# BEP33_12panel_stencil.net
KiCad netlist of a schematic drawn in EAGLE
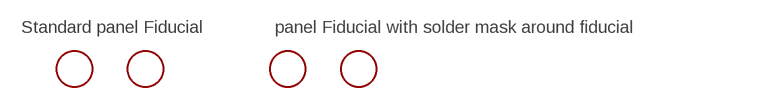
[diagram p0: schematic, sheet 1]
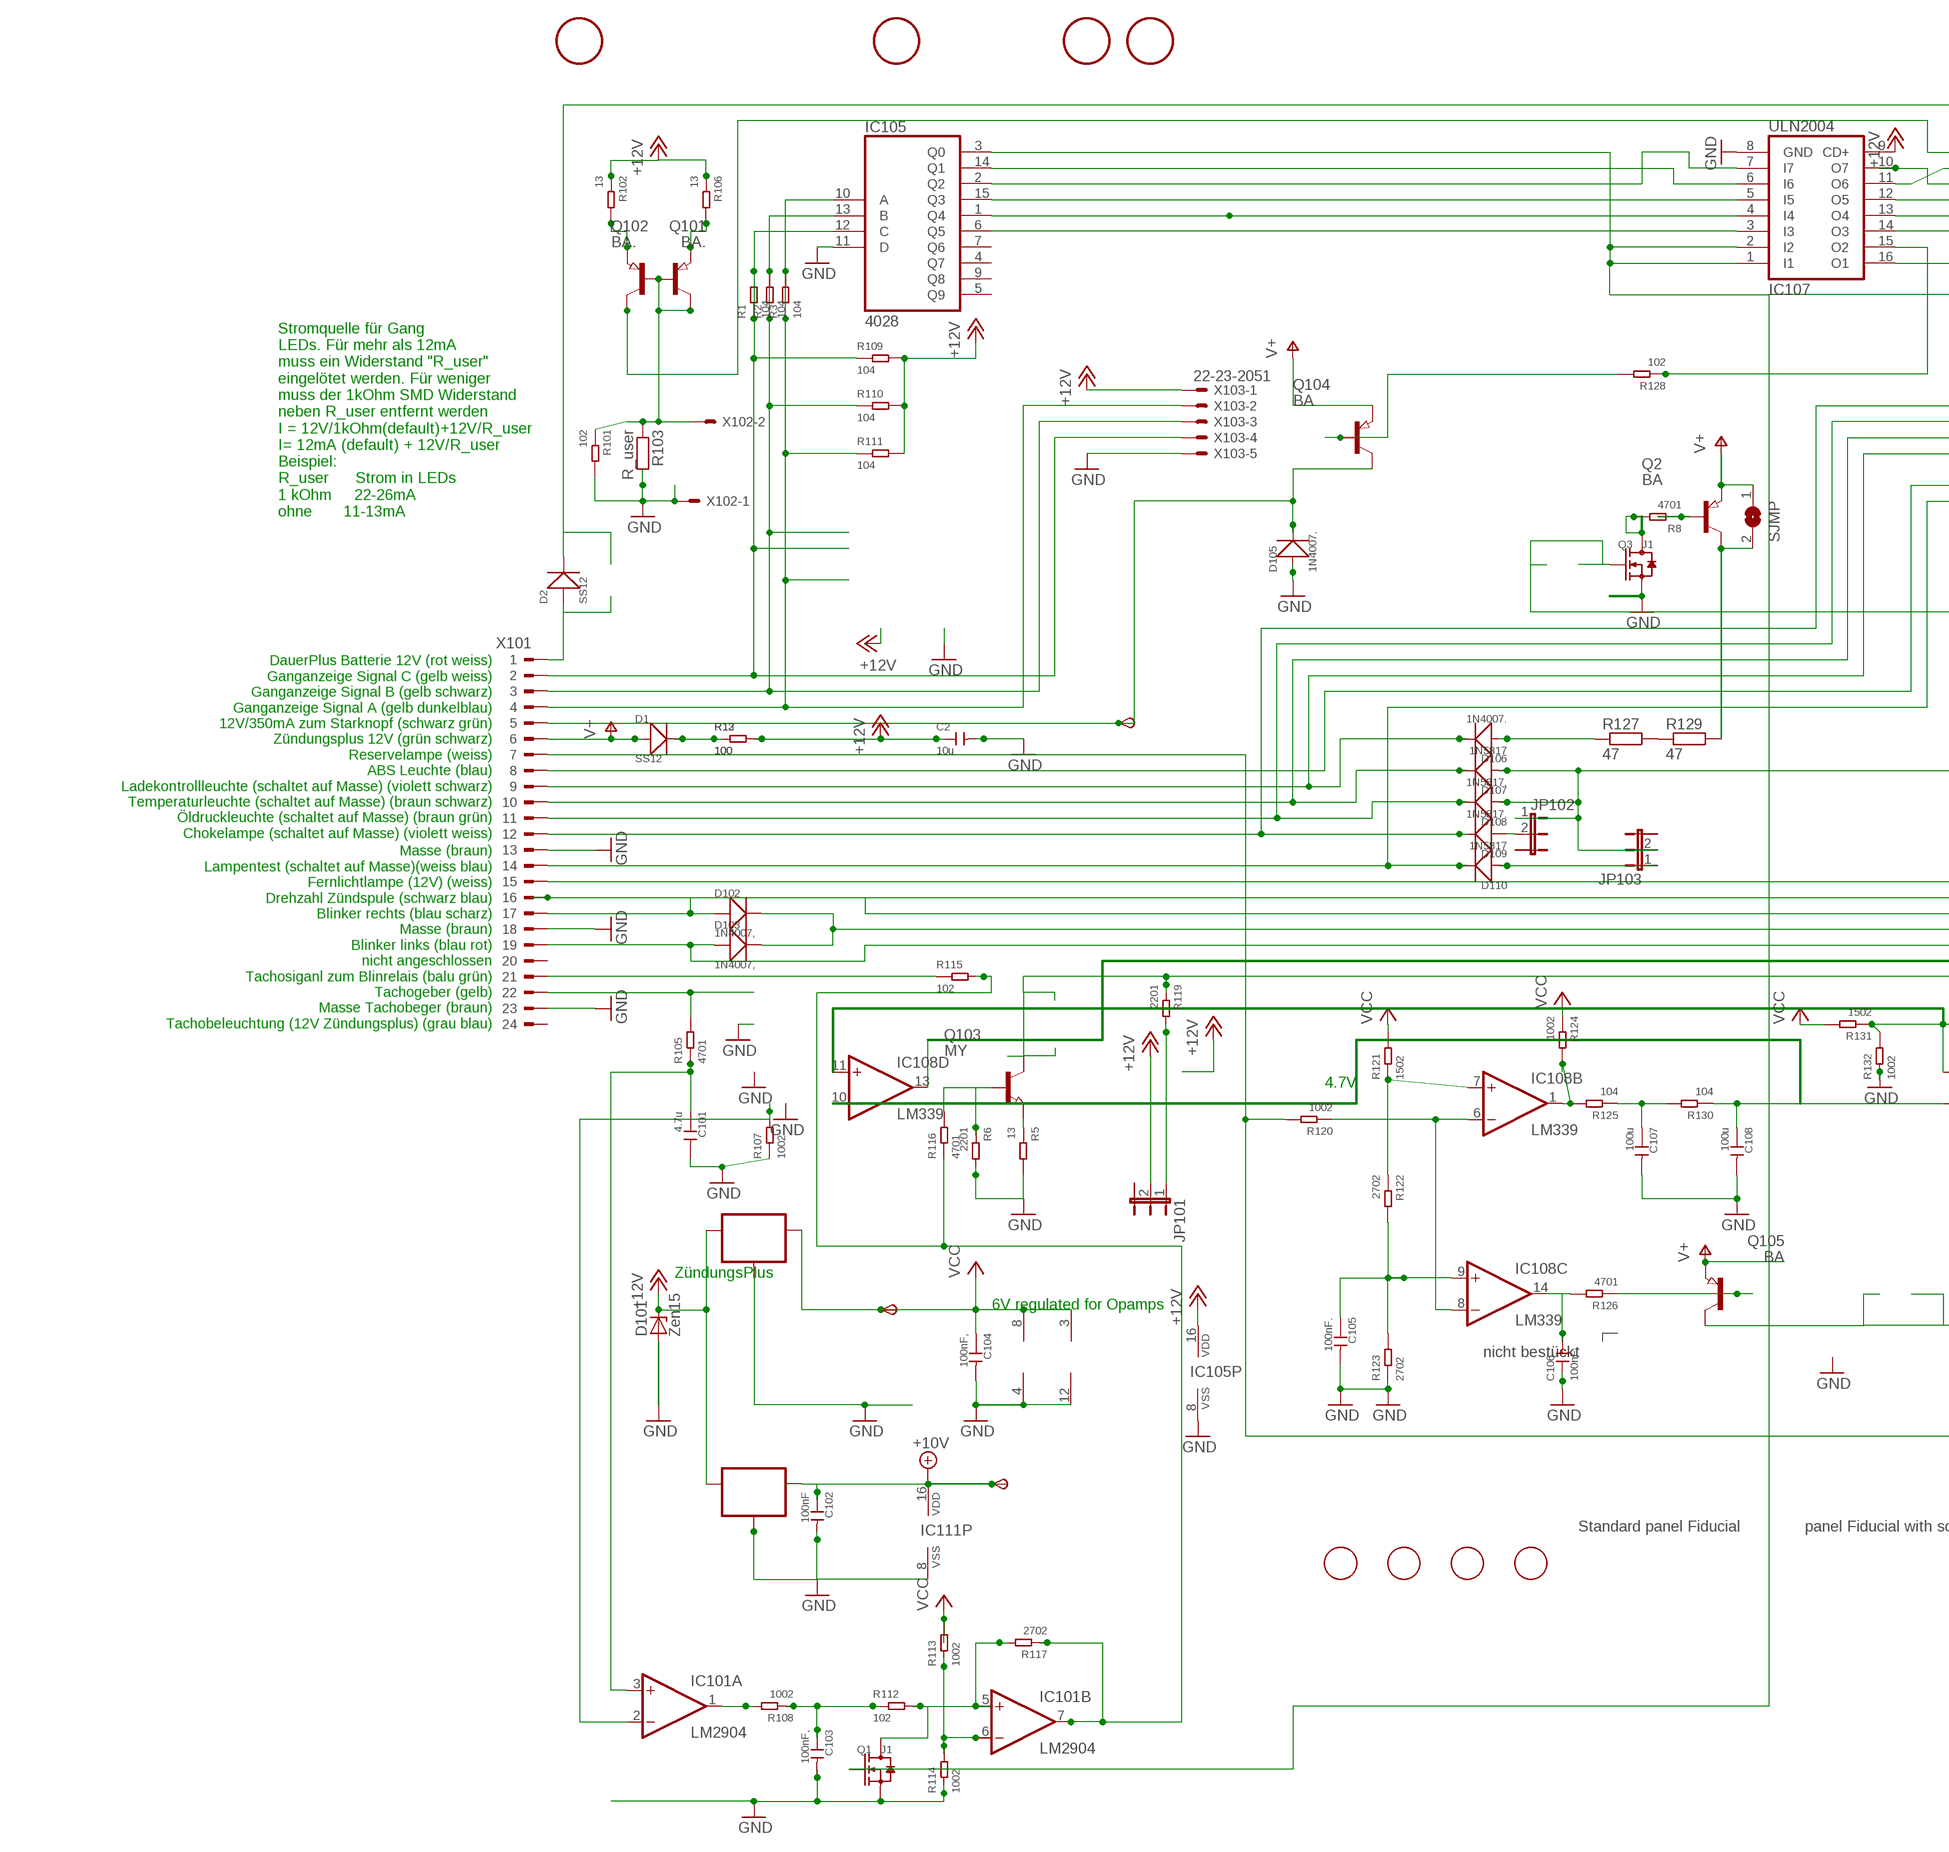
[diagram p1: schematic, sheet 2, part 1 of 2]
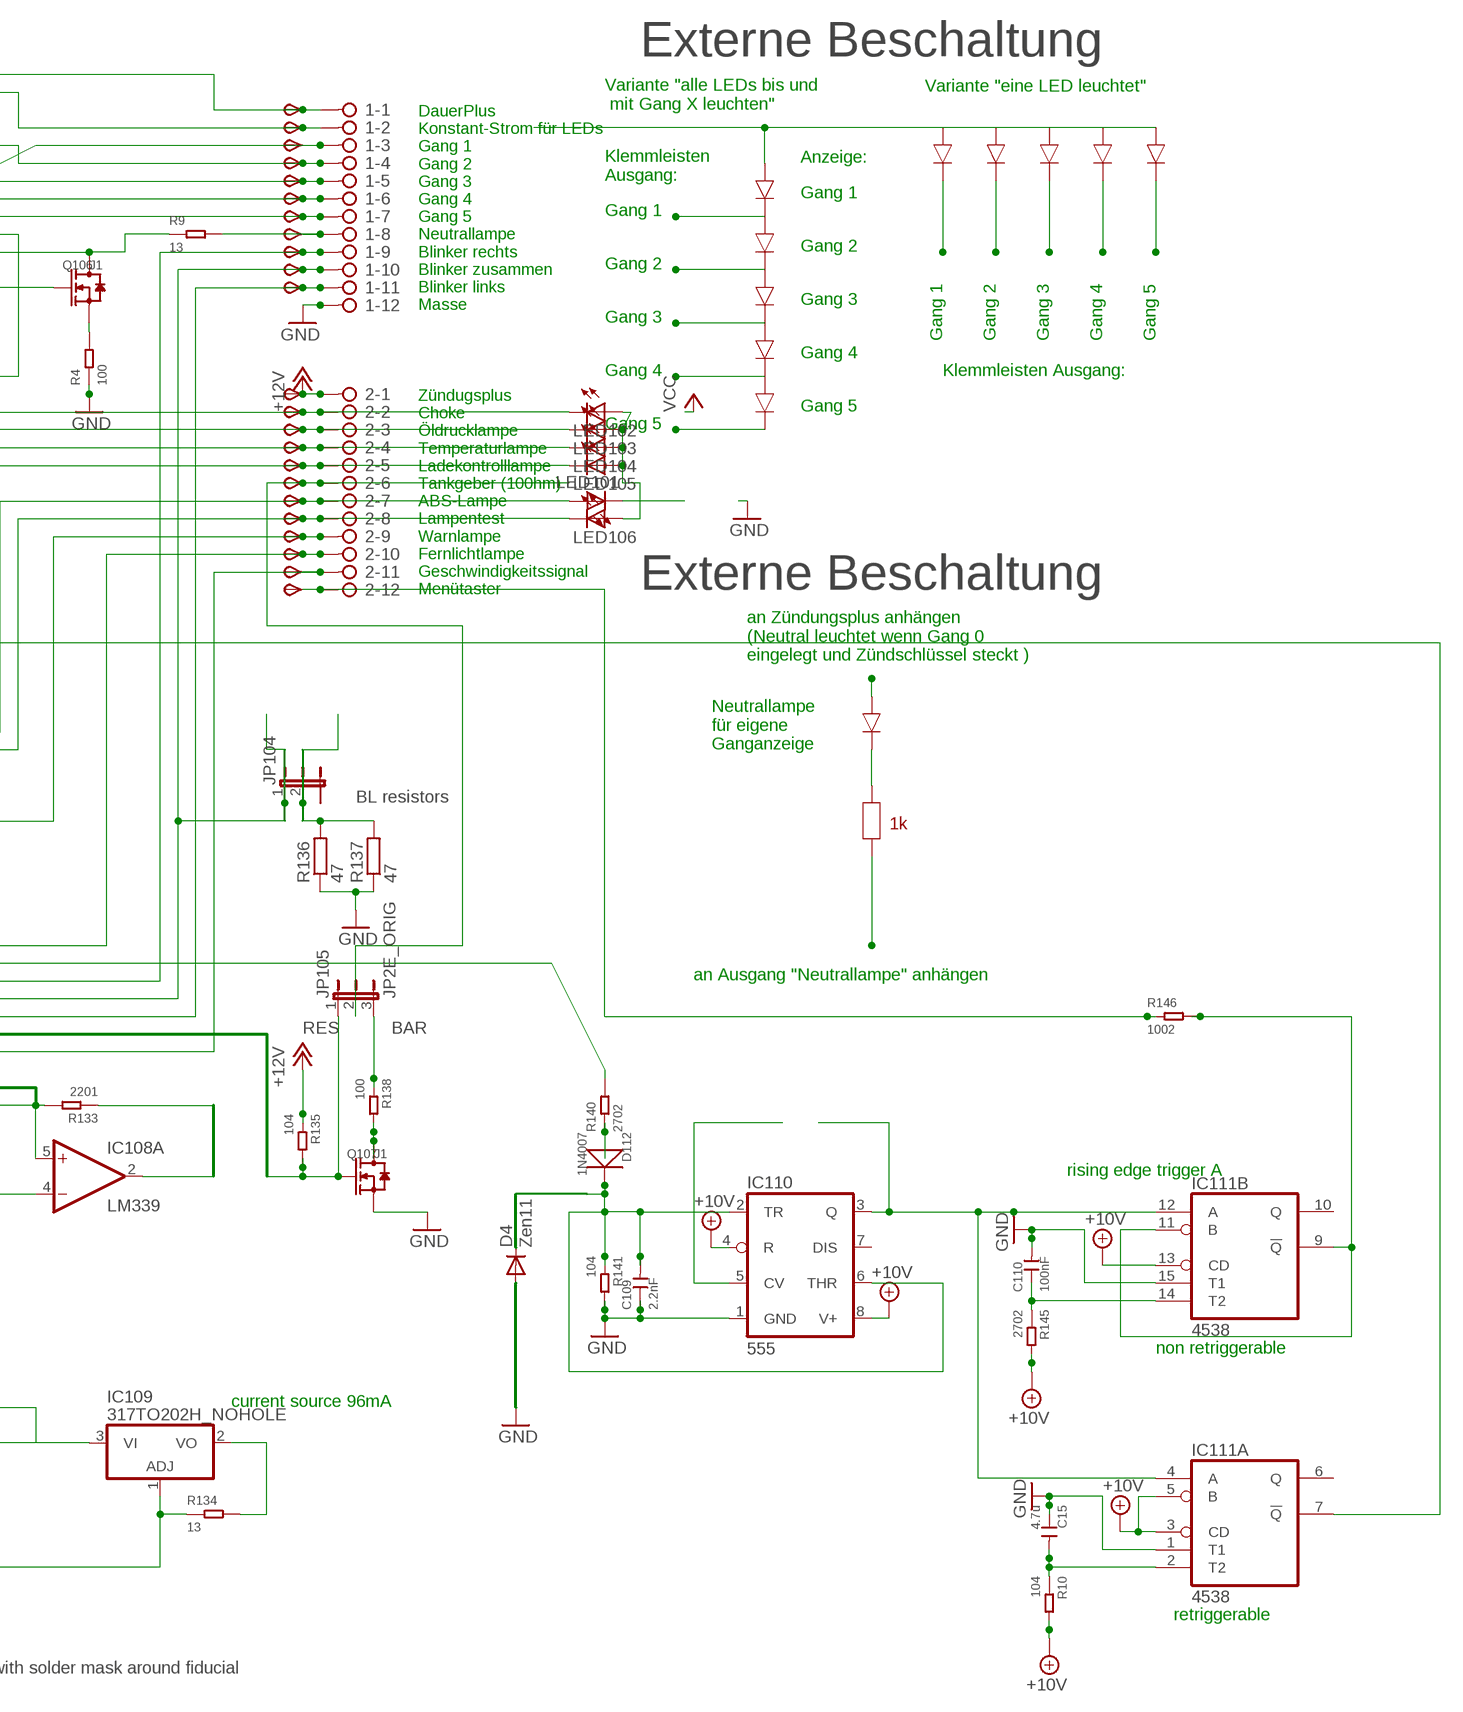
[diagram p2: schematic, sheet 2, part 2 of 2]
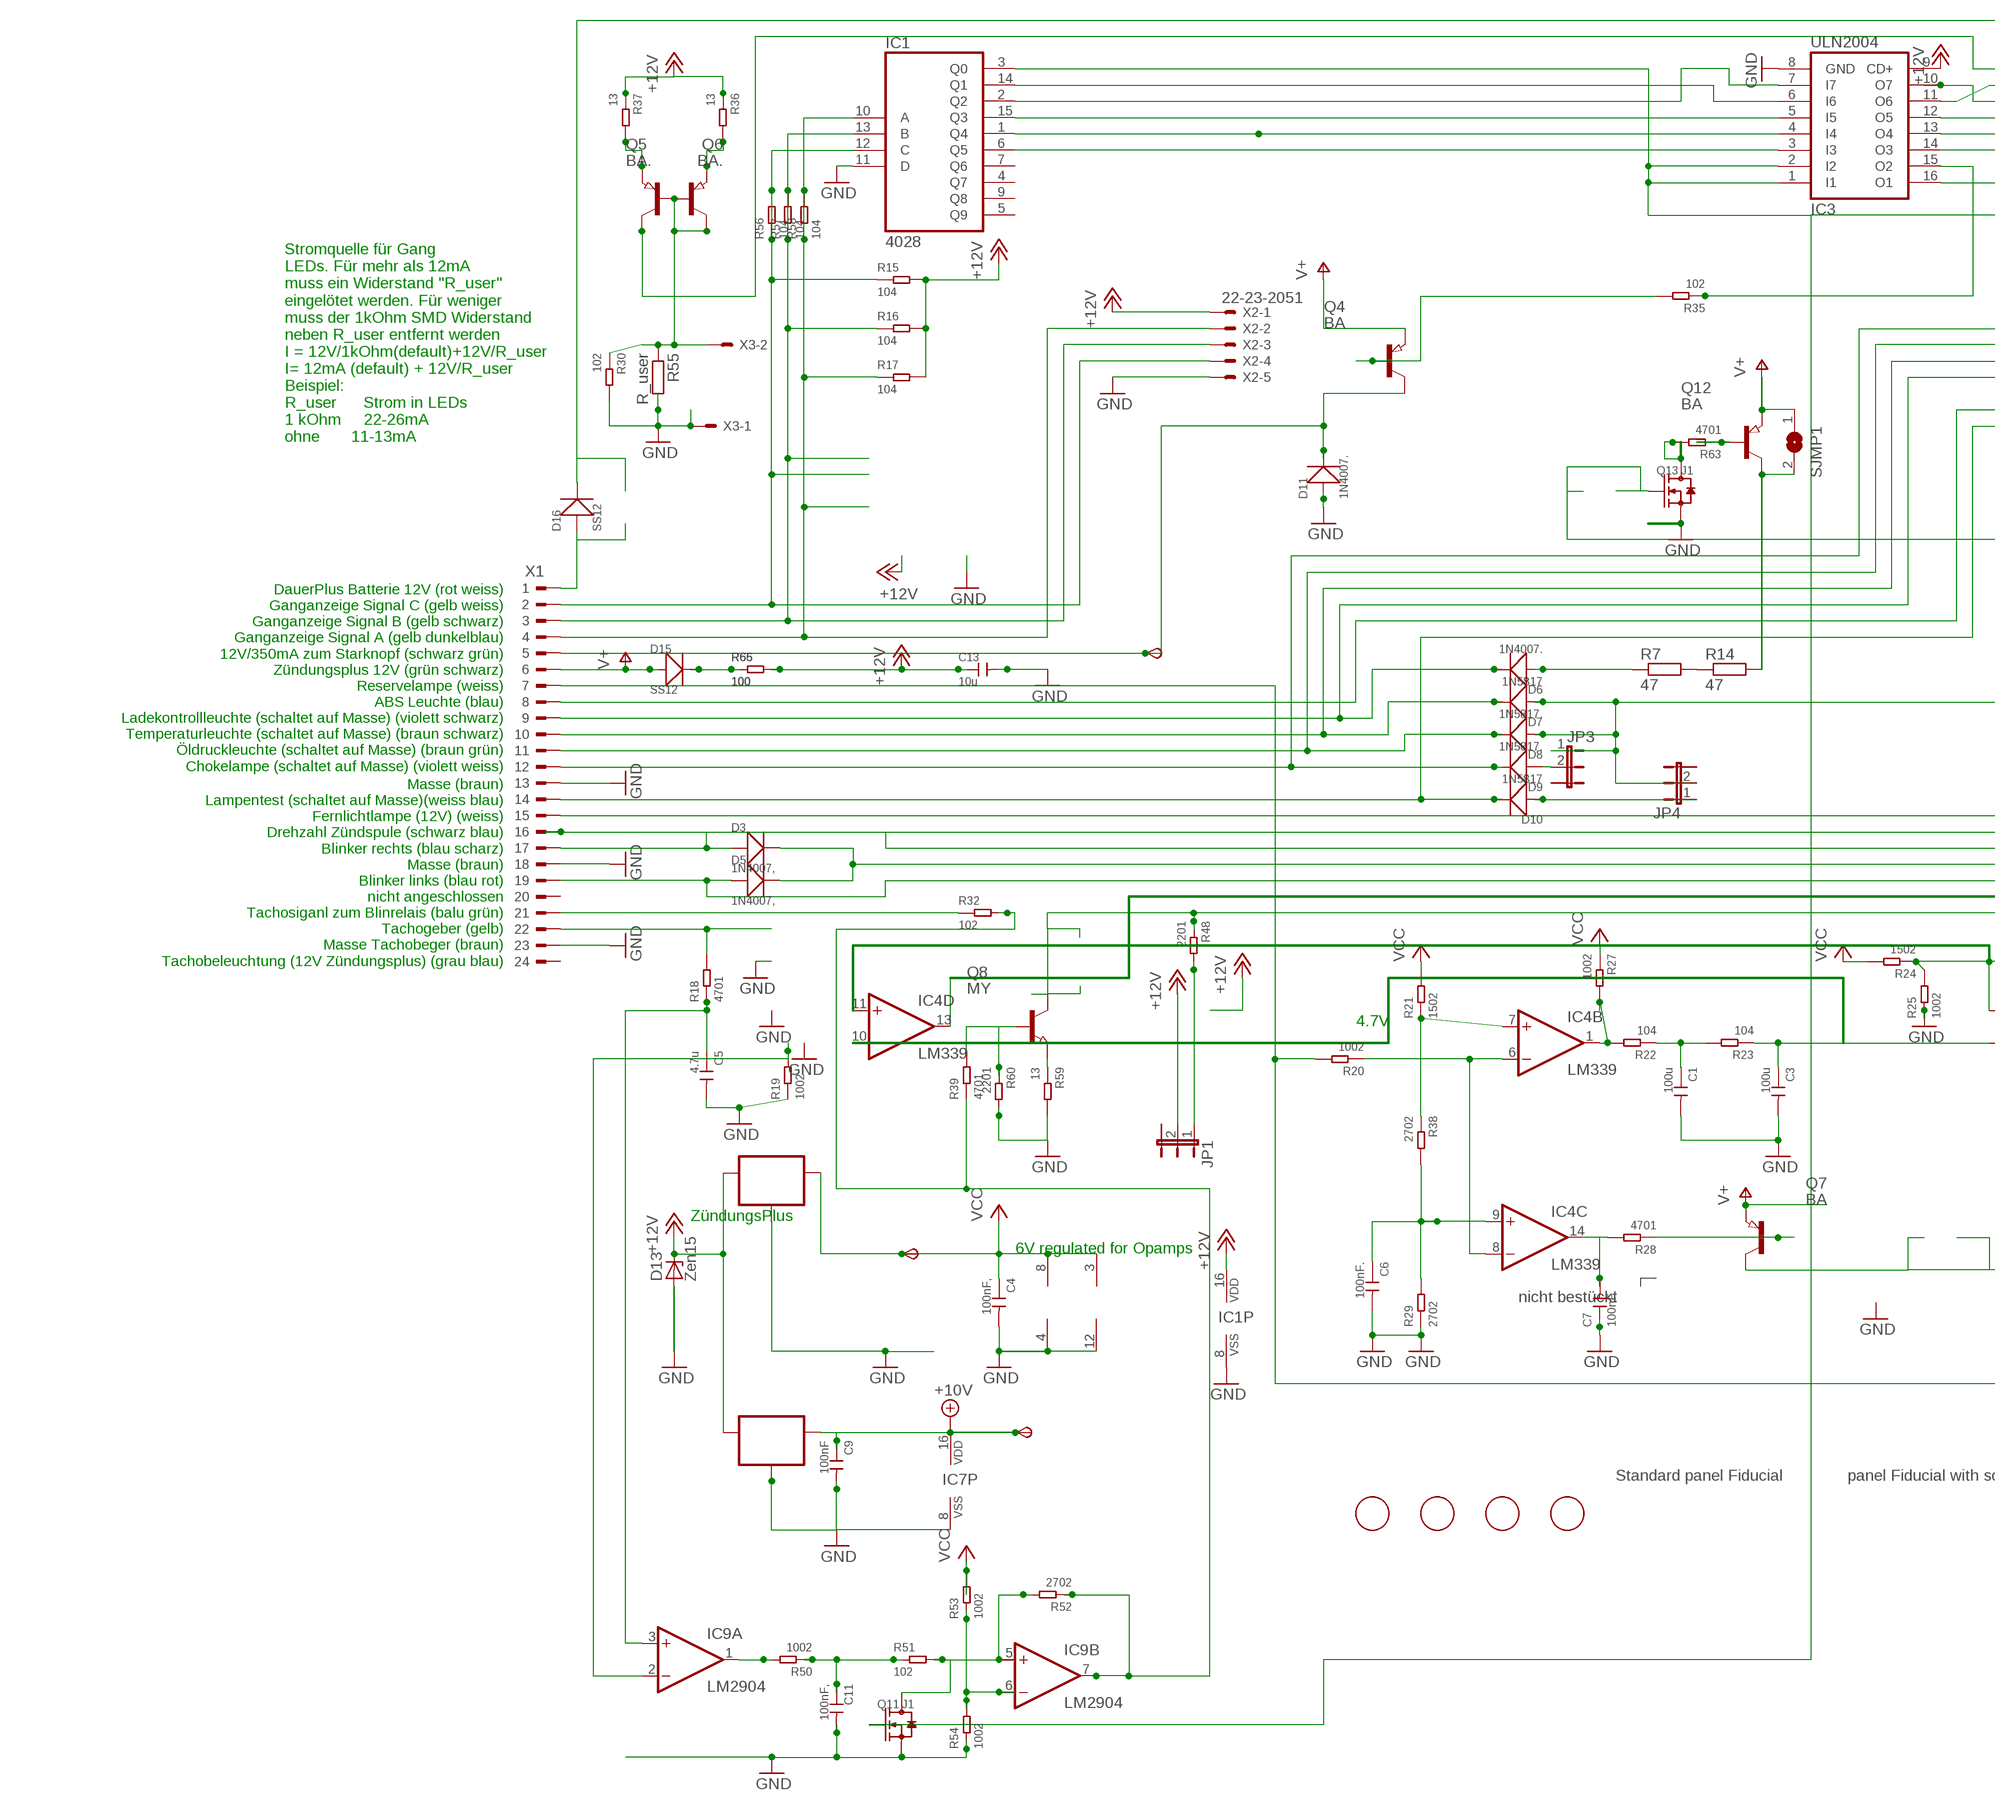
[diagram p3: schematic, sheet 3, part 1 of 2]
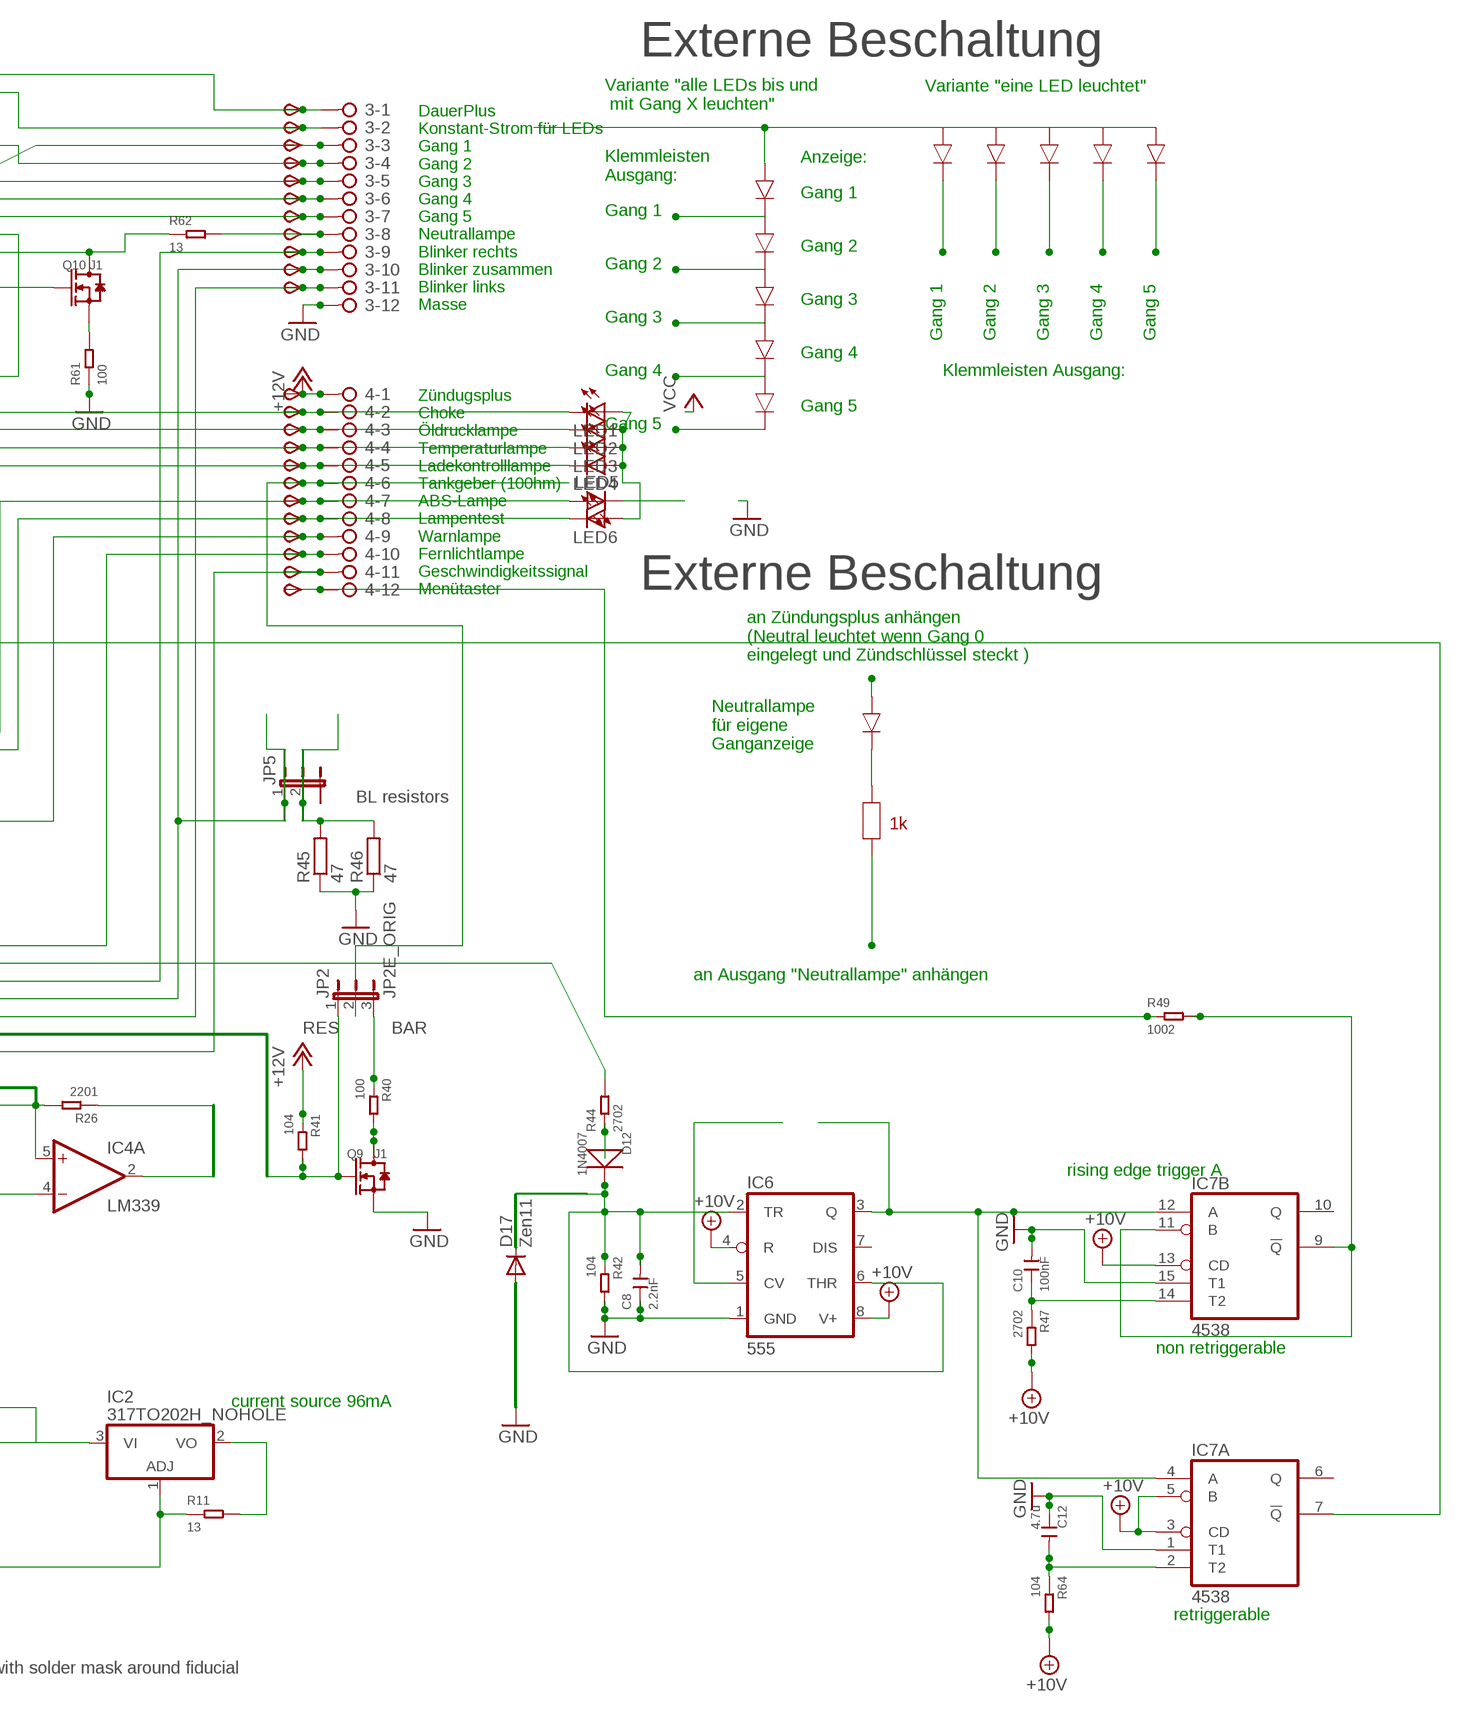
[diagram p4: schematic, sheet 3, part 2 of 2]
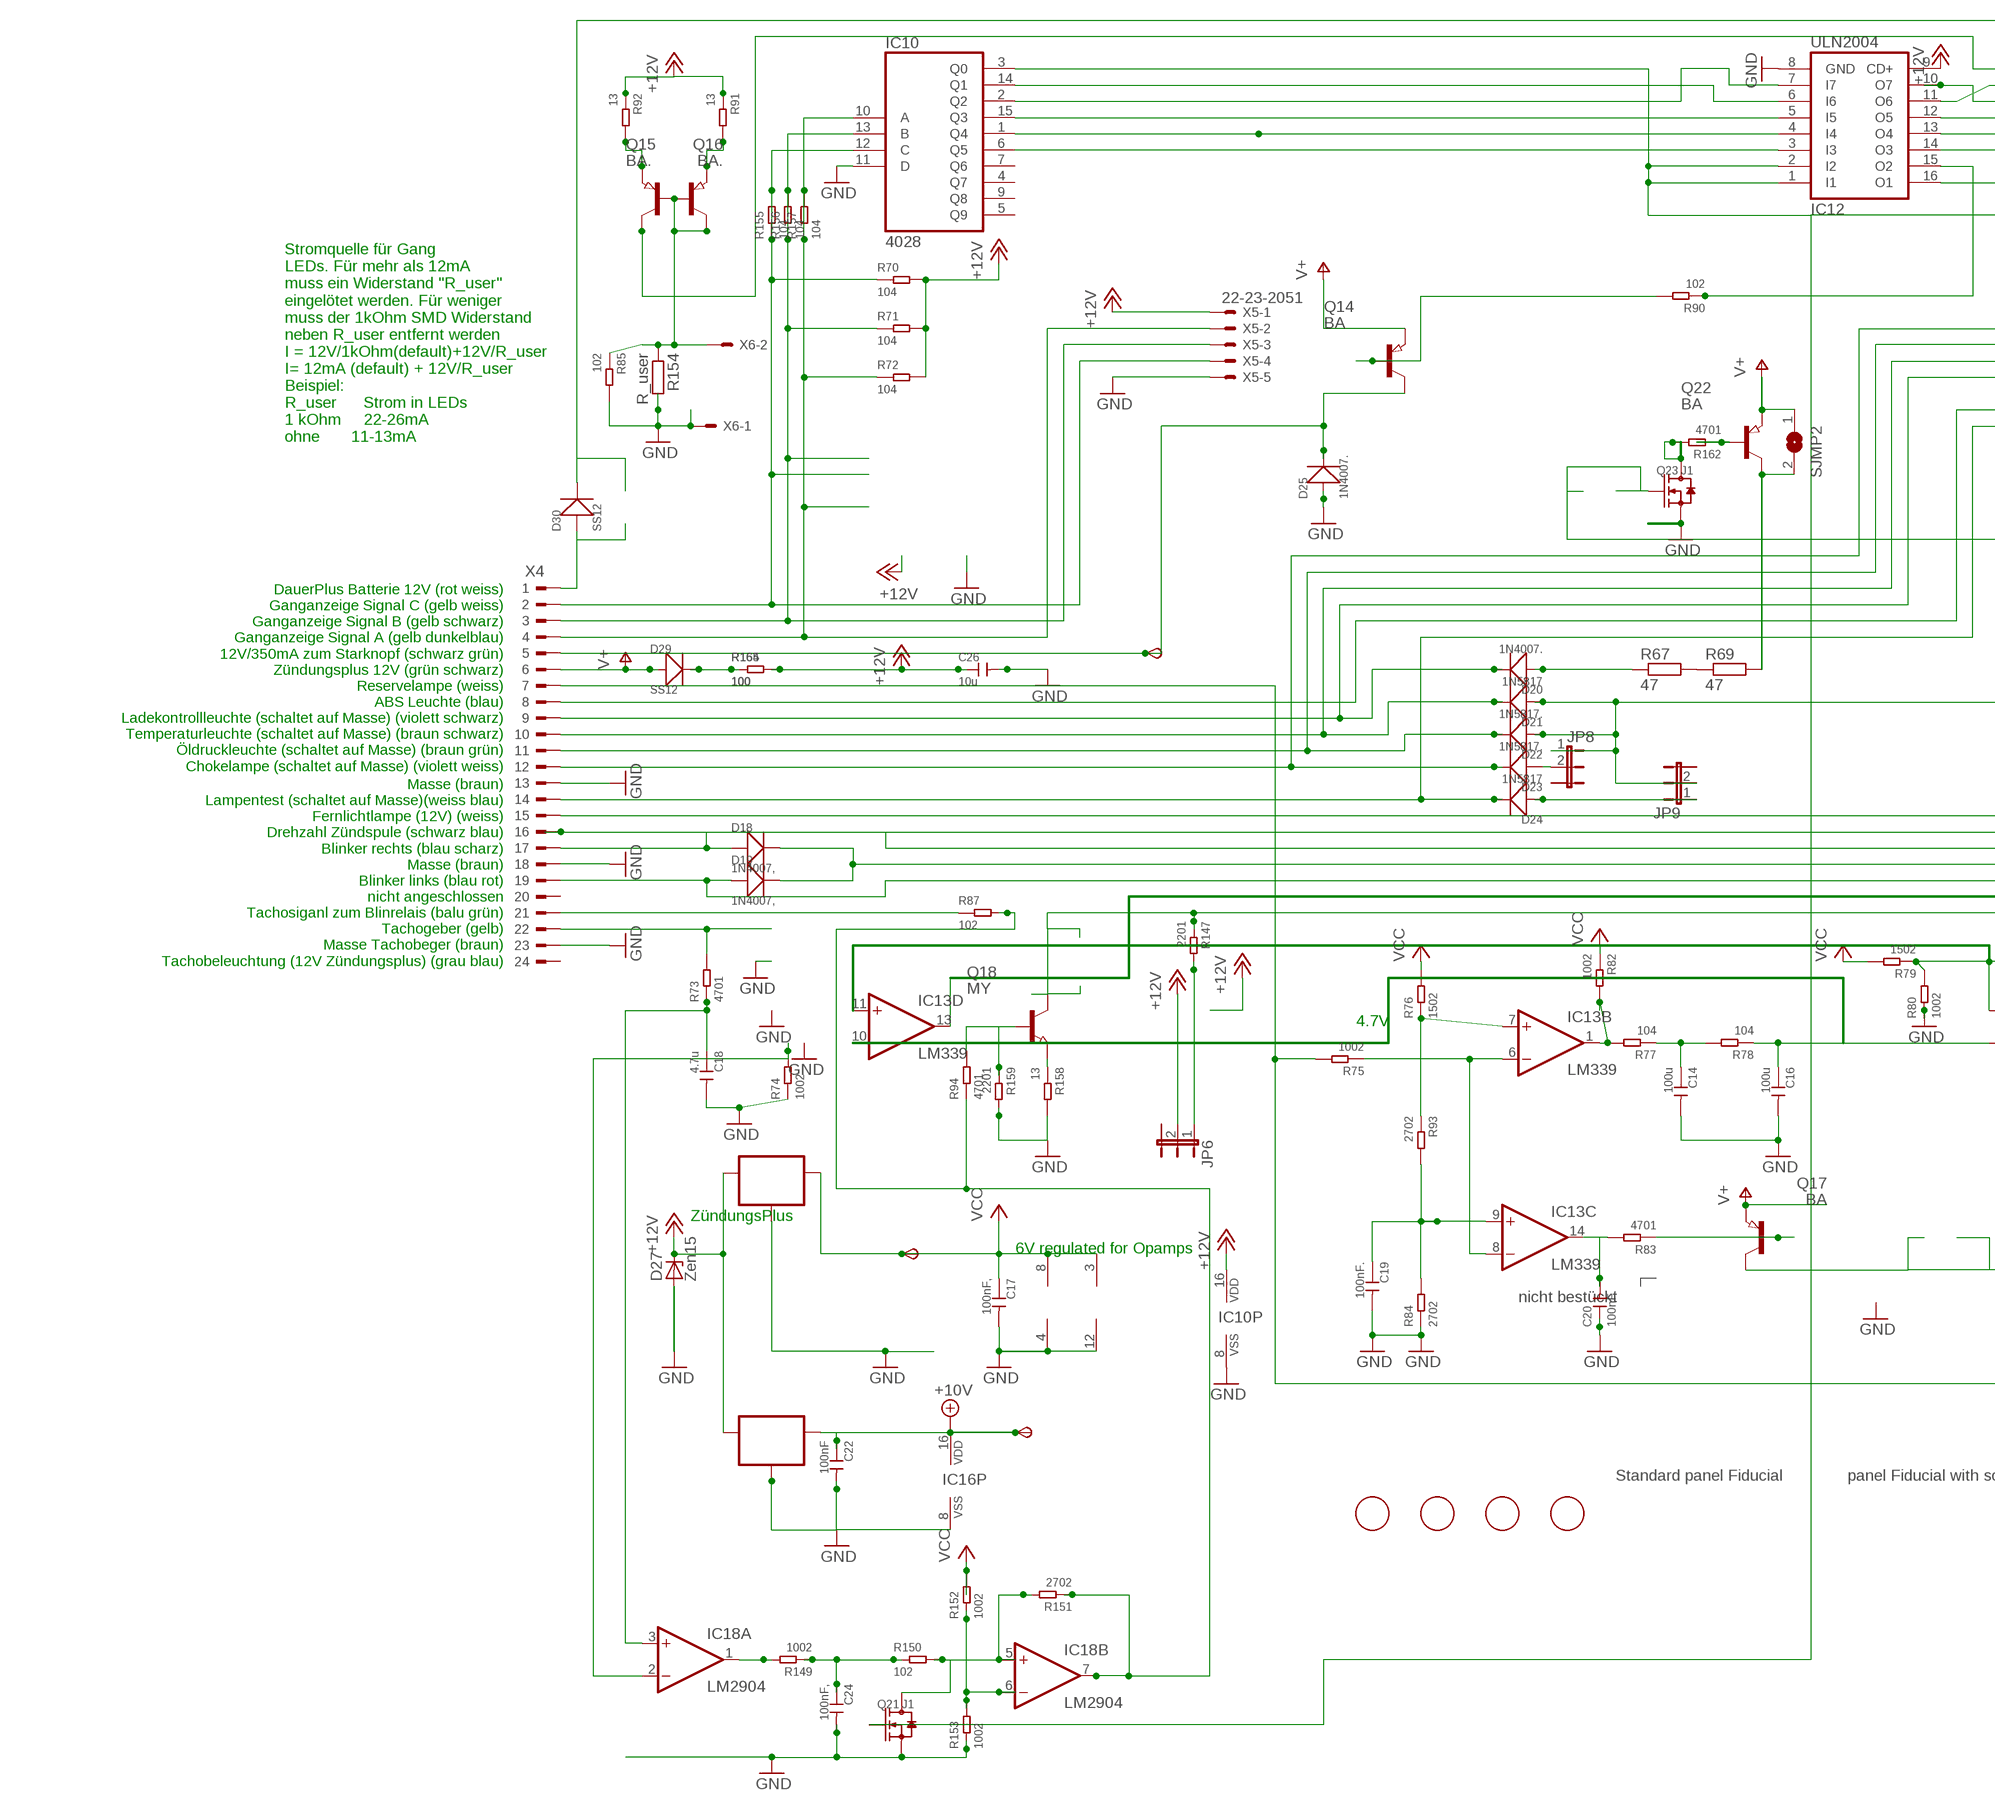
[diagram p5: schematic, sheet 4, part 1 of 2]
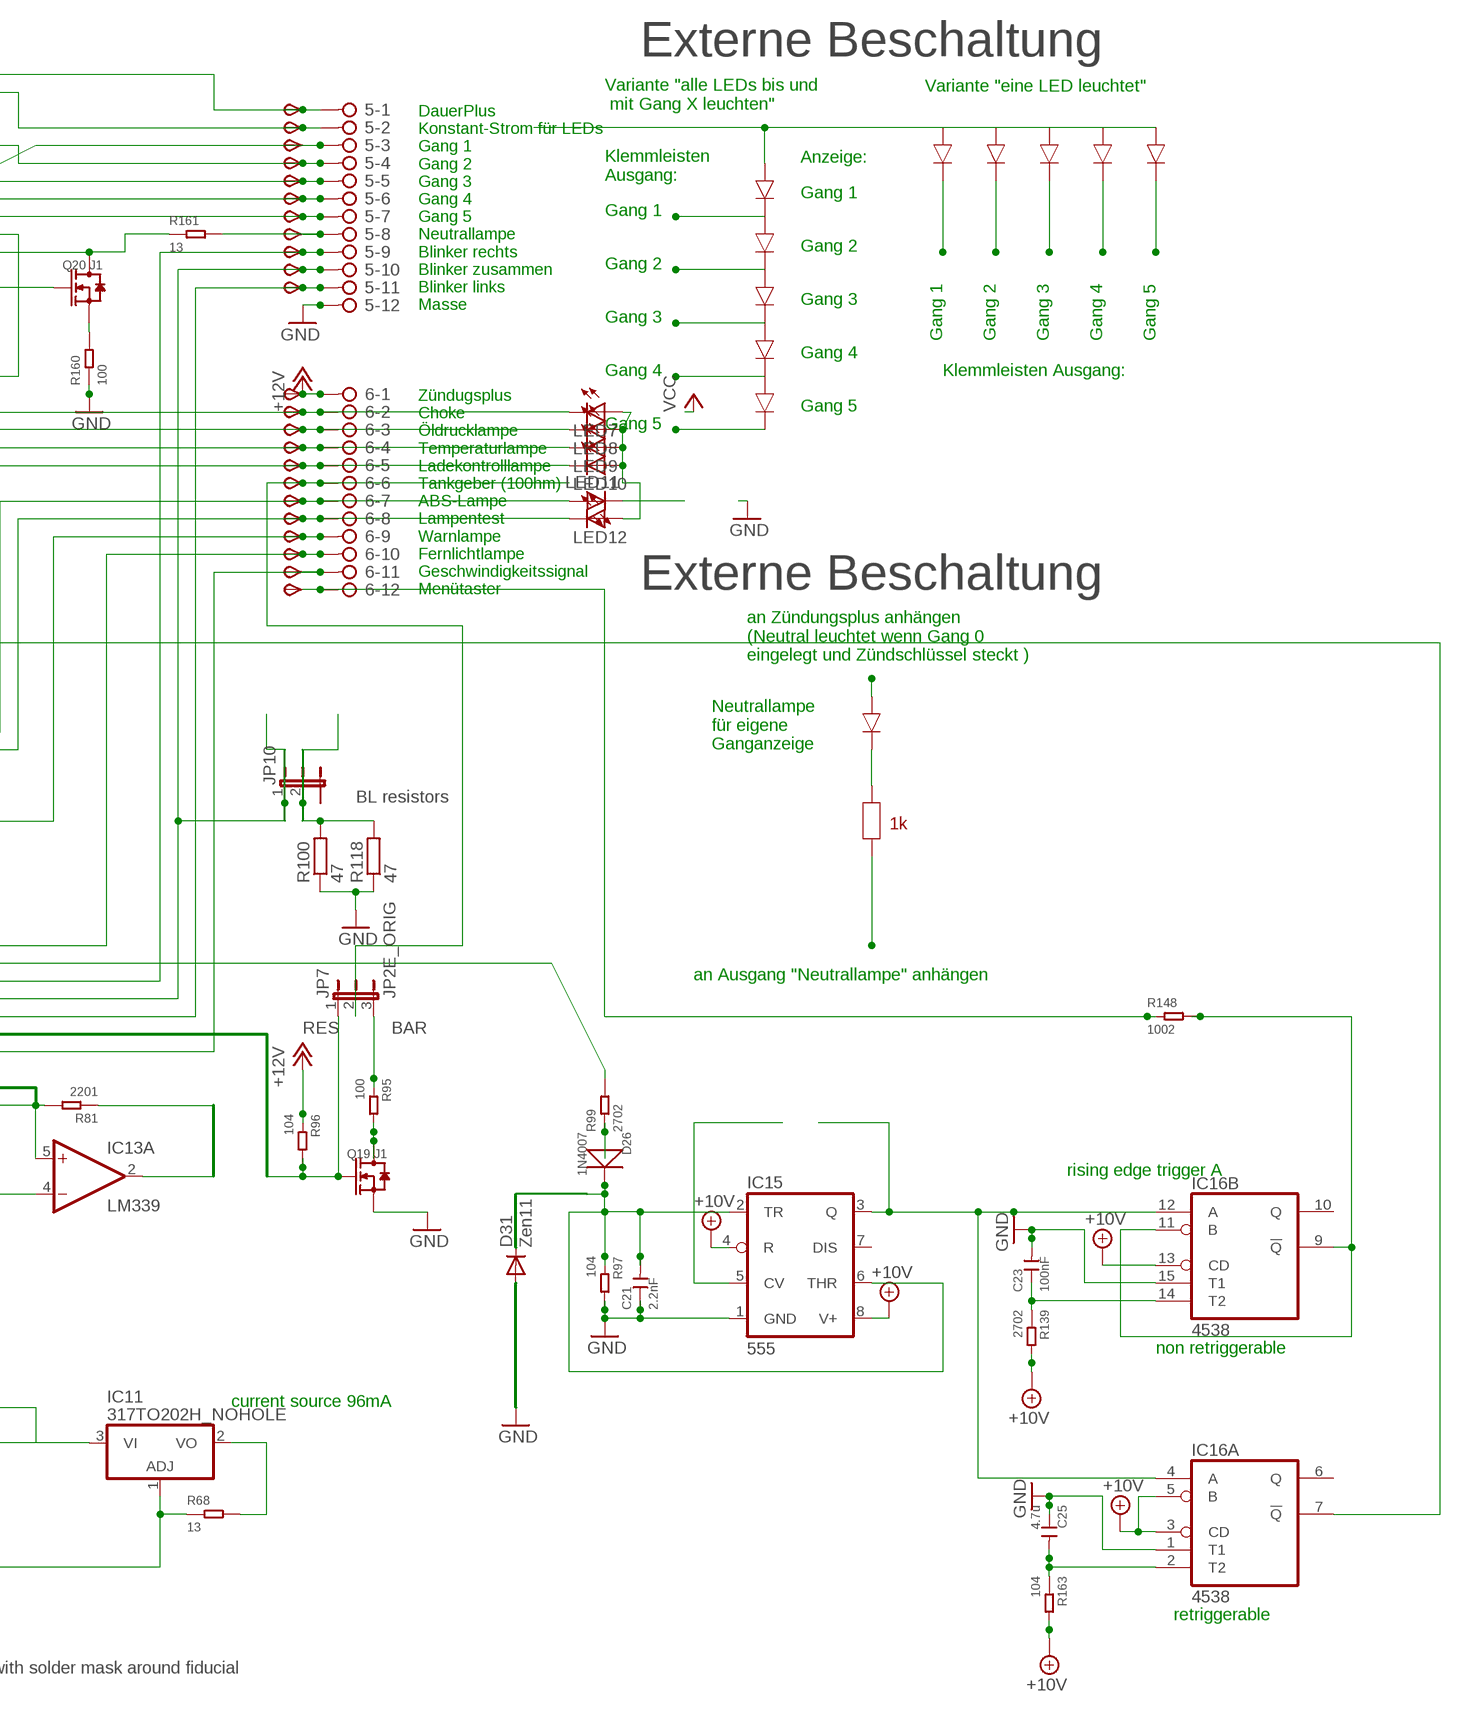
[diagram p6: schematic, sheet 4, part 2 of 2]
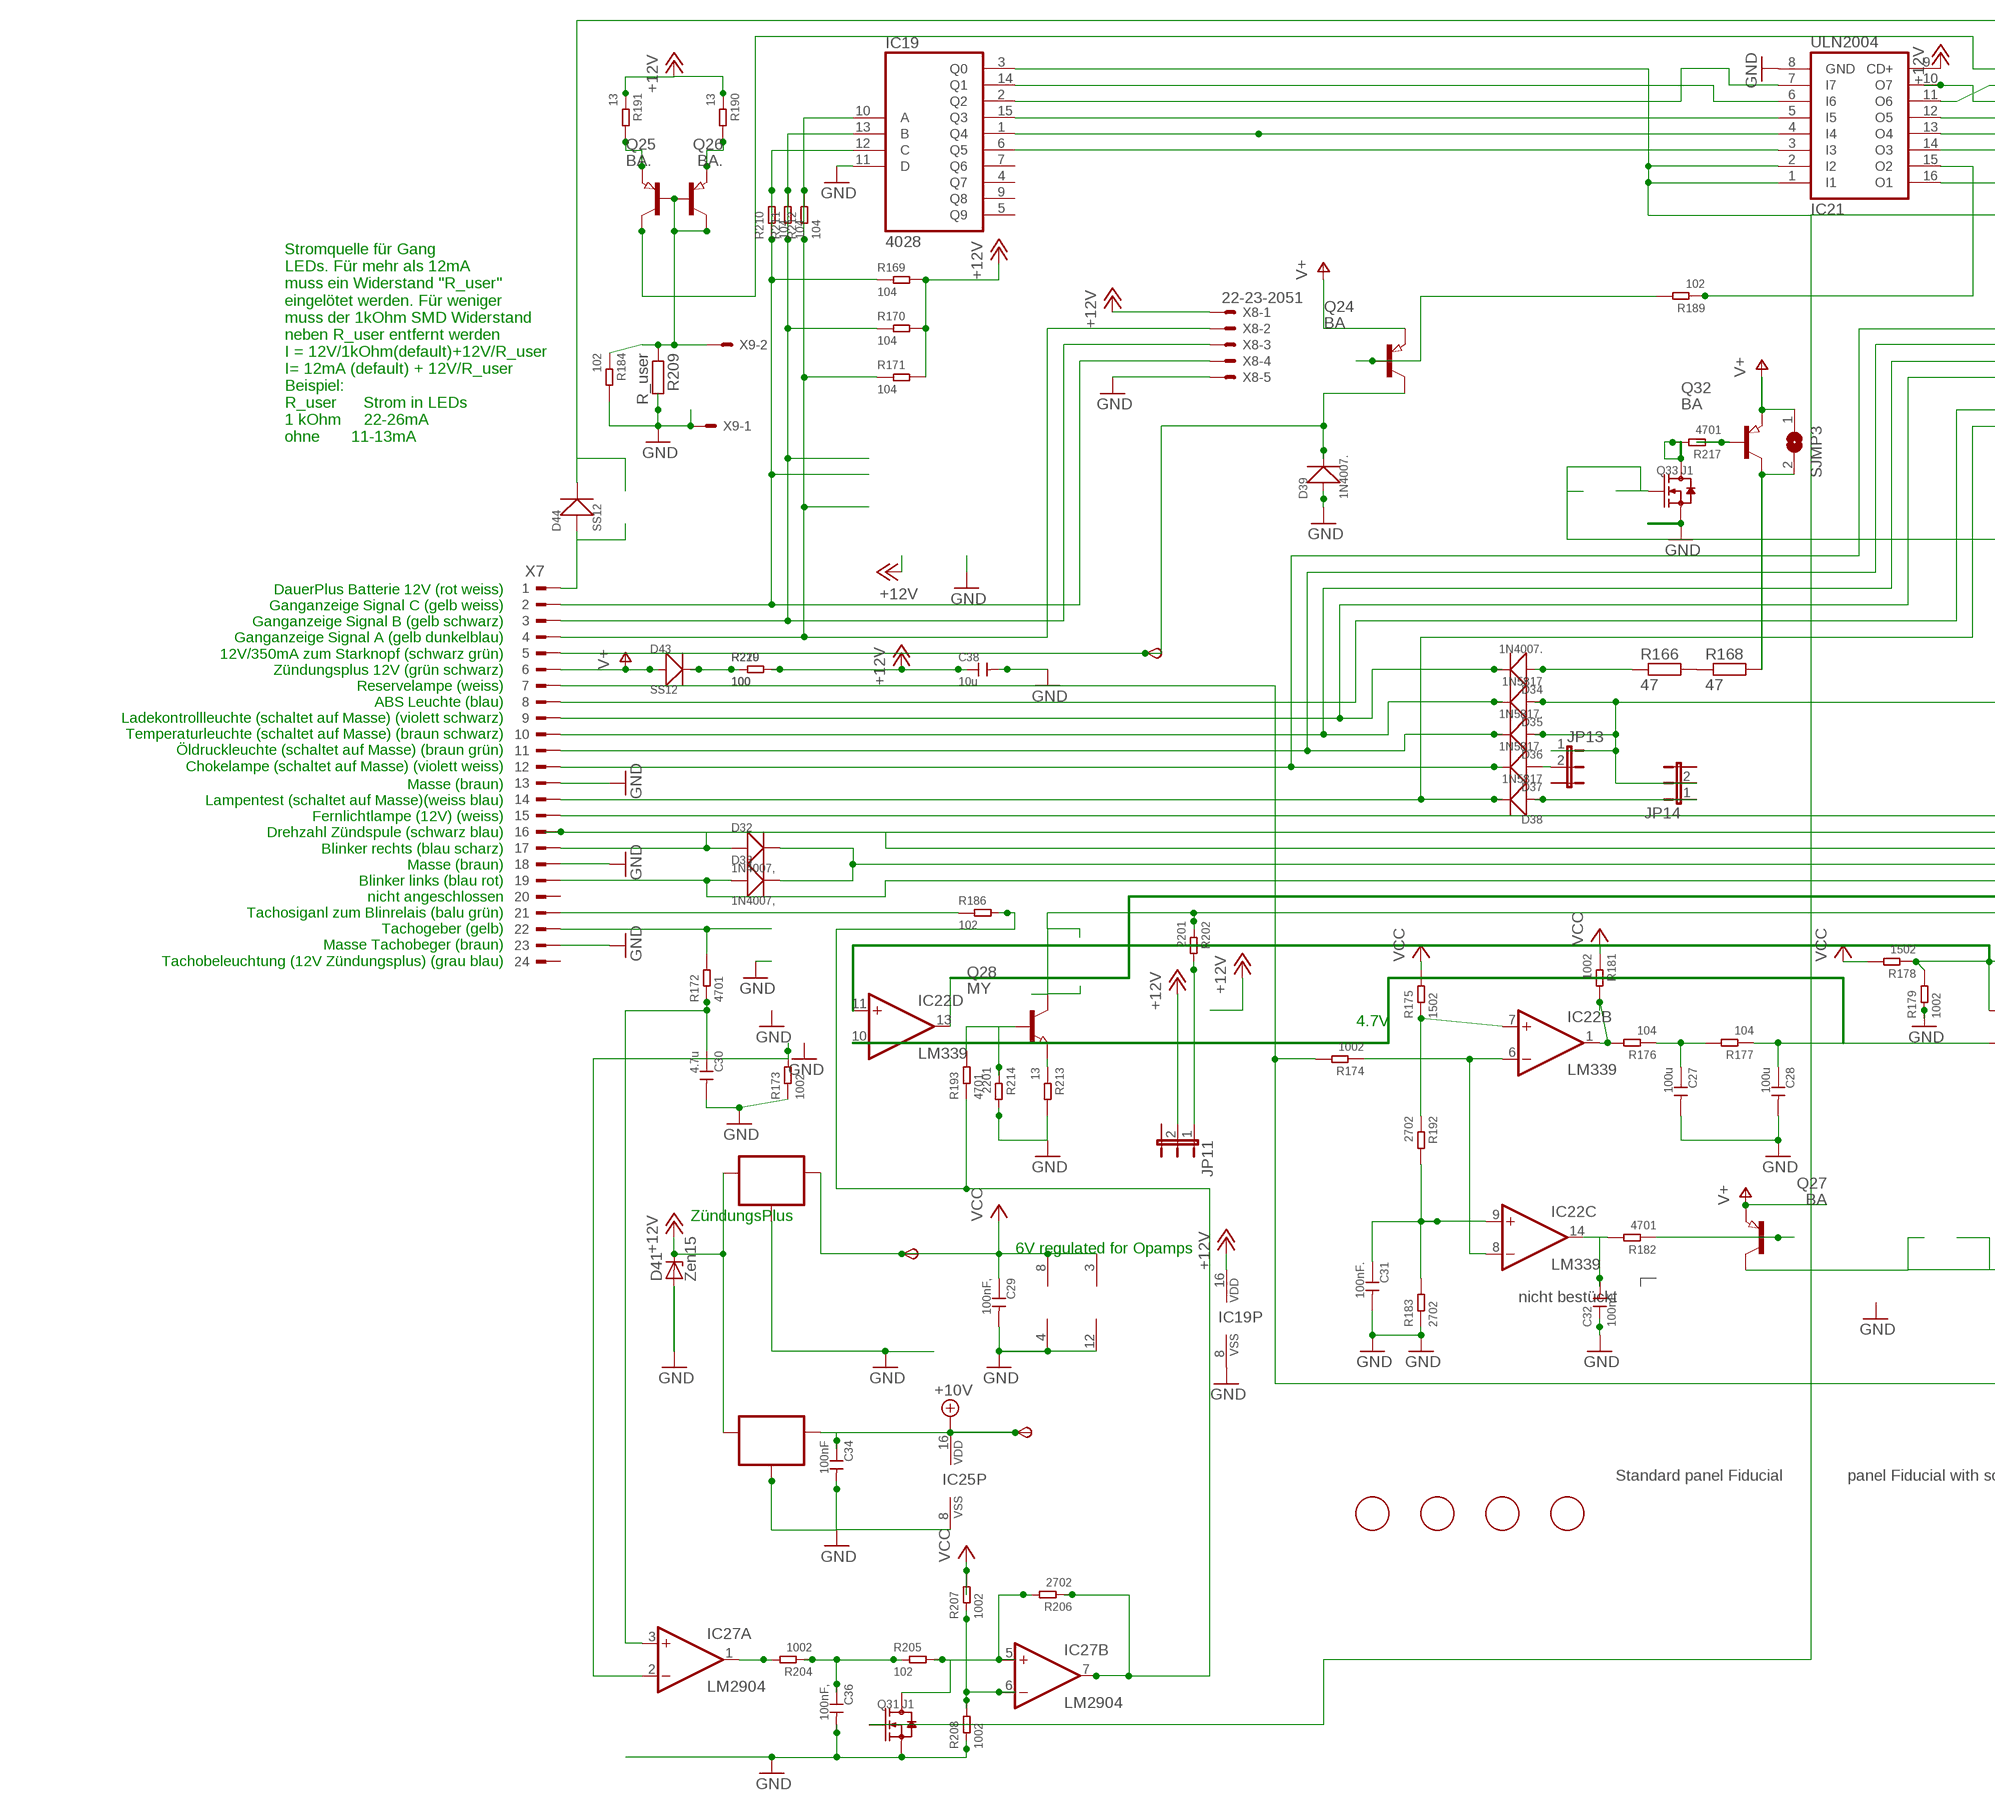
[diagram p7: schematic, sheet 5, part 1 of 2]
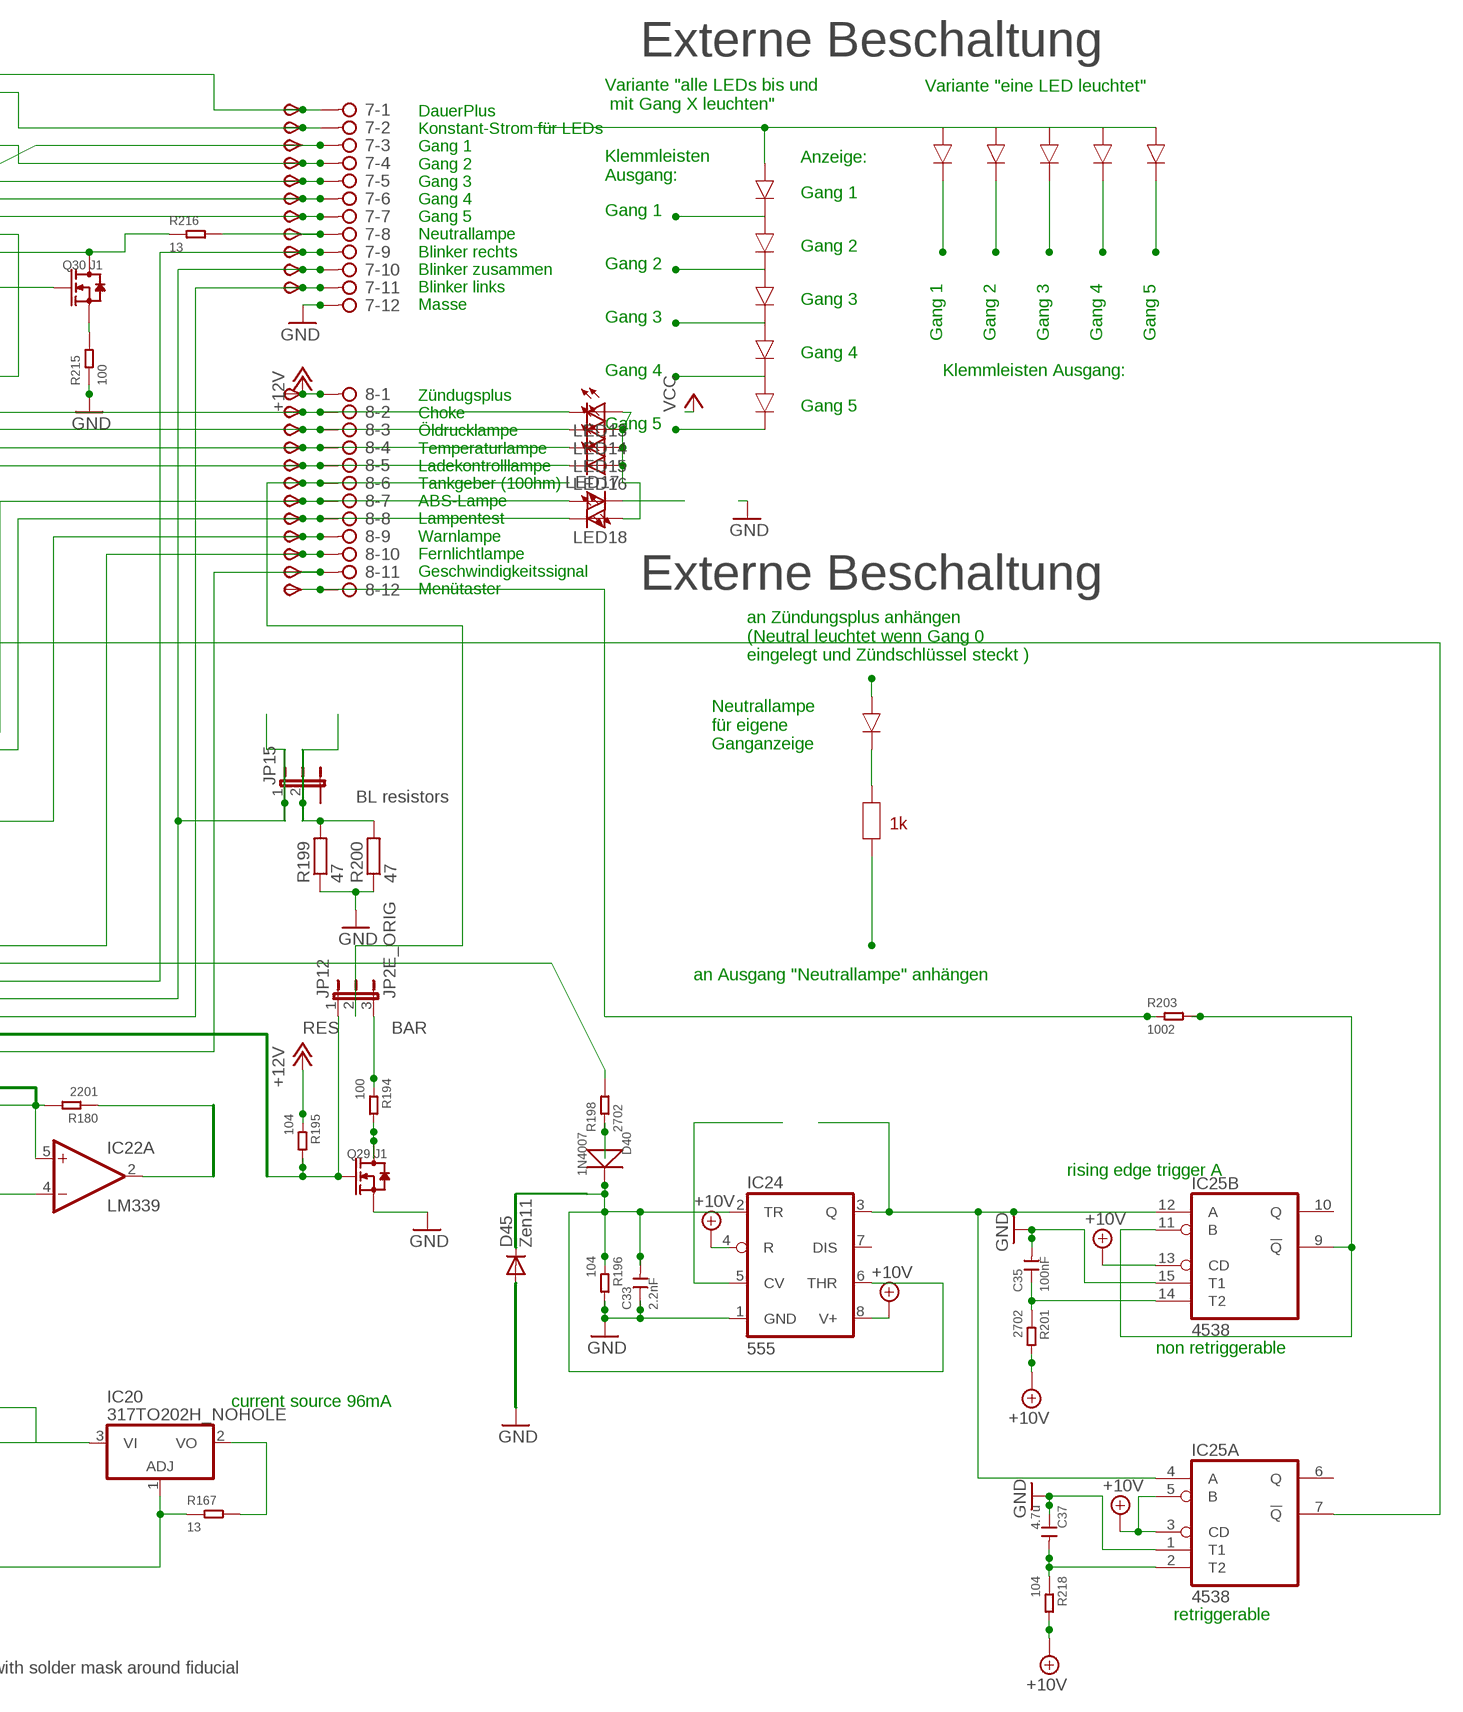
[diagram p8: schematic, sheet 5, part 2 of 2]
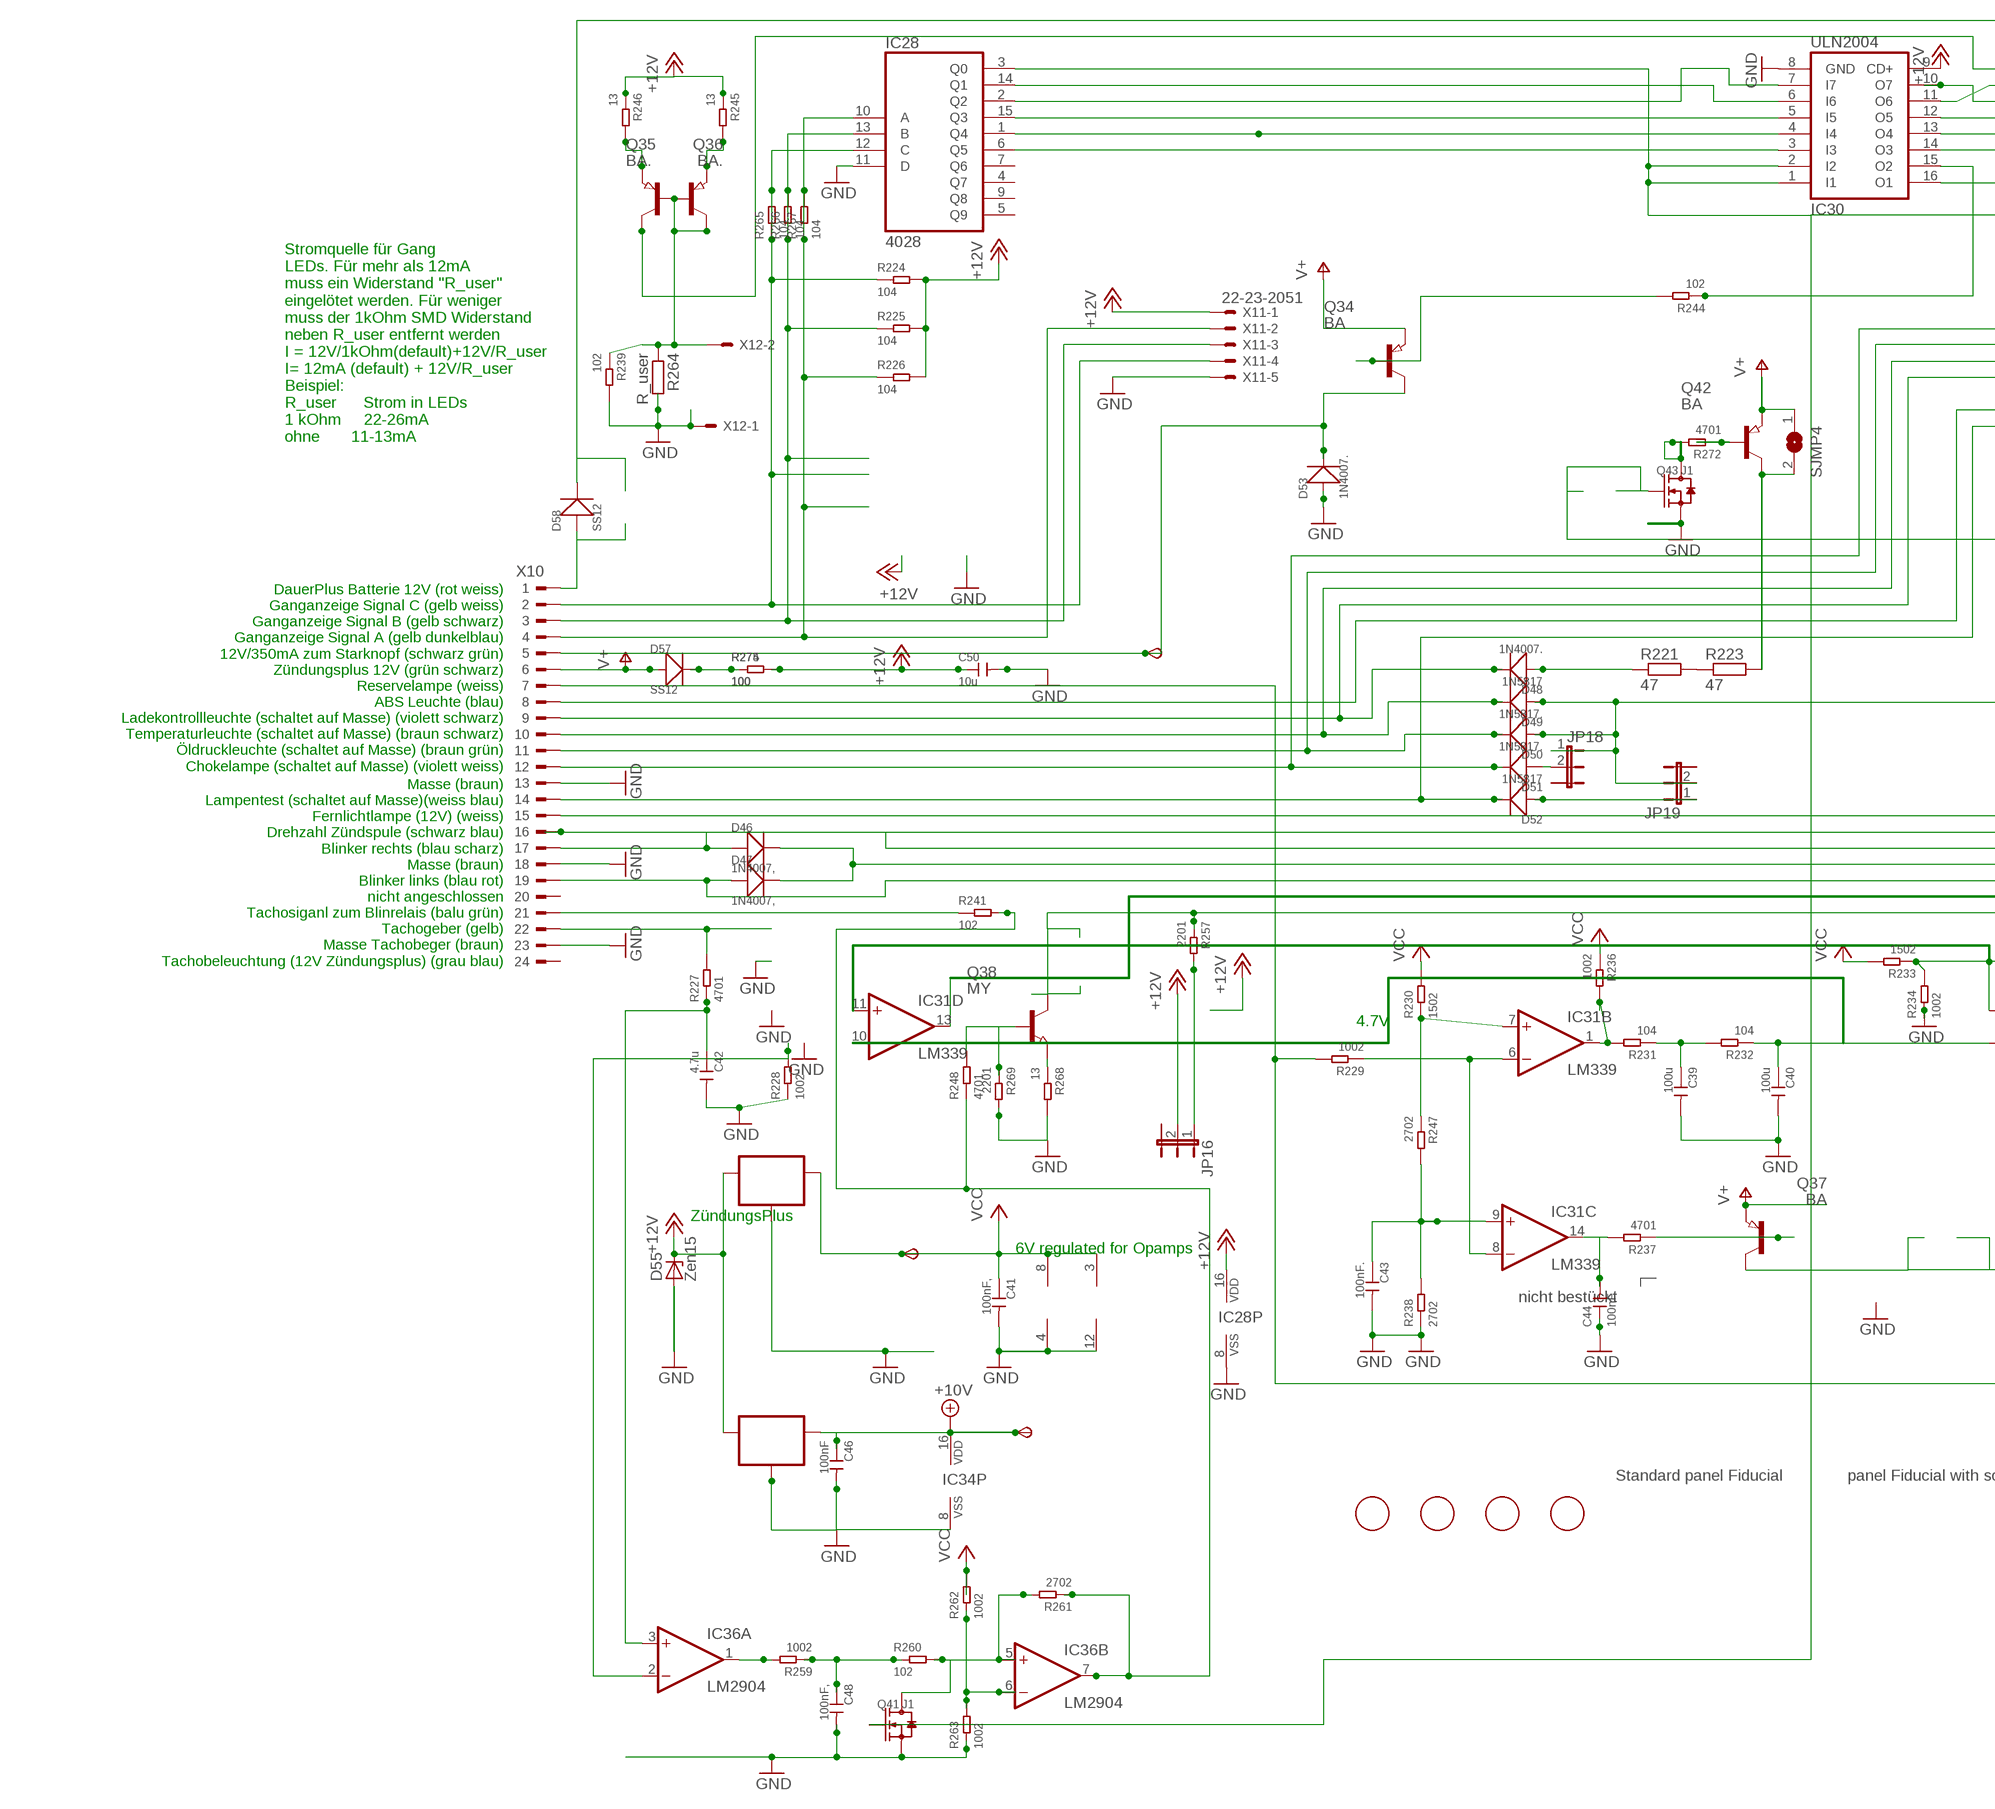
[diagram p9: schematic, sheet 6, part 1 of 2]
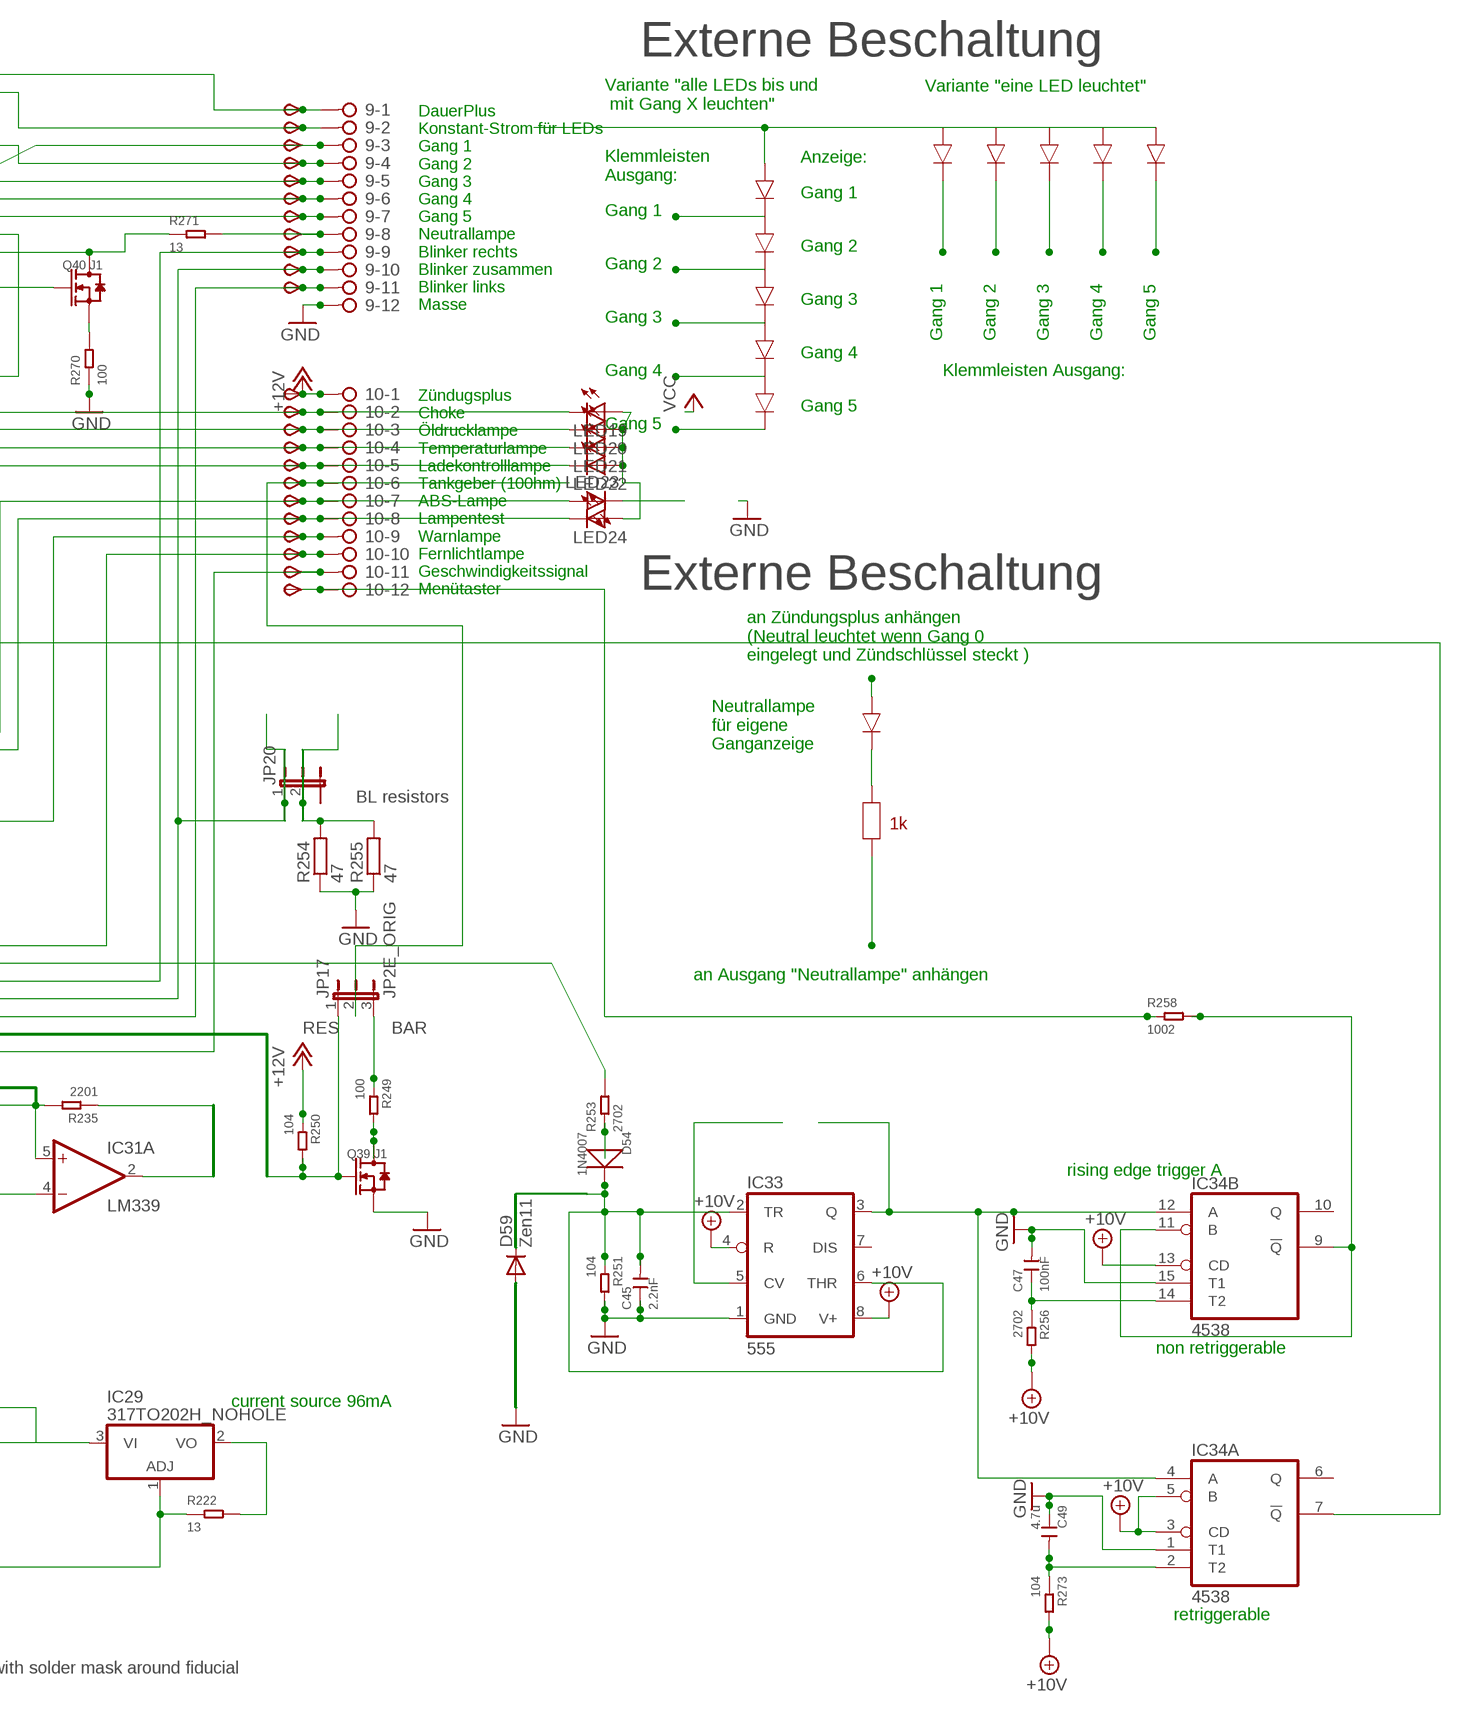
[diagram p10: schematic, sheet 6, part 2 of 2]
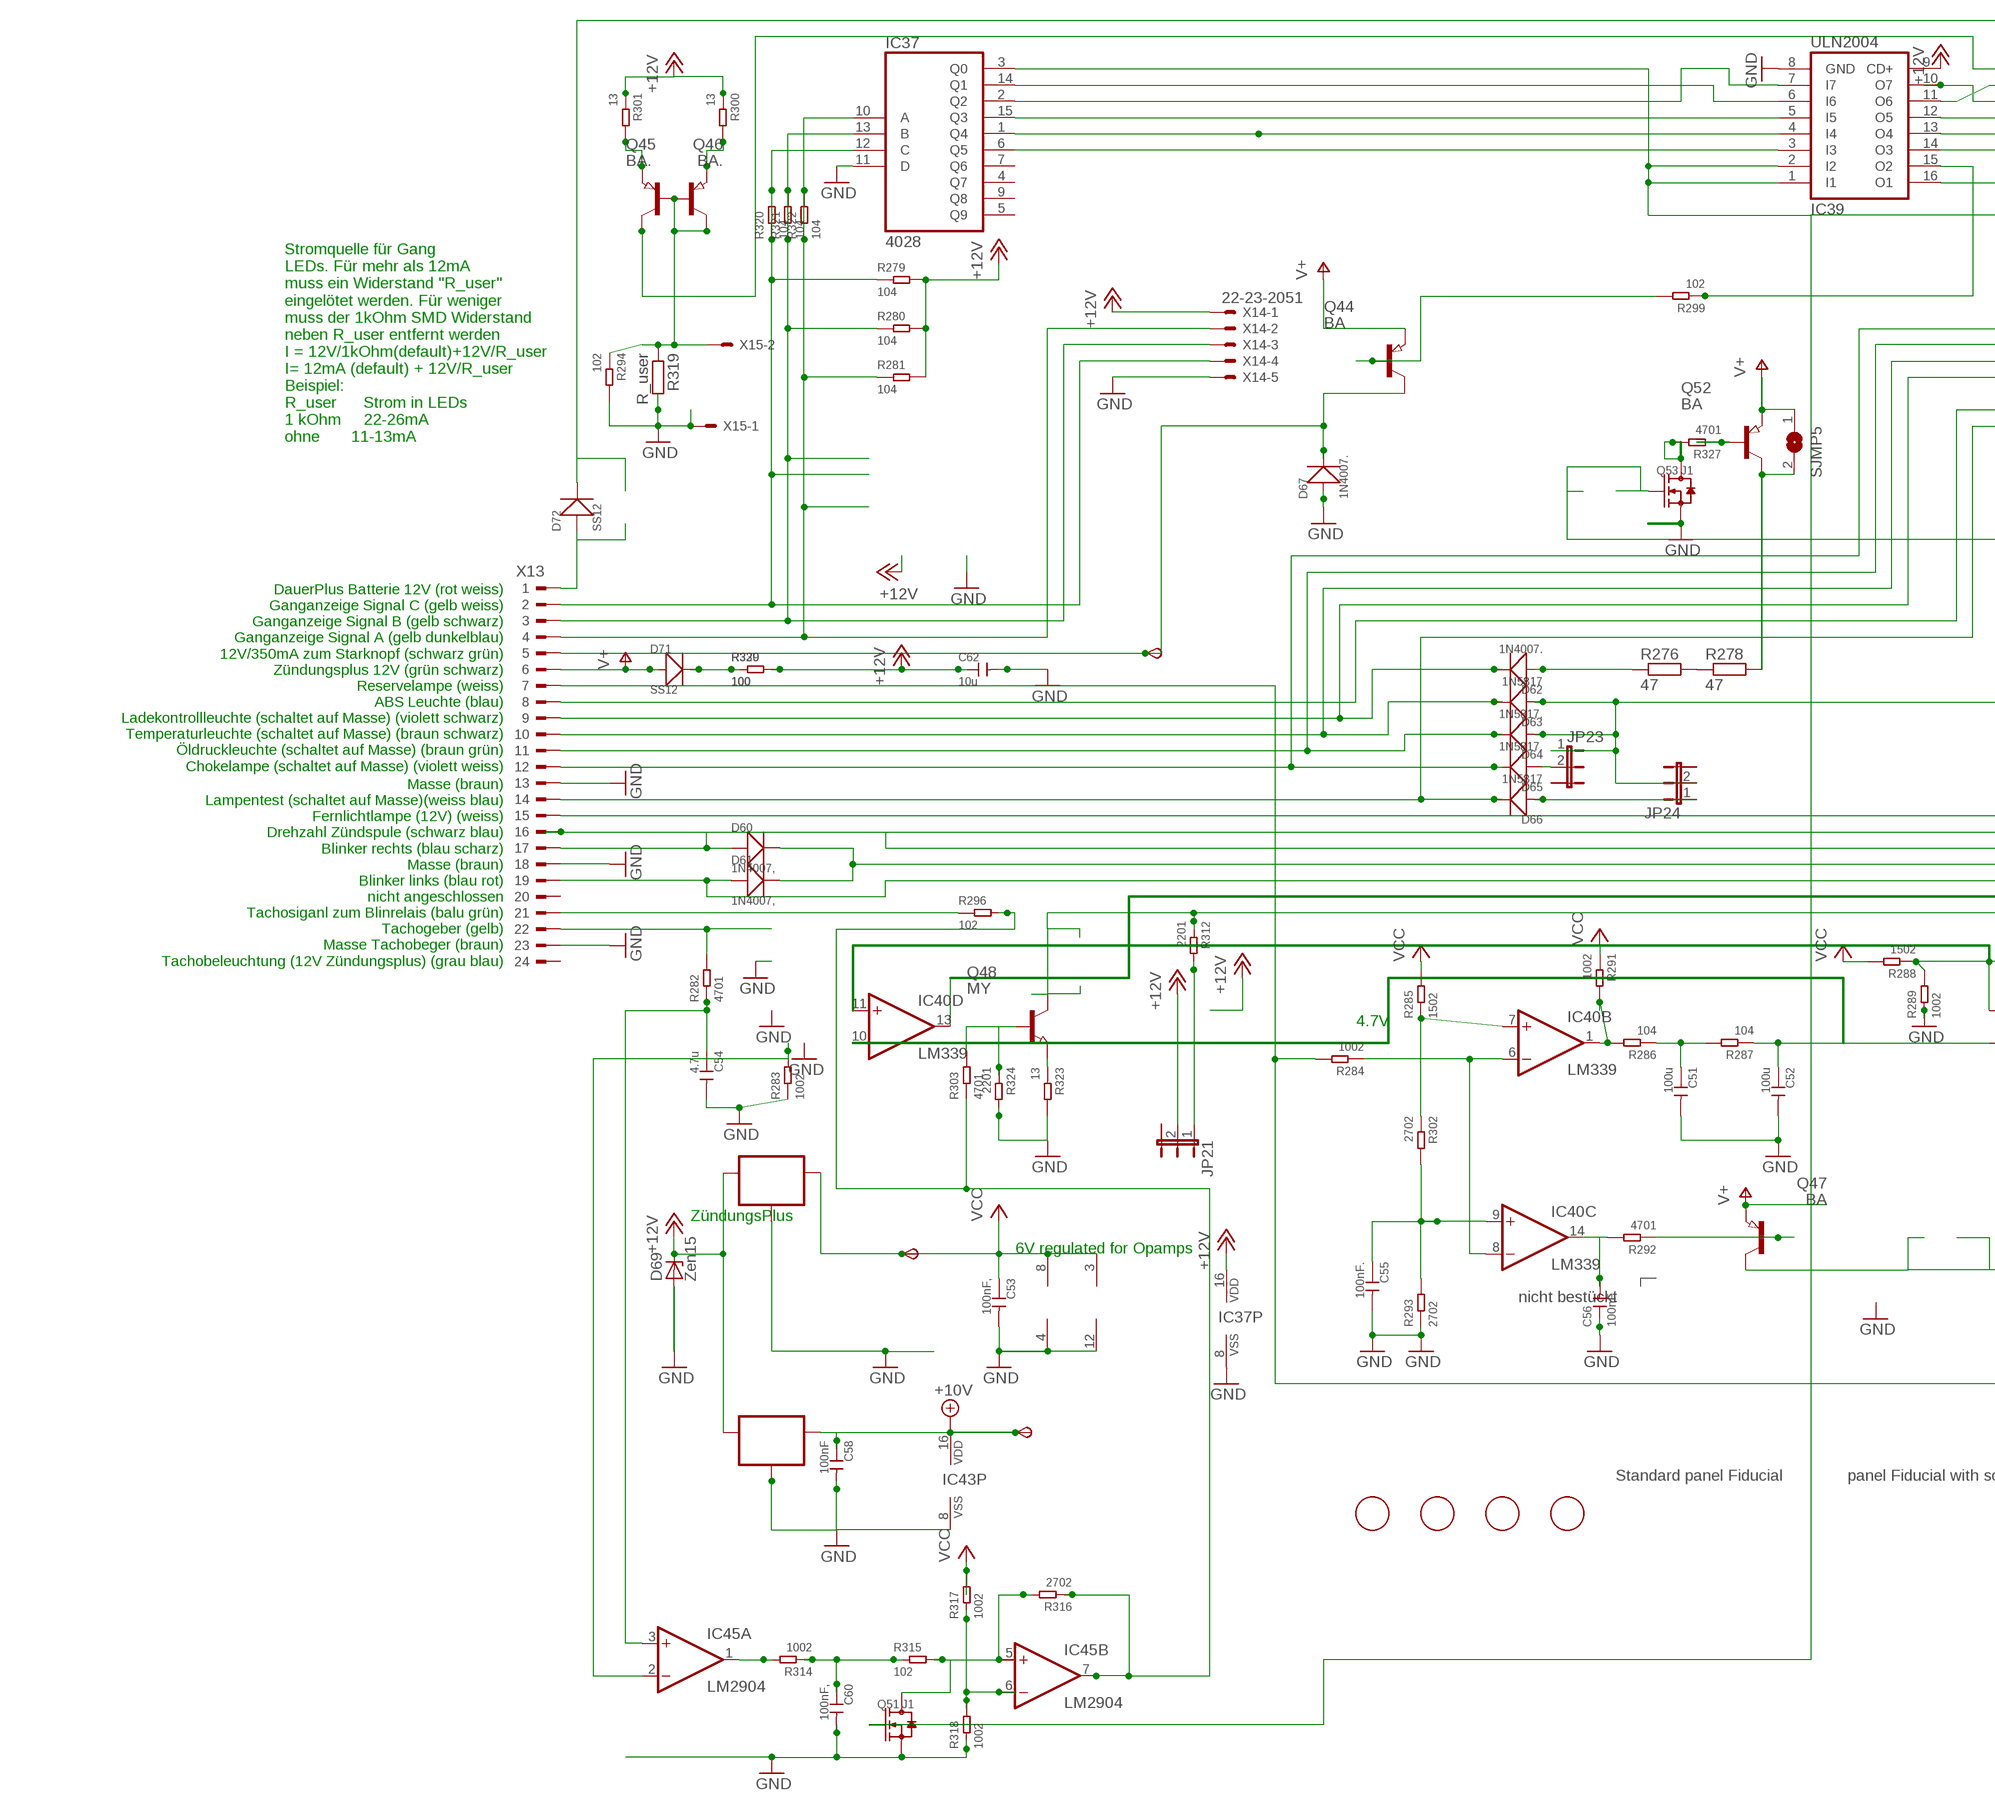
[diagram p11: schematic, sheet 7, part 1 of 2]
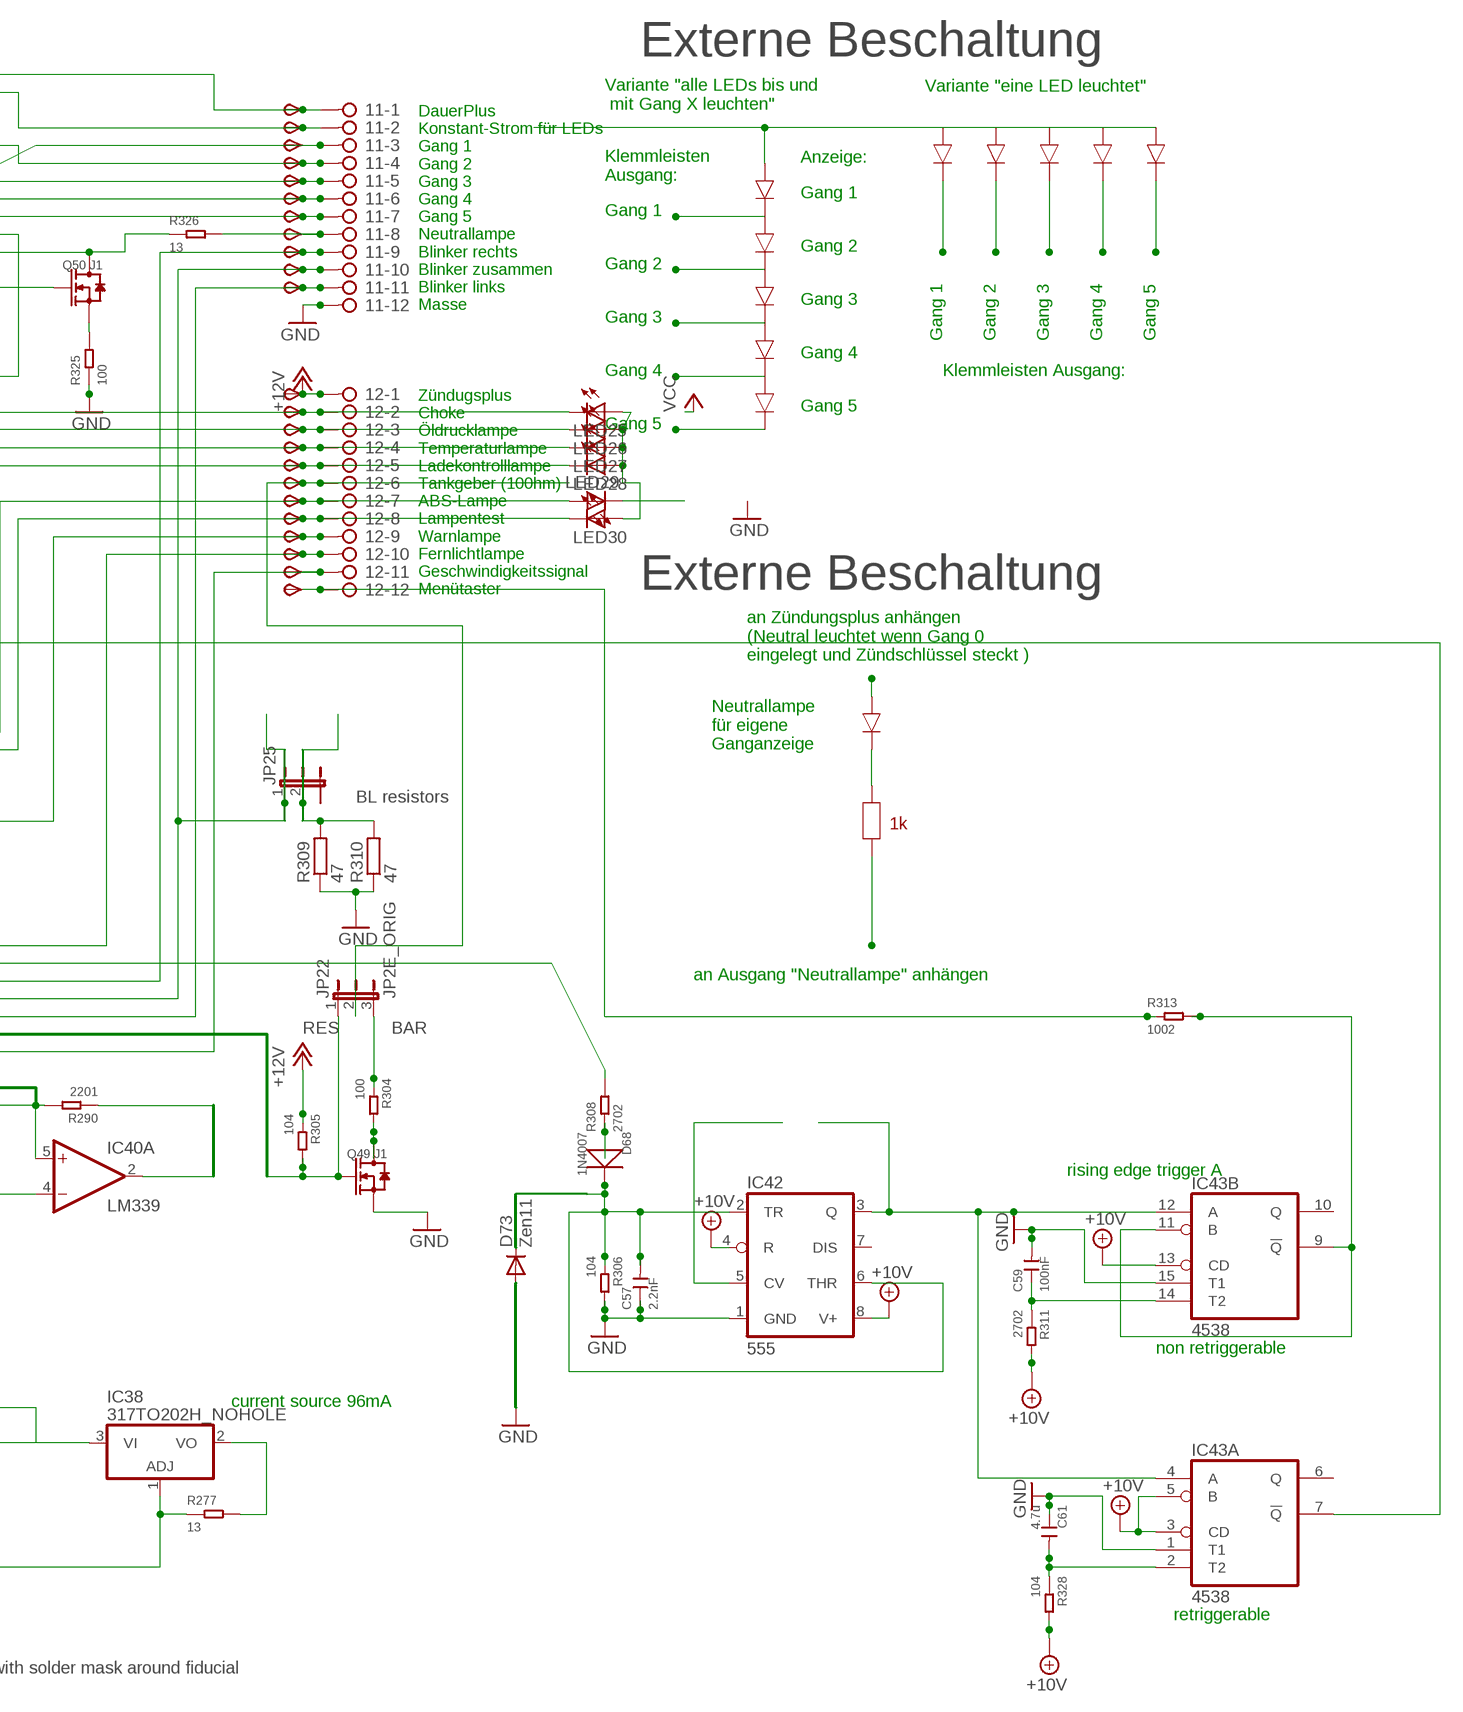
[diagram p12: schematic, sheet 7, part 2 of 2]
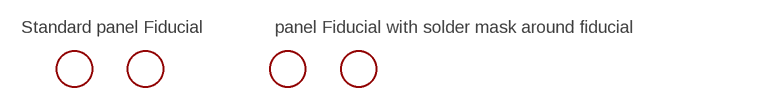
[diagram p13: schematic, sheet 8]
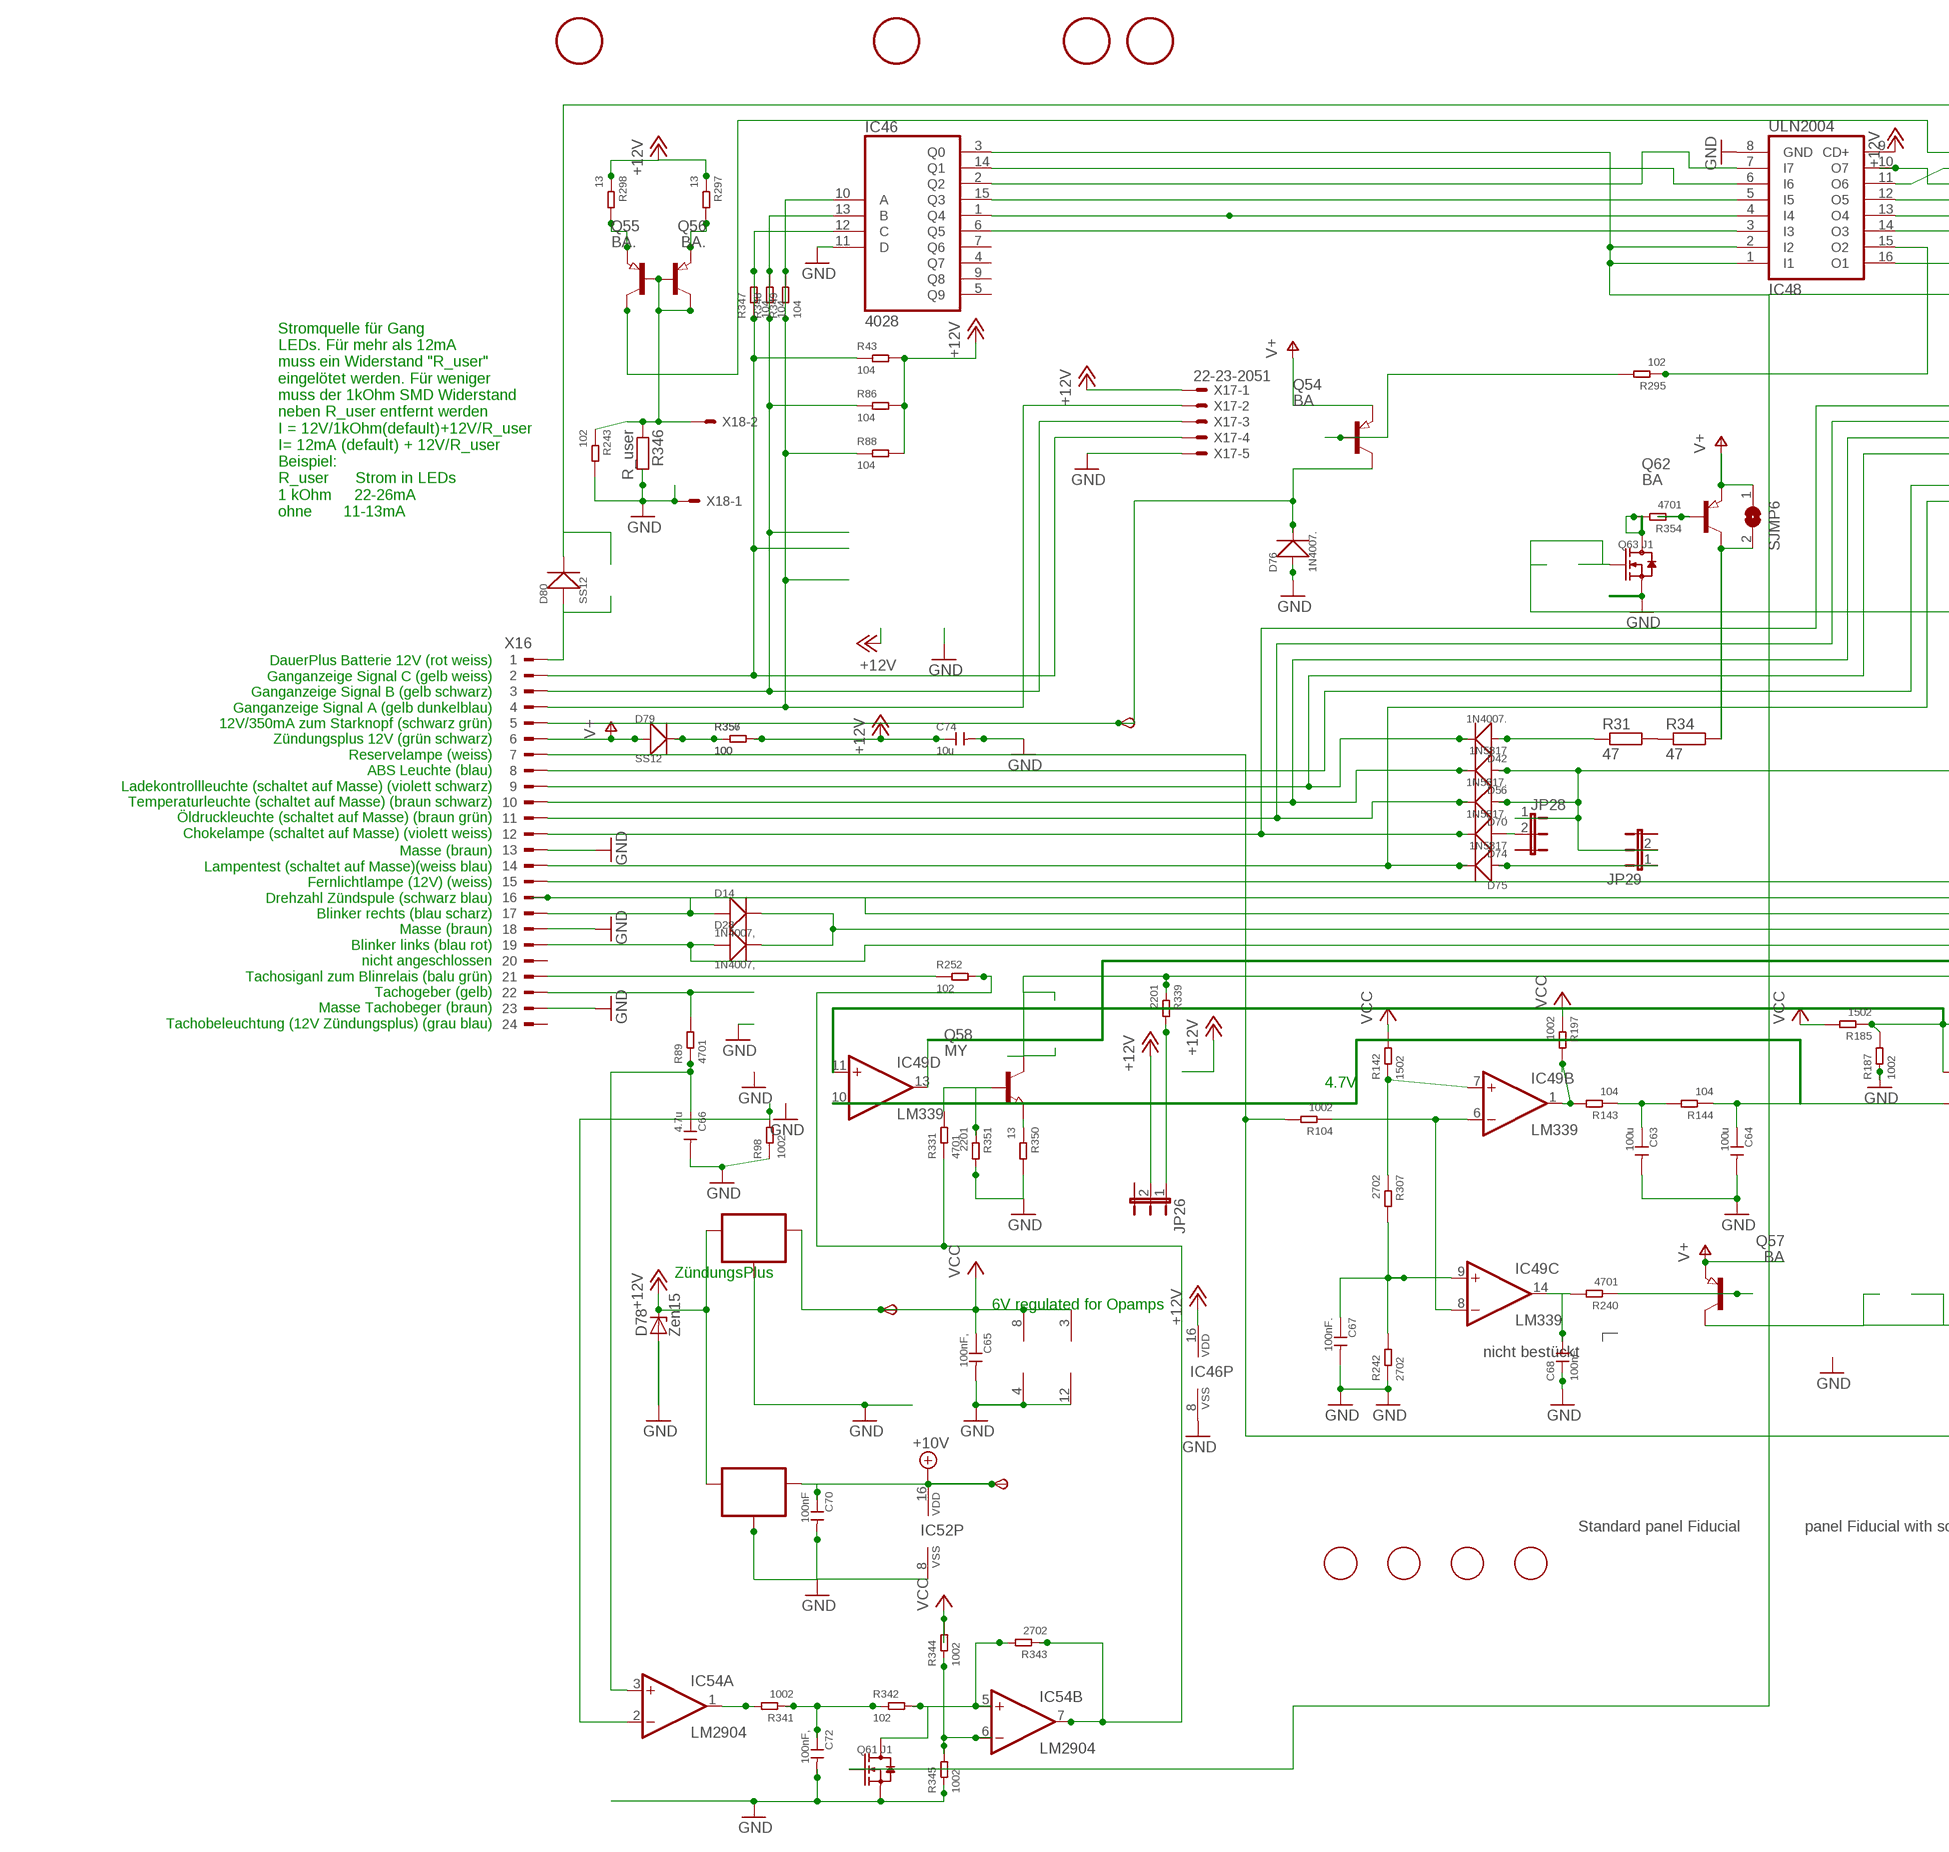
[diagram p14: schematic, sheet 9, part 1 of 2]
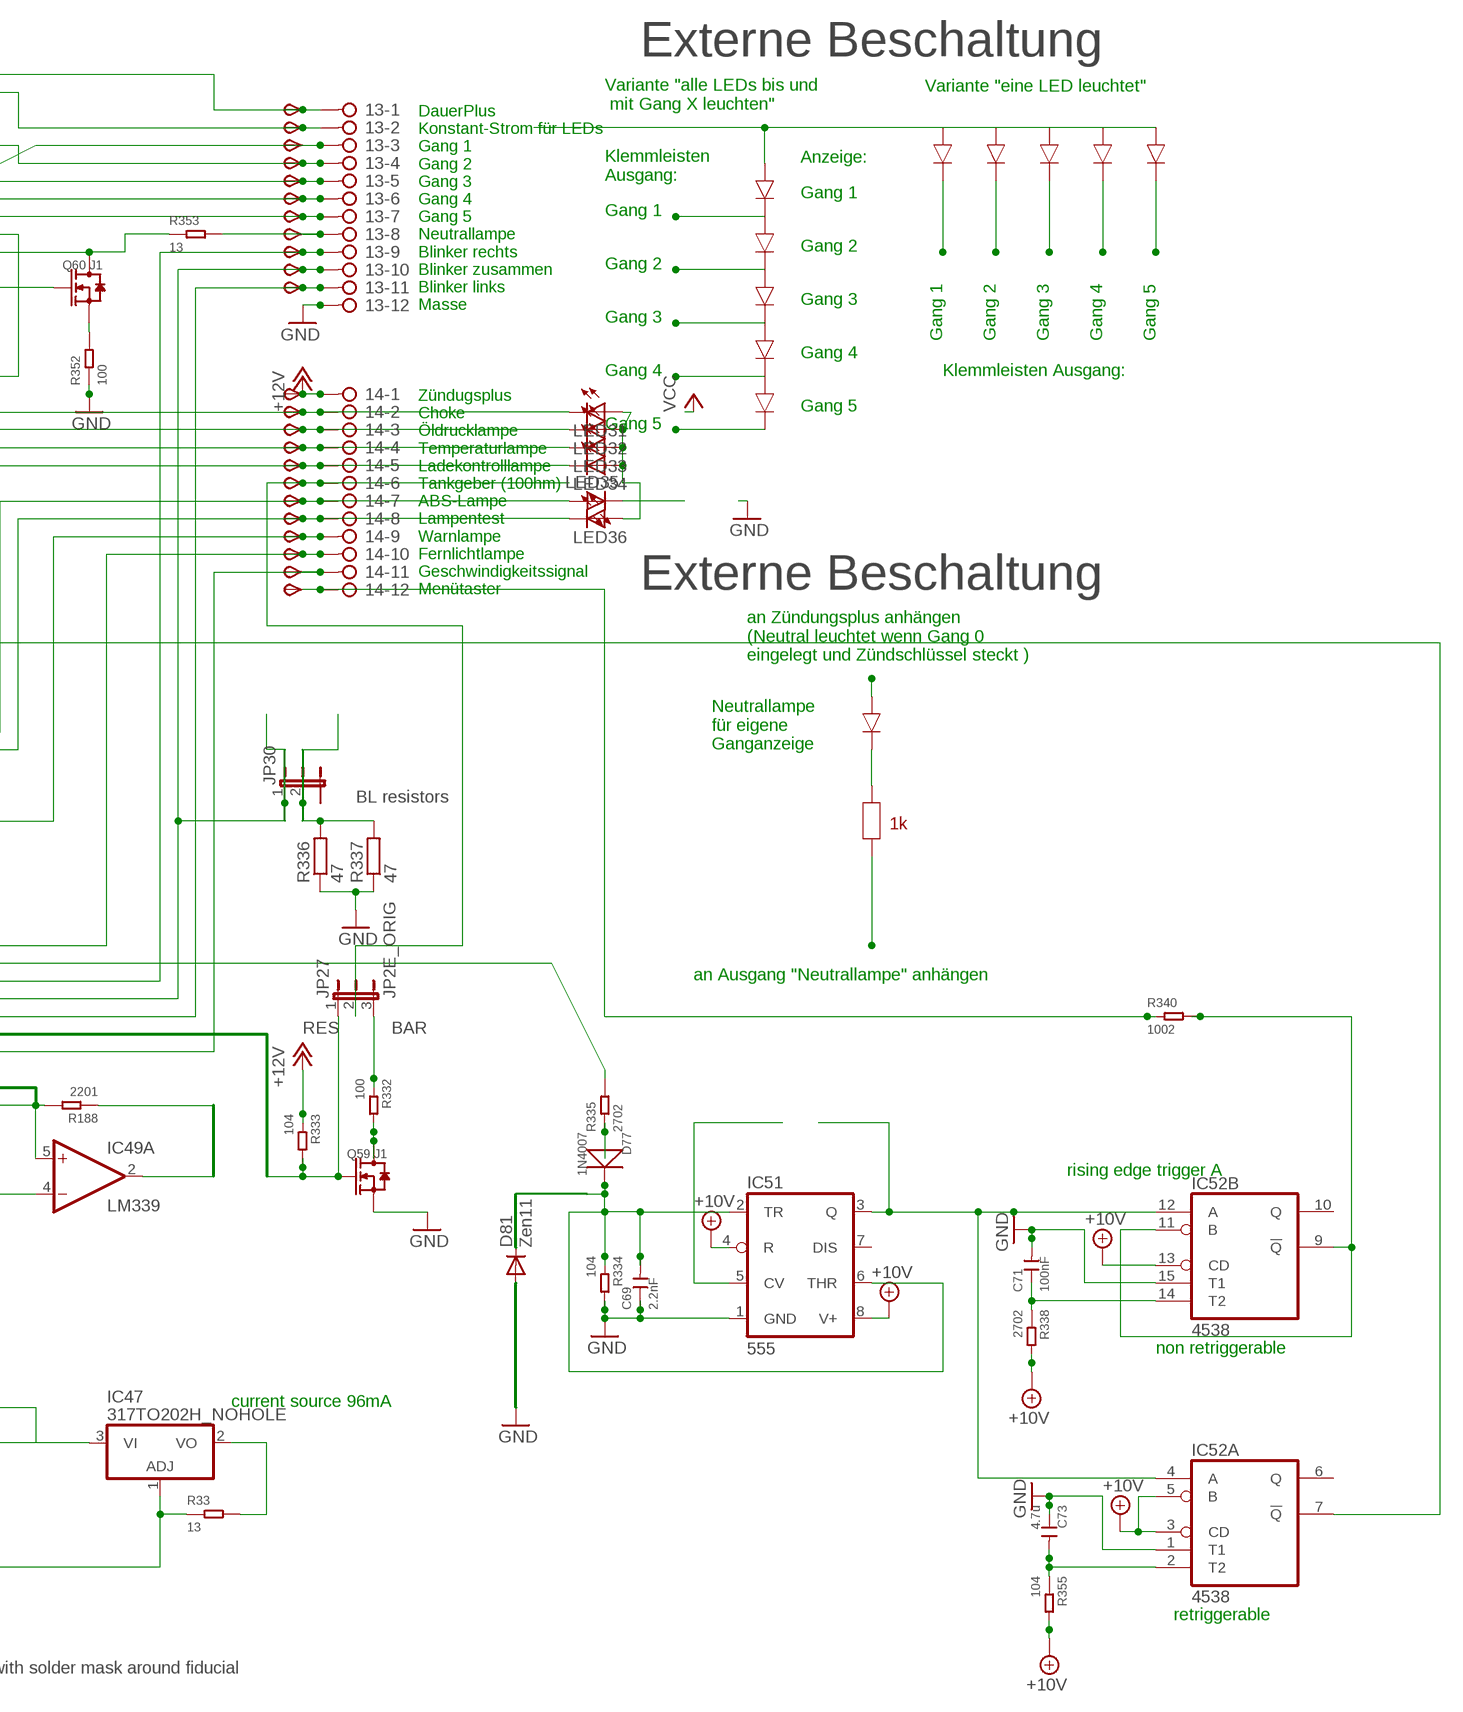
[diagram p15: schematic, sheet 9, part 2 of 2]
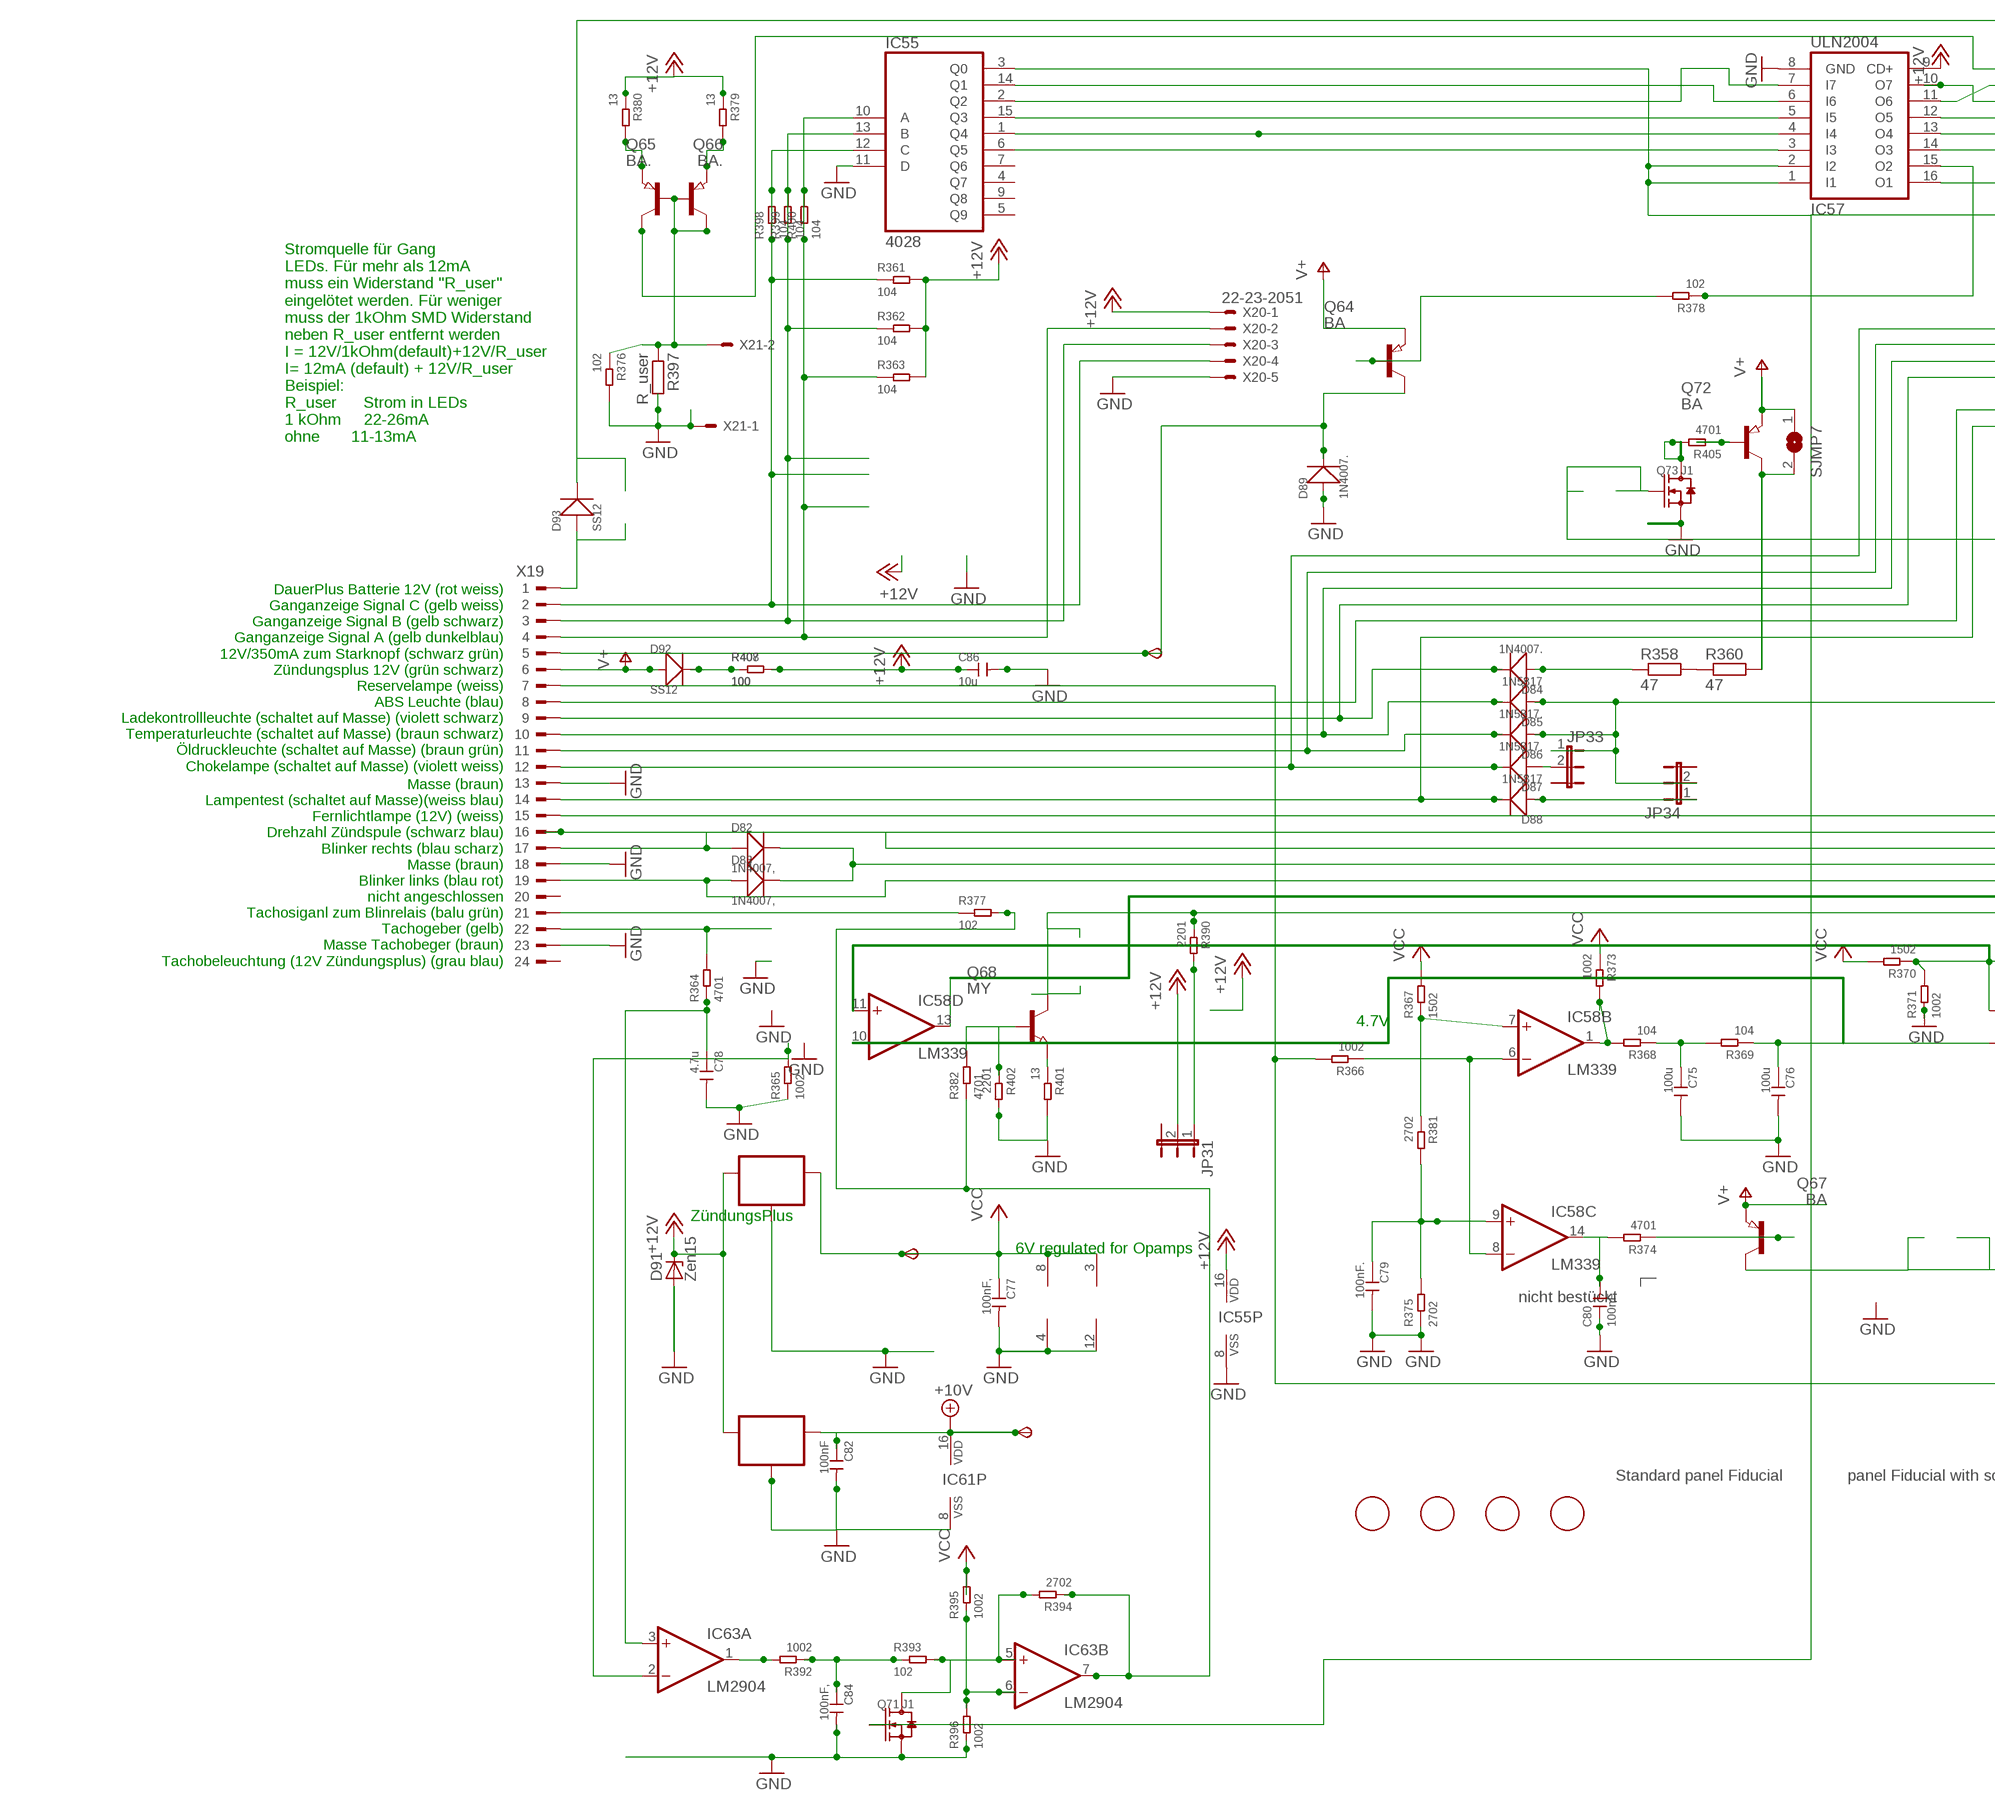
[diagram p16: schematic, sheet 10, part 1 of 2]
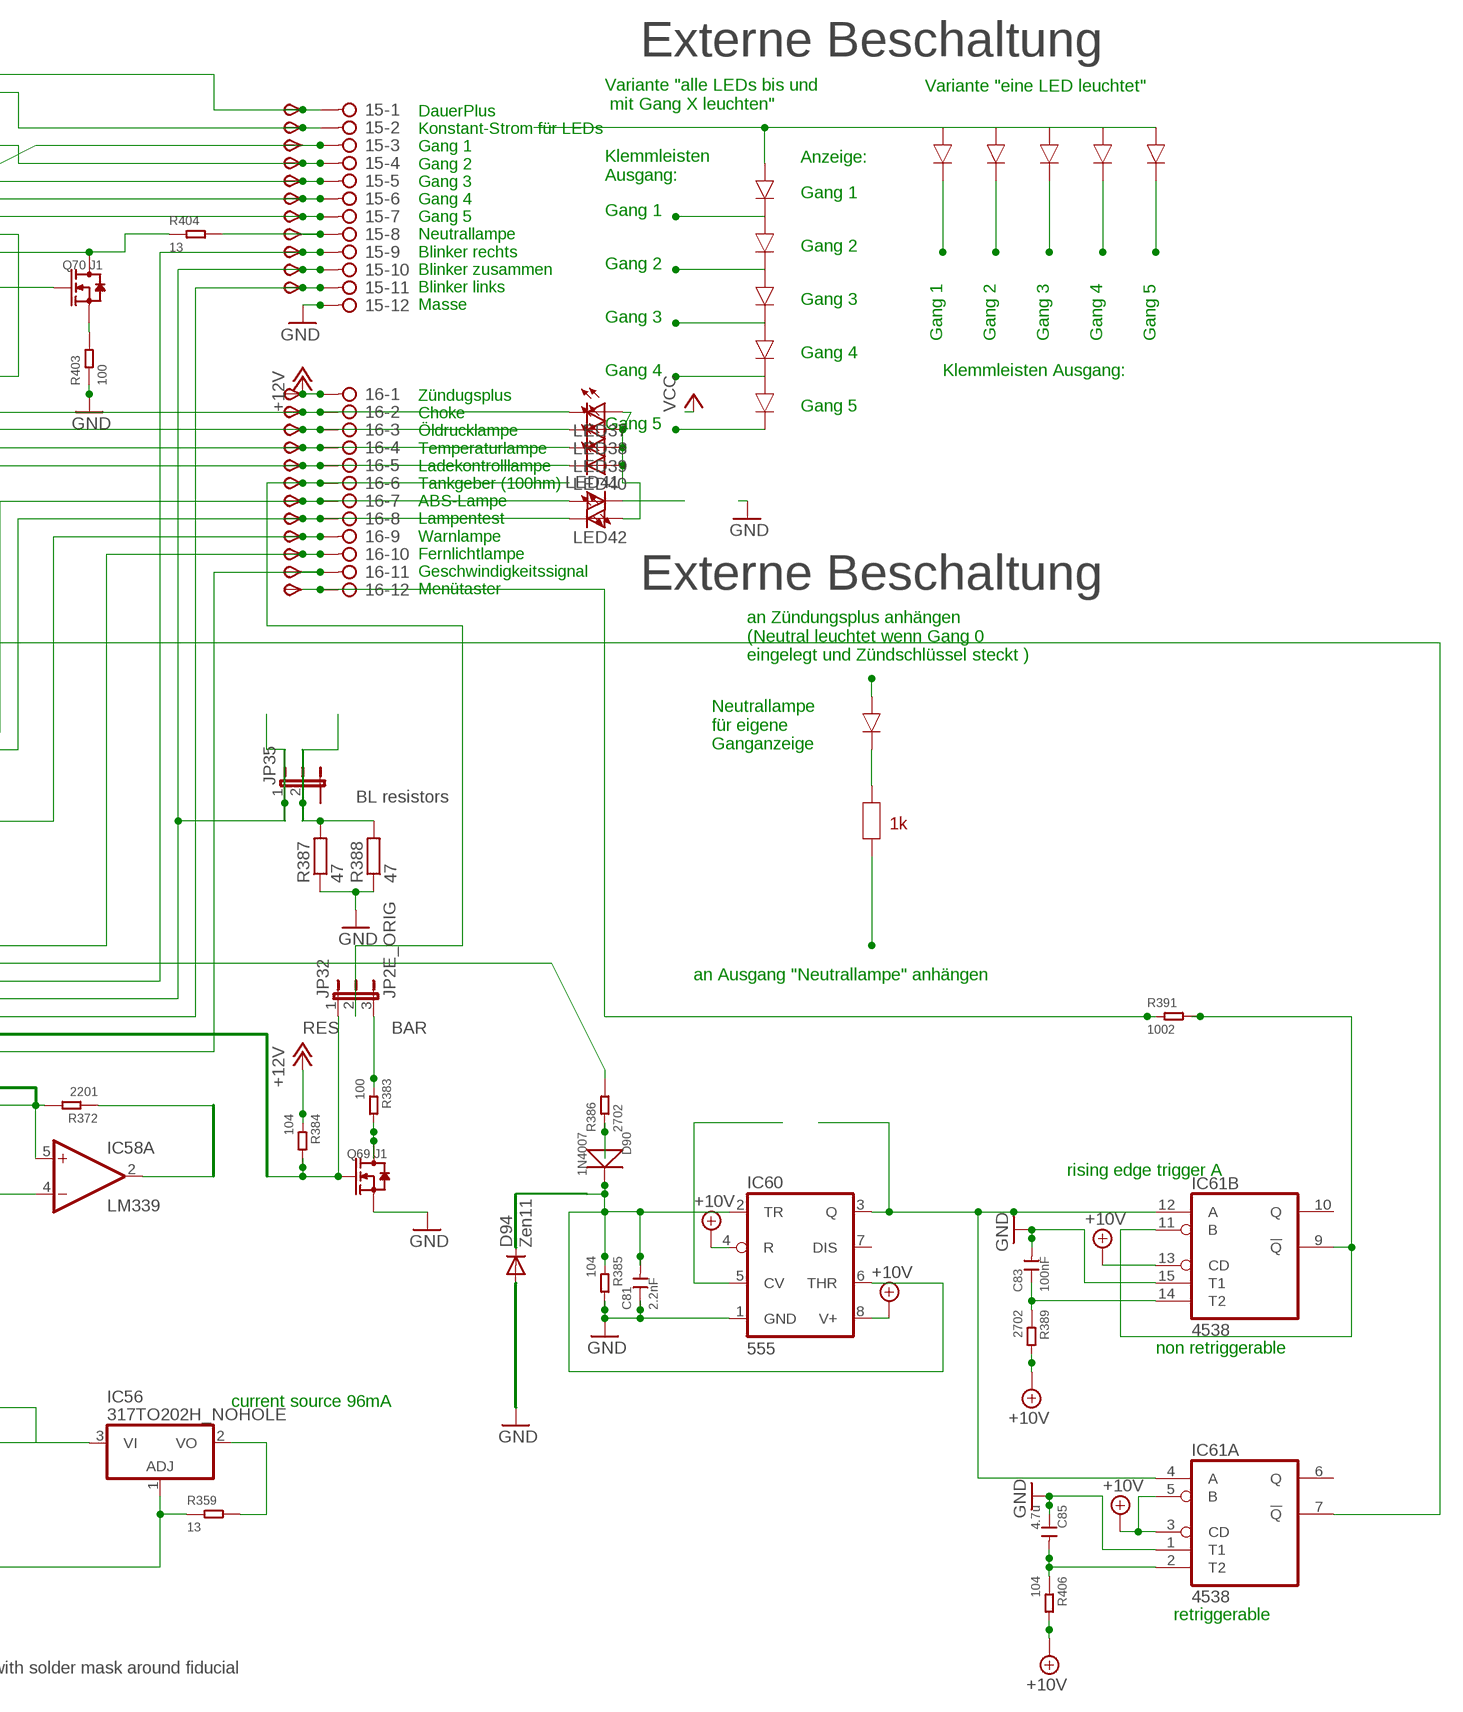
[diagram p17: schematic, sheet 10, part 2 of 2]
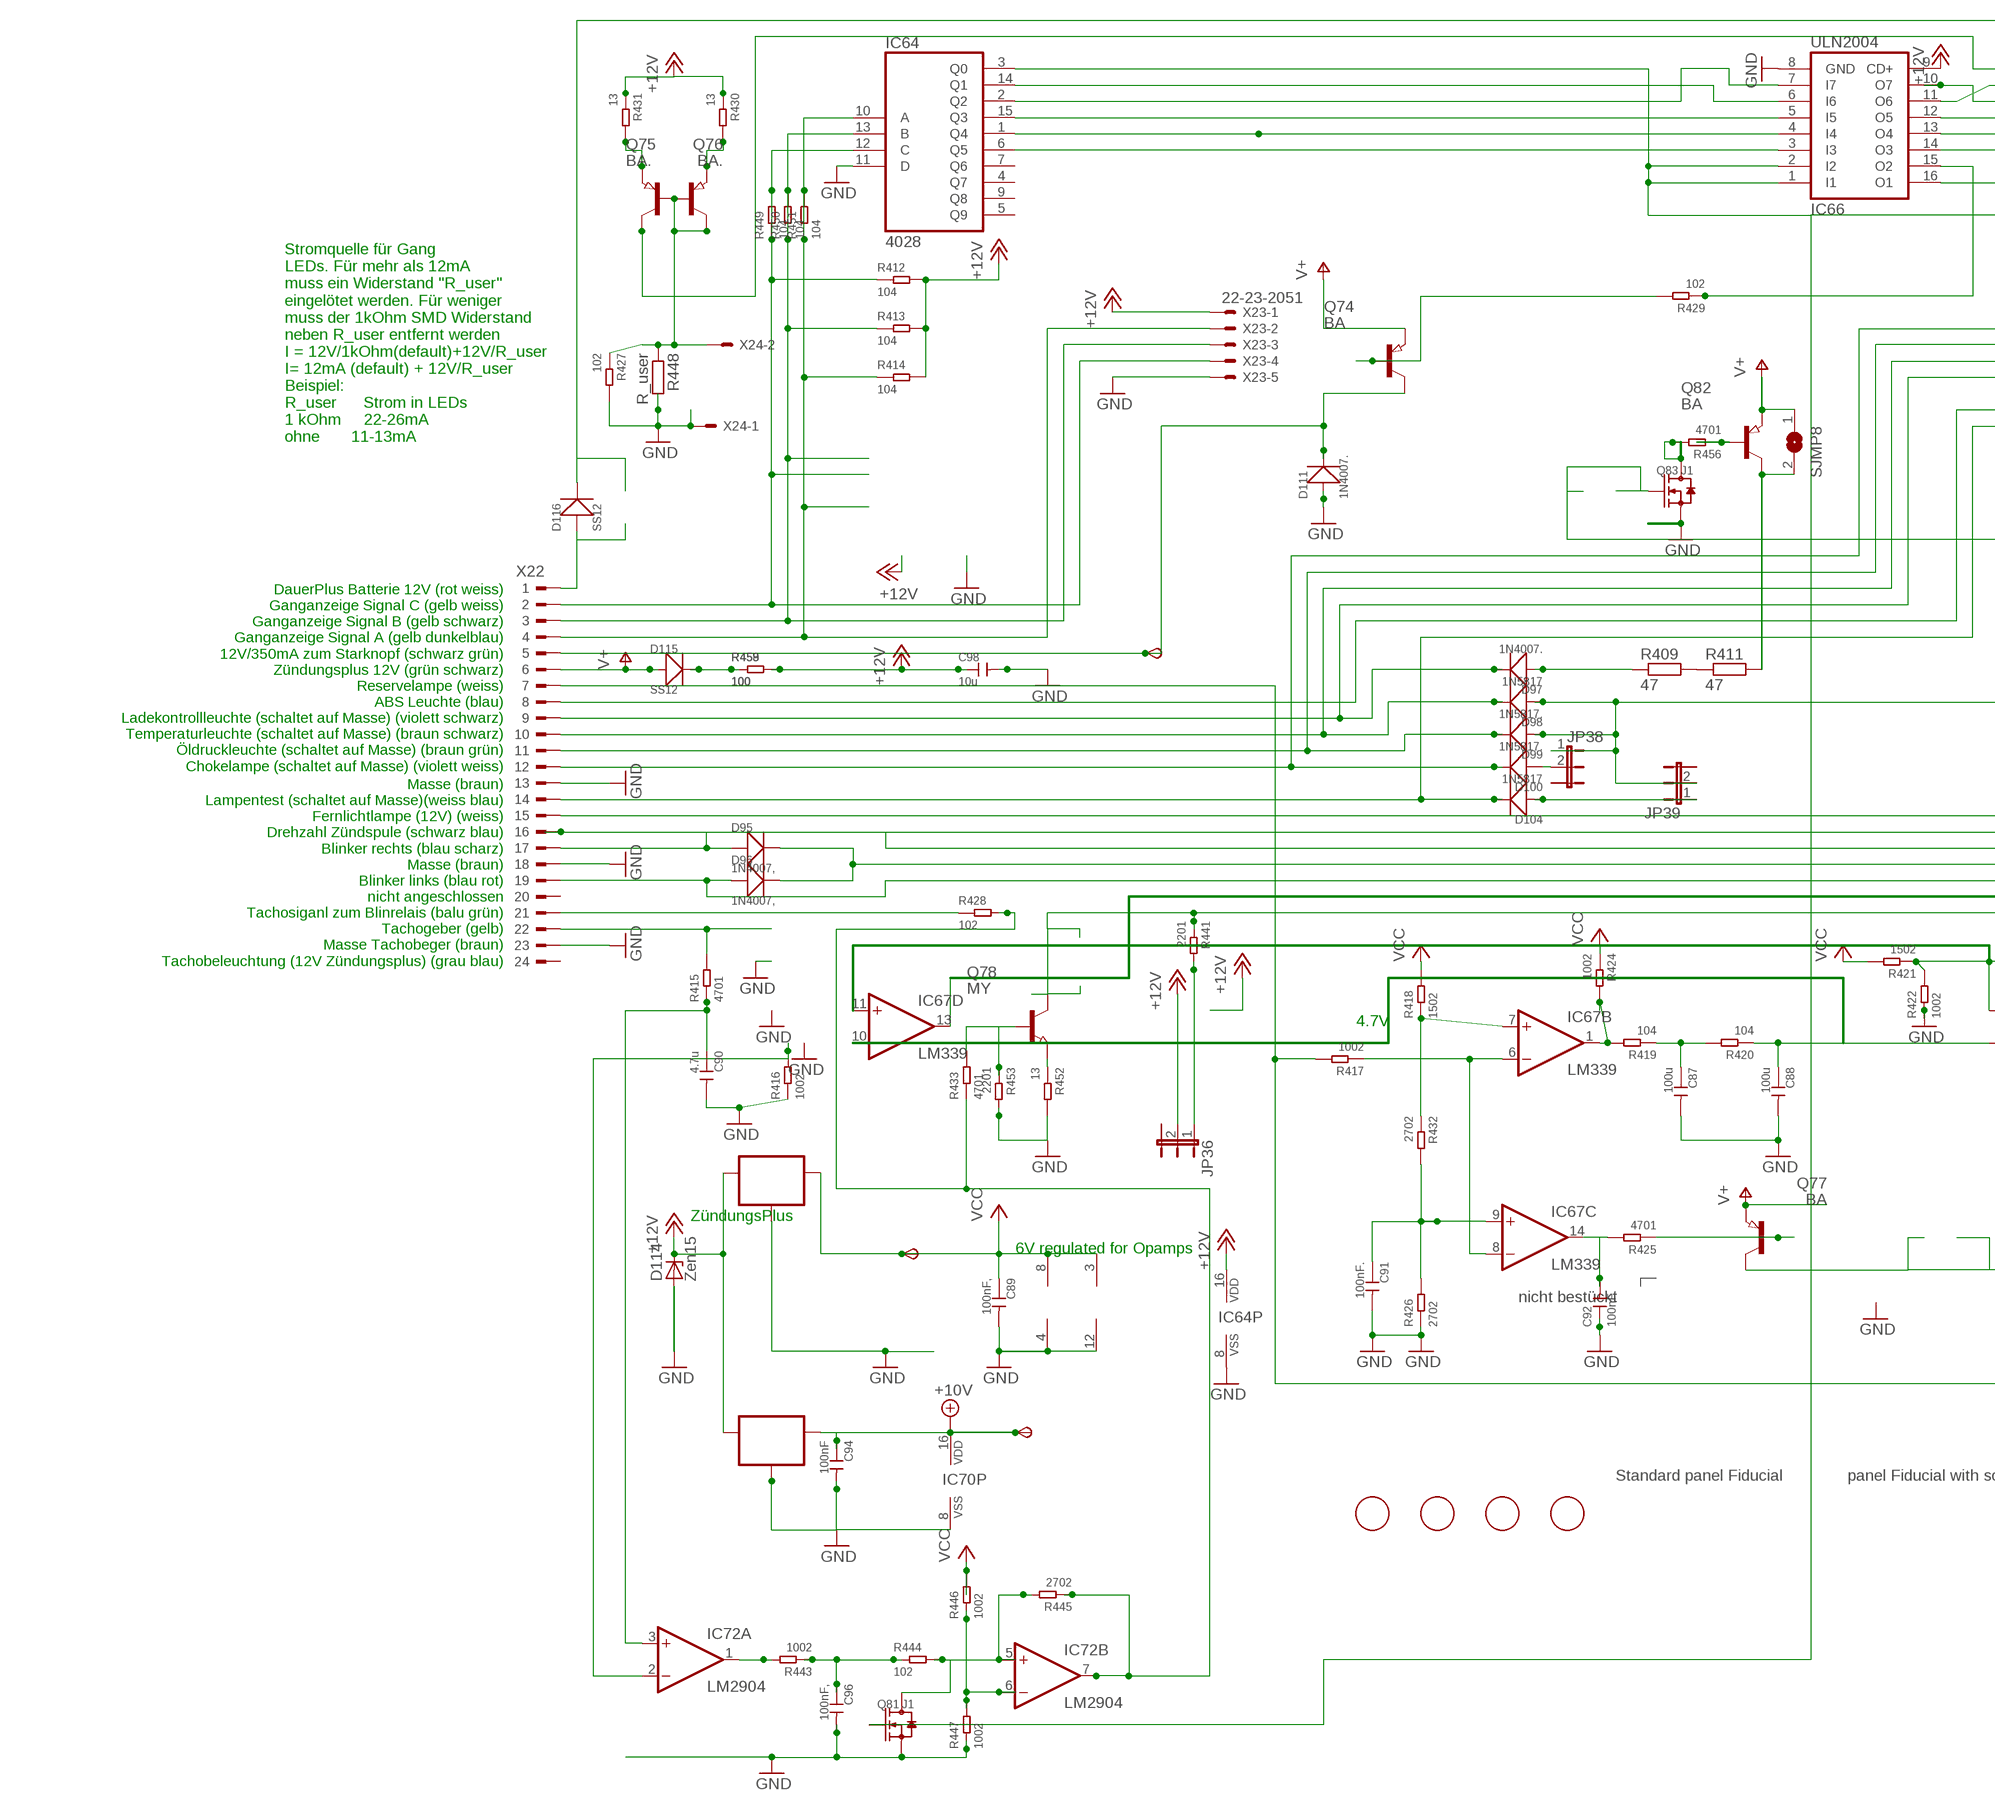
[diagram p18: schematic, sheet 11, part 1 of 2]
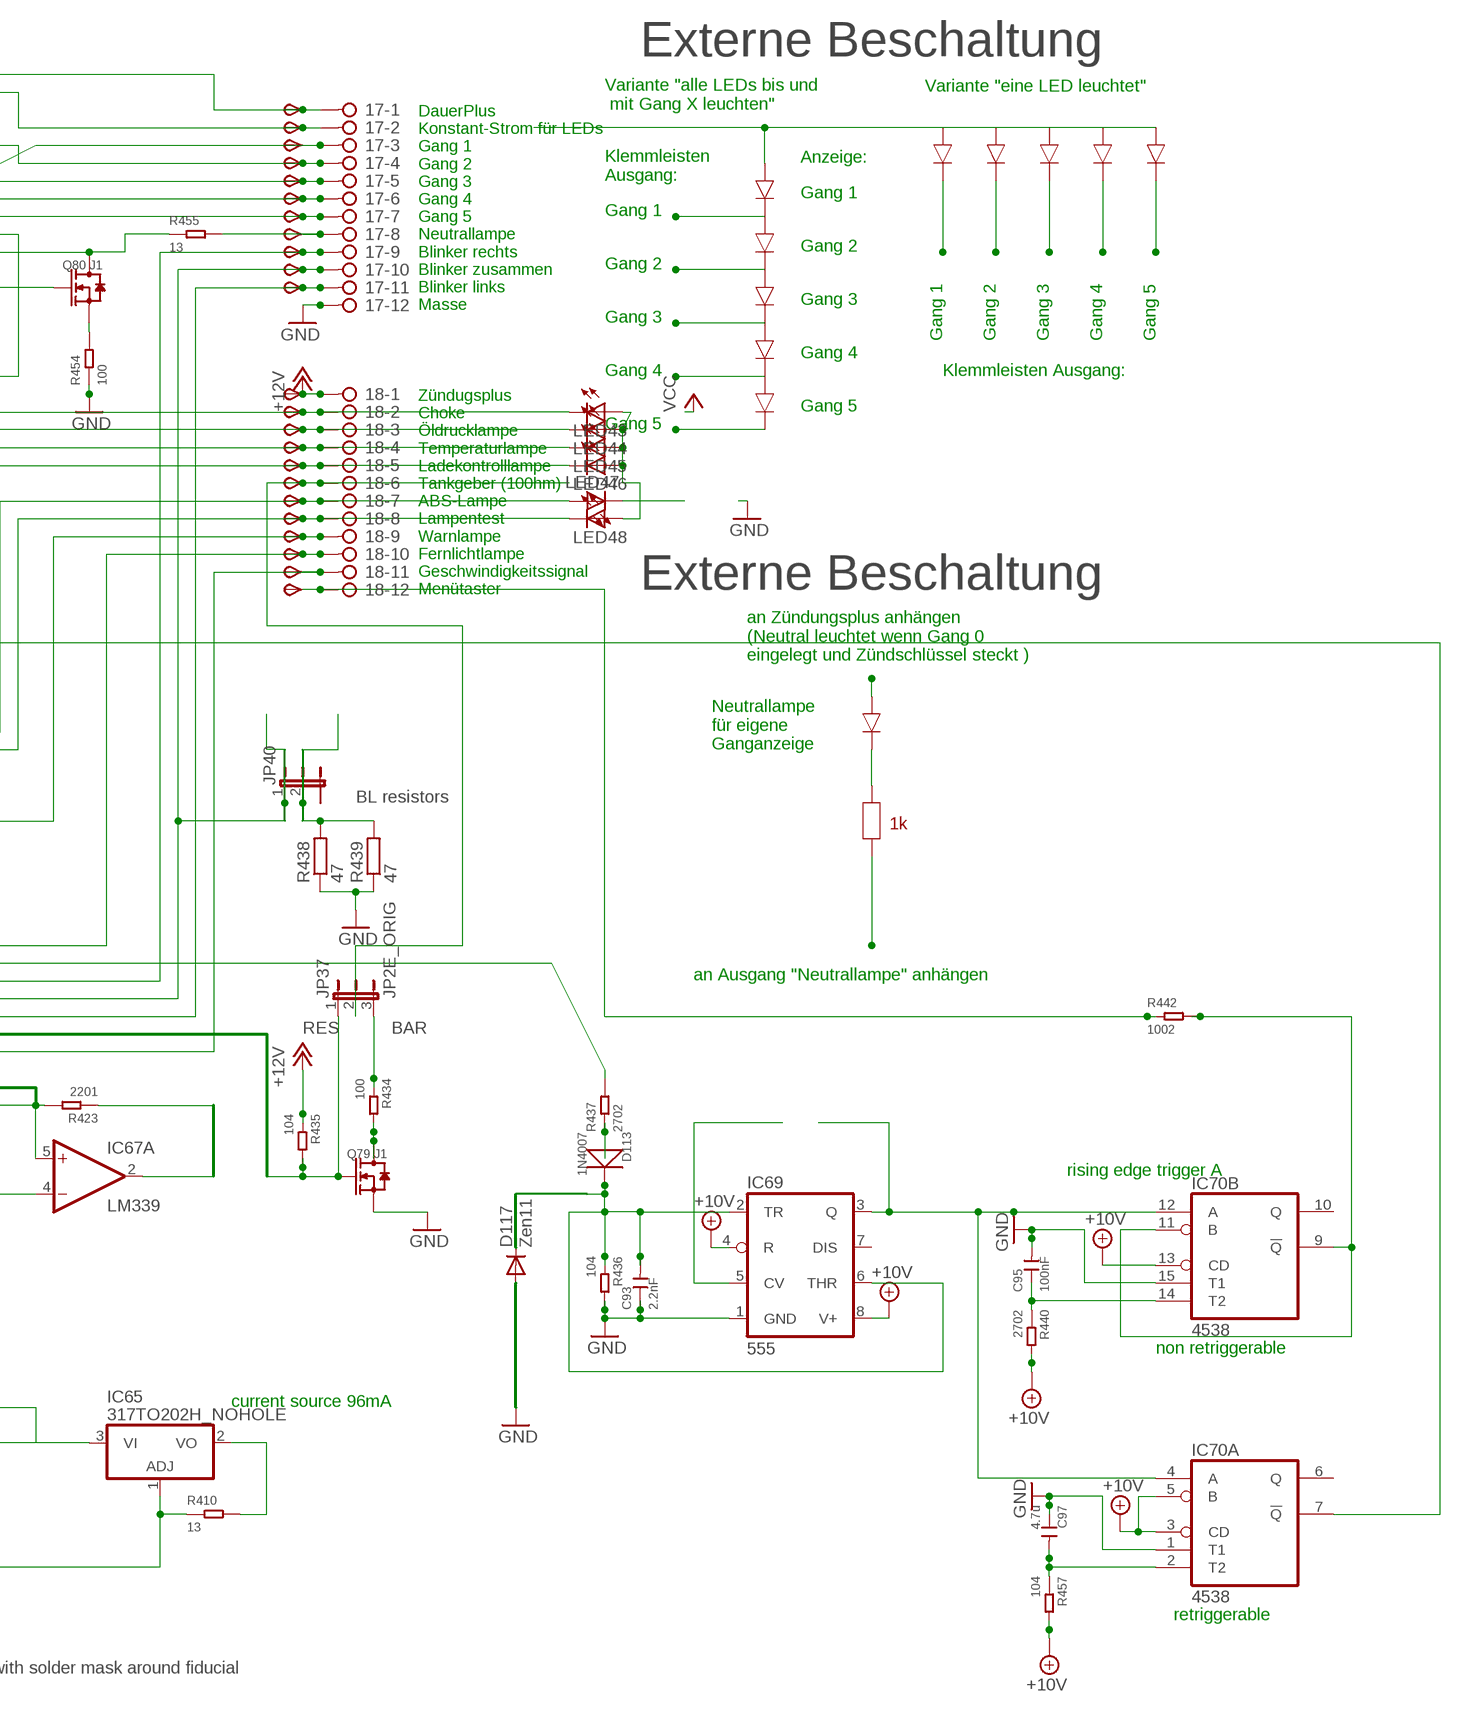
[diagram p19: schematic, sheet 11, part 2 of 2]
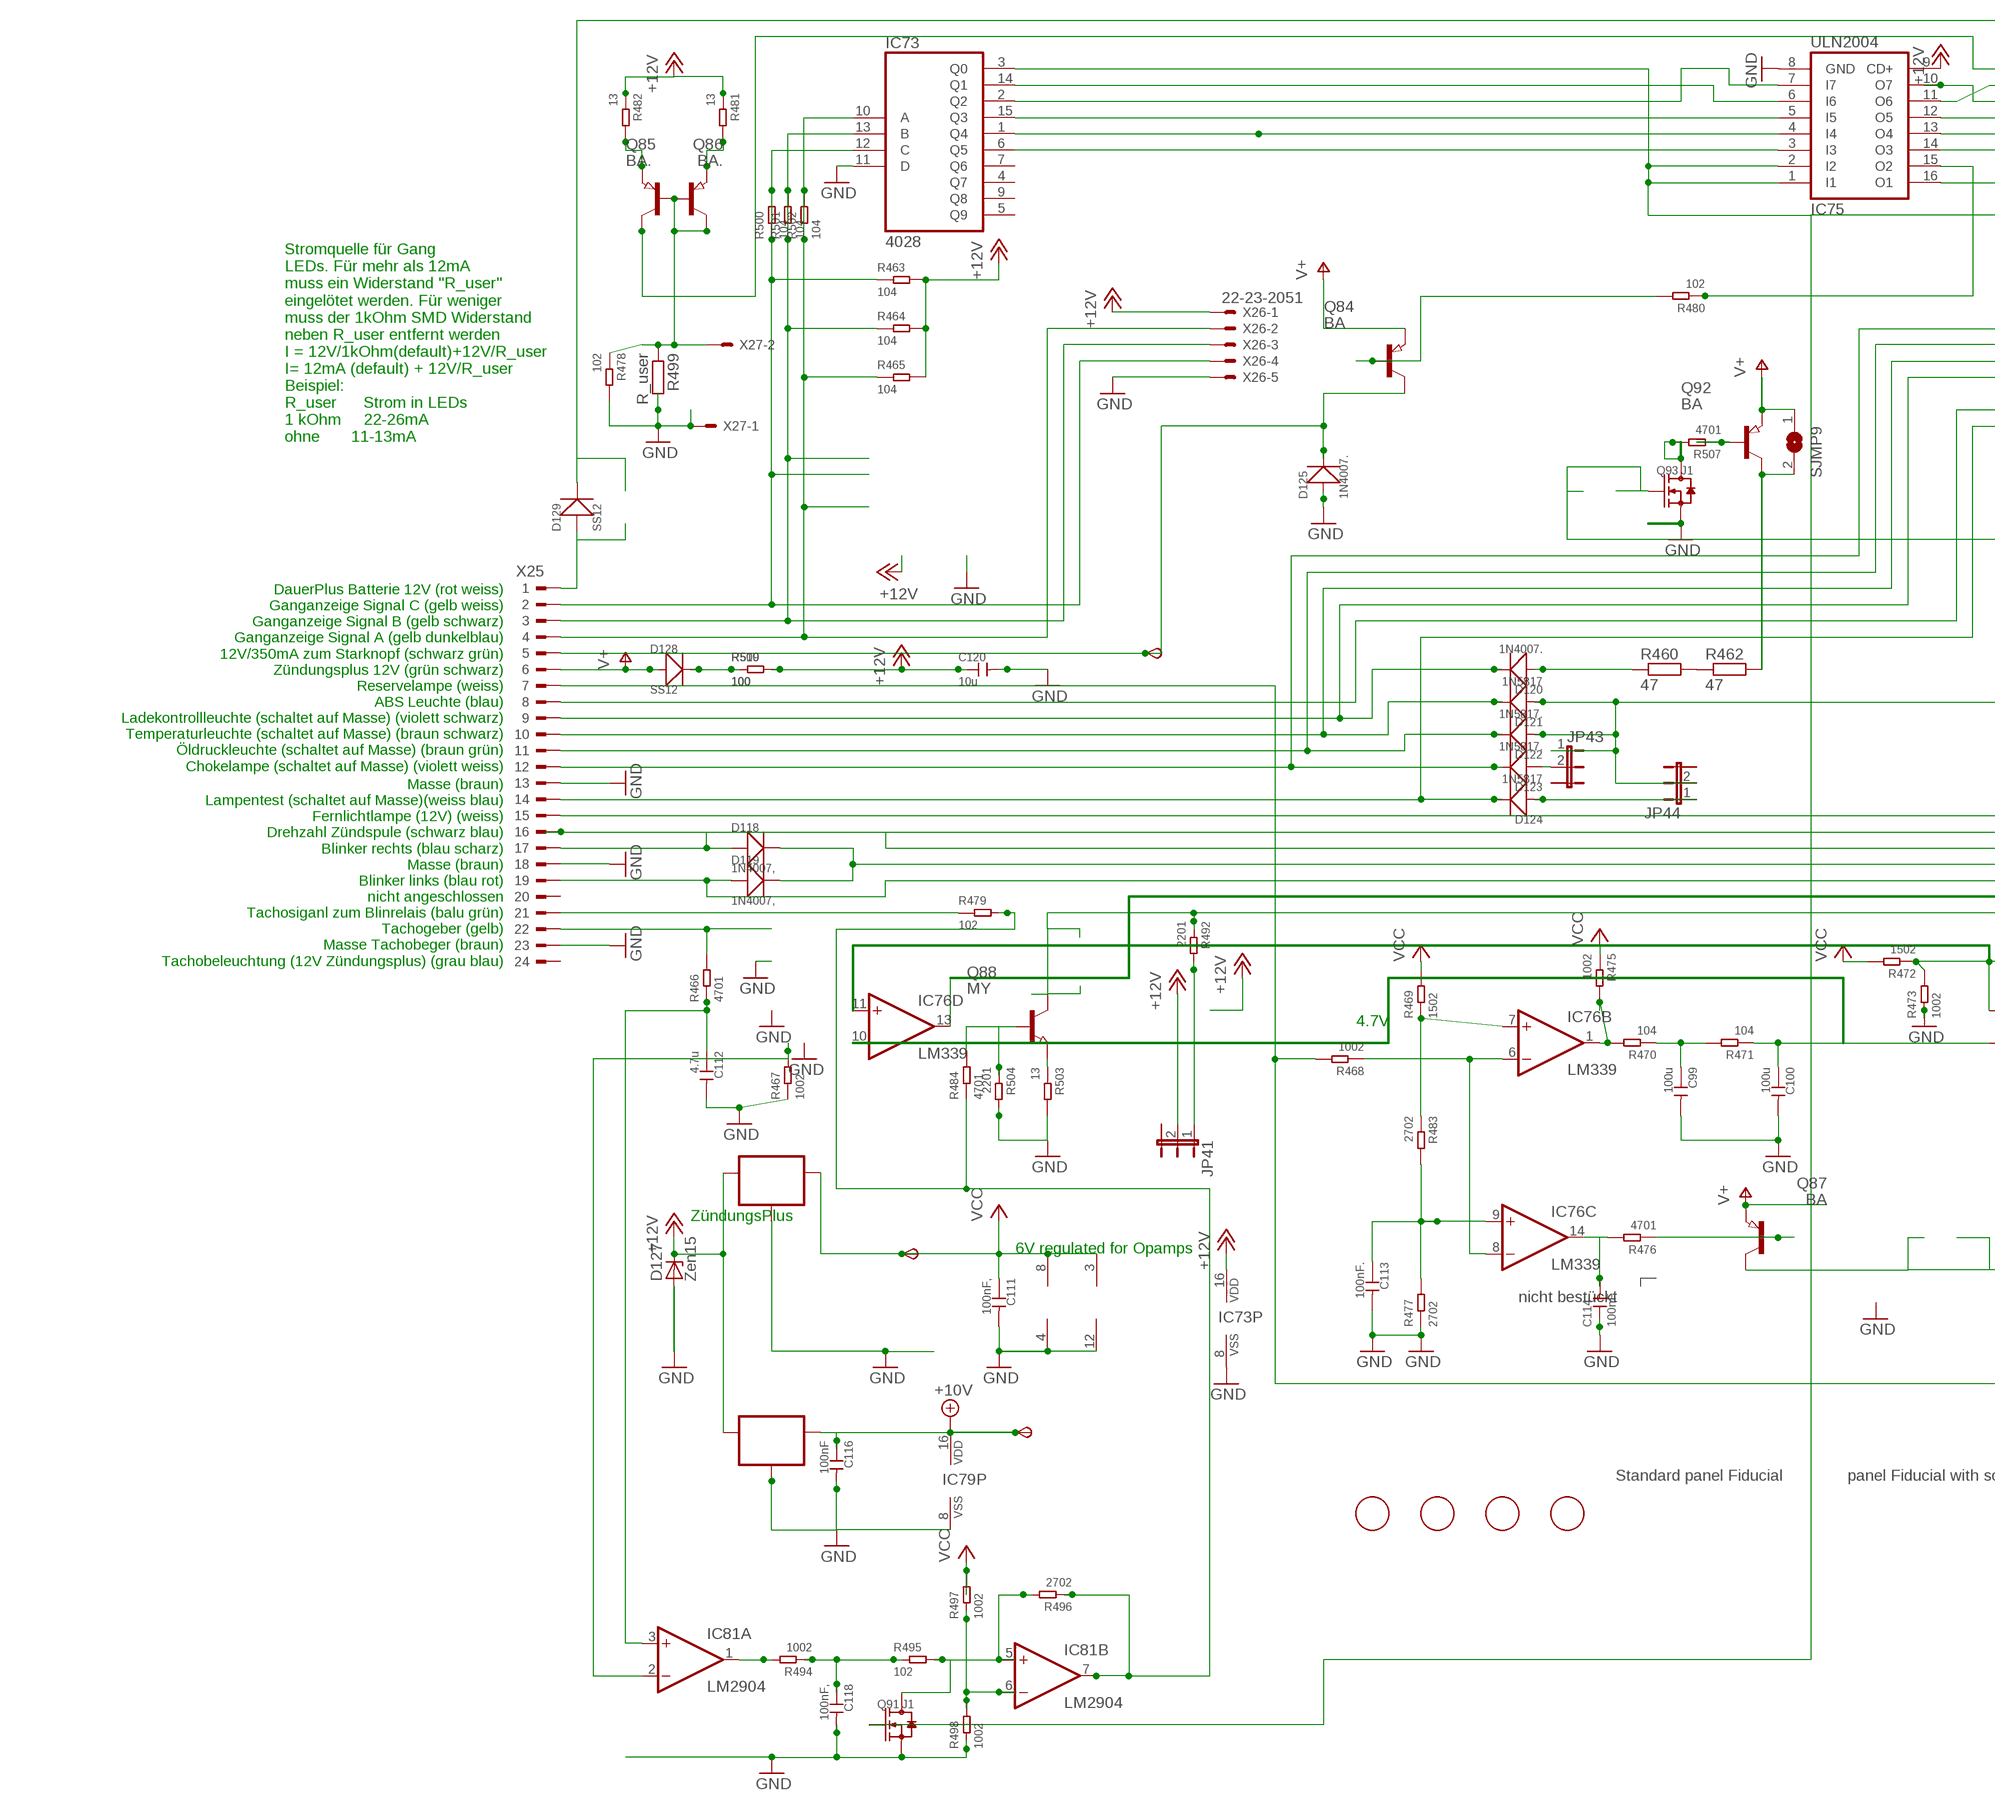
[diagram p20: schematic, sheet 12, part 1 of 2]
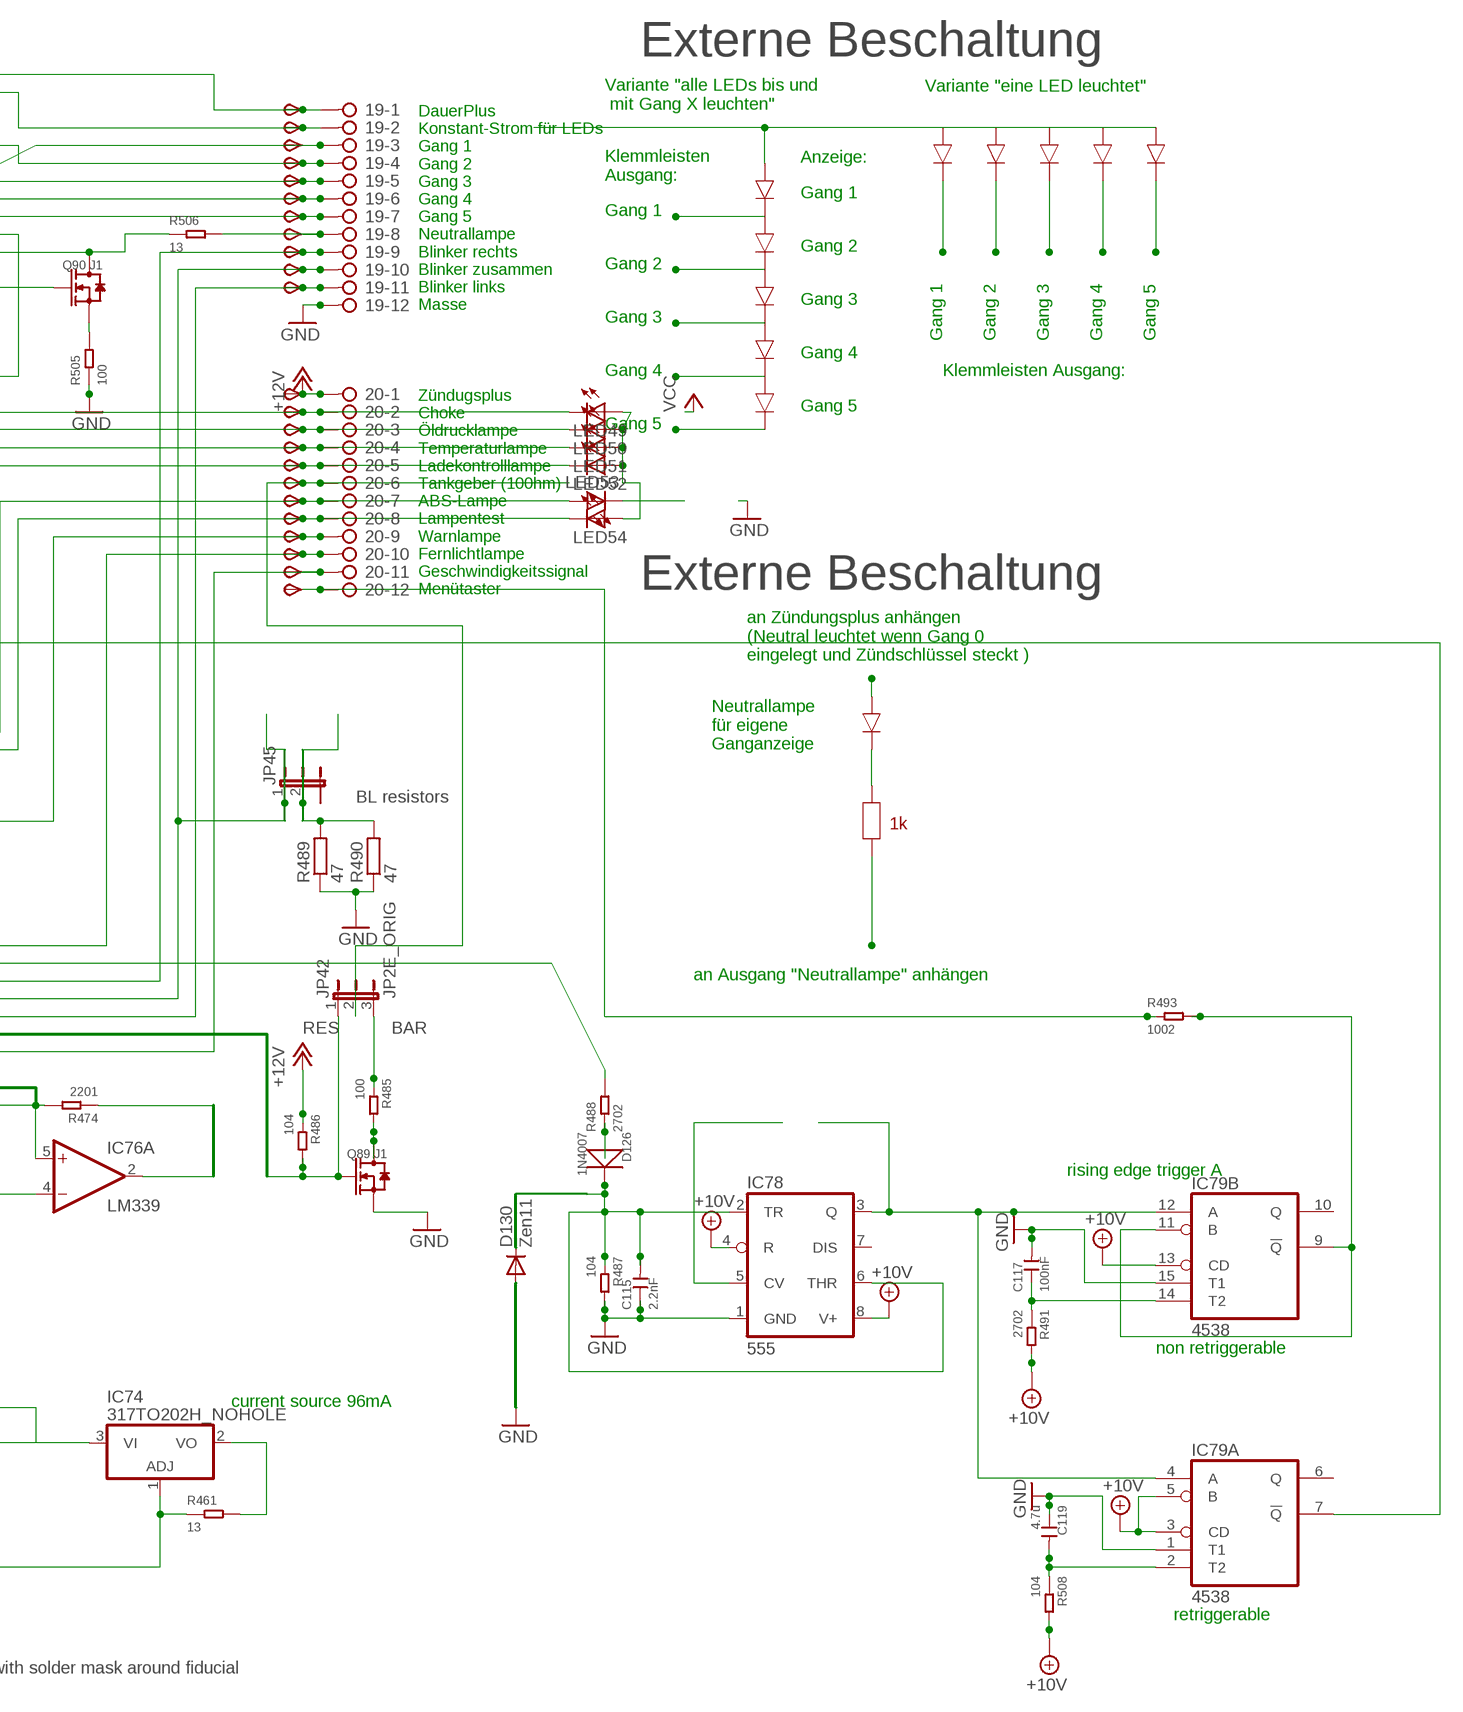
[diagram p21: schematic, sheet 12, part 2 of 2]
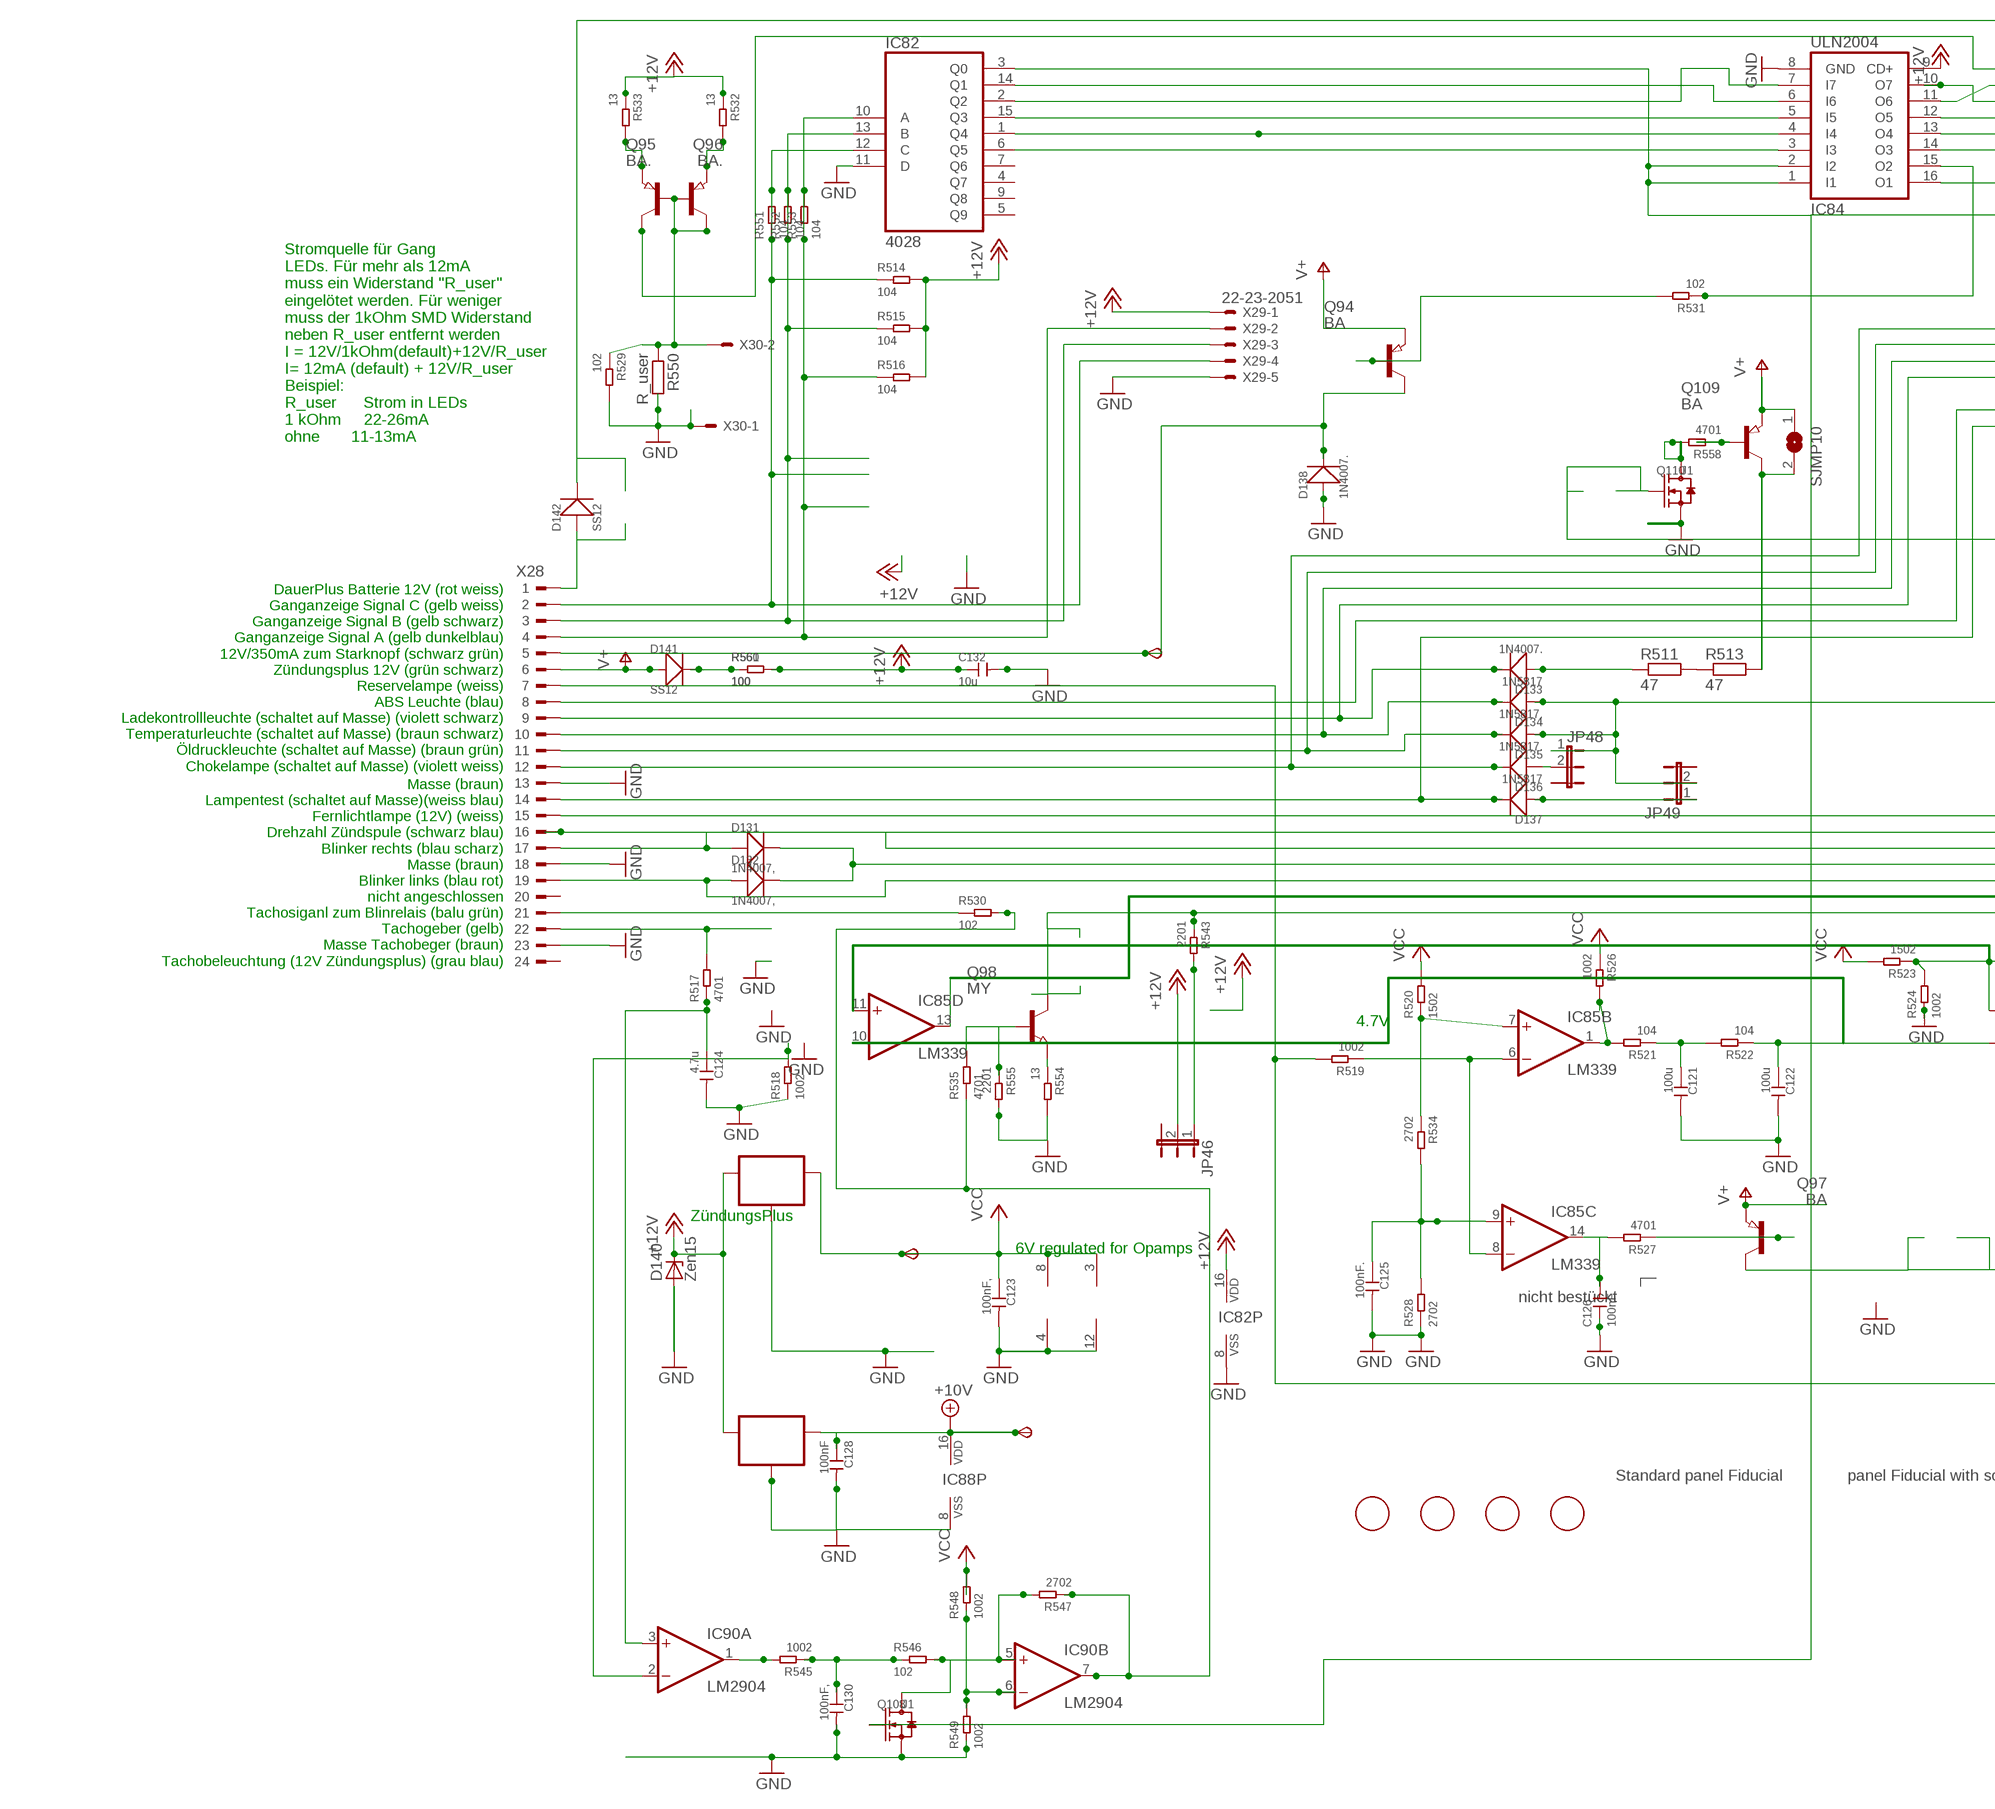
[diagram p22: schematic, sheet 13, part 1 of 2]
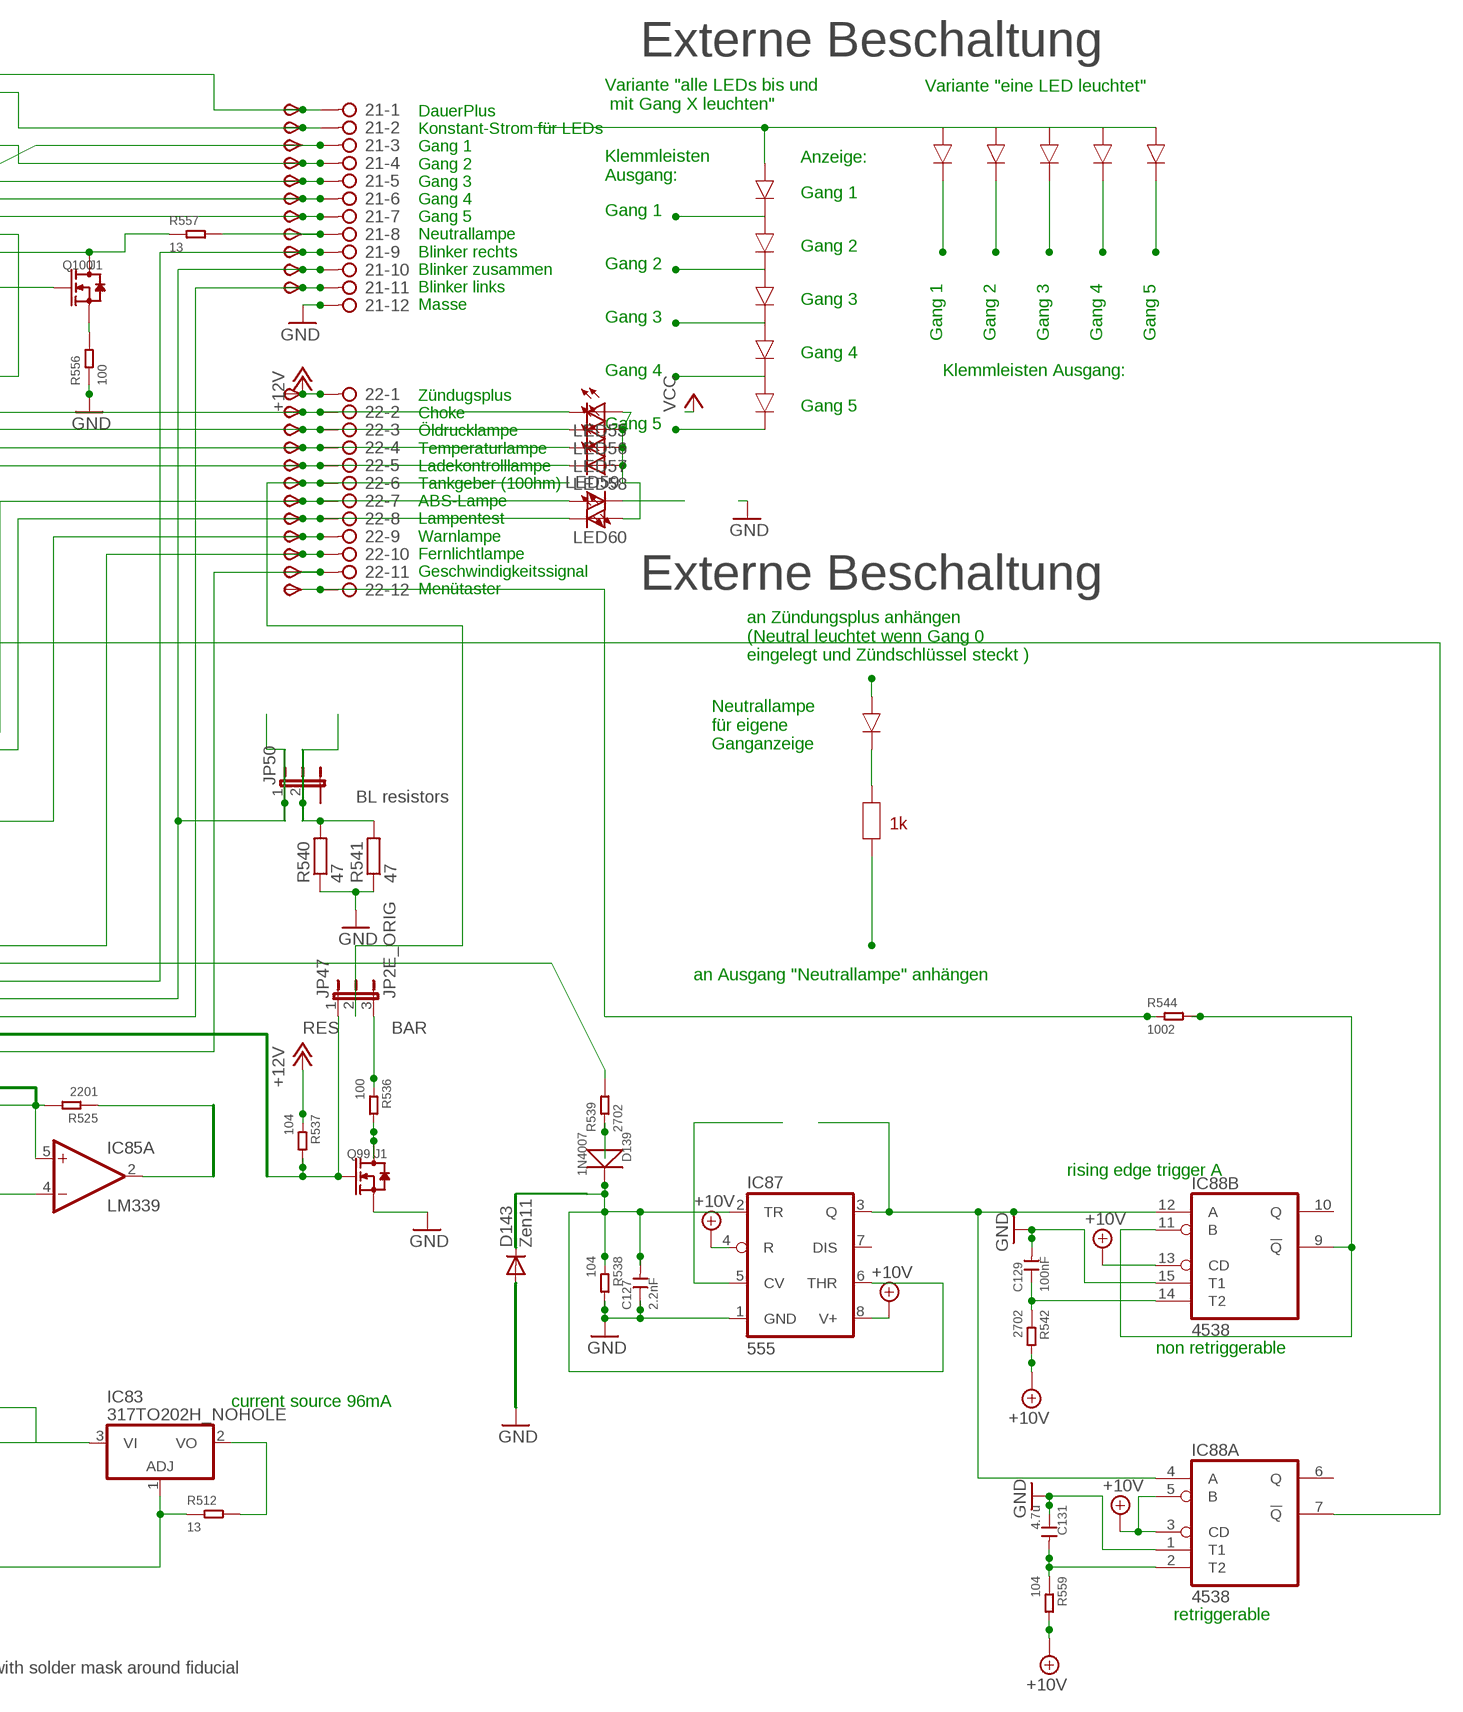
[diagram p23: schematic, sheet 13, part 2 of 2]
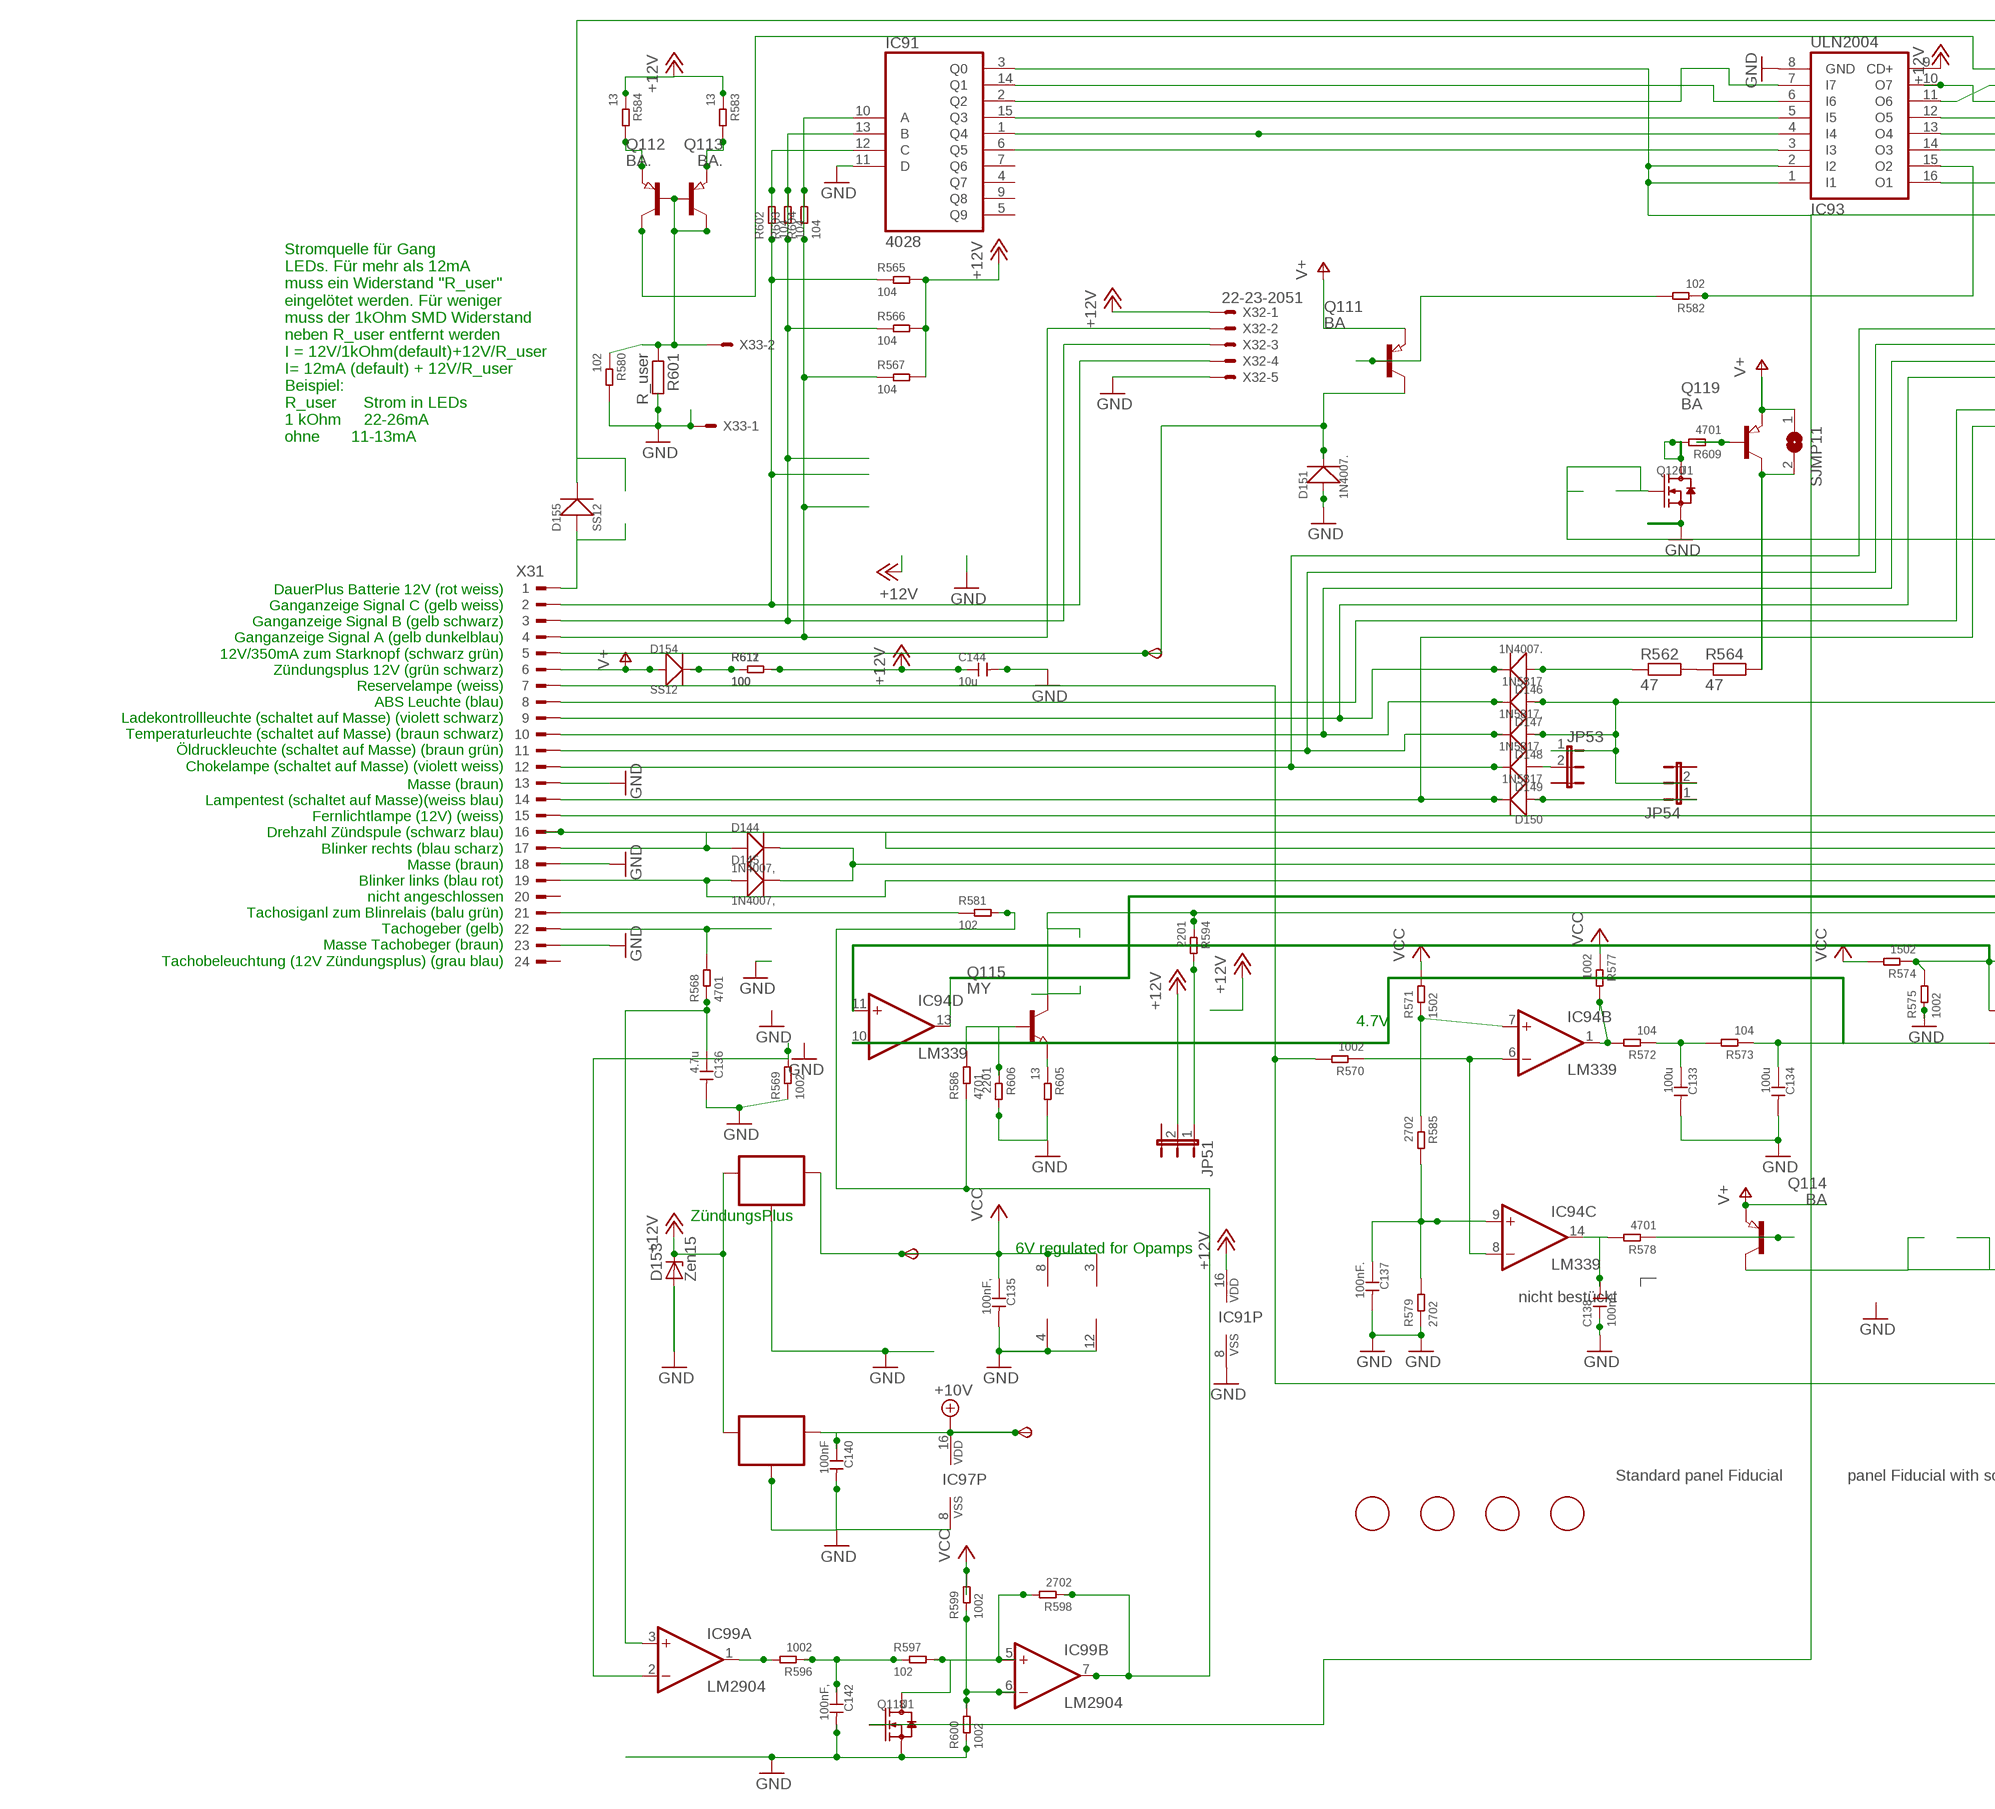
[diagram p24: schematic, sheet 14, part 1 of 2]
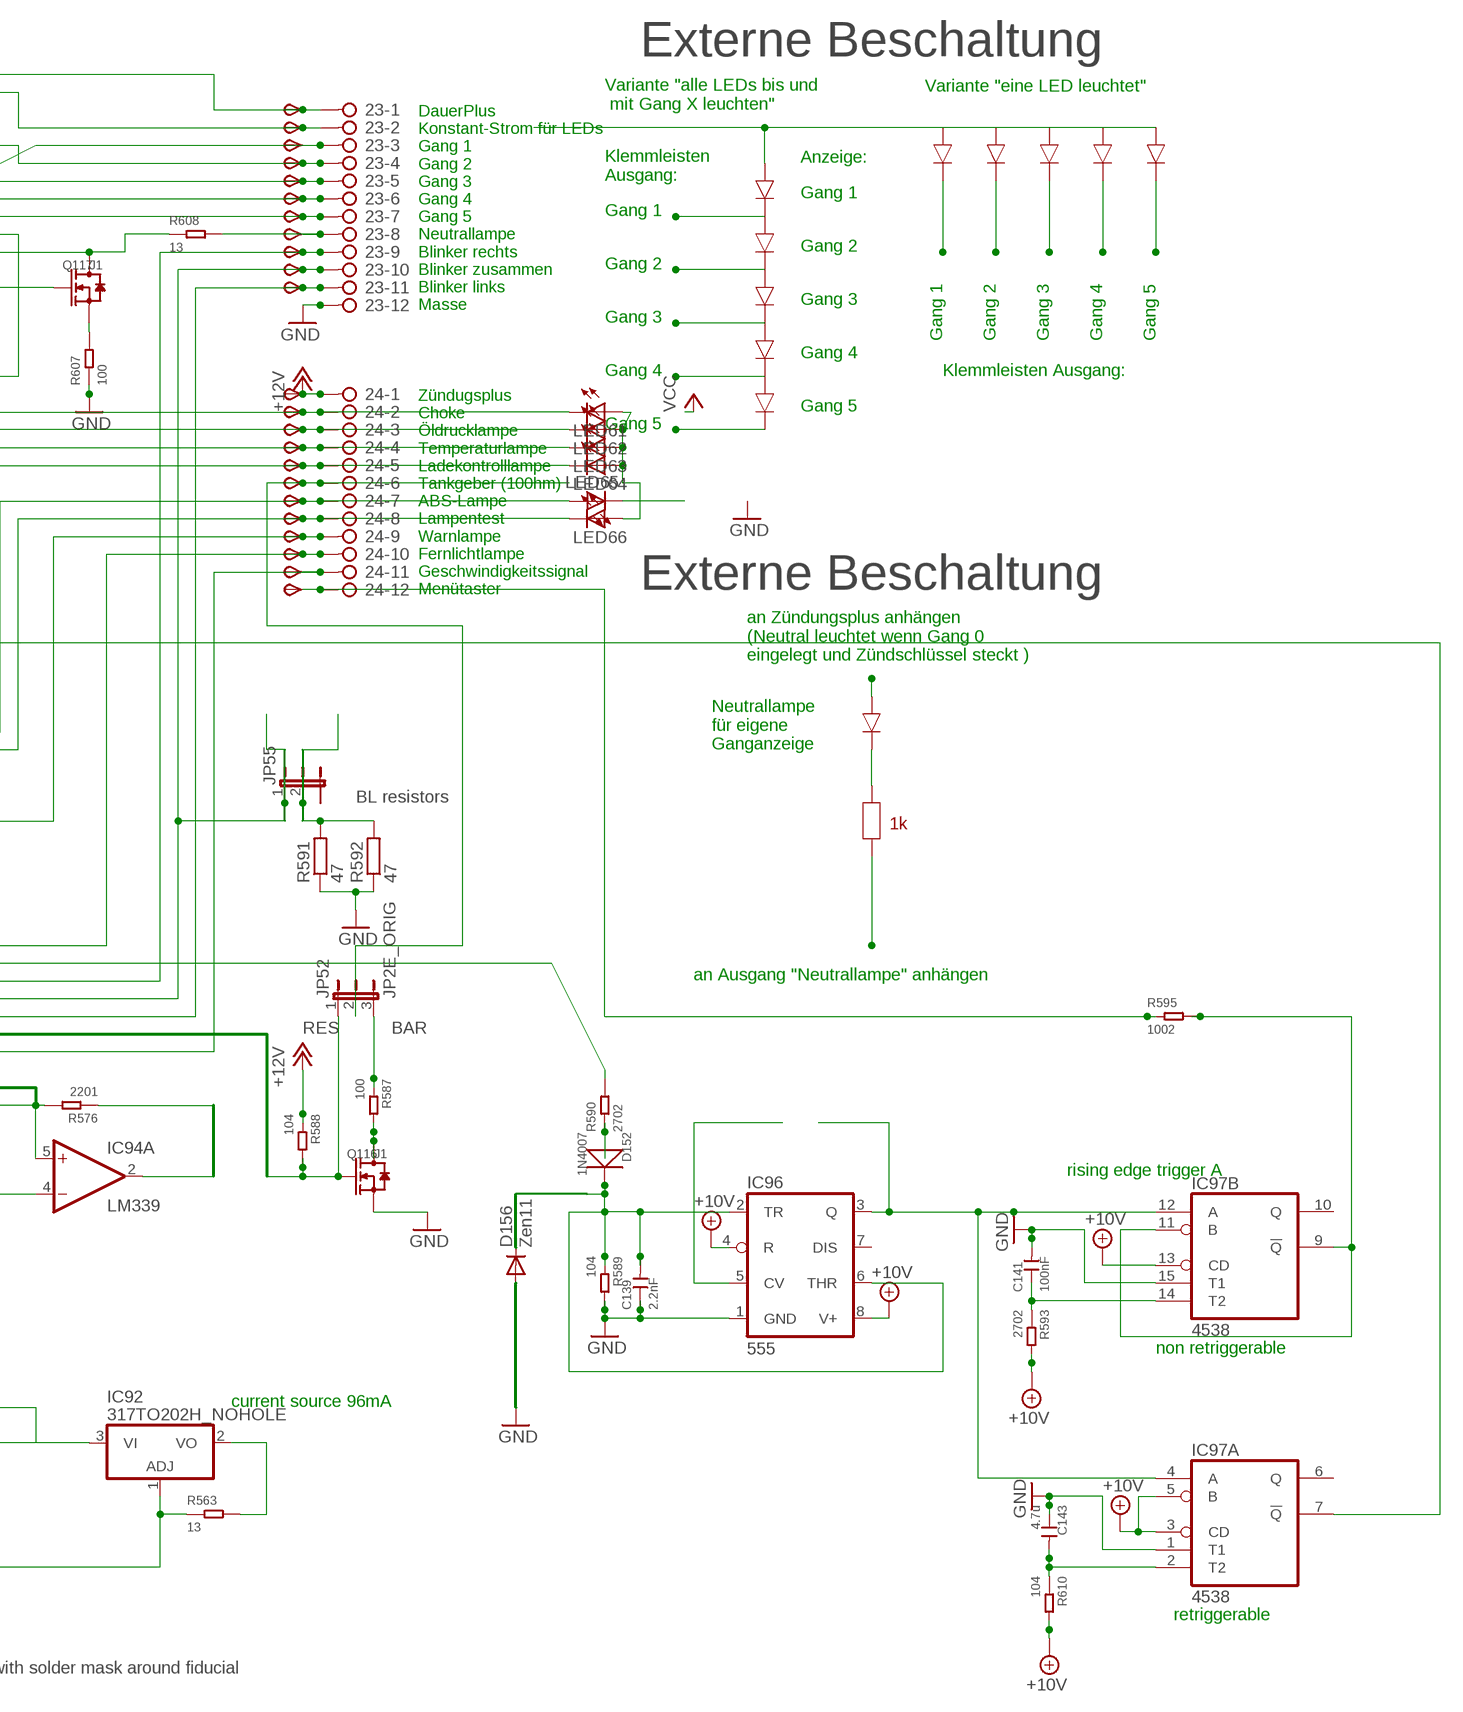
[diagram p25: schematic, sheet 14, part 2 of 2]

(export (version "E")
  (design (tool "Eeschema 10.0.6"))
  (components
    (comp (ref "6V6")
      (value "TPSB2.0")
      (footprint "eagle-import:B2.0")
      (libsource (lib "eagle-import") (part "TPSB2.0"))
    )
    (comp (ref "10V6")
      (value "TPSB2.0")
      (footprint "eagle-import:B2.0")
      (libsource (lib "eagle-import") (part "TPSB2.0"))
    )
    (comp (ref "13")
      (value "2081-1132")
      (footprint "eagle-import:12-PIN")
      (libsource (lib "eagle-import") (part "2081-1132"))
    )
    (comp (ref "14")
      (value "2081-1132")
      (footprint "eagle-import:12-PIN")
      (libsource (lib "eagle-import") (part "2081-1132"))
    )
    (comp (ref "C63")
      (value "100u")
      (footprint "eagle-import:C1206")
      (fields (field (name "MPN") "GRM31CR60J107ME39L"))
      (libsource (lib "eagle-import") (part "CERAMIC-100UF-6.3V-20%-X5R(1206)"))
    )
    (comp (ref "C64")
      (value "100u")
      (footprint "eagle-import:C1206")
      (fields (field (name "MPN") "GRM31CR60J107ME39L"))
      (libsource (lib "eagle-import") (part "CERAMIC-100UF-6.3V-20%-X5R(1206)"))
    )
    (comp (ref "C65")
      (value "100nF,")
      (footprint "eagle-import:C0805")
      (fields (field (name "MPN") "CC0805KRX7R9BB104"))
      (libsource (lib "eagle-import") (part "CERAMIC-100NF-50V-10%-X7R(0805)"))
    )
    (comp (ref "C66")
      (value "4.7u")
      (footprint "eagle-import:C0805")
      (fields (field (name "MPN") "CC0805KKX5R8BB475"))
      (libsource (lib "eagle-import") (part "CERAMIC-4.7UF-25V-10%-X5R(0805)"))
    )
    (comp (ref "C67")
      (value "100nF.")
      (footprint "eagle-import:C0805")
      (fields (field (name "MPN") "CC0805KRX7R9BB104"))
      (libsource (lib "eagle-import") (part "CERAMIC-100NF-50V-10%-X7R(0805)"))
    )
    (comp (ref "C68")
      (value "100nF.")
      (footprint "eagle-import:C0805")
      (fields (field (name "MPN") "CC0805KRX7R9BB104"))
      (libsource (lib "eagle-import") (part "CERAMIC-100NF-50V-10%-X7R(0805)"))
    )
    (comp (ref "C69")
      (value "2.2nF")
      (footprint "eagle-import:C0805")
      (fields (field (name "MPN") "CC0805KRX7R9BB104"))
      (libsource (lib "eagle-import") (part "CERAMIC-100NF-50V-10%-X7R(0805)"))
    )
    (comp (ref "C70")
      (value "100nF")
      (footprint "eagle-import:C0805")
      (fields (field (name "MPN") "CC0805KRX7R9BB104"))
      (libsource (lib "eagle-import") (part "CERAMIC-100NF-50V-10%-X7R(0805)"))
    )
    (comp (ref "C71")
      (value "100nF")
      (footprint "eagle-import:C0805")
      (fields (field (name "MPN") "CC0805KRX7R9BB104"))
      (libsource (lib "eagle-import") (part "CERAMIC-100NF-50V-10%-X7R(0805)"))
    )
    (comp (ref "C72")
      (value "100nF,")
      (footprint "eagle-import:C0805")
      (fields (field (name "MPN") "CC0805KRX7R9BB104"))
      (libsource (lib "eagle-import") (part "CERAMIC-100NF-50V-10%-X7R(0805)"))
    )
    (comp (ref "C73")
      (value "4.7u")
      (footprint "eagle-import:C0805")
      (fields (field (name "MPN") "CC0805KKX5R8BB475"))
      (libsource (lib "eagle-import") (part "CERAMIC-4.7UF-25V-10%-X5R(0805)"))
    )
    (comp (ref "C74")
      (value "10u")
      (footprint "eagle-import:C1206")
      (fields (field (name "MPN") "GRM31CR60J107ME39L"))
      (libsource (lib "eagle-import") (part "CERAMIC-100UF-6.3V-20%-X5R(1206)"))
    )
    (comp (ref "D14")
      (value "1N4007,")
      (footprint "eagle-import:DO-214AC")
      (fields (field (name "MPN") "1N4007"))
      (libsource (lib "eagle-import") (part "DIODE-GEN-PURPOSE-1KV-1A(DO-214AC)"))
    )
    (comp (ref "D28")
      (value "1N4007,")
      (footprint "eagle-import:DO-214AC")
      (fields (field (name "MPN") "1N4007"))
      (libsource (lib "eagle-import") (part "DIODE-GEN-PURPOSE-1KV-1A(DO-214AC)"))
    )
    (comp (ref "D42")
      (value "1N4007.")
      (footprint "eagle-import:DO-214AC")
      (fields (field (name "MPN") "1N4007"))
      (libsource (lib "eagle-import") (part "DIODE-GEN-PURPOSE-1KV-1A(DO-214AC)"))
    )
    (comp (ref "D56")
      (value "1N5817")
      (footprint "eagle-import:DO-214AC_SLIM")
      (libsource (lib "eagle-import") (part "DIODE-GEN-PURPOSE-1KV-1A(DO-214AC)DO-214AC/1206"))
    )
    (comp (ref "D70")
      (value "1N5817.")
      (footprint "eagle-import:DO-214AC_SLIM")
      (libsource (lib "eagle-import") (part "DIODE-GEN-PURPOSE-1KV-1A(DO-214AC)DO-214AC/1206"))
    )
    (comp (ref "D74")
      (value "1N5817.")
      (footprint "eagle-import:DO-214AC_SLIM")
      (libsource (lib "eagle-import") (part "DIODE-GEN-PURPOSE-1KV-1A(DO-214AC)DO-214AC/1206"))
    )
    (comp (ref "D75")
      (value "1N5817")
      (footprint "eagle-import:DO-214AC_SLIM")
      (libsource (lib "eagle-import") (part "DIODE-GEN-PURPOSE-1KV-1A(DO-214AC)DO-214AC/1206"))
    )
    (comp (ref "D76")
      (value "1N4007.")
      (footprint "eagle-import:DO-214AC")
      (fields (field (name "MPN") "1N4007"))
      (libsource (lib "eagle-import") (part "DIODE-GEN-PURPOSE-1KV-1A(DO-214AC)"))
    )
    (comp (ref "D77")
      (value "1N4007")
      (footprint "eagle-import:DO-214AC")
      (libsource (lib "eagle-import") (part "DIODE-GEN-PURPOSE-1KV-1A(DO-214AC)"))
    )
    (comp (ref "D78")
      (value "Zen15")
      (footprint "eagle-import:DO214AA")
      (libsource (lib "eagle-import") (part "SM6T"))
    )
    (comp (ref "D79")
      (value "SS12")
      (footprint "eagle-import:DO-214AC_SLIM")
      (libsource (lib "eagle-import") (part "DIODE-GEN-PURPOSE-1KV-1A(DO-214AC)DO-214AC/1206"))
    )
    (comp (ref "D80")
      (value "SS12")
      (footprint "eagle-import:DO-214AC_SLIM")
      (libsource (lib "eagle-import") (part "DIODE-GEN-PURPOSE-1KV-1A(DO-214AC)DO-214AC/1206"))
    )
    (comp (ref "D81")
      (value "Zen11")
      (footprint "eagle-import:SOD-123_MINI-SMA")
      (libsource (lib "eagle-import") (part "CGRM400-G1"))
    )
    (comp (ref "FID25")
      (value "FIDUCIAL")
      (footprint "eagle-import:FIDUCIAL_1MM")
      (libsource (lib "eagle-import") (part "FIDUCIAL"))
    )
    (comp (ref "FID26")
      (value "FIDUCIAL")
      (footprint "eagle-import:FIDUCIAL_1MM")
      (libsource (lib "eagle-import") (part "FIDUCIAL"))
    )
    (comp (ref "FID27")
      (value "FIDUCIAL")
      (footprint "eagle-import:FIDUCIAL_1MM")
      (libsource (lib "eagle-import") (part "FIDUCIAL"))
    )
    (comp (ref "FID28")
      (value "FIDUCIAL")
      (footprint "eagle-import:FIDUCIAL_1MM")
      (libsource (lib "eagle-import") (part "FIDUCIAL"))
    )
    (comp (ref "IC46")
      (value "4028")
      (footprint "eagle-import:SO16")
      (libsource (lib "eagle-import") (part "4028D"))
    )
    (comp (ref "IC47")
      (value "317TO202H_NOHOLE")
      (footprint "eagle-import:TO220H_NOHOLE")
      (libsource (lib "eagle-import") (part "317TO202H_NOHOLE"))
    )
    (comp (ref "IC48")
      (value "ULN2004")
      (footprint "eagle-import:SO16")
      (libsource (lib "eagle-import") (part "ULN2004AD"))
    )
    (comp (ref "IC49")
      (value "LM339")
      (footprint "eagle-import:SO14")
      (libsource (lib "eagle-import") (part "LM339D"))
    )
    (comp (ref "IC50")
      (value "78L06")
      (footprint "eagle-import:SOT89_ROUND")
      (libsource (lib "eagle-import") (part "78LXXSOT89_ROUND"))
    )
    (comp (ref "IC51")
      (value "555")
      (footprint "eagle-import:SO08")
      (libsource (lib "eagle-import") (part "555DNE"))
    )
    (comp (ref "IC52")
      (value "4538")
      (footprint "eagle-import:SO16")
      (libsource (lib "eagle-import") (part "4538D"))
    )
    (comp (ref "IC53")
      (value "78L10")
      (footprint "eagle-import:SOT89_ROUND")
      (libsource (lib "eagle-import") (part "78LXXSOT89_ROUND"))
    )
    (comp (ref "IC54")
      (value "LM2904")
      (footprint "eagle-import:SO08")
      (libsource (lib "eagle-import") (part "LM358D"))
    )
    (comp (ref "JP26")
      (value "JP2EJP2_SMALLPADS")
      (footprint "eagle-import:JP2_SMALLPADS")
      (libsource (lib "eagle-import") (part "JP2EJP2_SMALLPADS"))
    )
    (comp (ref "JP27")
      (value "JP2E_ORIG")
      (footprint "eagle-import:JP2_ORIG_SMALLPADS")
      (libsource (lib "eagle-import") (part "JP2E_ORIG"))
    )
    (comp (ref "JP28")
      (value "JP2EJP2_SMALLPADS")
      (footprint "eagle-import:JP2_SMALLPADS")
      (libsource (lib "eagle-import") (part "JP2EJP2_SMALLPADS"))
    )
    (comp (ref "JP29")
      (value "JP2EJP2_SMALLPADS")
      (footprint "eagle-import:JP2_SMALLPADS")
      (libsource (lib "eagle-import") (part "JP2EJP2_SMALLPADS"))
    )
    (comp (ref "JP30")
      (value "JP2EJP2_SMALLPADS")
      (footprint "eagle-import:JP2_SMALLPADS")
      (libsource (lib "eagle-import") (part "JP2EJP2_SMALLPADS"))
    )
    (comp (ref "LED31")
      (value "LEDLD260")
      (footprint "eagle-import:LD260")
      (libsource (lib "eagle-import") (part "LEDLD260"))
    )
    (comp (ref "LED32")
      (value "LEDLD260")
      (footprint "eagle-import:LD260")
      (libsource (lib "eagle-import") (part "LEDLD260"))
    )
    (comp (ref "LED33")
      (value "LEDLD260")
      (footprint "eagle-import:LD260")
      (libsource (lib "eagle-import") (part "LEDLD260"))
    )
    (comp (ref "LED34")
      (value "LEDLD260")
      (footprint "eagle-import:LD260")
      (libsource (lib "eagle-import") (part "LEDLD260"))
    )
    (comp (ref "LED35")
      (value "LEDLD260")
      (footprint "eagle-import:LD260")
      (libsource (lib "eagle-import") (part "LEDLD260"))
    )
    (comp (ref "LED36")
      (value "LEDLD260")
      (footprint "eagle-import:LD260")
      (libsource (lib "eagle-import") (part "LEDLD260"))
    )
    (comp (ref "Q54")
      (value "BA")
      (footprint "eagle-import:SOT89")
      (libsource (lib "eagle-import") (part "PNP-TRANSISTOR_SOT89"))
    )
    (comp (ref "Q55")
      (value "BA.")
      (footprint "eagle-import:SOT89")
      (libsource (lib "eagle-import") (part "PNP-TRANSISTOR_SOT89"))
    )
    (comp (ref "Q56")
      (value "BA.")
      (footprint "eagle-import:SOT89")
      (libsource (lib "eagle-import") (part "PNP-TRANSISTOR_SOT89"))
    )
    (comp (ref "Q57")
      (value "BA")
      (footprint "eagle-import:SOT89")
      (libsource (lib "eagle-import") (part "PNP-TRANSISTOR_SOT89"))
    )
    (comp (ref "Q58")
      (value "MY")
      (footprint "eagle-import:SOT89")
      (libsource (lib "eagle-import") (part "NPN-TRANSISTOR_SOT89"))
    )
    (comp (ref "Q59")
      (value "J1")
      (footprint "eagle-import:SOT-23")
      (fields (field (name "MPN") "BSS138W-7-F"))
      (libsource (lib "eagle-import") (part "SMD-MOSFET-N-CH-50V-200MA-BSS138W-7-F(SOT-23)"))
    )
    (comp (ref "Q60")
      (value "J1")
      (footprint "eagle-import:SOT-23")
      (fields (field (name "MPN") "BSS138W-7-F"))
      (libsource (lib "eagle-import") (part "SMD-MOSFET-N-CH-50V-200MA-BSS138W-7-F(SOT-23)"))
    )
    (comp (ref "Q61")
      (value "J1")
      (footprint "eagle-import:SOT-23")
      (fields (field (name "MPN") "BSS138W-7-F"))
      (libsource (lib "eagle-import") (part "SMD-MOSFET-N-CH-50V-200MA-BSS138W-7-F(SOT-23)"))
    )
    (comp (ref "Q62")
      (value "BA")
      (footprint "eagle-import:SOT89")
      (libsource (lib "eagle-import") (part "PNP-TRANSISTOR_SOT89"))
    )
    (comp (ref "Q63")
      (value "J1")
      (footprint "eagle-import:SOT-23")
      (fields (field (name "MPN") "BSS138W-7-F"))
      (libsource (lib "eagle-import") (part "SMD-MOSFET-N-CH-50V-200MA-BSS138W-7-F(SOT-23)"))
    )
    (comp (ref "R31")
      (value "47")
      (footprint "eagle-import:V235_17_1MM")
      (libsource (lib "eagle-import") (part "R-EU_V235/17_1MM"))
    )
    (comp (ref "R33")
      (value "13")
      (footprint "eagle-import:R1206")
      (fields (field (name "MPN") "RC1206JR-0713RL"))
      (libsource (lib "eagle-import") (part "SMD-RES-13R-5%-1/4W(1206)"))
    )
    (comp (ref "R34")
      (value "47")
      (footprint "eagle-import:V235_17_1MM")
      (libsource (lib "eagle-import") (part "R-EU_V235/17_1MM"))
    )
    (comp (ref "R43")
      (value "104")
      (footprint "eagle-import:R0805")
      (fields (field (name "MPN") "RC0805FR-0710KL"))
      (libsource (lib "eagle-import") (part "SMD-RES-10K-1%-1/8W(0805)"))
    )
    (comp (ref "R86")
      (value "104")
      (footprint "eagle-import:R0805")
      (fields (field (name "MPN") "RC0805FR-0710KL"))
      (libsource (lib "eagle-import") (part "SMD-RES-10K-1%-1/8W(0805)"))
    )
    (comp (ref "R88")
      (value "104")
      (footprint "eagle-import:R0805")
      (fields (field (name "MPN") "RC0805FR-0710KL"))
      (libsource (lib "eagle-import") (part "SMD-RES-10K-1%-1/8W(0805)"))
    )
    (comp (ref "R89")
      (value "4701")
      (footprint "eagle-import:R0805")
      (fields (field (name "MPN") "RC0805JR-074K7L"))
      (libsource (lib "eagle-import") (part "SMD-RES-4.7K-5%-1/8W(0805)"))
    )
    (comp (ref "R98")
      (value "1002")
      (footprint "eagle-import:R0805")
      (fields (field (name "MPN") "RC0805FR-0710KL"))
      (libsource (lib "eagle-import") (part "SMD-RES-10K-1%-1/8W(0805)"))
    )
    (comp (ref "R104")
      (value "1002")
      (footprint "eagle-import:R0805")
      (fields (field (name "MPN") "RC0805FR-0710KL"))
      (libsource (lib "eagle-import") (part "SMD-RES-10K-1%-1/8W(0805)"))
    )
    (comp (ref "R142")
      (value "1502")
      (footprint "eagle-import:R0805")
      (fields (field (name "MPN") "RC0805FR-0710KL"))
      (libsource (lib "eagle-import") (part "SMD-RES-10K-1%-1/8W(0805)"))
    )
    (comp (ref "R143")
      (value "104")
      (footprint "eagle-import:R0805")
      (fields (field (name "MPN") "RC0805FR-0710KL"))
      (libsource (lib "eagle-import") (part "SMD-RES-10K-1%-1/8W(0805)"))
    )
    (comp (ref "R144")
      (value "104")
      (footprint "eagle-import:R0805")
      (fields (field (name "MPN") "RC0805FR-0710KL"))
      (libsource (lib "eagle-import") (part "SMD-RES-10K-1%-1/8W(0805)"))
    )
    (comp (ref "R185")
      (value "1502")
      (footprint "eagle-import:R0805")
      (fields (field (name "MPN") "RC0805FR-0710KL"))
      (libsource (lib "eagle-import") (part "SMD-RES-10K-1%-1/8W(0805)"))
    )
    (comp (ref "R187")
      (value "1002")
      (footprint "eagle-import:R0805")
      (fields (field (name "MPN") "RC0805FR-0710KL"))
      (libsource (lib "eagle-import") (part "SMD-RES-10K-1%-1/8W(0805)"))
    )
    (comp (ref "R188")
      (value "2201")
      (footprint "eagle-import:R0805")
      (fields (field (name "MPN") "RC0805JR-072K2L"))
      (libsource (lib "eagle-import") (part "SMD-RES-2.2K-5%-1/8W(0805)"))
    )
    (comp (ref "R197")
      (value "1002")
      (footprint "eagle-import:R0805")
      (fields (field (name "MPN") "RC0805FR-0710KL"))
      (libsource (lib "eagle-import") (part "SMD-RES-10K-1%-1/8W(0805)"))
    )
    (comp (ref "R240")
      (value "4701")
      (footprint "eagle-import:R0805")
      (fields (field (name "MPN") "RC0805JR-074K7L"))
      (libsource (lib "eagle-import") (part "SMD-RES-4.7K-5%-1/8W(0805)"))
    )
    (comp (ref "R242")
      (value "2702")
      (footprint "eagle-import:R0805")
      (fields (field (name "MPN") "RC0805JR-074K7L"))
      (libsource (lib "eagle-import") (part "SMD-RES-4.7K-5%-1/8W(0805)"))
    )
    (comp (ref "R243")
      (value "102")
      (footprint "eagle-import:R0805")
      (fields (field (name "MPN") "RC0805JR-071KL"))
      (libsource (lib "eagle-import") (part "SMD-RES-1K-5%-1/8W(0805)"))
    )
    (comp (ref "R252")
      (value "102")
      (footprint "eagle-import:R0805")
      (fields (field (name "MPN") "RC0805JR-07220RL"))
      (libsource (lib "eagle-import") (part "SMD-RES-220R-5%-1/8W(0805)"))
    )
    (comp (ref "R295")
      (value "102")
      (footprint "eagle-import:R0805")
      (fields (field (name "MPN") "RC0805JR-071KL"))
      (libsource (lib "eagle-import") (part "SMD-RES-1K-5%-1/8W(0805)"))
    )
    (comp (ref "R297")
      (value "13")
      (footprint "eagle-import:R1206")
      (fields (field (name "MPN") "RC1206JR-0713RL"))
      (libsource (lib "eagle-import") (part "SMD-RES-13R-5%-1/4W(1206)"))
    )
    (comp (ref "R298")
      (value "13")
      (footprint "eagle-import:R1206")
      (fields (field (name "MPN") "RC1206JR-0713RL"))
      (libsource (lib "eagle-import") (part "SMD-RES-13R-5%-1/4W(1206)"))
    )
    (comp (ref "R307")
      (value "2702")
      (footprint "eagle-import:R0805")
      (fields (field (name "MPN") "RC0805JR-074K7L"))
      (libsource (lib "eagle-import") (part "SMD-RES-4.7K-5%-1/8W(0805)"))
    )
    (comp (ref "R331")
      (value "4701")
      (footprint "eagle-import:R0805")
      (fields (field (name "MPN") "RC0805JR-074K7L"))
      (libsource (lib "eagle-import") (part "SMD-RES-4.7K-5%-1/8W(0805)"))
    )
    (comp (ref "R332")
      (value "100")
      (footprint "eagle-import:R0805")
      (fields (field (name "MPN") "RC0805JR-072K2L"))
      (libsource (lib "eagle-import") (part "SMD-RES-2.2K-5%-1/8W(0805)"))
    )
    (comp (ref "R333")
      (value "104")
      (footprint "eagle-import:R0805")
      (fields (field (name "MPN") "RC0805FR-0710KL"))
      (libsource (lib "eagle-import") (part "SMD-RES-10K-1%-1/8W(0805)"))
    )
    (comp (ref "R334")
      (value "104")
      (footprint "eagle-import:R0805")
      (fields (field (name "MPN") "RC0805FR-0710KL"))
      (libsource (lib "eagle-import") (part "SMD-RES-10K-1%-1/8W(0805)"))
    )
    (comp (ref "R335")
      (value "2702")
      (footprint "eagle-import:R0805")
      (fields (field (name "MPN") "RC0805FR-0710KL"))
      (libsource (lib "eagle-import") (part "SMD-RES-10K-1%-1/8W(0805)"))
    )
    (comp (ref "R336")
      (value "47")
      (footprint "eagle-import:V235_17_1MM")
      (libsource (lib "eagle-import") (part "R-EU_V235/17_1MM"))
    )
    (comp (ref "R337")
      (value "47")
      (footprint "eagle-import:V235_17_1MM")
      (libsource (lib "eagle-import") (part "R-EU_V235/17_1MM"))
    )
    (comp (ref "R338")
      (value "2702")
      (footprint "eagle-import:R0805")
      (fields (field (name "MPN") "RC0805JR-074K7L"))
      (libsource (lib "eagle-import") (part "SMD-RES-4.7K-5%-1/8W(0805)"))
    )
    (comp (ref "R339")
      (value "2201")
      (footprint "eagle-import:R0805")
      (fields (field (name "MPN") "RC0805JR-072K2L"))
      (libsource (lib "eagle-import") (part "SMD-RES-2.2K-5%-1/8W(0805)"))
    )
    (comp (ref "R340")
      (value "1002")
      (footprint "eagle-import:R0805")
      (fields (field (name "MPN") "RC0805JR-074K7L"))
      (libsource (lib "eagle-import") (part "SMD-RES-4.7K-5%-1/8W(0805)"))
    )
    (comp (ref "R341")
      (value "1002")
      (footprint "eagle-import:R0805")
      (fields (field (name "MPN") "RC0805FR-0710KL"))
      (libsource (lib "eagle-import") (part "SMD-RES-10K-1%-1/8W(0805)"))
    )
    (comp (ref "R342")
      (value "102")
      (footprint "eagle-import:R0805")
      (fields (field (name "MPN") "RC0805JR-071KL"))
      (libsource (lib "eagle-import") (part "SMD-RES-1K-5%-1/8W(0805)"))
    )
    (comp (ref "R343")
      (value "2702")
      (footprint "eagle-import:R0805")
      (fields (field (name "MPN") "RC0805JR-074K7L"))
      (libsource (lib "eagle-import") (part "SMD-RES-4.7K-5%-1/8W(0805)"))
    )
    (comp (ref "R344")
      (value "1002")
      (footprint "eagle-import:R0805")
      (fields (field (name "MPN") "RC0805JR-071KL"))
      (libsource (lib "eagle-import") (part "SMD-RES-1K-5%-1/8W(0805)"))
    )
    (comp (ref "R345")
      (value "1002")
      (footprint "eagle-import:R0805")
      (fields (field (name "MPN") "RC0805JR-071KL"))
      (libsource (lib "eagle-import") (part "SMD-RES-1K-5%-1/8W(0805)"))
    )
    (comp (ref "R346")
      (value "R_user")
      (footprint "eagle-import:R0805")
      (libsource (lib "eagle-import") (part "R-EU_R0805"))
    )
    (comp (ref "R347")
      (value "104")
      (footprint "eagle-import:R0805")
      (fields (field (name "MPN") "RC0805FR-0710KL"))
      (libsource (lib "eagle-import") (part "SMD-RES-10K-1%-1/8W(0805)"))
    )
    (comp (ref "R348")
      (value "104")
      (footprint "eagle-import:R0805")
      (fields (field (name "MPN") "RC0805FR-0710KL"))
      (libsource (lib "eagle-import") (part "SMD-RES-10K-1%-1/8W(0805)"))
    )
    (comp (ref "R349")
      (value "104")
      (footprint "eagle-import:R0805")
      (fields (field (name "MPN") "RC0805FR-0710KL"))
      (libsource (lib "eagle-import") (part "SMD-RES-10K-1%-1/8W(0805)"))
    )
    (comp (ref "R350")
      (value "13")
      (footprint "eagle-import:R1206")
      (fields (field (name "MPN") "RC1206JR-0713RL"))
      (libsource (lib "eagle-import") (part "SMD-RES-13R-5%-1/4W(1206)"))
    )
    (comp (ref "R351")
      (value "2201")
      (footprint "eagle-import:R0805")
      (fields (field (name "MPN") "RC0805JR-071KL"))
      (libsource (lib "eagle-import") (part "SMD-RES-1K-5%-1/8W(0805)"))
    )
    (comp (ref "R352")
      (value "100")
      (footprint "eagle-import:R0805")
      (fields (field (name "MPN") "RC0805JR-07220RL"))
      (libsource (lib "eagle-import") (part "SMD-RES-220R-5%-1/8W(0805)"))
    )
    (comp (ref "R353")
      (value "13")
      (footprint "eagle-import:R1206")
      (fields (field (name "MPN") "RC1206JR-0713RL"))
      (libsource (lib "eagle-import") (part "SMD-RES-13R-5%-1/4W(1206)"))
    )
    (comp (ref "R354")
      (value "4701")
      (footprint "eagle-import:R0805")
      (fields (field (name "MPN") "RC0805JR-074K7L"))
      (libsource (lib "eagle-import") (part "SMD-RES-4.7K-5%-1/8W(0805)"))
    )
    (comp (ref "R355")
      (value "104")
      (footprint "eagle-import:R0805")
      (fields (field (name "MPN") "RC0805JR-074K7L"))
      (libsource (lib "eagle-import") (part "SMD-RES-4.7K-5%-1/8W(0805)"))
    )
    (comp (ref "R356")
      (value "100")
      (footprint "eagle-import:R0805")
      (fields (field (name "MPN") "RC0805JR-072K2L"))
      (libsource (lib "eagle-import") (part "SMD-RES-2.2K-5%-1/8W(0805)"))
    )
    (comp (ref "R357")
      (value "100")
      (footprint "eagle-import:R0805")
      (fields (field (name "MPN") "RC0805JR-072K2L"))
      (libsource (lib "eagle-import") (part "SMD-RES-2.2K-5%-1/8W(0805)"))
    )
    (comp (ref "SJMP6")
      (value "SJ")
      (footprint "eagle-import:SJ")
      (libsource (lib "eagle-import") (part "SJ"))
    )
    (comp (ref "START6")
      (value "TPSB2.0")
      (footprint "eagle-import:B2.0")
      (libsource (lib "eagle-import") (part "TPSB2.0"))
    )
    (comp (ref "TP139")
      (value "TPSB2.0")
      (footprint "eagle-import:B2.0")
      (libsource (lib "eagle-import") (part "TPSB2.0"))
    )
    (comp (ref "TP140")
      (value "TPSB2.0")
      (footprint "eagle-import:B2.0")
      (libsource (lib "eagle-import") (part "TPSB2.0"))
    )
    (comp (ref "TP141")
      (value "TPSB2.0")
      (footprint "eagle-import:B2.0")
      (libsource (lib "eagle-import") (part "TPSB2.0"))
    )
    (comp (ref "TP142")
      (value "TPSB2.0")
      (footprint "eagle-import:B2.0")
      (libsource (lib "eagle-import") (part "TPSB2.0"))
    )
    (comp (ref "TP143")
      (value "TPSB2.0")
      (footprint "eagle-import:B2.0")
      (libsource (lib "eagle-import") (part "TPSB2.0"))
    )
    (comp (ref "TP144")
      (value "TPSB2.0")
      (footprint "eagle-import:B2.0")
      (libsource (lib "eagle-import") (part "TPSB2.0"))
    )
    (comp (ref "TP145")
      (value "TPSB2.0")
      (footprint "eagle-import:B2.0")
      (libsource (lib "eagle-import") (part "TPSB2.0"))
    )
    (comp (ref "TP146")
      (value "TPSB2.0")
      (footprint "eagle-import:B2.0")
      (libsource (lib "eagle-import") (part "TPSB2.0"))
    )
    (comp (ref "TP147")
      (value "TPSB2.0")
      (footprint "eagle-import:B2.0")
      (libsource (lib "eagle-import") (part "TPSB2.0"))
    )
    (comp (ref "TP148")
      (value "TPSB2.0")
      (footprint "eagle-import:B2.0")
      (libsource (lib "eagle-import") (part "TPSB2.0"))
    )
    (comp (ref "TP149")
      (value "TPSB2.0")
      (footprint "eagle-import:B2.0")
      (libsource (lib "eagle-import") (part "TPSB2.0"))
    )
    (comp (ref "TP150")
      (value "TPSB2.0")
      (footprint "eagle-import:B2.0")
      (libsource (lib "eagle-import") (part "TPSB2.0"))
    )
    (comp (ref "TP151")
      (value "TPSB2.0")
      (footprint "eagle-import:B2.0")
      (libsource (lib "eagle-import") (part "TPSB2.0"))
    )
    (comp (ref "TP152")
      (value "TPSB2.0")
      (footprint "eagle-import:B2.0")
      (libsource (lib "eagle-import") (part "TPSB2.0"))
    )
    (comp (ref "TP153")
      (value "TPSB2.0")
      (footprint "eagle-import:B2.0")
      (libsource (lib "eagle-import") (part "TPSB2.0"))
    )
    (comp (ref "TP154")
      (value "TPSB2.0")
      (footprint "eagle-import:B2.0")
      (libsource (lib "eagle-import") (part "TPSB2.0"))
    )
    (comp (ref "TP155")
      (value "TPSB2.0")
      (footprint "eagle-import:B2.0")
      (libsource (lib "eagle-import") (part "TPSB2.0"))
    )
    (comp (ref "TP156")
      (value "TPSB2.0")
      (footprint "eagle-import:B2.0")
      (libsource (lib "eagle-import") (part "TPSB2.0"))
    )
    (comp (ref "TP157")
      (value "TPSB1,27")
      (footprint "eagle-import:B1,27")
      (libsource (lib "eagle-import") (part "TPSB1,27"))
    )
    (comp (ref "TP158")
      (value "TPSB2.0")
      (footprint "eagle-import:B2.0")
      (libsource (lib "eagle-import") (part "TPSB2.0"))
    )
    (comp (ref "TP159")
      (value "TPSB2.0")
      (footprint "eagle-import:B2.0")
      (libsource (lib "eagle-import") (part "TPSB2.0"))
    )
    (comp (ref "TP160")
      (value "TPSB2.0")
      (footprint "eagle-import:B2.0")
      (libsource (lib "eagle-import") (part "TPSB2.0"))
    )
    (comp (ref "TP161")
      (value "TPSB2.0")
      (footprint "eagle-import:B2.0")
      (libsource (lib "eagle-import") (part "TPSB2.0"))
    )
    (comp (ref "U$25")
      (value "STC")
      (footprint "eagle-import:STENCIL_HOLE")
      (libsource (lib "eagle-import") (part "STC"))
    )
    (comp (ref "U$30")
      (value "STC")
      (footprint "eagle-import:STENCIL_HOLE")
      (libsource (lib "eagle-import") (part "STC"))
    )
    (comp (ref "U$33")
      (value "STC")
      (footprint "eagle-import:STENCIL_HOLE")
      (libsource (lib "eagle-import") (part "STC"))
    )
    (comp (ref "U$34")
      (value "STC")
      (footprint "eagle-import:STENCIL_HOLE")
      (libsource (lib "eagle-import") (part "STC"))
    )
    (comp (ref "X16")
      (value "CON_BMWV2")
      (footprint "eagle-import:24-PIN_V2")
      (libsource (lib "eagle-import") (part "CON_BMWV2"))
    )
    (comp (ref "X17")
      (value "22-23-2051")
      (footprint "eagle-import:22-23-2051")
      (fields (field (name "MF") "MOLEX"))
      (libsource (lib "eagle-import") (part "22-23-2051"))
    )
    (comp (ref "X18")
      (value "22-23-2021")
      (footprint "eagle-import:22-23-2021")
      (fields (field (name "MF") "MOLEX"))
      (libsource (lib "eagle-import") (part "22-23-2021"))
    )
    (comp (ref "FID1B1")
      (value "FIDUCIALFIDUCIAL_1MM_WITH_SOLDERMASK")
      (footprint "eagle-import:FIDUCIAL_1MM_WITH_SOLDERMASK")
      (libsource (lib "eagle-import") (part "FIDUCIALFIDUCIAL_1MM_WITH_SOLDERMASK"))
    )
    (comp (ref "FID2B1")
      (value "FIDUCIALFIDUCIAL_1MM_WITH_SOLDERMASK")
      (footprint "eagle-import:FIDUCIAL_1MM_WITH_SOLDERMASK")
      (libsource (lib "eagle-import") (part "FIDUCIALFIDUCIAL_1MM_WITH_SOLDERMASK"))
    )
    (comp (ref "FID23")
      (value "FIDUCIAL")
      (footprint "eagle-import:FIDUCIAL_1MM")
      (libsource (lib "eagle-import") (part "FIDUCIAL"))
    )
    (comp (ref "FID24")
      (value "FIDUCIAL")
      (footprint "eagle-import:FIDUCIAL_1MM")
      (libsource (lib "eagle-import") (part "FIDUCIAL"))
    )
    (comp (ref "6V8")
      (value "TPSB2.0")
      (footprint "eagle-import:B2.0")
      (libsource (lib "eagle-import") (part "TPSB2.0"))
    )
    (comp (ref "10V8")
      (value "TPSB2.0")
      (footprint "eagle-import:B2.0")
      (libsource (lib "eagle-import") (part "TPSB2.0"))
    )
    (comp (ref "17")
      (value "2081-1132")
      (footprint "eagle-import:12-PIN")
      (libsource (lib "eagle-import") (part "2081-1132"))
    )
    (comp (ref "18")
      (value "2081-1132")
      (footprint "eagle-import:12-PIN")
      (libsource (lib "eagle-import") (part "2081-1132"))
    )
    (comp (ref "C87")
      (value "100u")
      (footprint "eagle-import:C1206")
      (fields (field (name "MPN") "GRM31CR60J107ME39L"))
      (libsource (lib "eagle-import") (part "CERAMIC-100UF-6.3V-20%-X5R(1206)"))
    )
    (comp (ref "C88")
      (value "100u")
      (footprint "eagle-import:C1206")
      (fields (field (name "MPN") "GRM31CR60J107ME39L"))
      (libsource (lib "eagle-import") (part "CERAMIC-100UF-6.3V-20%-X5R(1206)"))
    )
    (comp (ref "C89")
      (value "100nF,")
      (footprint "eagle-import:C0805")
      (fields (field (name "MPN") "CC0805KRX7R9BB104"))
      (libsource (lib "eagle-import") (part "CERAMIC-100NF-50V-10%-X7R(0805)"))
    )
    (comp (ref "C90")
      (value "4.7u")
      (footprint "eagle-import:C0805")
      (fields (field (name "MPN") "CC0805KKX5R8BB475"))
      (libsource (lib "eagle-import") (part "CERAMIC-4.7UF-25V-10%-X5R(0805)"))
    )
    (comp (ref "C91")
      (value "100nF.")
      (footprint "eagle-import:C0805")
      (fields (field (name "MPN") "CC0805KRX7R9BB104"))
      (libsource (lib "eagle-import") (part "CERAMIC-100NF-50V-10%-X7R(0805)"))
    )
    (comp (ref "C92")
      (value "100nF.")
      (footprint "eagle-import:C0805")
      (fields (field (name "MPN") "CC0805KRX7R9BB104"))
      (libsource (lib "eagle-import") (part "CERAMIC-100NF-50V-10%-X7R(0805)"))
    )
    (comp (ref "C93")
      (value "2.2nF")
      (footprint "eagle-import:C0805")
      (fields (field (name "MPN") "CC0805KRX7R9BB104"))
      (libsource (lib "eagle-import") (part "CERAMIC-100NF-50V-10%-X7R(0805)"))
    )
    (comp (ref "C94")
      (value "100nF")
      (footprint "eagle-import:C0805")
      (fields (field (name "MPN") "CC0805KRX7R9BB104"))
      (libsource (lib "eagle-import") (part "CERAMIC-100NF-50V-10%-X7R(0805)"))
    )
    (comp (ref "C95")
      (value "100nF")
      (footprint "eagle-import:C0805")
      (fields (field (name "MPN") "CC0805KRX7R9BB104"))
      (libsource (lib "eagle-import") (part "CERAMIC-100NF-50V-10%-X7R(0805)"))
    )
    (comp (ref "C96")
      (value "100nF,")
      (footprint "eagle-import:C0805")
      (fields (field (name "MPN") "CC0805KRX7R9BB104"))
      (libsource (lib "eagle-import") (part "CERAMIC-100NF-50V-10%-X7R(0805)"))
    )
    (comp (ref "C97")
      (value "4.7u")
      (footprint "eagle-import:C0805")
      (fields (field (name "MPN") "CC0805KKX5R8BB475"))
      (libsource (lib "eagle-import") (part "CERAMIC-4.7UF-25V-10%-X5R(0805)"))
    )
    (comp (ref "C98")
      (value "10u")
      (footprint "eagle-import:C1206")
      (fields (field (name "MPN") "GRM31CR60J107ME39L"))
      (libsource (lib "eagle-import") (part "CERAMIC-100UF-6.3V-20%-X5R(1206)"))
    )
    (comp (ref "D95")
      (value "1N4007,")
      (footprint "eagle-import:DO-214AC")
      (fields (field (name "MPN") "1N4007"))
      (libsource (lib "eagle-import") (part "DIODE-GEN-PURPOSE-1KV-1A(DO-214AC)"))
    )
    (comp (ref "D96")
      (value "1N4007,")
      (footprint "eagle-import:DO-214AC")
      (fields (field (name "MPN") "1N4007"))
      (libsource (lib "eagle-import") (part "DIODE-GEN-PURPOSE-1KV-1A(DO-214AC)"))
    )
    (comp (ref "D97")
      (value "1N4007.")
      (footprint "eagle-import:DO-214AC")
      (fields (field (name "MPN") "1N4007"))
      (libsource (lib "eagle-import") (part "DIODE-GEN-PURPOSE-1KV-1A(DO-214AC)"))
    )
    (comp (ref "D98")
      (value "1N5817")
      (footprint "eagle-import:DO-214AC_SLIM")
      (libsource (lib "eagle-import") (part "DIODE-GEN-PURPOSE-1KV-1A(DO-214AC)DO-214AC/1206"))
    )
    (comp (ref "D99")
      (value "1N5817.")
      (footprint "eagle-import:DO-214AC_SLIM")
      (libsource (lib "eagle-import") (part "DIODE-GEN-PURPOSE-1KV-1A(DO-214AC)DO-214AC/1206"))
    )
    (comp (ref "D100")
      (value "1N5817.")
      (footprint "eagle-import:DO-214AC_SLIM")
      (libsource (lib "eagle-import") (part "DIODE-GEN-PURPOSE-1KV-1A(DO-214AC)DO-214AC/1206"))
    )
    (comp (ref "D104")
      (value "1N5817")
      (footprint "eagle-import:DO-214AC_SLIM")
      (libsource (lib "eagle-import") (part "DIODE-GEN-PURPOSE-1KV-1A(DO-214AC)DO-214AC/1206"))
    )
    (comp (ref "D111")
      (value "1N4007.")
      (footprint "eagle-import:DO-214AC")
      (fields (field (name "MPN") "1N4007"))
      (libsource (lib "eagle-import") (part "DIODE-GEN-PURPOSE-1KV-1A(DO-214AC)"))
    )
    (comp (ref "D113")
      (value "1N4007")
      (footprint "eagle-import:DO-214AC")
      (libsource (lib "eagle-import") (part "DIODE-GEN-PURPOSE-1KV-1A(DO-214AC)"))
    )
    (comp (ref "D114")
      (value "Zen15")
      (footprint "eagle-import:DO214AA")
      (libsource (lib "eagle-import") (part "SM6T"))
    )
    (comp (ref "D115")
      (value "SS12")
      (footprint "eagle-import:DO-214AC_SLIM")
      (libsource (lib "eagle-import") (part "DIODE-GEN-PURPOSE-1KV-1A(DO-214AC)DO-214AC/1206"))
    )
    (comp (ref "D116")
      (value "SS12")
      (footprint "eagle-import:DO-214AC_SLIM")
      (libsource (lib "eagle-import") (part "DIODE-GEN-PURPOSE-1KV-1A(DO-214AC)DO-214AC/1206"))
    )
    (comp (ref "D117")
      (value "Zen11")
      (footprint "eagle-import:SOD-123_MINI-SMA")
      (libsource (lib "eagle-import") (part "CGRM400-G1"))
    )
    (comp (ref "FID33")
      (value "FIDUCIAL")
      (footprint "eagle-import:FIDUCIAL_1MM")
      (libsource (lib "eagle-import") (part "FIDUCIAL"))
    )
    (comp (ref "FID34")
      (value "FIDUCIAL")
      (footprint "eagle-import:FIDUCIAL_1MM")
      (libsource (lib "eagle-import") (part "FIDUCIAL"))
    )
    (comp (ref "FID35")
      (value "FIDUCIAL")
      (footprint "eagle-import:FIDUCIAL_1MM")
      (libsource (lib "eagle-import") (part "FIDUCIAL"))
    )
    (comp (ref "FID36")
      (value "FIDUCIAL")
      (footprint "eagle-import:FIDUCIAL_1MM")
      (libsource (lib "eagle-import") (part "FIDUCIAL"))
    )
    (comp (ref "IC64")
      (value "4028")
      (footprint "eagle-import:SO16")
      (libsource (lib "eagle-import") (part "4028D"))
    )
    (comp (ref "IC65")
      (value "317TO202H_NOHOLE")
      (footprint "eagle-import:TO220H_NOHOLE")
      (libsource (lib "eagle-import") (part "317TO202H_NOHOLE"))
    )
    (comp (ref "IC66")
      (value "ULN2004")
      (footprint "eagle-import:SO16")
      (libsource (lib "eagle-import") (part "ULN2004AD"))
    )
    (comp (ref "IC67")
      (value "LM339")
      (footprint "eagle-import:SO14")
      (libsource (lib "eagle-import") (part "LM339D"))
    )
    (comp (ref "IC68")
      (value "78L06")
      (footprint "eagle-import:SOT89_ROUND")
      (libsource (lib "eagle-import") (part "78LXXSOT89_ROUND"))
    )
    (comp (ref "IC69")
      (value "555")
      (footprint "eagle-import:SO08")
      (libsource (lib "eagle-import") (part "555DNE"))
    )
    (comp (ref "IC70")
      (value "4538")
      (footprint "eagle-import:SO16")
      (libsource (lib "eagle-import") (part "4538D"))
    )
    (comp (ref "IC71")
      (value "78L10")
      (footprint "eagle-import:SOT89_ROUND")
      (libsource (lib "eagle-import") (part "78LXXSOT89_ROUND"))
    )
    (comp (ref "IC72")
      (value "LM2904")
      (footprint "eagle-import:SO08")
      (libsource (lib "eagle-import") (part "LM358D"))
    )
    (comp (ref "JP36")
      (value "JP2EJP2_SMALLPADS")
      (footprint "eagle-import:JP2_SMALLPADS")
      (libsource (lib "eagle-import") (part "JP2EJP2_SMALLPADS"))
    )
    (comp (ref "JP37")
      (value "JP2E_ORIG")
      (footprint "eagle-import:JP2_ORIG_SMALLPADS")
      (libsource (lib "eagle-import") (part "JP2E_ORIG"))
    )
    (comp (ref "JP38")
      (value "JP2EJP2_SMALLPADS")
      (footprint "eagle-import:JP2_SMALLPADS")
      (libsource (lib "eagle-import") (part "JP2EJP2_SMALLPADS"))
    )
    (comp (ref "JP39")
      (value "JP2EJP2_SMALLPADS")
      (footprint "eagle-import:JP2_SMALLPADS")
      (libsource (lib "eagle-import") (part "JP2EJP2_SMALLPADS"))
    )
    (comp (ref "JP40")
      (value "JP2EJP2_SMALLPADS")
      (footprint "eagle-import:JP2_SMALLPADS")
      (libsource (lib "eagle-import") (part "JP2EJP2_SMALLPADS"))
    )
    (comp (ref "LED43")
      (value "LEDLD260")
      (footprint "eagle-import:LD260")
      (libsource (lib "eagle-import") (part "LEDLD260"))
    )
    (comp (ref "LED44")
      (value "LEDLD260")
      (footprint "eagle-import:LD260")
      (libsource (lib "eagle-import") (part "LEDLD260"))
    )
    (comp (ref "LED45")
      (value "LEDLD260")
      (footprint "eagle-import:LD260")
      (libsource (lib "eagle-import") (part "LEDLD260"))
    )
    (comp (ref "LED46")
      (value "LEDLD260")
      (footprint "eagle-import:LD260")
      (libsource (lib "eagle-import") (part "LEDLD260"))
    )
    (comp (ref "LED47")
      (value "LEDLD260")
      (footprint "eagle-import:LD260")
      (libsource (lib "eagle-import") (part "LEDLD260"))
    )
    (comp (ref "LED48")
      (value "LEDLD260")
      (footprint "eagle-import:LD260")
      (libsource (lib "eagle-import") (part "LEDLD260"))
    )
    (comp (ref "Q74")
      (value "BA")
      (footprint "eagle-import:SOT89")
      (libsource (lib "eagle-import") (part "PNP-TRANSISTOR_SOT89"))
    )
    (comp (ref "Q75")
      (value "BA.")
      (footprint "eagle-import:SOT89")
      (libsource (lib "eagle-import") (part "PNP-TRANSISTOR_SOT89"))
    )
    (comp (ref "Q76")
      (value "BA.")
      (footprint "eagle-import:SOT89")
      (libsource (lib "eagle-import") (part "PNP-TRANSISTOR_SOT89"))
    )
    (comp (ref "Q77")
      (value "BA")
      (footprint "eagle-import:SOT89")
      (libsource (lib "eagle-import") (part "PNP-TRANSISTOR_SOT89"))
    )
    (comp (ref "Q78")
      (value "MY")
      (footprint "eagle-import:SOT89")
      (libsource (lib "eagle-import") (part "NPN-TRANSISTOR_SOT89"))
    )
    (comp (ref "Q79")
      (value "J1")
      (footprint "eagle-import:SOT-23")
      (fields (field (name "MPN") "BSS138W-7-F"))
      (libsource (lib "eagle-import") (part "SMD-MOSFET-N-CH-50V-200MA-BSS138W-7-F(SOT-23)"))
    )
    (comp (ref "Q80")
      (value "J1")
      (footprint "eagle-import:SOT-23")
      (fields (field (name "MPN") "BSS138W-7-F"))
      (libsource (lib "eagle-import") (part "SMD-MOSFET-N-CH-50V-200MA-BSS138W-7-F(SOT-23)"))
    )
    (comp (ref "Q81")
      (value "J1")
      (footprint "eagle-import:SOT-23")
      (fields (field (name "MPN") "BSS138W-7-F"))
      (libsource (lib "eagle-import") (part "SMD-MOSFET-N-CH-50V-200MA-BSS138W-7-F(SOT-23)"))
    )
    (comp (ref "Q82")
      (value "BA")
      (footprint "eagle-import:SOT89")
      (libsource (lib "eagle-import") (part "PNP-TRANSISTOR_SOT89"))
    )
    (comp (ref "Q83")
      (value "J1")
      (footprint "eagle-import:SOT-23")
      (fields (field (name "MPN") "BSS138W-7-F"))
      (libsource (lib "eagle-import") (part "SMD-MOSFET-N-CH-50V-200MA-BSS138W-7-F(SOT-23)"))
    )
    (comp (ref "R409")
      (value "47")
      (footprint "eagle-import:V235_17_1MM")
      (libsource (lib "eagle-import") (part "R-EU_V235/17_1MM"))
    )
    (comp (ref "R410")
      (value "13")
      (footprint "eagle-import:R1206")
      (fields (field (name "MPN") "RC1206JR-0713RL"))
      (libsource (lib "eagle-import") (part "SMD-RES-13R-5%-1/4W(1206)"))
    )
    (comp (ref "R411")
      (value "47")
      (footprint "eagle-import:V235_17_1MM")
      (libsource (lib "eagle-import") (part "R-EU_V235/17_1MM"))
    )
    (comp (ref "R412")
      (value "104")
      (footprint "eagle-import:R0805")
      (fields (field (name "MPN") "RC0805FR-0710KL"))
      (libsource (lib "eagle-import") (part "SMD-RES-10K-1%-1/8W(0805)"))
    )
    (comp (ref "R413")
      (value "104")
      (footprint "eagle-import:R0805")
      (fields (field (name "MPN") "RC0805FR-0710KL"))
      (libsource (lib "eagle-import") (part "SMD-RES-10K-1%-1/8W(0805)"))
    )
    (comp (ref "R414")
      (value "104")
      (footprint "eagle-import:R0805")
      (fields (field (name "MPN") "RC0805FR-0710KL"))
      (libsource (lib "eagle-import") (part "SMD-RES-10K-1%-1/8W(0805)"))
    )
    (comp (ref "R415")
      (value "4701")
      (footprint "eagle-import:R0805")
      (fields (field (name "MPN") "RC0805JR-074K7L"))
      (libsource (lib "eagle-import") (part "SMD-RES-4.7K-5%-1/8W(0805)"))
    )
    (comp (ref "R416")
      (value "1002")
      (footprint "eagle-import:R0805")
      (fields (field (name "MPN") "RC0805FR-0710KL"))
      (libsource (lib "eagle-import") (part "SMD-RES-10K-1%-1/8W(0805)"))
    )
    (comp (ref "R417")
      (value "1002")
      (footprint "eagle-import:R0805")
      (fields (field (name "MPN") "RC0805FR-0710KL"))
      (libsource (lib "eagle-import") (part "SMD-RES-10K-1%-1/8W(0805)"))
    )
    (comp (ref "R418")
      (value "1502")
      (footprint "eagle-import:R0805")
      (fields (field (name "MPN") "RC0805FR-0710KL"))
      (libsource (lib "eagle-import") (part "SMD-RES-10K-1%-1/8W(0805)"))
    )
    (comp (ref "R419")
      (value "104")
      (footprint "eagle-import:R0805")
      (fields (field (name "MPN") "RC0805FR-0710KL"))
      (libsource (lib "eagle-import") (part "SMD-RES-10K-1%-1/8W(0805)"))
    )
    (comp (ref "R420")
      (value "104")
      (footprint "eagle-import:R0805")
      (fields (field (name "MPN") "RC0805FR-0710KL"))
      (libsource (lib "eagle-import") (part "SMD-RES-10K-1%-1/8W(0805)"))
    )
    (comp (ref "R421")
      (value "1502")
      (footprint "eagle-import:R0805")
      (fields (field (name "MPN") "RC0805FR-0710KL"))
      (libsource (lib "eagle-import") (part "SMD-RES-10K-1%-1/8W(0805)"))
    )
    (comp (ref "R422")
      (value "1002")
      (footprint "eagle-import:R0805")
      (fields (field (name "MPN") "RC0805FR-0710KL"))
      (libsource (lib "eagle-import") (part "SMD-RES-10K-1%-1/8W(0805)"))
    )
    (comp (ref "R423")
      (value "2201")
      (footprint "eagle-import:R0805")
      (fields (field (name "MPN") "RC0805JR-072K2L"))
      (libsource (lib "eagle-import") (part "SMD-RES-2.2K-5%-1/8W(0805)"))
    )
    (comp (ref "R424")
      (value "1002")
      (footprint "eagle-import:R0805")
      (fields (field (name "MPN") "RC0805FR-0710KL"))
      (libsource (lib "eagle-import") (part "SMD-RES-10K-1%-1/8W(0805)"))
    )
    (comp (ref "R425")
      (value "4701")
      (footprint "eagle-import:R0805")
      (fields (field (name "MPN") "RC0805JR-074K7L"))
      (libsource (lib "eagle-import") (part "SMD-RES-4.7K-5%-1/8W(0805)"))
    )
    (comp (ref "R426")
      (value "2702")
      (footprint "eagle-import:R0805")
      (fields (field (name "MPN") "RC0805JR-074K7L"))
      (libsource (lib "eagle-import") (part "SMD-RES-4.7K-5%-1/8W(0805)"))
    )
    (comp (ref "R427")
      (value "102")
      (footprint "eagle-import:R0805")
      (fields (field (name "MPN") "RC0805JR-071KL"))
      (libsource (lib "eagle-import") (part "SMD-RES-1K-5%-1/8W(0805)"))
    )
    (comp (ref "R428")
      (value "102")
      (footprint "eagle-import:R0805")
      (fields (field (name "MPN") "RC0805JR-07220RL"))
      (libsource (lib "eagle-import") (part "SMD-RES-220R-5%-1/8W(0805)"))
    )
    (comp (ref "R429")
      (value "102")
      (footprint "eagle-import:R0805")
      (fields (field (name "MPN") "RC0805JR-071KL"))
      (libsource (lib "eagle-import") (part "SMD-RES-1K-5%-1/8W(0805)"))
    )
    (comp (ref "R430")
      (value "13")
      (footprint "eagle-import:R1206")
      (fields (field (name "MPN") "RC1206JR-0713RL"))
      (libsource (lib "eagle-import") (part "SMD-RES-13R-5%-1/4W(1206)"))
    )
    (comp (ref "R431")
      (value "13")
      (footprint "eagle-import:R1206")
      (fields (field (name "MPN") "RC1206JR-0713RL"))
      (libsource (lib "eagle-import") (part "SMD-RES-13R-5%-1/4W(1206)"))
    )
    (comp (ref "R432")
      (value "2702")
      (footprint "eagle-import:R0805")
      (fields (field (name "MPN") "RC0805JR-074K7L"))
      (libsource (lib "eagle-import") (part "SMD-RES-4.7K-5%-1/8W(0805)"))
    )
    (comp (ref "R433")
      (value "4701")
      (footprint "eagle-import:R0805")
      (fields (field (name "MPN") "RC0805JR-074K7L"))
      (libsource (lib "eagle-import") (part "SMD-RES-4.7K-5%-1/8W(0805)"))
    )
    (comp (ref "R434")
      (value "100")
      (footprint "eagle-import:R0805")
      (fields (field (name "MPN") "RC0805JR-072K2L"))
      (libsource (lib "eagle-import") (part "SMD-RES-2.2K-5%-1/8W(0805)"))
    )
    (comp (ref "R435")
      (value "104")
      (footprint "eagle-import:R0805")
      (fields (field (name "MPN") "RC0805FR-0710KL"))
      (libsource (lib "eagle-import") (part "SMD-RES-10K-1%-1/8W(0805)"))
    )
    (comp (ref "R436")
      (value "104")
      (footprint "eagle-import:R0805")
      (fields (field (name "MPN") "RC0805FR-0710KL"))
      (libsource (lib "eagle-import") (part "SMD-RES-10K-1%-1/8W(0805)"))
    )
    (comp (ref "R437")
      (value "2702")
      (footprint "eagle-import:R0805")
      (fields (field (name "MPN") "RC0805FR-0710KL"))
      (libsource (lib "eagle-import") (part "SMD-RES-10K-1%-1/8W(0805)"))
    )
    (comp (ref "R438")
      (value "47")
      (footprint "eagle-import:V235_17_1MM")
      (libsource (lib "eagle-import") (part "R-EU_V235/17_1MM"))
    )
    (comp (ref "R439")
      (value "47")
      (footprint "eagle-import:V235_17_1MM")
      (libsource (lib "eagle-import") (part "R-EU_V235/17_1MM"))
    )
    (comp (ref "R440")
      (value "2702")
      (footprint "eagle-import:R0805")
      (fields (field (name "MPN") "RC0805JR-074K7L"))
      (libsource (lib "eagle-import") (part "SMD-RES-4.7K-5%-1/8W(0805)"))
    )
    (comp (ref "R441")
      (value "2201")
      (footprint "eagle-import:R0805")
      (fields (field (name "MPN") "RC0805JR-072K2L"))
      (libsource (lib "eagle-import") (part "SMD-RES-2.2K-5%-1/8W(0805)"))
    )
    (comp (ref "R442")
      (value "1002")
      (footprint "eagle-import:R0805")
      (fields (field (name "MPN") "RC0805JR-074K7L"))
      (libsource (lib "eagle-import") (part "SMD-RES-4.7K-5%-1/8W(0805)"))
    )
    (comp (ref "R443")
      (value "1002")
      (footprint "eagle-import:R0805")
      (fields (field (name "MPN") "RC0805FR-0710KL"))
      (libsource (lib "eagle-import") (part "SMD-RES-10K-1%-1/8W(0805)"))
    )
    (comp (ref "R444")
      (value "102")
      (footprint "eagle-import:R0805")
      (fields (field (name "MPN") "RC0805JR-071KL"))
      (libsource (lib "eagle-import") (part "SMD-RES-1K-5%-1/8W(0805)"))
    )
    (comp (ref "R445")
      (value "2702")
      (footprint "eagle-import:R0805")
      (fields (field (name "MPN") "RC0805JR-074K7L"))
      (libsource (lib "eagle-import") (part "SMD-RES-4.7K-5%-1/8W(0805)"))
    )
    (comp (ref "R446")
      (value "1002")
      (footprint "eagle-import:R0805")
      (fields (field (name "MPN") "RC0805JR-071KL"))
      (libsource (lib "eagle-import") (part "SMD-RES-1K-5%-1/8W(0805)"))
    )
    (comp (ref "R447")
      (value "1002")
      (footprint "eagle-import:R0805")
      (fields (field (name "MPN") "RC0805JR-071KL"))
      (libsource (lib "eagle-import") (part "SMD-RES-1K-5%-1/8W(0805)"))
    )
    (comp (ref "R448")
      (value "R_user")
      (footprint "eagle-import:R0805")
      (libsource (lib "eagle-import") (part "R-EU_R0805"))
    )
    (comp (ref "R449")
      (value "104")
      (footprint "eagle-import:R0805")
      (fields (field (name "MPN") "RC0805FR-0710KL"))
      (libsource (lib "eagle-import") (part "SMD-RES-10K-1%-1/8W(0805)"))
    )
    (comp (ref "R450")
      (value "104")
      (footprint "eagle-import:R0805")
      (fields (field (name "MPN") "RC0805FR-0710KL"))
      (libsource (lib "eagle-import") (part "SMD-RES-10K-1%-1/8W(0805)"))
    )
    (comp (ref "R451")
      (value "104")
      (footprint "eagle-import:R0805")
      (fields (field (name "MPN") "RC0805FR-0710KL"))
      (libsource (lib "eagle-import") (part "SMD-RES-10K-1%-1/8W(0805)"))
    )
    (comp (ref "R452")
      (value "13")
      (footprint "eagle-import:R1206")
      (fields (field (name "MPN") "RC1206JR-0713RL"))
      (libsource (lib "eagle-import") (part "SMD-RES-13R-5%-1/4W(1206)"))
    )
    (comp (ref "R453")
      (value "2201")
      (footprint "eagle-import:R0805")
      (fields (field (name "MPN") "RC0805JR-071KL"))
      (libsource (lib "eagle-import") (part "SMD-RES-1K-5%-1/8W(0805)"))
    )
    (comp (ref "R454")
      (value "100")
      (footprint "eagle-import:R0805")
      (fields (field (name "MPN") "RC0805JR-07220RL"))
      (libsource (lib "eagle-import") (part "SMD-RES-220R-5%-1/8W(0805)"))
    )
    (comp (ref "R455")
      (value "13")
      (footprint "eagle-import:R1206")
      (fields (field (name "MPN") "RC1206JR-0713RL"))
      (libsource (lib "eagle-import") (part "SMD-RES-13R-5%-1/4W(1206)"))
    )
    (comp (ref "R456")
      (value "4701")
      (footprint "eagle-import:R0805")
      (fields (field (name "MPN") "RC0805JR-074K7L"))
      (libsource (lib "eagle-import") (part "SMD-RES-4.7K-5%-1/8W(0805)"))
    )
    (comp (ref "R457")
      (value "104")
      (footprint "eagle-import:R0805")
      (fields (field (name "MPN") "RC0805JR-074K7L"))
      (libsource (lib "eagle-import") (part "SMD-RES-4.7K-5%-1/8W(0805)"))
    )
    (comp (ref "R458")
      (value "100")
      (footprint "eagle-import:R0805")
      (fields (field (name "MPN") "RC0805JR-072K2L"))
      (libsource (lib "eagle-import") (part "SMD-RES-2.2K-5%-1/8W(0805)"))
    )
    (comp (ref "R459")
      (value "100")
      (footprint "eagle-import:R0805")
      (fields (field (name "MPN") "RC0805JR-072K2L"))
      (libsource (lib "eagle-import") (part "SMD-RES-2.2K-5%-1/8W(0805)"))
    )
    (comp (ref "SJMP8")
      (value "SJ")
      (footprint "eagle-import:SJ")
      (libsource (lib "eagle-import") (part "SJ"))
    )
    (comp (ref "START8")
      (value "TPSB2.0")
      (footprint "eagle-import:B2.0")
      (libsource (lib "eagle-import") (part "TPSB2.0"))
    )
    (comp (ref "TP185")
      (value "TPSB2.0")
      (footprint "eagle-import:B2.0")
      (libsource (lib "eagle-import") (part "TPSB2.0"))
    )
    (comp (ref "TP186")
      (value "TPSB2.0")
      (footprint "eagle-import:B2.0")
      (libsource (lib "eagle-import") (part "TPSB2.0"))
    )
    (comp (ref "TP187")
      (value "TPSB2.0")
      (footprint "eagle-import:B2.0")
      (libsource (lib "eagle-import") (part "TPSB2.0"))
    )
    (comp (ref "TP188")
      (value "TPSB2.0")
      (footprint "eagle-import:B2.0")
      (libsource (lib "eagle-import") (part "TPSB2.0"))
    )
    (comp (ref "TP189")
      (value "TPSB2.0")
      (footprint "eagle-import:B2.0")
      (libsource (lib "eagle-import") (part "TPSB2.0"))
    )
    (comp (ref "TP190")
      (value "TPSB2.0")
      (footprint "eagle-import:B2.0")
      (libsource (lib "eagle-import") (part "TPSB2.0"))
    )
    (comp (ref "TP191")
      (value "TPSB2.0")
      (footprint "eagle-import:B2.0")
      (libsource (lib "eagle-import") (part "TPSB2.0"))
    )
    (comp (ref "TP192")
      (value "TPSB2.0")
      (footprint "eagle-import:B2.0")
      (libsource (lib "eagle-import") (part "TPSB2.0"))
    )
    (comp (ref "TP193")
      (value "TPSB2.0")
      (footprint "eagle-import:B2.0")
      (libsource (lib "eagle-import") (part "TPSB2.0"))
    )
    (comp (ref "TP194")
      (value "TPSB2.0")
      (footprint "eagle-import:B2.0")
      (libsource (lib "eagle-import") (part "TPSB2.0"))
    )
    (comp (ref "TP195")
      (value "TPSB2.0")
      (footprint "eagle-import:B2.0")
      (libsource (lib "eagle-import") (part "TPSB2.0"))
    )
    (comp (ref "TP196")
      (value "TPSB2.0")
      (footprint "eagle-import:B2.0")
      (libsource (lib "eagle-import") (part "TPSB2.0"))
    )
    (comp (ref "TP197")
      (value "TPSB2.0")
      (footprint "eagle-import:B2.0")
      (libsource (lib "eagle-import") (part "TPSB2.0"))
    )
    (comp (ref "TP198")
      (value "TPSB2.0")
      (footprint "eagle-import:B2.0")
      (libsource (lib "eagle-import") (part "TPSB2.0"))
    )
    (comp (ref "TP199")
      (value "TPSB2.0")
      (footprint "eagle-import:B2.0")
      (libsource (lib "eagle-import") (part "TPSB2.0"))
    )
    (comp (ref "TP200")
      (value "TPSB2.0")
      (footprint "eagle-import:B2.0")
      (libsource (lib "eagle-import") (part "TPSB2.0"))
    )
    (comp (ref "TP201")
      (value "TPSB2.0")
      (footprint "eagle-import:B2.0")
      (libsource (lib "eagle-import") (part "TPSB2.0"))
    )
    (comp (ref "TP202")
      (value "TPSB2.0")
      (footprint "eagle-import:B2.0")
      (libsource (lib "eagle-import") (part "TPSB2.0"))
    )
    (comp (ref "TP203")
      (value "TPSB1,27")
      (footprint "eagle-import:B1,27")
      (libsource (lib "eagle-import") (part "TPSB1,27"))
    )
    (comp (ref "TP204")
      (value "TPSB2.0")
      (footprint "eagle-import:B2.0")
      (libsource (lib "eagle-import") (part "TPSB2.0"))
    )
    (comp (ref "TP205")
      (value "TPSB2.0")
      (footprint "eagle-import:B2.0")
      (libsource (lib "eagle-import") (part "TPSB2.0"))
    )
    (comp (ref "TP206")
      (value "TPSB2.0")
      (footprint "eagle-import:B2.0")
      (libsource (lib "eagle-import") (part "TPSB2.0"))
    )
    (comp (ref "TP207")
      (value "TPSB2.0")
      (footprint "eagle-import:B2.0")
      (libsource (lib "eagle-import") (part "TPSB2.0"))
    )
    (comp (ref "X22")
      (value "CON_BMWV2")
      (footprint "eagle-import:24-PIN_V2")
      (libsource (lib "eagle-import") (part "CON_BMWV2"))
    )
    (comp (ref "X23")
      (value "22-23-2051")
      (footprint "eagle-import:22-23-2051")
      (fields (field (name "MF") "MOLEX"))
      (libsource (lib "eagle-import") (part "22-23-2051"))
    )
    (comp (ref "X24")
      (value "22-23-2021")
      (footprint "eagle-import:22-23-2021")
      (fields (field (name "MF") "MOLEX"))
      (libsource (lib "eagle-import") (part "22-23-2021"))
    )
    (comp (ref "FID1")
      (value "FIDUCIAL")
      (footprint "eagle-import:FIDUCIAL_1MM")
      (libsource (lib "eagle-import") (part "FIDUCIAL"))
    )
    (comp (ref "FID1B")
      (value "FIDUCIALFIDUCIAL_1MM_WITH_SOLDERMASK")
      (footprint "eagle-import:FIDUCIAL_1MM_WITH_SOLDERMASK")
      (libsource (lib "eagle-import") (part "FIDUCIALFIDUCIAL_1MM_WITH_SOLDERMASK"))
    )
    (comp (ref "FID2")
      (value "FIDUCIAL")
      (footprint "eagle-import:FIDUCIAL_1MM")
      (libsource (lib "eagle-import") (part "FIDUCIAL"))
    )
    (comp (ref "FID2B")
      (value "FIDUCIALFIDUCIAL_1MM_WITH_SOLDERMASK")
      (footprint "eagle-import:FIDUCIAL_1MM_WITH_SOLDERMASK")
      (libsource (lib "eagle-import") (part "FIDUCIALFIDUCIAL_1MM_WITH_SOLDERMASK"))
    )
    (comp (ref "3")
      (value "2081-1132")
      (footprint "eagle-import:12-PIN")
      (libsource (lib "eagle-import") (part "2081-1132"))
    )
    (comp (ref "4")
      (value "2081-1132")
      (footprint "eagle-import:12-PIN")
      (libsource (lib "eagle-import") (part "2081-1132"))
    )
    (comp (ref "6V1")
      (value "TPSB2.0")
      (footprint "eagle-import:B2.0")
      (libsource (lib "eagle-import") (part "TPSB2.0"))
    )
    (comp (ref "10V1")
      (value "TPSB2.0")
      (footprint "eagle-import:B2.0")
      (libsource (lib "eagle-import") (part "TPSB2.0"))
    )
    (comp (ref "C1")
      (value "100u")
      (footprint "eagle-import:C1206")
      (fields (field (name "MPN") "GRM31CR60J107ME39L"))
      (libsource (lib "eagle-import") (part "CERAMIC-100UF-6.3V-20%-X5R(1206)"))
    )
    (comp (ref "C3")
      (value "100u")
      (footprint "eagle-import:C1206")
      (fields (field (name "MPN") "GRM31CR60J107ME39L"))
      (libsource (lib "eagle-import") (part "CERAMIC-100UF-6.3V-20%-X5R(1206)"))
    )
    (comp (ref "C4")
      (value "100nF,")
      (footprint "eagle-import:C0805")
      (fields (field (name "MPN") "CC0805KRX7R9BB104"))
      (libsource (lib "eagle-import") (part "CERAMIC-100NF-50V-10%-X7R(0805)"))
    )
    (comp (ref "C5")
      (value "4.7u")
      (footprint "eagle-import:C0805")
      (fields (field (name "MPN") "CC0805KKX5R8BB475"))
      (libsource (lib "eagle-import") (part "CERAMIC-4.7UF-25V-10%-X5R(0805)"))
    )
    (comp (ref "C6")
      (value "100nF.")
      (footprint "eagle-import:C0805")
      (fields (field (name "MPN") "CC0805KRX7R9BB104"))
      (libsource (lib "eagle-import") (part "CERAMIC-100NF-50V-10%-X7R(0805)"))
    )
    (comp (ref "C7")
      (value "100nF.")
      (footprint "eagle-import:C0805")
      (fields (field (name "MPN") "CC0805KRX7R9BB104"))
      (libsource (lib "eagle-import") (part "CERAMIC-100NF-50V-10%-X7R(0805)"))
    )
    (comp (ref "C8")
      (value "2.2nF")
      (footprint "eagle-import:C0805")
      (fields (field (name "MPN") "CC0805KRX7R9BB104"))
      (libsource (lib "eagle-import") (part "CERAMIC-100NF-50V-10%-X7R(0805)"))
    )
    (comp (ref "C9")
      (value "100nF")
      (footprint "eagle-import:C0805")
      (fields (field (name "MPN") "CC0805KRX7R9BB104"))
      (libsource (lib "eagle-import") (part "CERAMIC-100NF-50V-10%-X7R(0805)"))
    )
    (comp (ref "C10")
      (value "100nF")
      (footprint "eagle-import:C0805")
      (fields (field (name "MPN") "CC0805KRX7R9BB104"))
      (libsource (lib "eagle-import") (part "CERAMIC-100NF-50V-10%-X7R(0805)"))
    )
    (comp (ref "C11")
      (value "100nF,")
      (footprint "eagle-import:C0805")
      (fields (field (name "MPN") "CC0805KRX7R9BB104"))
      (libsource (lib "eagle-import") (part "CERAMIC-100NF-50V-10%-X7R(0805)"))
    )
    (comp (ref "C12")
      (value "4.7u")
      (footprint "eagle-import:C0805")
      (fields (field (name "MPN") "CC0805KKX5R8BB475"))
      (libsource (lib "eagle-import") (part "CERAMIC-4.7UF-25V-10%-X5R(0805)"))
    )
    (comp (ref "C13")
      (value "10u")
      (footprint "eagle-import:C1206")
      (fields (field (name "MPN") "GRM31CR60J107ME39L"))
      (libsource (lib "eagle-import") (part "CERAMIC-100UF-6.3V-20%-X5R(1206)"))
    )
    (comp (ref "D3")
      (value "1N4007,")
      (footprint "eagle-import:DO-214AC")
      (fields (field (name "MPN") "1N4007"))
      (libsource (lib "eagle-import") (part "DIODE-GEN-PURPOSE-1KV-1A(DO-214AC)"))
    )
    (comp (ref "D5")
      (value "1N4007,")
      (footprint "eagle-import:DO-214AC")
      (fields (field (name "MPN") "1N4007"))
      (libsource (lib "eagle-import") (part "DIODE-GEN-PURPOSE-1KV-1A(DO-214AC)"))
    )
    (comp (ref "D6")
      (value "1N4007.")
      (footprint "eagle-import:DO-214AC")
      (fields (field (name "MPN") "1N4007"))
      (libsource (lib "eagle-import") (part "DIODE-GEN-PURPOSE-1KV-1A(DO-214AC)"))
    )
    (comp (ref "D7")
      (value "1N5817")
      (footprint "eagle-import:DO-214AC_SLIM")
      (libsource (lib "eagle-import") (part "DIODE-GEN-PURPOSE-1KV-1A(DO-214AC)DO-214AC/1206"))
    )
    (comp (ref "D8")
      (value "1N5817.")
      (footprint "eagle-import:DO-214AC_SLIM")
      (libsource (lib "eagle-import") (part "DIODE-GEN-PURPOSE-1KV-1A(DO-214AC)DO-214AC/1206"))
    )
    (comp (ref "D9")
      (value "1N5817.")
      (footprint "eagle-import:DO-214AC_SLIM")
      (libsource (lib "eagle-import") (part "DIODE-GEN-PURPOSE-1KV-1A(DO-214AC)DO-214AC/1206"))
    )
    (comp (ref "D10")
      (value "1N5817")
      (footprint "eagle-import:DO-214AC_SLIM")
      (libsource (lib "eagle-import") (part "DIODE-GEN-PURPOSE-1KV-1A(DO-214AC)DO-214AC/1206"))
    )
    (comp (ref "D11")
      (value "1N4007.")
      (footprint "eagle-import:DO-214AC")
      (fields (field (name "MPN") "1N4007"))
      (libsource (lib "eagle-import") (part "DIODE-GEN-PURPOSE-1KV-1A(DO-214AC)"))
    )
    (comp (ref "D12")
      (value "1N4007")
      (footprint "eagle-import:DO-214AC")
      (libsource (lib "eagle-import") (part "DIODE-GEN-PURPOSE-1KV-1A(DO-214AC)"))
    )
    (comp (ref "D13")
      (value "Zen15")
      (footprint "eagle-import:DO214AA")
      (libsource (lib "eagle-import") (part "SM6T"))
    )
    (comp (ref "D15")
      (value "SS12")
      (footprint "eagle-import:DO-214AC_SLIM")
      (libsource (lib "eagle-import") (part "DIODE-GEN-PURPOSE-1KV-1A(DO-214AC)DO-214AC/1206"))
    )
    (comp (ref "D16")
      (value "SS12")
      (footprint "eagle-import:DO-214AC_SLIM")
      (libsource (lib "eagle-import") (part "DIODE-GEN-PURPOSE-1KV-1A(DO-214AC)DO-214AC/1206"))
    )
    (comp (ref "D17")
      (value "Zen11")
      (footprint "eagle-import:SOD-123_MINI-SMA")
      (libsource (lib "eagle-import") (part "CGRM400-G1"))
    )
    (comp (ref "FID3")
      (value "FIDUCIAL")
      (footprint "eagle-import:FIDUCIAL_1MM")
      (libsource (lib "eagle-import") (part "FIDUCIAL"))
    )
    (comp (ref "FID4")
      (value "FIDUCIAL")
      (footprint "eagle-import:FIDUCIAL_1MM")
      (libsource (lib "eagle-import") (part "FIDUCIAL"))
    )
    (comp (ref "FID5")
      (value "FIDUCIAL")
      (footprint "eagle-import:FIDUCIAL_1MM")
      (libsource (lib "eagle-import") (part "FIDUCIAL"))
    )
    (comp (ref "FID6")
      (value "FIDUCIAL")
      (footprint "eagle-import:FIDUCIAL_1MM")
      (libsource (lib "eagle-import") (part "FIDUCIAL"))
    )
    (comp (ref "IC1")
      (value "4028")
      (footprint "eagle-import:SO16")
      (libsource (lib "eagle-import") (part "4028D"))
    )
    (comp (ref "IC2")
      (value "317TO202H_NOHOLE")
      (footprint "eagle-import:TO220H_NOHOLE")
      (libsource (lib "eagle-import") (part "317TO202H_NOHOLE"))
    )
    (comp (ref "IC3")
      (value "ULN2004")
      (footprint "eagle-import:SO16")
      (libsource (lib "eagle-import") (part "ULN2004AD"))
    )
    (comp (ref "IC4")
      (value "LM339")
      (footprint "eagle-import:SO14")
      (libsource (lib "eagle-import") (part "LM339D"))
    )
    (comp (ref "IC5")
      (value "78L06")
      (footprint "eagle-import:SOT89_ROUND")
      (libsource (lib "eagle-import") (part "78LXXSOT89_ROUND"))
    )
    (comp (ref "IC6")
      (value "555")
      (footprint "eagle-import:SO08")
      (libsource (lib "eagle-import") (part "555DNE"))
    )
    (comp (ref "IC7")
      (value "4538")
      (footprint "eagle-import:SO16")
      (libsource (lib "eagle-import") (part "4538D"))
    )
    (comp (ref "IC8")
      (value "78L10")
      (footprint "eagle-import:SOT89_ROUND")
      (libsource (lib "eagle-import") (part "78LXXSOT89_ROUND"))
    )
    (comp (ref "IC9")
      (value "LM2904")
      (footprint "eagle-import:SO08")
      (libsource (lib "eagle-import") (part "LM358D"))
    )
    (comp (ref "JP1")
      (value "JP2EJP2_SMALLPADS")
      (footprint "eagle-import:JP2_SMALLPADS")
      (libsource (lib "eagle-import") (part "JP2EJP2_SMALLPADS"))
    )
    (comp (ref "JP2")
      (value "JP2E_ORIG")
      (footprint "eagle-import:JP2_ORIG_SMALLPADS")
      (libsource (lib "eagle-import") (part "JP2E_ORIG"))
    )
    (comp (ref "JP3")
      (value "JP2EJP2_SMALLPADS")
      (footprint "eagle-import:JP2_SMALLPADS")
      (libsource (lib "eagle-import") (part "JP2EJP2_SMALLPADS"))
    )
    (comp (ref "JP4")
      (value "JP2EJP2_SMALLPADS")
      (footprint "eagle-import:JP2_SMALLPADS")
      (libsource (lib "eagle-import") (part "JP2EJP2_SMALLPADS"))
    )
    (comp (ref "JP5")
      (value "JP2EJP2_SMALLPADS")
      (footprint "eagle-import:JP2_SMALLPADS")
      (libsource (lib "eagle-import") (part "JP2EJP2_SMALLPADS"))
    )
    (comp (ref "LED1")
      (value "LEDLD260")
      (footprint "eagle-import:LD260")
      (libsource (lib "eagle-import") (part "LEDLD260"))
    )
    (comp (ref "LED2")
      (value "LEDLD260")
      (footprint "eagle-import:LD260")
      (libsource (lib "eagle-import") (part "LEDLD260"))
    )
    (comp (ref "LED3")
      (value "LEDLD260")
      (footprint "eagle-import:LD260")
      (libsource (lib "eagle-import") (part "LEDLD260"))
    )
    (comp (ref "LED4")
      (value "LEDLD260")
      (footprint "eagle-import:LD260")
      (libsource (lib "eagle-import") (part "LEDLD260"))
    )
    (comp (ref "LED5")
      (value "LEDLD260")
      (footprint "eagle-import:LD260")
      (libsource (lib "eagle-import") (part "LEDLD260"))
    )
    (comp (ref "LED6")
      (value "LEDLD260")
      (footprint "eagle-import:LD260")
      (libsource (lib "eagle-import") (part "LEDLD260"))
    )
    (comp (ref "Q4")
      (value "BA")
      (footprint "eagle-import:SOT89")
      (libsource (lib "eagle-import") (part "PNP-TRANSISTOR_SOT89"))
    )
    (comp (ref "Q5")
      (value "BA.")
      (footprint "eagle-import:SOT89")
      (libsource (lib "eagle-import") (part "PNP-TRANSISTOR_SOT89"))
    )
    (comp (ref "Q6")
      (value "BA.")
      (footprint "eagle-import:SOT89")
      (libsource (lib "eagle-import") (part "PNP-TRANSISTOR_SOT89"))
    )
    (comp (ref "Q7")
      (value "BA")
      (footprint "eagle-import:SOT89")
      (libsource (lib "eagle-import") (part "PNP-TRANSISTOR_SOT89"))
    )
    (comp (ref "Q8")
      (value "MY")
      (footprint "eagle-import:SOT89")
      (libsource (lib "eagle-import") (part "NPN-TRANSISTOR_SOT89"))
    )
    (comp (ref "Q9")
      (value "J1")
      (footprint "eagle-import:SOT-23")
      (fields (field (name "MPN") "BSS138W-7-F"))
      (libsource (lib "eagle-import") (part "SMD-MOSFET-N-CH-50V-200MA-BSS138W-7-F(SOT-23)"))
    )
    (comp (ref "Q10")
      (value "J1")
      (footprint "eagle-import:SOT-23")
      (fields (field (name "MPN") "BSS138W-7-F"))
      (libsource (lib "eagle-import") (part "SMD-MOSFET-N-CH-50V-200MA-BSS138W-7-F(SOT-23)"))
    )
    (comp (ref "Q11")
      (value "J1")
      (footprint "eagle-import:SOT-23")
      (fields (field (name "MPN") "BSS138W-7-F"))
      (libsource (lib "eagle-import") (part "SMD-MOSFET-N-CH-50V-200MA-BSS138W-7-F(SOT-23)"))
    )
    (comp (ref "Q12")
      (value "BA")
      (footprint "eagle-import:SOT89")
      (libsource (lib "eagle-import") (part "PNP-TRANSISTOR_SOT89"))
    )
    (comp (ref "Q13")
      (value "J1")
      (footprint "eagle-import:SOT-23")
      (fields (field (name "MPN") "BSS138W-7-F"))
      (libsource (lib "eagle-import") (part "SMD-MOSFET-N-CH-50V-200MA-BSS138W-7-F(SOT-23)"))
    )
    (comp (ref "R7")
      (value "47")
      (footprint "eagle-import:V235_17_1MM")
      (libsource (lib "eagle-import") (part "R-EU_V235/17_1MM"))
    )
    (comp (ref "R11")
      (value "13")
      (footprint "eagle-import:R1206")
      (fields (field (name "MPN") "RC1206JR-0713RL"))
      (libsource (lib "eagle-import") (part "SMD-RES-13R-5%-1/4W(1206)"))
    )
    (comp (ref "R14")
      (value "47")
      (footprint "eagle-import:V235_17_1MM")
      (libsource (lib "eagle-import") (part "R-EU_V235/17_1MM"))
    )
    (comp (ref "R15")
      (value "104")
      (footprint "eagle-import:R0805")
      (fields (field (name "MPN") "RC0805FR-0710KL"))
      (libsource (lib "eagle-import") (part "SMD-RES-10K-1%-1/8W(0805)"))
    )
    (comp (ref "R16")
      (value "104")
      (footprint "eagle-import:R0805")
      (fields (field (name "MPN") "RC0805FR-0710KL"))
      (libsource (lib "eagle-import") (part "SMD-RES-10K-1%-1/8W(0805)"))
    )
    (comp (ref "R17")
      (value "104")
      (footprint "eagle-import:R0805")
      (fields (field (name "MPN") "RC0805FR-0710KL"))
      (libsource (lib "eagle-import") (part "SMD-RES-10K-1%-1/8W(0805)"))
    )
    (comp (ref "R18")
      (value "4701")
      (footprint "eagle-import:R0805")
      (fields (field (name "MPN") "RC0805JR-074K7L"))
      (libsource (lib "eagle-import") (part "SMD-RES-4.7K-5%-1/8W(0805)"))
    )
    (comp (ref "R19")
      (value "1002")
      (footprint "eagle-import:R0805")
      (fields (field (name "MPN") "RC0805FR-0710KL"))
      (libsource (lib "eagle-import") (part "SMD-RES-10K-1%-1/8W(0805)"))
    )
    (comp (ref "R20")
      (value "1002")
      (footprint "eagle-import:R0805")
      (fields (field (name "MPN") "RC0805FR-0710KL"))
      (libsource (lib "eagle-import") (part "SMD-RES-10K-1%-1/8W(0805)"))
    )
    (comp (ref "R21")
      (value "1502")
      (footprint "eagle-import:R0805")
      (fields (field (name "MPN") "RC0805FR-0710KL"))
      (libsource (lib "eagle-import") (part "SMD-RES-10K-1%-1/8W(0805)"))
    )
    (comp (ref "R22")
      (value "104")
      (footprint "eagle-import:R0805")
      (fields (field (name "MPN") "RC0805FR-0710KL"))
      (libsource (lib "eagle-import") (part "SMD-RES-10K-1%-1/8W(0805)"))
    )
    (comp (ref "R23")
      (value "104")
      (footprint "eagle-import:R0805")
      (fields (field (name "MPN") "RC0805FR-0710KL"))
      (libsource (lib "eagle-import") (part "SMD-RES-10K-1%-1/8W(0805)"))
    )
    (comp (ref "R24")
      (value "1502")
      (footprint "eagle-import:R0805")
      (fields (field (name "MPN") "RC0805FR-0710KL"))
      (libsource (lib "eagle-import") (part "SMD-RES-10K-1%-1/8W(0805)"))
    )
    (comp (ref "R25")
      (value "1002")
      (footprint "eagle-import:R0805")
      (fields (field (name "MPN") "RC0805FR-0710KL"))
      (libsource (lib "eagle-import") (part "SMD-RES-10K-1%-1/8W(0805)"))
    )
    (comp (ref "R26")
      (value "2201")
      (footprint "eagle-import:R0805")
      (fields (field (name "MPN") "RC0805JR-072K2L"))
      (libsource (lib "eagle-import") (part "SMD-RES-2.2K-5%-1/8W(0805)"))
    )
    (comp (ref "R27")
      (value "1002")
      (footprint "eagle-import:R0805")
      (fields (field (name "MPN") "RC0805FR-0710KL"))
      (libsource (lib "eagle-import") (part "SMD-RES-10K-1%-1/8W(0805)"))
    )
    (comp (ref "R28")
      (value "4701")
      (footprint "eagle-import:R0805")
      (fields (field (name "MPN") "RC0805JR-074K7L"))
      (libsource (lib "eagle-import") (part "SMD-RES-4.7K-5%-1/8W(0805)"))
    )
    (comp (ref "R29")
      (value "2702")
      (footprint "eagle-import:R0805")
      (fields (field (name "MPN") "RC0805JR-074K7L"))
      (libsource (lib "eagle-import") (part "SMD-RES-4.7K-5%-1/8W(0805)"))
    )
    (comp (ref "R30")
      (value "102")
      (footprint "eagle-import:R0805")
      (fields (field (name "MPN") "RC0805JR-071KL"))
      (libsource (lib "eagle-import") (part "SMD-RES-1K-5%-1/8W(0805)"))
    )
    (comp (ref "R32")
      (value "102")
      (footprint "eagle-import:R0805")
      (fields (field (name "MPN") "RC0805JR-07220RL"))
      (libsource (lib "eagle-import") (part "SMD-RES-220R-5%-1/8W(0805)"))
    )
    (comp (ref "R35")
      (value "102")
      (footprint "eagle-import:R0805")
      (fields (field (name "MPN") "RC0805JR-071KL"))
      (libsource (lib "eagle-import") (part "SMD-RES-1K-5%-1/8W(0805)"))
    )
    (comp (ref "R36")
      (value "13")
      (footprint "eagle-import:R1206")
      (fields (field (name "MPN") "RC1206JR-0713RL"))
      (libsource (lib "eagle-import") (part "SMD-RES-13R-5%-1/4W(1206)"))
    )
    (comp (ref "R37")
      (value "13")
      (footprint "eagle-import:R1206")
      (fields (field (name "MPN") "RC1206JR-0713RL"))
      (libsource (lib "eagle-import") (part "SMD-RES-13R-5%-1/4W(1206)"))
    )
    (comp (ref "R38")
      (value "2702")
      (footprint "eagle-import:R0805")
      (fields (field (name "MPN") "RC0805JR-074K7L"))
      (libsource (lib "eagle-import") (part "SMD-RES-4.7K-5%-1/8W(0805)"))
    )
    (comp (ref "R39")
      (value "4701")
      (footprint "eagle-import:R0805")
      (fields (field (name "MPN") "RC0805JR-074K7L"))
      (libsource (lib "eagle-import") (part "SMD-RES-4.7K-5%-1/8W(0805)"))
    )
    (comp (ref "R40")
      (value "100")
      (footprint "eagle-import:R0805")
      (fields (field (name "MPN") "RC0805JR-072K2L"))
      (libsource (lib "eagle-import") (part "SMD-RES-2.2K-5%-1/8W(0805)"))
    )
    (comp (ref "R41")
      (value "104")
      (footprint "eagle-import:R0805")
      (fields (field (name "MPN") "RC0805FR-0710KL"))
      (libsource (lib "eagle-import") (part "SMD-RES-10K-1%-1/8W(0805)"))
    )
    (comp (ref "R42")
      (value "104")
      (footprint "eagle-import:R0805")
      (fields (field (name "MPN") "RC0805FR-0710KL"))
      (libsource (lib "eagle-import") (part "SMD-RES-10K-1%-1/8W(0805)"))
    )
    (comp (ref "R44")
      (value "2702")
      (footprint "eagle-import:R0805")
      (fields (field (name "MPN") "RC0805FR-0710KL"))
      (libsource (lib "eagle-import") (part "SMD-RES-10K-1%-1/8W(0805)"))
    )
    (comp (ref "R45")
      (value "47")
      (footprint "eagle-import:V235_17_1MM")
      (libsource (lib "eagle-import") (part "R-EU_V235/17_1MM"))
    )
    (comp (ref "R46")
      (value "47")
      (footprint "eagle-import:V235_17_1MM")
      (libsource (lib "eagle-import") (part "R-EU_V235/17_1MM"))
    )
    (comp (ref "R47")
      (value "2702")
      (footprint "eagle-import:R0805")
      (fields (field (name "MPN") "RC0805JR-074K7L"))
      (libsource (lib "eagle-import") (part "SMD-RES-4.7K-5%-1/8W(0805)"))
    )
    (comp (ref "R48")
      (value "2201")
      (footprint "eagle-import:R0805")
      (fields (field (name "MPN") "RC0805JR-072K2L"))
      (libsource (lib "eagle-import") (part "SMD-RES-2.2K-5%-1/8W(0805)"))
    )
    (comp (ref "R49")
      (value "1002")
      (footprint "eagle-import:R0805")
      (fields (field (name "MPN") "RC0805JR-074K7L"))
      (libsource (lib "eagle-import") (part "SMD-RES-4.7K-5%-1/8W(0805)"))
    )
    (comp (ref "R50")
      (value "1002")
      (footprint "eagle-import:R0805")
      (fields (field (name "MPN") "RC0805FR-0710KL"))
      (libsource (lib "eagle-import") (part "SMD-RES-10K-1%-1/8W(0805)"))
    )
    (comp (ref "R51")
      (value "102")
      (footprint "eagle-import:R0805")
      (fields (field (name "MPN") "RC0805JR-071KL"))
      (libsource (lib "eagle-import") (part "SMD-RES-1K-5%-1/8W(0805)"))
    )
    (comp (ref "R52")
      (value "2702")
      (footprint "eagle-import:R0805")
      (fields (field (name "MPN") "RC0805JR-074K7L"))
      (libsource (lib "eagle-import") (part "SMD-RES-4.7K-5%-1/8W(0805)"))
    )
    (comp (ref "R53")
      (value "1002")
      (footprint "eagle-import:R0805")
      (fields (field (name "MPN") "RC0805JR-071KL"))
      (libsource (lib "eagle-import") (part "SMD-RES-1K-5%-1/8W(0805)"))
    )
    (comp (ref "R54")
      (value "1002")
      (footprint "eagle-import:R0805")
      (fields (field (name "MPN") "RC0805JR-071KL"))
      (libsource (lib "eagle-import") (part "SMD-RES-1K-5%-1/8W(0805)"))
    )
    (comp (ref "R55")
      (value "R_user")
      (footprint "eagle-import:R0805")
      (libsource (lib "eagle-import") (part "R-EU_R0805"))
    )
    (comp (ref "R56")
      (value "104")
      (footprint "eagle-import:R0805")
      (fields (field (name "MPN") "RC0805FR-0710KL"))
      (libsource (lib "eagle-import") (part "SMD-RES-10K-1%-1/8W(0805)"))
    )
    (comp (ref "R57")
      (value "104")
      (footprint "eagle-import:R0805")
      (fields (field (name "MPN") "RC0805FR-0710KL"))
      (libsource (lib "eagle-import") (part "SMD-RES-10K-1%-1/8W(0805)"))
    )
    (comp (ref "R58")
      (value "104")
      (footprint "eagle-import:R0805")
      (fields (field (name "MPN") "RC0805FR-0710KL"))
      (libsource (lib "eagle-import") (part "SMD-RES-10K-1%-1/8W(0805)"))
    )
    (comp (ref "R59")
      (value "13")
      (footprint "eagle-import:R1206")
      (fields (field (name "MPN") "RC1206JR-0713RL"))
      (libsource (lib "eagle-import") (part "SMD-RES-13R-5%-1/4W(1206)"))
    )
    (comp (ref "R60")
      (value "2201")
      (footprint "eagle-import:R0805")
      (fields (field (name "MPN") "RC0805JR-071KL"))
      (libsource (lib "eagle-import") (part "SMD-RES-1K-5%-1/8W(0805)"))
    )
    (comp (ref "R61")
      (value "100")
      (footprint "eagle-import:R0805")
      (fields (field (name "MPN") "RC0805JR-07220RL"))
      (libsource (lib "eagle-import") (part "SMD-RES-220R-5%-1/8W(0805)"))
    )
    (comp (ref "R62")
      (value "13")
      (footprint "eagle-import:R1206")
      (fields (field (name "MPN") "RC1206JR-0713RL"))
      (libsource (lib "eagle-import") (part "SMD-RES-13R-5%-1/4W(1206)"))
    )
    (comp (ref "R63")
      (value "4701")
      (footprint "eagle-import:R0805")
      (fields (field (name "MPN") "RC0805JR-074K7L"))
      (libsource (lib "eagle-import") (part "SMD-RES-4.7K-5%-1/8W(0805)"))
    )
    (comp (ref "R64")
      (value "104")
      (footprint "eagle-import:R0805")
      (fields (field (name "MPN") "RC0805JR-074K7L"))
      (libsource (lib "eagle-import") (part "SMD-RES-4.7K-5%-1/8W(0805)"))
    )
    (comp (ref "R65")
      (value "100")
      (footprint "eagle-import:R0805")
      (fields (field (name "MPN") "RC0805JR-072K2L"))
      (libsource (lib "eagle-import") (part "SMD-RES-2.2K-5%-1/8W(0805)"))
    )
    (comp (ref "R66")
      (value "100")
      (footprint "eagle-import:R0805")
      (fields (field (name "MPN") "RC0805JR-072K2L"))
      (libsource (lib "eagle-import") (part "SMD-RES-2.2K-5%-1/8W(0805)"))
    )
    (comp (ref "SJMP1")
      (value "SJ")
      (footprint "eagle-import:SJ")
      (libsource (lib "eagle-import") (part "SJ"))
    )
    (comp (ref "START1")
      (value "TPSB2.0")
      (footprint "eagle-import:B2.0")
      (libsource (lib "eagle-import") (part "TPSB2.0"))
    )
    (comp (ref "TP14")
      (value "TPSB2.0")
      (footprint "eagle-import:B2.0")
      (libsource (lib "eagle-import") (part "TPSB2.0"))
    )
    (comp (ref "TP15")
      (value "TPSB2.0")
      (footprint "eagle-import:B2.0")
      (libsource (lib "eagle-import") (part "TPSB2.0"))
    )
    (comp (ref "TP20")
      (value "TPSB2.0")
      (footprint "eagle-import:B2.0")
      (libsource (lib "eagle-import") (part "TPSB2.0"))
    )
    (comp (ref "TP27")
      (value "TPSB2.0")
      (footprint "eagle-import:B2.0")
      (libsource (lib "eagle-import") (part "TPSB2.0"))
    )
    (comp (ref "TP28")
      (value "TPSB2.0")
      (footprint "eagle-import:B2.0")
      (libsource (lib "eagle-import") (part "TPSB2.0"))
    )
    (comp (ref "TP29")
      (value "TPSB2.0")
      (footprint "eagle-import:B2.0")
      (libsource (lib "eagle-import") (part "TPSB2.0"))
    )
    (comp (ref "TP30")
      (value "TPSB2.0")
      (footprint "eagle-import:B2.0")
      (libsource (lib "eagle-import") (part "TPSB2.0"))
    )
    (comp (ref "TP31")
      (value "TPSB2.0")
      (footprint "eagle-import:B2.0")
      (libsource (lib "eagle-import") (part "TPSB2.0"))
    )
    (comp (ref "TP32")
      (value "TPSB2.0")
      (footprint "eagle-import:B2.0")
      (libsource (lib "eagle-import") (part "TPSB2.0"))
    )
    (comp (ref "TP33")
      (value "TPSB2.0")
      (footprint "eagle-import:B2.0")
      (libsource (lib "eagle-import") (part "TPSB2.0"))
    )
    (comp (ref "TP34")
      (value "TPSB2.0")
      (footprint "eagle-import:B2.0")
      (libsource (lib "eagle-import") (part "TPSB2.0"))
    )
    (comp (ref "TP35")
      (value "TPSB2.0")
      (footprint "eagle-import:B2.0")
      (libsource (lib "eagle-import") (part "TPSB2.0"))
    )
    (comp (ref "TP36")
      (value "TPSB2.0")
      (footprint "eagle-import:B2.0")
      (libsource (lib "eagle-import") (part "TPSB2.0"))
    )
    (comp (ref "TP37")
      (value "TPSB2.0")
      (footprint "eagle-import:B2.0")
      (libsource (lib "eagle-import") (part "TPSB2.0"))
    )
    (comp (ref "TP38")
      (value "TPSB2.0")
      (footprint "eagle-import:B2.0")
      (libsource (lib "eagle-import") (part "TPSB2.0"))
    )
    (comp (ref "TP39")
      (value "TPSB2.0")
      (footprint "eagle-import:B2.0")
      (libsource (lib "eagle-import") (part "TPSB2.0"))
    )
    (comp (ref "TP40")
      (value "TPSB2.0")
      (footprint "eagle-import:B2.0")
      (libsource (lib "eagle-import") (part "TPSB2.0"))
    )
    (comp (ref "TP41")
      (value "TPSB2.0")
      (footprint "eagle-import:B2.0")
      (libsource (lib "eagle-import") (part "TPSB2.0"))
    )
    (comp (ref "TP42")
      (value "TPSB1,27")
      (footprint "eagle-import:B1,27")
      (libsource (lib "eagle-import") (part "TPSB1,27"))
    )
    (comp (ref "TP43")
      (value "TPSB2.0")
      (footprint "eagle-import:B2.0")
      (libsource (lib "eagle-import") (part "TPSB2.0"))
    )
    (comp (ref "TP44")
      (value "TPSB2.0")
      (footprint "eagle-import:B2.0")
      (libsource (lib "eagle-import") (part "TPSB2.0"))
    )
    (comp (ref "TP45")
      (value "TPSB2.0")
      (footprint "eagle-import:B2.0")
      (libsource (lib "eagle-import") (part "TPSB2.0"))
    )
    (comp (ref "TP46")
      (value "TPSB2.0")
      (footprint "eagle-import:B2.0")
      (libsource (lib "eagle-import") (part "TPSB2.0"))
    )
    (comp (ref "X1")
      (value "CON_BMWV2")
      (footprint "eagle-import:24-PIN_V2")
      (libsource (lib "eagle-import") (part "CON_BMWV2"))
    )
    (comp (ref "X2")
      (value "22-23-2051")
      (footprint "eagle-import:22-23-2051")
      (fields (field (name "MF") "MOLEX"))
      (libsource (lib "eagle-import") (part "22-23-2051"))
    )
    (comp (ref "X3")
      (value "22-23-2021")
      (footprint "eagle-import:22-23-2021")
      (fields (field (name "MF") "MOLEX"))
      (libsource (lib "eagle-import") (part "22-23-2021"))
    )
    (comp (ref "6V3")
      (value "TPSB2.0")
      (footprint "eagle-import:B2.0")
      (libsource (lib "eagle-import") (part "TPSB2.0"))
    )
    (comp (ref "7")
      (value "2081-1132")
      (footprint "eagle-import:12-PIN")
      (libsource (lib "eagle-import") (part "2081-1132"))
    )
    (comp (ref "8")
      (value "2081-1132")
      (footprint "eagle-import:12-PIN")
      (libsource (lib "eagle-import") (part "2081-1132"))
    )
    (comp (ref "10V3")
      (value "TPSB2.0")
      (footprint "eagle-import:B2.0")
      (libsource (lib "eagle-import") (part "TPSB2.0"))
    )
    (comp (ref "C27")
      (value "100u")
      (footprint "eagle-import:C1206")
      (fields (field (name "MPN") "GRM31CR60J107ME39L"))
      (libsource (lib "eagle-import") (part "CERAMIC-100UF-6.3V-20%-X5R(1206)"))
    )
    (comp (ref "C28")
      (value "100u")
      (footprint "eagle-import:C1206")
      (fields (field (name "MPN") "GRM31CR60J107ME39L"))
      (libsource (lib "eagle-import") (part "CERAMIC-100UF-6.3V-20%-X5R(1206)"))
    )
    (comp (ref "C29")
      (value "100nF,")
      (footprint "eagle-import:C0805")
      (fields (field (name "MPN") "CC0805KRX7R9BB104"))
      (libsource (lib "eagle-import") (part "CERAMIC-100NF-50V-10%-X7R(0805)"))
    )
    (comp (ref "C30")
      (value "4.7u")
      (footprint "eagle-import:C0805")
      (fields (field (name "MPN") "CC0805KKX5R8BB475"))
      (libsource (lib "eagle-import") (part "CERAMIC-4.7UF-25V-10%-X5R(0805)"))
    )
    (comp (ref "C31")
      (value "100nF.")
      (footprint "eagle-import:C0805")
      (fields (field (name "MPN") "CC0805KRX7R9BB104"))
      (libsource (lib "eagle-import") (part "CERAMIC-100NF-50V-10%-X7R(0805)"))
    )
    (comp (ref "C32")
      (value "100nF.")
      (footprint "eagle-import:C0805")
      (fields (field (name "MPN") "CC0805KRX7R9BB104"))
      (libsource (lib "eagle-import") (part "CERAMIC-100NF-50V-10%-X7R(0805)"))
    )
    (comp (ref "C33")
      (value "2.2nF")
      (footprint "eagle-import:C0805")
      (fields (field (name "MPN") "CC0805KRX7R9BB104"))
      (libsource (lib "eagle-import") (part "CERAMIC-100NF-50V-10%-X7R(0805)"))
    )
    (comp (ref "C34")
      (value "100nF")
      (footprint "eagle-import:C0805")
      (fields (field (name "MPN") "CC0805KRX7R9BB104"))
      (libsource (lib "eagle-import") (part "CERAMIC-100NF-50V-10%-X7R(0805)"))
    )
    (comp (ref "C35")
      (value "100nF")
      (footprint "eagle-import:C0805")
      (fields (field (name "MPN") "CC0805KRX7R9BB104"))
      (libsource (lib "eagle-import") (part "CERAMIC-100NF-50V-10%-X7R(0805)"))
    )
    (comp (ref "C36")
      (value "100nF,")
      (footprint "eagle-import:C0805")
      (fields (field (name "MPN") "CC0805KRX7R9BB104"))
      (libsource (lib "eagle-import") (part "CERAMIC-100NF-50V-10%-X7R(0805)"))
    )
    (comp (ref "C37")
      (value "4.7u")
      (footprint "eagle-import:C0805")
      (fields (field (name "MPN") "CC0805KKX5R8BB475"))
      (libsource (lib "eagle-import") (part "CERAMIC-4.7UF-25V-10%-X5R(0805)"))
    )
    (comp (ref "C38")
      (value "10u")
      (footprint "eagle-import:C1206")
      (fields (field (name "MPN") "GRM31CR60J107ME39L"))
      (libsource (lib "eagle-import") (part "CERAMIC-100UF-6.3V-20%-X5R(1206)"))
    )
    (comp (ref "D32")
      (value "1N4007,")
      (footprint "eagle-import:DO-214AC")
      (fields (field (name "MPN") "1N4007"))
      (libsource (lib "eagle-import") (part "DIODE-GEN-PURPOSE-1KV-1A(DO-214AC)"))
    )
    (comp (ref "D33")
      (value "1N4007,")
      (footprint "eagle-import:DO-214AC")
      (fields (field (name "MPN") "1N4007"))
      (libsource (lib "eagle-import") (part "DIODE-GEN-PURPOSE-1KV-1A(DO-214AC)"))
    )
    (comp (ref "D34")
      (value "1N4007.")
      (footprint "eagle-import:DO-214AC")
      (fields (field (name "MPN") "1N4007"))
      (libsource (lib "eagle-import") (part "DIODE-GEN-PURPOSE-1KV-1A(DO-214AC)"))
    )
    (comp (ref "D35")
      (value "1N5817")
      (footprint "eagle-import:DO-214AC_SLIM")
      (libsource (lib "eagle-import") (part "DIODE-GEN-PURPOSE-1KV-1A(DO-214AC)DO-214AC/1206"))
    )
    (comp (ref "D36")
      (value "1N5817.")
      (footprint "eagle-import:DO-214AC_SLIM")
      (libsource (lib "eagle-import") (part "DIODE-GEN-PURPOSE-1KV-1A(DO-214AC)DO-214AC/1206"))
    )
    (comp (ref "D37")
      (value "1N5817.")
      (footprint "eagle-import:DO-214AC_SLIM")
      (libsource (lib "eagle-import") (part "DIODE-GEN-PURPOSE-1KV-1A(DO-214AC)DO-214AC/1206"))
    )
    (comp (ref "D38")
      (value "1N5817")
      (footprint "eagle-import:DO-214AC_SLIM")
      (libsource (lib "eagle-import") (part "DIODE-GEN-PURPOSE-1KV-1A(DO-214AC)DO-214AC/1206"))
    )
    (comp (ref "D39")
      (value "1N4007.")
      (footprint "eagle-import:DO-214AC")
      (fields (field (name "MPN") "1N4007"))
      (libsource (lib "eagle-import") (part "DIODE-GEN-PURPOSE-1KV-1A(DO-214AC)"))
    )
    (comp (ref "D40")
      (value "1N4007")
      (footprint "eagle-import:DO-214AC")
      (libsource (lib "eagle-import") (part "DIODE-GEN-PURPOSE-1KV-1A(DO-214AC)"))
    )
    (comp (ref "D41")
      (value "Zen15")
      (footprint "eagle-import:DO214AA")
      (libsource (lib "eagle-import") (part "SM6T"))
    )
    (comp (ref "D43")
      (value "SS12")
      (footprint "eagle-import:DO-214AC_SLIM")
      (libsource (lib "eagle-import") (part "DIODE-GEN-PURPOSE-1KV-1A(DO-214AC)DO-214AC/1206"))
    )
    (comp (ref "D44")
      (value "SS12")
      (footprint "eagle-import:DO-214AC_SLIM")
      (libsource (lib "eagle-import") (part "DIODE-GEN-PURPOSE-1KV-1A(DO-214AC)DO-214AC/1206"))
    )
    (comp (ref "D45")
      (value "Zen11")
      (footprint "eagle-import:SOD-123_MINI-SMA")
      (libsource (lib "eagle-import") (part "CGRM400-G1"))
    )
    (comp (ref "FID11")
      (value "FIDUCIAL")
      (footprint "eagle-import:FIDUCIAL_1MM")
      (libsource (lib "eagle-import") (part "FIDUCIAL"))
    )
    (comp (ref "FID12")
      (value "FIDUCIAL")
      (footprint "eagle-import:FIDUCIAL_1MM")
      (libsource (lib "eagle-import") (part "FIDUCIAL"))
    )
    (comp (ref "FID13")
      (value "FIDUCIAL")
      (footprint "eagle-import:FIDUCIAL_1MM")
      (libsource (lib "eagle-import") (part "FIDUCIAL"))
    )
    (comp (ref "FID14")
      (value "FIDUCIAL")
      (footprint "eagle-import:FIDUCIAL_1MM")
      (libsource (lib "eagle-import") (part "FIDUCIAL"))
    )
    (comp (ref "IC19")
      (value "4028")
      (footprint "eagle-import:SO16")
      (libsource (lib "eagle-import") (part "4028D"))
    )
    (comp (ref "IC20")
      (value "317TO202H_NOHOLE")
      (footprint "eagle-import:TO220H_NOHOLE")
      (libsource (lib "eagle-import") (part "317TO202H_NOHOLE"))
    )
    (comp (ref "IC21")
      (value "ULN2004")
      (footprint "eagle-import:SO16")
      (libsource (lib "eagle-import") (part "ULN2004AD"))
    )
    (comp (ref "IC22")
      (value "LM339")
      (footprint "eagle-import:SO14")
      (libsource (lib "eagle-import") (part "LM339D"))
    )
    (comp (ref "IC23")
      (value "78L06")
      (footprint "eagle-import:SOT89_ROUND")
      (libsource (lib "eagle-import") (part "78LXXSOT89_ROUND"))
    )
    (comp (ref "IC24")
      (value "555")
      (footprint "eagle-import:SO08")
      (libsource (lib "eagle-import") (part "555DNE"))
    )
    (comp (ref "IC25")
      (value "4538")
      (footprint "eagle-import:SO16")
      (libsource (lib "eagle-import") (part "4538D"))
    )
    (comp (ref "IC26")
      (value "78L10")
      (footprint "eagle-import:SOT89_ROUND")
      (libsource (lib "eagle-import") (part "78LXXSOT89_ROUND"))
    )
    (comp (ref "IC27")
      (value "LM2904")
      (footprint "eagle-import:SO08")
      (libsource (lib "eagle-import") (part "LM358D"))
    )
    (comp (ref "JP11")
      (value "JP2EJP2_SMALLPADS")
      (footprint "eagle-import:JP2_SMALLPADS")
      (libsource (lib "eagle-import") (part "JP2EJP2_SMALLPADS"))
    )
    (comp (ref "JP12")
      (value "JP2E_ORIG")
      (footprint "eagle-import:JP2_ORIG_SMALLPADS")
      (libsource (lib "eagle-import") (part "JP2E_ORIG"))
    )
    (comp (ref "JP13")
      (value "JP2EJP2_SMALLPADS")
      (footprint "eagle-import:JP2_SMALLPADS")
      (libsource (lib "eagle-import") (part "JP2EJP2_SMALLPADS"))
    )
    (comp (ref "JP14")
      (value "JP2EJP2_SMALLPADS")
      (footprint "eagle-import:JP2_SMALLPADS")
      (libsource (lib "eagle-import") (part "JP2EJP2_SMALLPADS"))
    )
    (comp (ref "JP15")
      (value "JP2EJP2_SMALLPADS")
      (footprint "eagle-import:JP2_SMALLPADS")
      (libsource (lib "eagle-import") (part "JP2EJP2_SMALLPADS"))
    )
    (comp (ref "LED13")
      (value "LEDLD260")
      (footprint "eagle-import:LD260")
      (libsource (lib "eagle-import") (part "LEDLD260"))
    )
    (comp (ref "LED14")
      (value "LEDLD260")
      (footprint "eagle-import:LD260")
      (libsource (lib "eagle-import") (part "LEDLD260"))
    )
    (comp (ref "LED15")
      (value "LEDLD260")
      (footprint "eagle-import:LD260")
      (libsource (lib "eagle-import") (part "LEDLD260"))
    )
    (comp (ref "LED16")
      (value "LEDLD260")
      (footprint "eagle-import:LD260")
      (libsource (lib "eagle-import") (part "LEDLD260"))
    )
    (comp (ref "LED17")
      (value "LEDLD260")
      (footprint "eagle-import:LD260")
      (libsource (lib "eagle-import") (part "LEDLD260"))
    )
    (comp (ref "LED18")
      (value "LEDLD260")
      (footprint "eagle-import:LD260")
      (libsource (lib "eagle-import") (part "LEDLD260"))
    )
    (comp (ref "Q24")
      (value "BA")
      (footprint "eagle-import:SOT89")
      (libsource (lib "eagle-import") (part "PNP-TRANSISTOR_SOT89"))
    )
    (comp (ref "Q25")
      (value "BA.")
      (footprint "eagle-import:SOT89")
      (libsource (lib "eagle-import") (part "PNP-TRANSISTOR_SOT89"))
    )
    (comp (ref "Q26")
      (value "BA.")
      (footprint "eagle-import:SOT89")
      (libsource (lib "eagle-import") (part "PNP-TRANSISTOR_SOT89"))
    )
    (comp (ref "Q27")
      (value "BA")
      (footprint "eagle-import:SOT89")
      (libsource (lib "eagle-import") (part "PNP-TRANSISTOR_SOT89"))
    )
    (comp (ref "Q28")
      (value "MY")
      (footprint "eagle-import:SOT89")
      (libsource (lib "eagle-import") (part "NPN-TRANSISTOR_SOT89"))
    )
    (comp (ref "Q29")
      (value "J1")
      (footprint "eagle-import:SOT-23")
      (fields (field (name "MPN") "BSS138W-7-F"))
      (libsource (lib "eagle-import") (part "SMD-MOSFET-N-CH-50V-200MA-BSS138W-7-F(SOT-23)"))
    )
    (comp (ref "Q30")
      (value "J1")
      (footprint "eagle-import:SOT-23")
      (fields (field (name "MPN") "BSS138W-7-F"))
      (libsource (lib "eagle-import") (part "SMD-MOSFET-N-CH-50V-200MA-BSS138W-7-F(SOT-23)"))
    )
    (comp (ref "Q31")
      (value "J1")
      (footprint "eagle-import:SOT-23")
      (fields (field (name "MPN") "BSS138W-7-F"))
      (libsource (lib "eagle-import") (part "SMD-MOSFET-N-CH-50V-200MA-BSS138W-7-F(SOT-23)"))
    )
    (comp (ref "Q32")
      (value "BA")
      (footprint "eagle-import:SOT89")
      (libsource (lib "eagle-import") (part "PNP-TRANSISTOR_SOT89"))
    )
    (comp (ref "Q33")
      (value "J1")
      (footprint "eagle-import:SOT-23")
      (fields (field (name "MPN") "BSS138W-7-F"))
      (libsource (lib "eagle-import") (part "SMD-MOSFET-N-CH-50V-200MA-BSS138W-7-F(SOT-23)"))
    )
    (comp (ref "R166")
      (value "47")
      (footprint "eagle-import:V235_17_1MM")
      (libsource (lib "eagle-import") (part "R-EU_V235/17_1MM"))
    )
    (comp (ref "R167")
      (value "13")
      (footprint "eagle-import:R1206")
      (fields (field (name "MPN") "RC1206JR-0713RL"))
      (libsource (lib "eagle-import") (part "SMD-RES-13R-5%-1/4W(1206)"))
    )
    (comp (ref "R168")
      (value "47")
      (footprint "eagle-import:V235_17_1MM")
      (libsource (lib "eagle-import") (part "R-EU_V235/17_1MM"))
    )
    (comp (ref "R169")
      (value "104")
      (footprint "eagle-import:R0805")
      (fields (field (name "MPN") "RC0805FR-0710KL"))
      (libsource (lib "eagle-import") (part "SMD-RES-10K-1%-1/8W(0805)"))
    )
    (comp (ref "R170")
      (value "104")
      (footprint "eagle-import:R0805")
      (fields (field (name "MPN") "RC0805FR-0710KL"))
      (libsource (lib "eagle-import") (part "SMD-RES-10K-1%-1/8W(0805)"))
    )
    (comp (ref "R171")
      (value "104")
      (footprint "eagle-import:R0805")
      (fields (field (name "MPN") "RC0805FR-0710KL"))
      (libsource (lib "eagle-import") (part "SMD-RES-10K-1%-1/8W(0805)"))
    )
    (comp (ref "R172")
      (value "4701")
      (footprint "eagle-import:R0805")
      (fields (field (name "MPN") "RC0805JR-074K7L"))
      (libsource (lib "eagle-import") (part "SMD-RES-4.7K-5%-1/8W(0805)"))
    )
    (comp (ref "R173")
      (value "1002")
      (footprint "eagle-import:R0805")
      (fields (field (name "MPN") "RC0805FR-0710KL"))
      (libsource (lib "eagle-import") (part "SMD-RES-10K-1%-1/8W(0805)"))
    )
    (comp (ref "R174")
      (value "1002")
      (footprint "eagle-import:R0805")
      (fields (field (name "MPN") "RC0805FR-0710KL"))
      (libsource (lib "eagle-import") (part "SMD-RES-10K-1%-1/8W(0805)"))
    )
    (comp (ref "R175")
      (value "1502")
      (footprint "eagle-import:R0805")
      (fields (field (name "MPN") "RC0805FR-0710KL"))
      (libsource (lib "eagle-import") (part "SMD-RES-10K-1%-1/8W(0805)"))
    )
    (comp (ref "R176")
      (value "104")
      (footprint "eagle-import:R0805")
      (fields (field (name "MPN") "RC0805FR-0710KL"))
      (libsource (lib "eagle-import") (part "SMD-RES-10K-1%-1/8W(0805)"))
    )
    (comp (ref "R177")
      (value "104")
      (footprint "eagle-import:R0805")
      (fields (field (name "MPN") "RC0805FR-0710KL"))
      (libsource (lib "eagle-import") (part "SMD-RES-10K-1%-1/8W(0805)"))
    )
    (comp (ref "R178")
      (value "1502")
      (footprint "eagle-import:R0805")
      (fields (field (name "MPN") "RC0805FR-0710KL"))
      (libsource (lib "eagle-import") (part "SMD-RES-10K-1%-1/8W(0805)"))
    )
    (comp (ref "R179")
      (value "1002")
      (footprint "eagle-import:R0805")
      (fields (field (name "MPN") "RC0805FR-0710KL"))
      (libsource (lib "eagle-import") (part "SMD-RES-10K-1%-1/8W(0805)"))
    )
    (comp (ref "R180")
      (value "2201")
      (footprint "eagle-import:R0805")
      (fields (field (name "MPN") "RC0805JR-072K2L"))
      (libsource (lib "eagle-import") (part "SMD-RES-2.2K-5%-1/8W(0805)"))
    )
    (comp (ref "R181")
      (value "1002")
      (footprint "eagle-import:R0805")
      (fields (field (name "MPN") "RC0805FR-0710KL"))
      (libsource (lib "eagle-import") (part "SMD-RES-10K-1%-1/8W(0805)"))
    )
    (comp (ref "R182")
      (value "4701")
      (footprint "eagle-import:R0805")
      (fields (field (name "MPN") "RC0805JR-074K7L"))
      (libsource (lib "eagle-import") (part "SMD-RES-4.7K-5%-1/8W(0805)"))
    )
    (comp (ref "R183")
      (value "2702")
      (footprint "eagle-import:R0805")
      (fields (field (name "MPN") "RC0805JR-074K7L"))
      (libsource (lib "eagle-import") (part "SMD-RES-4.7K-5%-1/8W(0805)"))
    )
    (comp (ref "R184")
      (value "102")
      (footprint "eagle-import:R0805")
      (fields (field (name "MPN") "RC0805JR-071KL"))
      (libsource (lib "eagle-import") (part "SMD-RES-1K-5%-1/8W(0805)"))
    )
    (comp (ref "R186")
      (value "102")
      (footprint "eagle-import:R0805")
      (fields (field (name "MPN") "RC0805JR-07220RL"))
      (libsource (lib "eagle-import") (part "SMD-RES-220R-5%-1/8W(0805)"))
    )
    (comp (ref "R189")
      (value "102")
      (footprint "eagle-import:R0805")
      (fields (field (name "MPN") "RC0805JR-071KL"))
      (libsource (lib "eagle-import") (part "SMD-RES-1K-5%-1/8W(0805)"))
    )
    (comp (ref "R190")
      (value "13")
      (footprint "eagle-import:R1206")
      (fields (field (name "MPN") "RC1206JR-0713RL"))
      (libsource (lib "eagle-import") (part "SMD-RES-13R-5%-1/4W(1206)"))
    )
    (comp (ref "R191")
      (value "13")
      (footprint "eagle-import:R1206")
      (fields (field (name "MPN") "RC1206JR-0713RL"))
      (libsource (lib "eagle-import") (part "SMD-RES-13R-5%-1/4W(1206)"))
    )
    (comp (ref "R192")
      (value "2702")
      (footprint "eagle-import:R0805")
      (fields (field (name "MPN") "RC0805JR-074K7L"))
      (libsource (lib "eagle-import") (part "SMD-RES-4.7K-5%-1/8W(0805)"))
    )
    (comp (ref "R193")
      (value "4701")
      (footprint "eagle-import:R0805")
      (fields (field (name "MPN") "RC0805JR-074K7L"))
      (libsource (lib "eagle-import") (part "SMD-RES-4.7K-5%-1/8W(0805)"))
    )
    (comp (ref "R194")
      (value "100")
      (footprint "eagle-import:R0805")
      (fields (field (name "MPN") "RC0805JR-072K2L"))
      (libsource (lib "eagle-import") (part "SMD-RES-2.2K-5%-1/8W(0805)"))
    )
    (comp (ref "R195")
      (value "104")
      (footprint "eagle-import:R0805")
      (fields (field (name "MPN") "RC0805FR-0710KL"))
      (libsource (lib "eagle-import") (part "SMD-RES-10K-1%-1/8W(0805)"))
    )
    (comp (ref "R196")
      (value "104")
      (footprint "eagle-import:R0805")
      (fields (field (name "MPN") "RC0805FR-0710KL"))
      (libsource (lib "eagle-import") (part "SMD-RES-10K-1%-1/8W(0805)"))
    )
    (comp (ref "R198")
      (value "2702")
      (footprint "eagle-import:R0805")
      (fields (field (name "MPN") "RC0805FR-0710KL"))
      (libsource (lib "eagle-import") (part "SMD-RES-10K-1%-1/8W(0805)"))
    )
    (comp (ref "R199")
      (value "47")
      (footprint "eagle-import:V235_17_1MM")
      (libsource (lib "eagle-import") (part "R-EU_V235/17_1MM"))
    )
    (comp (ref "R200")
      (value "47")
      (footprint "eagle-import:V235_17_1MM")
      (libsource (lib "eagle-import") (part "R-EU_V235/17_1MM"))
    )
    (comp (ref "R201")
      (value "2702")
      (footprint "eagle-import:R0805")
      (fields (field (name "MPN") "RC0805JR-074K7L"))
      (libsource (lib "eagle-import") (part "SMD-RES-4.7K-5%-1/8W(0805)"))
    )
    (comp (ref "R202")
      (value "2201")
      (footprint "eagle-import:R0805")
      (fields (field (name "MPN") "RC0805JR-072K2L"))
      (libsource (lib "eagle-import") (part "SMD-RES-2.2K-5%-1/8W(0805)"))
    )
    (comp (ref "R203")
      (value "1002")
      (footprint "eagle-import:R0805")
      (fields (field (name "MPN") "RC0805JR-074K7L"))
      (libsource (lib "eagle-import") (part "SMD-RES-4.7K-5%-1/8W(0805)"))
    )
    (comp (ref "R204")
      (value "1002")
      (footprint "eagle-import:R0805")
      (fields (field (name "MPN") "RC0805FR-0710KL"))
      (libsource (lib "eagle-import") (part "SMD-RES-10K-1%-1/8W(0805)"))
    )
    (comp (ref "R205")
      (value "102")
      (footprint "eagle-import:R0805")
      (fields (field (name "MPN") "RC0805JR-071KL"))
      (libsource (lib "eagle-import") (part "SMD-RES-1K-5%-1/8W(0805)"))
    )
    (comp (ref "R206")
      (value "2702")
      (footprint "eagle-import:R0805")
      (fields (field (name "MPN") "RC0805JR-074K7L"))
      (libsource (lib "eagle-import") (part "SMD-RES-4.7K-5%-1/8W(0805)"))
    )
    (comp (ref "R207")
      (value "1002")
      (footprint "eagle-import:R0805")
      (fields (field (name "MPN") "RC0805JR-071KL"))
      (libsource (lib "eagle-import") (part "SMD-RES-1K-5%-1/8W(0805)"))
    )
    (comp (ref "R208")
      (value "1002")
      (footprint "eagle-import:R0805")
      (fields (field (name "MPN") "RC0805JR-071KL"))
      (libsource (lib "eagle-import") (part "SMD-RES-1K-5%-1/8W(0805)"))
    )
    (comp (ref "R209")
      (value "R_user")
      (footprint "eagle-import:R0805")
      (libsource (lib "eagle-import") (part "R-EU_R0805"))
    )
    (comp (ref "R210")
      (value "104")
      (footprint "eagle-import:R0805")
      (fields (field (name "MPN") "RC0805FR-0710KL"))
      (libsource (lib "eagle-import") (part "SMD-RES-10K-1%-1/8W(0805)"))
    )
    (comp (ref "R211")
      (value "104")
      (footprint "eagle-import:R0805")
      (fields (field (name "MPN") "RC0805FR-0710KL"))
      (libsource (lib "eagle-import") (part "SMD-RES-10K-1%-1/8W(0805)"))
    )
    (comp (ref "R212")
      (value "104")
      (footprint "eagle-import:R0805")
      (fields (field (name "MPN") "RC0805FR-0710KL"))
      (libsource (lib "eagle-import") (part "SMD-RES-10K-1%-1/8W(0805)"))
    )
    (comp (ref "R213")
      (value "13")
      (footprint "eagle-import:R1206")
      (fields (field (name "MPN") "RC1206JR-0713RL"))
      (libsource (lib "eagle-import") (part "SMD-RES-13R-5%-1/4W(1206)"))
    )
    (comp (ref "R214")
      (value "2201")
      (footprint "eagle-import:R0805")
      (fields (field (name "MPN") "RC0805JR-071KL"))
      (libsource (lib "eagle-import") (part "SMD-RES-1K-5%-1/8W(0805)"))
    )
    (comp (ref "R215")
      (value "100")
      (footprint "eagle-import:R0805")
      (fields (field (name "MPN") "RC0805JR-07220RL"))
      (libsource (lib "eagle-import") (part "SMD-RES-220R-5%-1/8W(0805)"))
    )
    (comp (ref "R216")
      (value "13")
      (footprint "eagle-import:R1206")
      (fields (field (name "MPN") "RC1206JR-0713RL"))
      (libsource (lib "eagle-import") (part "SMD-RES-13R-5%-1/4W(1206)"))
    )
    (comp (ref "R217")
      (value "4701")
      (footprint "eagle-import:R0805")
      (fields (field (name "MPN") "RC0805JR-074K7L"))
      (libsource (lib "eagle-import") (part "SMD-RES-4.7K-5%-1/8W(0805)"))
    )
    (comp (ref "R218")
      (value "104")
      (footprint "eagle-import:R0805")
      (fields (field (name "MPN") "RC0805JR-074K7L"))
      (libsource (lib "eagle-import") (part "SMD-RES-4.7K-5%-1/8W(0805)"))
    )
    (comp (ref "R219")
      (value "100")
      (footprint "eagle-import:R0805")
      (fields (field (name "MPN") "RC0805JR-072K2L"))
      (libsource (lib "eagle-import") (part "SMD-RES-2.2K-5%-1/8W(0805)"))
    )
    (comp (ref "R220")
      (value "100")
      (footprint "eagle-import:R0805")
      (fields (field (name "MPN") "RC0805JR-072K2L"))
      (libsource (lib "eagle-import") (part "SMD-RES-2.2K-5%-1/8W(0805)"))
    )
    (comp (ref "SJMP3")
      (value "SJ")
      (footprint "eagle-import:SJ")
      (libsource (lib "eagle-import") (part "SJ"))
    )
    (comp (ref "START3")
      (value "TPSB2.0")
      (footprint "eagle-import:B2.0")
      (libsource (lib "eagle-import") (part "TPSB2.0"))
    )
    (comp (ref "TP70")
      (value "TPSB2.0")
      (footprint "eagle-import:B2.0")
      (libsource (lib "eagle-import") (part "TPSB2.0"))
    )
    (comp (ref "TP71")
      (value "TPSB2.0")
      (footprint "eagle-import:B2.0")
      (libsource (lib "eagle-import") (part "TPSB2.0"))
    )
    (comp (ref "TP72")
      (value "TPSB2.0")
      (footprint "eagle-import:B2.0")
      (libsource (lib "eagle-import") (part "TPSB2.0"))
    )
    (comp (ref "TP73")
      (value "TPSB2.0")
      (footprint "eagle-import:B2.0")
      (libsource (lib "eagle-import") (part "TPSB2.0"))
    )
    (comp (ref "TP74")
      (value "TPSB2.0")
      (footprint "eagle-import:B2.0")
      (libsource (lib "eagle-import") (part "TPSB2.0"))
    )
    (comp (ref "TP75")
      (value "TPSB2.0")
      (footprint "eagle-import:B2.0")
      (libsource (lib "eagle-import") (part "TPSB2.0"))
    )
    (comp (ref "TP76")
      (value "TPSB2.0")
      (footprint "eagle-import:B2.0")
      (libsource (lib "eagle-import") (part "TPSB2.0"))
    )
    (comp (ref "TP77")
      (value "TPSB2.0")
      (footprint "eagle-import:B2.0")
      (libsource (lib "eagle-import") (part "TPSB2.0"))
    )
    (comp (ref "TP78")
      (value "TPSB2.0")
      (footprint "eagle-import:B2.0")
      (libsource (lib "eagle-import") (part "TPSB2.0"))
    )
    (comp (ref "TP79")
      (value "TPSB2.0")
      (footprint "eagle-import:B2.0")
      (libsource (lib "eagle-import") (part "TPSB2.0"))
    )
    (comp (ref "TP80")
      (value "TPSB2.0")
      (footprint "eagle-import:B2.0")
      (libsource (lib "eagle-import") (part "TPSB2.0"))
    )
    (comp (ref "TP81")
      (value "TPSB2.0")
      (footprint "eagle-import:B2.0")
      (libsource (lib "eagle-import") (part "TPSB2.0"))
    )
    (comp (ref "TP82")
      (value "TPSB2.0")
      (footprint "eagle-import:B2.0")
      (libsource (lib "eagle-import") (part "TPSB2.0"))
    )
    (comp (ref "TP83")
      (value "TPSB2.0")
      (footprint "eagle-import:B2.0")
      (libsource (lib "eagle-import") (part "TPSB2.0"))
    )
    (comp (ref "TP84")
      (value "TPSB2.0")
      (footprint "eagle-import:B2.0")
      (libsource (lib "eagle-import") (part "TPSB2.0"))
    )
    (comp (ref "TP85")
      (value "TPSB2.0")
      (footprint "eagle-import:B2.0")
      (libsource (lib "eagle-import") (part "TPSB2.0"))
    )
    (comp (ref "TP86")
      (value "TPSB2.0")
      (footprint "eagle-import:B2.0")
      (libsource (lib "eagle-import") (part "TPSB2.0"))
    )
    (comp (ref "TP87")
      (value "TPSB2.0")
      (footprint "eagle-import:B2.0")
      (libsource (lib "eagle-import") (part "TPSB2.0"))
    )
    (comp (ref "TP88")
      (value "TPSB1,27")
      (footprint "eagle-import:B1,27")
      (libsource (lib "eagle-import") (part "TPSB1,27"))
    )
    (comp (ref "TP89")
      (value "TPSB2.0")
      (footprint "eagle-import:B2.0")
      (libsource (lib "eagle-import") (part "TPSB2.0"))
    )
    (comp (ref "TP90")
      (value "TPSB2.0")
      (footprint "eagle-import:B2.0")
      (libsource (lib "eagle-import") (part "TPSB2.0"))
    )
    (comp (ref "TP91")
      (value "TPSB2.0")
      (footprint "eagle-import:B2.0")
      (libsource (lib "eagle-import") (part "TPSB2.0"))
    )
    (comp (ref "TP92")
      (value "TPSB2.0")
      (footprint "eagle-import:B2.0")
      (libsource (lib "eagle-import") (part "TPSB2.0"))
    )
    (comp (ref "X7")
      (value "CON_BMWV2")
      (footprint "eagle-import:24-PIN_V2")
      (libsource (lib "eagle-import") (part "CON_BMWV2"))
    )
    (comp (ref "X8")
      (value "22-23-2051")
      (footprint "eagle-import:22-23-2051")
      (fields (field (name "MF") "MOLEX"))
      (libsource (lib "eagle-import") (part "22-23-2051"))
    )
    (comp (ref "X9")
      (value "22-23-2021")
      (footprint "eagle-import:22-23-2021")
      (fields (field (name "MF") "MOLEX"))
      (libsource (lib "eagle-import") (part "22-23-2021"))
    )
    (comp (ref "6V9")
      (value "TPSB2.0")
      (footprint "eagle-import:B2.0")
      (libsource (lib "eagle-import") (part "TPSB2.0"))
    )
    (comp (ref "10V9")
      (value "TPSB2.0")
      (footprint "eagle-import:B2.0")
      (libsource (lib "eagle-import") (part "TPSB2.0"))
    )
    (comp (ref "19")
      (value "2081-1132")
      (footprint "eagle-import:12-PIN")
      (libsource (lib "eagle-import") (part "2081-1132"))
    )
    (comp (ref "20")
      (value "2081-1132")
      (footprint "eagle-import:12-PIN")
      (libsource (lib "eagle-import") (part "2081-1132"))
    )
    (comp (ref "C99")
      (value "100u")
      (footprint "eagle-import:C1206")
      (fields (field (name "MPN") "GRM31CR60J107ME39L"))
      (libsource (lib "eagle-import") (part "CERAMIC-100UF-6.3V-20%-X5R(1206)"))
    )
    (comp (ref "C100")
      (value "100u")
      (footprint "eagle-import:C1206")
      (fields (field (name "MPN") "GRM31CR60J107ME39L"))
      (libsource (lib "eagle-import") (part "CERAMIC-100UF-6.3V-20%-X5R(1206)"))
    )
    (comp (ref "C111")
      (value "100nF,")
      (footprint "eagle-import:C0805")
      (fields (field (name "MPN") "CC0805KRX7R9BB104"))
      (libsource (lib "eagle-import") (part "CERAMIC-100NF-50V-10%-X7R(0805)"))
    )
    (comp (ref "C112")
      (value "4.7u")
      (footprint "eagle-import:C0805")
      (fields (field (name "MPN") "CC0805KKX5R8BB475"))
      (libsource (lib "eagle-import") (part "CERAMIC-4.7UF-25V-10%-X5R(0805)"))
    )
    (comp (ref "C113")
      (value "100nF.")
      (footprint "eagle-import:C0805")
      (fields (field (name "MPN") "CC0805KRX7R9BB104"))
      (libsource (lib "eagle-import") (part "CERAMIC-100NF-50V-10%-X7R(0805)"))
    )
    (comp (ref "C114")
      (value "100nF.")
      (footprint "eagle-import:C0805")
      (fields (field (name "MPN") "CC0805KRX7R9BB104"))
      (libsource (lib "eagle-import") (part "CERAMIC-100NF-50V-10%-X7R(0805)"))
    )
    (comp (ref "C115")
      (value "2.2nF")
      (footprint "eagle-import:C0805")
      (fields (field (name "MPN") "CC0805KRX7R9BB104"))
      (libsource (lib "eagle-import") (part "CERAMIC-100NF-50V-10%-X7R(0805)"))
    )
    (comp (ref "C116")
      (value "100nF")
      (footprint "eagle-import:C0805")
      (fields (field (name "MPN") "CC0805KRX7R9BB104"))
      (libsource (lib "eagle-import") (part "CERAMIC-100NF-50V-10%-X7R(0805)"))
    )
    (comp (ref "C117")
      (value "100nF")
      (footprint "eagle-import:C0805")
      (fields (field (name "MPN") "CC0805KRX7R9BB104"))
      (libsource (lib "eagle-import") (part "CERAMIC-100NF-50V-10%-X7R(0805)"))
    )
    (comp (ref "C118")
      (value "100nF,")
      (footprint "eagle-import:C0805")
      (fields (field (name "MPN") "CC0805KRX7R9BB104"))
      (libsource (lib "eagle-import") (part "CERAMIC-100NF-50V-10%-X7R(0805)"))
    )
    (comp (ref "C119")
      (value "4.7u")
      (footprint "eagle-import:C0805")
      (fields (field (name "MPN") "CC0805KKX5R8BB475"))
      (libsource (lib "eagle-import") (part "CERAMIC-4.7UF-25V-10%-X5R(0805)"))
    )
    (comp (ref "C120")
      (value "10u")
      (footprint "eagle-import:C1206")
      (fields (field (name "MPN") "GRM31CR60J107ME39L"))
      (libsource (lib "eagle-import") (part "CERAMIC-100UF-6.3V-20%-X5R(1206)"))
    )
    (comp (ref "D118")
      (value "1N4007,")
      (footprint "eagle-import:DO-214AC")
      (fields (field (name "MPN") "1N4007"))
      (libsource (lib "eagle-import") (part "DIODE-GEN-PURPOSE-1KV-1A(DO-214AC)"))
    )
    (comp (ref "D119")
      (value "1N4007,")
      (footprint "eagle-import:DO-214AC")
      (fields (field (name "MPN") "1N4007"))
      (libsource (lib "eagle-import") (part "DIODE-GEN-PURPOSE-1KV-1A(DO-214AC)"))
    )
    (comp (ref "D120")
      (value "1N4007.")
      (footprint "eagle-import:DO-214AC")
      (fields (field (name "MPN") "1N4007"))
      (libsource (lib "eagle-import") (part "DIODE-GEN-PURPOSE-1KV-1A(DO-214AC)"))
    )
    (comp (ref "D121")
      (value "1N5817")
      (footprint "eagle-import:DO-214AC_SLIM")
      (libsource (lib "eagle-import") (part "DIODE-GEN-PURPOSE-1KV-1A(DO-214AC)DO-214AC/1206"))
    )
    (comp (ref "D122")
      (value "1N5817.")
      (footprint "eagle-import:DO-214AC_SLIM")
      (libsource (lib "eagle-import") (part "DIODE-GEN-PURPOSE-1KV-1A(DO-214AC)DO-214AC/1206"))
    )
    (comp (ref "D123")
      (value "1N5817.")
      (footprint "eagle-import:DO-214AC_SLIM")
      (libsource (lib "eagle-import") (part "DIODE-GEN-PURPOSE-1KV-1A(DO-214AC)DO-214AC/1206"))
    )
    (comp (ref "D124")
      (value "1N5817")
      (footprint "eagle-import:DO-214AC_SLIM")
      (libsource (lib "eagle-import") (part "DIODE-GEN-PURPOSE-1KV-1A(DO-214AC)DO-214AC/1206"))
    )
    (comp (ref "D125")
      (value "1N4007.")
      (footprint "eagle-import:DO-214AC")
      (fields (field (name "MPN") "1N4007"))
      (libsource (lib "eagle-import") (part "DIODE-GEN-PURPOSE-1KV-1A(DO-214AC)"))
    )
    (comp (ref "D126")
      (value "1N4007")
      (footprint "eagle-import:DO-214AC")
      (libsource (lib "eagle-import") (part "DIODE-GEN-PURPOSE-1KV-1A(DO-214AC)"))
    )
    (comp (ref "D127")
      (value "Zen15")
      (footprint "eagle-import:DO214AA")
      (libsource (lib "eagle-import") (part "SM6T"))
    )
    (comp (ref "D128")
      (value "SS12")
      (footprint "eagle-import:DO-214AC_SLIM")
      (libsource (lib "eagle-import") (part "DIODE-GEN-PURPOSE-1KV-1A(DO-214AC)DO-214AC/1206"))
    )
    (comp (ref "D129")
      (value "SS12")
      (footprint "eagle-import:DO-214AC_SLIM")
      (libsource (lib "eagle-import") (part "DIODE-GEN-PURPOSE-1KV-1A(DO-214AC)DO-214AC/1206"))
    )
    (comp (ref "D130")
      (value "Zen11")
      (footprint "eagle-import:SOD-123_MINI-SMA")
      (libsource (lib "eagle-import") (part "CGRM400-G1"))
    )
    (comp (ref "FID37")
      (value "FIDUCIAL")
      (footprint "eagle-import:FIDUCIAL_1MM")
      (libsource (lib "eagle-import") (part "FIDUCIAL"))
    )
    (comp (ref "FID38")
      (value "FIDUCIAL")
      (footprint "eagle-import:FIDUCIAL_1MM")
      (libsource (lib "eagle-import") (part "FIDUCIAL"))
    )
    (comp (ref "FID39")
      (value "FIDUCIAL")
      (footprint "eagle-import:FIDUCIAL_1MM")
      (libsource (lib "eagle-import") (part "FIDUCIAL"))
    )
    (comp (ref "FID40")
      (value "FIDUCIAL")
      (footprint "eagle-import:FIDUCIAL_1MM")
      (libsource (lib "eagle-import") (part "FIDUCIAL"))
    )
    (comp (ref "IC73")
      (value "4028")
      (footprint "eagle-import:SO16")
      (libsource (lib "eagle-import") (part "4028D"))
    )
    (comp (ref "IC74")
      (value "317TO202H_NOHOLE")
      (footprint "eagle-import:TO220H_NOHOLE")
      (libsource (lib "eagle-import") (part "317TO202H_NOHOLE"))
    )
    (comp (ref "IC75")
      (value "ULN2004")
      (footprint "eagle-import:SO16")
      (libsource (lib "eagle-import") (part "ULN2004AD"))
    )
    (comp (ref "IC76")
      (value "LM339")
      (footprint "eagle-import:SO14")
      (libsource (lib "eagle-import") (part "LM339D"))
    )
    (comp (ref "IC77")
      (value "78L06")
      (footprint "eagle-import:SOT89_ROUND")
      (libsource (lib "eagle-import") (part "78LXXSOT89_ROUND"))
    )
    (comp (ref "IC78")
      (value "555")
      (footprint "eagle-import:SO08")
      (libsource (lib "eagle-import") (part "555DNE"))
    )
    (comp (ref "IC79")
      (value "4538")
      (footprint "eagle-import:SO16")
      (libsource (lib "eagle-import") (part "4538D"))
    )
    (comp (ref "IC80")
      (value "78L10")
      (footprint "eagle-import:SOT89_ROUND")
      (libsource (lib "eagle-import") (part "78LXXSOT89_ROUND"))
    )
    (comp (ref "IC81")
      (value "LM2904")
      (footprint "eagle-import:SO08")
      (libsource (lib "eagle-import") (part "LM358D"))
    )
    (comp (ref "JP41")
      (value "JP2EJP2_SMALLPADS")
      (footprint "eagle-import:JP2_SMALLPADS")
      (libsource (lib "eagle-import") (part "JP2EJP2_SMALLPADS"))
    )
    (comp (ref "JP42")
      (value "JP2E_ORIG")
      (footprint "eagle-import:JP2_ORIG_SMALLPADS")
      (libsource (lib "eagle-import") (part "JP2E_ORIG"))
    )
    (comp (ref "JP43")
      (value "JP2EJP2_SMALLPADS")
      (footprint "eagle-import:JP2_SMALLPADS")
      (libsource (lib "eagle-import") (part "JP2EJP2_SMALLPADS"))
    )
    (comp (ref "JP44")
      (value "JP2EJP2_SMALLPADS")
      (footprint "eagle-import:JP2_SMALLPADS")
      (libsource (lib "eagle-import") (part "JP2EJP2_SMALLPADS"))
    )
    (comp (ref "JP45")
      (value "JP2EJP2_SMALLPADS")
      (footprint "eagle-import:JP2_SMALLPADS")
      (libsource (lib "eagle-import") (part "JP2EJP2_SMALLPADS"))
    )
    (comp (ref "LED49")
      (value "LEDLD260")
      (footprint "eagle-import:LD260")
      (libsource (lib "eagle-import") (part "LEDLD260"))
    )
    (comp (ref "LED50")
      (value "LEDLD260")
      (footprint "eagle-import:LD260")
      (libsource (lib "eagle-import") (part "LEDLD260"))
    )
    (comp (ref "LED51")
      (value "LEDLD260")
      (footprint "eagle-import:LD260")
      (libsource (lib "eagle-import") (part "LEDLD260"))
    )
    (comp (ref "LED52")
      (value "LEDLD260")
      (footprint "eagle-import:LD260")
      (libsource (lib "eagle-import") (part "LEDLD260"))
    )
    (comp (ref "LED53")
      (value "LEDLD260")
      (footprint "eagle-import:LD260")
      (libsource (lib "eagle-import") (part "LEDLD260"))
    )
    (comp (ref "LED54")
      (value "LEDLD260")
      (footprint "eagle-import:LD260")
      (libsource (lib "eagle-import") (part "LEDLD260"))
    )
    (comp (ref "Q84")
      (value "BA")
      (footprint "eagle-import:SOT89")
      (libsource (lib "eagle-import") (part "PNP-TRANSISTOR_SOT89"))
    )
    (comp (ref "Q85")
      (value "BA.")
      (footprint "eagle-import:SOT89")
      (libsource (lib "eagle-import") (part "PNP-TRANSISTOR_SOT89"))
    )
    (comp (ref "Q86")
      (value "BA.")
      (footprint "eagle-import:SOT89")
      (libsource (lib "eagle-import") (part "PNP-TRANSISTOR_SOT89"))
    )
    (comp (ref "Q87")
      (value "BA")
      (footprint "eagle-import:SOT89")
      (libsource (lib "eagle-import") (part "PNP-TRANSISTOR_SOT89"))
    )
    (comp (ref "Q88")
      (value "MY")
      (footprint "eagle-import:SOT89")
      (libsource (lib "eagle-import") (part "NPN-TRANSISTOR_SOT89"))
    )
    (comp (ref "Q89")
      (value "J1")
      (footprint "eagle-import:SOT-23")
      (fields (field (name "MPN") "BSS138W-7-F"))
      (libsource (lib "eagle-import") (part "SMD-MOSFET-N-CH-50V-200MA-BSS138W-7-F(SOT-23)"))
    )
    (comp (ref "Q90")
      (value "J1")
      (footprint "eagle-import:SOT-23")
      (fields (field (name "MPN") "BSS138W-7-F"))
      (libsource (lib "eagle-import") (part "SMD-MOSFET-N-CH-50V-200MA-BSS138W-7-F(SOT-23)"))
    )
    (comp (ref "Q91")
      (value "J1")
      (footprint "eagle-import:SOT-23")
      (fields (field (name "MPN") "BSS138W-7-F"))
      (libsource (lib "eagle-import") (part "SMD-MOSFET-N-CH-50V-200MA-BSS138W-7-F(SOT-23)"))
    )
    (comp (ref "Q92")
      (value "BA")
      (footprint "eagle-import:SOT89")
      (libsource (lib "eagle-import") (part "PNP-TRANSISTOR_SOT89"))
    )
    (comp (ref "Q93")
      (value "J1")
      (footprint "eagle-import:SOT-23")
      (fields (field (name "MPN") "BSS138W-7-F"))
      (libsource (lib "eagle-import") (part "SMD-MOSFET-N-CH-50V-200MA-BSS138W-7-F(SOT-23)"))
    )
    (comp (ref "R460")
      (value "47")
      (footprint "eagle-import:V235_17_1MM")
      (libsource (lib "eagle-import") (part "R-EU_V235/17_1MM"))
    )
    (comp (ref "R461")
      (value "13")
      (footprint "eagle-import:R1206")
      (fields (field (name "MPN") "RC1206JR-0713RL"))
      (libsource (lib "eagle-import") (part "SMD-RES-13R-5%-1/4W(1206)"))
    )
    (comp (ref "R462")
      (value "47")
      (footprint "eagle-import:V235_17_1MM")
      (libsource (lib "eagle-import") (part "R-EU_V235/17_1MM"))
    )
    (comp (ref "R463")
      (value "104")
      (footprint "eagle-import:R0805")
      (fields (field (name "MPN") "RC0805FR-0710KL"))
      (libsource (lib "eagle-import") (part "SMD-RES-10K-1%-1/8W(0805)"))
    )
    (comp (ref "R464")
      (value "104")
      (footprint "eagle-import:R0805")
      (fields (field (name "MPN") "RC0805FR-0710KL"))
      (libsource (lib "eagle-import") (part "SMD-RES-10K-1%-1/8W(0805)"))
    )
    (comp (ref "R465")
      (value "104")
      (footprint "eagle-import:R0805")
      (fields (field (name "MPN") "RC0805FR-0710KL"))
      (libsource (lib "eagle-import") (part "SMD-RES-10K-1%-1/8W(0805)"))
    )
    (comp (ref "R466")
      (value "4701")
      (footprint "eagle-import:R0805")
      (fields (field (name "MPN") "RC0805JR-074K7L"))
      (libsource (lib "eagle-import") (part "SMD-RES-4.7K-5%-1/8W(0805)"))
    )
    (comp (ref "R467")
      (value "1002")
      (footprint "eagle-import:R0805")
      (fields (field (name "MPN") "RC0805FR-0710KL"))
      (libsource (lib "eagle-import") (part "SMD-RES-10K-1%-1/8W(0805)"))
    )
    (comp (ref "R468")
      (value "1002")
      (footprint "eagle-import:R0805")
      (fields (field (name "MPN") "RC0805FR-0710KL"))
      (libsource (lib "eagle-import") (part "SMD-RES-10K-1%-1/8W(0805)"))
    )
    (comp (ref "R469")
      (value "1502")
      (footprint "eagle-import:R0805")
      (fields (field (name "MPN") "RC0805FR-0710KL"))
      (libsource (lib "eagle-import") (part "SMD-RES-10K-1%-1/8W(0805)"))
    )
    (comp (ref "R470")
      (value "104")
      (footprint "eagle-import:R0805")
      (fields (field (name "MPN") "RC0805FR-0710KL"))
      (libsource (lib "eagle-import") (part "SMD-RES-10K-1%-1/8W(0805)"))
    )
    (comp (ref "R471")
      (value "104")
      (footprint "eagle-import:R0805")
      (fields (field (name "MPN") "RC0805FR-0710KL"))
      (libsource (lib "eagle-import") (part "SMD-RES-10K-1%-1/8W(0805)"))
    )
    (comp (ref "R472")
      (value "1502")
      (footprint "eagle-import:R0805")
      (fields (field (name "MPN") "RC0805FR-0710KL"))
      (libsource (lib "eagle-import") (part "SMD-RES-10K-1%-1/8W(0805)"))
    )
    (comp (ref "R473")
      (value "1002")
      (footprint "eagle-import:R0805")
      (fields (field (name "MPN") "RC0805FR-0710KL"))
      (libsource (lib "eagle-import") (part "SMD-RES-10K-1%-1/8W(0805)"))
    )
    (comp (ref "R474")
      (value "2201")
      (footprint "eagle-import:R0805")
      (fields (field (name "MPN") "RC0805JR-072K2L"))
      (libsource (lib "eagle-import") (part "SMD-RES-2.2K-5%-1/8W(0805)"))
    )
    (comp (ref "R475")
      (value "1002")
      (footprint "eagle-import:R0805")
      (fields (field (name "MPN") "RC0805FR-0710KL"))
      (libsource (lib "eagle-import") (part "SMD-RES-10K-1%-1/8W(0805)"))
    )
    (comp (ref "R476")
      (value "4701")
      (footprint "eagle-import:R0805")
      (fields (field (name "MPN") "RC0805JR-074K7L"))
      (libsource (lib "eagle-import") (part "SMD-RES-4.7K-5%-1/8W(0805)"))
    )
    (comp (ref "R477")
      (value "2702")
      (footprint "eagle-import:R0805")
      (fields (field (name "MPN") "RC0805JR-074K7L"))
      (libsource (lib "eagle-import") (part "SMD-RES-4.7K-5%-1/8W(0805)"))
    )
    (comp (ref "R478")
      (value "102")
      (footprint "eagle-import:R0805")
      (fields (field (name "MPN") "RC0805JR-071KL"))
      (libsource (lib "eagle-import") (part "SMD-RES-1K-5%-1/8W(0805)"))
    )
    (comp (ref "R479")
      (value "102")
      (footprint "eagle-import:R0805")
      (fields (field (name "MPN") "RC0805JR-07220RL"))
      (libsource (lib "eagle-import") (part "SMD-RES-220R-5%-1/8W(0805)"))
    )
    (comp (ref "R480")
      (value "102")
      (footprint "eagle-import:R0805")
      (fields (field (name "MPN") "RC0805JR-071KL"))
      (libsource (lib "eagle-import") (part "SMD-RES-1K-5%-1/8W(0805)"))
    )
    (comp (ref "R481")
      (value "13")
      (footprint "eagle-import:R1206")
      (fields (field (name "MPN") "RC1206JR-0713RL"))
      (libsource (lib "eagle-import") (part "SMD-RES-13R-5%-1/4W(1206)"))
    )
    (comp (ref "R482")
      (value "13")
      (footprint "eagle-import:R1206")
      (fields (field (name "MPN") "RC1206JR-0713RL"))
      (libsource (lib "eagle-import") (part "SMD-RES-13R-5%-1/4W(1206)"))
    )
    (comp (ref "R483")
      (value "2702")
      (footprint "eagle-import:R0805")
      (fields (field (name "MPN") "RC0805JR-074K7L"))
      (libsource (lib "eagle-import") (part "SMD-RES-4.7K-5%-1/8W(0805)"))
    )
    (comp (ref "R484")
      (value "4701")
      (footprint "eagle-import:R0805")
      (fields (field (name "MPN") "RC0805JR-074K7L"))
      (libsource (lib "eagle-import") (part "SMD-RES-4.7K-5%-1/8W(0805)"))
    )
    (comp (ref "R485")
      (value "100")
      (footprint "eagle-import:R0805")
      (fields (field (name "MPN") "RC0805JR-072K2L"))
      (libsource (lib "eagle-import") (part "SMD-RES-2.2K-5%-1/8W(0805)"))
    )
    (comp (ref "R486")
      (value "104")
      (footprint "eagle-import:R0805")
      (fields (field (name "MPN") "RC0805FR-0710KL"))
      (libsource (lib "eagle-import") (part "SMD-RES-10K-1%-1/8W(0805)"))
    )
    (comp (ref "R487")
      (value "104")
      (footprint "eagle-import:R0805")
      (fields (field (name "MPN") "RC0805FR-0710KL"))
      (libsource (lib "eagle-import") (part "SMD-RES-10K-1%-1/8W(0805)"))
    )
    (comp (ref "R488")
      (value "2702")
      (footprint "eagle-import:R0805")
      (fields (field (name "MPN") "RC0805FR-0710KL"))
      (libsource (lib "eagle-import") (part "SMD-RES-10K-1%-1/8W(0805)"))
    )
    (comp (ref "R489")
      (value "47")
      (footprint "eagle-import:V235_17_1MM")
      (libsource (lib "eagle-import") (part "R-EU_V235/17_1MM"))
    )
    (comp (ref "R490")
      (value "47")
      (footprint "eagle-import:V235_17_1MM")
      (libsource (lib "eagle-import") (part "R-EU_V235/17_1MM"))
    )
    (comp (ref "R491")
      (value "2702")
      (footprint "eagle-import:R0805")
      (fields (field (name "MPN") "RC0805JR-074K7L"))
      (libsource (lib "eagle-import") (part "SMD-RES-4.7K-5%-1/8W(0805)"))
    )
    (comp (ref "R492")
      (value "2201")
      (footprint "eagle-import:R0805")
      (fields (field (name "MPN") "RC0805JR-072K2L"))
      (libsource (lib "eagle-import") (part "SMD-RES-2.2K-5%-1/8W(0805)"))
    )
    (comp (ref "R493")
      (value "1002")
      (footprint "eagle-import:R0805")
      (fields (field (name "MPN") "RC0805JR-074K7L"))
      (libsource (lib "eagle-import") (part "SMD-RES-4.7K-5%-1/8W(0805)"))
    )
    (comp (ref "R494")
      (value "1002")
      (footprint "eagle-import:R0805")
      (fields (field (name "MPN") "RC0805FR-0710KL"))
      (libsource (lib "eagle-import") (part "SMD-RES-10K-1%-1/8W(0805)"))
    )
    (comp (ref "R495")
      (value "102")
      (footprint "eagle-import:R0805")
      (fields (field (name "MPN") "RC0805JR-071KL"))
      (libsource (lib "eagle-import") (part "SMD-RES-1K-5%-1/8W(0805)"))
    )
    (comp (ref "R496")
      (value "2702")
      (footprint "eagle-import:R0805")
      (fields (field (name "MPN") "RC0805JR-074K7L"))
      (libsource (lib "eagle-import") (part "SMD-RES-4.7K-5%-1/8W(0805)"))
    )
    (comp (ref "R497")
      (value "1002")
      (footprint "eagle-import:R0805")
      (fields (field (name "MPN") "RC0805JR-071KL"))
      (libsource (lib "eagle-import") (part "SMD-RES-1K-5%-1/8W(0805)"))
    )
    (comp (ref "R498")
      (value "1002")
      (footprint "eagle-import:R0805")
      (fields (field (name "MPN") "RC0805JR-071KL"))
      (libsource (lib "eagle-import") (part "SMD-RES-1K-5%-1/8W(0805)"))
    )
    (comp (ref "R499")
      (value "R_user")
      (footprint "eagle-import:R0805")
      (libsource (lib "eagle-import") (part "R-EU_R0805"))
    )
    (comp (ref "R500")
      (value "104")
      (footprint "eagle-import:R0805")
      (fields (field (name "MPN") "RC0805FR-0710KL"))
      (libsource (lib "eagle-import") (part "SMD-RES-10K-1%-1/8W(0805)"))
    )
    (comp (ref "R501")
      (value "104")
      (footprint "eagle-import:R0805")
      (fields (field (name "MPN") "RC0805FR-0710KL"))
      (libsource (lib "eagle-import") (part "SMD-RES-10K-1%-1/8W(0805)"))
    )
    (comp (ref "R502")
      (value "104")
      (footprint "eagle-import:R0805")
      (fields (field (name "MPN") "RC0805FR-0710KL"))
      (libsource (lib "eagle-import") (part "SMD-RES-10K-1%-1/8W(0805)"))
    )
    (comp (ref "R503")
      (value "13")
      (footprint "eagle-import:R1206")
      (fields (field (name "MPN") "RC1206JR-0713RL"))
      (libsource (lib "eagle-import") (part "SMD-RES-13R-5%-1/4W(1206)"))
    )
    (comp (ref "R504")
      (value "2201")
      (footprint "eagle-import:R0805")
      (fields (field (name "MPN") "RC0805JR-071KL"))
      (libsource (lib "eagle-import") (part "SMD-RES-1K-5%-1/8W(0805)"))
    )
    (comp (ref "R505")
      (value "100")
      (footprint "eagle-import:R0805")
      (fields (field (name "MPN") "RC0805JR-07220RL"))
      (libsource (lib "eagle-import") (part "SMD-RES-220R-5%-1/8W(0805)"))
    )
    (comp (ref "R506")
      (value "13")
      (footprint "eagle-import:R1206")
      (fields (field (name "MPN") "RC1206JR-0713RL"))
      (libsource (lib "eagle-import") (part "SMD-RES-13R-5%-1/4W(1206)"))
    )
    (comp (ref "R507")
      (value "4701")
      (footprint "eagle-import:R0805")
      (fields (field (name "MPN") "RC0805JR-074K7L"))
      (libsource (lib "eagle-import") (part "SMD-RES-4.7K-5%-1/8W(0805)"))
    )
    (comp (ref "R508")
      (value "104")
      (footprint "eagle-import:R0805")
      (fields (field (name "MPN") "RC0805JR-074K7L"))
      (libsource (lib "eagle-import") (part "SMD-RES-4.7K-5%-1/8W(0805)"))
    )
    (comp (ref "R509")
      (value "100")
      (footprint "eagle-import:R0805")
      (fields (field (name "MPN") "RC0805JR-072K2L"))
      (libsource (lib "eagle-import") (part "SMD-RES-2.2K-5%-1/8W(0805)"))
    )
    (comp (ref "R510")
      (value "100")
      (footprint "eagle-import:R0805")
      (fields (field (name "MPN") "RC0805JR-072K2L"))
      (libsource (lib "eagle-import") (part "SMD-RES-2.2K-5%-1/8W(0805)"))
    )
    (comp (ref "SJMP9")
      (value "SJ")
      (footprint "eagle-import:SJ")
      (libsource (lib "eagle-import") (part "SJ"))
    )
    (comp (ref "START9")
      (value "TPSB2.0")
      (footprint "eagle-import:B2.0")
      (libsource (lib "eagle-import") (part "TPSB2.0"))
    )
    (comp (ref "TP208")
      (value "TPSB2.0")
      (footprint "eagle-import:B2.0")
      (libsource (lib "eagle-import") (part "TPSB2.0"))
    )
    (comp (ref "TP209")
      (value "TPSB2.0")
      (footprint "eagle-import:B2.0")
      (libsource (lib "eagle-import") (part "TPSB2.0"))
    )
    (comp (ref "TP210")
      (value "TPSB2.0")
      (footprint "eagle-import:B2.0")
      (libsource (lib "eagle-import") (part "TPSB2.0"))
    )
    (comp (ref "TP211")
      (value "TPSB2.0")
      (footprint "eagle-import:B2.0")
      (libsource (lib "eagle-import") (part "TPSB2.0"))
    )
    (comp (ref "TP212")
      (value "TPSB2.0")
      (footprint "eagle-import:B2.0")
      (libsource (lib "eagle-import") (part "TPSB2.0"))
    )
    (comp (ref "TP213")
      (value "TPSB2.0")
      (footprint "eagle-import:B2.0")
      (libsource (lib "eagle-import") (part "TPSB2.0"))
    )
    (comp (ref "TP214")
      (value "TPSB2.0")
      (footprint "eagle-import:B2.0")
      (libsource (lib "eagle-import") (part "TPSB2.0"))
    )
    (comp (ref "TP215")
      (value "TPSB2.0")
      (footprint "eagle-import:B2.0")
      (libsource (lib "eagle-import") (part "TPSB2.0"))
    )
    (comp (ref "TP216")
      (value "TPSB2.0")
      (footprint "eagle-import:B2.0")
      (libsource (lib "eagle-import") (part "TPSB2.0"))
    )
    (comp (ref "TP217")
      (value "TPSB2.0")
      (footprint "eagle-import:B2.0")
      (libsource (lib "eagle-import") (part "TPSB2.0"))
    )
    (comp (ref "TP218")
      (value "TPSB2.0")
      (footprint "eagle-import:B2.0")
      (libsource (lib "eagle-import") (part "TPSB2.0"))
    )
    (comp (ref "TP219")
      (value "TPSB2.0")
      (footprint "eagle-import:B2.0")
      (libsource (lib "eagle-import") (part "TPSB2.0"))
    )
    (comp (ref "TP220")
      (value "TPSB2.0")
      (footprint "eagle-import:B2.0")
      (libsource (lib "eagle-import") (part "TPSB2.0"))
    )
    (comp (ref "TP221")
      (value "TPSB2.0")
      (footprint "eagle-import:B2.0")
      (libsource (lib "eagle-import") (part "TPSB2.0"))
    )
    (comp (ref "TP222")
      (value "TPSB2.0")
      (footprint "eagle-import:B2.0")
      (libsource (lib "eagle-import") (part "TPSB2.0"))
    )
    (comp (ref "TP223")
      (value "TPSB2.0")
      (footprint "eagle-import:B2.0")
      (libsource (lib "eagle-import") (part "TPSB2.0"))
    )
    (comp (ref "TP224")
      (value "TPSB2.0")
      (footprint "eagle-import:B2.0")
      (libsource (lib "eagle-import") (part "TPSB2.0"))
    )
    (comp (ref "TP225")
      (value "TPSB2.0")
      (footprint "eagle-import:B2.0")
      (libsource (lib "eagle-import") (part "TPSB2.0"))
    )
    (comp (ref "TP226")
      (value "TPSB1,27")
      (footprint "eagle-import:B1,27")
      (libsource (lib "eagle-import") (part "TPSB1,27"))
    )
    (comp (ref "TP227")
      (value "TPSB2.0")
      (footprint "eagle-import:B2.0")
      (libsource (lib "eagle-import") (part "TPSB2.0"))
    )
    (comp (ref "TP228")
      (value "TPSB2.0")
      (footprint "eagle-import:B2.0")
      (libsource (lib "eagle-import") (part "TPSB2.0"))
    )
    (comp (ref "TP229")
      (value "TPSB2.0")
      (footprint "eagle-import:B2.0")
      (libsource (lib "eagle-import") (part "TPSB2.0"))
    )
    (comp (ref "TP230")
      (value "TPSB2.0")
      (footprint "eagle-import:B2.0")
      (libsource (lib "eagle-import") (part "TPSB2.0"))
    )
    (comp (ref "X25")
      (value "CON_BMWV2")
      (footprint "eagle-import:24-PIN_V2")
      (libsource (lib "eagle-import") (part "CON_BMWV2"))
    )
    (comp (ref "X26")
      (value "22-23-2051")
      (footprint "eagle-import:22-23-2051")
      (fields (field (name "MF") "MOLEX"))
      (libsource (lib "eagle-import") (part "22-23-2051"))
    )
    (comp (ref "X27")
      (value "22-23-2021")
      (footprint "eagle-import:22-23-2021")
      (fields (field (name "MF") "MOLEX"))
      (libsource (lib "eagle-import") (part "22-23-2021"))
    )
    (comp (ref "6V4")
      (value "TPSB2.0")
      (footprint "eagle-import:B2.0")
      (libsource (lib "eagle-import") (part "TPSB2.0"))
    )
    (comp (ref "9")
      (value "2081-1132")
      (footprint "eagle-import:12-PIN")
      (libsource (lib "eagle-import") (part "2081-1132"))
    )
    (comp (ref "10")
      (value "2081-1132")
      (footprint "eagle-import:12-PIN")
      (libsource (lib "eagle-import") (part "2081-1132"))
    )
    (comp (ref "10V4")
      (value "TPSB2.0")
      (footprint "eagle-import:B2.0")
      (libsource (lib "eagle-import") (part "TPSB2.0"))
    )
    (comp (ref "C39")
      (value "100u")
      (footprint "eagle-import:C1206")
      (fields (field (name "MPN") "GRM31CR60J107ME39L"))
      (libsource (lib "eagle-import") (part "CERAMIC-100UF-6.3V-20%-X5R(1206)"))
    )
    (comp (ref "C40")
      (value "100u")
      (footprint "eagle-import:C1206")
      (fields (field (name "MPN") "GRM31CR60J107ME39L"))
      (libsource (lib "eagle-import") (part "CERAMIC-100UF-6.3V-20%-X5R(1206)"))
    )
    (comp (ref "C41")
      (value "100nF,")
      (footprint "eagle-import:C0805")
      (fields (field (name "MPN") "CC0805KRX7R9BB104"))
      (libsource (lib "eagle-import") (part "CERAMIC-100NF-50V-10%-X7R(0805)"))
    )
    (comp (ref "C42")
      (value "4.7u")
      (footprint "eagle-import:C0805")
      (fields (field (name "MPN") "CC0805KKX5R8BB475"))
      (libsource (lib "eagle-import") (part "CERAMIC-4.7UF-25V-10%-X5R(0805)"))
    )
    (comp (ref "C43")
      (value "100nF.")
      (footprint "eagle-import:C0805")
      (fields (field (name "MPN") "CC0805KRX7R9BB104"))
      (libsource (lib "eagle-import") (part "CERAMIC-100NF-50V-10%-X7R(0805)"))
    )
    (comp (ref "C44")
      (value "100nF.")
      (footprint "eagle-import:C0805")
      (fields (field (name "MPN") "CC0805KRX7R9BB104"))
      (libsource (lib "eagle-import") (part "CERAMIC-100NF-50V-10%-X7R(0805)"))
    )
    (comp (ref "C45")
      (value "2.2nF")
      (footprint "eagle-import:C0805")
      (fields (field (name "MPN") "CC0805KRX7R9BB104"))
      (libsource (lib "eagle-import") (part "CERAMIC-100NF-50V-10%-X7R(0805)"))
    )
    (comp (ref "C46")
      (value "100nF")
      (footprint "eagle-import:C0805")
      (fields (field (name "MPN") "CC0805KRX7R9BB104"))
      (libsource (lib "eagle-import") (part "CERAMIC-100NF-50V-10%-X7R(0805)"))
    )
    (comp (ref "C47")
      (value "100nF")
      (footprint "eagle-import:C0805")
      (fields (field (name "MPN") "CC0805KRX7R9BB104"))
      (libsource (lib "eagle-import") (part "CERAMIC-100NF-50V-10%-X7R(0805)"))
    )
    (comp (ref "C48")
      (value "100nF,")
      (footprint "eagle-import:C0805")
      (fields (field (name "MPN") "CC0805KRX7R9BB104"))
      (libsource (lib "eagle-import") (part "CERAMIC-100NF-50V-10%-X7R(0805)"))
    )
    (comp (ref "C49")
      (value "4.7u")
      (footprint "eagle-import:C0805")
      (fields (field (name "MPN") "CC0805KKX5R8BB475"))
      (libsource (lib "eagle-import") (part "CERAMIC-4.7UF-25V-10%-X5R(0805)"))
    )
    (comp (ref "C50")
      (value "10u")
      (footprint "eagle-import:C1206")
      (fields (field (name "MPN") "GRM31CR60J107ME39L"))
      (libsource (lib "eagle-import") (part "CERAMIC-100UF-6.3V-20%-X5R(1206)"))
    )
    (comp (ref "D46")
      (value "1N4007,")
      (footprint "eagle-import:DO-214AC")
      (fields (field (name "MPN") "1N4007"))
      (libsource (lib "eagle-import") (part "DIODE-GEN-PURPOSE-1KV-1A(DO-214AC)"))
    )
    (comp (ref "D47")
      (value "1N4007,")
      (footprint "eagle-import:DO-214AC")
      (fields (field (name "MPN") "1N4007"))
      (libsource (lib "eagle-import") (part "DIODE-GEN-PURPOSE-1KV-1A(DO-214AC)"))
    )
    (comp (ref "D48")
      (value "1N4007.")
      (footprint "eagle-import:DO-214AC")
      (fields (field (name "MPN") "1N4007"))
      (libsource (lib "eagle-import") (part "DIODE-GEN-PURPOSE-1KV-1A(DO-214AC)"))
    )
    (comp (ref "D49")
      (value "1N5817")
      (footprint "eagle-import:DO-214AC_SLIM")
      (libsource (lib "eagle-import") (part "DIODE-GEN-PURPOSE-1KV-1A(DO-214AC)DO-214AC/1206"))
    )
    (comp (ref "D50")
      (value "1N5817.")
      (footprint "eagle-import:DO-214AC_SLIM")
      (libsource (lib "eagle-import") (part "DIODE-GEN-PURPOSE-1KV-1A(DO-214AC)DO-214AC/1206"))
    )
    (comp (ref "D51")
      (value "1N5817.")
      (footprint "eagle-import:DO-214AC_SLIM")
      (libsource (lib "eagle-import") (part "DIODE-GEN-PURPOSE-1KV-1A(DO-214AC)DO-214AC/1206"))
    )
    (comp (ref "D52")
      (value "1N5817")
      (footprint "eagle-import:DO-214AC_SLIM")
      (libsource (lib "eagle-import") (part "DIODE-GEN-PURPOSE-1KV-1A(DO-214AC)DO-214AC/1206"))
    )
    (comp (ref "D53")
      (value "1N4007.")
      (footprint "eagle-import:DO-214AC")
      (fields (field (name "MPN") "1N4007"))
      (libsource (lib "eagle-import") (part "DIODE-GEN-PURPOSE-1KV-1A(DO-214AC)"))
    )
    (comp (ref "D54")
      (value "1N4007")
      (footprint "eagle-import:DO-214AC")
      (libsource (lib "eagle-import") (part "DIODE-GEN-PURPOSE-1KV-1A(DO-214AC)"))
    )
    (comp (ref "D55")
      (value "Zen15")
      (footprint "eagle-import:DO214AA")
      (libsource (lib "eagle-import") (part "SM6T"))
    )
    (comp (ref "D57")
      (value "SS12")
      (footprint "eagle-import:DO-214AC_SLIM")
      (libsource (lib "eagle-import") (part "DIODE-GEN-PURPOSE-1KV-1A(DO-214AC)DO-214AC/1206"))
    )
    (comp (ref "D58")
      (value "SS12")
      (footprint "eagle-import:DO-214AC_SLIM")
      (libsource (lib "eagle-import") (part "DIODE-GEN-PURPOSE-1KV-1A(DO-214AC)DO-214AC/1206"))
    )
    (comp (ref "D59")
      (value "Zen11")
      (footprint "eagle-import:SOD-123_MINI-SMA")
      (libsource (lib "eagle-import") (part "CGRM400-G1"))
    )
    (comp (ref "FID15")
      (value "FIDUCIAL")
      (footprint "eagle-import:FIDUCIAL_1MM")
      (libsource (lib "eagle-import") (part "FIDUCIAL"))
    )
    (comp (ref "FID16")
      (value "FIDUCIAL")
      (footprint "eagle-import:FIDUCIAL_1MM")
      (libsource (lib "eagle-import") (part "FIDUCIAL"))
    )
    (comp (ref "FID17")
      (value "FIDUCIAL")
      (footprint "eagle-import:FIDUCIAL_1MM")
      (libsource (lib "eagle-import") (part "FIDUCIAL"))
    )
    (comp (ref "FID18")
      (value "FIDUCIAL")
      (footprint "eagle-import:FIDUCIAL_1MM")
      (libsource (lib "eagle-import") (part "FIDUCIAL"))
    )
    (comp (ref "IC28")
      (value "4028")
      (footprint "eagle-import:SO16")
      (libsource (lib "eagle-import") (part "4028D"))
    )
    (comp (ref "IC29")
      (value "317TO202H_NOHOLE")
      (footprint "eagle-import:TO220H_NOHOLE")
      (libsource (lib "eagle-import") (part "317TO202H_NOHOLE"))
    )
    (comp (ref "IC30")
      (value "ULN2004")
      (footprint "eagle-import:SO16")
      (libsource (lib "eagle-import") (part "ULN2004AD"))
    )
    (comp (ref "IC31")
      (value "LM339")
      (footprint "eagle-import:SO14")
      (libsource (lib "eagle-import") (part "LM339D"))
    )
    (comp (ref "IC32")
      (value "78L06")
      (footprint "eagle-import:SOT89_ROUND")
      (libsource (lib "eagle-import") (part "78LXXSOT89_ROUND"))
    )
    (comp (ref "IC33")
      (value "555")
      (footprint "eagle-import:SO08")
      (libsource (lib "eagle-import") (part "555DNE"))
    )
    (comp (ref "IC34")
      (value "4538")
      (footprint "eagle-import:SO16")
      (libsource (lib "eagle-import") (part "4538D"))
    )
    (comp (ref "IC35")
      (value "78L10")
      (footprint "eagle-import:SOT89_ROUND")
      (libsource (lib "eagle-import") (part "78LXXSOT89_ROUND"))
    )
    (comp (ref "IC36")
      (value "LM2904")
      (footprint "eagle-import:SO08")
      (libsource (lib "eagle-import") (part "LM358D"))
    )
    (comp (ref "JP16")
      (value "JP2EJP2_SMALLPADS")
      (footprint "eagle-import:JP2_SMALLPADS")
      (libsource (lib "eagle-import") (part "JP2EJP2_SMALLPADS"))
    )
    (comp (ref "JP17")
      (value "JP2E_ORIG")
      (footprint "eagle-import:JP2_ORIG_SMALLPADS")
      (libsource (lib "eagle-import") (part "JP2E_ORIG"))
    )
    (comp (ref "JP18")
      (value "JP2EJP2_SMALLPADS")
      (footprint "eagle-import:JP2_SMALLPADS")
      (libsource (lib "eagle-import") (part "JP2EJP2_SMALLPADS"))
    )
    (comp (ref "JP19")
      (value "JP2EJP2_SMALLPADS")
      (footprint "eagle-import:JP2_SMALLPADS")
      (libsource (lib "eagle-import") (part "JP2EJP2_SMALLPADS"))
    )
    (comp (ref "JP20")
      (value "JP2EJP2_SMALLPADS")
      (footprint "eagle-import:JP2_SMALLPADS")
      (libsource (lib "eagle-import") (part "JP2EJP2_SMALLPADS"))
    )
    (comp (ref "LED19")
      (value "LEDLD260")
      (footprint "eagle-import:LD260")
      (libsource (lib "eagle-import") (part "LEDLD260"))
    )
    (comp (ref "LED20")
      (value "LEDLD260")
      (footprint "eagle-import:LD260")
      (libsource (lib "eagle-import") (part "LEDLD260"))
    )
    (comp (ref "LED21")
      (value "LEDLD260")
      (footprint "eagle-import:LD260")
      (libsource (lib "eagle-import") (part "LEDLD260"))
    )
    (comp (ref "LED22")
      (value "LEDLD260")
      (footprint "eagle-import:LD260")
      (libsource (lib "eagle-import") (part "LEDLD260"))
    )
    (comp (ref "LED23")
      (value "LEDLD260")
      (footprint "eagle-import:LD260")
      (libsource (lib "eagle-import") (part "LEDLD260"))
    )
    (comp (ref "LED24")
      (value "LEDLD260")
      (footprint "eagle-import:LD260")
      (libsource (lib "eagle-import") (part "LEDLD260"))
    )
    (comp (ref "Q34")
      (value "BA")
      (footprint "eagle-import:SOT89")
      (libsource (lib "eagle-import") (part "PNP-TRANSISTOR_SOT89"))
    )
    (comp (ref "Q35")
      (value "BA.")
      (footprint "eagle-import:SOT89")
      (libsource (lib "eagle-import") (part "PNP-TRANSISTOR_SOT89"))
    )
    (comp (ref "Q36")
      (value "BA.")
      (footprint "eagle-import:SOT89")
      (libsource (lib "eagle-import") (part "PNP-TRANSISTOR_SOT89"))
    )
    (comp (ref "Q37")
      (value "BA")
      (footprint "eagle-import:SOT89")
      (libsource (lib "eagle-import") (part "PNP-TRANSISTOR_SOT89"))
    )
    (comp (ref "Q38")
      (value "MY")
      (footprint "eagle-import:SOT89")
      (libsource (lib "eagle-import") (part "NPN-TRANSISTOR_SOT89"))
    )
    (comp (ref "Q39")
      (value "J1")
      (footprint "eagle-import:SOT-23")
      (fields (field (name "MPN") "BSS138W-7-F"))
      (libsource (lib "eagle-import") (part "SMD-MOSFET-N-CH-50V-200MA-BSS138W-7-F(SOT-23)"))
    )
    (comp (ref "Q40")
      (value "J1")
      (footprint "eagle-import:SOT-23")
      (fields (field (name "MPN") "BSS138W-7-F"))
      (libsource (lib "eagle-import") (part "SMD-MOSFET-N-CH-50V-200MA-BSS138W-7-F(SOT-23)"))
    )
    (comp (ref "Q41")
      (value "J1")
      (footprint "eagle-import:SOT-23")
      (fields (field (name "MPN") "BSS138W-7-F"))
      (libsource (lib "eagle-import") (part "SMD-MOSFET-N-CH-50V-200MA-BSS138W-7-F(SOT-23)"))
    )
    (comp (ref "Q42")
      (value "BA")
      (footprint "eagle-import:SOT89")
      (libsource (lib "eagle-import") (part "PNP-TRANSISTOR_SOT89"))
    )
    (comp (ref "Q43")
      (value "J1")
      (footprint "eagle-import:SOT-23")
      (fields (field (name "MPN") "BSS138W-7-F"))
      (libsource (lib "eagle-import") (part "SMD-MOSFET-N-CH-50V-200MA-BSS138W-7-F(SOT-23)"))
    )
    (comp (ref "R221")
      (value "47")
      (footprint "eagle-import:V235_17_1MM")
      (libsource (lib "eagle-import") (part "R-EU_V235/17_1MM"))
    )
    (comp (ref "R222")
      (value "13")
      (footprint "eagle-import:R1206")
      (fields (field (name "MPN") "RC1206JR-0713RL"))
      (libsource (lib "eagle-import") (part "SMD-RES-13R-5%-1/4W(1206)"))
    )
    (comp (ref "R223")
      (value "47")
      (footprint "eagle-import:V235_17_1MM")
      (libsource (lib "eagle-import") (part "R-EU_V235/17_1MM"))
    )
    (comp (ref "R224")
      (value "104")
      (footprint "eagle-import:R0805")
      (fields (field (name "MPN") "RC0805FR-0710KL"))
      (libsource (lib "eagle-import") (part "SMD-RES-10K-1%-1/8W(0805)"))
    )
    (comp (ref "R225")
      (value "104")
      (footprint "eagle-import:R0805")
      (fields (field (name "MPN") "RC0805FR-0710KL"))
      (libsource (lib "eagle-import") (part "SMD-RES-10K-1%-1/8W(0805)"))
    )
    (comp (ref "R226")
      (value "104")
      (footprint "eagle-import:R0805")
      (fields (field (name "MPN") "RC0805FR-0710KL"))
      (libsource (lib "eagle-import") (part "SMD-RES-10K-1%-1/8W(0805)"))
    )
    (comp (ref "R227")
      (value "4701")
      (footprint "eagle-import:R0805")
      (fields (field (name "MPN") "RC0805JR-074K7L"))
      (libsource (lib "eagle-import") (part "SMD-RES-4.7K-5%-1/8W(0805)"))
    )
    (comp (ref "R228")
      (value "1002")
      (footprint "eagle-import:R0805")
      (fields (field (name "MPN") "RC0805FR-0710KL"))
      (libsource (lib "eagle-import") (part "SMD-RES-10K-1%-1/8W(0805)"))
    )
    (comp (ref "R229")
      (value "1002")
      (footprint "eagle-import:R0805")
      (fields (field (name "MPN") "RC0805FR-0710KL"))
      (libsource (lib "eagle-import") (part "SMD-RES-10K-1%-1/8W(0805)"))
    )
    (comp (ref "R230")
      (value "1502")
      (footprint "eagle-import:R0805")
      (fields (field (name "MPN") "RC0805FR-0710KL"))
      (libsource (lib "eagle-import") (part "SMD-RES-10K-1%-1/8W(0805)"))
    )
    (comp (ref "R231")
      (value "104")
      (footprint "eagle-import:R0805")
      (fields (field (name "MPN") "RC0805FR-0710KL"))
      (libsource (lib "eagle-import") (part "SMD-RES-10K-1%-1/8W(0805)"))
    )
    (comp (ref "R232")
      (value "104")
      (footprint "eagle-import:R0805")
      (fields (field (name "MPN") "RC0805FR-0710KL"))
      (libsource (lib "eagle-import") (part "SMD-RES-10K-1%-1/8W(0805)"))
    )
    (comp (ref "R233")
      (value "1502")
      (footprint "eagle-import:R0805")
      (fields (field (name "MPN") "RC0805FR-0710KL"))
      (libsource (lib "eagle-import") (part "SMD-RES-10K-1%-1/8W(0805)"))
    )
    (comp (ref "R234")
      (value "1002")
      (footprint "eagle-import:R0805")
      (fields (field (name "MPN") "RC0805FR-0710KL"))
      (libsource (lib "eagle-import") (part "SMD-RES-10K-1%-1/8W(0805)"))
    )
    (comp (ref "R235")
      (value "2201")
      (footprint "eagle-import:R0805")
      (fields (field (name "MPN") "RC0805JR-072K2L"))
      (libsource (lib "eagle-import") (part "SMD-RES-2.2K-5%-1/8W(0805)"))
    )
    (comp (ref "R236")
      (value "1002")
      (footprint "eagle-import:R0805")
      (fields (field (name "MPN") "RC0805FR-0710KL"))
      (libsource (lib "eagle-import") (part "SMD-RES-10K-1%-1/8W(0805)"))
    )
    (comp (ref "R237")
      (value "4701")
      (footprint "eagle-import:R0805")
      (fields (field (name "MPN") "RC0805JR-074K7L"))
      (libsource (lib "eagle-import") (part "SMD-RES-4.7K-5%-1/8W(0805)"))
    )
    (comp (ref "R238")
      (value "2702")
      (footprint "eagle-import:R0805")
      (fields (field (name "MPN") "RC0805JR-074K7L"))
      (libsource (lib "eagle-import") (part "SMD-RES-4.7K-5%-1/8W(0805)"))
    )
    (comp (ref "R239")
      (value "102")
      (footprint "eagle-import:R0805")
      (fields (field (name "MPN") "RC0805JR-071KL"))
      (libsource (lib "eagle-import") (part "SMD-RES-1K-5%-1/8W(0805)"))
    )
    (comp (ref "R241")
      (value "102")
      (footprint "eagle-import:R0805")
      (fields (field (name "MPN") "RC0805JR-07220RL"))
      (libsource (lib "eagle-import") (part "SMD-RES-220R-5%-1/8W(0805)"))
    )
    (comp (ref "R244")
      (value "102")
      (footprint "eagle-import:R0805")
      (fields (field (name "MPN") "RC0805JR-071KL"))
      (libsource (lib "eagle-import") (part "SMD-RES-1K-5%-1/8W(0805)"))
    )
    (comp (ref "R245")
      (value "13")
      (footprint "eagle-import:R1206")
      (fields (field (name "MPN") "RC1206JR-0713RL"))
      (libsource (lib "eagle-import") (part "SMD-RES-13R-5%-1/4W(1206)"))
    )
    (comp (ref "R246")
      (value "13")
      (footprint "eagle-import:R1206")
      (fields (field (name "MPN") "RC1206JR-0713RL"))
      (libsource (lib "eagle-import") (part "SMD-RES-13R-5%-1/4W(1206)"))
    )
    (comp (ref "R247")
      (value "2702")
      (footprint "eagle-import:R0805")
      (fields (field (name "MPN") "RC0805JR-074K7L"))
      (libsource (lib "eagle-import") (part "SMD-RES-4.7K-5%-1/8W(0805)"))
    )
    (comp (ref "R248")
      (value "4701")
      (footprint "eagle-import:R0805")
      (fields (field (name "MPN") "RC0805JR-074K7L"))
      (libsource (lib "eagle-import") (part "SMD-RES-4.7K-5%-1/8W(0805)"))
    )
    (comp (ref "R249")
      (value "100")
      (footprint "eagle-import:R0805")
      (fields (field (name "MPN") "RC0805JR-072K2L"))
      (libsource (lib "eagle-import") (part "SMD-RES-2.2K-5%-1/8W(0805)"))
    )
    (comp (ref "R250")
      (value "104")
      (footprint "eagle-import:R0805")
      (fields (field (name "MPN") "RC0805FR-0710KL"))
      (libsource (lib "eagle-import") (part "SMD-RES-10K-1%-1/8W(0805)"))
    )
    (comp (ref "R251")
      (value "104")
      (footprint "eagle-import:R0805")
      (fields (field (name "MPN") "RC0805FR-0710KL"))
      (libsource (lib "eagle-import") (part "SMD-RES-10K-1%-1/8W(0805)"))
    )
    (comp (ref "R253")
      (value "2702")
      (footprint "eagle-import:R0805")
      (fields (field (name "MPN") "RC0805FR-0710KL"))
      (libsource (lib "eagle-import") (part "SMD-RES-10K-1%-1/8W(0805)"))
    )
    (comp (ref "R254")
      (value "47")
      (footprint "eagle-import:V235_17_1MM")
      (libsource (lib "eagle-import") (part "R-EU_V235/17_1MM"))
    )
    (comp (ref "R255")
      (value "47")
      (footprint "eagle-import:V235_17_1MM")
      (libsource (lib "eagle-import") (part "R-EU_V235/17_1MM"))
    )
    (comp (ref "R256")
      (value "2702")
      (footprint "eagle-import:R0805")
      (fields (field (name "MPN") "RC0805JR-074K7L"))
      (libsource (lib "eagle-import") (part "SMD-RES-4.7K-5%-1/8W(0805)"))
    )
    (comp (ref "R257")
      (value "2201")
      (footprint "eagle-import:R0805")
      (fields (field (name "MPN") "RC0805JR-072K2L"))
      (libsource (lib "eagle-import") (part "SMD-RES-2.2K-5%-1/8W(0805)"))
    )
    (comp (ref "R258")
      (value "1002")
      (footprint "eagle-import:R0805")
      (fields (field (name "MPN") "RC0805JR-074K7L"))
      (libsource (lib "eagle-import") (part "SMD-RES-4.7K-5%-1/8W(0805)"))
    )
    (comp (ref "R259")
      (value "1002")
      (footprint "eagle-import:R0805")
      (fields (field (name "MPN") "RC0805FR-0710KL"))
      (libsource (lib "eagle-import") (part "SMD-RES-10K-1%-1/8W(0805)"))
    )
    (comp (ref "R260")
      (value "102")
      (footprint "eagle-import:R0805")
      (fields (field (name "MPN") "RC0805JR-071KL"))
      (libsource (lib "eagle-import") (part "SMD-RES-1K-5%-1/8W(0805)"))
    )
    (comp (ref "R261")
      (value "2702")
      (footprint "eagle-import:R0805")
      (fields (field (name "MPN") "RC0805JR-074K7L"))
      (libsource (lib "eagle-import") (part "SMD-RES-4.7K-5%-1/8W(0805)"))
    )
    (comp (ref "R262")
      (value "1002")
      (footprint "eagle-import:R0805")
      (fields (field (name "MPN") "RC0805JR-071KL"))
      (libsource (lib "eagle-import") (part "SMD-RES-1K-5%-1/8W(0805)"))
    )
    (comp (ref "R263")
      (value "1002")
      (footprint "eagle-import:R0805")
      (fields (field (name "MPN") "RC0805JR-071KL"))
      (libsource (lib "eagle-import") (part "SMD-RES-1K-5%-1/8W(0805)"))
    )
    (comp (ref "R264")
      (value "R_user")
      (footprint "eagle-import:R0805")
      (libsource (lib "eagle-import") (part "R-EU_R0805"))
    )
    (comp (ref "R265")
      (value "104")
      (footprint "eagle-import:R0805")
      (fields (field (name "MPN") "RC0805FR-0710KL"))
      (libsource (lib "eagle-import") (part "SMD-RES-10K-1%-1/8W(0805)"))
    )
    (comp (ref "R266")
      (value "104")
      (footprint "eagle-import:R0805")
      (fields (field (name "MPN") "RC0805FR-0710KL"))
      (libsource (lib "eagle-import") (part "SMD-RES-10K-1%-1/8W(0805)"))
    )
    (comp (ref "R267")
      (value "104")
      (footprint "eagle-import:R0805")
      (fields (field (name "MPN") "RC0805FR-0710KL"))
      (libsource (lib "eagle-import") (part "SMD-RES-10K-1%-1/8W(0805)"))
    )
    (comp (ref "R268")
      (value "13")
      (footprint "eagle-import:R1206")
      (fields (field (name "MPN") "RC1206JR-0713RL"))
      (libsource (lib "eagle-import") (part "SMD-RES-13R-5%-1/4W(1206)"))
    )
    (comp (ref "R269")
      (value "2201")
      (footprint "eagle-import:R0805")
      (fields (field (name "MPN") "RC0805JR-071KL"))
      (libsource (lib "eagle-import") (part "SMD-RES-1K-5%-1/8W(0805)"))
    )
    (comp (ref "R270")
      (value "100")
      (footprint "eagle-import:R0805")
      (fields (field (name "MPN") "RC0805JR-07220RL"))
      (libsource (lib "eagle-import") (part "SMD-RES-220R-5%-1/8W(0805)"))
    )
    (comp (ref "R271")
      (value "13")
      (footprint "eagle-import:R1206")
      (fields (field (name "MPN") "RC1206JR-0713RL"))
      (libsource (lib "eagle-import") (part "SMD-RES-13R-5%-1/4W(1206)"))
    )
    (comp (ref "R272")
      (value "4701")
      (footprint "eagle-import:R0805")
      (fields (field (name "MPN") "RC0805JR-074K7L"))
      (libsource (lib "eagle-import") (part "SMD-RES-4.7K-5%-1/8W(0805)"))
    )
    (comp (ref "R273")
      (value "104")
      (footprint "eagle-import:R0805")
      (fields (field (name "MPN") "RC0805JR-074K7L"))
      (libsource (lib "eagle-import") (part "SMD-RES-4.7K-5%-1/8W(0805)"))
    )
    (comp (ref "R274")
      (value "100")
      (footprint "eagle-import:R0805")
      (fields (field (name "MPN") "RC0805JR-072K2L"))
      (libsource (lib "eagle-import") (part "SMD-RES-2.2K-5%-1/8W(0805)"))
    )
    (comp (ref "R275")
      (value "100")
      (footprint "eagle-import:R0805")
      (fields (field (name "MPN") "RC0805JR-072K2L"))
      (libsource (lib "eagle-import") (part "SMD-RES-2.2K-5%-1/8W(0805)"))
    )
    (comp (ref "SJMP4")
      (value "SJ")
      (footprint "eagle-import:SJ")
      (libsource (lib "eagle-import") (part "SJ"))
    )
    (comp (ref "START4")
      (value "TPSB2.0")
      (footprint "eagle-import:B2.0")
      (libsource (lib "eagle-import") (part "TPSB2.0"))
    )
    (comp (ref "TP93")
      (value "TPSB2.0")
      (footprint "eagle-import:B2.0")
      (libsource (lib "eagle-import") (part "TPSB2.0"))
    )
    (comp (ref "TP94")
      (value "TPSB2.0")
      (footprint "eagle-import:B2.0")
      (libsource (lib "eagle-import") (part "TPSB2.0"))
    )
    (comp (ref "TP95")
      (value "TPSB2.0")
      (footprint "eagle-import:B2.0")
      (libsource (lib "eagle-import") (part "TPSB2.0"))
    )
    (comp (ref "TP96")
      (value "TPSB2.0")
      (footprint "eagle-import:B2.0")
      (libsource (lib "eagle-import") (part "TPSB2.0"))
    )
    (comp (ref "TP97")
      (value "TPSB2.0")
      (footprint "eagle-import:B2.0")
      (libsource (lib "eagle-import") (part "TPSB2.0"))
    )
    (comp (ref "TP98")
      (value "TPSB2.0")
      (footprint "eagle-import:B2.0")
      (libsource (lib "eagle-import") (part "TPSB2.0"))
    )
    (comp (ref "TP99")
      (value "TPSB2.0")
      (footprint "eagle-import:B2.0")
      (libsource (lib "eagle-import") (part "TPSB2.0"))
    )
    (comp (ref "TP100")
      (value "TPSB2.0")
      (footprint "eagle-import:B2.0")
      (libsource (lib "eagle-import") (part "TPSB2.0"))
    )
    (comp (ref "TP101")
      (value "TPSB2.0")
      (footprint "eagle-import:B2.0")
      (libsource (lib "eagle-import") (part "TPSB2.0"))
    )
    (comp (ref "TP102")
      (value "TPSB2.0")
      (footprint "eagle-import:B2.0")
      (libsource (lib "eagle-import") (part "TPSB2.0"))
    )
    (comp (ref "TP103")
      (value "TPSB2.0")
      (footprint "eagle-import:B2.0")
      (libsource (lib "eagle-import") (part "TPSB2.0"))
    )
    (comp (ref "TP104")
      (value "TPSB2.0")
      (footprint "eagle-import:B2.0")
      (libsource (lib "eagle-import") (part "TPSB2.0"))
    )
    (comp (ref "TP105")
      (value "TPSB2.0")
      (footprint "eagle-import:B2.0")
      (libsource (lib "eagle-import") (part "TPSB2.0"))
    )
    (comp (ref "TP106")
      (value "TPSB2.0")
      (footprint "eagle-import:B2.0")
      (libsource (lib "eagle-import") (part "TPSB2.0"))
    )
    (comp (ref "TP107")
      (value "TPSB2.0")
      (footprint "eagle-import:B2.0")
      (libsource (lib "eagle-import") (part "TPSB2.0"))
    )
    (comp (ref "TP108")
      (value "TPSB2.0")
      (footprint "eagle-import:B2.0")
      (libsource (lib "eagle-import") (part "TPSB2.0"))
    )
    (comp (ref "TP109")
      (value "TPSB2.0")
      (footprint "eagle-import:B2.0")
      (libsource (lib "eagle-import") (part "TPSB2.0"))
    )
    (comp (ref "TP110")
      (value "TPSB2.0")
      (footprint "eagle-import:B2.0")
      (libsource (lib "eagle-import") (part "TPSB2.0"))
    )
    (comp (ref "TP111")
      (value "TPSB1,27")
      (footprint "eagle-import:B1,27")
      (libsource (lib "eagle-import") (part "TPSB1,27"))
    )
    (comp (ref "TP112")
      (value "TPSB2.0")
      (footprint "eagle-import:B2.0")
      (libsource (lib "eagle-import") (part "TPSB2.0"))
    )
    (comp (ref "TP113")
      (value "TPSB2.0")
      (footprint "eagle-import:B2.0")
      (libsource (lib "eagle-import") (part "TPSB2.0"))
    )
    (comp (ref "TP114")
      (value "TPSB2.0")
      (footprint "eagle-import:B2.0")
      (libsource (lib "eagle-import") (part "TPSB2.0"))
    )
    (comp (ref "TP115")
      (value "TPSB2.0")
      (footprint "eagle-import:B2.0")
      (libsource (lib "eagle-import") (part "TPSB2.0"))
    )
    (comp (ref "X10")
      (value "CON_BMWV2")
      (footprint "eagle-import:24-PIN_V2")
      (libsource (lib "eagle-import") (part "CON_BMWV2"))
    )
    (comp (ref "X11")
      (value "22-23-2051")
      (footprint "eagle-import:22-23-2051")
      (fields (field (name "MF") "MOLEX"))
      (libsource (lib "eagle-import") (part "22-23-2051"))
    )
    (comp (ref "X12")
      (value "22-23-2021")
      (footprint "eagle-import:22-23-2021")
      (fields (field (name "MF") "MOLEX"))
      (libsource (lib "eagle-import") (part "22-23-2021"))
    )
    (comp (ref "1")
      (value "2081-1132")
      (footprint "eagle-import:12-PIN")
      (libsource (lib "eagle-import") (part "2081-1132"))
    )
    (comp (ref "2")
      (value "2081-1132")
      (footprint "eagle-import:12-PIN")
      (libsource (lib "eagle-import") (part "2081-1132"))
    )
    (comp (ref "6V")
      (value "TPSB2.0")
      (footprint "eagle-import:B2.0")
      (libsource (lib "eagle-import") (part "TPSB2.0"))
    )
    (comp (ref "10V")
      (value "TPSB2.0")
      (footprint "eagle-import:B2.0")
      (libsource (lib "eagle-import") (part "TPSB2.0"))
    )
    (comp (ref "C2")
      (value "10u")
      (footprint "eagle-import:C1206")
      (fields (field (name "MPN") "GRM31CR60J107ME39L"))
      (libsource (lib "eagle-import") (part "CERAMIC-100UF-6.3V-20%-X5R(1206)"))
    )
    (comp (ref "C15")
      (value "4.7u")
      (footprint "eagle-import:C0805")
      (fields (field (name "MPN") "CC0805KKX5R8BB475"))
      (libsource (lib "eagle-import") (part "CERAMIC-4.7UF-25V-10%-X5R(0805)"))
    )
    (comp (ref "C101")
      (value "4.7u")
      (footprint "eagle-import:C0805")
      (fields (field (name "MPN") "CC0805KKX5R8BB475"))
      (libsource (lib "eagle-import") (part "CERAMIC-4.7UF-25V-10%-X5R(0805)"))
    )
    (comp (ref "C102")
      (value "100nF")
      (footprint "eagle-import:C0805")
      (fields (field (name "MPN") "CC0805KRX7R9BB104"))
      (libsource (lib "eagle-import") (part "CERAMIC-100NF-50V-10%-X7R(0805)"))
    )
    (comp (ref "C103")
      (value "100nF,")
      (footprint "eagle-import:C0805")
      (fields (field (name "MPN") "CC0805KRX7R9BB104"))
      (libsource (lib "eagle-import") (part "CERAMIC-100NF-50V-10%-X7R(0805)"))
    )
    (comp (ref "C104")
      (value "100nF,")
      (footprint "eagle-import:C0805")
      (fields (field (name "MPN") "CC0805KRX7R9BB104"))
      (libsource (lib "eagle-import") (part "CERAMIC-100NF-50V-10%-X7R(0805)"))
    )
    (comp (ref "C105")
      (value "100nF.")
      (footprint "eagle-import:C0805")
      (fields (field (name "MPN") "CC0805KRX7R9BB104"))
      (libsource (lib "eagle-import") (part "CERAMIC-100NF-50V-10%-X7R(0805)"))
    )
    (comp (ref "C106")
      (value "100nF.")
      (footprint "eagle-import:C0805")
      (fields (field (name "MPN") "CC0805KRX7R9BB104"))
      (libsource (lib "eagle-import") (part "CERAMIC-100NF-50V-10%-X7R(0805)"))
    )
    (comp (ref "C107")
      (value "100u")
      (footprint "eagle-import:C1206")
      (fields (field (name "MPN") "GRM31CR60J107ME39L"))
      (libsource (lib "eagle-import") (part "CERAMIC-100UF-6.3V-20%-X5R(1206)"))
    )
    (comp (ref "C108")
      (value "100u")
      (footprint "eagle-import:C1206")
      (fields (field (name "MPN") "GRM31CR60J107ME39L"))
      (libsource (lib "eagle-import") (part "CERAMIC-100UF-6.3V-20%-X5R(1206)"))
    )
    (comp (ref "C109")
      (value "2.2nF")
      (footprint "eagle-import:C0805")
      (fields (field (name "MPN") "CC0805KRX7R9BB104"))
      (libsource (lib "eagle-import") (part "CERAMIC-100NF-50V-10%-X7R(0805)"))
    )
    (comp (ref "C110")
      (value "100nF")
      (footprint "eagle-import:C0805")
      (fields (field (name "MPN") "CC0805KRX7R9BB104"))
      (libsource (lib "eagle-import") (part "CERAMIC-100NF-50V-10%-X7R(0805)"))
    )
    (comp (ref "D1")
      (value "SS12")
      (footprint "eagle-import:DO-214AC_SLIM")
      (libsource (lib "eagle-import") (part "DIODE-GEN-PURPOSE-1KV-1A(DO-214AC)DO-214AC/1206"))
    )
    (comp (ref "D2")
      (value "SS12")
      (footprint "eagle-import:DO-214AC_SLIM")
      (libsource (lib "eagle-import") (part "DIODE-GEN-PURPOSE-1KV-1A(DO-214AC)DO-214AC/1206"))
    )
    (comp (ref "D4")
      (value "Zen11")
      (footprint "eagle-import:SOD-123_MINI-SMA")
      (libsource (lib "eagle-import") (part "CGRM400-G1"))
    )
    (comp (ref "D101")
      (value "Zen15")
      (footprint "eagle-import:DO214AA")
      (libsource (lib "eagle-import") (part "SM6T"))
    )
    (comp (ref "D102")
      (value "1N4007,")
      (footprint "eagle-import:DO-214AC")
      (fields (field (name "MPN") "1N4007"))
      (libsource (lib "eagle-import") (part "DIODE-GEN-PURPOSE-1KV-1A(DO-214AC)"))
    )
    (comp (ref "D103")
      (value "1N4007,")
      (footprint "eagle-import:DO-214AC")
      (fields (field (name "MPN") "1N4007"))
      (libsource (lib "eagle-import") (part "DIODE-GEN-PURPOSE-1KV-1A(DO-214AC)"))
    )
    (comp (ref "D105")
      (value "1N4007.")
      (footprint "eagle-import:DO-214AC")
      (fields (field (name "MPN") "1N4007"))
      (libsource (lib "eagle-import") (part "DIODE-GEN-PURPOSE-1KV-1A(DO-214AC)"))
    )
    (comp (ref "D106")
      (value "1N4007.")
      (footprint "eagle-import:DO-214AC")
      (fields (field (name "MPN") "1N4007"))
      (libsource (lib "eagle-import") (part "DIODE-GEN-PURPOSE-1KV-1A(DO-214AC)"))
    )
    (comp (ref "D107")
      (value "1N5817")
      (footprint "eagle-import:DO-214AC_SLIM")
      (libsource (lib "eagle-import") (part "DIODE-GEN-PURPOSE-1KV-1A(DO-214AC)DO-214AC/1206"))
    )
    (comp (ref "D108")
      (value "1N5817.")
      (footprint "eagle-import:DO-214AC_SLIM")
      (libsource (lib "eagle-import") (part "DIODE-GEN-PURPOSE-1KV-1A(DO-214AC)DO-214AC/1206"))
    )
    (comp (ref "D109")
      (value "1N5817.")
      (footprint "eagle-import:DO-214AC_SLIM")
      (libsource (lib "eagle-import") (part "DIODE-GEN-PURPOSE-1KV-1A(DO-214AC)DO-214AC/1206"))
    )
    (comp (ref "D110")
      (value "1N5817")
      (footprint "eagle-import:DO-214AC_SLIM")
      (libsource (lib "eagle-import") (part "DIODE-GEN-PURPOSE-1KV-1A(DO-214AC)DO-214AC/1206"))
    )
    (comp (ref "D112")
      (value "1N4007")
      (footprint "eagle-import:DO-214AC")
      (libsource (lib "eagle-import") (part "DIODE-GEN-PURPOSE-1KV-1A(DO-214AC)"))
    )
    (comp (ref "FID101")
      (value "FIDUCIAL")
      (footprint "eagle-import:FIDUCIAL_1MM")
      (libsource (lib "eagle-import") (part "FIDUCIAL"))
    )
    (comp (ref "FID102")
      (value "FIDUCIAL")
      (footprint "eagle-import:FIDUCIAL_1MM")
      (libsource (lib "eagle-import") (part "FIDUCIAL"))
    )
    (comp (ref "FID103")
      (value "FIDUCIAL")
      (footprint "eagle-import:FIDUCIAL_1MM")
      (libsource (lib "eagle-import") (part "FIDUCIAL"))
    )
    (comp (ref "FID104")
      (value "FIDUCIAL")
      (footprint "eagle-import:FIDUCIAL_1MM")
      (libsource (lib "eagle-import") (part "FIDUCIAL"))
    )
    (comp (ref "IC101")
      (value "LM2904")
      (footprint "eagle-import:SO08")
      (libsource (lib "eagle-import") (part "LM358D"))
    )
    (comp (ref "IC102")
      (value "78L06")
      (footprint "eagle-import:SOT89_ROUND")
      (libsource (lib "eagle-import") (part "78LXXSOT89_ROUND"))
    )
    (comp (ref "IC104")
      (value "78L10")
      (footprint "eagle-import:SOT89_ROUND")
      (libsource (lib "eagle-import") (part "78LXXSOT89_ROUND"))
    )
    (comp (ref "IC105")
      (value "4028")
      (footprint "eagle-import:SO16")
      (libsource (lib "eagle-import") (part "4028D"))
    )
    (comp (ref "IC107")
      (value "ULN2004")
      (footprint "eagle-import:SO16")
      (libsource (lib "eagle-import") (part "ULN2004AD"))
    )
    (comp (ref "IC108")
      (value "LM339")
      (footprint "eagle-import:SO14")
      (libsource (lib "eagle-import") (part "LM339D"))
    )
    (comp (ref "IC109")
      (value "317TO202H_NOHOLE")
      (footprint "eagle-import:TO220H_NOHOLE")
      (libsource (lib "eagle-import") (part "317TO202H_NOHOLE"))
    )
    (comp (ref "IC110")
      (value "555")
      (footprint "eagle-import:SO08")
      (libsource (lib "eagle-import") (part "555DNE"))
    )
    (comp (ref "IC111")
      (value "4538")
      (footprint "eagle-import:SO16")
      (libsource (lib "eagle-import") (part "4538D"))
    )
    (comp (ref "JP101")
      (value "JP2EJP2_SMALLPADS")
      (footprint "eagle-import:JP2_SMALLPADS")
      (libsource (lib "eagle-import") (part "JP2EJP2_SMALLPADS"))
    )
    (comp (ref "JP102")
      (value "JP2EJP2_SMALLPADS")
      (footprint "eagle-import:JP2_SMALLPADS")
      (libsource (lib "eagle-import") (part "JP2EJP2_SMALLPADS"))
    )
    (comp (ref "JP103")
      (value "JP2EJP2_SMALLPADS")
      (footprint "eagle-import:JP2_SMALLPADS")
      (libsource (lib "eagle-import") (part "JP2EJP2_SMALLPADS"))
    )
    (comp (ref "JP104")
      (value "JP2EJP2_SMALLPADS")
      (footprint "eagle-import:JP2_SMALLPADS")
      (libsource (lib "eagle-import") (part "JP2EJP2_SMALLPADS"))
    )
    (comp (ref "JP105")
      (value "JP2E_ORIG")
      (footprint "eagle-import:JP2_ORIG_SMALLPADS")
      (libsource (lib "eagle-import") (part "JP2E_ORIG"))
    )
    (comp (ref "LED101")
      (value "LEDLD260")
      (footprint "eagle-import:LD260")
      (libsource (lib "eagle-import") (part "LEDLD260"))
    )
    (comp (ref "LED102")
      (value "LEDLD260")
      (footprint "eagle-import:LD260")
      (libsource (lib "eagle-import") (part "LEDLD260"))
    )
    (comp (ref "LED103")
      (value "LEDLD260")
      (footprint "eagle-import:LD260")
      (libsource (lib "eagle-import") (part "LEDLD260"))
    )
    (comp (ref "LED104")
      (value "LEDLD260")
      (footprint "eagle-import:LD260")
      (libsource (lib "eagle-import") (part "LEDLD260"))
    )
    (comp (ref "LED105")
      (value "LEDLD260")
      (footprint "eagle-import:LD260")
      (libsource (lib "eagle-import") (part "LEDLD260"))
    )
    (comp (ref "LED106")
      (value "LEDLD260")
      (footprint "eagle-import:LD260")
      (libsource (lib "eagle-import") (part "LEDLD260"))
    )
    (comp (ref "Q1")
      (value "J1")
      (footprint "eagle-import:SOT-23")
      (fields (field (name "MPN") "BSS138W-7-F"))
      (libsource (lib "eagle-import") (part "SMD-MOSFET-N-CH-50V-200MA-BSS138W-7-F(SOT-23)"))
    )
    (comp (ref "Q2")
      (value "BA")
      (footprint "eagle-import:SOT89")
      (libsource (lib "eagle-import") (part "PNP-TRANSISTOR_SOT89"))
    )
    (comp (ref "Q3")
      (value "J1")
      (footprint "eagle-import:SOT-23")
      (fields (field (name "MPN") "BSS138W-7-F"))
      (libsource (lib "eagle-import") (part "SMD-MOSFET-N-CH-50V-200MA-BSS138W-7-F(SOT-23)"))
    )
    (comp (ref "Q101")
      (value "BA.")
      (footprint "eagle-import:SOT89")
      (libsource (lib "eagle-import") (part "PNP-TRANSISTOR_SOT89"))
    )
    (comp (ref "Q102")
      (value "BA.")
      (footprint "eagle-import:SOT89")
      (libsource (lib "eagle-import") (part "PNP-TRANSISTOR_SOT89"))
    )
    (comp (ref "Q103")
      (value "MY")
      (footprint "eagle-import:SOT89")
      (libsource (lib "eagle-import") (part "NPN-TRANSISTOR_SOT89"))
    )
    (comp (ref "Q104")
      (value "BA")
      (footprint "eagle-import:SOT89")
      (libsource (lib "eagle-import") (part "PNP-TRANSISTOR_SOT89"))
    )
    (comp (ref "Q105")
      (value "BA")
      (footprint "eagle-import:SOT89")
      (libsource (lib "eagle-import") (part "PNP-TRANSISTOR_SOT89"))
    )
    (comp (ref "Q106")
      (value "J1")
      (footprint "eagle-import:SOT-23")
      (fields (field (name "MPN") "BSS138W-7-F"))
      (libsource (lib "eagle-import") (part "SMD-MOSFET-N-CH-50V-200MA-BSS138W-7-F(SOT-23)"))
    )
    (comp (ref "Q107")
      (value "J1")
      (footprint "eagle-import:SOT-23")
      (fields (field (name "MPN") "BSS138W-7-F"))
      (libsource (lib "eagle-import") (part "SMD-MOSFET-N-CH-50V-200MA-BSS138W-7-F(SOT-23)"))
    )
    (comp (ref "R1")
      (value "104")
      (footprint "eagle-import:R0805")
      (fields (field (name "MPN") "RC0805FR-0710KL"))
      (libsource (lib "eagle-import") (part "SMD-RES-10K-1%-1/8W(0805)"))
    )
    (comp (ref "R2")
      (value "104")
      (footprint "eagle-import:R0805")
      (fields (field (name "MPN") "RC0805FR-0710KL"))
      (libsource (lib "eagle-import") (part "SMD-RES-10K-1%-1/8W(0805)"))
    )
    (comp (ref "R3")
      (value "104")
      (footprint "eagle-import:R0805")
      (fields (field (name "MPN") "RC0805FR-0710KL"))
      (libsource (lib "eagle-import") (part "SMD-RES-10K-1%-1/8W(0805)"))
    )
    (comp (ref "R4")
      (value "100")
      (footprint "eagle-import:R0805")
      (fields (field (name "MPN") "RC0805JR-07220RL"))
      (libsource (lib "eagle-import") (part "SMD-RES-220R-5%-1/8W(0805)"))
    )
    (comp (ref "R5")
      (value "13")
      (footprint "eagle-import:R1206")
      (fields (field (name "MPN") "RC1206JR-0713RL"))
      (libsource (lib "eagle-import") (part "SMD-RES-13R-5%-1/4W(1206)"))
    )
    (comp (ref "R6")
      (value "2201")
      (footprint "eagle-import:R0805")
      (fields (field (name "MPN") "RC0805JR-071KL"))
      (libsource (lib "eagle-import") (part "SMD-RES-1K-5%-1/8W(0805)"))
    )
    (comp (ref "R8")
      (value "4701")
      (footprint "eagle-import:R0805")
      (fields (field (name "MPN") "RC0805JR-074K7L"))
      (libsource (lib "eagle-import") (part "SMD-RES-4.7K-5%-1/8W(0805)"))
    )
    (comp (ref "R9")
      (value "13")
      (footprint "eagle-import:R1206")
      (fields (field (name "MPN") "RC1206JR-0713RL"))
      (libsource (lib "eagle-import") (part "SMD-RES-13R-5%-1/4W(1206)"))
    )
    (comp (ref "R10")
      (value "104")
      (footprint "eagle-import:R0805")
      (fields (field (name "MPN") "RC0805JR-074K7L"))
      (libsource (lib "eagle-import") (part "SMD-RES-4.7K-5%-1/8W(0805)"))
    )
    (comp (ref "R12")
      (value "100")
      (footprint "eagle-import:R0805")
      (fields (field (name "MPN") "RC0805JR-072K2L"))
      (libsource (lib "eagle-import") (part "SMD-RES-2.2K-5%-1/8W(0805)"))
    )
    (comp (ref "R13")
      (value "100")
      (footprint "eagle-import:R0805")
      (fields (field (name "MPN") "RC0805JR-072K2L"))
      (libsource (lib "eagle-import") (part "SMD-RES-2.2K-5%-1/8W(0805)"))
    )
    (comp (ref "R101")
      (value "102")
      (footprint "eagle-import:R0805")
      (fields (field (name "MPN") "RC0805JR-071KL"))
      (libsource (lib "eagle-import") (part "SMD-RES-1K-5%-1/8W(0805)"))
    )
    (comp (ref "R102")
      (value "13")
      (footprint "eagle-import:R1206")
      (fields (field (name "MPN") "RC1206JR-0713RL"))
      (libsource (lib "eagle-import") (part "SMD-RES-13R-5%-1/4W(1206)"))
    )
    (comp (ref "R103")
      (value "R_user")
      (footprint "eagle-import:R0805")
      (libsource (lib "eagle-import") (part "R-EU_R0805"))
    )
    (comp (ref "R105")
      (value "4701")
      (footprint "eagle-import:R0805")
      (fields (field (name "MPN") "RC0805JR-074K7L"))
      (libsource (lib "eagle-import") (part "SMD-RES-4.7K-5%-1/8W(0805)"))
    )
    (comp (ref "R106")
      (value "13")
      (footprint "eagle-import:R1206")
      (fields (field (name "MPN") "RC1206JR-0713RL"))
      (libsource (lib "eagle-import") (part "SMD-RES-13R-5%-1/4W(1206)"))
    )
    (comp (ref "R107")
      (value "1002")
      (footprint "eagle-import:R0805")
      (fields (field (name "MPN") "RC0805FR-0710KL"))
      (libsource (lib "eagle-import") (part "SMD-RES-10K-1%-1/8W(0805)"))
    )
    (comp (ref "R108")
      (value "1002")
      (footprint "eagle-import:R0805")
      (fields (field (name "MPN") "RC0805FR-0710KL"))
      (libsource (lib "eagle-import") (part "SMD-RES-10K-1%-1/8W(0805)"))
    )
    (comp (ref "R109")
      (value "104")
      (footprint "eagle-import:R0805")
      (fields (field (name "MPN") "RC0805FR-0710KL"))
      (libsource (lib "eagle-import") (part "SMD-RES-10K-1%-1/8W(0805)"))
    )
    (comp (ref "R110")
      (value "104")
      (footprint "eagle-import:R0805")
      (fields (field (name "MPN") "RC0805FR-0710KL"))
      (libsource (lib "eagle-import") (part "SMD-RES-10K-1%-1/8W(0805)"))
    )
    (comp (ref "R111")
      (value "104")
      (footprint "eagle-import:R0805")
      (fields (field (name "MPN") "RC0805FR-0710KL"))
      (libsource (lib "eagle-import") (part "SMD-RES-10K-1%-1/8W(0805)"))
    )
    (comp (ref "R112")
      (value "102")
      (footprint "eagle-import:R0805")
      (fields (field (name "MPN") "RC0805JR-071KL"))
      (libsource (lib "eagle-import") (part "SMD-RES-1K-5%-1/8W(0805)"))
    )
    (comp (ref "R113")
      (value "1002")
      (footprint "eagle-import:R0805")
      (fields (field (name "MPN") "RC0805JR-071KL"))
      (libsource (lib "eagle-import") (part "SMD-RES-1K-5%-1/8W(0805)"))
    )
    (comp (ref "R114")
      (value "1002")
      (footprint "eagle-import:R0805")
      (fields (field (name "MPN") "RC0805JR-071KL"))
      (libsource (lib "eagle-import") (part "SMD-RES-1K-5%-1/8W(0805)"))
    )
    (comp (ref "R115")
      (value "102")
      (footprint "eagle-import:R0805")
      (fields (field (name "MPN") "RC0805JR-07220RL"))
      (libsource (lib "eagle-import") (part "SMD-RES-220R-5%-1/8W(0805)"))
    )
    (comp (ref "R116")
      (value "4701")
      (footprint "eagle-import:R0805")
      (fields (field (name "MPN") "RC0805JR-074K7L"))
      (libsource (lib "eagle-import") (part "SMD-RES-4.7K-5%-1/8W(0805)"))
    )
    (comp (ref "R117")
      (value "2702")
      (footprint "eagle-import:R0805")
      (fields (field (name "MPN") "RC0805JR-074K7L"))
      (libsource (lib "eagle-import") (part "SMD-RES-4.7K-5%-1/8W(0805)"))
    )
    (comp (ref "R119")
      (value "2201")
      (footprint "eagle-import:R0805")
      (fields (field (name "MPN") "RC0805JR-072K2L"))
      (libsource (lib "eagle-import") (part "SMD-RES-2.2K-5%-1/8W(0805)"))
    )
    (comp (ref "R120")
      (value "1002")
      (footprint "eagle-import:R0805")
      (fields (field (name "MPN") "RC0805FR-0710KL"))
      (libsource (lib "eagle-import") (part "SMD-RES-10K-1%-1/8W(0805)"))
    )
    (comp (ref "R121")
      (value "1502")
      (footprint "eagle-import:R0805")
      (fields (field (name "MPN") "RC0805FR-0710KL"))
      (libsource (lib "eagle-import") (part "SMD-RES-10K-1%-1/8W(0805)"))
    )
    (comp (ref "R122")
      (value "2702")
      (footprint "eagle-import:R0805")
      (fields (field (name "MPN") "RC0805JR-074K7L"))
      (libsource (lib "eagle-import") (part "SMD-RES-4.7K-5%-1/8W(0805)"))
    )
    (comp (ref "R123")
      (value "2702")
      (footprint "eagle-import:R0805")
      (fields (field (name "MPN") "RC0805JR-074K7L"))
      (libsource (lib "eagle-import") (part "SMD-RES-4.7K-5%-1/8W(0805)"))
    )
    (comp (ref "R124")
      (value "1002")
      (footprint "eagle-import:R0805")
      (fields (field (name "MPN") "RC0805FR-0710KL"))
      (libsource (lib "eagle-import") (part "SMD-RES-10K-1%-1/8W(0805)"))
    )
    (comp (ref "R125")
      (value "104")
      (footprint "eagle-import:R0805")
      (fields (field (name "MPN") "RC0805FR-0710KL"))
      (libsource (lib "eagle-import") (part "SMD-RES-10K-1%-1/8W(0805)"))
    )
    (comp (ref "R126")
      (value "4701")
      (footprint "eagle-import:R0805")
      (fields (field (name "MPN") "RC0805JR-074K7L"))
      (libsource (lib "eagle-import") (part "SMD-RES-4.7K-5%-1/8W(0805)"))
    )
    (comp (ref "R127")
      (value "47")
      (footprint "eagle-import:V235_17_1MM")
      (libsource (lib "eagle-import") (part "R-EU_V235/17_1MM"))
    )
    (comp (ref "R128")
      (value "102")
      (footprint "eagle-import:R0805")
      (fields (field (name "MPN") "RC0805JR-071KL"))
      (libsource (lib "eagle-import") (part "SMD-RES-1K-5%-1/8W(0805)"))
    )
    (comp (ref "R129")
      (value "47")
      (footprint "eagle-import:V235_17_1MM")
      (libsource (lib "eagle-import") (part "R-EU_V235/17_1MM"))
    )
    (comp (ref "R130")
      (value "104")
      (footprint "eagle-import:R0805")
      (fields (field (name "MPN") "RC0805FR-0710KL"))
      (libsource (lib "eagle-import") (part "SMD-RES-10K-1%-1/8W(0805)"))
    )
    (comp (ref "R131")
      (value "1502")
      (footprint "eagle-import:R0805")
      (fields (field (name "MPN") "RC0805FR-0710KL"))
      (libsource (lib "eagle-import") (part "SMD-RES-10K-1%-1/8W(0805)"))
    )
    (comp (ref "R132")
      (value "1002")
      (footprint "eagle-import:R0805")
      (fields (field (name "MPN") "RC0805FR-0710KL"))
      (libsource (lib "eagle-import") (part "SMD-RES-10K-1%-1/8W(0805)"))
    )
    (comp (ref "R133")
      (value "2201")
      (footprint "eagle-import:R0805")
      (fields (field (name "MPN") "RC0805JR-072K2L"))
      (libsource (lib "eagle-import") (part "SMD-RES-2.2K-5%-1/8W(0805)"))
    )
    (comp (ref "R134")
      (value "13")
      (footprint "eagle-import:R1206")
      (fields (field (name "MPN") "RC1206JR-0713RL"))
      (libsource (lib "eagle-import") (part "SMD-RES-13R-5%-1/4W(1206)"))
    )
    (comp (ref "R135")
      (value "104")
      (footprint "eagle-import:R0805")
      (fields (field (name "MPN") "RC0805FR-0710KL"))
      (libsource (lib "eagle-import") (part "SMD-RES-10K-1%-1/8W(0805)"))
    )
    (comp (ref "R136")
      (value "47")
      (footprint "eagle-import:V235_17_1MM")
      (libsource (lib "eagle-import") (part "R-EU_V235/17_1MM"))
    )
    (comp (ref "R137")
      (value "47")
      (footprint "eagle-import:V235_17_1MM")
      (libsource (lib "eagle-import") (part "R-EU_V235/17_1MM"))
    )
    (comp (ref "R138")
      (value "100")
      (footprint "eagle-import:R0805")
      (fields (field (name "MPN") "RC0805JR-072K2L"))
      (libsource (lib "eagle-import") (part "SMD-RES-2.2K-5%-1/8W(0805)"))
    )
    (comp (ref "R140")
      (value "2702")
      (footprint "eagle-import:R0805")
      (fields (field (name "MPN") "RC0805FR-0710KL"))
      (libsource (lib "eagle-import") (part "SMD-RES-10K-1%-1/8W(0805)"))
    )
    (comp (ref "R141")
      (value "104")
      (footprint "eagle-import:R0805")
      (fields (field (name "MPN") "RC0805FR-0710KL"))
      (libsource (lib "eagle-import") (part "SMD-RES-10K-1%-1/8W(0805)"))
    )
    (comp (ref "R145")
      (value "2702")
      (footprint "eagle-import:R0805")
      (fields (field (name "MPN") "RC0805JR-074K7L"))
      (libsource (lib "eagle-import") (part "SMD-RES-4.7K-5%-1/8W(0805)"))
    )
    (comp (ref "R146")
      (value "1002")
      (footprint "eagle-import:R0805")
      (fields (field (name "MPN") "RC0805JR-074K7L"))
      (libsource (lib "eagle-import") (part "SMD-RES-4.7K-5%-1/8W(0805)"))
    )
    (comp (ref "SJMP")
      (value "SJ")
      (footprint "eagle-import:SJ")
      (libsource (lib "eagle-import") (part "SJ"))
    )
    (comp (ref "START")
      (value "TPSB2.0")
      (footprint "eagle-import:B2.0")
      (libsource (lib "eagle-import") (part "TPSB2.0"))
    )
    (comp (ref "TP1")
      (value "TPSB2.0")
      (footprint "eagle-import:B2.0")
      (libsource (lib "eagle-import") (part "TPSB2.0"))
    )
    (comp (ref "TP2")
      (value "TPSB2.0")
      (footprint "eagle-import:B2.0")
      (libsource (lib "eagle-import") (part "TPSB2.0"))
    )
    (comp (ref "TP3")
      (value "TPSB2.0")
      (footprint "eagle-import:B2.0")
      (libsource (lib "eagle-import") (part "TPSB2.0"))
    )
    (comp (ref "TP4")
      (value "TPSB2.0")
      (footprint "eagle-import:B2.0")
      (libsource (lib "eagle-import") (part "TPSB2.0"))
    )
    (comp (ref "TP5")
      (value "TPSB2.0")
      (footprint "eagle-import:B2.0")
      (libsource (lib "eagle-import") (part "TPSB2.0"))
    )
    (comp (ref "TP6")
      (value "TPSB2.0")
      (footprint "eagle-import:B2.0")
      (libsource (lib "eagle-import") (part "TPSB2.0"))
    )
    (comp (ref "TP7")
      (value "TPSB2.0")
      (footprint "eagle-import:B2.0")
      (libsource (lib "eagle-import") (part "TPSB2.0"))
    )
    (comp (ref "TP8")
      (value "TPSB2.0")
      (footprint "eagle-import:B2.0")
      (libsource (lib "eagle-import") (part "TPSB2.0"))
    )
    (comp (ref "TP9")
      (value "TPSB2.0")
      (footprint "eagle-import:B2.0")
      (libsource (lib "eagle-import") (part "TPSB2.0"))
    )
    (comp (ref "TP10")
      (value "TPSB2.0")
      (footprint "eagle-import:B2.0")
      (libsource (lib "eagle-import") (part "TPSB2.0"))
    )
    (comp (ref "TP11")
      (value "TPSB2.0")
      (footprint "eagle-import:B2.0")
      (libsource (lib "eagle-import") (part "TPSB2.0"))
    )
    (comp (ref "TP12")
      (value "TPSB2.0")
      (footprint "eagle-import:B2.0")
      (libsource (lib "eagle-import") (part "TPSB2.0"))
    )
    (comp (ref "TP13")
      (value "TPSB2.0")
      (footprint "eagle-import:B2.0")
      (libsource (lib "eagle-import") (part "TPSB2.0"))
    )
    (comp (ref "TP16")
      (value "TPSB2.0")
      (footprint "eagle-import:B2.0")
      (libsource (lib "eagle-import") (part "TPSB2.0"))
    )
    (comp (ref "TP17")
      (value "TPSB2.0")
      (footprint "eagle-import:B2.0")
      (libsource (lib "eagle-import") (part "TPSB2.0"))
    )
    (comp (ref "TP18")
      (value "TPSB2.0")
      (footprint "eagle-import:B2.0")
      (libsource (lib "eagle-import") (part "TPSB2.0"))
    )
    (comp (ref "TP19")
      (value "TPSB2.0")
      (footprint "eagle-import:B2.0")
      (libsource (lib "eagle-import") (part "TPSB2.0"))
    )
    (comp (ref "TP21")
      (value "TPSB2.0")
      (footprint "eagle-import:B2.0")
      (libsource (lib "eagle-import") (part "TPSB2.0"))
    )
    (comp (ref "TP22")
      (value "TPSB2.0")
      (footprint "eagle-import:B2.0")
      (libsource (lib "eagle-import") (part "TPSB2.0"))
    )
    (comp (ref "TP23")
      (value "TPSB2.0")
      (footprint "eagle-import:B2.0")
      (libsource (lib "eagle-import") (part "TPSB2.0"))
    )
    (comp (ref "TP24")
      (value "TPSB1,27")
      (footprint "eagle-import:B1,27")
      (libsource (lib "eagle-import") (part "TPSB1,27"))
    )
    (comp (ref "TP25")
      (value "TPSB2.0")
      (footprint "eagle-import:B2.0")
      (libsource (lib "eagle-import") (part "TPSB2.0"))
    )
    (comp (ref "TP26")
      (value "TPSB2.0")
      (footprint "eagle-import:B2.0")
      (libsource (lib "eagle-import") (part "TPSB2.0"))
    )
    (comp (ref "U$13")
      (value "STC")
      (footprint "eagle-import:STENCIL_HOLE")
      (libsource (lib "eagle-import") (part "STC"))
    )
    (comp (ref "U$18")
      (value "STC")
      (footprint "eagle-import:STENCIL_HOLE")
      (libsource (lib "eagle-import") (part "STC"))
    )
    (comp (ref "U$21")
      (value "STC")
      (footprint "eagle-import:STENCIL_HOLE")
      (libsource (lib "eagle-import") (part "STC"))
    )
    (comp (ref "U$22")
      (value "STC")
      (footprint "eagle-import:STENCIL_HOLE")
      (libsource (lib "eagle-import") (part "STC"))
    )
    (comp (ref "X101")
      (value "CON_BMWV2")
      (footprint "eagle-import:24-PIN_V2")
      (libsource (lib "eagle-import") (part "CON_BMWV2"))
    )
    (comp (ref "X102")
      (value "22-23-2021")
      (footprint "eagle-import:22-23-2021")
      (fields (field (name "MF") "MOLEX"))
      (libsource (lib "eagle-import") (part "22-23-2021"))
    )
    (comp (ref "X103")
      (value "22-23-2051")
      (footprint "eagle-import:22-23-2051")
      (fields (field (name "MF") "MOLEX"))
      (libsource (lib "eagle-import") (part "22-23-2051"))
    )
    (comp (ref "6V11")
      (value "TPSB2.0")
      (footprint "eagle-import:B2.0")
      (libsource (lib "eagle-import") (part "TPSB2.0"))
    )
    (comp (ref "10V11")
      (value "TPSB2.0")
      (footprint "eagle-import:B2.0")
      (libsource (lib "eagle-import") (part "TPSB2.0"))
    )
    (comp (ref "23")
      (value "2081-1132")
      (footprint "eagle-import:12-PIN")
      (libsource (lib "eagle-import") (part "2081-1132"))
    )
    (comp (ref "24")
      (value "2081-1132")
      (footprint "eagle-import:12-PIN")
      (libsource (lib "eagle-import") (part "2081-1132"))
    )
    (comp (ref "C133")
      (value "100u")
      (footprint "eagle-import:C1206")
      (fields (field (name "MPN") "GRM31CR60J107ME39L"))
      (libsource (lib "eagle-import") (part "CERAMIC-100UF-6.3V-20%-X5R(1206)"))
    )
    (comp (ref "C134")
      (value "100u")
      (footprint "eagle-import:C1206")
      (fields (field (name "MPN") "GRM31CR60J107ME39L"))
      (libsource (lib "eagle-import") (part "CERAMIC-100UF-6.3V-20%-X5R(1206)"))
    )
    (comp (ref "C135")
      (value "100nF,")
      (footprint "eagle-import:C0805")
      (fields (field (name "MPN") "CC0805KRX7R9BB104"))
      (libsource (lib "eagle-import") (part "CERAMIC-100NF-50V-10%-X7R(0805)"))
    )
    (comp (ref "C136")
      (value "4.7u")
      (footprint "eagle-import:C0805")
      (fields (field (name "MPN") "CC0805KKX5R8BB475"))
      (libsource (lib "eagle-import") (part "CERAMIC-4.7UF-25V-10%-X5R(0805)"))
    )
    (comp (ref "C137")
      (value "100nF.")
      (footprint "eagle-import:C0805")
      (fields (field (name "MPN") "CC0805KRX7R9BB104"))
      (libsource (lib "eagle-import") (part "CERAMIC-100NF-50V-10%-X7R(0805)"))
    )
    (comp (ref "C138")
      (value "100nF.")
      (footprint "eagle-import:C0805")
      (fields (field (name "MPN") "CC0805KRX7R9BB104"))
      (libsource (lib "eagle-import") (part "CERAMIC-100NF-50V-10%-X7R(0805)"))
    )
    (comp (ref "C139")
      (value "2.2nF")
      (footprint "eagle-import:C0805")
      (fields (field (name "MPN") "CC0805KRX7R9BB104"))
      (libsource (lib "eagle-import") (part "CERAMIC-100NF-50V-10%-X7R(0805)"))
    )
    (comp (ref "C140")
      (value "100nF")
      (footprint "eagle-import:C0805")
      (fields (field (name "MPN") "CC0805KRX7R9BB104"))
      (libsource (lib "eagle-import") (part "CERAMIC-100NF-50V-10%-X7R(0805)"))
    )
    (comp (ref "C141")
      (value "100nF")
      (footprint "eagle-import:C0805")
      (fields (field (name "MPN") "CC0805KRX7R9BB104"))
      (libsource (lib "eagle-import") (part "CERAMIC-100NF-50V-10%-X7R(0805)"))
    )
    (comp (ref "C142")
      (value "100nF,")
      (footprint "eagle-import:C0805")
      (fields (field (name "MPN") "CC0805KRX7R9BB104"))
      (libsource (lib "eagle-import") (part "CERAMIC-100NF-50V-10%-X7R(0805)"))
    )
    (comp (ref "C143")
      (value "4.7u")
      (footprint "eagle-import:C0805")
      (fields (field (name "MPN") "CC0805KKX5R8BB475"))
      (libsource (lib "eagle-import") (part "CERAMIC-4.7UF-25V-10%-X5R(0805)"))
    )
    (comp (ref "C144")
      (value "10u")
      (footprint "eagle-import:C1206")
      (fields (field (name "MPN") "GRM31CR60J107ME39L"))
      (libsource (lib "eagle-import") (part "CERAMIC-100UF-6.3V-20%-X5R(1206)"))
    )
    (comp (ref "D144")
      (value "1N4007,")
      (footprint "eagle-import:DO-214AC")
      (fields (field (name "MPN") "1N4007"))
      (libsource (lib "eagle-import") (part "DIODE-GEN-PURPOSE-1KV-1A(DO-214AC)"))
    )
    (comp (ref "D145")
      (value "1N4007,")
      (footprint "eagle-import:DO-214AC")
      (fields (field (name "MPN") "1N4007"))
      (libsource (lib "eagle-import") (part "DIODE-GEN-PURPOSE-1KV-1A(DO-214AC)"))
    )
    (comp (ref "D146")
      (value "1N4007.")
      (footprint "eagle-import:DO-214AC")
      (fields (field (name "MPN") "1N4007"))
      (libsource (lib "eagle-import") (part "DIODE-GEN-PURPOSE-1KV-1A(DO-214AC)"))
    )
    (comp (ref "D147")
      (value "1N5817")
      (footprint "eagle-import:DO-214AC_SLIM")
      (libsource (lib "eagle-import") (part "DIODE-GEN-PURPOSE-1KV-1A(DO-214AC)DO-214AC/1206"))
    )
    (comp (ref "D148")
      (value "1N5817.")
      (footprint "eagle-import:DO-214AC_SLIM")
      (libsource (lib "eagle-import") (part "DIODE-GEN-PURPOSE-1KV-1A(DO-214AC)DO-214AC/1206"))
    )
    (comp (ref "D149")
      (value "1N5817.")
      (footprint "eagle-import:DO-214AC_SLIM")
      (libsource (lib "eagle-import") (part "DIODE-GEN-PURPOSE-1KV-1A(DO-214AC)DO-214AC/1206"))
    )
    (comp (ref "D150")
      (value "1N5817")
      (footprint "eagle-import:DO-214AC_SLIM")
      (libsource (lib "eagle-import") (part "DIODE-GEN-PURPOSE-1KV-1A(DO-214AC)DO-214AC/1206"))
    )
    (comp (ref "D151")
      (value "1N4007.")
      (footprint "eagle-import:DO-214AC")
      (fields (field (name "MPN") "1N4007"))
      (libsource (lib "eagle-import") (part "DIODE-GEN-PURPOSE-1KV-1A(DO-214AC)"))
    )
    (comp (ref "D152")
      (value "1N4007")
      (footprint "eagle-import:DO-214AC")
      (libsource (lib "eagle-import") (part "DIODE-GEN-PURPOSE-1KV-1A(DO-214AC)"))
    )
    (comp (ref "D153")
      (value "Zen15")
      (footprint "eagle-import:DO214AA")
      (libsource (lib "eagle-import") (part "SM6T"))
    )
    (comp (ref "D154")
      (value "SS12")
      (footprint "eagle-import:DO-214AC_SLIM")
      (libsource (lib "eagle-import") (part "DIODE-GEN-PURPOSE-1KV-1A(DO-214AC)DO-214AC/1206"))
    )
    (comp (ref "D155")
      (value "SS12")
      (footprint "eagle-import:DO-214AC_SLIM")
      (libsource (lib "eagle-import") (part "DIODE-GEN-PURPOSE-1KV-1A(DO-214AC)DO-214AC/1206"))
    )
    (comp (ref "D156")
      (value "Zen11")
      (footprint "eagle-import:SOD-123_MINI-SMA")
      (libsource (lib "eagle-import") (part "CGRM400-G1"))
    )
    (comp (ref "FID45")
      (value "FIDUCIAL")
      (footprint "eagle-import:FIDUCIAL_1MM")
      (libsource (lib "eagle-import") (part "FIDUCIAL"))
    )
    (comp (ref "FID46")
      (value "FIDUCIAL")
      (footprint "eagle-import:FIDUCIAL_1MM")
      (libsource (lib "eagle-import") (part "FIDUCIAL"))
    )
    (comp (ref "FID47")
      (value "FIDUCIAL")
      (footprint "eagle-import:FIDUCIAL_1MM")
      (libsource (lib "eagle-import") (part "FIDUCIAL"))
    )
    (comp (ref "FID48")
      (value "FIDUCIAL")
      (footprint "eagle-import:FIDUCIAL_1MM")
      (libsource (lib "eagle-import") (part "FIDUCIAL"))
    )
    (comp (ref "IC91")
      (value "4028")
      (footprint "eagle-import:SO16")
      (libsource (lib "eagle-import") (part "4028D"))
    )
    (comp (ref "IC92")
      (value "317TO202H_NOHOLE")
      (footprint "eagle-import:TO220H_NOHOLE")
      (libsource (lib "eagle-import") (part "317TO202H_NOHOLE"))
    )
    (comp (ref "IC93")
      (value "ULN2004")
      (footprint "eagle-import:SO16")
      (libsource (lib "eagle-import") (part "ULN2004AD"))
    )
    (comp (ref "IC94")
      (value "LM339")
      (footprint "eagle-import:SO14")
      (libsource (lib "eagle-import") (part "LM339D"))
    )
    (comp (ref "IC95")
      (value "78L06")
      (footprint "eagle-import:SOT89_ROUND")
      (libsource (lib "eagle-import") (part "78LXXSOT89_ROUND"))
    )
    (comp (ref "IC96")
      (value "555")
      (footprint "eagle-import:SO08")
      (libsource (lib "eagle-import") (part "555DNE"))
    )
    (comp (ref "IC97")
      (value "4538")
      (footprint "eagle-import:SO16")
      (libsource (lib "eagle-import") (part "4538D"))
    )
    (comp (ref "IC98")
      (value "78L10")
      (footprint "eagle-import:SOT89_ROUND")
      (libsource (lib "eagle-import") (part "78LXXSOT89_ROUND"))
    )
    (comp (ref "IC99")
      (value "LM2904")
      (footprint "eagle-import:SO08")
      (libsource (lib "eagle-import") (part "LM358D"))
    )
    (comp (ref "JP51")
      (value "JP2EJP2_SMALLPADS")
      (footprint "eagle-import:JP2_SMALLPADS")
      (libsource (lib "eagle-import") (part "JP2EJP2_SMALLPADS"))
    )
    (comp (ref "JP52")
      (value "JP2E_ORIG")
      (footprint "eagle-import:JP2_ORIG_SMALLPADS")
      (libsource (lib "eagle-import") (part "JP2E_ORIG"))
    )
    (comp (ref "JP53")
      (value "JP2EJP2_SMALLPADS")
      (footprint "eagle-import:JP2_SMALLPADS")
      (libsource (lib "eagle-import") (part "JP2EJP2_SMALLPADS"))
    )
    (comp (ref "JP54")
      (value "JP2EJP2_SMALLPADS")
      (footprint "eagle-import:JP2_SMALLPADS")
      (libsource (lib "eagle-import") (part "JP2EJP2_SMALLPADS"))
    )
    (comp (ref "JP55")
      (value "JP2EJP2_SMALLPADS")
      (footprint "eagle-import:JP2_SMALLPADS")
      (libsource (lib "eagle-import") (part "JP2EJP2_SMALLPADS"))
    )
    (comp (ref "LED61")
      (value "LEDLD260")
      (footprint "eagle-import:LD260")
      (libsource (lib "eagle-import") (part "LEDLD260"))
    )
    (comp (ref "LED62")
      (value "LEDLD260")
      (footprint "eagle-import:LD260")
      (libsource (lib "eagle-import") (part "LEDLD260"))
    )
    (comp (ref "LED63")
      (value "LEDLD260")
      (footprint "eagle-import:LD260")
      (libsource (lib "eagle-import") (part "LEDLD260"))
    )
    (comp (ref "LED64")
      (value "LEDLD260")
      (footprint "eagle-import:LD260")
      (libsource (lib "eagle-import") (part "LEDLD260"))
    )
    (comp (ref "LED65")
      (value "LEDLD260")
      (footprint "eagle-import:LD260")
      (libsource (lib "eagle-import") (part "LEDLD260"))
    )
    (comp (ref "LED66")
      (value "LEDLD260")
      (footprint "eagle-import:LD260")
      (libsource (lib "eagle-import") (part "LEDLD260"))
    )
    (comp (ref "Q111")
      (value "BA")
      (footprint "eagle-import:SOT89")
      (libsource (lib "eagle-import") (part "PNP-TRANSISTOR_SOT89"))
    )
    (comp (ref "Q112")
      (value "BA.")
      (footprint "eagle-import:SOT89")
      (libsource (lib "eagle-import") (part "PNP-TRANSISTOR_SOT89"))
    )
    (comp (ref "Q113")
      (value "BA.")
      (footprint "eagle-import:SOT89")
      (libsource (lib "eagle-import") (part "PNP-TRANSISTOR_SOT89"))
    )
    (comp (ref "Q114")
      (value "BA")
      (footprint "eagle-import:SOT89")
      (libsource (lib "eagle-import") (part "PNP-TRANSISTOR_SOT89"))
    )
    (comp (ref "Q115")
      (value "MY")
      (footprint "eagle-import:SOT89")
      (libsource (lib "eagle-import") (part "NPN-TRANSISTOR_SOT89"))
    )
    (comp (ref "Q116")
      (value "J1")
      (footprint "eagle-import:SOT-23")
      (fields (field (name "MPN") "BSS138W-7-F"))
      (libsource (lib "eagle-import") (part "SMD-MOSFET-N-CH-50V-200MA-BSS138W-7-F(SOT-23)"))
    )
    (comp (ref "Q117")
      (value "J1")
      (footprint "eagle-import:SOT-23")
      (fields (field (name "MPN") "BSS138W-7-F"))
      (libsource (lib "eagle-import") (part "SMD-MOSFET-N-CH-50V-200MA-BSS138W-7-F(SOT-23)"))
    )
    (comp (ref "Q118")
      (value "J1")
      (footprint "eagle-import:SOT-23")
      (fields (field (name "MPN") "BSS138W-7-F"))
      (libsource (lib "eagle-import") (part "SMD-MOSFET-N-CH-50V-200MA-BSS138W-7-F(SOT-23)"))
    )
    (comp (ref "Q119")
      (value "BA")
      (footprint "eagle-import:SOT89")
      (libsource (lib "eagle-import") (part "PNP-TRANSISTOR_SOT89"))
    )
    (comp (ref "Q120")
      (value "J1")
      (footprint "eagle-import:SOT-23")
      (fields (field (name "MPN") "BSS138W-7-F"))
      (libsource (lib "eagle-import") (part "SMD-MOSFET-N-CH-50V-200MA-BSS138W-7-F(SOT-23)"))
    )
    (comp (ref "R562")
      (value "47")
      (footprint "eagle-import:V235_17_1MM")
      (libsource (lib "eagle-import") (part "R-EU_V235/17_1MM"))
    )
    (comp (ref "R563")
      (value "13")
      (footprint "eagle-import:R1206")
      (fields (field (name "MPN") "RC1206JR-0713RL"))
      (libsource (lib "eagle-import") (part "SMD-RES-13R-5%-1/4W(1206)"))
    )
    (comp (ref "R564")
      (value "47")
      (footprint "eagle-import:V235_17_1MM")
      (libsource (lib "eagle-import") (part "R-EU_V235/17_1MM"))
    )
    (comp (ref "R565")
      (value "104")
      (footprint "eagle-import:R0805")
      (fields (field (name "MPN") "RC0805FR-0710KL"))
      (libsource (lib "eagle-import") (part "SMD-RES-10K-1%-1/8W(0805)"))
    )
    (comp (ref "R566")
      (value "104")
      (footprint "eagle-import:R0805")
      (fields (field (name "MPN") "RC0805FR-0710KL"))
      (libsource (lib "eagle-import") (part "SMD-RES-10K-1%-1/8W(0805)"))
    )
    (comp (ref "R567")
      (value "104")
      (footprint "eagle-import:R0805")
      (fields (field (name "MPN") "RC0805FR-0710KL"))
      (libsource (lib "eagle-import") (part "SMD-RES-10K-1%-1/8W(0805)"))
    )
    (comp (ref "R568")
      (value "4701")
      (footprint "eagle-import:R0805")
      (fields (field (name "MPN") "RC0805JR-074K7L"))
      (libsource (lib "eagle-import") (part "SMD-RES-4.7K-5%-1/8W(0805)"))
    )
    (comp (ref "R569")
      (value "1002")
      (footprint "eagle-import:R0805")
      (fields (field (name "MPN") "RC0805FR-0710KL"))
      (libsource (lib "eagle-import") (part "SMD-RES-10K-1%-1/8W(0805)"))
    )
    (comp (ref "R570")
      (value "1002")
      (footprint "eagle-import:R0805")
      (fields (field (name "MPN") "RC0805FR-0710KL"))
      (libsource (lib "eagle-import") (part "SMD-RES-10K-1%-1/8W(0805)"))
    )
    (comp (ref "R571")
      (value "1502")
      (footprint "eagle-import:R0805")
      (fields (field (name "MPN") "RC0805FR-0710KL"))
      (libsource (lib "eagle-import") (part "SMD-RES-10K-1%-1/8W(0805)"))
    )
    (comp (ref "R572")
      (value "104")
      (footprint "eagle-import:R0805")
      (fields (field (name "MPN") "RC0805FR-0710KL"))
      (libsource (lib "eagle-import") (part "SMD-RES-10K-1%-1/8W(0805)"))
    )
    (comp (ref "R573")
      (value "104")
      (footprint "eagle-import:R0805")
      (fields (field (name "MPN") "RC0805FR-0710KL"))
      (libsource (lib "eagle-import") (part "SMD-RES-10K-1%-1/8W(0805)"))
    )
    (comp (ref "R574")
      (value "1502")
      (footprint "eagle-import:R0805")
      (fields (field (name "MPN") "RC0805FR-0710KL"))
      (libsource (lib "eagle-import") (part "SMD-RES-10K-1%-1/8W(0805)"))
    )
    (comp (ref "R575")
      (value "1002")
      (footprint "eagle-import:R0805")
      (fields (field (name "MPN") "RC0805FR-0710KL"))
      (libsource (lib "eagle-import") (part "SMD-RES-10K-1%-1/8W(0805)"))
    )
    (comp (ref "R576")
      (value "2201")
      (footprint "eagle-import:R0805")
      (fields (field (name "MPN") "RC0805JR-072K2L"))
      (libsource (lib "eagle-import") (part "SMD-RES-2.2K-5%-1/8W(0805)"))
    )
    (comp (ref "R577")
      (value "1002")
      (footprint "eagle-import:R0805")
      (fields (field (name "MPN") "RC0805FR-0710KL"))
      (libsource (lib "eagle-import") (part "SMD-RES-10K-1%-1/8W(0805)"))
    )
    (comp (ref "R578")
      (value "4701")
      (footprint "eagle-import:R0805")
      (fields (field (name "MPN") "RC0805JR-074K7L"))
      (libsource (lib "eagle-import") (part "SMD-RES-4.7K-5%-1/8W(0805)"))
    )
    (comp (ref "R579")
      (value "2702")
      (footprint "eagle-import:R0805")
      (fields (field (name "MPN") "RC0805JR-074K7L"))
      (libsource (lib "eagle-import") (part "SMD-RES-4.7K-5%-1/8W(0805)"))
    )
    (comp (ref "R580")
      (value "102")
      (footprint "eagle-import:R0805")
      (fields (field (name "MPN") "RC0805JR-071KL"))
      (libsource (lib "eagle-import") (part "SMD-RES-1K-5%-1/8W(0805)"))
    )
    (comp (ref "R581")
      (value "102")
      (footprint "eagle-import:R0805")
      (fields (field (name "MPN") "RC0805JR-07220RL"))
      (libsource (lib "eagle-import") (part "SMD-RES-220R-5%-1/8W(0805)"))
    )
    (comp (ref "R582")
      (value "102")
      (footprint "eagle-import:R0805")
      (fields (field (name "MPN") "RC0805JR-071KL"))
      (libsource (lib "eagle-import") (part "SMD-RES-1K-5%-1/8W(0805)"))
    )
    (comp (ref "R583")
      (value "13")
      (footprint "eagle-import:R1206")
      (fields (field (name "MPN") "RC1206JR-0713RL"))
      (libsource (lib "eagle-import") (part "SMD-RES-13R-5%-1/4W(1206)"))
    )
    (comp (ref "R584")
      (value "13")
      (footprint "eagle-import:R1206")
      (fields (field (name "MPN") "RC1206JR-0713RL"))
      (libsource (lib "eagle-import") (part "SMD-RES-13R-5%-1/4W(1206)"))
    )
    (comp (ref "R585")
      (value "2702")
      (footprint "eagle-import:R0805")
      (fields (field (name "MPN") "RC0805JR-074K7L"))
      (libsource (lib "eagle-import") (part "SMD-RES-4.7K-5%-1/8W(0805)"))
    )
    (comp (ref "R586")
      (value "4701")
      (footprint "eagle-import:R0805")
      (fields (field (name "MPN") "RC0805JR-074K7L"))
      (libsource (lib "eagle-import") (part "SMD-RES-4.7K-5%-1/8W(0805)"))
    )
    (comp (ref "R587")
      (value "100")
      (footprint "eagle-import:R0805")
      (fields (field (name "MPN") "RC0805JR-072K2L"))
      (libsource (lib "eagle-import") (part "SMD-RES-2.2K-5%-1/8W(0805)"))
    )
    (comp (ref "R588")
      (value "104")
      (footprint "eagle-import:R0805")
      (fields (field (name "MPN") "RC0805FR-0710KL"))
      (libsource (lib "eagle-import") (part "SMD-RES-10K-1%-1/8W(0805)"))
    )
    (comp (ref "R589")
      (value "104")
      (footprint "eagle-import:R0805")
      (fields (field (name "MPN") "RC0805FR-0710KL"))
      (libsource (lib "eagle-import") (part "SMD-RES-10K-1%-1/8W(0805)"))
    )
    (comp (ref "R590")
      (value "2702")
      (footprint "eagle-import:R0805")
      (fields (field (name "MPN") "RC0805FR-0710KL"))
      (libsource (lib "eagle-import") (part "SMD-RES-10K-1%-1/8W(0805)"))
    )
    (comp (ref "R591")
      (value "47")
      (footprint "eagle-import:V235_17_1MM")
      (libsource (lib "eagle-import") (part "R-EU_V235/17_1MM"))
    )
    (comp (ref "R592")
      (value "47")
      (footprint "eagle-import:V235_17_1MM")
      (libsource (lib "eagle-import") (part "R-EU_V235/17_1MM"))
    )
    (comp (ref "R593")
      (value "2702")
      (footprint "eagle-import:R0805")
      (fields (field (name "MPN") "RC0805JR-074K7L"))
      (libsource (lib "eagle-import") (part "SMD-RES-4.7K-5%-1/8W(0805)"))
    )
    (comp (ref "R594")
      (value "2201")
      (footprint "eagle-import:R0805")
      (fields (field (name "MPN") "RC0805JR-072K2L"))
      (libsource (lib "eagle-import") (part "SMD-RES-2.2K-5%-1/8W(0805)"))
    )
    (comp (ref "R595")
      (value "1002")
      (footprint "eagle-import:R0805")
      (fields (field (name "MPN") "RC0805JR-074K7L"))
      (libsource (lib "eagle-import") (part "SMD-RES-4.7K-5%-1/8W(0805)"))
    )
    (comp (ref "R596")
      (value "1002")
      (footprint "eagle-import:R0805")
      (fields (field (name "MPN") "RC0805FR-0710KL"))
      (libsource (lib "eagle-import") (part "SMD-RES-10K-1%-1/8W(0805)"))
    )
    (comp (ref "R597")
      (value "102")
      (footprint "eagle-import:R0805")
      (fields (field (name "MPN") "RC0805JR-071KL"))
      (libsource (lib "eagle-import") (part "SMD-RES-1K-5%-1/8W(0805)"))
    )
    (comp (ref "R598")
      (value "2702")
      (footprint "eagle-import:R0805")
      (fields (field (name "MPN") "RC0805JR-074K7L"))
      (libsource (lib "eagle-import") (part "SMD-RES-4.7K-5%-1/8W(0805)"))
    )
    (comp (ref "R599")
      (value "1002")
      (footprint "eagle-import:R0805")
      (fields (field (name "MPN") "RC0805JR-071KL"))
      (libsource (lib "eagle-import") (part "SMD-RES-1K-5%-1/8W(0805)"))
    )
    (comp (ref "R600")
      (value "1002")
      (footprint "eagle-import:R0805")
      (fields (field (name "MPN") "RC0805JR-071KL"))
      (libsource (lib "eagle-import") (part "SMD-RES-1K-5%-1/8W(0805)"))
    )
    (comp (ref "R601")
      (value "R_user")
      (footprint "eagle-import:R0805")
      (libsource (lib "eagle-import") (part "R-EU_R0805"))
    )
    (comp (ref "R602")
      (value "104")
      (footprint "eagle-import:R0805")
      (fields (field (name "MPN") "RC0805FR-0710KL"))
      (libsource (lib "eagle-import") (part "SMD-RES-10K-1%-1/8W(0805)"))
    )
    (comp (ref "R603")
      (value "104")
      (footprint "eagle-import:R0805")
      (fields (field (name "MPN") "RC0805FR-0710KL"))
      (libsource (lib "eagle-import") (part "SMD-RES-10K-1%-1/8W(0805)"))
    )
    (comp (ref "R604")
      (value "104")
      (footprint "eagle-import:R0805")
      (fields (field (name "MPN") "RC0805FR-0710KL"))
      (libsource (lib "eagle-import") (part "SMD-RES-10K-1%-1/8W(0805)"))
    )
    (comp (ref "R605")
      (value "13")
      (footprint "eagle-import:R1206")
      (fields (field (name "MPN") "RC1206JR-0713RL"))
      (libsource (lib "eagle-import") (part "SMD-RES-13R-5%-1/4W(1206)"))
    )
    (comp (ref "R606")
      (value "2201")
      (footprint "eagle-import:R0805")
      (fields (field (name "MPN") "RC0805JR-071KL"))
      (libsource (lib "eagle-import") (part "SMD-RES-1K-5%-1/8W(0805)"))
    )
    (comp (ref "R607")
      (value "100")
      (footprint "eagle-import:R0805")
      (fields (field (name "MPN") "RC0805JR-07220RL"))
      (libsource (lib "eagle-import") (part "SMD-RES-220R-5%-1/8W(0805)"))
    )
    (comp (ref "R608")
      (value "13")
      (footprint "eagle-import:R1206")
      (fields (field (name "MPN") "RC1206JR-0713RL"))
      (libsource (lib "eagle-import") (part "SMD-RES-13R-5%-1/4W(1206)"))
    )
    (comp (ref "R609")
      (value "4701")
      (footprint "eagle-import:R0805")
      (fields (field (name "MPN") "RC0805JR-074K7L"))
      (libsource (lib "eagle-import") (part "SMD-RES-4.7K-5%-1/8W(0805)"))
    )
    (comp (ref "R610")
      (value "104")
      (footprint "eagle-import:R0805")
      (fields (field (name "MPN") "RC0805JR-074K7L"))
      (libsource (lib "eagle-import") (part "SMD-RES-4.7K-5%-1/8W(0805)"))
    )
    (comp (ref "R611")
      (value "100")
      (footprint "eagle-import:R0805")
      (fields (field (name "MPN") "RC0805JR-072K2L"))
      (libsource (lib "eagle-import") (part "SMD-RES-2.2K-5%-1/8W(0805)"))
    )
    (comp (ref "R612")
      (value "100")
      (footprint "eagle-import:R0805")
      (fields (field (name "MPN") "RC0805JR-072K2L"))
      (libsource (lib "eagle-import") (part "SMD-RES-2.2K-5%-1/8W(0805)"))
    )
    (comp (ref "SJMP11")
      (value "SJ")
      (footprint "eagle-import:SJ")
      (libsource (lib "eagle-import") (part "SJ"))
    )
    (comp (ref "START11")
      (value "TPSB2.0")
      (footprint "eagle-import:B2.0")
      (libsource (lib "eagle-import") (part "TPSB2.0"))
    )
    (comp (ref "TP254")
      (value "TPSB2.0")
      (footprint "eagle-import:B2.0")
      (libsource (lib "eagle-import") (part "TPSB2.0"))
    )
    (comp (ref "TP255")
      (value "TPSB2.0")
      (footprint "eagle-import:B2.0")
      (libsource (lib "eagle-import") (part "TPSB2.0"))
    )
    (comp (ref "TP256")
      (value "TPSB2.0")
      (footprint "eagle-import:B2.0")
      (libsource (lib "eagle-import") (part "TPSB2.0"))
    )
    (comp (ref "TP257")
      (value "TPSB2.0")
      (footprint "eagle-import:B2.0")
      (libsource (lib "eagle-import") (part "TPSB2.0"))
    )
    (comp (ref "TP258")
      (value "TPSB2.0")
      (footprint "eagle-import:B2.0")
      (libsource (lib "eagle-import") (part "TPSB2.0"))
    )
    (comp (ref "TP259")
      (value "TPSB2.0")
      (footprint "eagle-import:B2.0")
      (libsource (lib "eagle-import") (part "TPSB2.0"))
    )
    (comp (ref "TP260")
      (value "TPSB2.0")
      (footprint "eagle-import:B2.0")
      (libsource (lib "eagle-import") (part "TPSB2.0"))
    )
    (comp (ref "TP261")
      (value "TPSB2.0")
      (footprint "eagle-import:B2.0")
      (libsource (lib "eagle-import") (part "TPSB2.0"))
    )
    (comp (ref "TP262")
      (value "TPSB2.0")
      (footprint "eagle-import:B2.0")
      (libsource (lib "eagle-import") (part "TPSB2.0"))
    )
    (comp (ref "TP263")
      (value "TPSB2.0")
      (footprint "eagle-import:B2.0")
      (libsource (lib "eagle-import") (part "TPSB2.0"))
    )
    (comp (ref "TP264")
      (value "TPSB2.0")
      (footprint "eagle-import:B2.0")
      (libsource (lib "eagle-import") (part "TPSB2.0"))
    )
    (comp (ref "TP265")
      (value "TPSB2.0")
      (footprint "eagle-import:B2.0")
      (libsource (lib "eagle-import") (part "TPSB2.0"))
    )
    (comp (ref "TP266")
      (value "TPSB2.0")
      (footprint "eagle-import:B2.0")
      (libsource (lib "eagle-import") (part "TPSB2.0"))
    )
    (comp (ref "TP267")
      (value "TPSB2.0")
      (footprint "eagle-import:B2.0")
      (libsource (lib "eagle-import") (part "TPSB2.0"))
    )
    (comp (ref "TP268")
      (value "TPSB2.0")
      (footprint "eagle-import:B2.0")
      (libsource (lib "eagle-import") (part "TPSB2.0"))
    )
    (comp (ref "TP269")
      (value "TPSB2.0")
      (footprint "eagle-import:B2.0")
      (libsource (lib "eagle-import") (part "TPSB2.0"))
    )
    (comp (ref "TP270")
      (value "TPSB2.0")
      (footprint "eagle-import:B2.0")
      (libsource (lib "eagle-import") (part "TPSB2.0"))
    )
    (comp (ref "TP271")
      (value "TPSB2.0")
      (footprint "eagle-import:B2.0")
      (libsource (lib "eagle-import") (part "TPSB2.0"))
    )
    (comp (ref "TP272")
      (value "TPSB1,27")
      (footprint "eagle-import:B1,27")
      (libsource (lib "eagle-import") (part "TPSB1,27"))
    )
    (comp (ref "TP273")
      (value "TPSB2.0")
      (footprint "eagle-import:B2.0")
      (libsource (lib "eagle-import") (part "TPSB2.0"))
    )
    (comp (ref "TP274")
      (value "TPSB2.0")
      (footprint "eagle-import:B2.0")
      (libsource (lib "eagle-import") (part "TPSB2.0"))
    )
    (comp (ref "TP275")
      (value "TPSB2.0")
      (footprint "eagle-import:B2.0")
      (libsource (lib "eagle-import") (part "TPSB2.0"))
    )
    (comp (ref "TP276")
      (value "TPSB2.0")
      (footprint "eagle-import:B2.0")
      (libsource (lib "eagle-import") (part "TPSB2.0"))
    )
    (comp (ref "X31")
      (value "CON_BMWV2")
      (footprint "eagle-import:24-PIN_V2")
      (libsource (lib "eagle-import") (part "CON_BMWV2"))
    )
    (comp (ref "X32")
      (value "22-23-2051")
      (footprint "eagle-import:22-23-2051")
      (fields (field (name "MF") "MOLEX"))
      (libsource (lib "eagle-import") (part "22-23-2051"))
    )
    (comp (ref "X33")
      (value "22-23-2021")
      (footprint "eagle-import:22-23-2021")
      (fields (field (name "MF") "MOLEX"))
      (libsource (lib "eagle-import") (part "22-23-2021"))
    )
    (comp (ref "6V5")
      (value "TPSB2.0")
      (footprint "eagle-import:B2.0")
      (libsource (lib "eagle-import") (part "TPSB2.0"))
    )
    (comp (ref "10V5")
      (value "TPSB2.0")
      (footprint "eagle-import:B2.0")
      (libsource (lib "eagle-import") (part "TPSB2.0"))
    )
    (comp (ref "11")
      (value "2081-1132")
      (footprint "eagle-import:12-PIN")
      (libsource (lib "eagle-import") (part "2081-1132"))
    )
    (comp (ref "12")
      (value "2081-1132")
      (footprint "eagle-import:12-PIN")
      (libsource (lib "eagle-import") (part "2081-1132"))
    )
    (comp (ref "C51")
      (value "100u")
      (footprint "eagle-import:C1206")
      (fields (field (name "MPN") "GRM31CR60J107ME39L"))
      (libsource (lib "eagle-import") (part "CERAMIC-100UF-6.3V-20%-X5R(1206)"))
    )
    (comp (ref "C52")
      (value "100u")
      (footprint "eagle-import:C1206")
      (fields (field (name "MPN") "GRM31CR60J107ME39L"))
      (libsource (lib "eagle-import") (part "CERAMIC-100UF-6.3V-20%-X5R(1206)"))
    )
    (comp (ref "C53")
      (value "100nF,")
      (footprint "eagle-import:C0805")
      (fields (field (name "MPN") "CC0805KRX7R9BB104"))
      (libsource (lib "eagle-import") (part "CERAMIC-100NF-50V-10%-X7R(0805)"))
    )
    (comp (ref "C54")
      (value "4.7u")
      (footprint "eagle-import:C0805")
      (fields (field (name "MPN") "CC0805KKX5R8BB475"))
      (libsource (lib "eagle-import") (part "CERAMIC-4.7UF-25V-10%-X5R(0805)"))
    )
    (comp (ref "C55")
      (value "100nF.")
      (footprint "eagle-import:C0805")
      (fields (field (name "MPN") "CC0805KRX7R9BB104"))
      (libsource (lib "eagle-import") (part "CERAMIC-100NF-50V-10%-X7R(0805)"))
    )
    (comp (ref "C56")
      (value "100nF.")
      (footprint "eagle-import:C0805")
      (fields (field (name "MPN") "CC0805KRX7R9BB104"))
      (libsource (lib "eagle-import") (part "CERAMIC-100NF-50V-10%-X7R(0805)"))
    )
    (comp (ref "C57")
      (value "2.2nF")
      (footprint "eagle-import:C0805")
      (fields (field (name "MPN") "CC0805KRX7R9BB104"))
      (libsource (lib "eagle-import") (part "CERAMIC-100NF-50V-10%-X7R(0805)"))
    )
    (comp (ref "C58")
      (value "100nF")
      (footprint "eagle-import:C0805")
      (fields (field (name "MPN") "CC0805KRX7R9BB104"))
      (libsource (lib "eagle-import") (part "CERAMIC-100NF-50V-10%-X7R(0805)"))
    )
    (comp (ref "C59")
      (value "100nF")
      (footprint "eagle-import:C0805")
      (fields (field (name "MPN") "CC0805KRX7R9BB104"))
      (libsource (lib "eagle-import") (part "CERAMIC-100NF-50V-10%-X7R(0805)"))
    )
    (comp (ref "C60")
      (value "100nF,")
      (footprint "eagle-import:C0805")
      (fields (field (name "MPN") "CC0805KRX7R9BB104"))
      (libsource (lib "eagle-import") (part "CERAMIC-100NF-50V-10%-X7R(0805)"))
    )
    (comp (ref "C61")
      (value "4.7u")
      (footprint "eagle-import:C0805")
      (fields (field (name "MPN") "CC0805KKX5R8BB475"))
      (libsource (lib "eagle-import") (part "CERAMIC-4.7UF-25V-10%-X5R(0805)"))
    )
    (comp (ref "C62")
      (value "10u")
      (footprint "eagle-import:C1206")
      (fields (field (name "MPN") "GRM31CR60J107ME39L"))
      (libsource (lib "eagle-import") (part "CERAMIC-100UF-6.3V-20%-X5R(1206)"))
    )
    (comp (ref "D60")
      (value "1N4007,")
      (footprint "eagle-import:DO-214AC")
      (fields (field (name "MPN") "1N4007"))
      (libsource (lib "eagle-import") (part "DIODE-GEN-PURPOSE-1KV-1A(DO-214AC)"))
    )
    (comp (ref "D61")
      (value "1N4007,")
      (footprint "eagle-import:DO-214AC")
      (fields (field (name "MPN") "1N4007"))
      (libsource (lib "eagle-import") (part "DIODE-GEN-PURPOSE-1KV-1A(DO-214AC)"))
    )
    (comp (ref "D62")
      (value "1N4007.")
      (footprint "eagle-import:DO-214AC")
      (fields (field (name "MPN") "1N4007"))
      (libsource (lib "eagle-import") (part "DIODE-GEN-PURPOSE-1KV-1A(DO-214AC)"))
    )
    (comp (ref "D63")
      (value "1N5817")
      (footprint "eagle-import:DO-214AC_SLIM")
      (libsource (lib "eagle-import") (part "DIODE-GEN-PURPOSE-1KV-1A(DO-214AC)DO-214AC/1206"))
    )
    (comp (ref "D64")
      (value "1N5817.")
      (footprint "eagle-import:DO-214AC_SLIM")
      (libsource (lib "eagle-import") (part "DIODE-GEN-PURPOSE-1KV-1A(DO-214AC)DO-214AC/1206"))
    )
    (comp (ref "D65")
      (value "1N5817.")
      (footprint "eagle-import:DO-214AC_SLIM")
      (libsource (lib "eagle-import") (part "DIODE-GEN-PURPOSE-1KV-1A(DO-214AC)DO-214AC/1206"))
    )
    (comp (ref "D66")
      (value "1N5817")
      (footprint "eagle-import:DO-214AC_SLIM")
      (libsource (lib "eagle-import") (part "DIODE-GEN-PURPOSE-1KV-1A(DO-214AC)DO-214AC/1206"))
    )
    (comp (ref "D67")
      (value "1N4007.")
      (footprint "eagle-import:DO-214AC")
      (fields (field (name "MPN") "1N4007"))
      (libsource (lib "eagle-import") (part "DIODE-GEN-PURPOSE-1KV-1A(DO-214AC)"))
    )
    (comp (ref "D68")
      (value "1N4007")
      (footprint "eagle-import:DO-214AC")
      (libsource (lib "eagle-import") (part "DIODE-GEN-PURPOSE-1KV-1A(DO-214AC)"))
    )
    (comp (ref "D69")
      (value "Zen15")
      (footprint "eagle-import:DO214AA")
      (libsource (lib "eagle-import") (part "SM6T"))
    )
    (comp (ref "D71")
      (value "SS12")
      (footprint "eagle-import:DO-214AC_SLIM")
      (libsource (lib "eagle-import") (part "DIODE-GEN-PURPOSE-1KV-1A(DO-214AC)DO-214AC/1206"))
    )
    (comp (ref "D72")
      (value "SS12")
      (footprint "eagle-import:DO-214AC_SLIM")
      (libsource (lib "eagle-import") (part "DIODE-GEN-PURPOSE-1KV-1A(DO-214AC)DO-214AC/1206"))
    )
    (comp (ref "D73")
      (value "Zen11")
      (footprint "eagle-import:SOD-123_MINI-SMA")
      (libsource (lib "eagle-import") (part "CGRM400-G1"))
    )
    (comp (ref "FID19")
      (value "FIDUCIAL")
      (footprint "eagle-import:FIDUCIAL_1MM")
      (libsource (lib "eagle-import") (part "FIDUCIAL"))
    )
    (comp (ref "FID20")
      (value "FIDUCIAL")
      (footprint "eagle-import:FIDUCIAL_1MM")
      (libsource (lib "eagle-import") (part "FIDUCIAL"))
    )
    (comp (ref "FID21")
      (value "FIDUCIAL")
      (footprint "eagle-import:FIDUCIAL_1MM")
      (libsource (lib "eagle-import") (part "FIDUCIAL"))
    )
    (comp (ref "FID22")
      (value "FIDUCIAL")
      (footprint "eagle-import:FIDUCIAL_1MM")
      (libsource (lib "eagle-import") (part "FIDUCIAL"))
    )
    (comp (ref "IC37")
      (value "4028")
      (footprint "eagle-import:SO16")
      (libsource (lib "eagle-import") (part "4028D"))
    )
    (comp (ref "IC38")
      (value "317TO202H_NOHOLE")
      (footprint "eagle-import:TO220H_NOHOLE")
      (libsource (lib "eagle-import") (part "317TO202H_NOHOLE"))
    )
    (comp (ref "IC39")
      (value "ULN2004")
      (footprint "eagle-import:SO16")
      (libsource (lib "eagle-import") (part "ULN2004AD"))
    )
    (comp (ref "IC40")
      (value "LM339")
      (footprint "eagle-import:SO14")
      (libsource (lib "eagle-import") (part "LM339D"))
    )
    (comp (ref "IC41")
      (value "78L06")
      (footprint "eagle-import:SOT89_ROUND")
      (libsource (lib "eagle-import") (part "78LXXSOT89_ROUND"))
    )
    (comp (ref "IC42")
      (value "555")
      (footprint "eagle-import:SO08")
      (libsource (lib "eagle-import") (part "555DNE"))
    )
    (comp (ref "IC43")
      (value "4538")
      (footprint "eagle-import:SO16")
      (libsource (lib "eagle-import") (part "4538D"))
    )
    (comp (ref "IC44")
      (value "78L10")
      (footprint "eagle-import:SOT89_ROUND")
      (libsource (lib "eagle-import") (part "78LXXSOT89_ROUND"))
    )
    (comp (ref "IC45")
      (value "LM2904")
      (footprint "eagle-import:SO08")
      (libsource (lib "eagle-import") (part "LM358D"))
    )
    (comp (ref "JP21")
      (value "JP2EJP2_SMALLPADS")
      (footprint "eagle-import:JP2_SMALLPADS")
      (libsource (lib "eagle-import") (part "JP2EJP2_SMALLPADS"))
    )
    (comp (ref "JP22")
      (value "JP2E_ORIG")
      (footprint "eagle-import:JP2_ORIG_SMALLPADS")
      (libsource (lib "eagle-import") (part "JP2E_ORIG"))
    )
    (comp (ref "JP23")
      (value "JP2EJP2_SMALLPADS")
      (footprint "eagle-import:JP2_SMALLPADS")
      (libsource (lib "eagle-import") (part "JP2EJP2_SMALLPADS"))
    )
    (comp (ref "JP24")
      (value "JP2EJP2_SMALLPADS")
      (footprint "eagle-import:JP2_SMALLPADS")
      (libsource (lib "eagle-import") (part "JP2EJP2_SMALLPADS"))
    )
    (comp (ref "JP25")
      (value "JP2EJP2_SMALLPADS")
      (footprint "eagle-import:JP2_SMALLPADS")
      (libsource (lib "eagle-import") (part "JP2EJP2_SMALLPADS"))
    )
    (comp (ref "LED25")
      (value "LEDLD260")
      (footprint "eagle-import:LD260")
      (libsource (lib "eagle-import") (part "LEDLD260"))
    )
    (comp (ref "LED26")
      (value "LEDLD260")
      (footprint "eagle-import:LD260")
      (libsource (lib "eagle-import") (part "LEDLD260"))
    )
    (comp (ref "LED27")
      (value "LEDLD260")
      (footprint "eagle-import:LD260")
      (libsource (lib "eagle-import") (part "LEDLD260"))
    )
    (comp (ref "LED28")
      (value "LEDLD260")
      (footprint "eagle-import:LD260")
      (libsource (lib "eagle-import") (part "LEDLD260"))
    )
    (comp (ref "LED29")
      (value "LEDLD260")
      (footprint "eagle-import:LD260")
      (libsource (lib "eagle-import") (part "LEDLD260"))
    )
    (comp (ref "LED30")
      (value "LEDLD260")
      (footprint "eagle-import:LD260")
      (libsource (lib "eagle-import") (part "LEDLD260"))
    )
    (comp (ref "Q44")
      (value "BA")
      (footprint "eagle-import:SOT89")
      (libsource (lib "eagle-import") (part "PNP-TRANSISTOR_SOT89"))
    )
    (comp (ref "Q45")
      (value "BA.")
      (footprint "eagle-import:SOT89")
      (libsource (lib "eagle-import") (part "PNP-TRANSISTOR_SOT89"))
    )
    (comp (ref "Q46")
      (value "BA.")
      (footprint "eagle-import:SOT89")
      (libsource (lib "eagle-import") (part "PNP-TRANSISTOR_SOT89"))
    )
    (comp (ref "Q47")
      (value "BA")
      (footprint "eagle-import:SOT89")
      (libsource (lib "eagle-import") (part "PNP-TRANSISTOR_SOT89"))
    )
    (comp (ref "Q48")
      (value "MY")
      (footprint "eagle-import:SOT89")
      (libsource (lib "eagle-import") (part "NPN-TRANSISTOR_SOT89"))
    )
    (comp (ref "Q49")
      (value "J1")
      (footprint "eagle-import:SOT-23")
      (fields (field (name "MPN") "BSS138W-7-F"))
      (libsource (lib "eagle-import") (part "SMD-MOSFET-N-CH-50V-200MA-BSS138W-7-F(SOT-23)"))
    )
    (comp (ref "Q50")
      (value "J1")
      (footprint "eagle-import:SOT-23")
      (fields (field (name "MPN") "BSS138W-7-F"))
      (libsource (lib "eagle-import") (part "SMD-MOSFET-N-CH-50V-200MA-BSS138W-7-F(SOT-23)"))
    )
    (comp (ref "Q51")
      (value "J1")
      (footprint "eagle-import:SOT-23")
      (fields (field (name "MPN") "BSS138W-7-F"))
      (libsource (lib "eagle-import") (part "SMD-MOSFET-N-CH-50V-200MA-BSS138W-7-F(SOT-23)"))
    )
    (comp (ref "Q52")
      (value "BA")
      (footprint "eagle-import:SOT89")
      (libsource (lib "eagle-import") (part "PNP-TRANSISTOR_SOT89"))
    )
    (comp (ref "Q53")
      (value "J1")
      (footprint "eagle-import:SOT-23")
      (fields (field (name "MPN") "BSS138W-7-F"))
      (libsource (lib "eagle-import") (part "SMD-MOSFET-N-CH-50V-200MA-BSS138W-7-F(SOT-23)"))
    )
    (comp (ref "R276")
      (value "47")
      (footprint "eagle-import:V235_17_1MM")
      (libsource (lib "eagle-import") (part "R-EU_V235/17_1MM"))
    )
    (comp (ref "R277")
      (value "13")
      (footprint "eagle-import:R1206")
      (fields (field (name "MPN") "RC1206JR-0713RL"))
      (libsource (lib "eagle-import") (part "SMD-RES-13R-5%-1/4W(1206)"))
    )
    (comp (ref "R278")
      (value "47")
      (footprint "eagle-import:V235_17_1MM")
      (libsource (lib "eagle-import") (part "R-EU_V235/17_1MM"))
    )
    (comp (ref "R279")
      (value "104")
      (footprint "eagle-import:R0805")
      (fields (field (name "MPN") "RC0805FR-0710KL"))
      (libsource (lib "eagle-import") (part "SMD-RES-10K-1%-1/8W(0805)"))
    )
    (comp (ref "R280")
      (value "104")
      (footprint "eagle-import:R0805")
      (fields (field (name "MPN") "RC0805FR-0710KL"))
      (libsource (lib "eagle-import") (part "SMD-RES-10K-1%-1/8W(0805)"))
    )
    (comp (ref "R281")
      (value "104")
      (footprint "eagle-import:R0805")
      (fields (field (name "MPN") "RC0805FR-0710KL"))
      (libsource (lib "eagle-import") (part "SMD-RES-10K-1%-1/8W(0805)"))
    )
    (comp (ref "R282")
      (value "4701")
      (footprint "eagle-import:R0805")
      (fields (field (name "MPN") "RC0805JR-074K7L"))
      (libsource (lib "eagle-import") (part "SMD-RES-4.7K-5%-1/8W(0805)"))
    )
    (comp (ref "R283")
      (value "1002")
      (footprint "eagle-import:R0805")
      (fields (field (name "MPN") "RC0805FR-0710KL"))
      (libsource (lib "eagle-import") (part "SMD-RES-10K-1%-1/8W(0805)"))
    )
    (comp (ref "R284")
      (value "1002")
      (footprint "eagle-import:R0805")
      (fields (field (name "MPN") "RC0805FR-0710KL"))
      (libsource (lib "eagle-import") (part "SMD-RES-10K-1%-1/8W(0805)"))
    )
    (comp (ref "R285")
      (value "1502")
      (footprint "eagle-import:R0805")
      (fields (field (name "MPN") "RC0805FR-0710KL"))
      (libsource (lib "eagle-import") (part "SMD-RES-10K-1%-1/8W(0805)"))
    )
    (comp (ref "R286")
      (value "104")
      (footprint "eagle-import:R0805")
      (fields (field (name "MPN") "RC0805FR-0710KL"))
      (libsource (lib "eagle-import") (part "SMD-RES-10K-1%-1/8W(0805)"))
    )
    (comp (ref "R287")
      (value "104")
      (footprint "eagle-import:R0805")
      (fields (field (name "MPN") "RC0805FR-0710KL"))
      (libsource (lib "eagle-import") (part "SMD-RES-10K-1%-1/8W(0805)"))
    )
    (comp (ref "R288")
      (value "1502")
      (footprint "eagle-import:R0805")
      (fields (field (name "MPN") "RC0805FR-0710KL"))
      (libsource (lib "eagle-import") (part "SMD-RES-10K-1%-1/8W(0805)"))
    )
    (comp (ref "R289")
      (value "1002")
      (footprint "eagle-import:R0805")
      (fields (field (name "MPN") "RC0805FR-0710KL"))
      (libsource (lib "eagle-import") (part "SMD-RES-10K-1%-1/8W(0805)"))
    )
    (comp (ref "R290")
      (value "2201")
      (footprint "eagle-import:R0805")
      (fields (field (name "MPN") "RC0805JR-072K2L"))
      (libsource (lib "eagle-import") (part "SMD-RES-2.2K-5%-1/8W(0805)"))
    )
    (comp (ref "R291")
      (value "1002")
      (footprint "eagle-import:R0805")
      (fields (field (name "MPN") "RC0805FR-0710KL"))
      (libsource (lib "eagle-import") (part "SMD-RES-10K-1%-1/8W(0805)"))
    )
    (comp (ref "R292")
      (value "4701")
      (footprint "eagle-import:R0805")
      (fields (field (name "MPN") "RC0805JR-074K7L"))
      (libsource (lib "eagle-import") (part "SMD-RES-4.7K-5%-1/8W(0805)"))
    )
    (comp (ref "R293")
      (value "2702")
      (footprint "eagle-import:R0805")
      (fields (field (name "MPN") "RC0805JR-074K7L"))
      (libsource (lib "eagle-import") (part "SMD-RES-4.7K-5%-1/8W(0805)"))
    )
    (comp (ref "R294")
      (value "102")
      (footprint "eagle-import:R0805")
      (fields (field (name "MPN") "RC0805JR-071KL"))
      (libsource (lib "eagle-import") (part "SMD-RES-1K-5%-1/8W(0805)"))
    )
    (comp (ref "R296")
      (value "102")
      (footprint "eagle-import:R0805")
      (fields (field (name "MPN") "RC0805JR-07220RL"))
      (libsource (lib "eagle-import") (part "SMD-RES-220R-5%-1/8W(0805)"))
    )
    (comp (ref "R299")
      (value "102")
      (footprint "eagle-import:R0805")
      (fields (field (name "MPN") "RC0805JR-071KL"))
      (libsource (lib "eagle-import") (part "SMD-RES-1K-5%-1/8W(0805)"))
    )
    (comp (ref "R300")
      (value "13")
      (footprint "eagle-import:R1206")
      (fields (field (name "MPN") "RC1206JR-0713RL"))
      (libsource (lib "eagle-import") (part "SMD-RES-13R-5%-1/4W(1206)"))
    )
    (comp (ref "R301")
      (value "13")
      (footprint "eagle-import:R1206")
      (fields (field (name "MPN") "RC1206JR-0713RL"))
      (libsource (lib "eagle-import") (part "SMD-RES-13R-5%-1/4W(1206)"))
    )
    (comp (ref "R302")
      (value "2702")
      (footprint "eagle-import:R0805")
      (fields (field (name "MPN") "RC0805JR-074K7L"))
      (libsource (lib "eagle-import") (part "SMD-RES-4.7K-5%-1/8W(0805)"))
    )
    (comp (ref "R303")
      (value "4701")
      (footprint "eagle-import:R0805")
      (fields (field (name "MPN") "RC0805JR-074K7L"))
      (libsource (lib "eagle-import") (part "SMD-RES-4.7K-5%-1/8W(0805)"))
    )
    (comp (ref "R304")
      (value "100")
      (footprint "eagle-import:R0805")
      (fields (field (name "MPN") "RC0805JR-072K2L"))
      (libsource (lib "eagle-import") (part "SMD-RES-2.2K-5%-1/8W(0805)"))
    )
    (comp (ref "R305")
      (value "104")
      (footprint "eagle-import:R0805")
      (fields (field (name "MPN") "RC0805FR-0710KL"))
      (libsource (lib "eagle-import") (part "SMD-RES-10K-1%-1/8W(0805)"))
    )
    (comp (ref "R306")
      (value "104")
      (footprint "eagle-import:R0805")
      (fields (field (name "MPN") "RC0805FR-0710KL"))
      (libsource (lib "eagle-import") (part "SMD-RES-10K-1%-1/8W(0805)"))
    )
    (comp (ref "R308")
      (value "2702")
      (footprint "eagle-import:R0805")
      (fields (field (name "MPN") "RC0805FR-0710KL"))
      (libsource (lib "eagle-import") (part "SMD-RES-10K-1%-1/8W(0805)"))
    )
    (comp (ref "R309")
      (value "47")
      (footprint "eagle-import:V235_17_1MM")
      (libsource (lib "eagle-import") (part "R-EU_V235/17_1MM"))
    )
    (comp (ref "R310")
      (value "47")
      (footprint "eagle-import:V235_17_1MM")
      (libsource (lib "eagle-import") (part "R-EU_V235/17_1MM"))
    )
    (comp (ref "R311")
      (value "2702")
      (footprint "eagle-import:R0805")
      (fields (field (name "MPN") "RC0805JR-074K7L"))
      (libsource (lib "eagle-import") (part "SMD-RES-4.7K-5%-1/8W(0805)"))
    )
    (comp (ref "R312")
      (value "2201")
      (footprint "eagle-import:R0805")
      (fields (field (name "MPN") "RC0805JR-072K2L"))
      (libsource (lib "eagle-import") (part "SMD-RES-2.2K-5%-1/8W(0805)"))
    )
    (comp (ref "R313")
      (value "1002")
      (footprint "eagle-import:R0805")
      (fields (field (name "MPN") "RC0805JR-074K7L"))
      (libsource (lib "eagle-import") (part "SMD-RES-4.7K-5%-1/8W(0805)"))
    )
    (comp (ref "R314")
      (value "1002")
      (footprint "eagle-import:R0805")
      (fields (field (name "MPN") "RC0805FR-0710KL"))
      (libsource (lib "eagle-import") (part "SMD-RES-10K-1%-1/8W(0805)"))
    )
    (comp (ref "R315")
      (value "102")
      (footprint "eagle-import:R0805")
      (fields (field (name "MPN") "RC0805JR-071KL"))
      (libsource (lib "eagle-import") (part "SMD-RES-1K-5%-1/8W(0805)"))
    )
    (comp (ref "R316")
      (value "2702")
      (footprint "eagle-import:R0805")
      (fields (field (name "MPN") "RC0805JR-074K7L"))
      (libsource (lib "eagle-import") (part "SMD-RES-4.7K-5%-1/8W(0805)"))
    )
    (comp (ref "R317")
      (value "1002")
      (footprint "eagle-import:R0805")
      (fields (field (name "MPN") "RC0805JR-071KL"))
      (libsource (lib "eagle-import") (part "SMD-RES-1K-5%-1/8W(0805)"))
    )
    (comp (ref "R318")
      (value "1002")
      (footprint "eagle-import:R0805")
      (fields (field (name "MPN") "RC0805JR-071KL"))
      (libsource (lib "eagle-import") (part "SMD-RES-1K-5%-1/8W(0805)"))
    )
    (comp (ref "R319")
      (value "R_user")
      (footprint "eagle-import:R0805")
      (libsource (lib "eagle-import") (part "R-EU_R0805"))
    )
    (comp (ref "R320")
      (value "104")
      (footprint "eagle-import:R0805")
      (fields (field (name "MPN") "RC0805FR-0710KL"))
      (libsource (lib "eagle-import") (part "SMD-RES-10K-1%-1/8W(0805)"))
    )
    (comp (ref "R321")
      (value "104")
      (footprint "eagle-import:R0805")
      (fields (field (name "MPN") "RC0805FR-0710KL"))
      (libsource (lib "eagle-import") (part "SMD-RES-10K-1%-1/8W(0805)"))
    )
    (comp (ref "R322")
      (value "104")
      (footprint "eagle-import:R0805")
      (fields (field (name "MPN") "RC0805FR-0710KL"))
      (libsource (lib "eagle-import") (part "SMD-RES-10K-1%-1/8W(0805)"))
    )
    (comp (ref "R323")
      (value "13")
      (footprint "eagle-import:R1206")
      (fields (field (name "MPN") "RC1206JR-0713RL"))
      (libsource (lib "eagle-import") (part "SMD-RES-13R-5%-1/4W(1206)"))
    )
    (comp (ref "R324")
      (value "2201")
      (footprint "eagle-import:R0805")
      (fields (field (name "MPN") "RC0805JR-071KL"))
      (libsource (lib "eagle-import") (part "SMD-RES-1K-5%-1/8W(0805)"))
    )
    (comp (ref "R325")
      (value "100")
      (footprint "eagle-import:R0805")
      (fields (field (name "MPN") "RC0805JR-07220RL"))
      (libsource (lib "eagle-import") (part "SMD-RES-220R-5%-1/8W(0805)"))
    )
    (comp (ref "R326")
      (value "13")
      (footprint "eagle-import:R1206")
      (fields (field (name "MPN") "RC1206JR-0713RL"))
      (libsource (lib "eagle-import") (part "SMD-RES-13R-5%-1/4W(1206)"))
    )
    (comp (ref "R327")
      (value "4701")
      (footprint "eagle-import:R0805")
      (fields (field (name "MPN") "RC0805JR-074K7L"))
      (libsource (lib "eagle-import") (part "SMD-RES-4.7K-5%-1/8W(0805)"))
    )
    (comp (ref "R328")
      (value "104")
      (footprint "eagle-import:R0805")
      (fields (field (name "MPN") "RC0805JR-074K7L"))
      (libsource (lib "eagle-import") (part "SMD-RES-4.7K-5%-1/8W(0805)"))
    )
    (comp (ref "R329")
      (value "100")
      (footprint "eagle-import:R0805")
      (fields (field (name "MPN") "RC0805JR-072K2L"))
      (libsource (lib "eagle-import") (part "SMD-RES-2.2K-5%-1/8W(0805)"))
    )
    (comp (ref "R330")
      (value "100")
      (footprint "eagle-import:R0805")
      (fields (field (name "MPN") "RC0805JR-072K2L"))
      (libsource (lib "eagle-import") (part "SMD-RES-2.2K-5%-1/8W(0805)"))
    )
    (comp (ref "SJMP5")
      (value "SJ")
      (footprint "eagle-import:SJ")
      (libsource (lib "eagle-import") (part "SJ"))
    )
    (comp (ref "START5")
      (value "TPSB2.0")
      (footprint "eagle-import:B2.0")
      (libsource (lib "eagle-import") (part "TPSB2.0"))
    )
    (comp (ref "TP116")
      (value "TPSB2.0")
      (footprint "eagle-import:B2.0")
      (libsource (lib "eagle-import") (part "TPSB2.0"))
    )
    (comp (ref "TP117")
      (value "TPSB2.0")
      (footprint "eagle-import:B2.0")
      (libsource (lib "eagle-import") (part "TPSB2.0"))
    )
    (comp (ref "TP118")
      (value "TPSB2.0")
      (footprint "eagle-import:B2.0")
      (libsource (lib "eagle-import") (part "TPSB2.0"))
    )
    (comp (ref "TP119")
      (value "TPSB2.0")
      (footprint "eagle-import:B2.0")
      (libsource (lib "eagle-import") (part "TPSB2.0"))
    )
    (comp (ref "TP120")
      (value "TPSB2.0")
      (footprint "eagle-import:B2.0")
      (libsource (lib "eagle-import") (part "TPSB2.0"))
    )
    (comp (ref "TP121")
      (value "TPSB2.0")
      (footprint "eagle-import:B2.0")
      (libsource (lib "eagle-import") (part "TPSB2.0"))
    )
    (comp (ref "TP122")
      (value "TPSB2.0")
      (footprint "eagle-import:B2.0")
      (libsource (lib "eagle-import") (part "TPSB2.0"))
    )
    (comp (ref "TP123")
      (value "TPSB2.0")
      (footprint "eagle-import:B2.0")
      (libsource (lib "eagle-import") (part "TPSB2.0"))
    )
    (comp (ref "TP124")
      (value "TPSB2.0")
      (footprint "eagle-import:B2.0")
      (libsource (lib "eagle-import") (part "TPSB2.0"))
    )
    (comp (ref "TP125")
      (value "TPSB2.0")
      (footprint "eagle-import:B2.0")
      (libsource (lib "eagle-import") (part "TPSB2.0"))
    )
    (comp (ref "TP126")
      (value "TPSB2.0")
      (footprint "eagle-import:B2.0")
      (libsource (lib "eagle-import") (part "TPSB2.0"))
    )
    (comp (ref "TP127")
      (value "TPSB2.0")
      (footprint "eagle-import:B2.0")
      (libsource (lib "eagle-import") (part "TPSB2.0"))
    )
    (comp (ref "TP128")
      (value "TPSB2.0")
      (footprint "eagle-import:B2.0")
      (libsource (lib "eagle-import") (part "TPSB2.0"))
    )
    (comp (ref "TP129")
      (value "TPSB2.0")
      (footprint "eagle-import:B2.0")
      (libsource (lib "eagle-import") (part "TPSB2.0"))
    )
    (comp (ref "TP130")
      (value "TPSB2.0")
      (footprint "eagle-import:B2.0")
      (libsource (lib "eagle-import") (part "TPSB2.0"))
    )
    (comp (ref "TP131")
      (value "TPSB2.0")
      (footprint "eagle-import:B2.0")
      (libsource (lib "eagle-import") (part "TPSB2.0"))
    )
    (comp (ref "TP132")
      (value "TPSB2.0")
      (footprint "eagle-import:B2.0")
      (libsource (lib "eagle-import") (part "TPSB2.0"))
    )
    (comp (ref "TP133")
      (value "TPSB2.0")
      (footprint "eagle-import:B2.0")
      (libsource (lib "eagle-import") (part "TPSB2.0"))
    )
    (comp (ref "TP134")
      (value "TPSB1,27")
      (footprint "eagle-import:B1,27")
      (libsource (lib "eagle-import") (part "TPSB1,27"))
    )
    (comp (ref "TP135")
      (value "TPSB2.0")
      (footprint "eagle-import:B2.0")
      (libsource (lib "eagle-import") (part "TPSB2.0"))
    )
    (comp (ref "TP136")
      (value "TPSB2.0")
      (footprint "eagle-import:B2.0")
      (libsource (lib "eagle-import") (part "TPSB2.0"))
    )
    (comp (ref "TP137")
      (value "TPSB2.0")
      (footprint "eagle-import:B2.0")
      (libsource (lib "eagle-import") (part "TPSB2.0"))
    )
    (comp (ref "TP138")
      (value "TPSB2.0")
      (footprint "eagle-import:B2.0")
      (libsource (lib "eagle-import") (part "TPSB2.0"))
    )
    (comp (ref "X13")
      (value "CON_BMWV2")
      (footprint "eagle-import:24-PIN_V2")
      (libsource (lib "eagle-import") (part "CON_BMWV2"))
    )
    (comp (ref "X14")
      (value "22-23-2051")
      (footprint "eagle-import:22-23-2051")
      (fields (field (name "MF") "MOLEX"))
      (libsource (lib "eagle-import") (part "22-23-2051"))
    )
    (comp (ref "X15")
      (value "22-23-2021")
      (footprint "eagle-import:22-23-2021")
      (fields (field (name "MF") "MOLEX"))
      (libsource (lib "eagle-import") (part "22-23-2021"))
    )
    (comp (ref "6V7")
      (value "TPSB2.0")
      (footprint "eagle-import:B2.0")
      (libsource (lib "eagle-import") (part "TPSB2.0"))
    )
    (comp (ref "10V7")
      (value "TPSB2.0")
      (footprint "eagle-import:B2.0")
      (libsource (lib "eagle-import") (part "TPSB2.0"))
    )
    (comp (ref "15")
      (value "2081-1132")
      (footprint "eagle-import:12-PIN")
      (libsource (lib "eagle-import") (part "2081-1132"))
    )
    (comp (ref "16")
      (value "2081-1132")
      (footprint "eagle-import:12-PIN")
      (libsource (lib "eagle-import") (part "2081-1132"))
    )
    (comp (ref "C75")
      (value "100u")
      (footprint "eagle-import:C1206")
      (fields (field (name "MPN") "GRM31CR60J107ME39L"))
      (libsource (lib "eagle-import") (part "CERAMIC-100UF-6.3V-20%-X5R(1206)"))
    )
    (comp (ref "C76")
      (value "100u")
      (footprint "eagle-import:C1206")
      (fields (field (name "MPN") "GRM31CR60J107ME39L"))
      (libsource (lib "eagle-import") (part "CERAMIC-100UF-6.3V-20%-X5R(1206)"))
    )
    (comp (ref "C77")
      (value "100nF,")
      (footprint "eagle-import:C0805")
      (fields (field (name "MPN") "CC0805KRX7R9BB104"))
      (libsource (lib "eagle-import") (part "CERAMIC-100NF-50V-10%-X7R(0805)"))
    )
    (comp (ref "C78")
      (value "4.7u")
      (footprint "eagle-import:C0805")
      (fields (field (name "MPN") "CC0805KKX5R8BB475"))
      (libsource (lib "eagle-import") (part "CERAMIC-4.7UF-25V-10%-X5R(0805)"))
    )
    (comp (ref "C79")
      (value "100nF.")
      (footprint "eagle-import:C0805")
      (fields (field (name "MPN") "CC0805KRX7R9BB104"))
      (libsource (lib "eagle-import") (part "CERAMIC-100NF-50V-10%-X7R(0805)"))
    )
    (comp (ref "C80")
      (value "100nF.")
      (footprint "eagle-import:C0805")
      (fields (field (name "MPN") "CC0805KRX7R9BB104"))
      (libsource (lib "eagle-import") (part "CERAMIC-100NF-50V-10%-X7R(0805)"))
    )
    (comp (ref "C81")
      (value "2.2nF")
      (footprint "eagle-import:C0805")
      (fields (field (name "MPN") "CC0805KRX7R9BB104"))
      (libsource (lib "eagle-import") (part "CERAMIC-100NF-50V-10%-X7R(0805)"))
    )
    (comp (ref "C82")
      (value "100nF")
      (footprint "eagle-import:C0805")
      (fields (field (name "MPN") "CC0805KRX7R9BB104"))
      (libsource (lib "eagle-import") (part "CERAMIC-100NF-50V-10%-X7R(0805)"))
    )
    (comp (ref "C83")
      (value "100nF")
      (footprint "eagle-import:C0805")
      (fields (field (name "MPN") "CC0805KRX7R9BB104"))
      (libsource (lib "eagle-import") (part "CERAMIC-100NF-50V-10%-X7R(0805)"))
    )
    (comp (ref "C84")
      (value "100nF,")
      (footprint "eagle-import:C0805")
      (fields (field (name "MPN") "CC0805KRX7R9BB104"))
      (libsource (lib "eagle-import") (part "CERAMIC-100NF-50V-10%-X7R(0805)"))
    )
    (comp (ref "C85")
      (value "4.7u")
      (footprint "eagle-import:C0805")
      (fields (field (name "MPN") "CC0805KKX5R8BB475"))
      (libsource (lib "eagle-import") (part "CERAMIC-4.7UF-25V-10%-X5R(0805)"))
    )
    (comp (ref "C86")
      (value "10u")
      (footprint "eagle-import:C1206")
      (fields (field (name "MPN") "GRM31CR60J107ME39L"))
      (libsource (lib "eagle-import") (part "CERAMIC-100UF-6.3V-20%-X5R(1206)"))
    )
    (comp (ref "D82")
      (value "1N4007,")
      (footprint "eagle-import:DO-214AC")
      (fields (field (name "MPN") "1N4007"))
      (libsource (lib "eagle-import") (part "DIODE-GEN-PURPOSE-1KV-1A(DO-214AC)"))
    )
    (comp (ref "D83")
      (value "1N4007,")
      (footprint "eagle-import:DO-214AC")
      (fields (field (name "MPN") "1N4007"))
      (libsource (lib "eagle-import") (part "DIODE-GEN-PURPOSE-1KV-1A(DO-214AC)"))
    )
    (comp (ref "D84")
      (value "1N4007.")
      (footprint "eagle-import:DO-214AC")
      (fields (field (name "MPN") "1N4007"))
      (libsource (lib "eagle-import") (part "DIODE-GEN-PURPOSE-1KV-1A(DO-214AC)"))
    )
    (comp (ref "D85")
      (value "1N5817")
      (footprint "eagle-import:DO-214AC_SLIM")
      (libsource (lib "eagle-import") (part "DIODE-GEN-PURPOSE-1KV-1A(DO-214AC)DO-214AC/1206"))
    )
    (comp (ref "D86")
      (value "1N5817.")
      (footprint "eagle-import:DO-214AC_SLIM")
      (libsource (lib "eagle-import") (part "DIODE-GEN-PURPOSE-1KV-1A(DO-214AC)DO-214AC/1206"))
    )
    (comp (ref "D87")
      (value "1N5817.")
      (footprint "eagle-import:DO-214AC_SLIM")
      (libsource (lib "eagle-import") (part "DIODE-GEN-PURPOSE-1KV-1A(DO-214AC)DO-214AC/1206"))
    )
    (comp (ref "D88")
      (value "1N5817")
      (footprint "eagle-import:DO-214AC_SLIM")
      (libsource (lib "eagle-import") (part "DIODE-GEN-PURPOSE-1KV-1A(DO-214AC)DO-214AC/1206"))
    )
    (comp (ref "D89")
      (value "1N4007.")
      (footprint "eagle-import:DO-214AC")
      (fields (field (name "MPN") "1N4007"))
      (libsource (lib "eagle-import") (part "DIODE-GEN-PURPOSE-1KV-1A(DO-214AC)"))
    )
    (comp (ref "D90")
      (value "1N4007")
      (footprint "eagle-import:DO-214AC")
      (libsource (lib "eagle-import") (part "DIODE-GEN-PURPOSE-1KV-1A(DO-214AC)"))
    )
    (comp (ref "D91")
      (value "Zen15")
      (footprint "eagle-import:DO214AA")
      (libsource (lib "eagle-import") (part "SM6T"))
    )
    (comp (ref "D92")
      (value "SS12")
      (footprint "eagle-import:DO-214AC_SLIM")
      (libsource (lib "eagle-import") (part "DIODE-GEN-PURPOSE-1KV-1A(DO-214AC)DO-214AC/1206"))
    )
    (comp (ref "D93")
      (value "SS12")
      (footprint "eagle-import:DO-214AC_SLIM")
      (libsource (lib "eagle-import") (part "DIODE-GEN-PURPOSE-1KV-1A(DO-214AC)DO-214AC/1206"))
    )
    (comp (ref "D94")
      (value "Zen11")
      (footprint "eagle-import:SOD-123_MINI-SMA")
      (libsource (lib "eagle-import") (part "CGRM400-G1"))
    )
    (comp (ref "FID29")
      (value "FIDUCIAL")
      (footprint "eagle-import:FIDUCIAL_1MM")
      (libsource (lib "eagle-import") (part "FIDUCIAL"))
    )
    (comp (ref "FID30")
      (value "FIDUCIAL")
      (footprint "eagle-import:FIDUCIAL_1MM")
      (libsource (lib "eagle-import") (part "FIDUCIAL"))
    )
    (comp (ref "FID31")
      (value "FIDUCIAL")
      (footprint "eagle-import:FIDUCIAL_1MM")
      (libsource (lib "eagle-import") (part "FIDUCIAL"))
    )
    (comp (ref "FID32")
      (value "FIDUCIAL")
      (footprint "eagle-import:FIDUCIAL_1MM")
      (libsource (lib "eagle-import") (part "FIDUCIAL"))
    )
    (comp (ref "IC55")
      (value "4028")
      (footprint "eagle-import:SO16")
      (libsource (lib "eagle-import") (part "4028D"))
    )
    (comp (ref "IC56")
      (value "317TO202H_NOHOLE")
      (footprint "eagle-import:TO220H_NOHOLE")
      (libsource (lib "eagle-import") (part "317TO202H_NOHOLE"))
    )
    (comp (ref "IC57")
      (value "ULN2004")
      (footprint "eagle-import:SO16")
      (libsource (lib "eagle-import") (part "ULN2004AD"))
    )
    (comp (ref "IC58")
      (value "LM339")
      (footprint "eagle-import:SO14")
      (libsource (lib "eagle-import") (part "LM339D"))
    )
    (comp (ref "IC59")
      (value "78L06")
      (footprint "eagle-import:SOT89_ROUND")
      (libsource (lib "eagle-import") (part "78LXXSOT89_ROUND"))
    )
    (comp (ref "IC60")
      (value "555")
      (footprint "eagle-import:SO08")
      (libsource (lib "eagle-import") (part "555DNE"))
    )
    (comp (ref "IC61")
      (value "4538")
      (footprint "eagle-import:SO16")
      (libsource (lib "eagle-import") (part "4538D"))
    )
    (comp (ref "IC62")
      (value "78L10")
      (footprint "eagle-import:SOT89_ROUND")
      (libsource (lib "eagle-import") (part "78LXXSOT89_ROUND"))
    )
    (comp (ref "IC63")
      (value "LM2904")
      (footprint "eagle-import:SO08")
      (libsource (lib "eagle-import") (part "LM358D"))
    )
    (comp (ref "JP31")
      (value "JP2EJP2_SMALLPADS")
      (footprint "eagle-import:JP2_SMALLPADS")
      (libsource (lib "eagle-import") (part "JP2EJP2_SMALLPADS"))
    )
    (comp (ref "JP32")
      (value "JP2E_ORIG")
      (footprint "eagle-import:JP2_ORIG_SMALLPADS")
      (libsource (lib "eagle-import") (part "JP2E_ORIG"))
    )
    (comp (ref "JP33")
      (value "JP2EJP2_SMALLPADS")
      (footprint "eagle-import:JP2_SMALLPADS")
      (libsource (lib "eagle-import") (part "JP2EJP2_SMALLPADS"))
    )
    (comp (ref "JP34")
      (value "JP2EJP2_SMALLPADS")
      (footprint "eagle-import:JP2_SMALLPADS")
      (libsource (lib "eagle-import") (part "JP2EJP2_SMALLPADS"))
    )
    (comp (ref "JP35")
      (value "JP2EJP2_SMALLPADS")
      (footprint "eagle-import:JP2_SMALLPADS")
      (libsource (lib "eagle-import") (part "JP2EJP2_SMALLPADS"))
    )
    (comp (ref "LED37")
      (value "LEDLD260")
      (footprint "eagle-import:LD260")
      (libsource (lib "eagle-import") (part "LEDLD260"))
    )
    (comp (ref "LED38")
      (value "LEDLD260")
      (footprint "eagle-import:LD260")
      (libsource (lib "eagle-import") (part "LEDLD260"))
    )
    (comp (ref "LED39")
      (value "LEDLD260")
      (footprint "eagle-import:LD260")
      (libsource (lib "eagle-import") (part "LEDLD260"))
    )
    (comp (ref "LED40")
      (value "LEDLD260")
      (footprint "eagle-import:LD260")
      (libsource (lib "eagle-import") (part "LEDLD260"))
    )
    (comp (ref "LED41")
      (value "LEDLD260")
      (footprint "eagle-import:LD260")
      (libsource (lib "eagle-import") (part "LEDLD260"))
    )
    (comp (ref "LED42")
      (value "LEDLD260")
      (footprint "eagle-import:LD260")
      (libsource (lib "eagle-import") (part "LEDLD260"))
    )
    (comp (ref "Q64")
      (value "BA")
      (footprint "eagle-import:SOT89")
      (libsource (lib "eagle-import") (part "PNP-TRANSISTOR_SOT89"))
    )
    (comp (ref "Q65")
      (value "BA.")
      (footprint "eagle-import:SOT89")
      (libsource (lib "eagle-import") (part "PNP-TRANSISTOR_SOT89"))
    )
    (comp (ref "Q66")
      (value "BA.")
      (footprint "eagle-import:SOT89")
      (libsource (lib "eagle-import") (part "PNP-TRANSISTOR_SOT89"))
    )
    (comp (ref "Q67")
      (value "BA")
      (footprint "eagle-import:SOT89")
      (libsource (lib "eagle-import") (part "PNP-TRANSISTOR_SOT89"))
    )
    (comp (ref "Q68")
      (value "MY")
      (footprint "eagle-import:SOT89")
      (libsource (lib "eagle-import") (part "NPN-TRANSISTOR_SOT89"))
    )
    (comp (ref "Q69")
      (value "J1")
      (footprint "eagle-import:SOT-23")
      (fields (field (name "MPN") "BSS138W-7-F"))
      (libsource (lib "eagle-import") (part "SMD-MOSFET-N-CH-50V-200MA-BSS138W-7-F(SOT-23)"))
    )
    (comp (ref "Q70")
      (value "J1")
      (footprint "eagle-import:SOT-23")
      (fields (field (name "MPN") "BSS138W-7-F"))
      (libsource (lib "eagle-import") (part "SMD-MOSFET-N-CH-50V-200MA-BSS138W-7-F(SOT-23)"))
    )
    (comp (ref "Q71")
      (value "J1")
      (footprint "eagle-import:SOT-23")
      (fields (field (name "MPN") "BSS138W-7-F"))
      (libsource (lib "eagle-import") (part "SMD-MOSFET-N-CH-50V-200MA-BSS138W-7-F(SOT-23)"))
    )
    (comp (ref "Q72")
      (value "BA")
      (footprint "eagle-import:SOT89")
      (libsource (lib "eagle-import") (part "PNP-TRANSISTOR_SOT89"))
    )
    (comp (ref "Q73")
      (value "J1")
      (footprint "eagle-import:SOT-23")
      (fields (field (name "MPN") "BSS138W-7-F"))
      (libsource (lib "eagle-import") (part "SMD-MOSFET-N-CH-50V-200MA-BSS138W-7-F(SOT-23)"))
    )
    (comp (ref "R358")
      (value "47")
      (footprint "eagle-import:V235_17_1MM")
      (libsource (lib "eagle-import") (part "R-EU_V235/17_1MM"))
    )
    (comp (ref "R359")
      (value "13")
      (footprint "eagle-import:R1206")
      (fields (field (name "MPN") "RC1206JR-0713RL"))
      (libsource (lib "eagle-import") (part "SMD-RES-13R-5%-1/4W(1206)"))
    )
    (comp (ref "R360")
      (value "47")
      (footprint "eagle-import:V235_17_1MM")
      (libsource (lib "eagle-import") (part "R-EU_V235/17_1MM"))
    )
    (comp (ref "R361")
      (value "104")
      (footprint "eagle-import:R0805")
      (fields (field (name "MPN") "RC0805FR-0710KL"))
      (libsource (lib "eagle-import") (part "SMD-RES-10K-1%-1/8W(0805)"))
    )
    (comp (ref "R362")
      (value "104")
      (footprint "eagle-import:R0805")
      (fields (field (name "MPN") "RC0805FR-0710KL"))
      (libsource (lib "eagle-import") (part "SMD-RES-10K-1%-1/8W(0805)"))
    )
    (comp (ref "R363")
      (value "104")
      (footprint "eagle-import:R0805")
      (fields (field (name "MPN") "RC0805FR-0710KL"))
      (libsource (lib "eagle-import") (part "SMD-RES-10K-1%-1/8W(0805)"))
    )
    (comp (ref "R364")
      (value "4701")
      (footprint "eagle-import:R0805")
      (fields (field (name "MPN") "RC0805JR-074K7L"))
      (libsource (lib "eagle-import") (part "SMD-RES-4.7K-5%-1/8W(0805)"))
    )
    (comp (ref "R365")
      (value "1002")
      (footprint "eagle-import:R0805")
      (fields (field (name "MPN") "RC0805FR-0710KL"))
      (libsource (lib "eagle-import") (part "SMD-RES-10K-1%-1/8W(0805)"))
    )
    (comp (ref "R366")
      (value "1002")
      (footprint "eagle-import:R0805")
      (fields (field (name "MPN") "RC0805FR-0710KL"))
      (libsource (lib "eagle-import") (part "SMD-RES-10K-1%-1/8W(0805)"))
    )
    (comp (ref "R367")
      (value "1502")
      (footprint "eagle-import:R0805")
      (fields (field (name "MPN") "RC0805FR-0710KL"))
      (libsource (lib "eagle-import") (part "SMD-RES-10K-1%-1/8W(0805)"))
    )
    (comp (ref "R368")
      (value "104")
      (footprint "eagle-import:R0805")
      (fields (field (name "MPN") "RC0805FR-0710KL"))
      (libsource (lib "eagle-import") (part "SMD-RES-10K-1%-1/8W(0805)"))
    )
    (comp (ref "R369")
      (value "104")
      (footprint "eagle-import:R0805")
      (fields (field (name "MPN") "RC0805FR-0710KL"))
      (libsource (lib "eagle-import") (part "SMD-RES-10K-1%-1/8W(0805)"))
    )
    (comp (ref "R370")
      (value "1502")
      (footprint "eagle-import:R0805")
      (fields (field (name "MPN") "RC0805FR-0710KL"))
      (libsource (lib "eagle-import") (part "SMD-RES-10K-1%-1/8W(0805)"))
    )
    (comp (ref "R371")
      (value "1002")
      (footprint "eagle-import:R0805")
      (fields (field (name "MPN") "RC0805FR-0710KL"))
      (libsource (lib "eagle-import") (part "SMD-RES-10K-1%-1/8W(0805)"))
    )
    (comp (ref "R372")
      (value "2201")
      (footprint "eagle-import:R0805")
      (fields (field (name "MPN") "RC0805JR-072K2L"))
      (libsource (lib "eagle-import") (part "SMD-RES-2.2K-5%-1/8W(0805)"))
    )
    (comp (ref "R373")
      (value "1002")
      (footprint "eagle-import:R0805")
      (fields (field (name "MPN") "RC0805FR-0710KL"))
      (libsource (lib "eagle-import") (part "SMD-RES-10K-1%-1/8W(0805)"))
    )
    (comp (ref "R374")
      (value "4701")
      (footprint "eagle-import:R0805")
      (fields (field (name "MPN") "RC0805JR-074K7L"))
      (libsource (lib "eagle-import") (part "SMD-RES-4.7K-5%-1/8W(0805)"))
    )
    (comp (ref "R375")
      (value "2702")
      (footprint "eagle-import:R0805")
      (fields (field (name "MPN") "RC0805JR-074K7L"))
      (libsource (lib "eagle-import") (part "SMD-RES-4.7K-5%-1/8W(0805)"))
    )
    (comp (ref "R376")
      (value "102")
      (footprint "eagle-import:R0805")
      (fields (field (name "MPN") "RC0805JR-071KL"))
      (libsource (lib "eagle-import") (part "SMD-RES-1K-5%-1/8W(0805)"))
    )
    (comp (ref "R377")
      (value "102")
      (footprint "eagle-import:R0805")
      (fields (field (name "MPN") "RC0805JR-07220RL"))
      (libsource (lib "eagle-import") (part "SMD-RES-220R-5%-1/8W(0805)"))
    )
    (comp (ref "R378")
      (value "102")
      (footprint "eagle-import:R0805")
      (fields (field (name "MPN") "RC0805JR-071KL"))
      (libsource (lib "eagle-import") (part "SMD-RES-1K-5%-1/8W(0805)"))
    )
    (comp (ref "R379")
      (value "13")
      (footprint "eagle-import:R1206")
      (fields (field (name "MPN") "RC1206JR-0713RL"))
      (libsource (lib "eagle-import") (part "SMD-RES-13R-5%-1/4W(1206)"))
    )
    (comp (ref "R380")
      (value "13")
      (footprint "eagle-import:R1206")
      (fields (field (name "MPN") "RC1206JR-0713RL"))
      (libsource (lib "eagle-import") (part "SMD-RES-13R-5%-1/4W(1206)"))
    )
    (comp (ref "R381")
      (value "2702")
      (footprint "eagle-import:R0805")
      (fields (field (name "MPN") "RC0805JR-074K7L"))
      (libsource (lib "eagle-import") (part "SMD-RES-4.7K-5%-1/8W(0805)"))
    )
    (comp (ref "R382")
      (value "4701")
      (footprint "eagle-import:R0805")
      (fields (field (name "MPN") "RC0805JR-074K7L"))
      (libsource (lib "eagle-import") (part "SMD-RES-4.7K-5%-1/8W(0805)"))
    )
    (comp (ref "R383")
      (value "100")
      (footprint "eagle-import:R0805")
      (fields (field (name "MPN") "RC0805JR-072K2L"))
      (libsource (lib "eagle-import") (part "SMD-RES-2.2K-5%-1/8W(0805)"))
    )
    (comp (ref "R384")
      (value "104")
      (footprint "eagle-import:R0805")
      (fields (field (name "MPN") "RC0805FR-0710KL"))
      (libsource (lib "eagle-import") (part "SMD-RES-10K-1%-1/8W(0805)"))
    )
    (comp (ref "R385")
      (value "104")
      (footprint "eagle-import:R0805")
      (fields (field (name "MPN") "RC0805FR-0710KL"))
      (libsource (lib "eagle-import") (part "SMD-RES-10K-1%-1/8W(0805)"))
    )
    (comp (ref "R386")
      (value "2702")
      (footprint "eagle-import:R0805")
      (fields (field (name "MPN") "RC0805FR-0710KL"))
      (libsource (lib "eagle-import") (part "SMD-RES-10K-1%-1/8W(0805)"))
    )
    (comp (ref "R387")
      (value "47")
      (footprint "eagle-import:V235_17_1MM")
      (libsource (lib "eagle-import") (part "R-EU_V235/17_1MM"))
    )
    (comp (ref "R388")
      (value "47")
      (footprint "eagle-import:V235_17_1MM")
      (libsource (lib "eagle-import") (part "R-EU_V235/17_1MM"))
    )
    (comp (ref "R389")
      (value "2702")
      (footprint "eagle-import:R0805")
      (fields (field (name "MPN") "RC0805JR-074K7L"))
      (libsource (lib "eagle-import") (part "SMD-RES-4.7K-5%-1/8W(0805)"))
    )
    (comp (ref "R390")
      (value "2201")
      (footprint "eagle-import:R0805")
      (fields (field (name "MPN") "RC0805JR-072K2L"))
      (libsource (lib "eagle-import") (part "SMD-RES-2.2K-5%-1/8W(0805)"))
    )
    (comp (ref "R391")
      (value "1002")
      (footprint "eagle-import:R0805")
      (fields (field (name "MPN") "RC0805JR-074K7L"))
      (libsource (lib "eagle-import") (part "SMD-RES-4.7K-5%-1/8W(0805)"))
    )
    (comp (ref "R392")
      (value "1002")
      (footprint "eagle-import:R0805")
      (fields (field (name "MPN") "RC0805FR-0710KL"))
      (libsource (lib "eagle-import") (part "SMD-RES-10K-1%-1/8W(0805)"))
    )
    (comp (ref "R393")
      (value "102")
      (footprint "eagle-import:R0805")
      (fields (field (name "MPN") "RC0805JR-071KL"))
      (libsource (lib "eagle-import") (part "SMD-RES-1K-5%-1/8W(0805)"))
    )
    (comp (ref "R394")
      (value "2702")
      (footprint "eagle-import:R0805")
      (fields (field (name "MPN") "RC0805JR-074K7L"))
      (libsource (lib "eagle-import") (part "SMD-RES-4.7K-5%-1/8W(0805)"))
    )
    (comp (ref "R395")
      (value "1002")
      (footprint "eagle-import:R0805")
      (fields (field (name "MPN") "RC0805JR-071KL"))
      (libsource (lib "eagle-import") (part "SMD-RES-1K-5%-1/8W(0805)"))
    )
    (comp (ref "R396")
      (value "1002")
      (footprint "eagle-import:R0805")
      (fields (field (name "MPN") "RC0805JR-071KL"))
      (libsource (lib "eagle-import") (part "SMD-RES-1K-5%-1/8W(0805)"))
    )
    (comp (ref "R397")
      (value "R_user")
      (footprint "eagle-import:R0805")
      (libsource (lib "eagle-import") (part "R-EU_R0805"))
    )
    (comp (ref "R398")
      (value "104")
      (footprint "eagle-import:R0805")
      (fields (field (name "MPN") "RC0805FR-0710KL"))
      (libsource (lib "eagle-import") (part "SMD-RES-10K-1%-1/8W(0805)"))
    )
    (comp (ref "R399")
      (value "104")
      (footprint "eagle-import:R0805")
      (fields (field (name "MPN") "RC0805FR-0710KL"))
      (libsource (lib "eagle-import") (part "SMD-RES-10K-1%-1/8W(0805)"))
    )
    (comp (ref "R400")
      (value "104")
      (footprint "eagle-import:R0805")
      (fields (field (name "MPN") "RC0805FR-0710KL"))
      (libsource (lib "eagle-import") (part "SMD-RES-10K-1%-1/8W(0805)"))
    )
    (comp (ref "R401")
      (value "13")
      (footprint "eagle-import:R1206")
      (fields (field (name "MPN") "RC1206JR-0713RL"))
      (libsource (lib "eagle-import") (part "SMD-RES-13R-5%-1/4W(1206)"))
    )
    (comp (ref "R402")
      (value "2201")
      (footprint "eagle-import:R0805")
      (fields (field (name "MPN") "RC0805JR-071KL"))
      (libsource (lib "eagle-import") (part "SMD-RES-1K-5%-1/8W(0805)"))
    )
    (comp (ref "R403")
      (value "100")
      (footprint "eagle-import:R0805")
      (fields (field (name "MPN") "RC0805JR-07220RL"))
      (libsource (lib "eagle-import") (part "SMD-RES-220R-5%-1/8W(0805)"))
    )
    (comp (ref "R404")
      (value "13")
      (footprint "eagle-import:R1206")
      (fields (field (name "MPN") "RC1206JR-0713RL"))
      (libsource (lib "eagle-import") (part "SMD-RES-13R-5%-1/4W(1206)"))
    )
    (comp (ref "R405")
      (value "4701")
      (footprint "eagle-import:R0805")
      (fields (field (name "MPN") "RC0805JR-074K7L"))
      (libsource (lib "eagle-import") (part "SMD-RES-4.7K-5%-1/8W(0805)"))
    )
    (comp (ref "R406")
      (value "104")
      (footprint "eagle-import:R0805")
      (fields (field (name "MPN") "RC0805JR-074K7L"))
      (libsource (lib "eagle-import") (part "SMD-RES-4.7K-5%-1/8W(0805)"))
    )
    (comp (ref "R407")
      (value "100")
      (footprint "eagle-import:R0805")
      (fields (field (name "MPN") "RC0805JR-072K2L"))
      (libsource (lib "eagle-import") (part "SMD-RES-2.2K-5%-1/8W(0805)"))
    )
    (comp (ref "R408")
      (value "100")
      (footprint "eagle-import:R0805")
      (fields (field (name "MPN") "RC0805JR-072K2L"))
      (libsource (lib "eagle-import") (part "SMD-RES-2.2K-5%-1/8W(0805)"))
    )
    (comp (ref "SJMP7")
      (value "SJ")
      (footprint "eagle-import:SJ")
      (libsource (lib "eagle-import") (part "SJ"))
    )
    (comp (ref "START7")
      (value "TPSB2.0")
      (footprint "eagle-import:B2.0")
      (libsource (lib "eagle-import") (part "TPSB2.0"))
    )
    (comp (ref "TP162")
      (value "TPSB2.0")
      (footprint "eagle-import:B2.0")
      (libsource (lib "eagle-import") (part "TPSB2.0"))
    )
    (comp (ref "TP163")
      (value "TPSB2.0")
      (footprint "eagle-import:B2.0")
      (libsource (lib "eagle-import") (part "TPSB2.0"))
    )
    (comp (ref "TP164")
      (value "TPSB2.0")
      (footprint "eagle-import:B2.0")
      (libsource (lib "eagle-import") (part "TPSB2.0"))
    )
    (comp (ref "TP165")
      (value "TPSB2.0")
      (footprint "eagle-import:B2.0")
      (libsource (lib "eagle-import") (part "TPSB2.0"))
    )
    (comp (ref "TP166")
      (value "TPSB2.0")
      (footprint "eagle-import:B2.0")
      (libsource (lib "eagle-import") (part "TPSB2.0"))
    )
    (comp (ref "TP167")
      (value "TPSB2.0")
      (footprint "eagle-import:B2.0")
      (libsource (lib "eagle-import") (part "TPSB2.0"))
    )
    (comp (ref "TP168")
      (value "TPSB2.0")
      (footprint "eagle-import:B2.0")
      (libsource (lib "eagle-import") (part "TPSB2.0"))
    )
    (comp (ref "TP169")
      (value "TPSB2.0")
      (footprint "eagle-import:B2.0")
      (libsource (lib "eagle-import") (part "TPSB2.0"))
    )
    (comp (ref "TP170")
      (value "TPSB2.0")
      (footprint "eagle-import:B2.0")
      (libsource (lib "eagle-import") (part "TPSB2.0"))
    )
    (comp (ref "TP171")
      (value "TPSB2.0")
      (footprint "eagle-import:B2.0")
      (libsource (lib "eagle-import") (part "TPSB2.0"))
    )
    (comp (ref "TP172")
      (value "TPSB2.0")
      (footprint "eagle-import:B2.0")
      (libsource (lib "eagle-import") (part "TPSB2.0"))
    )
    (comp (ref "TP173")
      (value "TPSB2.0")
      (footprint "eagle-import:B2.0")
      (libsource (lib "eagle-import") (part "TPSB2.0"))
    )
    (comp (ref "TP174")
      (value "TPSB2.0")
      (footprint "eagle-import:B2.0")
      (libsource (lib "eagle-import") (part "TPSB2.0"))
    )
    (comp (ref "TP175")
      (value "TPSB2.0")
      (footprint "eagle-import:B2.0")
      (libsource (lib "eagle-import") (part "TPSB2.0"))
    )
    (comp (ref "TP176")
      (value "TPSB2.0")
      (footprint "eagle-import:B2.0")
      (libsource (lib "eagle-import") (part "TPSB2.0"))
    )
    (comp (ref "TP177")
      (value "TPSB2.0")
      (footprint "eagle-import:B2.0")
      (libsource (lib "eagle-import") (part "TPSB2.0"))
    )
    (comp (ref "TP178")
      (value "TPSB2.0")
      (footprint "eagle-import:B2.0")
      (libsource (lib "eagle-import") (part "TPSB2.0"))
    )
    (comp (ref "TP179")
      (value "TPSB2.0")
      (footprint "eagle-import:B2.0")
      (libsource (lib "eagle-import") (part "TPSB2.0"))
    )
    (comp (ref "TP180")
      (value "TPSB1,27")
      (footprint "eagle-import:B1,27")
      (libsource (lib "eagle-import") (part "TPSB1,27"))
    )
    (comp (ref "TP181")
      (value "TPSB2.0")
      (footprint "eagle-import:B2.0")
      (libsource (lib "eagle-import") (part "TPSB2.0"))
    )
    (comp (ref "TP182")
      (value "TPSB2.0")
      (footprint "eagle-import:B2.0")
      (libsource (lib "eagle-import") (part "TPSB2.0"))
    )
    (comp (ref "TP183")
      (value "TPSB2.0")
      (footprint "eagle-import:B2.0")
      (libsource (lib "eagle-import") (part "TPSB2.0"))
    )
    (comp (ref "TP184")
      (value "TPSB2.0")
      (footprint "eagle-import:B2.0")
      (libsource (lib "eagle-import") (part "TPSB2.0"))
    )
    (comp (ref "X19")
      (value "CON_BMWV2")
      (footprint "eagle-import:24-PIN_V2")
      (libsource (lib "eagle-import") (part "CON_BMWV2"))
    )
    (comp (ref "X20")
      (value "22-23-2051")
      (footprint "eagle-import:22-23-2051")
      (fields (field (name "MF") "MOLEX"))
      (libsource (lib "eagle-import") (part "22-23-2051"))
    )
    (comp (ref "X21")
      (value "22-23-2021")
      (footprint "eagle-import:22-23-2021")
      (fields (field (name "MF") "MOLEX"))
      (libsource (lib "eagle-import") (part "22-23-2021"))
    )
    (comp (ref "6V10")
      (value "TPSB2.0")
      (footprint "eagle-import:B2.0")
      (libsource (lib "eagle-import") (part "TPSB2.0"))
    )
    (comp (ref "10V10")
      (value "TPSB2.0")
      (footprint "eagle-import:B2.0")
      (libsource (lib "eagle-import") (part "TPSB2.0"))
    )
    (comp (ref "21")
      (value "2081-1132")
      (footprint "eagle-import:12-PIN")
      (libsource (lib "eagle-import") (part "2081-1132"))
    )
    (comp (ref "22")
      (value "2081-1132")
      (footprint "eagle-import:12-PIN")
      (libsource (lib "eagle-import") (part "2081-1132"))
    )
    (comp (ref "C121")
      (value "100u")
      (footprint "eagle-import:C1206")
      (fields (field (name "MPN") "GRM31CR60J107ME39L"))
      (libsource (lib "eagle-import") (part "CERAMIC-100UF-6.3V-20%-X5R(1206)"))
    )
    (comp (ref "C122")
      (value "100u")
      (footprint "eagle-import:C1206")
      (fields (field (name "MPN") "GRM31CR60J107ME39L"))
      (libsource (lib "eagle-import") (part "CERAMIC-100UF-6.3V-20%-X5R(1206)"))
    )
    (comp (ref "C123")
      (value "100nF,")
      (footprint "eagle-import:C0805")
      (fields (field (name "MPN") "CC0805KRX7R9BB104"))
      (libsource (lib "eagle-import") (part "CERAMIC-100NF-50V-10%-X7R(0805)"))
    )
    (comp (ref "C124")
      (value "4.7u")
      (footprint "eagle-import:C0805")
      (fields (field (name "MPN") "CC0805KKX5R8BB475"))
      (libsource (lib "eagle-import") (part "CERAMIC-4.7UF-25V-10%-X5R(0805)"))
    )
    (comp (ref "C125")
      (value "100nF.")
      (footprint "eagle-import:C0805")
      (fields (field (name "MPN") "CC0805KRX7R9BB104"))
      (libsource (lib "eagle-import") (part "CERAMIC-100NF-50V-10%-X7R(0805)"))
    )
    (comp (ref "C126")
      (value "100nF.")
      (footprint "eagle-import:C0805")
      (fields (field (name "MPN") "CC0805KRX7R9BB104"))
      (libsource (lib "eagle-import") (part "CERAMIC-100NF-50V-10%-X7R(0805)"))
    )
    (comp (ref "C127")
      (value "2.2nF")
      (footprint "eagle-import:C0805")
      (fields (field (name "MPN") "CC0805KRX7R9BB104"))
      (libsource (lib "eagle-import") (part "CERAMIC-100NF-50V-10%-X7R(0805)"))
    )
    (comp (ref "C128")
      (value "100nF")
      (footprint "eagle-import:C0805")
      (fields (field (name "MPN") "CC0805KRX7R9BB104"))
      (libsource (lib "eagle-import") (part "CERAMIC-100NF-50V-10%-X7R(0805)"))
    )
    (comp (ref "C129")
      (value "100nF")
      (footprint "eagle-import:C0805")
      (fields (field (name "MPN") "CC0805KRX7R9BB104"))
      (libsource (lib "eagle-import") (part "CERAMIC-100NF-50V-10%-X7R(0805)"))
    )
    (comp (ref "C130")
      (value "100nF,")
      (footprint "eagle-import:C0805")
      (fields (field (name "MPN") "CC0805KRX7R9BB104"))
      (libsource (lib "eagle-import") (part "CERAMIC-100NF-50V-10%-X7R(0805)"))
    )
    (comp (ref "C131")
      (value "4.7u")
      (footprint "eagle-import:C0805")
      (fields (field (name "MPN") "CC0805KKX5R8BB475"))
      (libsource (lib "eagle-import") (part "CERAMIC-4.7UF-25V-10%-X5R(0805)"))
    )
    (comp (ref "C132")
      (value "10u")
      (footprint "eagle-import:C1206")
      (fields (field (name "MPN") "GRM31CR60J107ME39L"))
      (libsource (lib "eagle-import") (part "CERAMIC-100UF-6.3V-20%-X5R(1206)"))
    )
    (comp (ref "D131")
      (value "1N4007,")
      (footprint "eagle-import:DO-214AC")
      (fields (field (name "MPN") "1N4007"))
      (libsource (lib "eagle-import") (part "DIODE-GEN-PURPOSE-1KV-1A(DO-214AC)"))
    )
    (comp (ref "D132")
      (value "1N4007,")
      (footprint "eagle-import:DO-214AC")
      (fields (field (name "MPN") "1N4007"))
      (libsource (lib "eagle-import") (part "DIODE-GEN-PURPOSE-1KV-1A(DO-214AC)"))
    )
    (comp (ref "D133")
      (value "1N4007.")
      (footprint "eagle-import:DO-214AC")
      (fields (field (name "MPN") "1N4007"))
      (libsource (lib "eagle-import") (part "DIODE-GEN-PURPOSE-1KV-1A(DO-214AC)"))
    )
    (comp (ref "D134")
      (value "1N5817")
      (footprint "eagle-import:DO-214AC_SLIM")
      (libsource (lib "eagle-import") (part "DIODE-GEN-PURPOSE-1KV-1A(DO-214AC)DO-214AC/1206"))
    )
    (comp (ref "D135")
      (value "1N5817.")
      (footprint "eagle-import:DO-214AC_SLIM")
      (libsource (lib "eagle-import") (part "DIODE-GEN-PURPOSE-1KV-1A(DO-214AC)DO-214AC/1206"))
    )
    (comp (ref "D136")
      (value "1N5817.")
      (footprint "eagle-import:DO-214AC_SLIM")
      (libsource (lib "eagle-import") (part "DIODE-GEN-PURPOSE-1KV-1A(DO-214AC)DO-214AC/1206"))
    )
    (comp (ref "D137")
      (value "1N5817")
      (footprint "eagle-import:DO-214AC_SLIM")
      (libsource (lib "eagle-import") (part "DIODE-GEN-PURPOSE-1KV-1A(DO-214AC)DO-214AC/1206"))
    )
    (comp (ref "D138")
      (value "1N4007.")
      (footprint "eagle-import:DO-214AC")
      (fields (field (name "MPN") "1N4007"))
      (libsource (lib "eagle-import") (part "DIODE-GEN-PURPOSE-1KV-1A(DO-214AC)"))
    )
    (comp (ref "D139")
      (value "1N4007")
      (footprint "eagle-import:DO-214AC")
      (libsource (lib "eagle-import") (part "DIODE-GEN-PURPOSE-1KV-1A(DO-214AC)"))
    )
    (comp (ref "D140")
      (value "Zen15")
      (footprint "eagle-import:DO214AA")
      (libsource (lib "eagle-import") (part "SM6T"))
    )
    (comp (ref "D141")
      (value "SS12")
      (footprint "eagle-import:DO-214AC_SLIM")
      (libsource (lib "eagle-import") (part "DIODE-GEN-PURPOSE-1KV-1A(DO-214AC)DO-214AC/1206"))
    )
    (comp (ref "D142")
      (value "SS12")
      (footprint "eagle-import:DO-214AC_SLIM")
      (libsource (lib "eagle-import") (part "DIODE-GEN-PURPOSE-1KV-1A(DO-214AC)DO-214AC/1206"))
    )
    (comp (ref "D143")
      (value "Zen11")
      (footprint "eagle-import:SOD-123_MINI-SMA")
      (libsource (lib "eagle-import") (part "CGRM400-G1"))
    )
    (comp (ref "FID41")
      (value "FIDUCIAL")
      (footprint "eagle-import:FIDUCIAL_1MM")
      (libsource (lib "eagle-import") (part "FIDUCIAL"))
    )
    (comp (ref "FID42")
      (value "FIDUCIAL")
      (footprint "eagle-import:FIDUCIAL_1MM")
      (libsource (lib "eagle-import") (part "FIDUCIAL"))
    )
    (comp (ref "FID43")
      (value "FIDUCIAL")
      (footprint "eagle-import:FIDUCIAL_1MM")
      (libsource (lib "eagle-import") (part "FIDUCIAL"))
    )
    (comp (ref "FID44")
      (value "FIDUCIAL")
      (footprint "eagle-import:FIDUCIAL_1MM")
      (libsource (lib "eagle-import") (part "FIDUCIAL"))
    )
    (comp (ref "IC82")
      (value "4028")
      (footprint "eagle-import:SO16")
      (libsource (lib "eagle-import") (part "4028D"))
    )
    (comp (ref "IC83")
      (value "317TO202H_NOHOLE")
      (footprint "eagle-import:TO220H_NOHOLE")
      (libsource (lib "eagle-import") (part "317TO202H_NOHOLE"))
    )
    (comp (ref "IC84")
      (value "ULN2004")
      (footprint "eagle-import:SO16")
      (libsource (lib "eagle-import") (part "ULN2004AD"))
    )
    (comp (ref "IC85")
      (value "LM339")
      (footprint "eagle-import:SO14")
      (libsource (lib "eagle-import") (part "LM339D"))
    )
    (comp (ref "IC86")
      (value "78L06")
      (footprint "eagle-import:SOT89_ROUND")
      (libsource (lib "eagle-import") (part "78LXXSOT89_ROUND"))
    )
    (comp (ref "IC87")
      (value "555")
      (footprint "eagle-import:SO08")
      (libsource (lib "eagle-import") (part "555DNE"))
    )
    (comp (ref "IC88")
      (value "4538")
      (footprint "eagle-import:SO16")
      (libsource (lib "eagle-import") (part "4538D"))
    )
    (comp (ref "IC89")
      (value "78L10")
      (footprint "eagle-import:SOT89_ROUND")
      (libsource (lib "eagle-import") (part "78LXXSOT89_ROUND"))
    )
    (comp (ref "IC90")
      (value "LM2904")
      (footprint "eagle-import:SO08")
      (libsource (lib "eagle-import") (part "LM358D"))
    )
    (comp (ref "JP46")
      (value "JP2EJP2_SMALLPADS")
      (footprint "eagle-import:JP2_SMALLPADS")
      (libsource (lib "eagle-import") (part "JP2EJP2_SMALLPADS"))
    )
    (comp (ref "JP47")
      (value "JP2E_ORIG")
      (footprint "eagle-import:JP2_ORIG_SMALLPADS")
      (libsource (lib "eagle-import") (part "JP2E_ORIG"))
    )
    (comp (ref "JP48")
      (value "JP2EJP2_SMALLPADS")
      (footprint "eagle-import:JP2_SMALLPADS")
      (libsource (lib "eagle-import") (part "JP2EJP2_SMALLPADS"))
    )
    (comp (ref "JP49")
      (value "JP2EJP2_SMALLPADS")
      (footprint "eagle-import:JP2_SMALLPADS")
      (libsource (lib "eagle-import") (part "JP2EJP2_SMALLPADS"))
    )
    (comp (ref "JP50")
      (value "JP2EJP2_SMALLPADS")
      (footprint "eagle-import:JP2_SMALLPADS")
      (libsource (lib "eagle-import") (part "JP2EJP2_SMALLPADS"))
    )
    (comp (ref "LED55")
      (value "LEDLD260")
      (footprint "eagle-import:LD260")
      (libsource (lib "eagle-import") (part "LEDLD260"))
    )
    (comp (ref "LED56")
      (value "LEDLD260")
      (footprint "eagle-import:LD260")
      (libsource (lib "eagle-import") (part "LEDLD260"))
    )
    (comp (ref "LED57")
      (value "LEDLD260")
      (footprint "eagle-import:LD260")
      (libsource (lib "eagle-import") (part "LEDLD260"))
    )
    (comp (ref "LED58")
      (value "LEDLD260")
      (footprint "eagle-import:LD260")
      (libsource (lib "eagle-import") (part "LEDLD260"))
    )
    (comp (ref "LED59")
      (value "LEDLD260")
      (footprint "eagle-import:LD260")
      (libsource (lib "eagle-import") (part "LEDLD260"))
    )
    (comp (ref "LED60")
      (value "LEDLD260")
      (footprint "eagle-import:LD260")
      (libsource (lib "eagle-import") (part "LEDLD260"))
    )
    (comp (ref "Q94")
      (value "BA")
      (footprint "eagle-import:SOT89")
      (libsource (lib "eagle-import") (part "PNP-TRANSISTOR_SOT89"))
    )
    (comp (ref "Q95")
      (value "BA.")
      (footprint "eagle-import:SOT89")
      (libsource (lib "eagle-import") (part "PNP-TRANSISTOR_SOT89"))
    )
    (comp (ref "Q96")
      (value "BA.")
      (footprint "eagle-import:SOT89")
      (libsource (lib "eagle-import") (part "PNP-TRANSISTOR_SOT89"))
    )
    (comp (ref "Q97")
      (value "BA")
      (footprint "eagle-import:SOT89")
      (libsource (lib "eagle-import") (part "PNP-TRANSISTOR_SOT89"))
    )
    (comp (ref "Q98")
      (value "MY")
      (footprint "eagle-import:SOT89")
      (libsource (lib "eagle-import") (part "NPN-TRANSISTOR_SOT89"))
    )
    (comp (ref "Q99")
      (value "J1")
      (footprint "eagle-import:SOT-23")
      (fields (field (name "MPN") "BSS138W-7-F"))
      (libsource (lib "eagle-import") (part "SMD-MOSFET-N-CH-50V-200MA-BSS138W-7-F(SOT-23)"))
    )
    (comp (ref "Q100")
      (value "J1")
      (footprint "eagle-import:SOT-23")
      (fields (field (name "MPN") "BSS138W-7-F"))
      (libsource (lib "eagle-import") (part "SMD-MOSFET-N-CH-50V-200MA-BSS138W-7-F(SOT-23)"))
    )
    (comp (ref "Q108")
      (value "J1")
      (footprint "eagle-import:SOT-23")
      (fields (field (name "MPN") "BSS138W-7-F"))
      (libsource (lib "eagle-import") (part "SMD-MOSFET-N-CH-50V-200MA-BSS138W-7-F(SOT-23)"))
    )
    (comp (ref "Q109")
      (value "BA")
      (footprint "eagle-import:SOT89")
      (libsource (lib "eagle-import") (part "PNP-TRANSISTOR_SOT89"))
    )
    (comp (ref "Q110")
      (value "J1")
      (footprint "eagle-import:SOT-23")
      (fields (field (name "MPN") "BSS138W-7-F"))
      (libsource (lib "eagle-import") (part "SMD-MOSFET-N-CH-50V-200MA-BSS138W-7-F(SOT-23)"))
    )
    (comp (ref "R511")
      (value "47")
      (footprint "eagle-import:V235_17_1MM")
      (libsource (lib "eagle-import") (part "R-EU_V235/17_1MM"))
    )
    (comp (ref "R512")
      (value "13")
      (footprint "eagle-import:R1206")
      (fields (field (name "MPN") "RC1206JR-0713RL"))
      (libsource (lib "eagle-import") (part "SMD-RES-13R-5%-1/4W(1206)"))
    )
    (comp (ref "R513")
      (value "47")
      (footprint "eagle-import:V235_17_1MM")
      (libsource (lib "eagle-import") (part "R-EU_V235/17_1MM"))
    )
    (comp (ref "R514")
      (value "104")
      (footprint "eagle-import:R0805")
      (fields (field (name "MPN") "RC0805FR-0710KL"))
      (libsource (lib "eagle-import") (part "SMD-RES-10K-1%-1/8W(0805)"))
    )
    (comp (ref "R515")
      (value "104")
      (footprint "eagle-import:R0805")
      (fields (field (name "MPN") "RC0805FR-0710KL"))
      (libsource (lib "eagle-import") (part "SMD-RES-10K-1%-1/8W(0805)"))
    )
    (comp (ref "R516")
      (value "104")
      (footprint "eagle-import:R0805")
      (fields (field (name "MPN") "RC0805FR-0710KL"))
      (libsource (lib "eagle-import") (part "SMD-RES-10K-1%-1/8W(0805)"))
    )
    (comp (ref "R517")
      (value "4701")
      (footprint "eagle-import:R0805")
      (fields (field (name "MPN") "RC0805JR-074K7L"))
      (libsource (lib "eagle-import") (part "SMD-RES-4.7K-5%-1/8W(0805)"))
    )
    (comp (ref "R518")
      (value "1002")
      (footprint "eagle-import:R0805")
      (fields (field (name "MPN") "RC0805FR-0710KL"))
      (libsource (lib "eagle-import") (part "SMD-RES-10K-1%-1/8W(0805)"))
    )
    (comp (ref "R519")
      (value "1002")
      (footprint "eagle-import:R0805")
      (fields (field (name "MPN") "RC0805FR-0710KL"))
      (libsource (lib "eagle-import") (part "SMD-RES-10K-1%-1/8W(0805)"))
    )
    (comp (ref "R520")
      (value "1502")
      (footprint "eagle-import:R0805")
      (fields (field (name "MPN") "RC0805FR-0710KL"))
      (libsource (lib "eagle-import") (part "SMD-RES-10K-1%-1/8W(0805)"))
    )
    (comp (ref "R521")
      (value "104")
      (footprint "eagle-import:R0805")
      (fields (field (name "MPN") "RC0805FR-0710KL"))
      (libsource (lib "eagle-import") (part "SMD-RES-10K-1%-1/8W(0805)"))
    )
    (comp (ref "R522")
      (value "104")
      (footprint "eagle-import:R0805")
      (fields (field (name "MPN") "RC0805FR-0710KL"))
      (libsource (lib "eagle-import") (part "SMD-RES-10K-1%-1/8W(0805)"))
    )
    (comp (ref "R523")
      (value "1502")
      (footprint "eagle-import:R0805")
      (fields (field (name "MPN") "RC0805FR-0710KL"))
      (libsource (lib "eagle-import") (part "SMD-RES-10K-1%-1/8W(0805)"))
    )
    (comp (ref "R524")
      (value "1002")
      (footprint "eagle-import:R0805")
      (fields (field (name "MPN") "RC0805FR-0710KL"))
      (libsource (lib "eagle-import") (part "SMD-RES-10K-1%-1/8W(0805)"))
    )
    (comp (ref "R525")
      (value "2201")
      (footprint "eagle-import:R0805")
      (fields (field (name "MPN") "RC0805JR-072K2L"))
      (libsource (lib "eagle-import") (part "SMD-RES-2.2K-5%-1/8W(0805)"))
    )
    (comp (ref "R526")
      (value "1002")
      (footprint "eagle-import:R0805")
      (fields (field (name "MPN") "RC0805FR-0710KL"))
      (libsource (lib "eagle-import") (part "SMD-RES-10K-1%-1/8W(0805)"))
    )
    (comp (ref "R527")
      (value "4701")
      (footprint "eagle-import:R0805")
      (fields (field (name "MPN") "RC0805JR-074K7L"))
      (libsource (lib "eagle-import") (part "SMD-RES-4.7K-5%-1/8W(0805)"))
    )
    (comp (ref "R528")
      (value "2702")
      (footprint "eagle-import:R0805")
      (fields (field (name "MPN") "RC0805JR-074K7L"))
      (libsource (lib "eagle-import") (part "SMD-RES-4.7K-5%-1/8W(0805)"))
    )
    (comp (ref "R529")
      (value "102")
      (footprint "eagle-import:R0805")
      (fields (field (name "MPN") "RC0805JR-071KL"))
      (libsource (lib "eagle-import") (part "SMD-RES-1K-5%-1/8W(0805)"))
    )
    (comp (ref "R530")
      (value "102")
      (footprint "eagle-import:R0805")
      (fields (field (name "MPN") "RC0805JR-07220RL"))
      (libsource (lib "eagle-import") (part "SMD-RES-220R-5%-1/8W(0805)"))
    )
    (comp (ref "R531")
      (value "102")
      (footprint "eagle-import:R0805")
      (fields (field (name "MPN") "RC0805JR-071KL"))
      (libsource (lib "eagle-import") (part "SMD-RES-1K-5%-1/8W(0805)"))
    )
    (comp (ref "R532")
      (value "13")
      (footprint "eagle-import:R1206")
      (fields (field (name "MPN") "RC1206JR-0713RL"))
      (libsource (lib "eagle-import") (part "SMD-RES-13R-5%-1/4W(1206)"))
    )
    (comp (ref "R533")
      (value "13")
      (footprint "eagle-import:R1206")
      (fields (field (name "MPN") "RC1206JR-0713RL"))
      (libsource (lib "eagle-import") (part "SMD-RES-13R-5%-1/4W(1206)"))
    )
    (comp (ref "R534")
      (value "2702")
      (footprint "eagle-import:R0805")
      (fields (field (name "MPN") "RC0805JR-074K7L"))
      (libsource (lib "eagle-import") (part "SMD-RES-4.7K-5%-1/8W(0805)"))
    )
    (comp (ref "R535")
      (value "4701")
      (footprint "eagle-import:R0805")
      (fields (field (name "MPN") "RC0805JR-074K7L"))
      (libsource (lib "eagle-import") (part "SMD-RES-4.7K-5%-1/8W(0805)"))
    )
    (comp (ref "R536")
      (value "100")
      (footprint "eagle-import:R0805")
      (fields (field (name "MPN") "RC0805JR-072K2L"))
      (libsource (lib "eagle-import") (part "SMD-RES-2.2K-5%-1/8W(0805)"))
    )
    (comp (ref "R537")
      (value "104")
      (footprint "eagle-import:R0805")
      (fields (field (name "MPN") "RC0805FR-0710KL"))
      (libsource (lib "eagle-import") (part "SMD-RES-10K-1%-1/8W(0805)"))
    )
    (comp (ref "R538")
      (value "104")
      (footprint "eagle-import:R0805")
      (fields (field (name "MPN") "RC0805FR-0710KL"))
      (libsource (lib "eagle-import") (part "SMD-RES-10K-1%-1/8W(0805)"))
    )
    (comp (ref "R539")
      (value "2702")
      (footprint "eagle-import:R0805")
      (fields (field (name "MPN") "RC0805FR-0710KL"))
      (libsource (lib "eagle-import") (part "SMD-RES-10K-1%-1/8W(0805)"))
    )
    (comp (ref "R540")
      (value "47")
      (footprint "eagle-import:V235_17_1MM")
      (libsource (lib "eagle-import") (part "R-EU_V235/17_1MM"))
    )
    (comp (ref "R541")
      (value "47")
      (footprint "eagle-import:V235_17_1MM")
      (libsource (lib "eagle-import") (part "R-EU_V235/17_1MM"))
    )
    (comp (ref "R542")
      (value "2702")
      (footprint "eagle-import:R0805")
      (fields (field (name "MPN") "RC0805JR-074K7L"))
      (libsource (lib "eagle-import") (part "SMD-RES-4.7K-5%-1/8W(0805)"))
    )
    (comp (ref "R543")
      (value "2201")
      (footprint "eagle-import:R0805")
      (fields (field (name "MPN") "RC0805JR-072K2L"))
      (libsource (lib "eagle-import") (part "SMD-RES-2.2K-5%-1/8W(0805)"))
    )
    (comp (ref "R544")
      (value "1002")
      (footprint "eagle-import:R0805")
      (fields (field (name "MPN") "RC0805JR-074K7L"))
      (libsource (lib "eagle-import") (part "SMD-RES-4.7K-5%-1/8W(0805)"))
    )
    (comp (ref "R545")
      (value "1002")
      (footprint "eagle-import:R0805")
      (fields (field (name "MPN") "RC0805FR-0710KL"))
      (libsource (lib "eagle-import") (part "SMD-RES-10K-1%-1/8W(0805)"))
    )
    (comp (ref "R546")
      (value "102")
      (footprint "eagle-import:R0805")
      (fields (field (name "MPN") "RC0805JR-071KL"))
      (libsource (lib "eagle-import") (part "SMD-RES-1K-5%-1/8W(0805)"))
    )
    (comp (ref "R547")
      (value "2702")
      (footprint "eagle-import:R0805")
      (fields (field (name "MPN") "RC0805JR-074K7L"))
      (libsource (lib "eagle-import") (part "SMD-RES-4.7K-5%-1/8W(0805)"))
    )
    (comp (ref "R548")
      (value "1002")
      (footprint "eagle-import:R0805")
      (fields (field (name "MPN") "RC0805JR-071KL"))
      (libsource (lib "eagle-import") (part "SMD-RES-1K-5%-1/8W(0805)"))
    )
    (comp (ref "R549")
      (value "1002")
      (footprint "eagle-import:R0805")
      (fields (field (name "MPN") "RC0805JR-071KL"))
      (libsource (lib "eagle-import") (part "SMD-RES-1K-5%-1/8W(0805)"))
    )
    (comp (ref "R550")
      (value "R_user")
      (footprint "eagle-import:R0805")
      (libsource (lib "eagle-import") (part "R-EU_R0805"))
    )
    (comp (ref "R551")
      (value "104")
      (footprint "eagle-import:R0805")
      (fields (field (name "MPN") "RC0805FR-0710KL"))
      (libsource (lib "eagle-import") (part "SMD-RES-10K-1%-1/8W(0805)"))
    )
    (comp (ref "R552")
      (value "104")
      (footprint "eagle-import:R0805")
      (fields (field (name "MPN") "RC0805FR-0710KL"))
      (libsource (lib "eagle-import") (part "SMD-RES-10K-1%-1/8W(0805)"))
    )
    (comp (ref "R553")
      (value "104")
      (footprint "eagle-import:R0805")
      (fields (field (name "MPN") "RC0805FR-0710KL"))
      (libsource (lib "eagle-import") (part "SMD-RES-10K-1%-1/8W(0805)"))
    )
    (comp (ref "R554")
      (value "13")
      (footprint "eagle-import:R1206")
      (fields (field (name "MPN") "RC1206JR-0713RL"))
      (libsource (lib "eagle-import") (part "SMD-RES-13R-5%-1/4W(1206)"))
    )
    (comp (ref "R555")
      (value "2201")
      (footprint "eagle-import:R0805")
      (fields (field (name "MPN") "RC0805JR-071KL"))
      (libsource (lib "eagle-import") (part "SMD-RES-1K-5%-1/8W(0805)"))
    )
    (comp (ref "R556")
      (value "100")
      (footprint "eagle-import:R0805")
      (fields (field (name "MPN") "RC0805JR-07220RL"))
      (libsource (lib "eagle-import") (part "SMD-RES-220R-5%-1/8W(0805)"))
    )
    (comp (ref "R557")
      (value "13")
      (footprint "eagle-import:R1206")
      (fields (field (name "MPN") "RC1206JR-0713RL"))
      (libsource (lib "eagle-import") (part "SMD-RES-13R-5%-1/4W(1206)"))
    )
    (comp (ref "R558")
      (value "4701")
      (footprint "eagle-import:R0805")
      (fields (field (name "MPN") "RC0805JR-074K7L"))
      (libsource (lib "eagle-import") (part "SMD-RES-4.7K-5%-1/8W(0805)"))
    )
    (comp (ref "R559")
      (value "104")
      (footprint "eagle-import:R0805")
      (fields (field (name "MPN") "RC0805JR-074K7L"))
      (libsource (lib "eagle-import") (part "SMD-RES-4.7K-5%-1/8W(0805)"))
    )
    (comp (ref "R560")
      (value "100")
      (footprint "eagle-import:R0805")
      (fields (field (name "MPN") "RC0805JR-072K2L"))
      (libsource (lib "eagle-import") (part "SMD-RES-2.2K-5%-1/8W(0805)"))
    )
    (comp (ref "R561")
      (value "100")
      (footprint "eagle-import:R0805")
      (fields (field (name "MPN") "RC0805JR-072K2L"))
      (libsource (lib "eagle-import") (part "SMD-RES-2.2K-5%-1/8W(0805)"))
    )
    (comp (ref "SJMP10")
      (value "SJ")
      (footprint "eagle-import:SJ")
      (libsource (lib "eagle-import") (part "SJ"))
    )
    (comp (ref "START10")
      (value "TPSB2.0")
      (footprint "eagle-import:B2.0")
      (libsource (lib "eagle-import") (part "TPSB2.0"))
    )
    (comp (ref "TP231")
      (value "TPSB2.0")
      (footprint "eagle-import:B2.0")
      (libsource (lib "eagle-import") (part "TPSB2.0"))
    )
    (comp (ref "TP232")
      (value "TPSB2.0")
      (footprint "eagle-import:B2.0")
      (libsource (lib "eagle-import") (part "TPSB2.0"))
    )
    (comp (ref "TP233")
      (value "TPSB2.0")
      (footprint "eagle-import:B2.0")
      (libsource (lib "eagle-import") (part "TPSB2.0"))
    )
    (comp (ref "TP234")
      (value "TPSB2.0")
      (footprint "eagle-import:B2.0")
      (libsource (lib "eagle-import") (part "TPSB2.0"))
    )
    (comp (ref "TP235")
      (value "TPSB2.0")
      (footprint "eagle-import:B2.0")
      (libsource (lib "eagle-import") (part "TPSB2.0"))
    )
    (comp (ref "TP236")
      (value "TPSB2.0")
      (footprint "eagle-import:B2.0")
      (libsource (lib "eagle-import") (part "TPSB2.0"))
    )
    (comp (ref "TP237")
      (value "TPSB2.0")
      (footprint "eagle-import:B2.0")
      (libsource (lib "eagle-import") (part "TPSB2.0"))
    )
    (comp (ref "TP238")
      (value "TPSB2.0")
      (footprint "eagle-import:B2.0")
      (libsource (lib "eagle-import") (part "TPSB2.0"))
    )
    (comp (ref "TP239")
      (value "TPSB2.0")
      (footprint "eagle-import:B2.0")
      (libsource (lib "eagle-import") (part "TPSB2.0"))
    )
    (comp (ref "TP240")
      (value "TPSB2.0")
      (footprint "eagle-import:B2.0")
      (libsource (lib "eagle-import") (part "TPSB2.0"))
    )
    (comp (ref "TP241")
      (value "TPSB2.0")
      (footprint "eagle-import:B2.0")
      (libsource (lib "eagle-import") (part "TPSB2.0"))
    )
    (comp (ref "TP242")
      (value "TPSB2.0")
      (footprint "eagle-import:B2.0")
      (libsource (lib "eagle-import") (part "TPSB2.0"))
    )
    (comp (ref "TP243")
      (value "TPSB2.0")
      (footprint "eagle-import:B2.0")
      (libsource (lib "eagle-import") (part "TPSB2.0"))
    )
    (comp (ref "TP244")
      (value "TPSB2.0")
      (footprint "eagle-import:B2.0")
      (libsource (lib "eagle-import") (part "TPSB2.0"))
    )
    (comp (ref "TP245")
      (value "TPSB2.0")
      (footprint "eagle-import:B2.0")
      (libsource (lib "eagle-import") (part "TPSB2.0"))
    )
    (comp (ref "TP246")
      (value "TPSB2.0")
      (footprint "eagle-import:B2.0")
      (libsource (lib "eagle-import") (part "TPSB2.0"))
    )
    (comp (ref "TP247")
      (value "TPSB2.0")
      (footprint "eagle-import:B2.0")
      (libsource (lib "eagle-import") (part "TPSB2.0"))
    )
    (comp (ref "TP248")
      (value "TPSB2.0")
      (footprint "eagle-import:B2.0")
      (libsource (lib "eagle-import") (part "TPSB2.0"))
    )
    (comp (ref "TP249")
      (value "TPSB1,27")
      (footprint "eagle-import:B1,27")
      (libsource (lib "eagle-import") (part "TPSB1,27"))
    )
    (comp (ref "TP250")
      (value "TPSB2.0")
      (footprint "eagle-import:B2.0")
      (libsource (lib "eagle-import") (part "TPSB2.0"))
    )
    (comp (ref "TP251")
      (value "TPSB2.0")
      (footprint "eagle-import:B2.0")
      (libsource (lib "eagle-import") (part "TPSB2.0"))
    )
    (comp (ref "TP252")
      (value "TPSB2.0")
      (footprint "eagle-import:B2.0")
      (libsource (lib "eagle-import") (part "TPSB2.0"))
    )
    (comp (ref "TP253")
      (value "TPSB2.0")
      (footprint "eagle-import:B2.0")
      (libsource (lib "eagle-import") (part "TPSB2.0"))
    )
    (comp (ref "X28")
      (value "CON_BMWV2")
      (footprint "eagle-import:24-PIN_V2")
      (libsource (lib "eagle-import") (part "CON_BMWV2"))
    )
    (comp (ref "X29")
      (value "22-23-2051")
      (footprint "eagle-import:22-23-2051")
      (fields (field (name "MF") "MOLEX"))
      (libsource (lib "eagle-import") (part "22-23-2051"))
    )
    (comp (ref "X30")
      (value "22-23-2021")
      (footprint "eagle-import:22-23-2021")
      (fields (field (name "MF") "MOLEX"))
      (libsource (lib "eagle-import") (part "22-23-2021"))
    )
    (comp (ref "5")
      (value "2081-1132")
      (footprint "eagle-import:12-PIN")
      (libsource (lib "eagle-import") (part "2081-1132"))
    )
    (comp (ref "6")
      (value "2081-1132")
      (footprint "eagle-import:12-PIN")
      (libsource (lib "eagle-import") (part "2081-1132"))
    )
    (comp (ref "6V2")
      (value "TPSB2.0")
      (footprint "eagle-import:B2.0")
      (libsource (lib "eagle-import") (part "TPSB2.0"))
    )
    (comp (ref "10V2")
      (value "TPSB2.0")
      (footprint "eagle-import:B2.0")
      (libsource (lib "eagle-import") (part "TPSB2.0"))
    )
    (comp (ref "C14")
      (value "100u")
      (footprint "eagle-import:C1206")
      (fields (field (name "MPN") "GRM31CR60J107ME39L"))
      (libsource (lib "eagle-import") (part "CERAMIC-100UF-6.3V-20%-X5R(1206)"))
    )
    (comp (ref "C16")
      (value "100u")
      (footprint "eagle-import:C1206")
      (fields (field (name "MPN") "GRM31CR60J107ME39L"))
      (libsource (lib "eagle-import") (part "CERAMIC-100UF-6.3V-20%-X5R(1206)"))
    )
    (comp (ref "C17")
      (value "100nF,")
      (footprint "eagle-import:C0805")
      (fields (field (name "MPN") "CC0805KRX7R9BB104"))
      (libsource (lib "eagle-import") (part "CERAMIC-100NF-50V-10%-X7R(0805)"))
    )
    (comp (ref "C18")
      (value "4.7u")
      (footprint "eagle-import:C0805")
      (fields (field (name "MPN") "CC0805KKX5R8BB475"))
      (libsource (lib "eagle-import") (part "CERAMIC-4.7UF-25V-10%-X5R(0805)"))
    )
    (comp (ref "C19")
      (value "100nF.")
      (footprint "eagle-import:C0805")
      (fields (field (name "MPN") "CC0805KRX7R9BB104"))
      (libsource (lib "eagle-import") (part "CERAMIC-100NF-50V-10%-X7R(0805)"))
    )
    (comp (ref "C20")
      (value "100nF.")
      (footprint "eagle-import:C0805")
      (fields (field (name "MPN") "CC0805KRX7R9BB104"))
      (libsource (lib "eagle-import") (part "CERAMIC-100NF-50V-10%-X7R(0805)"))
    )
    (comp (ref "C21")
      (value "2.2nF")
      (footprint "eagle-import:C0805")
      (fields (field (name "MPN") "CC0805KRX7R9BB104"))
      (libsource (lib "eagle-import") (part "CERAMIC-100NF-50V-10%-X7R(0805)"))
    )
    (comp (ref "C22")
      (value "100nF")
      (footprint "eagle-import:C0805")
      (fields (field (name "MPN") "CC0805KRX7R9BB104"))
      (libsource (lib "eagle-import") (part "CERAMIC-100NF-50V-10%-X7R(0805)"))
    )
    (comp (ref "C23")
      (value "100nF")
      (footprint "eagle-import:C0805")
      (fields (field (name "MPN") "CC0805KRX7R9BB104"))
      (libsource (lib "eagle-import") (part "CERAMIC-100NF-50V-10%-X7R(0805)"))
    )
    (comp (ref "C24")
      (value "100nF,")
      (footprint "eagle-import:C0805")
      (fields (field (name "MPN") "CC0805KRX7R9BB104"))
      (libsource (lib "eagle-import") (part "CERAMIC-100NF-50V-10%-X7R(0805)"))
    )
    (comp (ref "C25")
      (value "4.7u")
      (footprint "eagle-import:C0805")
      (fields (field (name "MPN") "CC0805KKX5R8BB475"))
      (libsource (lib "eagle-import") (part "CERAMIC-4.7UF-25V-10%-X5R(0805)"))
    )
    (comp (ref "C26")
      (value "10u")
      (footprint "eagle-import:C1206")
      (fields (field (name "MPN") "GRM31CR60J107ME39L"))
      (libsource (lib "eagle-import") (part "CERAMIC-100UF-6.3V-20%-X5R(1206)"))
    )
    (comp (ref "D18")
      (value "1N4007,")
      (footprint "eagle-import:DO-214AC")
      (fields (field (name "MPN") "1N4007"))
      (libsource (lib "eagle-import") (part "DIODE-GEN-PURPOSE-1KV-1A(DO-214AC)"))
    )
    (comp (ref "D19")
      (value "1N4007,")
      (footprint "eagle-import:DO-214AC")
      (fields (field (name "MPN") "1N4007"))
      (libsource (lib "eagle-import") (part "DIODE-GEN-PURPOSE-1KV-1A(DO-214AC)"))
    )
    (comp (ref "D20")
      (value "1N4007.")
      (footprint "eagle-import:DO-214AC")
      (fields (field (name "MPN") "1N4007"))
      (libsource (lib "eagle-import") (part "DIODE-GEN-PURPOSE-1KV-1A(DO-214AC)"))
    )
    (comp (ref "D21")
      (value "1N5817")
      (footprint "eagle-import:DO-214AC_SLIM")
      (libsource (lib "eagle-import") (part "DIODE-GEN-PURPOSE-1KV-1A(DO-214AC)DO-214AC/1206"))
    )
    (comp (ref "D22")
      (value "1N5817.")
      (footprint "eagle-import:DO-214AC_SLIM")
      (libsource (lib "eagle-import") (part "DIODE-GEN-PURPOSE-1KV-1A(DO-214AC)DO-214AC/1206"))
    )
    (comp (ref "D23")
      (value "1N5817.")
      (footprint "eagle-import:DO-214AC_SLIM")
      (libsource (lib "eagle-import") (part "DIODE-GEN-PURPOSE-1KV-1A(DO-214AC)DO-214AC/1206"))
    )
    (comp (ref "D24")
      (value "1N5817")
      (footprint "eagle-import:DO-214AC_SLIM")
      (libsource (lib "eagle-import") (part "DIODE-GEN-PURPOSE-1KV-1A(DO-214AC)DO-214AC/1206"))
    )
    (comp (ref "D25")
      (value "1N4007.")
      (footprint "eagle-import:DO-214AC")
      (fields (field (name "MPN") "1N4007"))
      (libsource (lib "eagle-import") (part "DIODE-GEN-PURPOSE-1KV-1A(DO-214AC)"))
    )
    (comp (ref "D26")
      (value "1N4007")
      (footprint "eagle-import:DO-214AC")
      (libsource (lib "eagle-import") (part "DIODE-GEN-PURPOSE-1KV-1A(DO-214AC)"))
    )
    (comp (ref "D27")
      (value "Zen15")
      (footprint "eagle-import:DO214AA")
      (libsource (lib "eagle-import") (part "SM6T"))
    )
    (comp (ref "D29")
      (value "SS12")
      (footprint "eagle-import:DO-214AC_SLIM")
      (libsource (lib "eagle-import") (part "DIODE-GEN-PURPOSE-1KV-1A(DO-214AC)DO-214AC/1206"))
    )
    (comp (ref "D30")
      (value "SS12")
      (footprint "eagle-import:DO-214AC_SLIM")
      (libsource (lib "eagle-import") (part "DIODE-GEN-PURPOSE-1KV-1A(DO-214AC)DO-214AC/1206"))
    )
    (comp (ref "D31")
      (value "Zen11")
      (footprint "eagle-import:SOD-123_MINI-SMA")
      (libsource (lib "eagle-import") (part "CGRM400-G1"))
    )
    (comp (ref "FID7")
      (value "FIDUCIAL")
      (footprint "eagle-import:FIDUCIAL_1MM")
      (libsource (lib "eagle-import") (part "FIDUCIAL"))
    )
    (comp (ref "FID8")
      (value "FIDUCIAL")
      (footprint "eagle-import:FIDUCIAL_1MM")
      (libsource (lib "eagle-import") (part "FIDUCIAL"))
    )
    (comp (ref "FID9")
      (value "FIDUCIAL")
      (footprint "eagle-import:FIDUCIAL_1MM")
      (libsource (lib "eagle-import") (part "FIDUCIAL"))
    )
    (comp (ref "FID10")
      (value "FIDUCIAL")
      (footprint "eagle-import:FIDUCIAL_1MM")
      (libsource (lib "eagle-import") (part "FIDUCIAL"))
    )
    (comp (ref "IC10")
      (value "4028")
      (footprint "eagle-import:SO16")
      (libsource (lib "eagle-import") (part "4028D"))
    )
    (comp (ref "IC11")
      (value "317TO202H_NOHOLE")
      (footprint "eagle-import:TO220H_NOHOLE")
      (libsource (lib "eagle-import") (part "317TO202H_NOHOLE"))
    )
    (comp (ref "IC12")
      (value "ULN2004")
      (footprint "eagle-import:SO16")
      (libsource (lib "eagle-import") (part "ULN2004AD"))
    )
    (comp (ref "IC13")
      (value "LM339")
      (footprint "eagle-import:SO14")
      (libsource (lib "eagle-import") (part "LM339D"))
    )
    (comp (ref "IC14")
      (value "78L06")
      (footprint "eagle-import:SOT89_ROUND")
      (libsource (lib "eagle-import") (part "78LXXSOT89_ROUND"))
    )
    (comp (ref "IC15")
      (value "555")
      (footprint "eagle-import:SO08")
      (libsource (lib "eagle-import") (part "555DNE"))
    )
    (comp (ref "IC16")
      (value "4538")
      (footprint "eagle-import:SO16")
      (libsource (lib "eagle-import") (part "4538D"))
    )
    (comp (ref "IC17")
      (value "78L10")
      (footprint "eagle-import:SOT89_ROUND")
      (libsource (lib "eagle-import") (part "78LXXSOT89_ROUND"))
    )
    (comp (ref "IC18")
      (value "LM2904")
      (footprint "eagle-import:SO08")
      (libsource (lib "eagle-import") (part "LM358D"))
    )
    (comp (ref "JP6")
      (value "JP2EJP2_SMALLPADS")
      (footprint "eagle-import:JP2_SMALLPADS")
      (libsource (lib "eagle-import") (part "JP2EJP2_SMALLPADS"))
    )
    (comp (ref "JP7")
      (value "JP2E_ORIG")
      (footprint "eagle-import:JP2_ORIG_SMALLPADS")
      (libsource (lib "eagle-import") (part "JP2E_ORIG"))
    )
    (comp (ref "JP8")
      (value "JP2EJP2_SMALLPADS")
      (footprint "eagle-import:JP2_SMALLPADS")
      (libsource (lib "eagle-import") (part "JP2EJP2_SMALLPADS"))
    )
    (comp (ref "JP9")
      (value "JP2EJP2_SMALLPADS")
      (footprint "eagle-import:JP2_SMALLPADS")
      (libsource (lib "eagle-import") (part "JP2EJP2_SMALLPADS"))
    )
    (comp (ref "JP10")
      (value "JP2EJP2_SMALLPADS")
      (footprint "eagle-import:JP2_SMALLPADS")
      (libsource (lib "eagle-import") (part "JP2EJP2_SMALLPADS"))
    )
    (comp (ref "LED7")
      (value "LEDLD260")
      (footprint "eagle-import:LD260")
      (libsource (lib "eagle-import") (part "LEDLD260"))
    )
    (comp (ref "LED8")
      (value "LEDLD260")
      (footprint "eagle-import:LD260")
      (libsource (lib "eagle-import") (part "LEDLD260"))
    )
    (comp (ref "LED9")
      (value "LEDLD260")
      (footprint "eagle-import:LD260")
      (libsource (lib "eagle-import") (part "LEDLD260"))
    )
    (comp (ref "LED10")
      (value "LEDLD260")
      (footprint "eagle-import:LD260")
      (libsource (lib "eagle-import") (part "LEDLD260"))
    )
    (comp (ref "LED11")
      (value "LEDLD260")
      (footprint "eagle-import:LD260")
      (libsource (lib "eagle-import") (part "LEDLD260"))
    )
    (comp (ref "LED12")
      (value "LEDLD260")
      (footprint "eagle-import:LD260")
      (libsource (lib "eagle-import") (part "LEDLD260"))
    )
    (comp (ref "Q14")
      (value "BA")
      (footprint "eagle-import:SOT89")
      (libsource (lib "eagle-import") (part "PNP-TRANSISTOR_SOT89"))
    )
    (comp (ref "Q15")
      (value "BA.")
      (footprint "eagle-import:SOT89")
      (libsource (lib "eagle-import") (part "PNP-TRANSISTOR_SOT89"))
    )
    (comp (ref "Q16")
      (value "BA.")
      (footprint "eagle-import:SOT89")
      (libsource (lib "eagle-import") (part "PNP-TRANSISTOR_SOT89"))
    )
    (comp (ref "Q17")
      (value "BA")
      (footprint "eagle-import:SOT89")
      (libsource (lib "eagle-import") (part "PNP-TRANSISTOR_SOT89"))
    )
    (comp (ref "Q18")
      (value "MY")
      (footprint "eagle-import:SOT89")
      (libsource (lib "eagle-import") (part "NPN-TRANSISTOR_SOT89"))
    )
    (comp (ref "Q19")
      (value "J1")
      (footprint "eagle-import:SOT-23")
      (fields (field (name "MPN") "BSS138W-7-F"))
      (libsource (lib "eagle-import") (part "SMD-MOSFET-N-CH-50V-200MA-BSS138W-7-F(SOT-23)"))
    )
    (comp (ref "Q20")
      (value "J1")
      (footprint "eagle-import:SOT-23")
      (fields (field (name "MPN") "BSS138W-7-F"))
      (libsource (lib "eagle-import") (part "SMD-MOSFET-N-CH-50V-200MA-BSS138W-7-F(SOT-23)"))
    )
    (comp (ref "Q21")
      (value "J1")
      (footprint "eagle-import:SOT-23")
      (fields (field (name "MPN") "BSS138W-7-F"))
      (libsource (lib "eagle-import") (part "SMD-MOSFET-N-CH-50V-200MA-BSS138W-7-F(SOT-23)"))
    )
    (comp (ref "Q22")
      (value "BA")
      (footprint "eagle-import:SOT89")
      (libsource (lib "eagle-import") (part "PNP-TRANSISTOR_SOT89"))
    )
    (comp (ref "Q23")
      (value "J1")
      (footprint "eagle-import:SOT-23")
      (fields (field (name "MPN") "BSS138W-7-F"))
      (libsource (lib "eagle-import") (part "SMD-MOSFET-N-CH-50V-200MA-BSS138W-7-F(SOT-23)"))
    )
    (comp (ref "R67")
      (value "47")
      (footprint "eagle-import:V235_17_1MM")
      (libsource (lib "eagle-import") (part "R-EU_V235/17_1MM"))
    )
    (comp (ref "R68")
      (value "13")
      (footprint "eagle-import:R1206")
      (fields (field (name "MPN") "RC1206JR-0713RL"))
      (libsource (lib "eagle-import") (part "SMD-RES-13R-5%-1/4W(1206)"))
    )
    (comp (ref "R69")
      (value "47")
      (footprint "eagle-import:V235_17_1MM")
      (libsource (lib "eagle-import") (part "R-EU_V235/17_1MM"))
    )
    (comp (ref "R70")
      (value "104")
      (footprint "eagle-import:R0805")
      (fields (field (name "MPN") "RC0805FR-0710KL"))
      (libsource (lib "eagle-import") (part "SMD-RES-10K-1%-1/8W(0805)"))
    )
    (comp (ref "R71")
      (value "104")
      (footprint "eagle-import:R0805")
      (fields (field (name "MPN") "RC0805FR-0710KL"))
      (libsource (lib "eagle-import") (part "SMD-RES-10K-1%-1/8W(0805)"))
    )
    (comp (ref "R72")
      (value "104")
      (footprint "eagle-import:R0805")
      (fields (field (name "MPN") "RC0805FR-0710KL"))
      (libsource (lib "eagle-import") (part "SMD-RES-10K-1%-1/8W(0805)"))
    )
    (comp (ref "R73")
      (value "4701")
      (footprint "eagle-import:R0805")
      (fields (field (name "MPN") "RC0805JR-074K7L"))
      (libsource (lib "eagle-import") (part "SMD-RES-4.7K-5%-1/8W(0805)"))
    )
    (comp (ref "R74")
      (value "1002")
      (footprint "eagle-import:R0805")
      (fields (field (name "MPN") "RC0805FR-0710KL"))
      (libsource (lib "eagle-import") (part "SMD-RES-10K-1%-1/8W(0805)"))
    )
    (comp (ref "R75")
      (value "1002")
      (footprint "eagle-import:R0805")
      (fields (field (name "MPN") "RC0805FR-0710KL"))
      (libsource (lib "eagle-import") (part "SMD-RES-10K-1%-1/8W(0805)"))
    )
    (comp (ref "R76")
      (value "1502")
      (footprint "eagle-import:R0805")
      (fields (field (name "MPN") "RC0805FR-0710KL"))
      (libsource (lib "eagle-import") (part "SMD-RES-10K-1%-1/8W(0805)"))
    )
    (comp (ref "R77")
      (value "104")
      (footprint "eagle-import:R0805")
      (fields (field (name "MPN") "RC0805FR-0710KL"))
      (libsource (lib "eagle-import") (part "SMD-RES-10K-1%-1/8W(0805)"))
    )
    (comp (ref "R78")
      (value "104")
      (footprint "eagle-import:R0805")
      (fields (field (name "MPN") "RC0805FR-0710KL"))
      (libsource (lib "eagle-import") (part "SMD-RES-10K-1%-1/8W(0805)"))
    )
    (comp (ref "R79")
      (value "1502")
      (footprint "eagle-import:R0805")
      (fields (field (name "MPN") "RC0805FR-0710KL"))
      (libsource (lib "eagle-import") (part "SMD-RES-10K-1%-1/8W(0805)"))
    )
    (comp (ref "R80")
      (value "1002")
      (footprint "eagle-import:R0805")
      (fields (field (name "MPN") "RC0805FR-0710KL"))
      (libsource (lib "eagle-import") (part "SMD-RES-10K-1%-1/8W(0805)"))
    )
    (comp (ref "R81")
      (value "2201")
      (footprint "eagle-import:R0805")
      (fields (field (name "MPN") "RC0805JR-072K2L"))
      (libsource (lib "eagle-import") (part "SMD-RES-2.2K-5%-1/8W(0805)"))
    )
    (comp (ref "R82")
      (value "1002")
      (footprint "eagle-import:R0805")
      (fields (field (name "MPN") "RC0805FR-0710KL"))
      (libsource (lib "eagle-import") (part "SMD-RES-10K-1%-1/8W(0805)"))
    )
    (comp (ref "R83")
      (value "4701")
      (footprint "eagle-import:R0805")
      (fields (field (name "MPN") "RC0805JR-074K7L"))
      (libsource (lib "eagle-import") (part "SMD-RES-4.7K-5%-1/8W(0805)"))
    )
    (comp (ref "R84")
      (value "2702")
      (footprint "eagle-import:R0805")
      (fields (field (name "MPN") "RC0805JR-074K7L"))
      (libsource (lib "eagle-import") (part "SMD-RES-4.7K-5%-1/8W(0805)"))
    )
    (comp (ref "R85")
      (value "102")
      (footprint "eagle-import:R0805")
      (fields (field (name "MPN") "RC0805JR-071KL"))
      (libsource (lib "eagle-import") (part "SMD-RES-1K-5%-1/8W(0805)"))
    )
    (comp (ref "R87")
      (value "102")
      (footprint "eagle-import:R0805")
      (fields (field (name "MPN") "RC0805JR-07220RL"))
      (libsource (lib "eagle-import") (part "SMD-RES-220R-5%-1/8W(0805)"))
    )
    (comp (ref "R90")
      (value "102")
      (footprint "eagle-import:R0805")
      (fields (field (name "MPN") "RC0805JR-071KL"))
      (libsource (lib "eagle-import") (part "SMD-RES-1K-5%-1/8W(0805)"))
    )
    (comp (ref "R91")
      (value "13")
      (footprint "eagle-import:R1206")
      (fields (field (name "MPN") "RC1206JR-0713RL"))
      (libsource (lib "eagle-import") (part "SMD-RES-13R-5%-1/4W(1206)"))
    )
    (comp (ref "R92")
      (value "13")
      (footprint "eagle-import:R1206")
      (fields (field (name "MPN") "RC1206JR-0713RL"))
      (libsource (lib "eagle-import") (part "SMD-RES-13R-5%-1/4W(1206)"))
    )
    (comp (ref "R93")
      (value "2702")
      (footprint "eagle-import:R0805")
      (fields (field (name "MPN") "RC0805JR-074K7L"))
      (libsource (lib "eagle-import") (part "SMD-RES-4.7K-5%-1/8W(0805)"))
    )
    (comp (ref "R94")
      (value "4701")
      (footprint "eagle-import:R0805")
      (fields (field (name "MPN") "RC0805JR-074K7L"))
      (libsource (lib "eagle-import") (part "SMD-RES-4.7K-5%-1/8W(0805)"))
    )
    (comp (ref "R95")
      (value "100")
      (footprint "eagle-import:R0805")
      (fields (field (name "MPN") "RC0805JR-072K2L"))
      (libsource (lib "eagle-import") (part "SMD-RES-2.2K-5%-1/8W(0805)"))
    )
    (comp (ref "R96")
      (value "104")
      (footprint "eagle-import:R0805")
      (fields (field (name "MPN") "RC0805FR-0710KL"))
      (libsource (lib "eagle-import") (part "SMD-RES-10K-1%-1/8W(0805)"))
    )
    (comp (ref "R97")
      (value "104")
      (footprint "eagle-import:R0805")
      (fields (field (name "MPN") "RC0805FR-0710KL"))
      (libsource (lib "eagle-import") (part "SMD-RES-10K-1%-1/8W(0805)"))
    )
    (comp (ref "R99")
      (value "2702")
      (footprint "eagle-import:R0805")
      (fields (field (name "MPN") "RC0805FR-0710KL"))
      (libsource (lib "eagle-import") (part "SMD-RES-10K-1%-1/8W(0805)"))
    )
    (comp (ref "R100")
      (value "47")
      (footprint "eagle-import:V235_17_1MM")
      (libsource (lib "eagle-import") (part "R-EU_V235/17_1MM"))
    )
    (comp (ref "R118")
      (value "47")
      (footprint "eagle-import:V235_17_1MM")
      (libsource (lib "eagle-import") (part "R-EU_V235/17_1MM"))
    )
    (comp (ref "R139")
      (value "2702")
      (footprint "eagle-import:R0805")
      (fields (field (name "MPN") "RC0805JR-074K7L"))
      (libsource (lib "eagle-import") (part "SMD-RES-4.7K-5%-1/8W(0805)"))
    )
    (comp (ref "R147")
      (value "2201")
      (footprint "eagle-import:R0805")
      (fields (field (name "MPN") "RC0805JR-072K2L"))
      (libsource (lib "eagle-import") (part "SMD-RES-2.2K-5%-1/8W(0805)"))
    )
    (comp (ref "R148")
      (value "1002")
      (footprint "eagle-import:R0805")
      (fields (field (name "MPN") "RC0805JR-074K7L"))
      (libsource (lib "eagle-import") (part "SMD-RES-4.7K-5%-1/8W(0805)"))
    )
    (comp (ref "R149")
      (value "1002")
      (footprint "eagle-import:R0805")
      (fields (field (name "MPN") "RC0805FR-0710KL"))
      (libsource (lib "eagle-import") (part "SMD-RES-10K-1%-1/8W(0805)"))
    )
    (comp (ref "R150")
      (value "102")
      (footprint "eagle-import:R0805")
      (fields (field (name "MPN") "RC0805JR-071KL"))
      (libsource (lib "eagle-import") (part "SMD-RES-1K-5%-1/8W(0805)"))
    )
    (comp (ref "R151")
      (value "2702")
      (footprint "eagle-import:R0805")
      (fields (field (name "MPN") "RC0805JR-074K7L"))
      (libsource (lib "eagle-import") (part "SMD-RES-4.7K-5%-1/8W(0805)"))
    )
    (comp (ref "R152")
      (value "1002")
      (footprint "eagle-import:R0805")
      (fields (field (name "MPN") "RC0805JR-071KL"))
      (libsource (lib "eagle-import") (part "SMD-RES-1K-5%-1/8W(0805)"))
    )
    (comp (ref "R153")
      (value "1002")
      (footprint "eagle-import:R0805")
      (fields (field (name "MPN") "RC0805JR-071KL"))
      (libsource (lib "eagle-import") (part "SMD-RES-1K-5%-1/8W(0805)"))
    )
    (comp (ref "R154")
      (value "R_user")
      (footprint "eagle-import:R0805")
      (libsource (lib "eagle-import") (part "R-EU_R0805"))
    )
    (comp (ref "R155")
      (value "104")
      (footprint "eagle-import:R0805")
      (fields (field (name "MPN") "RC0805FR-0710KL"))
      (libsource (lib "eagle-import") (part "SMD-RES-10K-1%-1/8W(0805)"))
    )
    (comp (ref "R156")
      (value "104")
      (footprint "eagle-import:R0805")
      (fields (field (name "MPN") "RC0805FR-0710KL"))
      (libsource (lib "eagle-import") (part "SMD-RES-10K-1%-1/8W(0805)"))
    )
    (comp (ref "R157")
      (value "104")
      (footprint "eagle-import:R0805")
      (fields (field (name "MPN") "RC0805FR-0710KL"))
      (libsource (lib "eagle-import") (part "SMD-RES-10K-1%-1/8W(0805)"))
    )
    (comp (ref "R158")
      (value "13")
      (footprint "eagle-import:R1206")
      (fields (field (name "MPN") "RC1206JR-0713RL"))
      (libsource (lib "eagle-import") (part "SMD-RES-13R-5%-1/4W(1206)"))
    )
    (comp (ref "R159")
      (value "2201")
      (footprint "eagle-import:R0805")
      (fields (field (name "MPN") "RC0805JR-071KL"))
      (libsource (lib "eagle-import") (part "SMD-RES-1K-5%-1/8W(0805)"))
    )
    (comp (ref "R160")
      (value "100")
      (footprint "eagle-import:R0805")
      (fields (field (name "MPN") "RC0805JR-07220RL"))
      (libsource (lib "eagle-import") (part "SMD-RES-220R-5%-1/8W(0805)"))
    )
    (comp (ref "R161")
      (value "13")
      (footprint "eagle-import:R1206")
      (fields (field (name "MPN") "RC1206JR-0713RL"))
      (libsource (lib "eagle-import") (part "SMD-RES-13R-5%-1/4W(1206)"))
    )
    (comp (ref "R162")
      (value "4701")
      (footprint "eagle-import:R0805")
      (fields (field (name "MPN") "RC0805JR-074K7L"))
      (libsource (lib "eagle-import") (part "SMD-RES-4.7K-5%-1/8W(0805)"))
    )
    (comp (ref "R163")
      (value "104")
      (footprint "eagle-import:R0805")
      (fields (field (name "MPN") "RC0805JR-074K7L"))
      (libsource (lib "eagle-import") (part "SMD-RES-4.7K-5%-1/8W(0805)"))
    )
    (comp (ref "R164")
      (value "100")
      (footprint "eagle-import:R0805")
      (fields (field (name "MPN") "RC0805JR-072K2L"))
      (libsource (lib "eagle-import") (part "SMD-RES-2.2K-5%-1/8W(0805)"))
    )
    (comp (ref "R165")
      (value "100")
      (footprint "eagle-import:R0805")
      (fields (field (name "MPN") "RC0805JR-072K2L"))
      (libsource (lib "eagle-import") (part "SMD-RES-2.2K-5%-1/8W(0805)"))
    )
    (comp (ref "SJMP2")
      (value "SJ")
      (footprint "eagle-import:SJ")
      (libsource (lib "eagle-import") (part "SJ"))
    )
    (comp (ref "START2")
      (value "TPSB2.0")
      (footprint "eagle-import:B2.0")
      (libsource (lib "eagle-import") (part "TPSB2.0"))
    )
    (comp (ref "TP47")
      (value "TPSB2.0")
      (footprint "eagle-import:B2.0")
      (libsource (lib "eagle-import") (part "TPSB2.0"))
    )
    (comp (ref "TP48")
      (value "TPSB2.0")
      (footprint "eagle-import:B2.0")
      (libsource (lib "eagle-import") (part "TPSB2.0"))
    )
    (comp (ref "TP49")
      (value "TPSB2.0")
      (footprint "eagle-import:B2.0")
      (libsource (lib "eagle-import") (part "TPSB2.0"))
    )
    (comp (ref "TP50")
      (value "TPSB2.0")
      (footprint "eagle-import:B2.0")
      (libsource (lib "eagle-import") (part "TPSB2.0"))
    )
    (comp (ref "TP51")
      (value "TPSB2.0")
      (footprint "eagle-import:B2.0")
      (libsource (lib "eagle-import") (part "TPSB2.0"))
    )
    (comp (ref "TP52")
      (value "TPSB2.0")
      (footprint "eagle-import:B2.0")
      (libsource (lib "eagle-import") (part "TPSB2.0"))
    )
    (comp (ref "TP53")
      (value "TPSB2.0")
      (footprint "eagle-import:B2.0")
      (libsource (lib "eagle-import") (part "TPSB2.0"))
    )
    (comp (ref "TP54")
      (value "TPSB2.0")
      (footprint "eagle-import:B2.0")
      (libsource (lib "eagle-import") (part "TPSB2.0"))
    )
    (comp (ref "TP55")
      (value "TPSB2.0")
      (footprint "eagle-import:B2.0")
      (libsource (lib "eagle-import") (part "TPSB2.0"))
    )
    (comp (ref "TP56")
      (value "TPSB2.0")
      (footprint "eagle-import:B2.0")
      (libsource (lib "eagle-import") (part "TPSB2.0"))
    )
    (comp (ref "TP57")
      (value "TPSB2.0")
      (footprint "eagle-import:B2.0")
      (libsource (lib "eagle-import") (part "TPSB2.0"))
    )
    (comp (ref "TP58")
      (value "TPSB2.0")
      (footprint "eagle-import:B2.0")
      (libsource (lib "eagle-import") (part "TPSB2.0"))
    )
    (comp (ref "TP59")
      (value "TPSB2.0")
      (footprint "eagle-import:B2.0")
      (libsource (lib "eagle-import") (part "TPSB2.0"))
    )
    (comp (ref "TP60")
      (value "TPSB2.0")
      (footprint "eagle-import:B2.0")
      (libsource (lib "eagle-import") (part "TPSB2.0"))
    )
    (comp (ref "TP61")
      (value "TPSB2.0")
      (footprint "eagle-import:B2.0")
      (libsource (lib "eagle-import") (part "TPSB2.0"))
    )
    (comp (ref "TP62")
      (value "TPSB2.0")
      (footprint "eagle-import:B2.0")
      (libsource (lib "eagle-import") (part "TPSB2.0"))
    )
    (comp (ref "TP63")
      (value "TPSB2.0")
      (footprint "eagle-import:B2.0")
      (libsource (lib "eagle-import") (part "TPSB2.0"))
    )
    (comp (ref "TP64")
      (value "TPSB2.0")
      (footprint "eagle-import:B2.0")
      (libsource (lib "eagle-import") (part "TPSB2.0"))
    )
    (comp (ref "TP65")
      (value "TPSB1,27")
      (footprint "eagle-import:B1,27")
      (libsource (lib "eagle-import") (part "TPSB1,27"))
    )
    (comp (ref "TP66")
      (value "TPSB2.0")
      (footprint "eagle-import:B2.0")
      (libsource (lib "eagle-import") (part "TPSB2.0"))
    )
    (comp (ref "TP67")
      (value "TPSB2.0")
      (footprint "eagle-import:B2.0")
      (libsource (lib "eagle-import") (part "TPSB2.0"))
    )
    (comp (ref "TP68")
      (value "TPSB2.0")
      (footprint "eagle-import:B2.0")
      (libsource (lib "eagle-import") (part "TPSB2.0"))
    )
    (comp (ref "TP69")
      (value "TPSB2.0")
      (footprint "eagle-import:B2.0")
      (libsource (lib "eagle-import") (part "TPSB2.0"))
    )
    (comp (ref "X4")
      (value "CON_BMWV2")
      (footprint "eagle-import:24-PIN_V2")
      (libsource (lib "eagle-import") (part "CON_BMWV2"))
    )
    (comp (ref "X5")
      (value "22-23-2051")
      (footprint "eagle-import:22-23-2051")
      (fields (field (name "MF") "MOLEX"))
      (libsource (lib "eagle-import") (part "22-23-2051"))
    )
    (comp (ref "X6")
      (value "22-23-2021")
      (footprint "eagle-import:22-23-2021")
      (fields (field (name "MF") "MOLEX"))
      (libsource (lib "eagle-import") (part "22-23-2021"))
    )
  )
  (nets
    (net (code "1") (name "+10V") (class "Default")
      (node (ref "10V") (pin "TP") (pinfunction "PP_TP") (pintype "input"))
      (node (ref "10V1") (pin "TP") (pinfunction "PP_TP") (pintype "input"))
      (node (ref "10V10") (pin "TP") (pinfunction "PP_TP") (pintype "input"))
      (node (ref "10V11") (pin "TP") (pinfunction "PP_TP") (pintype "input"))
      (node (ref "10V2") (pin "TP") (pinfunction "PP_TP") (pintype "input"))
      (node (ref "10V3") (pin "TP") (pinfunction "PP_TP") (pintype "input"))
      (node (ref "10V4") (pin "TP") (pinfunction "PP_TP") (pintype "input"))
      (node (ref "10V5") (pin "TP") (pinfunction "PP_TP") (pintype "input"))
      (node (ref "10V6") (pin "TP") (pinfunction "PP_TP") (pintype "input"))
      (node (ref "10V7") (pin "TP") (pinfunction "PP_TP") (pintype "input"))
      (node (ref "10V8") (pin "TP") (pinfunction "PP_TP") (pintype "input"))
      (node (ref "10V9") (pin "TP") (pinfunction "PP_TP") (pintype "input"))
      (node (ref "C102") (pin "1") (pinfunction "1_1") (pintype "passive"))
      (node (ref "C116") (pin "1") (pinfunction "1_1") (pintype "passive"))
      (node (ref "C128") (pin "1") (pinfunction "1_1") (pintype "passive"))
      (node (ref "C140") (pin "1") (pinfunction "1_1") (pintype "passive"))
      (node (ref "C22") (pin "1") (pinfunction "1_1") (pintype "passive"))
      (node (ref "C34") (pin "1") (pinfunction "1_1") (pintype "passive"))
      (node (ref "C46") (pin "1") (pinfunction "1_1") (pintype "passive"))
      (node (ref "C58") (pin "1") (pinfunction "1_1") (pintype "passive"))
      (node (ref "C70") (pin "1") (pinfunction "1_1") (pintype "passive"))
      (node (ref "C82") (pin "1") (pinfunction "1_1") (pintype "passive"))
      (node (ref "C9") (pin "1") (pinfunction "1_1") (pintype "passive"))
      (node (ref "C94") (pin "1") (pinfunction "1_1") (pintype "passive"))
      (node (ref "IC104") (pin "1") (pinfunction "OUT_1") (pintype "passive"))
      (node (ref "IC110") (pin "4") (pinfunction "R_4") (pintype "input"))
      (node (ref "IC110") (pin "8") (pinfunction "V+_8") (pintype "power_in"))
      (node (ref "IC111") (pin "13") (pinfunction "CD_13") (pintype "input"))
      (node (ref "IC111") (pin "16") (pinfunction "VDD_16") (pintype "power_in"))
      (node (ref "IC111") (pin "3") (pinfunction "CD_3") (pintype "input"))
      (node (ref "IC111") (pin "5") (pinfunction "B_5") (pintype "input"))
      (node (ref "IC15") (pin "4") (pinfunction "R_4") (pintype "input"))
      (node (ref "IC15") (pin "8") (pinfunction "V+_8") (pintype "power_in"))
      (node (ref "IC16") (pin "13") (pinfunction "CD_13") (pintype "input"))
      (node (ref "IC16") (pin "16") (pinfunction "VDD_16") (pintype "power_in"))
      (node (ref "IC16") (pin "3") (pinfunction "CD_3") (pintype "input"))
      (node (ref "IC16") (pin "5") (pinfunction "B_5") (pintype "input"))
      (node (ref "IC17") (pin "1") (pinfunction "OUT_1") (pintype "passive"))
      (node (ref "IC24") (pin "4") (pinfunction "R_4") (pintype "input"))
      (node (ref "IC24") (pin "8") (pinfunction "V+_8") (pintype "power_in"))
      (node (ref "IC25") (pin "13") (pinfunction "CD_13") (pintype "input"))
      (node (ref "IC25") (pin "16") (pinfunction "VDD_16") (pintype "power_in"))
      (node (ref "IC25") (pin "3") (pinfunction "CD_3") (pintype "input"))
      (node (ref "IC25") (pin "5") (pinfunction "B_5") (pintype "input"))
      (node (ref "IC26") (pin "1") (pinfunction "OUT_1") (pintype "passive"))
      (node (ref "IC33") (pin "4") (pinfunction "R_4") (pintype "input"))
      (node (ref "IC33") (pin "8") (pinfunction "V+_8") (pintype "power_in"))
      (node (ref "IC34") (pin "13") (pinfunction "CD_13") (pintype "input"))
      (node (ref "IC34") (pin "16") (pinfunction "VDD_16") (pintype "power_in"))
      (node (ref "IC34") (pin "3") (pinfunction "CD_3") (pintype "input"))
      (node (ref "IC34") (pin "5") (pinfunction "B_5") (pintype "input"))
      (node (ref "IC35") (pin "1") (pinfunction "OUT_1") (pintype "passive"))
      (node (ref "IC42") (pin "4") (pinfunction "R_4") (pintype "input"))
      (node (ref "IC42") (pin "8") (pinfunction "V+_8") (pintype "power_in"))
      (node (ref "IC43") (pin "13") (pinfunction "CD_13") (pintype "input"))
      (node (ref "IC43") (pin "16") (pinfunction "VDD_16") (pintype "power_in"))
      (node (ref "IC43") (pin "3") (pinfunction "CD_3") (pintype "input"))
      (node (ref "IC43") (pin "5") (pinfunction "B_5") (pintype "input"))
      (node (ref "IC44") (pin "1") (pinfunction "OUT_1") (pintype "passive"))
      (node (ref "IC51") (pin "4") (pinfunction "R_4") (pintype "input"))
      (node (ref "IC51") (pin "8") (pinfunction "V+_8") (pintype "power_in"))
      (node (ref "IC52") (pin "13") (pinfunction "CD_13") (pintype "input"))
      (node (ref "IC52") (pin "16") (pinfunction "VDD_16") (pintype "power_in"))
      (node (ref "IC52") (pin "3") (pinfunction "CD_3") (pintype "input"))
      (node (ref "IC52") (pin "5") (pinfunction "B_5") (pintype "input"))
      (node (ref "IC53") (pin "1") (pinfunction "OUT_1") (pintype "passive"))
      (node (ref "IC6") (pin "4") (pinfunction "R_4") (pintype "input"))
      (node (ref "IC6") (pin "8") (pinfunction "V+_8") (pintype "power_in"))
      (node (ref "IC60") (pin "4") (pinfunction "R_4") (pintype "input"))
      (node (ref "IC60") (pin "8") (pinfunction "V+_8") (pintype "power_in"))
      (node (ref "IC61") (pin "13") (pinfunction "CD_13") (pintype "input"))
      (node (ref "IC61") (pin "16") (pinfunction "VDD_16") (pintype "power_in"))
      (node (ref "IC61") (pin "3") (pinfunction "CD_3") (pintype "input"))
      (node (ref "IC61") (pin "5") (pinfunction "B_5") (pintype "input"))
      (node (ref "IC62") (pin "1") (pinfunction "OUT_1") (pintype "passive"))
      (node (ref "IC69") (pin "4") (pinfunction "R_4") (pintype "input"))
      (node (ref "IC69") (pin "8") (pinfunction "V+_8") (pintype "power_in"))
      (node (ref "IC7") (pin "13") (pinfunction "CD_13") (pintype "input"))
      (node (ref "IC7") (pin "16") (pinfunction "VDD_16") (pintype "power_in"))
      (node (ref "IC7") (pin "3") (pinfunction "CD_3") (pintype "input"))
      (node (ref "IC7") (pin "5") (pinfunction "B_5") (pintype "input"))
      (node (ref "IC70") (pin "13") (pinfunction "CD_13") (pintype "input"))
      (node (ref "IC70") (pin "16") (pinfunction "VDD_16") (pintype "power_in"))
      (node (ref "IC70") (pin "3") (pinfunction "CD_3") (pintype "input"))
      (node (ref "IC70") (pin "5") (pinfunction "B_5") (pintype "input"))
      (node (ref "IC71") (pin "1") (pinfunction "OUT_1") (pintype "passive"))
      (node (ref "IC78") (pin "4") (pinfunction "R_4") (pintype "input"))
      (node (ref "IC78") (pin "8") (pinfunction "V+_8") (pintype "power_in"))
      (node (ref "IC79") (pin "13") (pinfunction "CD_13") (pintype "input"))
      (node (ref "IC79") (pin "16") (pinfunction "VDD_16") (pintype "power_in"))
      (node (ref "IC79") (pin "3") (pinfunction "CD_3") (pintype "input"))
      (node (ref "IC79") (pin "5") (pinfunction "B_5") (pintype "input"))
      (node (ref "IC8") (pin "1") (pinfunction "OUT_1") (pintype "passive"))
      (node (ref "IC80") (pin "1") (pinfunction "OUT_1") (pintype "passive"))
      (node (ref "IC87") (pin "4") (pinfunction "R_4") (pintype "input"))
      (node (ref "IC87") (pin "8") (pinfunction "V+_8") (pintype "power_in"))
      (node (ref "IC88") (pin "13") (pinfunction "CD_13") (pintype "input"))
      (node (ref "IC88") (pin "16") (pinfunction "VDD_16") (pintype "power_in"))
      (node (ref "IC88") (pin "3") (pinfunction "CD_3") (pintype "input"))
      (node (ref "IC88") (pin "5") (pinfunction "B_5") (pintype "input"))
      (node (ref "IC89") (pin "1") (pinfunction "OUT_1") (pintype "passive"))
      (node (ref "IC96") (pin "4") (pinfunction "R_4") (pintype "input"))
      (node (ref "IC96") (pin "8") (pinfunction "V+_8") (pintype "power_in"))
      (node (ref "IC97") (pin "13") (pinfunction "CD_13") (pintype "input"))
      (node (ref "IC97") (pin "16") (pinfunction "VDD_16") (pintype "power_in"))
      (node (ref "IC97") (pin "3") (pinfunction "CD_3") (pintype "input"))
      (node (ref "IC97") (pin "5") (pinfunction "B_5") (pintype "input"))
      (node (ref "IC98") (pin "1") (pinfunction "OUT_1") (pintype "passive"))
      (node (ref "R10") (pin "2") (pinfunction "2_2") (pintype "passive"))
      (node (ref "R139") (pin "2") (pinfunction "2_2") (pintype "passive"))
      (node (ref "R145") (pin "2") (pinfunction "2_2") (pintype "passive"))
      (node (ref "R163") (pin "2") (pinfunction "2_2") (pintype "passive"))
      (node (ref "R201") (pin "2") (pinfunction "2_2") (pintype "passive"))
      (node (ref "R218") (pin "2") (pinfunction "2_2") (pintype "passive"))
      (node (ref "R256") (pin "2") (pinfunction "2_2") (pintype "passive"))
      (node (ref "R273") (pin "2") (pinfunction "2_2") (pintype "passive"))
      (node (ref "R311") (pin "2") (pinfunction "2_2") (pintype "passive"))
      (node (ref "R328") (pin "2") (pinfunction "2_2") (pintype "passive"))
      (node (ref "R338") (pin "2") (pinfunction "2_2") (pintype "passive"))
      (node (ref "R355") (pin "2") (pinfunction "2_2") (pintype "passive"))
      (node (ref "R389") (pin "2") (pinfunction "2_2") (pintype "passive"))
      (node (ref "R406") (pin "2") (pinfunction "2_2") (pintype "passive"))
      (node (ref "R440") (pin "2") (pinfunction "2_2") (pintype "passive"))
      (node (ref "R457") (pin "2") (pinfunction "2_2") (pintype "passive"))
      (node (ref "R47") (pin "2") (pinfunction "2_2") (pintype "passive"))
      (node (ref "R491") (pin "2") (pinfunction "2_2") (pintype "passive"))
      (node (ref "R508") (pin "2") (pinfunction "2_2") (pintype "passive"))
      (node (ref "R542") (pin "2") (pinfunction "2_2") (pintype "passive"))
      (node (ref "R559") (pin "2") (pinfunction "2_2") (pintype "passive"))
      (node (ref "R593") (pin "2") (pinfunction "2_2") (pintype "passive"))
      (node (ref "R610") (pin "2") (pinfunction "2_2") (pintype "passive"))
      (node (ref "R64") (pin "2") (pinfunction "2_2") (pintype "passive"))
    )
    (net (code "2") (name "+12V") (class "Default")
      (node (ref "10") (pin "1") (pinfunction "KL_1") (pintype "passive"))
      (node (ref "12") (pin "1") (pinfunction "KL_1") (pintype "passive"))
      (node (ref "14") (pin "1") (pinfunction "KL_1") (pintype "passive"))
      (node (ref "16") (pin "1") (pinfunction "KL_1") (pintype "passive"))
      (node (ref "18") (pin "1") (pinfunction "KL_1") (pintype "passive"))
      (node (ref "2") (pin "1") (pinfunction "KL_1") (pintype "passive"))
      (node (ref "20") (pin "1") (pinfunction "KL_1") (pintype "passive"))
      (node (ref "22") (pin "1") (pinfunction "KL_1") (pintype "passive"))
      (node (ref "24") (pin "1") (pinfunction "KL_1") (pintype "passive"))
      (node (ref "4") (pin "1") (pinfunction "KL_1") (pintype "passive"))
      (node (ref "6") (pin "1") (pinfunction "KL_1") (pintype "passive"))
      (node (ref "8") (pin "1") (pinfunction "KL_1") (pintype "passive"))
      (node (ref "C120") (pin "1") (pinfunction "1_1") (pintype "passive"))
      (node (ref "C13") (pin "1") (pinfunction "1_1") (pintype "passive"))
      (node (ref "C132") (pin "1") (pinfunction "1_1") (pintype "passive"))
      (node (ref "C144") (pin "1") (pinfunction "1_1") (pintype "passive"))
      (node (ref "C2") (pin "1") (pinfunction "1_1") (pintype "passive"))
      (node (ref "C26") (pin "1") (pinfunction "1_1") (pintype "passive"))
      (node (ref "C38") (pin "1") (pinfunction "1_1") (pintype "passive"))
      (node (ref "C50") (pin "1") (pinfunction "1_1") (pintype "passive"))
      (node (ref "C62") (pin "1") (pinfunction "1_1") (pintype "passive"))
      (node (ref "C74") (pin "1") (pinfunction "1_1") (pintype "passive"))
      (node (ref "C86") (pin "1") (pinfunction "1_1") (pintype "passive"))
      (node (ref "C98") (pin "1") (pinfunction "1_1") (pintype "passive"))
      (node (ref "D101") (pin "C") (pinfunction "C_C") (pintype "passive"))
      (node (ref "D114") (pin "C") (pinfunction "C_C") (pintype "passive"))
      (node (ref "D127") (pin "C") (pinfunction "C_C") (pintype "passive"))
      (node (ref "D13") (pin "C") (pinfunction "C_C") (pintype "passive"))
      (node (ref "D140") (pin "C") (pinfunction "C_C") (pintype "passive"))
      (node (ref "D153") (pin "C") (pinfunction "C_C") (pintype "passive"))
      (node (ref "D27") (pin "C") (pinfunction "C_C") (pintype "passive"))
      (node (ref "D41") (pin "C") (pinfunction "C_C") (pintype "passive"))
      (node (ref "D55") (pin "C") (pinfunction "C_C") (pintype "passive"))
      (node (ref "D69") (pin "C") (pinfunction "C_C") (pintype "passive"))
      (node (ref "D78") (pin "C") (pinfunction "C_C") (pintype "passive"))
      (node (ref "D91") (pin "C") (pinfunction "C_C") (pintype "passive"))
      (node (ref "IC1") (pin "16") (pinfunction "VDD_16") (pintype "power_in"))
      (node (ref "IC10") (pin "16") (pinfunction "VDD_16") (pintype "power_in"))
      (node (ref "IC102") (pin "3") (pinfunction "IN_3") (pintype "input"))
      (node (ref "IC104") (pin "3") (pinfunction "IN_3") (pintype "input"))
      (node (ref "IC105") (pin "16") (pinfunction "VDD_16") (pintype "power_in"))
      (node (ref "IC107") (pin "9") (pinfunction "CD+_9") (pintype "passive"))
      (node (ref "IC12") (pin "9") (pinfunction "CD+_9") (pintype "passive"))
      (node (ref "IC14") (pin "3") (pinfunction "IN_3") (pintype "input"))
      (node (ref "IC17") (pin "3") (pinfunction "IN_3") (pintype "input"))
      (node (ref "IC19") (pin "16") (pinfunction "VDD_16") (pintype "power_in"))
      (node (ref "IC21") (pin "9") (pinfunction "CD+_9") (pintype "passive"))
      (node (ref "IC23") (pin "3") (pinfunction "IN_3") (pintype "input"))
      (node (ref "IC26") (pin "3") (pinfunction "IN_3") (pintype "input"))
      (node (ref "IC28") (pin "16") (pinfunction "VDD_16") (pintype "power_in"))
      (node (ref "IC3") (pin "9") (pinfunction "CD+_9") (pintype "passive"))
      (node (ref "IC30") (pin "9") (pinfunction "CD+_9") (pintype "passive"))
      (node (ref "IC32") (pin "3") (pinfunction "IN_3") (pintype "input"))
      (node (ref "IC35") (pin "3") (pinfunction "IN_3") (pintype "input"))
      (node (ref "IC37") (pin "16") (pinfunction "VDD_16") (pintype "power_in"))
      (node (ref "IC39") (pin "9") (pinfunction "CD+_9") (pintype "passive"))
      (node (ref "IC41") (pin "3") (pinfunction "IN_3") (pintype "input"))
      (node (ref "IC44") (pin "3") (pinfunction "IN_3") (pintype "input"))
      (node (ref "IC46") (pin "16") (pinfunction "VDD_16") (pintype "power_in"))
      (node (ref "IC48") (pin "9") (pinfunction "CD+_9") (pintype "passive"))
      (node (ref "IC5") (pin "3") (pinfunction "IN_3") (pintype "input"))
      (node (ref "IC50") (pin "3") (pinfunction "IN_3") (pintype "input"))
      (node (ref "IC53") (pin "3") (pinfunction "IN_3") (pintype "input"))
      (node (ref "IC55") (pin "16") (pinfunction "VDD_16") (pintype "power_in"))
      (node (ref "IC57") (pin "9") (pinfunction "CD+_9") (pintype "passive"))
      (node (ref "IC59") (pin "3") (pinfunction "IN_3") (pintype "input"))
      (node (ref "IC62") (pin "3") (pinfunction "IN_3") (pintype "input"))
      (node (ref "IC64") (pin "16") (pinfunction "VDD_16") (pintype "power_in"))
      (node (ref "IC66") (pin "9") (pinfunction "CD+_9") (pintype "passive"))
      (node (ref "IC68") (pin "3") (pinfunction "IN_3") (pintype "input"))
      (node (ref "IC71") (pin "3") (pinfunction "IN_3") (pintype "input"))
      (node (ref "IC73") (pin "16") (pinfunction "VDD_16") (pintype "power_in"))
      (node (ref "IC75") (pin "9") (pinfunction "CD+_9") (pintype "passive"))
      (node (ref "IC77") (pin "3") (pinfunction "IN_3") (pintype "input"))
      (node (ref "IC8") (pin "3") (pinfunction "IN_3") (pintype "input"))
      (node (ref "IC80") (pin "3") (pinfunction "IN_3") (pintype "input"))
      (node (ref "IC82") (pin "16") (pinfunction "VDD_16") (pintype "power_in"))
      (node (ref "IC84") (pin "9") (pinfunction "CD+_9") (pintype "passive"))
      (node (ref "IC86") (pin "3") (pinfunction "IN_3") (pintype "input"))
      (node (ref "IC89") (pin "3") (pinfunction "IN_3") (pintype "input"))
      (node (ref "IC91") (pin "16") (pinfunction "VDD_16") (pintype "power_in"))
      (node (ref "IC93") (pin "9") (pinfunction "CD+_9") (pintype "passive"))
      (node (ref "IC95") (pin "3") (pinfunction "IN_3") (pintype "input"))
      (node (ref "IC98") (pin "3") (pinfunction "IN_3") (pintype "input"))
      (node (ref "JP1") (pin "2") (pinfunction "2_2") (pintype "passive"))
      (node (ref "JP101") (pin "2") (pinfunction "2_2") (pintype "passive"))
      (node (ref "JP11") (pin "2") (pinfunction "2_2") (pintype "passive"))
      (node (ref "JP16") (pin "2") (pinfunction "2_2") (pintype "passive"))
      (node (ref "JP21") (pin "2") (pinfunction "2_2") (pintype "passive"))
      (node (ref "JP26") (pin "2") (pinfunction "2_2") (pintype "passive"))
      (node (ref "JP31") (pin "2") (pinfunction "2_2") (pintype "passive"))
      (node (ref "JP36") (pin "2") (pinfunction "2_2") (pintype "passive"))
      (node (ref "JP41") (pin "2") (pinfunction "2_2") (pintype "passive"))
      (node (ref "JP46") (pin "2") (pinfunction "2_2") (pintype "passive"))
      (node (ref "JP51") (pin "2") (pinfunction "2_2") (pintype "passive"))
      (node (ref "JP6") (pin "2") (pinfunction "2_2") (pintype "passive"))
      (node (ref "R102") (pin "1") (pinfunction "1_1") (pintype "passive"))
      (node (ref "R106") (pin "1") (pinfunction "1_1") (pintype "passive"))
      (node (ref "R109") (pin "2") (pinfunction "2_2") (pintype "passive"))
      (node (ref "R110") (pin "2") (pinfunction "2_2") (pintype "passive"))
      (node (ref "R111") (pin "2") (pinfunction "2_2") (pintype "passive"))
      (node (ref "R12") (pin "2") (pinfunction "2_2") (pintype "passive"))
      (node (ref "R13") (pin "2") (pinfunction "2_2") (pintype "passive"))
      (node (ref "R135") (pin "1") (pinfunction "1_1") (pintype "passive"))
      (node (ref "R15") (pin "2") (pinfunction "2_2") (pintype "passive"))
      (node (ref "R16") (pin "2") (pinfunction "2_2") (pintype "passive"))
      (node (ref "R164") (pin "2") (pinfunction "2_2") (pintype "passive"))
      (node (ref "R165") (pin "2") (pinfunction "2_2") (pintype "passive"))
      (node (ref "R169") (pin "2") (pinfunction "2_2") (pintype "passive"))
      (node (ref "R17") (pin "2") (pinfunction "2_2") (pintype "passive"))
      (node (ref "R170") (pin "2") (pinfunction "2_2") (pintype "passive"))
      (node (ref "R171") (pin "2") (pinfunction "2_2") (pintype "passive"))
      (node (ref "R190") (pin "1") (pinfunction "1_1") (pintype "passive"))
      (node (ref "R191") (pin "1") (pinfunction "1_1") (pintype "passive"))
      (node (ref "R195") (pin "1") (pinfunction "1_1") (pintype "passive"))
      (node (ref "R219") (pin "2") (pinfunction "2_2") (pintype "passive"))
      (node (ref "R220") (pin "2") (pinfunction "2_2") (pintype "passive"))
      (node (ref "R224") (pin "2") (pinfunction "2_2") (pintype "passive"))
      (node (ref "R225") (pin "2") (pinfunction "2_2") (pintype "passive"))
      (node (ref "R226") (pin "2") (pinfunction "2_2") (pintype "passive"))
      (node (ref "R245") (pin "1") (pinfunction "1_1") (pintype "passive"))
      (node (ref "R246") (pin "1") (pinfunction "1_1") (pintype "passive"))
      (node (ref "R250") (pin "1") (pinfunction "1_1") (pintype "passive"))
      (node (ref "R274") (pin "2") (pinfunction "2_2") (pintype "passive"))
      (node (ref "R275") (pin "2") (pinfunction "2_2") (pintype "passive"))
      (node (ref "R279") (pin "2") (pinfunction "2_2") (pintype "passive"))
      (node (ref "R280") (pin "2") (pinfunction "2_2") (pintype "passive"))
      (node (ref "R281") (pin "2") (pinfunction "2_2") (pintype "passive"))
      (node (ref "R297") (pin "1") (pinfunction "1_1") (pintype "passive"))
      (node (ref "R298") (pin "1") (pinfunction "1_1") (pintype "passive"))
      (node (ref "R300") (pin "1") (pinfunction "1_1") (pintype "passive"))
      (node (ref "R301") (pin "1") (pinfunction "1_1") (pintype "passive"))
      (node (ref "R305") (pin "1") (pinfunction "1_1") (pintype "passive"))
      (node (ref "R329") (pin "2") (pinfunction "2_2") (pintype "passive"))
      (node (ref "R330") (pin "2") (pinfunction "2_2") (pintype "passive"))
      (node (ref "R333") (pin "1") (pinfunction "1_1") (pintype "passive"))
      (node (ref "R356") (pin "2") (pinfunction "2_2") (pintype "passive"))
      (node (ref "R357") (pin "2") (pinfunction "2_2") (pintype "passive"))
      (node (ref "R36") (pin "1") (pinfunction "1_1") (pintype "passive"))
      (node (ref "R361") (pin "2") (pinfunction "2_2") (pintype "passive"))
      (node (ref "R362") (pin "2") (pinfunction "2_2") (pintype "passive"))
      (node (ref "R363") (pin "2") (pinfunction "2_2") (pintype "passive"))
      (node (ref "R37") (pin "1") (pinfunction "1_1") (pintype "passive"))
      (node (ref "R379") (pin "1") (pinfunction "1_1") (pintype "passive"))
      (node (ref "R380") (pin "1") (pinfunction "1_1") (pintype "passive"))
      (node (ref "R384") (pin "1") (pinfunction "1_1") (pintype "passive"))
      (node (ref "R407") (pin "2") (pinfunction "2_2") (pintype "passive"))
      (node (ref "R408") (pin "2") (pinfunction "2_2") (pintype "passive"))
      (node (ref "R41") (pin "1") (pinfunction "1_1") (pintype "passive"))
      (node (ref "R412") (pin "2") (pinfunction "2_2") (pintype "passive"))
      (node (ref "R413") (pin "2") (pinfunction "2_2") (pintype "passive"))
      (node (ref "R414") (pin "2") (pinfunction "2_2") (pintype "passive"))
      (node (ref "R43") (pin "2") (pinfunction "2_2") (pintype "passive"))
      (node (ref "R430") (pin "1") (pinfunction "1_1") (pintype "passive"))
      (node (ref "R431") (pin "1") (pinfunction "1_1") (pintype "passive"))
      (node (ref "R435") (pin "1") (pinfunction "1_1") (pintype "passive"))
      (node (ref "R458") (pin "2") (pinfunction "2_2") (pintype "passive"))
      (node (ref "R459") (pin "2") (pinfunction "2_2") (pintype "passive"))
      (node (ref "R463") (pin "2") (pinfunction "2_2") (pintype "passive"))
      (node (ref "R464") (pin "2") (pinfunction "2_2") (pintype "passive"))
      (node (ref "R465") (pin "2") (pinfunction "2_2") (pintype "passive"))
      (node (ref "R481") (pin "1") (pinfunction "1_1") (pintype "passive"))
      (node (ref "R482") (pin "1") (pinfunction "1_1") (pintype "passive"))
      (node (ref "R486") (pin "1") (pinfunction "1_1") (pintype "passive"))
      (node (ref "R509") (pin "2") (pinfunction "2_2") (pintype "passive"))
      (node (ref "R510") (pin "2") (pinfunction "2_2") (pintype "passive"))
      (node (ref "R514") (pin "2") (pinfunction "2_2") (pintype "passive"))
      (node (ref "R515") (pin "2") (pinfunction "2_2") (pintype "passive"))
      (node (ref "R516") (pin "2") (pinfunction "2_2") (pintype "passive"))
      (node (ref "R532") (pin "1") (pinfunction "1_1") (pintype "passive"))
      (node (ref "R533") (pin "1") (pinfunction "1_1") (pintype "passive"))
      (node (ref "R537") (pin "1") (pinfunction "1_1") (pintype "passive"))
      (node (ref "R560") (pin "2") (pinfunction "2_2") (pintype "passive"))
      (node (ref "R561") (pin "2") (pinfunction "2_2") (pintype "passive"))
      (node (ref "R565") (pin "2") (pinfunction "2_2") (pintype "passive"))
      (node (ref "R566") (pin "2") (pinfunction "2_2") (pintype "passive"))
      (node (ref "R567") (pin "2") (pinfunction "2_2") (pintype "passive"))
      (node (ref "R583") (pin "1") (pinfunction "1_1") (pintype "passive"))
      (node (ref "R584") (pin "1") (pinfunction "1_1") (pintype "passive"))
      (node (ref "R588") (pin "1") (pinfunction "1_1") (pintype "passive"))
      (node (ref "R611") (pin "2") (pinfunction "2_2") (pintype "passive"))
      (node (ref "R612") (pin "2") (pinfunction "2_2") (pintype "passive"))
      (node (ref "R65") (pin "2") (pinfunction "2_2") (pintype "passive"))
      (node (ref "R66") (pin "2") (pinfunction "2_2") (pintype "passive"))
      (node (ref "R70") (pin "2") (pinfunction "2_2") (pintype "passive"))
      (node (ref "R71") (pin "2") (pinfunction "2_2") (pintype "passive"))
      (node (ref "R72") (pin "2") (pinfunction "2_2") (pintype "passive"))
      (node (ref "R86") (pin "2") (pinfunction "2_2") (pintype "passive"))
      (node (ref "R88") (pin "2") (pinfunction "2_2") (pintype "passive"))
      (node (ref "R91") (pin "1") (pinfunction "1_1") (pintype "passive"))
      (node (ref "R92") (pin "1") (pinfunction "1_1") (pintype "passive"))
      (node (ref "R96") (pin "1") (pinfunction "1_1") (pintype "passive"))
      (node (ref "TP114") (pin "TP") (pinfunction "PP_TP") (pintype "input"))
      (node (ref "TP12") (pin "TP") (pinfunction "PP_TP") (pintype "input"))
      (node (ref "TP137") (pin "TP") (pinfunction "PP_TP") (pintype "input"))
      (node (ref "TP160") (pin "TP") (pinfunction "PP_TP") (pintype "input"))
      (node (ref "TP183") (pin "TP") (pinfunction "PP_TP") (pintype "input"))
      (node (ref "TP206") (pin "TP") (pinfunction "PP_TP") (pintype "input"))
      (node (ref "TP229") (pin "TP") (pinfunction "PP_TP") (pintype "input"))
      (node (ref "TP252") (pin "TP") (pinfunction "PP_TP") (pintype "input"))
      (node (ref "TP275") (pin "TP") (pinfunction "PP_TP") (pintype "input"))
      (node (ref "TP45") (pin "TP") (pinfunction "PP_TP") (pintype "input"))
      (node (ref "TP68") (pin "TP") (pinfunction "PP_TP") (pintype "input"))
      (node (ref "TP91") (pin "TP") (pinfunction "PP_TP") (pintype "input"))
      (node (ref "X103") (pin "1") (pinfunction "S_1") (pintype "passive"))
      (node (ref "X11") (pin "1") (pinfunction "S_1") (pintype "passive"))
      (node (ref "X14") (pin "1") (pinfunction "S_1") (pintype "passive"))
      (node (ref "X17") (pin "1") (pinfunction "S_1") (pintype "passive"))
      (node (ref "X2") (pin "1") (pinfunction "S_1") (pintype "passive"))
      (node (ref "X20") (pin "1") (pinfunction "S_1") (pintype "passive"))
      (node (ref "X23") (pin "1") (pinfunction "S_1") (pintype "passive"))
      (node (ref "X26") (pin "1") (pinfunction "S_1") (pintype "passive"))
      (node (ref "X29") (pin "1") (pinfunction "S_1") (pintype "passive"))
      (node (ref "X32") (pin "1") (pinfunction "S_1") (pintype "passive"))
      (node (ref "X5") (pin "1") (pinfunction "S_1") (pintype "passive"))
      (node (ref "X8") (pin "1") (pinfunction "S_1") (pintype "passive"))
    )
    (net (code "3") (name "GND") (class "Default")
      (node (ref "1") (pin "12") (pinfunction "KL_12") (pintype "passive"))
      (node (ref "11") (pin "12") (pinfunction "KL_12") (pintype "passive"))
      (node (ref "13") (pin "12") (pinfunction "KL_12") (pintype "passive"))
      (node (ref "15") (pin "12") (pinfunction "KL_12") (pintype "passive"))
      (node (ref "17") (pin "12") (pinfunction "KL_12") (pintype "passive"))
      (node (ref "19") (pin "12") (pinfunction "KL_12") (pintype "passive"))
      (node (ref "21") (pin "12") (pinfunction "KL_12") (pintype "passive"))
      (node (ref "23") (pin "12") (pinfunction "KL_12") (pintype "passive"))
      (node (ref "3") (pin "12") (pinfunction "KL_12") (pintype "passive"))
      (node (ref "5") (pin "12") (pinfunction "KL_12") (pintype "passive"))
      (node (ref "7") (pin "12") (pinfunction "KL_12") (pintype "passive"))
      (node (ref "9") (pin "12") (pinfunction "KL_12") (pintype "passive"))
      (node (ref "C1") (pin "2") (pinfunction "2_2") (pintype "passive"))
      (node (ref "C10") (pin "2") (pinfunction "2_2") (pintype "passive"))
      (node (ref "C100") (pin "2") (pinfunction "2_2") (pintype "passive"))
      (node (ref "C101") (pin "2") (pinfunction "2_2") (pintype "passive"))
      (node (ref "C102") (pin "2") (pinfunction "2_2") (pintype "passive"))
      (node (ref "C103") (pin "2") (pinfunction "2_2") (pintype "passive"))
      (node (ref "C104") (pin "2") (pinfunction "2_2") (pintype "passive"))
      (node (ref "C105") (pin "2") (pinfunction "2_2") (pintype "passive"))
      (node (ref "C106") (pin "1") (pinfunction "1_1") (pintype "passive"))
      (node (ref "C107") (pin "2") (pinfunction "2_2") (pintype "passive"))
      (node (ref "C108") (pin "2") (pinfunction "2_2") (pintype "passive"))
      (node (ref "C109") (pin "1") (pinfunction "1_1") (pintype "passive"))
      (node (ref "C11") (pin "2") (pinfunction "2_2") (pintype "passive"))
      (node (ref "C110") (pin "2") (pinfunction "2_2") (pintype "passive"))
      (node (ref "C111") (pin "2") (pinfunction "2_2") (pintype "passive"))
      (node (ref "C112") (pin "2") (pinfunction "2_2") (pintype "passive"))
      (node (ref "C113") (pin "2") (pinfunction "2_2") (pintype "passive"))
      (node (ref "C114") (pin "1") (pinfunction "1_1") (pintype "passive"))
      (node (ref "C115") (pin "1") (pinfunction "1_1") (pintype "passive"))
      (node (ref "C116") (pin "2") (pinfunction "2_2") (pintype "passive"))
      (node (ref "C117") (pin "2") (pinfunction "2_2") (pintype "passive"))
      (node (ref "C118") (pin "2") (pinfunction "2_2") (pintype "passive"))
      (node (ref "C119") (pin "1") (pinfunction "1_1") (pintype "passive"))
      (node (ref "C12") (pin "1") (pinfunction "1_1") (pintype "passive"))
      (node (ref "C120") (pin "2") (pinfunction "2_2") (pintype "passive"))
      (node (ref "C121") (pin "2") (pinfunction "2_2") (pintype "passive"))
      (node (ref "C122") (pin "2") (pinfunction "2_2") (pintype "passive"))
      (node (ref "C123") (pin "2") (pinfunction "2_2") (pintype "passive"))
      (node (ref "C124") (pin "2") (pinfunction "2_2") (pintype "passive"))
      (node (ref "C125") (pin "2") (pinfunction "2_2") (pintype "passive"))
      (node (ref "C126") (pin "1") (pinfunction "1_1") (pintype "passive"))
      (node (ref "C127") (pin "1") (pinfunction "1_1") (pintype "passive"))
      (node (ref "C128") (pin "2") (pinfunction "2_2") (pintype "passive"))
      (node (ref "C129") (pin "2") (pinfunction "2_2") (pintype "passive"))
      (node (ref "C13") (pin "2") (pinfunction "2_2") (pintype "passive"))
      (node (ref "C130") (pin "2") (pinfunction "2_2") (pintype "passive"))
      (node (ref "C131") (pin "1") (pinfunction "1_1") (pintype "passive"))
      (node (ref "C132") (pin "2") (pinfunction "2_2") (pintype "passive"))
      (node (ref "C133") (pin "2") (pinfunction "2_2") (pintype "passive"))
      (node (ref "C134") (pin "2") (pinfunction "2_2") (pintype "passive"))
      (node (ref "C135") (pin "2") (pinfunction "2_2") (pintype "passive"))
      (node (ref "C136") (pin "2") (pinfunction "2_2") (pintype "passive"))
      (node (ref "C137") (pin "2") (pinfunction "2_2") (pintype "passive"))
      (node (ref "C138") (pin "1") (pinfunction "1_1") (pintype "passive"))
      (node (ref "C139") (pin "1") (pinfunction "1_1") (pintype "passive"))
      (node (ref "C14") (pin "2") (pinfunction "2_2") (pintype "passive"))
      (node (ref "C140") (pin "2") (pinfunction "2_2") (pintype "passive"))
      (node (ref "C141") (pin "2") (pinfunction "2_2") (pintype "passive"))
      (node (ref "C142") (pin "2") (pinfunction "2_2") (pintype "passive"))
      (node (ref "C143") (pin "1") (pinfunction "1_1") (pintype "passive"))
      (node (ref "C144") (pin "2") (pinfunction "2_2") (pintype "passive"))
      (node (ref "C15") (pin "1") (pinfunction "1_1") (pintype "passive"))
      (node (ref "C16") (pin "2") (pinfunction "2_2") (pintype "passive"))
      (node (ref "C17") (pin "2") (pinfunction "2_2") (pintype "passive"))
      (node (ref "C18") (pin "2") (pinfunction "2_2") (pintype "passive"))
      (node (ref "C19") (pin "2") (pinfunction "2_2") (pintype "passive"))
      (node (ref "C2") (pin "2") (pinfunction "2_2") (pintype "passive"))
      (node (ref "C20") (pin "1") (pinfunction "1_1") (pintype "passive"))
      (node (ref "C21") (pin "1") (pinfunction "1_1") (pintype "passive"))
      (node (ref "C22") (pin "2") (pinfunction "2_2") (pintype "passive"))
      (node (ref "C23") (pin "2") (pinfunction "2_2") (pintype "passive"))
      (node (ref "C24") (pin "2") (pinfunction "2_2") (pintype "passive"))
      (node (ref "C25") (pin "1") (pinfunction "1_1") (pintype "passive"))
      (node (ref "C26") (pin "2") (pinfunction "2_2") (pintype "passive"))
      (node (ref "C27") (pin "2") (pinfunction "2_2") (pintype "passive"))
      (node (ref "C28") (pin "2") (pinfunction "2_2") (pintype "passive"))
      (node (ref "C29") (pin "2") (pinfunction "2_2") (pintype "passive"))
      (node (ref "C3") (pin "2") (pinfunction "2_2") (pintype "passive"))
      (node (ref "C30") (pin "2") (pinfunction "2_2") (pintype "passive"))
      (node (ref "C31") (pin "2") (pinfunction "2_2") (pintype "passive"))
      (node (ref "C32") (pin "1") (pinfunction "1_1") (pintype "passive"))
      (node (ref "C33") (pin "1") (pinfunction "1_1") (pintype "passive"))
      (node (ref "C34") (pin "2") (pinfunction "2_2") (pintype "passive"))
      (node (ref "C35") (pin "2") (pinfunction "2_2") (pintype "passive"))
      (node (ref "C36") (pin "2") (pinfunction "2_2") (pintype "passive"))
      (node (ref "C37") (pin "1") (pinfunction "1_1") (pintype "passive"))
      (node (ref "C38") (pin "2") (pinfunction "2_2") (pintype "passive"))
      (node (ref "C39") (pin "2") (pinfunction "2_2") (pintype "passive"))
      (node (ref "C4") (pin "2") (pinfunction "2_2") (pintype "passive"))
      (node (ref "C40") (pin "2") (pinfunction "2_2") (pintype "passive"))
      (node (ref "C41") (pin "2") (pinfunction "2_2") (pintype "passive"))
      (node (ref "C42") (pin "2") (pinfunction "2_2") (pintype "passive"))
      (node (ref "C43") (pin "2") (pinfunction "2_2") (pintype "passive"))
      (node (ref "C44") (pin "1") (pinfunction "1_1") (pintype "passive"))
      (node (ref "C45") (pin "1") (pinfunction "1_1") (pintype "passive"))
      (node (ref "C46") (pin "2") (pinfunction "2_2") (pintype "passive"))
      (node (ref "C47") (pin "2") (pinfunction "2_2") (pintype "passive"))
      (node (ref "C48") (pin "2") (pinfunction "2_2") (pintype "passive"))
      (node (ref "C49") (pin "1") (pinfunction "1_1") (pintype "passive"))
      (node (ref "C5") (pin "2") (pinfunction "2_2") (pintype "passive"))
      (node (ref "C50") (pin "2") (pinfunction "2_2") (pintype "passive"))
      (node (ref "C51") (pin "2") (pinfunction "2_2") (pintype "passive"))
      (node (ref "C52") (pin "2") (pinfunction "2_2") (pintype "passive"))
      (node (ref "C53") (pin "2") (pinfunction "2_2") (pintype "passive"))
      (node (ref "C54") (pin "2") (pinfunction "2_2") (pintype "passive"))
      (node (ref "C55") (pin "2") (pinfunction "2_2") (pintype "passive"))
      (node (ref "C56") (pin "1") (pinfunction "1_1") (pintype "passive"))
      (node (ref "C57") (pin "1") (pinfunction "1_1") (pintype "passive"))
      (node (ref "C58") (pin "2") (pinfunction "2_2") (pintype "passive"))
      (node (ref "C59") (pin "2") (pinfunction "2_2") (pintype "passive"))
      (node (ref "C6") (pin "2") (pinfunction "2_2") (pintype "passive"))
      (node (ref "C60") (pin "2") (pinfunction "2_2") (pintype "passive"))
      (node (ref "C61") (pin "1") (pinfunction "1_1") (pintype "passive"))
      (node (ref "C62") (pin "2") (pinfunction "2_2") (pintype "passive"))
      (node (ref "C63") (pin "2") (pinfunction "2_2") (pintype "passive"))
      (node (ref "C64") (pin "2") (pinfunction "2_2") (pintype "passive"))
      (node (ref "C65") (pin "2") (pinfunction "2_2") (pintype "passive"))
      (node (ref "C66") (pin "2") (pinfunction "2_2") (pintype "passive"))
      (node (ref "C67") (pin "2") (pinfunction "2_2") (pintype "passive"))
      (node (ref "C68") (pin "1") (pinfunction "1_1") (pintype "passive"))
      (node (ref "C69") (pin "1") (pinfunction "1_1") (pintype "passive"))
      (node (ref "C7") (pin "1") (pinfunction "1_1") (pintype "passive"))
      (node (ref "C70") (pin "2") (pinfunction "2_2") (pintype "passive"))
      (node (ref "C71") (pin "2") (pinfunction "2_2") (pintype "passive"))
      (node (ref "C72") (pin "2") (pinfunction "2_2") (pintype "passive"))
      (node (ref "C73") (pin "1") (pinfunction "1_1") (pintype "passive"))
      (node (ref "C74") (pin "2") (pinfunction "2_2") (pintype "passive"))
      (node (ref "C75") (pin "2") (pinfunction "2_2") (pintype "passive"))
      (node (ref "C76") (pin "2") (pinfunction "2_2") (pintype "passive"))
      (node (ref "C77") (pin "2") (pinfunction "2_2") (pintype "passive"))
      (node (ref "C78") (pin "2") (pinfunction "2_2") (pintype "passive"))
      (node (ref "C79") (pin "2") (pinfunction "2_2") (pintype "passive"))
      (node (ref "C8") (pin "1") (pinfunction "1_1") (pintype "passive"))
      (node (ref "C80") (pin "1") (pinfunction "1_1") (pintype "passive"))
      (node (ref "C81") (pin "1") (pinfunction "1_1") (pintype "passive"))
      (node (ref "C82") (pin "2") (pinfunction "2_2") (pintype "passive"))
      (node (ref "C83") (pin "2") (pinfunction "2_2") (pintype "passive"))
      (node (ref "C84") (pin "2") (pinfunction "2_2") (pintype "passive"))
      (node (ref "C85") (pin "1") (pinfunction "1_1") (pintype "passive"))
      (node (ref "C86") (pin "2") (pinfunction "2_2") (pintype "passive"))
      (node (ref "C87") (pin "2") (pinfunction "2_2") (pintype "passive"))
      (node (ref "C88") (pin "2") (pinfunction "2_2") (pintype "passive"))
      (node (ref "C89") (pin "2") (pinfunction "2_2") (pintype "passive"))
      (node (ref "C9") (pin "2") (pinfunction "2_2") (pintype "passive"))
      (node (ref "C90") (pin "2") (pinfunction "2_2") (pintype "passive"))
      (node (ref "C91") (pin "2") (pinfunction "2_2") (pintype "passive"))
      (node (ref "C92") (pin "1") (pinfunction "1_1") (pintype "passive"))
      (node (ref "C93") (pin "1") (pinfunction "1_1") (pintype "passive"))
      (node (ref "C94") (pin "2") (pinfunction "2_2") (pintype "passive"))
      (node (ref "C95") (pin "2") (pinfunction "2_2") (pintype "passive"))
      (node (ref "C96") (pin "2") (pinfunction "2_2") (pintype "passive"))
      (node (ref "C97") (pin "1") (pinfunction "1_1") (pintype "passive"))
      (node (ref "C98") (pin "2") (pinfunction "2_2") (pintype "passive"))
      (node (ref "C99") (pin "2") (pinfunction "2_2") (pintype "passive"))
      (node (ref "D101") (pin "A") (pinfunction "A_A") (pintype "passive"))
      (node (ref "D105") (pin "1") (pinfunction "+_1") (pintype "passive"))
      (node (ref "D11") (pin "1") (pinfunction "+_1") (pintype "passive"))
      (node (ref "D111") (pin "1") (pinfunction "+_1") (pintype "passive"))
      (node (ref "D114") (pin "A") (pinfunction "A_A") (pintype "passive"))
      (node (ref "D117") (pin "A") (pinfunction "A_A") (pintype "passive"))
      (node (ref "D125") (pin "1") (pinfunction "+_1") (pintype "passive"))
      (node (ref "D127") (pin "A") (pinfunction "A_A") (pintype "passive"))
      (node (ref "D13") (pin "A") (pinfunction "A_A") (pintype "passive"))
      (node (ref "D130") (pin "A") (pinfunction "A_A") (pintype "passive"))
      (node (ref "D138") (pin "1") (pinfunction "+_1") (pintype "passive"))
      (node (ref "D140") (pin "A") (pinfunction "A_A") (pintype "passive"))
      (node (ref "D143") (pin "A") (pinfunction "A_A") (pintype "passive"))
      (node (ref "D151") (pin "1") (pinfunction "+_1") (pintype "passive"))
      (node (ref "D153") (pin "A") (pinfunction "A_A") (pintype "passive"))
      (node (ref "D156") (pin "A") (pinfunction "A_A") (pintype "passive"))
      (node (ref "D17") (pin "A") (pinfunction "A_A") (pintype "passive"))
      (node (ref "D25") (pin "1") (pinfunction "+_1") (pintype "passive"))
      (node (ref "D27") (pin "A") (pinfunction "A_A") (pintype "passive"))
      (node (ref "D31") (pin "A") (pinfunction "A_A") (pintype "passive"))
      (node (ref "D39") (pin "1") (pinfunction "+_1") (pintype "passive"))
      (node (ref "D4") (pin "A") (pinfunction "A_A") (pintype "passive"))
      (node (ref "D41") (pin "A") (pinfunction "A_A") (pintype "passive"))
      (node (ref "D45") (pin "A") (pinfunction "A_A") (pintype "passive"))
      (node (ref "D53") (pin "1") (pinfunction "+_1") (pintype "passive"))
      (node (ref "D55") (pin "A") (pinfunction "A_A") (pintype "passive"))
      (node (ref "D59") (pin "A") (pinfunction "A_A") (pintype "passive"))
      (node (ref "D67") (pin "1") (pinfunction "+_1") (pintype "passive"))
      (node (ref "D69") (pin "A") (pinfunction "A_A") (pintype "passive"))
      (node (ref "D73") (pin "A") (pinfunction "A_A") (pintype "passive"))
      (node (ref "D76") (pin "1") (pinfunction "+_1") (pintype "passive"))
      (node (ref "D78") (pin "A") (pinfunction "A_A") (pintype "passive"))
      (node (ref "D81") (pin "A") (pinfunction "A_A") (pintype "passive"))
      (node (ref "D89") (pin "1") (pinfunction "+_1") (pintype "passive"))
      (node (ref "D91") (pin "A") (pinfunction "A_A") (pintype "passive"))
      (node (ref "D94") (pin "A") (pinfunction "A_A") (pintype "passive"))
      (node (ref "IC1") (pin "11") (pinfunction "D_11") (pintype "input"))
      (node (ref "IC1") (pin "8") (pinfunction "VSS_8") (pintype "power_in"))
      (node (ref "IC10") (pin "11") (pinfunction "D_11") (pintype "input"))
      (node (ref "IC10") (pin "8") (pinfunction "VSS_8") (pintype "power_in"))
      (node (ref "IC101") (pin "4") (pinfunction "V-_4") (pintype "power_in"))
      (node (ref "IC102") (pin "2") (pinfunction "GND_2") (pintype "input"))
      (node (ref "IC102") (pin "2@1") (pinfunction "GND_2@1") (pintype "input"))
      (node (ref "IC104") (pin "2") (pinfunction "GND_2") (pintype "input"))
      (node (ref "IC104") (pin "2@1") (pinfunction "GND_2@1") (pintype "input"))
      (node (ref "IC105") (pin "11") (pinfunction "D_11") (pintype "input"))
      (node (ref "IC105") (pin "8") (pinfunction "VSS_8") (pintype "power_in"))
      (node (ref "IC107") (pin "8") (pinfunction "GND_8") (pintype "power_in"))
      (node (ref "IC108") (pin "12") (pinfunction "GND_12") (pintype "power_in"))
      (node (ref "IC110") (pin "1") (pinfunction "GND_1") (pintype "power_in"))
      (node (ref "IC111") (pin "1") (pinfunction "T1_1") (pintype "input"))
      (node (ref "IC111") (pin "15") (pinfunction "T1_15") (pintype "input"))
      (node (ref "IC111") (pin "8") (pinfunction "VSS_8") (pintype "power_in"))
      (node (ref "IC12") (pin "8") (pinfunction "GND_8") (pintype "power_in"))
      (node (ref "IC13") (pin "12") (pinfunction "GND_12") (pintype "power_in"))
      (node (ref "IC14") (pin "2") (pinfunction "GND_2") (pintype "input"))
      (node (ref "IC14") (pin "2@1") (pinfunction "GND_2@1") (pintype "input"))
      (node (ref "IC15") (pin "1") (pinfunction "GND_1") (pintype "power_in"))
      (node (ref "IC16") (pin "1") (pinfunction "T1_1") (pintype "input"))
      (node (ref "IC16") (pin "15") (pinfunction "T1_15") (pintype "input"))
      (node (ref "IC16") (pin "8") (pinfunction "VSS_8") (pintype "power_in"))
      (node (ref "IC17") (pin "2") (pinfunction "GND_2") (pintype "input"))
      (node (ref "IC17") (pin "2@1") (pinfunction "GND_2@1") (pintype "input"))
      (node (ref "IC18") (pin "4") (pinfunction "V-_4") (pintype "power_in"))
      (node (ref "IC19") (pin "11") (pinfunction "D_11") (pintype "input"))
      (node (ref "IC19") (pin "8") (pinfunction "VSS_8") (pintype "power_in"))
      (node (ref "IC21") (pin "8") (pinfunction "GND_8") (pintype "power_in"))
      (node (ref "IC22") (pin "12") (pinfunction "GND_12") (pintype "power_in"))
      (node (ref "IC23") (pin "2") (pinfunction "GND_2") (pintype "input"))
      (node (ref "IC23") (pin "2@1") (pinfunction "GND_2@1") (pintype "input"))
      (node (ref "IC24") (pin "1") (pinfunction "GND_1") (pintype "power_in"))
      (node (ref "IC25") (pin "1") (pinfunction "T1_1") (pintype "input"))
      (node (ref "IC25") (pin "15") (pinfunction "T1_15") (pintype "input"))
      (node (ref "IC25") (pin "8") (pinfunction "VSS_8") (pintype "power_in"))
      (node (ref "IC26") (pin "2") (pinfunction "GND_2") (pintype "input"))
      (node (ref "IC26") (pin "2@1") (pinfunction "GND_2@1") (pintype "input"))
      (node (ref "IC27") (pin "4") (pinfunction "V-_4") (pintype "power_in"))
      (node (ref "IC28") (pin "11") (pinfunction "D_11") (pintype "input"))
      (node (ref "IC28") (pin "8") (pinfunction "VSS_8") (pintype "power_in"))
      (node (ref "IC3") (pin "8") (pinfunction "GND_8") (pintype "power_in"))
      (node (ref "IC30") (pin "8") (pinfunction "GND_8") (pintype "power_in"))
      (node (ref "IC31") (pin "12") (pinfunction "GND_12") (pintype "power_in"))
      (node (ref "IC32") (pin "2") (pinfunction "GND_2") (pintype "input"))
      (node (ref "IC32") (pin "2@1") (pinfunction "GND_2@1") (pintype "input"))
      (node (ref "IC33") (pin "1") (pinfunction "GND_1") (pintype "power_in"))
      (node (ref "IC34") (pin "1") (pinfunction "T1_1") (pintype "input"))
      (node (ref "IC34") (pin "15") (pinfunction "T1_15") (pintype "input"))
      (node (ref "IC34") (pin "8") (pinfunction "VSS_8") (pintype "power_in"))
      (node (ref "IC35") (pin "2") (pinfunction "GND_2") (pintype "input"))
      (node (ref "IC35") (pin "2@1") (pinfunction "GND_2@1") (pintype "input"))
      (node (ref "IC36") (pin "4") (pinfunction "V-_4") (pintype "power_in"))
      (node (ref "IC37") (pin "11") (pinfunction "D_11") (pintype "input"))
      (node (ref "IC37") (pin "8") (pinfunction "VSS_8") (pintype "power_in"))
      (node (ref "IC39") (pin "8") (pinfunction "GND_8") (pintype "power_in"))
      (node (ref "IC4") (pin "12") (pinfunction "GND_12") (pintype "power_in"))
      (node (ref "IC40") (pin "12") (pinfunction "GND_12") (pintype "power_in"))
      (node (ref "IC41") (pin "2") (pinfunction "GND_2") (pintype "input"))
      (node (ref "IC41") (pin "2@1") (pinfunction "GND_2@1") (pintype "input"))
      (node (ref "IC42") (pin "1") (pinfunction "GND_1") (pintype "power_in"))
      (node (ref "IC43") (pin "1") (pinfunction "T1_1") (pintype "input"))
      (node (ref "IC43") (pin "15") (pinfunction "T1_15") (pintype "input"))
      (node (ref "IC43") (pin "8") (pinfunction "VSS_8") (pintype "power_in"))
      (node (ref "IC44") (pin "2") (pinfunction "GND_2") (pintype "input"))
      (node (ref "IC44") (pin "2@1") (pinfunction "GND_2@1") (pintype "input"))
      (node (ref "IC45") (pin "4") (pinfunction "V-_4") (pintype "power_in"))
      (node (ref "IC46") (pin "11") (pinfunction "D_11") (pintype "input"))
      (node (ref "IC46") (pin "8") (pinfunction "VSS_8") (pintype "power_in"))
      (node (ref "IC48") (pin "8") (pinfunction "GND_8") (pintype "power_in"))
      (node (ref "IC49") (pin "12") (pinfunction "GND_12") (pintype "power_in"))
      (node (ref "IC5") (pin "2") (pinfunction "GND_2") (pintype "input"))
      (node (ref "IC5") (pin "2@1") (pinfunction "GND_2@1") (pintype "input"))
      (node (ref "IC50") (pin "2") (pinfunction "GND_2") (pintype "input"))
      (node (ref "IC50") (pin "2@1") (pinfunction "GND_2@1") (pintype "input"))
      (node (ref "IC51") (pin "1") (pinfunction "GND_1") (pintype "power_in"))
      (node (ref "IC52") (pin "1") (pinfunction "T1_1") (pintype "input"))
      (node (ref "IC52") (pin "15") (pinfunction "T1_15") (pintype "input"))
      (node (ref "IC52") (pin "8") (pinfunction "VSS_8") (pintype "power_in"))
      (node (ref "IC53") (pin "2") (pinfunction "GND_2") (pintype "input"))
      (node (ref "IC53") (pin "2@1") (pinfunction "GND_2@1") (pintype "input"))
      (node (ref "IC54") (pin "4") (pinfunction "V-_4") (pintype "power_in"))
      (node (ref "IC55") (pin "11") (pinfunction "D_11") (pintype "input"))
      (node (ref "IC55") (pin "8") (pinfunction "VSS_8") (pintype "power_in"))
      (node (ref "IC57") (pin "8") (pinfunction "GND_8") (pintype "power_in"))
      (node (ref "IC58") (pin "12") (pinfunction "GND_12") (pintype "power_in"))
      (node (ref "IC59") (pin "2") (pinfunction "GND_2") (pintype "input"))
      (node (ref "IC59") (pin "2@1") (pinfunction "GND_2@1") (pintype "input"))
      (node (ref "IC6") (pin "1") (pinfunction "GND_1") (pintype "power_in"))
      (node (ref "IC60") (pin "1") (pinfunction "GND_1") (pintype "power_in"))
      (node (ref "IC61") (pin "1") (pinfunction "T1_1") (pintype "input"))
      (node (ref "IC61") (pin "15") (pinfunction "T1_15") (pintype "input"))
      (node (ref "IC61") (pin "8") (pinfunction "VSS_8") (pintype "power_in"))
      (node (ref "IC62") (pin "2") (pinfunction "GND_2") (pintype "input"))
      (node (ref "IC62") (pin "2@1") (pinfunction "GND_2@1") (pintype "input"))
      (node (ref "IC63") (pin "4") (pinfunction "V-_4") (pintype "power_in"))
      (node (ref "IC64") (pin "11") (pinfunction "D_11") (pintype "input"))
      (node (ref "IC64") (pin "8") (pinfunction "VSS_8") (pintype "power_in"))
      (node (ref "IC66") (pin "8") (pinfunction "GND_8") (pintype "power_in"))
      (node (ref "IC67") (pin "12") (pinfunction "GND_12") (pintype "power_in"))
      (node (ref "IC68") (pin "2") (pinfunction "GND_2") (pintype "input"))
      (node (ref "IC68") (pin "2@1") (pinfunction "GND_2@1") (pintype "input"))
      (node (ref "IC69") (pin "1") (pinfunction "GND_1") (pintype "power_in"))
      (node (ref "IC7") (pin "1") (pinfunction "T1_1") (pintype "input"))
      (node (ref "IC7") (pin "15") (pinfunction "T1_15") (pintype "input"))
      (node (ref "IC7") (pin "8") (pinfunction "VSS_8") (pintype "power_in"))
      (node (ref "IC70") (pin "1") (pinfunction "T1_1") (pintype "input"))
      (node (ref "IC70") (pin "15") (pinfunction "T1_15") (pintype "input"))
      (node (ref "IC70") (pin "8") (pinfunction "VSS_8") (pintype "power_in"))
      (node (ref "IC71") (pin "2") (pinfunction "GND_2") (pintype "input"))
      (node (ref "IC71") (pin "2@1") (pinfunction "GND_2@1") (pintype "input"))
      (node (ref "IC72") (pin "4") (pinfunction "V-_4") (pintype "power_in"))
      (node (ref "IC73") (pin "11") (pinfunction "D_11") (pintype "input"))
      (node (ref "IC73") (pin "8") (pinfunction "VSS_8") (pintype "power_in"))
      (node (ref "IC75") (pin "8") (pinfunction "GND_8") (pintype "power_in"))
      (node (ref "IC76") (pin "12") (pinfunction "GND_12") (pintype "power_in"))
      (node (ref "IC77") (pin "2") (pinfunction "GND_2") (pintype "input"))
      (node (ref "IC77") (pin "2@1") (pinfunction "GND_2@1") (pintype "input"))
      (node (ref "IC78") (pin "1") (pinfunction "GND_1") (pintype "power_in"))
      (node (ref "IC79") (pin "1") (pinfunction "T1_1") (pintype "input"))
      (node (ref "IC79") (pin "15") (pinfunction "T1_15") (pintype "input"))
      (node (ref "IC79") (pin "8") (pinfunction "VSS_8") (pintype "power_in"))
      (node (ref "IC8") (pin "2") (pinfunction "GND_2") (pintype "input"))
      (node (ref "IC8") (pin "2@1") (pinfunction "GND_2@1") (pintype "input"))
      (node (ref "IC80") (pin "2") (pinfunction "GND_2") (pintype "input"))
      (node (ref "IC80") (pin "2@1") (pinfunction "GND_2@1") (pintype "input"))
      (node (ref "IC81") (pin "4") (pinfunction "V-_4") (pintype "power_in"))
      (node (ref "IC82") (pin "11") (pinfunction "D_11") (pintype "input"))
      (node (ref "IC82") (pin "8") (pinfunction "VSS_8") (pintype "power_in"))
      (node (ref "IC84") (pin "8") (pinfunction "GND_8") (pintype "power_in"))
      (node (ref "IC85") (pin "12") (pinfunction "GND_12") (pintype "power_in"))
      (node (ref "IC86") (pin "2") (pinfunction "GND_2") (pintype "input"))
      (node (ref "IC86") (pin "2@1") (pinfunction "GND_2@1") (pintype "input"))
      (node (ref "IC87") (pin "1") (pinfunction "GND_1") (pintype "power_in"))
      (node (ref "IC88") (pin "1") (pinfunction "T1_1") (pintype "input"))
      (node (ref "IC88") (pin "15") (pinfunction "T1_15") (pintype "input"))
      (node (ref "IC88") (pin "8") (pinfunction "VSS_8") (pintype "power_in"))
      (node (ref "IC89") (pin "2") (pinfunction "GND_2") (pintype "input"))
      (node (ref "IC89") (pin "2@1") (pinfunction "GND_2@1") (pintype "input"))
      (node (ref "IC9") (pin "4") (pinfunction "V-_4") (pintype "power_in"))
      (node (ref "IC90") (pin "4") (pinfunction "V-_4") (pintype "power_in"))
      (node (ref "IC91") (pin "11") (pinfunction "D_11") (pintype "input"))
      (node (ref "IC91") (pin "8") (pinfunction "VSS_8") (pintype "power_in"))
      (node (ref "IC93") (pin "8") (pinfunction "GND_8") (pintype "power_in"))
      (node (ref "IC94") (pin "12") (pinfunction "GND_12") (pintype "power_in"))
      (node (ref "IC95") (pin "2") (pinfunction "GND_2") (pintype "input"))
      (node (ref "IC95") (pin "2@1") (pinfunction "GND_2@1") (pintype "input"))
      (node (ref "IC96") (pin "1") (pinfunction "GND_1") (pintype "power_in"))
      (node (ref "IC97") (pin "1") (pinfunction "T1_1") (pintype "input"))
      (node (ref "IC97") (pin "15") (pinfunction "T1_15") (pintype "input"))
      (node (ref "IC97") (pin "8") (pinfunction "VSS_8") (pintype "power_in"))
      (node (ref "IC98") (pin "2") (pinfunction "GND_2") (pintype "input"))
      (node (ref "IC98") (pin "2@1") (pinfunction "GND_2@1") (pintype "input"))
      (node (ref "IC99") (pin "4") (pinfunction "V-_4") (pintype "power_in"))
      (node (ref "Q1") (pin "2") (pinfunction "S_2") (pintype "passive"))
      (node (ref "Q107") (pin "2") (pinfunction "S_2") (pintype "passive"))
      (node (ref "Q108") (pin "2") (pinfunction "S_2") (pintype "passive"))
      (node (ref "Q11") (pin "2") (pinfunction "S_2") (pintype "passive"))
      (node (ref "Q110") (pin "2") (pinfunction "S_2") (pintype "passive"))
      (node (ref "Q116") (pin "2") (pinfunction "S_2") (pintype "passive"))
      (node (ref "Q118") (pin "2") (pinfunction "S_2") (pintype "passive"))
      (node (ref "Q120") (pin "2") (pinfunction "S_2") (pintype "passive"))
      (node (ref "Q13") (pin "2") (pinfunction "S_2") (pintype "passive"))
      (node (ref "Q19") (pin "2") (pinfunction "S_2") (pintype "passive"))
      (node (ref "Q21") (pin "2") (pinfunction "S_2") (pintype "passive"))
      (node (ref "Q23") (pin "2") (pinfunction "S_2") (pintype "passive"))
      (node (ref "Q29") (pin "2") (pinfunction "S_2") (pintype "passive"))
      (node (ref "Q3") (pin "2") (pinfunction "S_2") (pintype "passive"))
      (node (ref "Q31") (pin "2") (pinfunction "S_2") (pintype "passive"))
      (node (ref "Q33") (pin "2") (pinfunction "S_2") (pintype "passive"))
      (node (ref "Q39") (pin "2") (pinfunction "S_2") (pintype "passive"))
      (node (ref "Q41") (pin "2") (pinfunction "S_2") (pintype "passive"))
      (node (ref "Q43") (pin "2") (pinfunction "S_2") (pintype "passive"))
      (node (ref "Q49") (pin "2") (pinfunction "S_2") (pintype "passive"))
      (node (ref "Q51") (pin "2") (pinfunction "S_2") (pintype "passive"))
      (node (ref "Q53") (pin "2") (pinfunction "S_2") (pintype "passive"))
      (node (ref "Q59") (pin "2") (pinfunction "S_2") (pintype "passive"))
      (node (ref "Q61") (pin "2") (pinfunction "S_2") (pintype "passive"))
      (node (ref "Q63") (pin "2") (pinfunction "S_2") (pintype "passive"))
      (node (ref "Q69") (pin "2") (pinfunction "S_2") (pintype "passive"))
      (node (ref "Q71") (pin "2") (pinfunction "S_2") (pintype "passive"))
      (node (ref "Q73") (pin "2") (pinfunction "S_2") (pintype "passive"))
      (node (ref "Q79") (pin "2") (pinfunction "S_2") (pintype "passive"))
      (node (ref "Q81") (pin "2") (pinfunction "S_2") (pintype "passive"))
      (node (ref "Q83") (pin "2") (pinfunction "S_2") (pintype "passive"))
      (node (ref "Q89") (pin "2") (pinfunction "S_2") (pintype "passive"))
      (node (ref "Q9") (pin "2") (pinfunction "S_2") (pintype "passive"))
      (node (ref "Q91") (pin "2") (pinfunction "S_2") (pintype "passive"))
      (node (ref "Q93") (pin "2") (pinfunction "S_2") (pintype "passive"))
      (node (ref "Q99") (pin "2") (pinfunction "S_2") (pintype "passive"))
      (node (ref "R100") (pin "1") (pinfunction "1_1") (pintype "passive"))
      (node (ref "R101") (pin "2") (pinfunction "2_2") (pintype "passive"))
      (node (ref "R103") (pin "2") (pinfunction "2_2") (pintype "passive"))
      (node (ref "R107") (pin "1") (pinfunction "1_1") (pintype "passive"))
      (node (ref "R114") (pin "1") (pinfunction "1_1") (pintype "passive"))
      (node (ref "R118") (pin "1") (pinfunction "1_1") (pintype "passive"))
      (node (ref "R123") (pin "1") (pinfunction "1_1") (pintype "passive"))
      (node (ref "R132") (pin "1") (pinfunction "1_1") (pintype "passive"))
      (node (ref "R136") (pin "1") (pinfunction "1_1") (pintype "passive"))
      (node (ref "R137") (pin "1") (pinfunction "1_1") (pintype "passive"))
      (node (ref "R141") (pin "2") (pinfunction "2_2") (pintype "passive"))
      (node (ref "R153") (pin "1") (pinfunction "1_1") (pintype "passive"))
      (node (ref "R154") (pin "2") (pinfunction "2_2") (pintype "passive"))
      (node (ref "R158") (pin "2") (pinfunction "2_2") (pintype "passive"))
      (node (ref "R159") (pin "2") (pinfunction "2_2") (pintype "passive"))
      (node (ref "R160") (pin "1") (pinfunction "1_1") (pintype "passive"))
      (node (ref "R173") (pin "1") (pinfunction "1_1") (pintype "passive"))
      (node (ref "R179") (pin "1") (pinfunction "1_1") (pintype "passive"))
      (node (ref "R183") (pin "1") (pinfunction "1_1") (pintype "passive"))
      (node (ref "R184") (pin "2") (pinfunction "2_2") (pintype "passive"))
      (node (ref "R187") (pin "1") (pinfunction "1_1") (pintype "passive"))
      (node (ref "R19") (pin "1") (pinfunction "1_1") (pintype "passive"))
      (node (ref "R196") (pin "2") (pinfunction "2_2") (pintype "passive"))
      (node (ref "R199") (pin "1") (pinfunction "1_1") (pintype "passive"))
      (node (ref "R200") (pin "1") (pinfunction "1_1") (pintype "passive"))
      (node (ref "R208") (pin "1") (pinfunction "1_1") (pintype "passive"))
      (node (ref "R209") (pin "2") (pinfunction "2_2") (pintype "passive"))
      (node (ref "R213") (pin "2") (pinfunction "2_2") (pintype "passive"))
      (node (ref "R214") (pin "2") (pinfunction "2_2") (pintype "passive"))
      (node (ref "R215") (pin "1") (pinfunction "1_1") (pintype "passive"))
      (node (ref "R228") (pin "1") (pinfunction "1_1") (pintype "passive"))
      (node (ref "R234") (pin "1") (pinfunction "1_1") (pintype "passive"))
      (node (ref "R238") (pin "1") (pinfunction "1_1") (pintype "passive"))
      (node (ref "R239") (pin "2") (pinfunction "2_2") (pintype "passive"))
      (node (ref "R242") (pin "1") (pinfunction "1_1") (pintype "passive"))
      (node (ref "R243") (pin "2") (pinfunction "2_2") (pintype "passive"))
      (node (ref "R25") (pin "1") (pinfunction "1_1") (pintype "passive"))
      (node (ref "R251") (pin "2") (pinfunction "2_2") (pintype "passive"))
      (node (ref "R254") (pin "1") (pinfunction "1_1") (pintype "passive"))
      (node (ref "R255") (pin "1") (pinfunction "1_1") (pintype "passive"))
      (node (ref "R263") (pin "1") (pinfunction "1_1") (pintype "passive"))
      (node (ref "R264") (pin "2") (pinfunction "2_2") (pintype "passive"))
      (node (ref "R268") (pin "2") (pinfunction "2_2") (pintype "passive"))
      (node (ref "R269") (pin "2") (pinfunction "2_2") (pintype "passive"))
      (node (ref "R270") (pin "1") (pinfunction "1_1") (pintype "passive"))
      (node (ref "R283") (pin "1") (pinfunction "1_1") (pintype "passive"))
      (node (ref "R289") (pin "1") (pinfunction "1_1") (pintype "passive"))
      (node (ref "R29") (pin "1") (pinfunction "1_1") (pintype "passive"))
      (node (ref "R293") (pin "1") (pinfunction "1_1") (pintype "passive"))
      (node (ref "R294") (pin "2") (pinfunction "2_2") (pintype "passive"))
      (node (ref "R30") (pin "2") (pinfunction "2_2") (pintype "passive"))
      (node (ref "R306") (pin "2") (pinfunction "2_2") (pintype "passive"))
      (node (ref "R309") (pin "1") (pinfunction "1_1") (pintype "passive"))
      (node (ref "R310") (pin "1") (pinfunction "1_1") (pintype "passive"))
      (node (ref "R318") (pin "1") (pinfunction "1_1") (pintype "passive"))
      (node (ref "R319") (pin "2") (pinfunction "2_2") (pintype "passive"))
      (node (ref "R323") (pin "2") (pinfunction "2_2") (pintype "passive"))
      (node (ref "R324") (pin "2") (pinfunction "2_2") (pintype "passive"))
      (node (ref "R325") (pin "1") (pinfunction "1_1") (pintype "passive"))
      (node (ref "R334") (pin "2") (pinfunction "2_2") (pintype "passive"))
      (node (ref "R336") (pin "1") (pinfunction "1_1") (pintype "passive"))
      (node (ref "R337") (pin "1") (pinfunction "1_1") (pintype "passive"))
      (node (ref "R345") (pin "1") (pinfunction "1_1") (pintype "passive"))
      (node (ref "R346") (pin "2") (pinfunction "2_2") (pintype "passive"))
      (node (ref "R350") (pin "2") (pinfunction "2_2") (pintype "passive"))
      (node (ref "R351") (pin "2") (pinfunction "2_2") (pintype "passive"))
      (node (ref "R352") (pin "1") (pinfunction "1_1") (pintype "passive"))
      (node (ref "R365") (pin "1") (pinfunction "1_1") (pintype "passive"))
      (node (ref "R371") (pin "1") (pinfunction "1_1") (pintype "passive"))
      (node (ref "R375") (pin "1") (pinfunction "1_1") (pintype "passive"))
      (node (ref "R376") (pin "2") (pinfunction "2_2") (pintype "passive"))
      (node (ref "R385") (pin "2") (pinfunction "2_2") (pintype "passive"))
      (node (ref "R387") (pin "1") (pinfunction "1_1") (pintype "passive"))
      (node (ref "R388") (pin "1") (pinfunction "1_1") (pintype "passive"))
      (node (ref "R396") (pin "1") (pinfunction "1_1") (pintype "passive"))
      (node (ref "R397") (pin "2") (pinfunction "2_2") (pintype "passive"))
      (node (ref "R4") (pin "1") (pinfunction "1_1") (pintype "passive"))
      (node (ref "R401") (pin "2") (pinfunction "2_2") (pintype "passive"))
      (node (ref "R402") (pin "2") (pinfunction "2_2") (pintype "passive"))
      (node (ref "R403") (pin "1") (pinfunction "1_1") (pintype "passive"))
      (node (ref "R416") (pin "1") (pinfunction "1_1") (pintype "passive"))
      (node (ref "R42") (pin "2") (pinfunction "2_2") (pintype "passive"))
      (node (ref "R422") (pin "1") (pinfunction "1_1") (pintype "passive"))
      (node (ref "R426") (pin "1") (pinfunction "1_1") (pintype "passive"))
      (node (ref "R427") (pin "2") (pinfunction "2_2") (pintype "passive"))
      (node (ref "R436") (pin "2") (pinfunction "2_2") (pintype "passive"))
      (node (ref "R438") (pin "1") (pinfunction "1_1") (pintype "passive"))
      (node (ref "R439") (pin "1") (pinfunction "1_1") (pintype "passive"))
      (node (ref "R447") (pin "1") (pinfunction "1_1") (pintype "passive"))
      (node (ref "R448") (pin "2") (pinfunction "2_2") (pintype "passive"))
      (node (ref "R45") (pin "1") (pinfunction "1_1") (pintype "passive"))
      (node (ref "R452") (pin "2") (pinfunction "2_2") (pintype "passive"))
      (node (ref "R453") (pin "2") (pinfunction "2_2") (pintype "passive"))
      (node (ref "R454") (pin "1") (pinfunction "1_1") (pintype "passive"))
      (node (ref "R46") (pin "1") (pinfunction "1_1") (pintype "passive"))
      (node (ref "R467") (pin "1") (pinfunction "1_1") (pintype "passive"))
      (node (ref "R473") (pin "1") (pinfunction "1_1") (pintype "passive"))
      (node (ref "R477") (pin "1") (pinfunction "1_1") (pintype "passive"))
      (node (ref "R478") (pin "2") (pinfunction "2_2") (pintype "passive"))
      (node (ref "R487") (pin "2") (pinfunction "2_2") (pintype "passive"))
      (node (ref "R489") (pin "1") (pinfunction "1_1") (pintype "passive"))
      (node (ref "R490") (pin "1") (pinfunction "1_1") (pintype "passive"))
      (node (ref "R498") (pin "1") (pinfunction "1_1") (pintype "passive"))
      (node (ref "R499") (pin "2") (pinfunction "2_2") (pintype "passive"))
      (node (ref "R5") (pin "2") (pinfunction "2_2") (pintype "passive"))
      (node (ref "R503") (pin "2") (pinfunction "2_2") (pintype "passive"))
      (node (ref "R504") (pin "2") (pinfunction "2_2") (pintype "passive"))
      (node (ref "R505") (pin "1") (pinfunction "1_1") (pintype "passive"))
      (node (ref "R518") (pin "1") (pinfunction "1_1") (pintype "passive"))
      (node (ref "R524") (pin "1") (pinfunction "1_1") (pintype "passive"))
      (node (ref "R528") (pin "1") (pinfunction "1_1") (pintype "passive"))
      (node (ref "R529") (pin "2") (pinfunction "2_2") (pintype "passive"))
      (node (ref "R538") (pin "2") (pinfunction "2_2") (pintype "passive"))
      (node (ref "R54") (pin "1") (pinfunction "1_1") (pintype "passive"))
      (node (ref "R540") (pin "1") (pinfunction "1_1") (pintype "passive"))
      (node (ref "R541") (pin "1") (pinfunction "1_1") (pintype "passive"))
      (node (ref "R549") (pin "1") (pinfunction "1_1") (pintype "passive"))
      (node (ref "R55") (pin "2") (pinfunction "2_2") (pintype "passive"))
      (node (ref "R550") (pin "2") (pinfunction "2_2") (pintype "passive"))
      (node (ref "R554") (pin "2") (pinfunction "2_2") (pintype "passive"))
      (node (ref "R555") (pin "2") (pinfunction "2_2") (pintype "passive"))
      (node (ref "R556") (pin "1") (pinfunction "1_1") (pintype "passive"))
      (node (ref "R569") (pin "1") (pinfunction "1_1") (pintype "passive"))
      (node (ref "R575") (pin "1") (pinfunction "1_1") (pintype "passive"))
      (node (ref "R579") (pin "1") (pinfunction "1_1") (pintype "passive"))
      (node (ref "R580") (pin "2") (pinfunction "2_2") (pintype "passive"))
      (node (ref "R589") (pin "2") (pinfunction "2_2") (pintype "passive"))
      (node (ref "R59") (pin "2") (pinfunction "2_2") (pintype "passive"))
      (node (ref "R591") (pin "1") (pinfunction "1_1") (pintype "passive"))
      (node (ref "R592") (pin "1") (pinfunction "1_1") (pintype "passive"))
      (node (ref "R6") (pin "2") (pinfunction "2_2") (pintype "passive"))
      (node (ref "R60") (pin "2") (pinfunction "2_2") (pintype "passive"))
      (node (ref "R600") (pin "1") (pinfunction "1_1") (pintype "passive"))
      (node (ref "R601") (pin "2") (pinfunction "2_2") (pintype "passive"))
      (node (ref "R605") (pin "2") (pinfunction "2_2") (pintype "passive"))
      (node (ref "R606") (pin "2") (pinfunction "2_2") (pintype "passive"))
      (node (ref "R607") (pin "1") (pinfunction "1_1") (pintype "passive"))
      (node (ref "R61") (pin "1") (pinfunction "1_1") (pintype "passive"))
      (node (ref "R74") (pin "1") (pinfunction "1_1") (pintype "passive"))
      (node (ref "R80") (pin "1") (pinfunction "1_1") (pintype "passive"))
      (node (ref "R84") (pin "1") (pinfunction "1_1") (pintype "passive"))
      (node (ref "R85") (pin "2") (pinfunction "2_2") (pintype "passive"))
      (node (ref "R97") (pin "2") (pinfunction "2_2") (pintype "passive"))
      (node (ref "R98") (pin "1") (pinfunction "1_1") (pintype "passive"))
      (node (ref "X1") (pin "13") (pinfunction "13_13") (pintype "passive"))
      (node (ref "X1") (pin "18") (pinfunction "18_18") (pintype "passive"))
      (node (ref "X1") (pin "23") (pinfunction "23_23") (pintype "passive"))
      (node (ref "X10") (pin "13") (pinfunction "13_13") (pintype "passive"))
      (node (ref "X10") (pin "18") (pinfunction "18_18") (pintype "passive"))
      (node (ref "X10") (pin "23") (pinfunction "23_23") (pintype "passive"))
      (node (ref "X101") (pin "13") (pinfunction "13_13") (pintype "passive"))
      (node (ref "X101") (pin "18") (pinfunction "18_18") (pintype "passive"))
      (node (ref "X101") (pin "23") (pinfunction "23_23") (pintype "passive"))
      (node (ref "X102") (pin "1") (pinfunction "S_1") (pintype "passive"))
      (node (ref "X103") (pin "5") (pinfunction "S_5") (pintype "passive"))
      (node (ref "X11") (pin "5") (pinfunction "S_5") (pintype "passive"))
      (node (ref "X12") (pin "1") (pinfunction "S_1") (pintype "passive"))
      (node (ref "X13") (pin "13") (pinfunction "13_13") (pintype "passive"))
      (node (ref "X13") (pin "18") (pinfunction "18_18") (pintype "passive"))
      (node (ref "X13") (pin "23") (pinfunction "23_23") (pintype "passive"))
      (node (ref "X14") (pin "5") (pinfunction "S_5") (pintype "passive"))
      (node (ref "X15") (pin "1") (pinfunction "S_1") (pintype "passive"))
      (node (ref "X16") (pin "13") (pinfunction "13_13") (pintype "passive"))
      (node (ref "X16") (pin "18") (pinfunction "18_18") (pintype "passive"))
      (node (ref "X16") (pin "23") (pinfunction "23_23") (pintype "passive"))
      (node (ref "X17") (pin "5") (pinfunction "S_5") (pintype "passive"))
      (node (ref "X18") (pin "1") (pinfunction "S_1") (pintype "passive"))
      (node (ref "X19") (pin "13") (pinfunction "13_13") (pintype "passive"))
      (node (ref "X19") (pin "18") (pinfunction "18_18") (pintype "passive"))
      (node (ref "X19") (pin "23") (pinfunction "23_23") (pintype "passive"))
      (node (ref "X2") (pin "5") (pinfunction "S_5") (pintype "passive"))
      (node (ref "X20") (pin "5") (pinfunction "S_5") (pintype "passive"))
      (node (ref "X21") (pin "1") (pinfunction "S_1") (pintype "passive"))
      (node (ref "X22") (pin "13") (pinfunction "13_13") (pintype "passive"))
      (node (ref "X22") (pin "18") (pinfunction "18_18") (pintype "passive"))
      (node (ref "X22") (pin "23") (pinfunction "23_23") (pintype "passive"))
      (node (ref "X23") (pin "5") (pinfunction "S_5") (pintype "passive"))
      (node (ref "X24") (pin "1") (pinfunction "S_1") (pintype "passive"))
      (node (ref "X25") (pin "13") (pinfunction "13_13") (pintype "passive"))
      (node (ref "X25") (pin "18") (pinfunction "18_18") (pintype "passive"))
      (node (ref "X25") (pin "23") (pinfunction "23_23") (pintype "passive"))
      (node (ref "X26") (pin "5") (pinfunction "S_5") (pintype "passive"))
      (node (ref "X27") (pin "1") (pinfunction "S_1") (pintype "passive"))
      (node (ref "X28") (pin "13") (pinfunction "13_13") (pintype "passive"))
      (node (ref "X28") (pin "18") (pinfunction "18_18") (pintype "passive"))
      (node (ref "X28") (pin "23") (pinfunction "23_23") (pintype "passive"))
      (node (ref "X29") (pin "5") (pinfunction "S_5") (pintype "passive"))
      (node (ref "X3") (pin "1") (pinfunction "S_1") (pintype "passive"))
      (node (ref "X30") (pin "1") (pinfunction "S_1") (pintype "passive"))
      (node (ref "X31") (pin "13") (pinfunction "13_13") (pintype "passive"))
      (node (ref "X31") (pin "18") (pinfunction "18_18") (pintype "passive"))
      (node (ref "X31") (pin "23") (pinfunction "23_23") (pintype "passive"))
      (node (ref "X32") (pin "5") (pinfunction "S_5") (pintype "passive"))
      (node (ref "X33") (pin "1") (pinfunction "S_1") (pintype "passive"))
      (node (ref "X4") (pin "13") (pinfunction "13_13") (pintype "passive"))
      (node (ref "X4") (pin "18") (pinfunction "18_18") (pintype "passive"))
      (node (ref "X4") (pin "23") (pinfunction "23_23") (pintype "passive"))
      (node (ref "X5") (pin "5") (pinfunction "S_5") (pintype "passive"))
      (node (ref "X6") (pin "1") (pinfunction "S_1") (pintype "passive"))
      (node (ref "X7") (pin "13") (pinfunction "13_13") (pintype "passive"))
      (node (ref "X7") (pin "18") (pinfunction "18_18") (pintype "passive"))
      (node (ref "X7") (pin "23") (pinfunction "23_23") (pintype "passive"))
      (node (ref "X8") (pin "5") (pinfunction "S_5") (pintype "passive"))
      (node (ref "X9") (pin "1") (pinfunction "S_1") (pintype "passive"))
    )
    (net (code "4") (name "Net-(1A-KL)") (class "Default")
      (node (ref "1") (pin "1") (pinfunction "KL_1") (pintype "passive"))
      (node (ref "D2") (pin "2") (pinfunction "-_2") (pintype "passive"))
      (node (ref "TP1") (pin "TP") (pinfunction "PP_TP") (pintype "input"))
    )
    (net (code "5") (name "Net-(1B-KL)") (class "Default")
      (node (ref "1") (pin "10") (pinfunction "KL_10") (pintype "passive"))
      (node (ref "D102") (pin "2") (pinfunction "-_2") (pintype "passive"))
      (node (ref "D103") (pin "2") (pinfunction "-_2") (pintype "passive"))
      (node (ref "JP104") (pin "1") (pinfunction "1_1") (pintype "passive"))
      (node (ref "TP10") (pin "TP") (pinfunction "PP_TP") (pintype "input"))
    )
    (net (code "6") (name "Net-(1C-KL)") (class "Default")
      (node (ref "1") (pin "11") (pinfunction "KL_11") (pintype "passive"))
      (node (ref "D103") (pin "1") (pinfunction "+_1") (pintype "passive"))
      (node (ref "TP11") (pin "TP") (pinfunction "PP_TP") (pintype "input"))
      (node (ref "X101") (pin "19") (pinfunction "19_19") (pintype "passive"))
    )
    (net (code "7") (name "Net-(1E-KL)") (class "Default")
      (node (ref "1") (pin "2") (pinfunction "KL_2") (pintype "passive"))
      (node (ref "Q101") (pin "2") (pinfunction "C_2") (pintype "passive"))
      (node (ref "TP2") (pin "TP") (pinfunction "PP_TP") (pintype "input"))
    )
    (net (code "8") (name "Net-(1F-KL)") (class "Default")
      (node (ref "1") (pin "3") (pinfunction "KL_3") (pintype "passive"))
      (node (ref "IC107") (pin "11") (pinfunction "O6_11") (pintype "open_collector"))
      (node (ref "TP3") (pin "TP") (pinfunction "PP_TP") (pintype "input"))
    )
    (net (code "9") (name "Net-(1G-KL)") (class "Default")
      (node (ref "1") (pin "4") (pinfunction "KL_4") (pintype "passive"))
      (node (ref "IC107") (pin "10") (pinfunction "O7_10") (pintype "open_collector"))
      (node (ref "TP4") (pin "TP") (pinfunction "PP_TP") (pintype "input"))
    )
    (net (code "10") (name "Net-(1H-KL)") (class "Default")
      (node (ref "1") (pin "5") (pinfunction "KL_5") (pintype "passive"))
      (node (ref "IC107") (pin "12") (pinfunction "O5_12") (pintype "open_collector"))
      (node (ref "TP5") (pin "TP") (pinfunction "PP_TP") (pintype "input"))
    )
    (net (code "11") (name "Net-(1I-KL)") (class "Default")
      (node (ref "1") (pin "6") (pinfunction "KL_6") (pintype "passive"))
      (node (ref "IC107") (pin "13") (pinfunction "O4_13") (pintype "open_collector"))
      (node (ref "TP6") (pin "TP") (pinfunction "PP_TP") (pintype "input"))
    )
    (net (code "12") (name "Net-(1J-KL)") (class "Default")
      (node (ref "1") (pin "7") (pinfunction "KL_7") (pintype "passive"))
      (node (ref "IC107") (pin "14") (pinfunction "O3_14") (pintype "open_collector"))
      (node (ref "TP7") (pin "TP") (pinfunction "PP_TP") (pintype "input"))
    )
    (net (code "13") (name "Net-(1K-KL)") (class "Default")
      (node (ref "1") (pin "8") (pinfunction "KL_8") (pintype "passive"))
      (node (ref "R9") (pin "2") (pinfunction "2_2") (pintype "passive"))
      (node (ref "TP8") (pin "TP") (pinfunction "PP_TP") (pintype "input"))
    )
    (net (code "14") (name "Net-(1L-KL)") (class "Default")
      (node (ref "1") (pin "9") (pinfunction "KL_9") (pintype "passive"))
      (node (ref "D102") (pin "1") (pinfunction "+_1") (pintype "passive"))
      (node (ref "TP9") (pin "TP") (pinfunction "PP_TP") (pintype "input"))
      (node (ref "X101") (pin "17") (pinfunction "17_17") (pintype "passive"))
    )
    (net (code "15") (name "Net-(2B-KL)") (class "Default")
      (node (ref "2") (pin "10") (pinfunction "KL_10") (pintype "passive"))
      (node (ref "TP25") (pin "TP") (pinfunction "PP_TP") (pintype "input"))
      (node (ref "X101") (pin "15") (pinfunction "15_15") (pintype "passive"))
    )
    (net (code "16") (name "Net-(2C-KL)") (class "Default")
      (node (ref "2") (pin "11") (pinfunction "KL_11") (pintype "passive"))
      (node (ref "Q103") (pin "2") (pinfunction "C_2") (pintype "passive"))
      (node (ref "R119") (pin "1") (pinfunction "1_1") (pintype "passive"))
      (node (ref "TP26") (pin "TP") (pinfunction "PP_TP") (pintype "input"))
    )
    (net (code "17") (name "Net-(2D-KL)") (class "Default")
      (node (ref "2") (pin "12") (pinfunction "KL_12") (pintype "passive"))
      (node (ref "R146") (pin "1") (pinfunction "1_1") (pintype "passive"))
      (node (ref "TP13") (pin "TP") (pinfunction "PP_TP") (pintype "input"))
    )
    (net (code "18") (name "Net-(2E-KL)") (class "Default")
      (node (ref "2") (pin "2") (pinfunction "KL_2") (pintype "passive"))
      (node (ref "D109") (pin "2") (pinfunction "-_2") (pintype "passive"))
      (node (ref "LED102") (pin "K") (pinfunction "C_K") (pintype "passive"))
      (node (ref "TP16") (pin "TP") (pinfunction "PP_TP") (pintype "input"))
      (node (ref "X101") (pin "12") (pinfunction "12_12") (pintype "passive"))
    )
    (net (code "19") (name "Net-(2F-KL)") (class "Default")
      (node (ref "2") (pin "3") (pinfunction "KL_3") (pintype "passive"))
      (node (ref "D108") (pin "2") (pinfunction "-_2") (pintype "passive"))
      (node (ref "LED103") (pin "K") (pinfunction "C_K") (pintype "passive"))
      (node (ref "TP17") (pin "TP") (pinfunction "PP_TP") (pintype "input"))
      (node (ref "X101") (pin "11") (pinfunction "11_11") (pintype "passive"))
    )
    (net (code "20") (name "Net-(2G-KL)") (class "Default")
      (node (ref "2") (pin "4") (pinfunction "KL_4") (pintype "passive"))
      (node (ref "D107") (pin "2") (pinfunction "-_2") (pintype "passive"))
      (node (ref "LED104") (pin "K") (pinfunction "C_K") (pintype "passive"))
      (node (ref "TP18") (pin "TP") (pinfunction "PP_TP") (pintype "input"))
      (node (ref "X101") (pin "10") (pinfunction "10_10") (pintype "passive"))
    )
    (net (code "21") (name "Net-(2H-KL)") (class "Default")
      (node (ref "2") (pin "5") (pinfunction "KL_5") (pintype "passive"))
      (node (ref "D106") (pin "2") (pinfunction "-_2") (pintype "passive"))
      (node (ref "LED105") (pin "K") (pinfunction "C_K") (pintype "passive"))
      (node (ref "TP19") (pin "TP") (pinfunction "PP_TP") (pintype "input"))
      (node (ref "X101") (pin "9") (pinfunction "9_9") (pintype "passive"))
    )
    (net (code "22") (name "Net-(2I-KL)") (class "Default")
      (node (ref "2") (pin "6") (pinfunction "KL_6") (pintype "passive"))
      (node (ref "JP105") (pin "2") (pinfunction "2_2") (pintype "passive"))
      (node (ref "TP21") (pin "TP") (pinfunction "PP_TP") (pintype "input"))
    )
    (net (code "23") (name "Net-(2J-KL)") (class "Default")
      (node (ref "2") (pin "7") (pinfunction "KL_7") (pintype "passive"))
      (node (ref "LED101") (pin "A") (pinfunction "A_A") (pintype "passive"))
      (node (ref "TP22") (pin "TP") (pinfunction "PP_TP") (pintype "input"))
      (node (ref "X101") (pin "8") (pinfunction "8_8") (pintype "passive"))
    )
    (net (code "24") (name "Net-(2K-KL)") (class "Default")
      (node (ref "2") (pin "8") (pinfunction "KL_8") (pintype "passive"))
      (node (ref "D110") (pin "2") (pinfunction "-_2") (pintype "passive"))
      (node (ref "LED106") (pin "K") (pinfunction "C_K") (pintype "passive"))
      (node (ref "TP23") (pin "TP") (pinfunction "PP_TP") (pintype "input"))
      (node (ref "X101") (pin "14") (pinfunction "14_14") (pintype "passive"))
    )
    (net (code "25") (name "Net-(2L-KL)") (class "Default")
      (node (ref "2") (pin "9") (pinfunction "KL_9") (pintype "passive"))
      (node (ref "D107") (pin "1") (pinfunction "+_1") (pintype "passive"))
      (node (ref "D108") (pin "1") (pinfunction "+_1") (pintype "passive"))
      (node (ref "JP102") (pin "1") (pinfunction "1_1") (pintype "passive"))
      (node (ref "JP103") (pin "2") (pinfunction "2_2") (pintype "passive"))
      (node (ref "TP24") (pin "TP") (pinfunction "PP_TP") (pintype "input"))
    )
    (net (code "26") (name "Net-(3A-KL)") (class "Default")
      (node (ref "3") (pin "1") (pinfunction "KL_1") (pintype "passive"))
      (node (ref "D16") (pin "2") (pinfunction "-_2") (pintype "passive"))
      (node (ref "TP14") (pin "TP") (pinfunction "PP_TP") (pintype "input"))
    )
    (net (code "27") (name "Net-(3B-KL)") (class "Default")
      (node (ref "3") (pin "10") (pinfunction "KL_10") (pintype "passive"))
      (node (ref "D3") (pin "2") (pinfunction "-_2") (pintype "passive"))
      (node (ref "D5") (pin "2") (pinfunction "-_2") (pintype "passive"))
      (node (ref "JP5") (pin "1") (pinfunction "1_1") (pintype "passive"))
      (node (ref "TP33") (pin "TP") (pinfunction "PP_TP") (pintype "input"))
    )
    (net (code "28") (name "Net-(3C-KL)") (class "Default")
      (node (ref "3") (pin "11") (pinfunction "KL_11") (pintype "passive"))
      (node (ref "D5") (pin "1") (pinfunction "+_1") (pintype "passive"))
      (node (ref "TP34") (pin "TP") (pinfunction "PP_TP") (pintype "input"))
      (node (ref "X1") (pin "19") (pinfunction "19_19") (pintype "passive"))
    )
    (net (code "29") (name "Net-(3E-KL)") (class "Default")
      (node (ref "3") (pin "2") (pinfunction "KL_2") (pintype "passive"))
      (node (ref "Q6") (pin "2") (pinfunction "C_2") (pintype "passive"))
      (node (ref "TP15") (pin "TP") (pinfunction "PP_TP") (pintype "input"))
    )
    (net (code "30") (name "Net-(3F-KL)") (class "Default")
      (node (ref "3") (pin "3") (pinfunction "KL_3") (pintype "passive"))
      (node (ref "IC3") (pin "11") (pinfunction "O6_11") (pintype "open_collector"))
      (node (ref "TP20") (pin "TP") (pinfunction "PP_TP") (pintype "input"))
    )
    (net (code "31") (name "Net-(3G-KL)") (class "Default")
      (node (ref "3") (pin "4") (pinfunction "KL_4") (pintype "passive"))
      (node (ref "IC3") (pin "10") (pinfunction "O7_10") (pintype "open_collector"))
      (node (ref "TP27") (pin "TP") (pinfunction "PP_TP") (pintype "input"))
    )
    (net (code "32") (name "Net-(3H-KL)") (class "Default")
      (node (ref "3") (pin "5") (pinfunction "KL_5") (pintype "passive"))
      (node (ref "IC3") (pin "12") (pinfunction "O5_12") (pintype "open_collector"))
      (node (ref "TP28") (pin "TP") (pinfunction "PP_TP") (pintype "input"))
    )
    (net (code "33") (name "Net-(3I-KL)") (class "Default")
      (node (ref "3") (pin "6") (pinfunction "KL_6") (pintype "passive"))
      (node (ref "IC3") (pin "13") (pinfunction "O4_13") (pintype "open_collector"))
      (node (ref "TP29") (pin "TP") (pinfunction "PP_TP") (pintype "input"))
    )
    (net (code "34") (name "Net-(3J-KL)") (class "Default")
      (node (ref "3") (pin "7") (pinfunction "KL_7") (pintype "passive"))
      (node (ref "IC3") (pin "14") (pinfunction "O3_14") (pintype "open_collector"))
      (node (ref "TP30") (pin "TP") (pinfunction "PP_TP") (pintype "input"))
    )
    (net (code "35") (name "Net-(3K-KL)") (class "Default")
      (node (ref "3") (pin "8") (pinfunction "KL_8") (pintype "passive"))
      (node (ref "R62") (pin "2") (pinfunction "2_2") (pintype "passive"))
      (node (ref "TP31") (pin "TP") (pinfunction "PP_TP") (pintype "input"))
    )
    (net (code "36") (name "Net-(3L-KL)") (class "Default")
      (node (ref "3") (pin "9") (pinfunction "KL_9") (pintype "passive"))
      (node (ref "D3") (pin "1") (pinfunction "+_1") (pintype "passive"))
      (node (ref "TP32") (pin "TP") (pinfunction "PP_TP") (pintype "input"))
      (node (ref "X1") (pin "17") (pinfunction "17_17") (pintype "passive"))
    )
    (net (code "37") (name "Net-(4B-KL)") (class "Default")
      (node (ref "4") (pin "10") (pinfunction "KL_10") (pintype "passive"))
      (node (ref "TP43") (pin "TP") (pinfunction "PP_TP") (pintype "input"))
      (node (ref "X1") (pin "15") (pinfunction "15_15") (pintype "passive"))
    )
    (net (code "38") (name "Net-(4C-KL)") (class "Default")
      (node (ref "4") (pin "11") (pinfunction "KL_11") (pintype "passive"))
      (node (ref "Q8") (pin "2") (pinfunction "C_2") (pintype "passive"))
      (node (ref "R48") (pin "1") (pinfunction "1_1") (pintype "passive"))
      (node (ref "TP44") (pin "TP") (pinfunction "PP_TP") (pintype "input"))
    )
    (net (code "39") (name "Net-(4D-KL)") (class "Default")
      (node (ref "4") (pin "12") (pinfunction "KL_12") (pintype "passive"))
      (node (ref "R49") (pin "1") (pinfunction "1_1") (pintype "passive"))
      (node (ref "TP46") (pin "TP") (pinfunction "PP_TP") (pintype "input"))
    )
    (net (code "40") (name "Net-(4E-KL)") (class "Default")
      (node (ref "4") (pin "2") (pinfunction "KL_2") (pintype "passive"))
      (node (ref "D9") (pin "2") (pinfunction "-_2") (pintype "passive"))
      (node (ref "LED1") (pin "K") (pinfunction "C_K") (pintype "passive"))
      (node (ref "TP35") (pin "TP") (pinfunction "PP_TP") (pintype "input"))
      (node (ref "X1") (pin "12") (pinfunction "12_12") (pintype "passive"))
    )
    (net (code "41") (name "Net-(4F-KL)") (class "Default")
      (node (ref "4") (pin "3") (pinfunction "KL_3") (pintype "passive"))
      (node (ref "D8") (pin "2") (pinfunction "-_2") (pintype "passive"))
      (node (ref "LED2") (pin "K") (pinfunction "C_K") (pintype "passive"))
      (node (ref "TP36") (pin "TP") (pinfunction "PP_TP") (pintype "input"))
      (node (ref "X1") (pin "11") (pinfunction "11_11") (pintype "passive"))
    )
    (net (code "42") (name "Net-(4G-KL)") (class "Default")
      (node (ref "4") (pin "4") (pinfunction "KL_4") (pintype "passive"))
      (node (ref "D7") (pin "2") (pinfunction "-_2") (pintype "passive"))
      (node (ref "LED3") (pin "K") (pinfunction "C_K") (pintype "passive"))
      (node (ref "TP37") (pin "TP") (pinfunction "PP_TP") (pintype "input"))
      (node (ref "X1") (pin "10") (pinfunction "10_10") (pintype "passive"))
    )
    (net (code "43") (name "Net-(4H-KL)") (class "Default")
      (node (ref "4") (pin "5") (pinfunction "KL_5") (pintype "passive"))
      (node (ref "D6") (pin "2") (pinfunction "-_2") (pintype "passive"))
      (node (ref "LED4") (pin "K") (pinfunction "C_K") (pintype "passive"))
      (node (ref "TP38") (pin "TP") (pinfunction "PP_TP") (pintype "input"))
      (node (ref "X1") (pin "9") (pinfunction "9_9") (pintype "passive"))
    )
    (net (code "44") (name "Net-(4I-KL)") (class "Default")
      (node (ref "4") (pin "6") (pinfunction "KL_6") (pintype "passive"))
      (node (ref "JP2") (pin "2") (pinfunction "2_2") (pintype "passive"))
      (node (ref "TP39") (pin "TP") (pinfunction "PP_TP") (pintype "input"))
    )
    (net (code "45") (name "Net-(4J-KL)") (class "Default")
      (node (ref "4") (pin "7") (pinfunction "KL_7") (pintype "passive"))
      (node (ref "LED5") (pin "A") (pinfunction "A_A") (pintype "passive"))
      (node (ref "TP40") (pin "TP") (pinfunction "PP_TP") (pintype "input"))
      (node (ref "X1") (pin "8") (pinfunction "8_8") (pintype "passive"))
    )
    (net (code "46") (name "Net-(4K-KL)") (class "Default")
      (node (ref "4") (pin "8") (pinfunction "KL_8") (pintype "passive"))
      (node (ref "D10") (pin "2") (pinfunction "-_2") (pintype "passive"))
      (node (ref "LED6") (pin "K") (pinfunction "C_K") (pintype "passive"))
      (node (ref "TP41") (pin "TP") (pinfunction "PP_TP") (pintype "input"))
      (node (ref "X1") (pin "14") (pinfunction "14_14") (pintype "passive"))
    )
    (net (code "47") (name "Net-(4L-KL)") (class "Default")
      (node (ref "4") (pin "9") (pinfunction "KL_9") (pintype "passive"))
      (node (ref "D7") (pin "1") (pinfunction "+_1") (pintype "passive"))
      (node (ref "D8") (pin "1") (pinfunction "+_1") (pintype "passive"))
      (node (ref "JP3") (pin "1") (pinfunction "1_1") (pintype "passive"))
      (node (ref "JP4") (pin "2") (pinfunction "2_2") (pintype "passive"))
      (node (ref "TP42") (pin "TP") (pinfunction "PP_TP") (pintype "input"))
    )
    (net (code "48") (name "Net-(5A-KL)") (class "Default")
      (node (ref "5") (pin "1") (pinfunction "KL_1") (pintype "passive"))
      (node (ref "D30") (pin "2") (pinfunction "-_2") (pintype "passive"))
      (node (ref "TP47") (pin "TP") (pinfunction "PP_TP") (pintype "input"))
    )
    (net (code "49") (name "Net-(5B-KL)") (class "Default")
      (node (ref "5") (pin "10") (pinfunction "KL_10") (pintype "passive"))
      (node (ref "D18") (pin "2") (pinfunction "-_2") (pintype "passive"))
      (node (ref "D19") (pin "2") (pinfunction "-_2") (pintype "passive"))
      (node (ref "JP10") (pin "1") (pinfunction "1_1") (pintype "passive"))
      (node (ref "TP56") (pin "TP") (pinfunction "PP_TP") (pintype "input"))
    )
    (net (code "50") (name "Net-(5C-KL)") (class "Default")
      (node (ref "5") (pin "11") (pinfunction "KL_11") (pintype "passive"))
      (node (ref "D19") (pin "1") (pinfunction "+_1") (pintype "passive"))
      (node (ref "TP57") (pin "TP") (pinfunction "PP_TP") (pintype "input"))
      (node (ref "X4") (pin "19") (pinfunction "19_19") (pintype "passive"))
    )
    (net (code "51") (name "Net-(5E-KL)") (class "Default")
      (node (ref "5") (pin "2") (pinfunction "KL_2") (pintype "passive"))
      (node (ref "Q16") (pin "2") (pinfunction "C_2") (pintype "passive"))
      (node (ref "TP48") (pin "TP") (pinfunction "PP_TP") (pintype "input"))
    )
    (net (code "52") (name "Net-(5F-KL)") (class "Default")
      (node (ref "5") (pin "3") (pinfunction "KL_3") (pintype "passive"))
      (node (ref "IC12") (pin "11") (pinfunction "O6_11") (pintype "open_collector"))
      (node (ref "TP49") (pin "TP") (pinfunction "PP_TP") (pintype "input"))
    )
    (net (code "53") (name "Net-(5G-KL)") (class "Default")
      (node (ref "5") (pin "4") (pinfunction "KL_4") (pintype "passive"))
      (node (ref "IC12") (pin "10") (pinfunction "O7_10") (pintype "open_collector"))
      (node (ref "TP50") (pin "TP") (pinfunction "PP_TP") (pintype "input"))
    )
    (net (code "54") (name "Net-(5H-KL)") (class "Default")
      (node (ref "5") (pin "5") (pinfunction "KL_5") (pintype "passive"))
      (node (ref "IC12") (pin "12") (pinfunction "O5_12") (pintype "open_collector"))
      (node (ref "TP51") (pin "TP") (pinfunction "PP_TP") (pintype "input"))
    )
    (net (code "55") (name "Net-(5I-KL)") (class "Default")
      (node (ref "5") (pin "6") (pinfunction "KL_6") (pintype "passive"))
      (node (ref "IC12") (pin "13") (pinfunction "O4_13") (pintype "open_collector"))
      (node (ref "TP52") (pin "TP") (pinfunction "PP_TP") (pintype "input"))
    )
    (net (code "56") (name "Net-(5J-KL)") (class "Default")
      (node (ref "5") (pin "7") (pinfunction "KL_7") (pintype "passive"))
      (node (ref "IC12") (pin "14") (pinfunction "O3_14") (pintype "open_collector"))
      (node (ref "TP53") (pin "TP") (pinfunction "PP_TP") (pintype "input"))
    )
    (net (code "57") (name "Net-(5K-KL)") (class "Default")
      (node (ref "5") (pin "8") (pinfunction "KL_8") (pintype "passive"))
      (node (ref "R161") (pin "2") (pinfunction "2_2") (pintype "passive"))
      (node (ref "TP54") (pin "TP") (pinfunction "PP_TP") (pintype "input"))
    )
    (net (code "58") (name "Net-(5L-KL)") (class "Default")
      (node (ref "5") (pin "9") (pinfunction "KL_9") (pintype "passive"))
      (node (ref "D18") (pin "1") (pinfunction "+_1") (pintype "passive"))
      (node (ref "TP55") (pin "TP") (pinfunction "PP_TP") (pintype "input"))
      (node (ref "X4") (pin "17") (pinfunction "17_17") (pintype "passive"))
    )
    (net (code "59") (name "Net-(6B-KL)") (class "Default")
      (node (ref "6") (pin "10") (pinfunction "KL_10") (pintype "passive"))
      (node (ref "TP66") (pin "TP") (pinfunction "PP_TP") (pintype "input"))
      (node (ref "X4") (pin "15") (pinfunction "15_15") (pintype "passive"))
    )
    (net (code "60") (name "Net-(6C-KL)") (class "Default")
      (node (ref "6") (pin "11") (pinfunction "KL_11") (pintype "passive"))
      (node (ref "Q18") (pin "2") (pinfunction "C_2") (pintype "passive"))
      (node (ref "R147") (pin "1") (pinfunction "1_1") (pintype "passive"))
      (node (ref "TP67") (pin "TP") (pinfunction "PP_TP") (pintype "input"))
    )
    (net (code "61") (name "Net-(6D-KL)") (class "Default")
      (node (ref "6") (pin "12") (pinfunction "KL_12") (pintype "passive"))
      (node (ref "R148") (pin "1") (pinfunction "1_1") (pintype "passive"))
      (node (ref "TP69") (pin "TP") (pinfunction "PP_TP") (pintype "input"))
    )
    (net (code "62") (name "Net-(6E-KL)") (class "Default")
      (node (ref "6") (pin "2") (pinfunction "KL_2") (pintype "passive"))
      (node (ref "D23") (pin "2") (pinfunction "-_2") (pintype "passive"))
      (node (ref "LED7") (pin "K") (pinfunction "C_K") (pintype "passive"))
      (node (ref "TP58") (pin "TP") (pinfunction "PP_TP") (pintype "input"))
      (node (ref "X4") (pin "12") (pinfunction "12_12") (pintype "passive"))
    )
    (net (code "63") (name "Net-(6F-KL)") (class "Default")
      (node (ref "6") (pin "3") (pinfunction "KL_3") (pintype "passive"))
      (node (ref "D22") (pin "2") (pinfunction "-_2") (pintype "passive"))
      (node (ref "LED8") (pin "K") (pinfunction "C_K") (pintype "passive"))
      (node (ref "TP59") (pin "TP") (pinfunction "PP_TP") (pintype "input"))
      (node (ref "X4") (pin "11") (pinfunction "11_11") (pintype "passive"))
    )
    (net (code "64") (name "Net-(6G-KL)") (class "Default")
      (node (ref "6") (pin "4") (pinfunction "KL_4") (pintype "passive"))
      (node (ref "D21") (pin "2") (pinfunction "-_2") (pintype "passive"))
      (node (ref "LED9") (pin "K") (pinfunction "C_K") (pintype "passive"))
      (node (ref "TP60") (pin "TP") (pinfunction "PP_TP") (pintype "input"))
      (node (ref "X4") (pin "10") (pinfunction "10_10") (pintype "passive"))
    )
    (net (code "65") (name "Net-(6H-KL)") (class "Default")
      (node (ref "6") (pin "5") (pinfunction "KL_5") (pintype "passive"))
      (node (ref "D20") (pin "2") (pinfunction "-_2") (pintype "passive"))
      (node (ref "LED10") (pin "K") (pinfunction "C_K") (pintype "passive"))
      (node (ref "TP61") (pin "TP") (pinfunction "PP_TP") (pintype "input"))
      (node (ref "X4") (pin "9") (pinfunction "9_9") (pintype "passive"))
    )
    (net (code "66") (name "Net-(6I-KL)") (class "Default")
      (node (ref "6") (pin "6") (pinfunction "KL_6") (pintype "passive"))
      (node (ref "JP7") (pin "2") (pinfunction "2_2") (pintype "passive"))
      (node (ref "TP62") (pin "TP") (pinfunction "PP_TP") (pintype "input"))
    )
    (net (code "67") (name "Net-(6J-KL)") (class "Default")
      (node (ref "6") (pin "7") (pinfunction "KL_7") (pintype "passive"))
      (node (ref "LED11") (pin "A") (pinfunction "A_A") (pintype "passive"))
      (node (ref "TP63") (pin "TP") (pinfunction "PP_TP") (pintype "input"))
      (node (ref "X4") (pin "8") (pinfunction "8_8") (pintype "passive"))
    )
    (net (code "68") (name "Net-(6K-KL)") (class "Default")
      (node (ref "6") (pin "8") (pinfunction "KL_8") (pintype "passive"))
      (node (ref "D24") (pin "2") (pinfunction "-_2") (pintype "passive"))
      (node (ref "LED12") (pin "K") (pinfunction "C_K") (pintype "passive"))
      (node (ref "TP64") (pin "TP") (pinfunction "PP_TP") (pintype "input"))
      (node (ref "X4") (pin "14") (pinfunction "14_14") (pintype "passive"))
    )
    (net (code "69") (name "Net-(6L-KL)") (class "Default")
      (node (ref "6") (pin "9") (pinfunction "KL_9") (pintype "passive"))
      (node (ref "D21") (pin "1") (pinfunction "+_1") (pintype "passive"))
      (node (ref "D22") (pin "1") (pinfunction "+_1") (pintype "passive"))
      (node (ref "JP8") (pin "1") (pinfunction "1_1") (pintype "passive"))
      (node (ref "JP9") (pin "2") (pinfunction "2_2") (pintype "passive"))
      (node (ref "TP65") (pin "TP") (pinfunction "PP_TP") (pintype "input"))
    )
    (net (code "70") (name "Net-(7A-KL)") (class "Default")
      (node (ref "7") (pin "1") (pinfunction "KL_1") (pintype "passive"))
      (node (ref "D44") (pin "2") (pinfunction "-_2") (pintype "passive"))
      (node (ref "TP70") (pin "TP") (pinfunction "PP_TP") (pintype "input"))
    )
    (net (code "71") (name "Net-(7B-KL)") (class "Default")
      (node (ref "7") (pin "10") (pinfunction "KL_10") (pintype "passive"))
      (node (ref "D32") (pin "2") (pinfunction "-_2") (pintype "passive"))
      (node (ref "D33") (pin "2") (pinfunction "-_2") (pintype "passive"))
      (node (ref "JP15") (pin "1") (pinfunction "1_1") (pintype "passive"))
      (node (ref "TP79") (pin "TP") (pinfunction "PP_TP") (pintype "input"))
    )
    (net (code "72") (name "Net-(7C-KL)") (class "Default")
      (node (ref "7") (pin "11") (pinfunction "KL_11") (pintype "passive"))
      (node (ref "D33") (pin "1") (pinfunction "+_1") (pintype "passive"))
      (node (ref "TP80") (pin "TP") (pinfunction "PP_TP") (pintype "input"))
      (node (ref "X7") (pin "19") (pinfunction "19_19") (pintype "passive"))
    )
    (net (code "73") (name "Net-(7E-KL)") (class "Default")
      (node (ref "7") (pin "2") (pinfunction "KL_2") (pintype "passive"))
      (node (ref "Q26") (pin "2") (pinfunction "C_2") (pintype "passive"))
      (node (ref "TP71") (pin "TP") (pinfunction "PP_TP") (pintype "input"))
    )
    (net (code "74") (name "Net-(7F-KL)") (class "Default")
      (node (ref "7") (pin "3") (pinfunction "KL_3") (pintype "passive"))
      (node (ref "IC21") (pin "11") (pinfunction "O6_11") (pintype "open_collector"))
      (node (ref "TP72") (pin "TP") (pinfunction "PP_TP") (pintype "input"))
    )
    (net (code "75") (name "Net-(7G-KL)") (class "Default")
      (node (ref "7") (pin "4") (pinfunction "KL_4") (pintype "passive"))
      (node (ref "IC21") (pin "10") (pinfunction "O7_10") (pintype "open_collector"))
      (node (ref "TP73") (pin "TP") (pinfunction "PP_TP") (pintype "input"))
    )
    (net (code "76") (name "Net-(7H-KL)") (class "Default")
      (node (ref "7") (pin "5") (pinfunction "KL_5") (pintype "passive"))
      (node (ref "IC21") (pin "12") (pinfunction "O5_12") (pintype "open_collector"))
      (node (ref "TP74") (pin "TP") (pinfunction "PP_TP") (pintype "input"))
    )
    (net (code "77") (name "Net-(7I-KL)") (class "Default")
      (node (ref "7") (pin "6") (pinfunction "KL_6") (pintype "passive"))
      (node (ref "IC21") (pin "13") (pinfunction "O4_13") (pintype "open_collector"))
      (node (ref "TP75") (pin "TP") (pinfunction "PP_TP") (pintype "input"))
    )
    (net (code "78") (name "Net-(7J-KL)") (class "Default")
      (node (ref "7") (pin "7") (pinfunction "KL_7") (pintype "passive"))
      (node (ref "IC21") (pin "14") (pinfunction "O3_14") (pintype "open_collector"))
      (node (ref "TP76") (pin "TP") (pinfunction "PP_TP") (pintype "input"))
    )
    (net (code "79") (name "Net-(7K-KL)") (class "Default")
      (node (ref "7") (pin "8") (pinfunction "KL_8") (pintype "passive"))
      (node (ref "R216") (pin "2") (pinfunction "2_2") (pintype "passive"))
      (node (ref "TP77") (pin "TP") (pinfunction "PP_TP") (pintype "input"))
    )
    (net (code "80") (name "Net-(7L-KL)") (class "Default")
      (node (ref "7") (pin "9") (pinfunction "KL_9") (pintype "passive"))
      (node (ref "D32") (pin "1") (pinfunction "+_1") (pintype "passive"))
      (node (ref "TP78") (pin "TP") (pinfunction "PP_TP") (pintype "input"))
      (node (ref "X7") (pin "17") (pinfunction "17_17") (pintype "passive"))
    )
    (net (code "81") (name "Net-(8B-KL)") (class "Default")
      (node (ref "8") (pin "10") (pinfunction "KL_10") (pintype "passive"))
      (node (ref "TP89") (pin "TP") (pinfunction "PP_TP") (pintype "input"))
      (node (ref "X7") (pin "15") (pinfunction "15_15") (pintype "passive"))
    )
    (net (code "82") (name "Net-(8C-KL)") (class "Default")
      (node (ref "8") (pin "11") (pinfunction "KL_11") (pintype "passive"))
      (node (ref "Q28") (pin "2") (pinfunction "C_2") (pintype "passive"))
      (node (ref "R202") (pin "1") (pinfunction "1_1") (pintype "passive"))
      (node (ref "TP90") (pin "TP") (pinfunction "PP_TP") (pintype "input"))
    )
    (net (code "83") (name "Net-(8D-KL)") (class "Default")
      (node (ref "8") (pin "12") (pinfunction "KL_12") (pintype "passive"))
      (node (ref "R203") (pin "1") (pinfunction "1_1") (pintype "passive"))
      (node (ref "TP92") (pin "TP") (pinfunction "PP_TP") (pintype "input"))
    )
    (net (code "84") (name "Net-(8E-KL)") (class "Default")
      (node (ref "8") (pin "2") (pinfunction "KL_2") (pintype "passive"))
      (node (ref "D37") (pin "2") (pinfunction "-_2") (pintype "passive"))
      (node (ref "LED13") (pin "K") (pinfunction "C_K") (pintype "passive"))
      (node (ref "TP81") (pin "TP") (pinfunction "PP_TP") (pintype "input"))
      (node (ref "X7") (pin "12") (pinfunction "12_12") (pintype "passive"))
    )
    (net (code "85") (name "Net-(8F-KL)") (class "Default")
      (node (ref "8") (pin "3") (pinfunction "KL_3") (pintype "passive"))
      (node (ref "D36") (pin "2") (pinfunction "-_2") (pintype "passive"))
      (node (ref "LED14") (pin "K") (pinfunction "C_K") (pintype "passive"))
      (node (ref "TP82") (pin "TP") (pinfunction "PP_TP") (pintype "input"))
      (node (ref "X7") (pin "11") (pinfunction "11_11") (pintype "passive"))
    )
    (net (code "86") (name "Net-(8G-KL)") (class "Default")
      (node (ref "8") (pin "4") (pinfunction "KL_4") (pintype "passive"))
      (node (ref "D35") (pin "2") (pinfunction "-_2") (pintype "passive"))
      (node (ref "LED15") (pin "K") (pinfunction "C_K") (pintype "passive"))
      (node (ref "TP83") (pin "TP") (pinfunction "PP_TP") (pintype "input"))
      (node (ref "X7") (pin "10") (pinfunction "10_10") (pintype "passive"))
    )
    (net (code "87") (name "Net-(8H-KL)") (class "Default")
      (node (ref "8") (pin "5") (pinfunction "KL_5") (pintype "passive"))
      (node (ref "D34") (pin "2") (pinfunction "-_2") (pintype "passive"))
      (node (ref "LED16") (pin "K") (pinfunction "C_K") (pintype "passive"))
      (node (ref "TP84") (pin "TP") (pinfunction "PP_TP") (pintype "input"))
      (node (ref "X7") (pin "9") (pinfunction "9_9") (pintype "passive"))
    )
    (net (code "88") (name "Net-(8I-KL)") (class "Default")
      (node (ref "8") (pin "6") (pinfunction "KL_6") (pintype "passive"))
      (node (ref "JP12") (pin "2") (pinfunction "2_2") (pintype "passive"))
      (node (ref "TP85") (pin "TP") (pinfunction "PP_TP") (pintype "input"))
    )
    (net (code "89") (name "Net-(8J-KL)") (class "Default")
      (node (ref "8") (pin "7") (pinfunction "KL_7") (pintype "passive"))
      (node (ref "LED17") (pin "A") (pinfunction "A_A") (pintype "passive"))
      (node (ref "TP86") (pin "TP") (pinfunction "PP_TP") (pintype "input"))
      (node (ref "X7") (pin "8") (pinfunction "8_8") (pintype "passive"))
    )
    (net (code "90") (name "Net-(8K-KL)") (class "Default")
      (node (ref "8") (pin "8") (pinfunction "KL_8") (pintype "passive"))
      (node (ref "D38") (pin "2") (pinfunction "-_2") (pintype "passive"))
      (node (ref "LED18") (pin "K") (pinfunction "C_K") (pintype "passive"))
      (node (ref "TP87") (pin "TP") (pinfunction "PP_TP") (pintype "input"))
      (node (ref "X7") (pin "14") (pinfunction "14_14") (pintype "passive"))
    )
    (net (code "91") (name "Net-(8L-KL)") (class "Default")
      (node (ref "8") (pin "9") (pinfunction "KL_9") (pintype "passive"))
      (node (ref "D35") (pin "1") (pinfunction "+_1") (pintype "passive"))
      (node (ref "D36") (pin "1") (pinfunction "+_1") (pintype "passive"))
      (node (ref "JP13") (pin "1") (pinfunction "1_1") (pintype "passive"))
      (node (ref "JP14") (pin "2") (pinfunction "2_2") (pintype "passive"))
      (node (ref "TP88") (pin "TP") (pinfunction "PP_TP") (pintype "input"))
    )
    (net (code "92") (name "Net-(9A-KL)") (class "Default")
      (node (ref "9") (pin "1") (pinfunction "KL_1") (pintype "passive"))
      (node (ref "D58") (pin "2") (pinfunction "-_2") (pintype "passive"))
      (node (ref "TP93") (pin "TP") (pinfunction "PP_TP") (pintype "input"))
    )
    (net (code "93") (name "Net-(9B-KL)") (class "Default")
      (node (ref "9") (pin "10") (pinfunction "KL_10") (pintype "passive"))
      (node (ref "D46") (pin "2") (pinfunction "-_2") (pintype "passive"))
      (node (ref "D47") (pin "2") (pinfunction "-_2") (pintype "passive"))
      (node (ref "JP20") (pin "1") (pinfunction "1_1") (pintype "passive"))
      (node (ref "TP102") (pin "TP") (pinfunction "PP_TP") (pintype "input"))
    )
    (net (code "94") (name "Net-(9C-KL)") (class "Default")
      (node (ref "9") (pin "11") (pinfunction "KL_11") (pintype "passive"))
      (node (ref "D47") (pin "1") (pinfunction "+_1") (pintype "passive"))
      (node (ref "TP103") (pin "TP") (pinfunction "PP_TP") (pintype "input"))
      (node (ref "X10") (pin "19") (pinfunction "19_19") (pintype "passive"))
    )
    (net (code "95") (name "Net-(9E-KL)") (class "Default")
      (node (ref "9") (pin "2") (pinfunction "KL_2") (pintype "passive"))
      (node (ref "Q36") (pin "2") (pinfunction "C_2") (pintype "passive"))
      (node (ref "TP94") (pin "TP") (pinfunction "PP_TP") (pintype "input"))
    )
    (net (code "96") (name "Net-(9F-KL)") (class "Default")
      (node (ref "9") (pin "3") (pinfunction "KL_3") (pintype "passive"))
      (node (ref "IC30") (pin "11") (pinfunction "O6_11") (pintype "open_collector"))
      (node (ref "TP95") (pin "TP") (pinfunction "PP_TP") (pintype "input"))
    )
    (net (code "97") (name "Net-(9G-KL)") (class "Default")
      (node (ref "9") (pin "4") (pinfunction "KL_4") (pintype "passive"))
      (node (ref "IC30") (pin "10") (pinfunction "O7_10") (pintype "open_collector"))
      (node (ref "TP96") (pin "TP") (pinfunction "PP_TP") (pintype "input"))
    )
    (net (code "98") (name "Net-(9H-KL)") (class "Default")
      (node (ref "9") (pin "5") (pinfunction "KL_5") (pintype "passive"))
      (node (ref "IC30") (pin "12") (pinfunction "O5_12") (pintype "open_collector"))
      (node (ref "TP97") (pin "TP") (pinfunction "PP_TP") (pintype "input"))
    )
    (net (code "99") (name "Net-(9I-KL)") (class "Default")
      (node (ref "9") (pin "6") (pinfunction "KL_6") (pintype "passive"))
      (node (ref "IC30") (pin "13") (pinfunction "O4_13") (pintype "open_collector"))
      (node (ref "TP98") (pin "TP") (pinfunction "PP_TP") (pintype "input"))
    )
    (net (code "100") (name "Net-(9J-KL)") (class "Default")
      (node (ref "9") (pin "7") (pinfunction "KL_7") (pintype "passive"))
      (node (ref "IC30") (pin "14") (pinfunction "O3_14") (pintype "open_collector"))
      (node (ref "TP99") (pin "TP") (pinfunction "PP_TP") (pintype "input"))
    )
    (net (code "101") (name "Net-(9K-KL)") (class "Default")
      (node (ref "9") (pin "8") (pinfunction "KL_8") (pintype "passive"))
      (node (ref "R271") (pin "2") (pinfunction "2_2") (pintype "passive"))
      (node (ref "TP100") (pin "TP") (pinfunction "PP_TP") (pintype "input"))
    )
    (net (code "102") (name "Net-(9L-KL)") (class "Default")
      (node (ref "9") (pin "9") (pinfunction "KL_9") (pintype "passive"))
      (node (ref "D46") (pin "1") (pinfunction "+_1") (pintype "passive"))
      (node (ref "TP101") (pin "TP") (pinfunction "PP_TP") (pintype "input"))
      (node (ref "X10") (pin "17") (pinfunction "17_17") (pintype "passive"))
    )
    (net (code "103") (name "Net-(10B-KL)") (class "Default")
      (node (ref "10") (pin "10") (pinfunction "KL_10") (pintype "passive"))
      (node (ref "TP112") (pin "TP") (pinfunction "PP_TP") (pintype "input"))
      (node (ref "X10") (pin "15") (pinfunction "15_15") (pintype "passive"))
    )
    (net (code "104") (name "Net-(10C-KL)") (class "Default")
      (node (ref "10") (pin "11") (pinfunction "KL_11") (pintype "passive"))
      (node (ref "Q38") (pin "2") (pinfunction "C_2") (pintype "passive"))
      (node (ref "R257") (pin "1") (pinfunction "1_1") (pintype "passive"))
      (node (ref "TP113") (pin "TP") (pinfunction "PP_TP") (pintype "input"))
    )
    (net (code "105") (name "Net-(10D-KL)") (class "Default")
      (node (ref "10") (pin "12") (pinfunction "KL_12") (pintype "passive"))
      (node (ref "R258") (pin "1") (pinfunction "1_1") (pintype "passive"))
      (node (ref "TP115") (pin "TP") (pinfunction "PP_TP") (pintype "input"))
    )
    (net (code "106") (name "Net-(10E-KL)") (class "Default")
      (node (ref "10") (pin "2") (pinfunction "KL_2") (pintype "passive"))
      (node (ref "D51") (pin "2") (pinfunction "-_2") (pintype "passive"))
      (node (ref "LED19") (pin "K") (pinfunction "C_K") (pintype "passive"))
      (node (ref "TP104") (pin "TP") (pinfunction "PP_TP") (pintype "input"))
      (node (ref "X10") (pin "12") (pinfunction "12_12") (pintype "passive"))
    )
    (net (code "107") (name "Net-(10F-KL)") (class "Default")
      (node (ref "10") (pin "3") (pinfunction "KL_3") (pintype "passive"))
      (node (ref "D50") (pin "2") (pinfunction "-_2") (pintype "passive"))
      (node (ref "LED20") (pin "K") (pinfunction "C_K") (pintype "passive"))
      (node (ref "TP105") (pin "TP") (pinfunction "PP_TP") (pintype "input"))
      (node (ref "X10") (pin "11") (pinfunction "11_11") (pintype "passive"))
    )
    (net (code "108") (name "Net-(10G-KL)") (class "Default")
      (node (ref "10") (pin "4") (pinfunction "KL_4") (pintype "passive"))
      (node (ref "D49") (pin "2") (pinfunction "-_2") (pintype "passive"))
      (node (ref "LED21") (pin "K") (pinfunction "C_K") (pintype "passive"))
      (node (ref "TP106") (pin "TP") (pinfunction "PP_TP") (pintype "input"))
      (node (ref "X10") (pin "10") (pinfunction "10_10") (pintype "passive"))
    )
    (net (code "109") (name "Net-(10H-KL)") (class "Default")
      (node (ref "10") (pin "5") (pinfunction "KL_5") (pintype "passive"))
      (node (ref "D48") (pin "2") (pinfunction "-_2") (pintype "passive"))
      (node (ref "LED22") (pin "K") (pinfunction "C_K") (pintype "passive"))
      (node (ref "TP107") (pin "TP") (pinfunction "PP_TP") (pintype "input"))
      (node (ref "X10") (pin "9") (pinfunction "9_9") (pintype "passive"))
    )
    (net (code "110") (name "Net-(10I-KL)") (class "Default")
      (node (ref "10") (pin "6") (pinfunction "KL_6") (pintype "passive"))
      (node (ref "JP17") (pin "2") (pinfunction "2_2") (pintype "passive"))
      (node (ref "TP108") (pin "TP") (pinfunction "PP_TP") (pintype "input"))
    )
    (net (code "111") (name "Net-(10J-KL)") (class "Default")
      (node (ref "10") (pin "7") (pinfunction "KL_7") (pintype "passive"))
      (node (ref "LED23") (pin "A") (pinfunction "A_A") (pintype "passive"))
      (node (ref "TP109") (pin "TP") (pinfunction "PP_TP") (pintype "input"))
      (node (ref "X10") (pin "8") (pinfunction "8_8") (pintype "passive"))
    )
    (net (code "112") (name "Net-(10K-KL)") (class "Default")
      (node (ref "10") (pin "8") (pinfunction "KL_8") (pintype "passive"))
      (node (ref "D52") (pin "2") (pinfunction "-_2") (pintype "passive"))
      (node (ref "LED24") (pin "K") (pinfunction "C_K") (pintype "passive"))
      (node (ref "TP110") (pin "TP") (pinfunction "PP_TP") (pintype "input"))
      (node (ref "X10") (pin "14") (pinfunction "14_14") (pintype "passive"))
    )
    (net (code "113") (name "Net-(10L-KL)") (class "Default")
      (node (ref "10") (pin "9") (pinfunction "KL_9") (pintype "passive"))
      (node (ref "D49") (pin "1") (pinfunction "+_1") (pintype "passive"))
      (node (ref "D50") (pin "1") (pinfunction "+_1") (pintype "passive"))
      (node (ref "JP18") (pin "1") (pinfunction "1_1") (pintype "passive"))
      (node (ref "JP19") (pin "2") (pinfunction "2_2") (pintype "passive"))
      (node (ref "TP111") (pin "TP") (pinfunction "PP_TP") (pintype "input"))
    )
    (net (code "114") (name "Net-(11A-KL)") (class "Default")
      (node (ref "11") (pin "1") (pinfunction "KL_1") (pintype "passive"))
      (node (ref "D72") (pin "2") (pinfunction "-_2") (pintype "passive"))
      (node (ref "TP116") (pin "TP") (pinfunction "PP_TP") (pintype "input"))
    )
    (net (code "115") (name "Net-(11B-KL)") (class "Default")
      (node (ref "11") (pin "10") (pinfunction "KL_10") (pintype "passive"))
      (node (ref "D60") (pin "2") (pinfunction "-_2") (pintype "passive"))
      (node (ref "D61") (pin "2") (pinfunction "-_2") (pintype "passive"))
      (node (ref "JP25") (pin "1") (pinfunction "1_1") (pintype "passive"))
      (node (ref "TP125") (pin "TP") (pinfunction "PP_TP") (pintype "input"))
    )
    (net (code "116") (name "Net-(11C-KL)") (class "Default")
      (node (ref "11") (pin "11") (pinfunction "KL_11") (pintype "passive"))
      (node (ref "D61") (pin "1") (pinfunction "+_1") (pintype "passive"))
      (node (ref "TP126") (pin "TP") (pinfunction "PP_TP") (pintype "input"))
      (node (ref "X13") (pin "19") (pinfunction "19_19") (pintype "passive"))
    )
    (net (code "117") (name "Net-(11E-KL)") (class "Default")
      (node (ref "11") (pin "2") (pinfunction "KL_2") (pintype "passive"))
      (node (ref "Q46") (pin "2") (pinfunction "C_2") (pintype "passive"))
      (node (ref "TP117") (pin "TP") (pinfunction "PP_TP") (pintype "input"))
    )
    (net (code "118") (name "Net-(11F-KL)") (class "Default")
      (node (ref "11") (pin "3") (pinfunction "KL_3") (pintype "passive"))
      (node (ref "IC39") (pin "11") (pinfunction "O6_11") (pintype "open_collector"))
      (node (ref "TP118") (pin "TP") (pinfunction "PP_TP") (pintype "input"))
    )
    (net (code "119") (name "Net-(11G-KL)") (class "Default")
      (node (ref "11") (pin "4") (pinfunction "KL_4") (pintype "passive"))
      (node (ref "IC39") (pin "10") (pinfunction "O7_10") (pintype "open_collector"))
      (node (ref "TP119") (pin "TP") (pinfunction "PP_TP") (pintype "input"))
    )
    (net (code "120") (name "Net-(11H-KL)") (class "Default")
      (node (ref "11") (pin "5") (pinfunction "KL_5") (pintype "passive"))
      (node (ref "IC39") (pin "12") (pinfunction "O5_12") (pintype "open_collector"))
      (node (ref "TP120") (pin "TP") (pinfunction "PP_TP") (pintype "input"))
    )
    (net (code "121") (name "Net-(11I-KL)") (class "Default")
      (node (ref "11") (pin "6") (pinfunction "KL_6") (pintype "passive"))
      (node (ref "IC39") (pin "13") (pinfunction "O4_13") (pintype "open_collector"))
      (node (ref "TP121") (pin "TP") (pinfunction "PP_TP") (pintype "input"))
    )
    (net (code "122") (name "Net-(11J-KL)") (class "Default")
      (node (ref "11") (pin "7") (pinfunction "KL_7") (pintype "passive"))
      (node (ref "IC39") (pin "14") (pinfunction "O3_14") (pintype "open_collector"))
      (node (ref "TP122") (pin "TP") (pinfunction "PP_TP") (pintype "input"))
    )
    (net (code "123") (name "Net-(11K-KL)") (class "Default")
      (node (ref "11") (pin "8") (pinfunction "KL_8") (pintype "passive"))
      (node (ref "R326") (pin "2") (pinfunction "2_2") (pintype "passive"))
      (node (ref "TP123") (pin "TP") (pinfunction "PP_TP") (pintype "input"))
    )
    (net (code "124") (name "Net-(11L-KL)") (class "Default")
      (node (ref "11") (pin "9") (pinfunction "KL_9") (pintype "passive"))
      (node (ref "D60") (pin "1") (pinfunction "+_1") (pintype "passive"))
      (node (ref "TP124") (pin "TP") (pinfunction "PP_TP") (pintype "input"))
      (node (ref "X13") (pin "17") (pinfunction "17_17") (pintype "passive"))
    )
    (net (code "125") (name "Net-(12B-KL)") (class "Default")
      (node (ref "12") (pin "10") (pinfunction "KL_10") (pintype "passive"))
      (node (ref "TP135") (pin "TP") (pinfunction "PP_TP") (pintype "input"))
      (node (ref "X13") (pin "15") (pinfunction "15_15") (pintype "passive"))
    )
    (net (code "126") (name "Net-(12C-KL)") (class "Default")
      (node (ref "12") (pin "11") (pinfunction "KL_11") (pintype "passive"))
      (node (ref "Q48") (pin "2") (pinfunction "C_2") (pintype "passive"))
      (node (ref "R312") (pin "1") (pinfunction "1_1") (pintype "passive"))
      (node (ref "TP136") (pin "TP") (pinfunction "PP_TP") (pintype "input"))
    )
    (net (code "127") (name "Net-(12D-KL)") (class "Default")
      (node (ref "12") (pin "12") (pinfunction "KL_12") (pintype "passive"))
      (node (ref "R313") (pin "1") (pinfunction "1_1") (pintype "passive"))
      (node (ref "TP138") (pin "TP") (pinfunction "PP_TP") (pintype "input"))
    )
    (net (code "128") (name "Net-(12E-KL)") (class "Default")
      (node (ref "12") (pin "2") (pinfunction "KL_2") (pintype "passive"))
      (node (ref "D65") (pin "2") (pinfunction "-_2") (pintype "passive"))
      (node (ref "LED25") (pin "K") (pinfunction "C_K") (pintype "passive"))
      (node (ref "TP127") (pin "TP") (pinfunction "PP_TP") (pintype "input"))
      (node (ref "X13") (pin "12") (pinfunction "12_12") (pintype "passive"))
    )
    (net (code "129") (name "Net-(12F-KL)") (class "Default")
      (node (ref "12") (pin "3") (pinfunction "KL_3") (pintype "passive"))
      (node (ref "D64") (pin "2") (pinfunction "-_2") (pintype "passive"))
      (node (ref "LED26") (pin "K") (pinfunction "C_K") (pintype "passive"))
      (node (ref "TP128") (pin "TP") (pinfunction "PP_TP") (pintype "input"))
      (node (ref "X13") (pin "11") (pinfunction "11_11") (pintype "passive"))
    )
    (net (code "130") (name "Net-(12G-KL)") (class "Default")
      (node (ref "12") (pin "4") (pinfunction "KL_4") (pintype "passive"))
      (node (ref "D63") (pin "2") (pinfunction "-_2") (pintype "passive"))
      (node (ref "LED27") (pin "K") (pinfunction "C_K") (pintype "passive"))
      (node (ref "TP129") (pin "TP") (pinfunction "PP_TP") (pintype "input"))
      (node (ref "X13") (pin "10") (pinfunction "10_10") (pintype "passive"))
    )
    (net (code "131") (name "Net-(12H-KL)") (class "Default")
      (node (ref "12") (pin "5") (pinfunction "KL_5") (pintype "passive"))
      (node (ref "D62") (pin "2") (pinfunction "-_2") (pintype "passive"))
      (node (ref "LED28") (pin "K") (pinfunction "C_K") (pintype "passive"))
      (node (ref "TP130") (pin "TP") (pinfunction "PP_TP") (pintype "input"))
      (node (ref "X13") (pin "9") (pinfunction "9_9") (pintype "passive"))
    )
    (net (code "132") (name "Net-(12I-KL)") (class "Default")
      (node (ref "12") (pin "6") (pinfunction "KL_6") (pintype "passive"))
      (node (ref "JP22") (pin "2") (pinfunction "2_2") (pintype "passive"))
      (node (ref "TP131") (pin "TP") (pinfunction "PP_TP") (pintype "input"))
    )
    (net (code "133") (name "Net-(12J-KL)") (class "Default")
      (node (ref "12") (pin "7") (pinfunction "KL_7") (pintype "passive"))
      (node (ref "LED29") (pin "A") (pinfunction "A_A") (pintype "passive"))
      (node (ref "TP132") (pin "TP") (pinfunction "PP_TP") (pintype "input"))
      (node (ref "X13") (pin "8") (pinfunction "8_8") (pintype "passive"))
    )
    (net (code "134") (name "Net-(12K-KL)") (class "Default")
      (node (ref "12") (pin "8") (pinfunction "KL_8") (pintype "passive"))
      (node (ref "D66") (pin "2") (pinfunction "-_2") (pintype "passive"))
      (node (ref "LED30") (pin "K") (pinfunction "C_K") (pintype "passive"))
      (node (ref "TP133") (pin "TP") (pinfunction "PP_TP") (pintype "input"))
      (node (ref "X13") (pin "14") (pinfunction "14_14") (pintype "passive"))
    )
    (net (code "135") (name "Net-(12L-KL)") (class "Default")
      (node (ref "12") (pin "9") (pinfunction "KL_9") (pintype "passive"))
      (node (ref "D63") (pin "1") (pinfunction "+_1") (pintype "passive"))
      (node (ref "D64") (pin "1") (pinfunction "+_1") (pintype "passive"))
      (node (ref "JP23") (pin "1") (pinfunction "1_1") (pintype "passive"))
      (node (ref "JP24") (pin "2") (pinfunction "2_2") (pintype "passive"))
      (node (ref "TP134") (pin "TP") (pinfunction "PP_TP") (pintype "input"))
    )
    (net (code "136") (name "Net-(13A-KL)") (class "Default")
      (node (ref "13") (pin "1") (pinfunction "KL_1") (pintype "passive"))
      (node (ref "D80") (pin "2") (pinfunction "-_2") (pintype "passive"))
      (node (ref "TP139") (pin "TP") (pinfunction "PP_TP") (pintype "input"))
    )
    (net (code "137") (name "Net-(13B-KL)") (class "Default")
      (node (ref "13") (pin "10") (pinfunction "KL_10") (pintype "passive"))
      (node (ref "D14") (pin "2") (pinfunction "-_2") (pintype "passive"))
      (node (ref "D28") (pin "2") (pinfunction "-_2") (pintype "passive"))
      (node (ref "JP30") (pin "1") (pinfunction "1_1") (pintype "passive"))
      (node (ref "TP148") (pin "TP") (pinfunction "PP_TP") (pintype "input"))
    )
    (net (code "138") (name "Net-(13C-KL)") (class "Default")
      (node (ref "13") (pin "11") (pinfunction "KL_11") (pintype "passive"))
      (node (ref "D28") (pin "1") (pinfunction "+_1") (pintype "passive"))
      (node (ref "TP149") (pin "TP") (pinfunction "PP_TP") (pintype "input"))
      (node (ref "X16") (pin "19") (pinfunction "19_19") (pintype "passive"))
    )
    (net (code "139") (name "Net-(13E-KL)") (class "Default")
      (node (ref "13") (pin "2") (pinfunction "KL_2") (pintype "passive"))
      (node (ref "Q56") (pin "2") (pinfunction "C_2") (pintype "passive"))
      (node (ref "TP140") (pin "TP") (pinfunction "PP_TP") (pintype "input"))
    )
    (net (code "140") (name "Net-(13F-KL)") (class "Default")
      (node (ref "13") (pin "3") (pinfunction "KL_3") (pintype "passive"))
      (node (ref "IC48") (pin "11") (pinfunction "O6_11") (pintype "open_collector"))
      (node (ref "TP141") (pin "TP") (pinfunction "PP_TP") (pintype "input"))
    )
    (net (code "141") (name "Net-(13G-KL)") (class "Default")
      (node (ref "13") (pin "4") (pinfunction "KL_4") (pintype "passive"))
      (node (ref "IC48") (pin "10") (pinfunction "O7_10") (pintype "open_collector"))
      (node (ref "TP142") (pin "TP") (pinfunction "PP_TP") (pintype "input"))
    )
    (net (code "142") (name "Net-(13H-KL)") (class "Default")
      (node (ref "13") (pin "5") (pinfunction "KL_5") (pintype "passive"))
      (node (ref "IC48") (pin "12") (pinfunction "O5_12") (pintype "open_collector"))
      (node (ref "TP143") (pin "TP") (pinfunction "PP_TP") (pintype "input"))
    )
    (net (code "143") (name "Net-(13I-KL)") (class "Default")
      (node (ref "13") (pin "6") (pinfunction "KL_6") (pintype "passive"))
      (node (ref "IC48") (pin "13") (pinfunction "O4_13") (pintype "open_collector"))
      (node (ref "TP144") (pin "TP") (pinfunction "PP_TP") (pintype "input"))
    )
    (net (code "144") (name "Net-(13J-KL)") (class "Default")
      (node (ref "13") (pin "7") (pinfunction "KL_7") (pintype "passive"))
      (node (ref "IC48") (pin "14") (pinfunction "O3_14") (pintype "open_collector"))
      (node (ref "TP145") (pin "TP") (pinfunction "PP_TP") (pintype "input"))
    )
    (net (code "145") (name "Net-(13K-KL)") (class "Default")
      (node (ref "13") (pin "8") (pinfunction "KL_8") (pintype "passive"))
      (node (ref "R353") (pin "2") (pinfunction "2_2") (pintype "passive"))
      (node (ref "TP146") (pin "TP") (pinfunction "PP_TP") (pintype "input"))
    )
    (net (code "146") (name "Net-(13L-KL)") (class "Default")
      (node (ref "13") (pin "9") (pinfunction "KL_9") (pintype "passive"))
      (node (ref "D14") (pin "1") (pinfunction "+_1") (pintype "passive"))
      (node (ref "TP147") (pin "TP") (pinfunction "PP_TP") (pintype "input"))
      (node (ref "X16") (pin "17") (pinfunction "17_17") (pintype "passive"))
    )
    (net (code "147") (name "Net-(14B-KL)") (class "Default")
      (node (ref "14") (pin "10") (pinfunction "KL_10") (pintype "passive"))
      (node (ref "TP158") (pin "TP") (pinfunction "PP_TP") (pintype "input"))
      (node (ref "X16") (pin "15") (pinfunction "15_15") (pintype "passive"))
    )
    (net (code "148") (name "Net-(14C-KL)") (class "Default")
      (node (ref "14") (pin "11") (pinfunction "KL_11") (pintype "passive"))
      (node (ref "Q58") (pin "2") (pinfunction "C_2") (pintype "passive"))
      (node (ref "R339") (pin "1") (pinfunction "1_1") (pintype "passive"))
      (node (ref "TP159") (pin "TP") (pinfunction "PP_TP") (pintype "input"))
    )
    (net (code "149") (name "Net-(14D-KL)") (class "Default")
      (node (ref "14") (pin "12") (pinfunction "KL_12") (pintype "passive"))
      (node (ref "R340") (pin "1") (pinfunction "1_1") (pintype "passive"))
      (node (ref "TP161") (pin "TP") (pinfunction "PP_TP") (pintype "input"))
    )
    (net (code "150") (name "Net-(14E-KL)") (class "Default")
      (node (ref "14") (pin "2") (pinfunction "KL_2") (pintype "passive"))
      (node (ref "D74") (pin "2") (pinfunction "-_2") (pintype "passive"))
      (node (ref "LED31") (pin "K") (pinfunction "C_K") (pintype "passive"))
      (node (ref "TP150") (pin "TP") (pinfunction "PP_TP") (pintype "input"))
      (node (ref "X16") (pin "12") (pinfunction "12_12") (pintype "passive"))
    )
    (net (code "151") (name "Net-(14F-KL)") (class "Default")
      (node (ref "14") (pin "3") (pinfunction "KL_3") (pintype "passive"))
      (node (ref "D70") (pin "2") (pinfunction "-_2") (pintype "passive"))
      (node (ref "LED32") (pin "K") (pinfunction "C_K") (pintype "passive"))
      (node (ref "TP151") (pin "TP") (pinfunction "PP_TP") (pintype "input"))
      (node (ref "X16") (pin "11") (pinfunction "11_11") (pintype "passive"))
    )
    (net (code "152") (name "Net-(14G-KL)") (class "Default")
      (node (ref "14") (pin "4") (pinfunction "KL_4") (pintype "passive"))
      (node (ref "D56") (pin "2") (pinfunction "-_2") (pintype "passive"))
      (node (ref "LED33") (pin "K") (pinfunction "C_K") (pintype "passive"))
      (node (ref "TP152") (pin "TP") (pinfunction "PP_TP") (pintype "input"))
      (node (ref "X16") (pin "10") (pinfunction "10_10") (pintype "passive"))
    )
    (net (code "153") (name "Net-(14H-KL)") (class "Default")
      (node (ref "14") (pin "5") (pinfunction "KL_5") (pintype "passive"))
      (node (ref "D42") (pin "2") (pinfunction "-_2") (pintype "passive"))
      (node (ref "LED34") (pin "K") (pinfunction "C_K") (pintype "passive"))
      (node (ref "TP153") (pin "TP") (pinfunction "PP_TP") (pintype "input"))
      (node (ref "X16") (pin "9") (pinfunction "9_9") (pintype "passive"))
    )
    (net (code "154") (name "Net-(14I-KL)") (class "Default")
      (node (ref "14") (pin "6") (pinfunction "KL_6") (pintype "passive"))
      (node (ref "JP27") (pin "2") (pinfunction "2_2") (pintype "passive"))
      (node (ref "TP154") (pin "TP") (pinfunction "PP_TP") (pintype "input"))
    )
    (net (code "155") (name "Net-(14J-KL)") (class "Default")
      (node (ref "14") (pin "7") (pinfunction "KL_7") (pintype "passive"))
      (node (ref "LED35") (pin "A") (pinfunction "A_A") (pintype "passive"))
      (node (ref "TP155") (pin "TP") (pinfunction "PP_TP") (pintype "input"))
      (node (ref "X16") (pin "8") (pinfunction "8_8") (pintype "passive"))
    )
    (net (code "156") (name "Net-(14K-KL)") (class "Default")
      (node (ref "14") (pin "8") (pinfunction "KL_8") (pintype "passive"))
      (node (ref "D75") (pin "2") (pinfunction "-_2") (pintype "passive"))
      (node (ref "LED36") (pin "K") (pinfunction "C_K") (pintype "passive"))
      (node (ref "TP156") (pin "TP") (pinfunction "PP_TP") (pintype "input"))
      (node (ref "X16") (pin "14") (pinfunction "14_14") (pintype "passive"))
    )
    (net (code "157") (name "Net-(14L-KL)") (class "Default")
      (node (ref "14") (pin "9") (pinfunction "KL_9") (pintype "passive"))
      (node (ref "D56") (pin "1") (pinfunction "+_1") (pintype "passive"))
      (node (ref "D70") (pin "1") (pinfunction "+_1") (pintype "passive"))
      (node (ref "JP28") (pin "1") (pinfunction "1_1") (pintype "passive"))
      (node (ref "JP29") (pin "2") (pinfunction "2_2") (pintype "passive"))
      (node (ref "TP157") (pin "TP") (pinfunction "PP_TP") (pintype "input"))
    )
    (net (code "158") (name "Net-(15A-KL)") (class "Default")
      (node (ref "15") (pin "1") (pinfunction "KL_1") (pintype "passive"))
      (node (ref "D93") (pin "2") (pinfunction "-_2") (pintype "passive"))
      (node (ref "TP162") (pin "TP") (pinfunction "PP_TP") (pintype "input"))
    )
    (net (code "159") (name "Net-(15B-KL)") (class "Default")
      (node (ref "15") (pin "10") (pinfunction "KL_10") (pintype "passive"))
      (node (ref "D82") (pin "2") (pinfunction "-_2") (pintype "passive"))
      (node (ref "D83") (pin "2") (pinfunction "-_2") (pintype "passive"))
      (node (ref "JP35") (pin "1") (pinfunction "1_1") (pintype "passive"))
      (node (ref "TP171") (pin "TP") (pinfunction "PP_TP") (pintype "input"))
    )
    (net (code "160") (name "Net-(15C-KL)") (class "Default")
      (node (ref "15") (pin "11") (pinfunction "KL_11") (pintype "passive"))
      (node (ref "D83") (pin "1") (pinfunction "+_1") (pintype "passive"))
      (node (ref "TP172") (pin "TP") (pinfunction "PP_TP") (pintype "input"))
      (node (ref "X19") (pin "19") (pinfunction "19_19") (pintype "passive"))
    )
    (net (code "161") (name "Net-(15E-KL)") (class "Default")
      (node (ref "15") (pin "2") (pinfunction "KL_2") (pintype "passive"))
      (node (ref "Q66") (pin "2") (pinfunction "C_2") (pintype "passive"))
      (node (ref "TP163") (pin "TP") (pinfunction "PP_TP") (pintype "input"))
    )
    (net (code "162") (name "Net-(15F-KL)") (class "Default")
      (node (ref "15") (pin "3") (pinfunction "KL_3") (pintype "passive"))
      (node (ref "IC57") (pin "11") (pinfunction "O6_11") (pintype "open_collector"))
      (node (ref "TP164") (pin "TP") (pinfunction "PP_TP") (pintype "input"))
    )
    (net (code "163") (name "Net-(15G-KL)") (class "Default")
      (node (ref "15") (pin "4") (pinfunction "KL_4") (pintype "passive"))
      (node (ref "IC57") (pin "10") (pinfunction "O7_10") (pintype "open_collector"))
      (node (ref "TP165") (pin "TP") (pinfunction "PP_TP") (pintype "input"))
    )
    (net (code "164") (name "Net-(15H-KL)") (class "Default")
      (node (ref "15") (pin "5") (pinfunction "KL_5") (pintype "passive"))
      (node (ref "IC57") (pin "12") (pinfunction "O5_12") (pintype "open_collector"))
      (node (ref "TP166") (pin "TP") (pinfunction "PP_TP") (pintype "input"))
    )
    (net (code "165") (name "Net-(15I-KL)") (class "Default")
      (node (ref "15") (pin "6") (pinfunction "KL_6") (pintype "passive"))
      (node (ref "IC57") (pin "13") (pinfunction "O4_13") (pintype "open_collector"))
      (node (ref "TP167") (pin "TP") (pinfunction "PP_TP") (pintype "input"))
    )
    (net (code "166") (name "Net-(15J-KL)") (class "Default")
      (node (ref "15") (pin "7") (pinfunction "KL_7") (pintype "passive"))
      (node (ref "IC57") (pin "14") (pinfunction "O3_14") (pintype "open_collector"))
      (node (ref "TP168") (pin "TP") (pinfunction "PP_TP") (pintype "input"))
    )
    (net (code "167") (name "Net-(15K-KL)") (class "Default")
      (node (ref "15") (pin "8") (pinfunction "KL_8") (pintype "passive"))
      (node (ref "R404") (pin "2") (pinfunction "2_2") (pintype "passive"))
      (node (ref "TP169") (pin "TP") (pinfunction "PP_TP") (pintype "input"))
    )
    (net (code "168") (name "Net-(15L-KL)") (class "Default")
      (node (ref "15") (pin "9") (pinfunction "KL_9") (pintype "passive"))
      (node (ref "D82") (pin "1") (pinfunction "+_1") (pintype "passive"))
      (node (ref "TP170") (pin "TP") (pinfunction "PP_TP") (pintype "input"))
      (node (ref "X19") (pin "17") (pinfunction "17_17") (pintype "passive"))
    )
    (net (code "169") (name "Net-(16B-KL)") (class "Default")
      (node (ref "16") (pin "10") (pinfunction "KL_10") (pintype "passive"))
      (node (ref "TP181") (pin "TP") (pinfunction "PP_TP") (pintype "input"))
      (node (ref "X19") (pin "15") (pinfunction "15_15") (pintype "passive"))
    )
    (net (code "170") (name "Net-(16C-KL)") (class "Default")
      (node (ref "16") (pin "11") (pinfunction "KL_11") (pintype "passive"))
      (node (ref "Q68") (pin "2") (pinfunction "C_2") (pintype "passive"))
      (node (ref "R390") (pin "1") (pinfunction "1_1") (pintype "passive"))
      (node (ref "TP182") (pin "TP") (pinfunction "PP_TP") (pintype "input"))
    )
    (net (code "171") (name "Net-(16D-KL)") (class "Default")
      (node (ref "16") (pin "12") (pinfunction "KL_12") (pintype "passive"))
      (node (ref "R391") (pin "1") (pinfunction "1_1") (pintype "passive"))
      (node (ref "TP184") (pin "TP") (pinfunction "PP_TP") (pintype "input"))
    )
    (net (code "172") (name "Net-(16E-KL)") (class "Default")
      (node (ref "16") (pin "2") (pinfunction "KL_2") (pintype "passive"))
      (node (ref "D87") (pin "2") (pinfunction "-_2") (pintype "passive"))
      (node (ref "LED37") (pin "K") (pinfunction "C_K") (pintype "passive"))
      (node (ref "TP173") (pin "TP") (pinfunction "PP_TP") (pintype "input"))
      (node (ref "X19") (pin "12") (pinfunction "12_12") (pintype "passive"))
    )
    (net (code "173") (name "Net-(16F-KL)") (class "Default")
      (node (ref "16") (pin "3") (pinfunction "KL_3") (pintype "passive"))
      (node (ref "D86") (pin "2") (pinfunction "-_2") (pintype "passive"))
      (node (ref "LED38") (pin "K") (pinfunction "C_K") (pintype "passive"))
      (node (ref "TP174") (pin "TP") (pinfunction "PP_TP") (pintype "input"))
      (node (ref "X19") (pin "11") (pinfunction "11_11") (pintype "passive"))
    )
    (net (code "174") (name "Net-(16G-KL)") (class "Default")
      (node (ref "16") (pin "4") (pinfunction "KL_4") (pintype "passive"))
      (node (ref "D85") (pin "2") (pinfunction "-_2") (pintype "passive"))
      (node (ref "LED39") (pin "K") (pinfunction "C_K") (pintype "passive"))
      (node (ref "TP175") (pin "TP") (pinfunction "PP_TP") (pintype "input"))
      (node (ref "X19") (pin "10") (pinfunction "10_10") (pintype "passive"))
    )
    (net (code "175") (name "Net-(16H-KL)") (class "Default")
      (node (ref "16") (pin "5") (pinfunction "KL_5") (pintype "passive"))
      (node (ref "D84") (pin "2") (pinfunction "-_2") (pintype "passive"))
      (node (ref "LED40") (pin "K") (pinfunction "C_K") (pintype "passive"))
      (node (ref "TP176") (pin "TP") (pinfunction "PP_TP") (pintype "input"))
      (node (ref "X19") (pin "9") (pinfunction "9_9") (pintype "passive"))
    )
    (net (code "176") (name "Net-(16I-KL)") (class "Default")
      (node (ref "16") (pin "6") (pinfunction "KL_6") (pintype "passive"))
      (node (ref "JP32") (pin "2") (pinfunction "2_2") (pintype "passive"))
      (node (ref "TP177") (pin "TP") (pinfunction "PP_TP") (pintype "input"))
    )
    (net (code "177") (name "Net-(16J-KL)") (class "Default")
      (node (ref "16") (pin "7") (pinfunction "KL_7") (pintype "passive"))
      (node (ref "LED41") (pin "A") (pinfunction "A_A") (pintype "passive"))
      (node (ref "TP178") (pin "TP") (pinfunction "PP_TP") (pintype "input"))
      (node (ref "X19") (pin "8") (pinfunction "8_8") (pintype "passive"))
    )
    (net (code "178") (name "Net-(16K-KL)") (class "Default")
      (node (ref "16") (pin "8") (pinfunction "KL_8") (pintype "passive"))
      (node (ref "D88") (pin "2") (pinfunction "-_2") (pintype "passive"))
      (node (ref "LED42") (pin "K") (pinfunction "C_K") (pintype "passive"))
      (node (ref "TP179") (pin "TP") (pinfunction "PP_TP") (pintype "input"))
      (node (ref "X19") (pin "14") (pinfunction "14_14") (pintype "passive"))
    )
    (net (code "179") (name "Net-(16L-KL)") (class "Default")
      (node (ref "16") (pin "9") (pinfunction "KL_9") (pintype "passive"))
      (node (ref "D85") (pin "1") (pinfunction "+_1") (pintype "passive"))
      (node (ref "D86") (pin "1") (pinfunction "+_1") (pintype "passive"))
      (node (ref "JP33") (pin "1") (pinfunction "1_1") (pintype "passive"))
      (node (ref "JP34") (pin "2") (pinfunction "2_2") (pintype "passive"))
      (node (ref "TP180") (pin "TP") (pinfunction "PP_TP") (pintype "input"))
    )
    (net (code "180") (name "Net-(17A-KL)") (class "Default")
      (node (ref "17") (pin "1") (pinfunction "KL_1") (pintype "passive"))
      (node (ref "D116") (pin "2") (pinfunction "-_2") (pintype "passive"))
      (node (ref "TP185") (pin "TP") (pinfunction "PP_TP") (pintype "input"))
    )
    (net (code "181") (name "Net-(17B-KL)") (class "Default")
      (node (ref "17") (pin "10") (pinfunction "KL_10") (pintype "passive"))
      (node (ref "D95") (pin "2") (pinfunction "-_2") (pintype "passive"))
      (node (ref "D96") (pin "2") (pinfunction "-_2") (pintype "passive"))
      (node (ref "JP40") (pin "1") (pinfunction "1_1") (pintype "passive"))
      (node (ref "TP194") (pin "TP") (pinfunction "PP_TP") (pintype "input"))
    )
    (net (code "182") (name "Net-(17C-KL)") (class "Default")
      (node (ref "17") (pin "11") (pinfunction "KL_11") (pintype "passive"))
      (node (ref "D96") (pin "1") (pinfunction "+_1") (pintype "passive"))
      (node (ref "TP195") (pin "TP") (pinfunction "PP_TP") (pintype "input"))
      (node (ref "X22") (pin "19") (pinfunction "19_19") (pintype "passive"))
    )
    (net (code "183") (name "Net-(17E-KL)") (class "Default")
      (node (ref "17") (pin "2") (pinfunction "KL_2") (pintype "passive"))
      (node (ref "Q76") (pin "2") (pinfunction "C_2") (pintype "passive"))
      (node (ref "TP186") (pin "TP") (pinfunction "PP_TP") (pintype "input"))
    )
    (net (code "184") (name "Net-(17F-KL)") (class "Default")
      (node (ref "17") (pin "3") (pinfunction "KL_3") (pintype "passive"))
      (node (ref "IC66") (pin "11") (pinfunction "O6_11") (pintype "open_collector"))
      (node (ref "TP187") (pin "TP") (pinfunction "PP_TP") (pintype "input"))
    )
    (net (code "185") (name "Net-(17G-KL)") (class "Default")
      (node (ref "17") (pin "4") (pinfunction "KL_4") (pintype "passive"))
      (node (ref "IC66") (pin "10") (pinfunction "O7_10") (pintype "open_collector"))
      (node (ref "TP188") (pin "TP") (pinfunction "PP_TP") (pintype "input"))
    )
    (net (code "186") (name "Net-(17H-KL)") (class "Default")
      (node (ref "17") (pin "5") (pinfunction "KL_5") (pintype "passive"))
      (node (ref "IC66") (pin "12") (pinfunction "O5_12") (pintype "open_collector"))
      (node (ref "TP189") (pin "TP") (pinfunction "PP_TP") (pintype "input"))
    )
    (net (code "187") (name "Net-(17I-KL)") (class "Default")
      (node (ref "17") (pin "6") (pinfunction "KL_6") (pintype "passive"))
      (node (ref "IC66") (pin "13") (pinfunction "O4_13") (pintype "open_collector"))
      (node (ref "TP190") (pin "TP") (pinfunction "PP_TP") (pintype "input"))
    )
    (net (code "188") (name "Net-(17J-KL)") (class "Default")
      (node (ref "17") (pin "7") (pinfunction "KL_7") (pintype "passive"))
      (node (ref "IC66") (pin "14") (pinfunction "O3_14") (pintype "open_collector"))
      (node (ref "TP191") (pin "TP") (pinfunction "PP_TP") (pintype "input"))
    )
    (net (code "189") (name "Net-(17K-KL)") (class "Default")
      (node (ref "17") (pin "8") (pinfunction "KL_8") (pintype "passive"))
      (node (ref "R455") (pin "2") (pinfunction "2_2") (pintype "passive"))
      (node (ref "TP192") (pin "TP") (pinfunction "PP_TP") (pintype "input"))
    )
    (net (code "190") (name "Net-(17L-KL)") (class "Default")
      (node (ref "17") (pin "9") (pinfunction "KL_9") (pintype "passive"))
      (node (ref "D95") (pin "1") (pinfunction "+_1") (pintype "passive"))
      (node (ref "TP193") (pin "TP") (pinfunction "PP_TP") (pintype "input"))
      (node (ref "X22") (pin "17") (pinfunction "17_17") (pintype "passive"))
    )
    (net (code "191") (name "Net-(18B-KL)") (class "Default")
      (node (ref "18") (pin "10") (pinfunction "KL_10") (pintype "passive"))
      (node (ref "TP204") (pin "TP") (pinfunction "PP_TP") (pintype "input"))
      (node (ref "X22") (pin "15") (pinfunction "15_15") (pintype "passive"))
    )
    (net (code "192") (name "Net-(18C-KL)") (class "Default")
      (node (ref "18") (pin "11") (pinfunction "KL_11") (pintype "passive"))
      (node (ref "Q78") (pin "2") (pinfunction "C_2") (pintype "passive"))
      (node (ref "R441") (pin "1") (pinfunction "1_1") (pintype "passive"))
      (node (ref "TP205") (pin "TP") (pinfunction "PP_TP") (pintype "input"))
    )
    (net (code "193") (name "Net-(18D-KL)") (class "Default")
      (node (ref "18") (pin "12") (pinfunction "KL_12") (pintype "passive"))
      (node (ref "R442") (pin "1") (pinfunction "1_1") (pintype "passive"))
      (node (ref "TP207") (pin "TP") (pinfunction "PP_TP") (pintype "input"))
    )
    (net (code "194") (name "Net-(18E-KL)") (class "Default")
      (node (ref "18") (pin "2") (pinfunction "KL_2") (pintype "passive"))
      (node (ref "D100") (pin "2") (pinfunction "-_2") (pintype "passive"))
      (node (ref "LED43") (pin "K") (pinfunction "C_K") (pintype "passive"))
      (node (ref "TP196") (pin "TP") (pinfunction "PP_TP") (pintype "input"))
      (node (ref "X22") (pin "12") (pinfunction "12_12") (pintype "passive"))
    )
    (net (code "195") (name "Net-(18F-KL)") (class "Default")
      (node (ref "18") (pin "3") (pinfunction "KL_3") (pintype "passive"))
      (node (ref "D99") (pin "2") (pinfunction "-_2") (pintype "passive"))
      (node (ref "LED44") (pin "K") (pinfunction "C_K") (pintype "passive"))
      (node (ref "TP197") (pin "TP") (pinfunction "PP_TP") (pintype "input"))
      (node (ref "X22") (pin "11") (pinfunction "11_11") (pintype "passive"))
    )
    (net (code "196") (name "Net-(18G-KL)") (class "Default")
      (node (ref "18") (pin "4") (pinfunction "KL_4") (pintype "passive"))
      (node (ref "D98") (pin "2") (pinfunction "-_2") (pintype "passive"))
      (node (ref "LED45") (pin "K") (pinfunction "C_K") (pintype "passive"))
      (node (ref "TP198") (pin "TP") (pinfunction "PP_TP") (pintype "input"))
      (node (ref "X22") (pin "10") (pinfunction "10_10") (pintype "passive"))
    )
    (net (code "197") (name "Net-(18H-KL)") (class "Default")
      (node (ref "18") (pin "5") (pinfunction "KL_5") (pintype "passive"))
      (node (ref "D97") (pin "2") (pinfunction "-_2") (pintype "passive"))
      (node (ref "LED46") (pin "K") (pinfunction "C_K") (pintype "passive"))
      (node (ref "TP199") (pin "TP") (pinfunction "PP_TP") (pintype "input"))
      (node (ref "X22") (pin "9") (pinfunction "9_9") (pintype "passive"))
    )
    (net (code "198") (name "Net-(18I-KL)") (class "Default")
      (node (ref "18") (pin "6") (pinfunction "KL_6") (pintype "passive"))
      (node (ref "JP37") (pin "2") (pinfunction "2_2") (pintype "passive"))
      (node (ref "TP200") (pin "TP") (pinfunction "PP_TP") (pintype "input"))
    )
    (net (code "199") (name "Net-(18J-KL)") (class "Default")
      (node (ref "18") (pin "7") (pinfunction "KL_7") (pintype "passive"))
      (node (ref "LED47") (pin "A") (pinfunction "A_A") (pintype "passive"))
      (node (ref "TP201") (pin "TP") (pinfunction "PP_TP") (pintype "input"))
      (node (ref "X22") (pin "8") (pinfunction "8_8") (pintype "passive"))
    )
    (net (code "200") (name "Net-(18K-KL)") (class "Default")
      (node (ref "18") (pin "8") (pinfunction "KL_8") (pintype "passive"))
      (node (ref "D104") (pin "2") (pinfunction "-_2") (pintype "passive"))
      (node (ref "LED48") (pin "K") (pinfunction "C_K") (pintype "passive"))
      (node (ref "TP202") (pin "TP") (pinfunction "PP_TP") (pintype "input"))
      (node (ref "X22") (pin "14") (pinfunction "14_14") (pintype "passive"))
    )
    (net (code "201") (name "Net-(18L-KL)") (class "Default")
      (node (ref "18") (pin "9") (pinfunction "KL_9") (pintype "passive"))
      (node (ref "D98") (pin "1") (pinfunction "+_1") (pintype "passive"))
      (node (ref "D99") (pin "1") (pinfunction "+_1") (pintype "passive"))
      (node (ref "JP38") (pin "1") (pinfunction "1_1") (pintype "passive"))
      (node (ref "JP39") (pin "2") (pinfunction "2_2") (pintype "passive"))
      (node (ref "TP203") (pin "TP") (pinfunction "PP_TP") (pintype "input"))
    )
    (net (code "202") (name "Net-(19A-KL)") (class "Default")
      (node (ref "19") (pin "1") (pinfunction "KL_1") (pintype "passive"))
      (node (ref "D129") (pin "2") (pinfunction "-_2") (pintype "passive"))
      (node (ref "TP208") (pin "TP") (pinfunction "PP_TP") (pintype "input"))
    )
    (net (code "203") (name "Net-(19B-KL)") (class "Default")
      (node (ref "19") (pin "10") (pinfunction "KL_10") (pintype "passive"))
      (node (ref "D118") (pin "2") (pinfunction "-_2") (pintype "passive"))
      (node (ref "D119") (pin "2") (pinfunction "-_2") (pintype "passive"))
      (node (ref "JP45") (pin "1") (pinfunction "1_1") (pintype "passive"))
      (node (ref "TP217") (pin "TP") (pinfunction "PP_TP") (pintype "input"))
    )
    (net (code "204") (name "Net-(19C-KL)") (class "Default")
      (node (ref "19") (pin "11") (pinfunction "KL_11") (pintype "passive"))
      (node (ref "D119") (pin "1") (pinfunction "+_1") (pintype "passive"))
      (node (ref "TP218") (pin "TP") (pinfunction "PP_TP") (pintype "input"))
      (node (ref "X25") (pin "19") (pinfunction "19_19") (pintype "passive"))
    )
    (net (code "205") (name "Net-(19E-KL)") (class "Default")
      (node (ref "19") (pin "2") (pinfunction "KL_2") (pintype "passive"))
      (node (ref "Q86") (pin "2") (pinfunction "C_2") (pintype "passive"))
      (node (ref "TP209") (pin "TP") (pinfunction "PP_TP") (pintype "input"))
    )
    (net (code "206") (name "Net-(19F-KL)") (class "Default")
      (node (ref "19") (pin "3") (pinfunction "KL_3") (pintype "passive"))
      (node (ref "IC75") (pin "11") (pinfunction "O6_11") (pintype "open_collector"))
      (node (ref "TP210") (pin "TP") (pinfunction "PP_TP") (pintype "input"))
    )
    (net (code "207") (name "Net-(19G-KL)") (class "Default")
      (node (ref "19") (pin "4") (pinfunction "KL_4") (pintype "passive"))
      (node (ref "IC75") (pin "10") (pinfunction "O7_10") (pintype "open_collector"))
      (node (ref "TP211") (pin "TP") (pinfunction "PP_TP") (pintype "input"))
    )
    (net (code "208") (name "Net-(19H-KL)") (class "Default")
      (node (ref "19") (pin "5") (pinfunction "KL_5") (pintype "passive"))
      (node (ref "IC75") (pin "12") (pinfunction "O5_12") (pintype "open_collector"))
      (node (ref "TP212") (pin "TP") (pinfunction "PP_TP") (pintype "input"))
    )
    (net (code "209") (name "Net-(19I-KL)") (class "Default")
      (node (ref "19") (pin "6") (pinfunction "KL_6") (pintype "passive"))
      (node (ref "IC75") (pin "13") (pinfunction "O4_13") (pintype "open_collector"))
      (node (ref "TP213") (pin "TP") (pinfunction "PP_TP") (pintype "input"))
    )
    (net (code "210") (name "Net-(19J-KL)") (class "Default")
      (node (ref "19") (pin "7") (pinfunction "KL_7") (pintype "passive"))
      (node (ref "IC75") (pin "14") (pinfunction "O3_14") (pintype "open_collector"))
      (node (ref "TP214") (pin "TP") (pinfunction "PP_TP") (pintype "input"))
    )
    (net (code "211") (name "Net-(19K-KL)") (class "Default")
      (node (ref "19") (pin "8") (pinfunction "KL_8") (pintype "passive"))
      (node (ref "R506") (pin "2") (pinfunction "2_2") (pintype "passive"))
      (node (ref "TP215") (pin "TP") (pinfunction "PP_TP") (pintype "input"))
    )
    (net (code "212") (name "Net-(19L-KL)") (class "Default")
      (node (ref "19") (pin "9") (pinfunction "KL_9") (pintype "passive"))
      (node (ref "D118") (pin "1") (pinfunction "+_1") (pintype "passive"))
      (node (ref "TP216") (pin "TP") (pinfunction "PP_TP") (pintype "input"))
      (node (ref "X25") (pin "17") (pinfunction "17_17") (pintype "passive"))
    )
    (net (code "213") (name "Net-(20B-KL)") (class "Default")
      (node (ref "20") (pin "10") (pinfunction "KL_10") (pintype "passive"))
      (node (ref "TP227") (pin "TP") (pinfunction "PP_TP") (pintype "input"))
      (node (ref "X25") (pin "15") (pinfunction "15_15") (pintype "passive"))
    )
    (net (code "214") (name "Net-(20C-KL)") (class "Default")
      (node (ref "20") (pin "11") (pinfunction "KL_11") (pintype "passive"))
      (node (ref "Q88") (pin "2") (pinfunction "C_2") (pintype "passive"))
      (node (ref "R492") (pin "1") (pinfunction "1_1") (pintype "passive"))
      (node (ref "TP228") (pin "TP") (pinfunction "PP_TP") (pintype "input"))
    )
    (net (code "215") (name "Net-(20D-KL)") (class "Default")
      (node (ref "20") (pin "12") (pinfunction "KL_12") (pintype "passive"))
      (node (ref "R493") (pin "1") (pinfunction "1_1") (pintype "passive"))
      (node (ref "TP230") (pin "TP") (pinfunction "PP_TP") (pintype "input"))
    )
    (net (code "216") (name "Net-(20E-KL)") (class "Default")
      (node (ref "20") (pin "2") (pinfunction "KL_2") (pintype "passive"))
      (node (ref "D123") (pin "2") (pinfunction "-_2") (pintype "passive"))
      (node (ref "LED49") (pin "K") (pinfunction "C_K") (pintype "passive"))
      (node (ref "TP219") (pin "TP") (pinfunction "PP_TP") (pintype "input"))
      (node (ref "X25") (pin "12") (pinfunction "12_12") (pintype "passive"))
    )
    (net (code "217") (name "Net-(20F-KL)") (class "Default")
      (node (ref "20") (pin "3") (pinfunction "KL_3") (pintype "passive"))
      (node (ref "D122") (pin "2") (pinfunction "-_2") (pintype "passive"))
      (node (ref "LED50") (pin "K") (pinfunction "C_K") (pintype "passive"))
      (node (ref "TP220") (pin "TP") (pinfunction "PP_TP") (pintype "input"))
      (node (ref "X25") (pin "11") (pinfunction "11_11") (pintype "passive"))
    )
    (net (code "218") (name "Net-(20G-KL)") (class "Default")
      (node (ref "20") (pin "4") (pinfunction "KL_4") (pintype "passive"))
      (node (ref "D121") (pin "2") (pinfunction "-_2") (pintype "passive"))
      (node (ref "LED51") (pin "K") (pinfunction "C_K") (pintype "passive"))
      (node (ref "TP221") (pin "TP") (pinfunction "PP_TP") (pintype "input"))
      (node (ref "X25") (pin "10") (pinfunction "10_10") (pintype "passive"))
    )
    (net (code "219") (name "Net-(20H-KL)") (class "Default")
      (node (ref "20") (pin "5") (pinfunction "KL_5") (pintype "passive"))
      (node (ref "D120") (pin "2") (pinfunction "-_2") (pintype "passive"))
      (node (ref "LED52") (pin "K") (pinfunction "C_K") (pintype "passive"))
      (node (ref "TP222") (pin "TP") (pinfunction "PP_TP") (pintype "input"))
      (node (ref "X25") (pin "9") (pinfunction "9_9") (pintype "passive"))
    )
    (net (code "220") (name "Net-(20I-KL)") (class "Default")
      (node (ref "20") (pin "6") (pinfunction "KL_6") (pintype "passive"))
      (node (ref "JP42") (pin "2") (pinfunction "2_2") (pintype "passive"))
      (node (ref "TP223") (pin "TP") (pinfunction "PP_TP") (pintype "input"))
    )
    (net (code "221") (name "Net-(20J-KL)") (class "Default")
      (node (ref "20") (pin "7") (pinfunction "KL_7") (pintype "passive"))
      (node (ref "LED53") (pin "A") (pinfunction "A_A") (pintype "passive"))
      (node (ref "TP224") (pin "TP") (pinfunction "PP_TP") (pintype "input"))
      (node (ref "X25") (pin "8") (pinfunction "8_8") (pintype "passive"))
    )
    (net (code "222") (name "Net-(20K-KL)") (class "Default")
      (node (ref "20") (pin "8") (pinfunction "KL_8") (pintype "passive"))
      (node (ref "D124") (pin "2") (pinfunction "-_2") (pintype "passive"))
      (node (ref "LED54") (pin "K") (pinfunction "C_K") (pintype "passive"))
      (node (ref "TP225") (pin "TP") (pinfunction "PP_TP") (pintype "input"))
      (node (ref "X25") (pin "14") (pinfunction "14_14") (pintype "passive"))
    )
    (net (code "223") (name "Net-(20L-KL)") (class "Default")
      (node (ref "20") (pin "9") (pinfunction "KL_9") (pintype "passive"))
      (node (ref "D121") (pin "1") (pinfunction "+_1") (pintype "passive"))
      (node (ref "D122") (pin "1") (pinfunction "+_1") (pintype "passive"))
      (node (ref "JP43") (pin "1") (pinfunction "1_1") (pintype "passive"))
      (node (ref "JP44") (pin "2") (pinfunction "2_2") (pintype "passive"))
      (node (ref "TP226") (pin "TP") (pinfunction "PP_TP") (pintype "input"))
    )
    (net (code "224") (name "Net-(21A-KL)") (class "Default")
      (node (ref "21") (pin "1") (pinfunction "KL_1") (pintype "passive"))
      (node (ref "D142") (pin "2") (pinfunction "-_2") (pintype "passive"))
      (node (ref "TP231") (pin "TP") (pinfunction "PP_TP") (pintype "input"))
    )
    (net (code "225") (name "Net-(21B-KL)") (class "Default")
      (node (ref "21") (pin "10") (pinfunction "KL_10") (pintype "passive"))
      (node (ref "D131") (pin "2") (pinfunction "-_2") (pintype "passive"))
      (node (ref "D132") (pin "2") (pinfunction "-_2") (pintype "passive"))
      (node (ref "JP50") (pin "1") (pinfunction "1_1") (pintype "passive"))
      (node (ref "TP240") (pin "TP") (pinfunction "PP_TP") (pintype "input"))
    )
    (net (code "226") (name "Net-(21C-KL)") (class "Default")
      (node (ref "21") (pin "11") (pinfunction "KL_11") (pintype "passive"))
      (node (ref "D132") (pin "1") (pinfunction "+_1") (pintype "passive"))
      (node (ref "TP241") (pin "TP") (pinfunction "PP_TP") (pintype "input"))
      (node (ref "X28") (pin "19") (pinfunction "19_19") (pintype "passive"))
    )
    (net (code "227") (name "Net-(21E-KL)") (class "Default")
      (node (ref "21") (pin "2") (pinfunction "KL_2") (pintype "passive"))
      (node (ref "Q96") (pin "2") (pinfunction "C_2") (pintype "passive"))
      (node (ref "TP232") (pin "TP") (pinfunction "PP_TP") (pintype "input"))
    )
    (net (code "228") (name "Net-(21F-KL)") (class "Default")
      (node (ref "21") (pin "3") (pinfunction "KL_3") (pintype "passive"))
      (node (ref "IC84") (pin "11") (pinfunction "O6_11") (pintype "open_collector"))
      (node (ref "TP233") (pin "TP") (pinfunction "PP_TP") (pintype "input"))
    )
    (net (code "229") (name "Net-(21G-KL)") (class "Default")
      (node (ref "21") (pin "4") (pinfunction "KL_4") (pintype "passive"))
      (node (ref "IC84") (pin "10") (pinfunction "O7_10") (pintype "open_collector"))
      (node (ref "TP234") (pin "TP") (pinfunction "PP_TP") (pintype "input"))
    )
    (net (code "230") (name "Net-(21H-KL)") (class "Default")
      (node (ref "21") (pin "5") (pinfunction "KL_5") (pintype "passive"))
      (node (ref "IC84") (pin "12") (pinfunction "O5_12") (pintype "open_collector"))
      (node (ref "TP235") (pin "TP") (pinfunction "PP_TP") (pintype "input"))
    )
    (net (code "231") (name "Net-(21I-KL)") (class "Default")
      (node (ref "21") (pin "6") (pinfunction "KL_6") (pintype "passive"))
      (node (ref "IC84") (pin "13") (pinfunction "O4_13") (pintype "open_collector"))
      (node (ref "TP236") (pin "TP") (pinfunction "PP_TP") (pintype "input"))
    )
    (net (code "232") (name "Net-(21J-KL)") (class "Default")
      (node (ref "21") (pin "7") (pinfunction "KL_7") (pintype "passive"))
      (node (ref "IC84") (pin "14") (pinfunction "O3_14") (pintype "open_collector"))
      (node (ref "TP237") (pin "TP") (pinfunction "PP_TP") (pintype "input"))
    )
    (net (code "233") (name "Net-(21K-KL)") (class "Default")
      (node (ref "21") (pin "8") (pinfunction "KL_8") (pintype "passive"))
      (node (ref "R557") (pin "2") (pinfunction "2_2") (pintype "passive"))
      (node (ref "TP238") (pin "TP") (pinfunction "PP_TP") (pintype "input"))
    )
    (net (code "234") (name "Net-(21L-KL)") (class "Default")
      (node (ref "21") (pin "9") (pinfunction "KL_9") (pintype "passive"))
      (node (ref "D131") (pin "1") (pinfunction "+_1") (pintype "passive"))
      (node (ref "TP239") (pin "TP") (pinfunction "PP_TP") (pintype "input"))
      (node (ref "X28") (pin "17") (pinfunction "17_17") (pintype "passive"))
    )
    (net (code "235") (name "Net-(22B-KL)") (class "Default")
      (node (ref "22") (pin "10") (pinfunction "KL_10") (pintype "passive"))
      (node (ref "TP250") (pin "TP") (pinfunction "PP_TP") (pintype "input"))
      (node (ref "X28") (pin "15") (pinfunction "15_15") (pintype "passive"))
    )
    (net (code "236") (name "Net-(22C-KL)") (class "Default")
      (node (ref "22") (pin "11") (pinfunction "KL_11") (pintype "passive"))
      (node (ref "Q98") (pin "2") (pinfunction "C_2") (pintype "passive"))
      (node (ref "R543") (pin "1") (pinfunction "1_1") (pintype "passive"))
      (node (ref "TP251") (pin "TP") (pinfunction "PP_TP") (pintype "input"))
    )
    (net (code "237") (name "Net-(22D-KL)") (class "Default")
      (node (ref "22") (pin "12") (pinfunction "KL_12") (pintype "passive"))
      (node (ref "R544") (pin "1") (pinfunction "1_1") (pintype "passive"))
      (node (ref "TP253") (pin "TP") (pinfunction "PP_TP") (pintype "input"))
    )
    (net (code "238") (name "Net-(22E-KL)") (class "Default")
      (node (ref "22") (pin "2") (pinfunction "KL_2") (pintype "passive"))
      (node (ref "D136") (pin "2") (pinfunction "-_2") (pintype "passive"))
      (node (ref "LED55") (pin "K") (pinfunction "C_K") (pintype "passive"))
      (node (ref "TP242") (pin "TP") (pinfunction "PP_TP") (pintype "input"))
      (node (ref "X28") (pin "12") (pinfunction "12_12") (pintype "passive"))
    )
    (net (code "239") (name "Net-(22F-KL)") (class "Default")
      (node (ref "22") (pin "3") (pinfunction "KL_3") (pintype "passive"))
      (node (ref "D135") (pin "2") (pinfunction "-_2") (pintype "passive"))
      (node (ref "LED56") (pin "K") (pinfunction "C_K") (pintype "passive"))
      (node (ref "TP243") (pin "TP") (pinfunction "PP_TP") (pintype "input"))
      (node (ref "X28") (pin "11") (pinfunction "11_11") (pintype "passive"))
    )
    (net (code "240") (name "Net-(22G-KL)") (class "Default")
      (node (ref "22") (pin "4") (pinfunction "KL_4") (pintype "passive"))
      (node (ref "D134") (pin "2") (pinfunction "-_2") (pintype "passive"))
      (node (ref "LED57") (pin "K") (pinfunction "C_K") (pintype "passive"))
      (node (ref "TP244") (pin "TP") (pinfunction "PP_TP") (pintype "input"))
      (node (ref "X28") (pin "10") (pinfunction "10_10") (pintype "passive"))
    )
    (net (code "241") (name "Net-(22H-KL)") (class "Default")
      (node (ref "22") (pin "5") (pinfunction "KL_5") (pintype "passive"))
      (node (ref "D133") (pin "2") (pinfunction "-_2") (pintype "passive"))
      (node (ref "LED58") (pin "K") (pinfunction "C_K") (pintype "passive"))
      (node (ref "TP245") (pin "TP") (pinfunction "PP_TP") (pintype "input"))
      (node (ref "X28") (pin "9") (pinfunction "9_9") (pintype "passive"))
    )
    (net (code "242") (name "Net-(22I-KL)") (class "Default")
      (node (ref "22") (pin "6") (pinfunction "KL_6") (pintype "passive"))
      (node (ref "JP47") (pin "2") (pinfunction "2_2") (pintype "passive"))
      (node (ref "TP246") (pin "TP") (pinfunction "PP_TP") (pintype "input"))
    )
    (net (code "243") (name "Net-(22J-KL)") (class "Default")
      (node (ref "22") (pin "7") (pinfunction "KL_7") (pintype "passive"))
      (node (ref "LED59") (pin "A") (pinfunction "A_A") (pintype "passive"))
      (node (ref "TP247") (pin "TP") (pinfunction "PP_TP") (pintype "input"))
      (node (ref "X28") (pin "8") (pinfunction "8_8") (pintype "passive"))
    )
    (net (code "244") (name "Net-(22K-KL)") (class "Default")
      (node (ref "22") (pin "8") (pinfunction "KL_8") (pintype "passive"))
      (node (ref "D137") (pin "2") (pinfunction "-_2") (pintype "passive"))
      (node (ref "LED60") (pin "K") (pinfunction "C_K") (pintype "passive"))
      (node (ref "TP248") (pin "TP") (pinfunction "PP_TP") (pintype "input"))
      (node (ref "X28") (pin "14") (pinfunction "14_14") (pintype "passive"))
    )
    (net (code "245") (name "Net-(22L-KL)") (class "Default")
      (node (ref "22") (pin "9") (pinfunction "KL_9") (pintype "passive"))
      (node (ref "D134") (pin "1") (pinfunction "+_1") (pintype "passive"))
      (node (ref "D135") (pin "1") (pinfunction "+_1") (pintype "passive"))
      (node (ref "JP48") (pin "1") (pinfunction "1_1") (pintype "passive"))
      (node (ref "JP49") (pin "2") (pinfunction "2_2") (pintype "passive"))
      (node (ref "TP249") (pin "TP") (pinfunction "PP_TP") (pintype "input"))
    )
    (net (code "246") (name "Net-(23A-KL)") (class "Default")
      (node (ref "23") (pin "1") (pinfunction "KL_1") (pintype "passive"))
      (node (ref "D155") (pin "2") (pinfunction "-_2") (pintype "passive"))
      (node (ref "TP254") (pin "TP") (pinfunction "PP_TP") (pintype "input"))
    )
    (net (code "247") (name "Net-(23B-KL)") (class "Default")
      (node (ref "23") (pin "10") (pinfunction "KL_10") (pintype "passive"))
      (node (ref "D144") (pin "2") (pinfunction "-_2") (pintype "passive"))
      (node (ref "D145") (pin "2") (pinfunction "-_2") (pintype "passive"))
      (node (ref "JP55") (pin "1") (pinfunction "1_1") (pintype "passive"))
      (node (ref "TP263") (pin "TP") (pinfunction "PP_TP") (pintype "input"))
    )
    (net (code "248") (name "Net-(23C-KL)") (class "Default")
      (node (ref "23") (pin "11") (pinfunction "KL_11") (pintype "passive"))
      (node (ref "D145") (pin "1") (pinfunction "+_1") (pintype "passive"))
      (node (ref "TP264") (pin "TP") (pinfunction "PP_TP") (pintype "input"))
      (node (ref "X31") (pin "19") (pinfunction "19_19") (pintype "passive"))
    )
    (net (code "249") (name "Net-(23E-KL)") (class "Default")
      (node (ref "23") (pin "2") (pinfunction "KL_2") (pintype "passive"))
      (node (ref "Q113") (pin "2") (pinfunction "C_2") (pintype "passive"))
      (node (ref "TP255") (pin "TP") (pinfunction "PP_TP") (pintype "input"))
    )
    (net (code "250") (name "Net-(23F-KL)") (class "Default")
      (node (ref "23") (pin "3") (pinfunction "KL_3") (pintype "passive"))
      (node (ref "IC93") (pin "11") (pinfunction "O6_11") (pintype "open_collector"))
      (node (ref "TP256") (pin "TP") (pinfunction "PP_TP") (pintype "input"))
    )
    (net (code "251") (name "Net-(23G-KL)") (class "Default")
      (node (ref "23") (pin "4") (pinfunction "KL_4") (pintype "passive"))
      (node (ref "IC93") (pin "10") (pinfunction "O7_10") (pintype "open_collector"))
      (node (ref "TP257") (pin "TP") (pinfunction "PP_TP") (pintype "input"))
    )
    (net (code "252") (name "Net-(23H-KL)") (class "Default")
      (node (ref "23") (pin "5") (pinfunction "KL_5") (pintype "passive"))
      (node (ref "IC93") (pin "12") (pinfunction "O5_12") (pintype "open_collector"))
      (node (ref "TP258") (pin "TP") (pinfunction "PP_TP") (pintype "input"))
    )
    (net (code "253") (name "Net-(23I-KL)") (class "Default")
      (node (ref "23") (pin "6") (pinfunction "KL_6") (pintype "passive"))
      (node (ref "IC93") (pin "13") (pinfunction "O4_13") (pintype "open_collector"))
      (node (ref "TP259") (pin "TP") (pinfunction "PP_TP") (pintype "input"))
    )
    (net (code "254") (name "Net-(23J-KL)") (class "Default")
      (node (ref "23") (pin "7") (pinfunction "KL_7") (pintype "passive"))
      (node (ref "IC93") (pin "14") (pinfunction "O3_14") (pintype "open_collector"))
      (node (ref "TP260") (pin "TP") (pinfunction "PP_TP") (pintype "input"))
    )
    (net (code "255") (name "Net-(23K-KL)") (class "Default")
      (node (ref "23") (pin "8") (pinfunction "KL_8") (pintype "passive"))
      (node (ref "R608") (pin "2") (pinfunction "2_2") (pintype "passive"))
      (node (ref "TP261") (pin "TP") (pinfunction "PP_TP") (pintype "input"))
    )
    (net (code "256") (name "Net-(23L-KL)") (class "Default")
      (node (ref "23") (pin "9") (pinfunction "KL_9") (pintype "passive"))
      (node (ref "D144") (pin "1") (pinfunction "+_1") (pintype "passive"))
      (node (ref "TP262") (pin "TP") (pinfunction "PP_TP") (pintype "input"))
      (node (ref "X31") (pin "17") (pinfunction "17_17") (pintype "passive"))
    )
    (net (code "257") (name "Net-(24B-KL)") (class "Default")
      (node (ref "24") (pin "10") (pinfunction "KL_10") (pintype "passive"))
      (node (ref "TP273") (pin "TP") (pinfunction "PP_TP") (pintype "input"))
      (node (ref "X31") (pin "15") (pinfunction "15_15") (pintype "passive"))
    )
    (net (code "258") (name "Net-(24C-KL)") (class "Default")
      (node (ref "24") (pin "11") (pinfunction "KL_11") (pintype "passive"))
      (node (ref "Q115") (pin "2") (pinfunction "C_2") (pintype "passive"))
      (node (ref "R594") (pin "1") (pinfunction "1_1") (pintype "passive"))
      (node (ref "TP274") (pin "TP") (pinfunction "PP_TP") (pintype "input"))
    )
    (net (code "259") (name "Net-(24D-KL)") (class "Default")
      (node (ref "24") (pin "12") (pinfunction "KL_12") (pintype "passive"))
      (node (ref "R595") (pin "1") (pinfunction "1_1") (pintype "passive"))
      (node (ref "TP276") (pin "TP") (pinfunction "PP_TP") (pintype "input"))
    )
    (net (code "260") (name "Net-(24E-KL)") (class "Default")
      (node (ref "24") (pin "2") (pinfunction "KL_2") (pintype "passive"))
      (node (ref "D149") (pin "2") (pinfunction "-_2") (pintype "passive"))
      (node (ref "LED61") (pin "K") (pinfunction "C_K") (pintype "passive"))
      (node (ref "TP265") (pin "TP") (pinfunction "PP_TP") (pintype "input"))
      (node (ref "X31") (pin "12") (pinfunction "12_12") (pintype "passive"))
    )
    (net (code "261") (name "Net-(24F-KL)") (class "Default")
      (node (ref "24") (pin "3") (pinfunction "KL_3") (pintype "passive"))
      (node (ref "D148") (pin "2") (pinfunction "-_2") (pintype "passive"))
      (node (ref "LED62") (pin "K") (pinfunction "C_K") (pintype "passive"))
      (node (ref "TP266") (pin "TP") (pinfunction "PP_TP") (pintype "input"))
      (node (ref "X31") (pin "11") (pinfunction "11_11") (pintype "passive"))
    )
    (net (code "262") (name "Net-(24G-KL)") (class "Default")
      (node (ref "24") (pin "4") (pinfunction "KL_4") (pintype "passive"))
      (node (ref "D147") (pin "2") (pinfunction "-_2") (pintype "passive"))
      (node (ref "LED63") (pin "K") (pinfunction "C_K") (pintype "passive"))
      (node (ref "TP267") (pin "TP") (pinfunction "PP_TP") (pintype "input"))
      (node (ref "X31") (pin "10") (pinfunction "10_10") (pintype "passive"))
    )
    (net (code "263") (name "Net-(24H-KL)") (class "Default")
      (node (ref "24") (pin "5") (pinfunction "KL_5") (pintype "passive"))
      (node (ref "D146") (pin "2") (pinfunction "-_2") (pintype "passive"))
      (node (ref "LED64") (pin "K") (pinfunction "C_K") (pintype "passive"))
      (node (ref "TP268") (pin "TP") (pinfunction "PP_TP") (pintype "input"))
      (node (ref "X31") (pin "9") (pinfunction "9_9") (pintype "passive"))
    )
    (net (code "264") (name "Net-(24I-KL)") (class "Default")
      (node (ref "24") (pin "6") (pinfunction "KL_6") (pintype "passive"))
      (node (ref "JP52") (pin "2") (pinfunction "2_2") (pintype "passive"))
      (node (ref "TP269") (pin "TP") (pinfunction "PP_TP") (pintype "input"))
    )
    (net (code "265") (name "Net-(24J-KL)") (class "Default")
      (node (ref "24") (pin "7") (pinfunction "KL_7") (pintype "passive"))
      (node (ref "LED65") (pin "A") (pinfunction "A_A") (pintype "passive"))
      (node (ref "TP270") (pin "TP") (pinfunction "PP_TP") (pintype "input"))
      (node (ref "X31") (pin "8") (pinfunction "8_8") (pintype "passive"))
    )
    (net (code "266") (name "Net-(24K-KL)") (class "Default")
      (node (ref "24") (pin "8") (pinfunction "KL_8") (pintype "passive"))
      (node (ref "D150") (pin "2") (pinfunction "-_2") (pintype "passive"))
      (node (ref "LED66") (pin "K") (pinfunction "C_K") (pintype "passive"))
      (node (ref "TP271") (pin "TP") (pinfunction "PP_TP") (pintype "input"))
      (node (ref "X31") (pin "14") (pinfunction "14_14") (pintype "passive"))
    )
    (net (code "267") (name "Net-(24L-KL)") (class "Default")
      (node (ref "24") (pin "9") (pinfunction "KL_9") (pintype "passive"))
      (node (ref "D147") (pin "1") (pinfunction "+_1") (pintype "passive"))
      (node (ref "D148") (pin "1") (pinfunction "+_1") (pintype "passive"))
      (node (ref "JP53") (pin "1") (pinfunction "1_1") (pintype "passive"))
      (node (ref "JP54") (pin "2") (pinfunction "2_2") (pintype "passive"))
      (node (ref "TP272") (pin "TP") (pinfunction "PP_TP") (pintype "input"))
    )
    (net (code "268") (name "Net-(C1-Pad1)") (class "Default")
      (node (ref "C1") (pin "1") (pinfunction "1_1") (pintype "passive"))
      (node (ref "R22") (pin "1") (pinfunction "1_1") (pintype "passive"))
      (node (ref "R23") (pin "2") (pinfunction "2_2") (pintype "passive"))
    )
    (net (code "269") (name "Net-(C11-Pad1)") (class "Default")
      (node (ref "C11") (pin "1") (pinfunction "1_1") (pintype "passive"))
      (node (ref "R50") (pin "1") (pinfunction "1_1") (pintype "passive"))
      (node (ref "R51") (pin "1") (pinfunction "1_1") (pintype "passive"))
    )
    (net (code "270") (name "Net-(C14-Pad1)") (class "Default")
      (node (ref "C14") (pin "1") (pinfunction "1_1") (pintype "passive"))
      (node (ref "R77") (pin "1") (pinfunction "1_1") (pintype "passive"))
      (node (ref "R78") (pin "2") (pinfunction "2_2") (pintype "passive"))
    )
    (net (code "271") (name "Net-(C24-Pad1)") (class "Default")
      (node (ref "C24") (pin "1") (pinfunction "1_1") (pintype "passive"))
      (node (ref "R149") (pin "1") (pinfunction "1_1") (pintype "passive"))
      (node (ref "R150") (pin "1") (pinfunction "1_1") (pintype "passive"))
    )
    (net (code "272") (name "Net-(C27-Pad1)") (class "Default")
      (node (ref "C27") (pin "1") (pinfunction "1_1") (pintype "passive"))
      (node (ref "R176") (pin "1") (pinfunction "1_1") (pintype "passive"))
      (node (ref "R177") (pin "2") (pinfunction "2_2") (pintype "passive"))
    )
    (net (code "273") (name "Net-(C36-Pad1)") (class "Default")
      (node (ref "C36") (pin "1") (pinfunction "1_1") (pintype "passive"))
      (node (ref "R204") (pin "1") (pinfunction "1_1") (pintype "passive"))
      (node (ref "R205") (pin "1") (pinfunction "1_1") (pintype "passive"))
    )
    (net (code "274") (name "Net-(C39-Pad1)") (class "Default")
      (node (ref "C39") (pin "1") (pinfunction "1_1") (pintype "passive"))
      (node (ref "R231") (pin "1") (pinfunction "1_1") (pintype "passive"))
      (node (ref "R232") (pin "2") (pinfunction "2_2") (pintype "passive"))
    )
    (net (code "275") (name "Net-(C48-Pad1)") (class "Default")
      (node (ref "C48") (pin "1") (pinfunction "1_1") (pintype "passive"))
      (node (ref "R259") (pin "1") (pinfunction "1_1") (pintype "passive"))
      (node (ref "R260") (pin "1") (pinfunction "1_1") (pintype "passive"))
    )
    (net (code "276") (name "Net-(C51-Pad1)") (class "Default")
      (node (ref "C51") (pin "1") (pinfunction "1_1") (pintype "passive"))
      (node (ref "R286") (pin "1") (pinfunction "1_1") (pintype "passive"))
      (node (ref "R287") (pin "2") (pinfunction "2_2") (pintype "passive"))
    )
    (net (code "277") (name "Net-(C60-Pad1)") (class "Default")
      (node (ref "C60") (pin "1") (pinfunction "1_1") (pintype "passive"))
      (node (ref "R314") (pin "1") (pinfunction "1_1") (pintype "passive"))
      (node (ref "R315") (pin "1") (pinfunction "1_1") (pintype "passive"))
    )
    (net (code "278") (name "Net-(C63-Pad1)") (class "Default")
      (node (ref "C63") (pin "1") (pinfunction "1_1") (pintype "passive"))
      (node (ref "R143") (pin "1") (pinfunction "1_1") (pintype "passive"))
      (node (ref "R144") (pin "2") (pinfunction "2_2") (pintype "passive"))
    )
    (net (code "279") (name "Net-(C72-Pad1)") (class "Default")
      (node (ref "C72") (pin "1") (pinfunction "1_1") (pintype "passive"))
      (node (ref "R341") (pin "1") (pinfunction "1_1") (pintype "passive"))
      (node (ref "R342") (pin "1") (pinfunction "1_1") (pintype "passive"))
    )
    (net (code "280") (name "Net-(C75-Pad1)") (class "Default")
      (node (ref "C75") (pin "1") (pinfunction "1_1") (pintype "passive"))
      (node (ref "R368") (pin "1") (pinfunction "1_1") (pintype "passive"))
      (node (ref "R369") (pin "2") (pinfunction "2_2") (pintype "passive"))
    )
    (net (code "281") (name "Net-(C84-Pad1)") (class "Default")
      (node (ref "C84") (pin "1") (pinfunction "1_1") (pintype "passive"))
      (node (ref "R392") (pin "1") (pinfunction "1_1") (pintype "passive"))
      (node (ref "R393") (pin "1") (pinfunction "1_1") (pintype "passive"))
    )
    (net (code "282") (name "Net-(C87-Pad1)") (class "Default")
      (node (ref "C87") (pin "1") (pinfunction "1_1") (pintype "passive"))
      (node (ref "R419") (pin "1") (pinfunction "1_1") (pintype "passive"))
      (node (ref "R420") (pin "2") (pinfunction "2_2") (pintype "passive"))
    )
    (net (code "283") (name "Net-(C96-Pad1)") (class "Default")
      (node (ref "C96") (pin "1") (pinfunction "1_1") (pintype "passive"))
      (node (ref "R443") (pin "1") (pinfunction "1_1") (pintype "passive"))
      (node (ref "R444") (pin "1") (pinfunction "1_1") (pintype "passive"))
    )
    (net (code "284") (name "Net-(C99-Pad1)") (class "Default")
      (node (ref "C99") (pin "1") (pinfunction "1_1") (pintype "passive"))
      (node (ref "R470") (pin "1") (pinfunction "1_1") (pintype "passive"))
      (node (ref "R471") (pin "2") (pinfunction "2_2") (pintype "passive"))
    )
    (net (code "285") (name "Net-(C103-Pad1)") (class "Default")
      (node (ref "C103") (pin "1") (pinfunction "1_1") (pintype "passive"))
      (node (ref "R108") (pin "1") (pinfunction "1_1") (pintype "passive"))
      (node (ref "R112") (pin "1") (pinfunction "1_1") (pintype "passive"))
    )
    (net (code "286") (name "Net-(C107-Pad1)") (class "Default")
      (node (ref "C107") (pin "1") (pinfunction "1_1") (pintype "passive"))
      (node (ref "R125") (pin "1") (pinfunction "1_1") (pintype "passive"))
      (node (ref "R130") (pin "2") (pinfunction "2_2") (pintype "passive"))
    )
    (net (code "287") (name "Net-(C118-Pad1)") (class "Default")
      (node (ref "C118") (pin "1") (pinfunction "1_1") (pintype "passive"))
      (node (ref "R494") (pin "1") (pinfunction "1_1") (pintype "passive"))
      (node (ref "R495") (pin "1") (pinfunction "1_1") (pintype "passive"))
    )
    (net (code "288") (name "Net-(C121-Pad1)") (class "Default")
      (node (ref "C121") (pin "1") (pinfunction "1_1") (pintype "passive"))
      (node (ref "R521") (pin "1") (pinfunction "1_1") (pintype "passive"))
      (node (ref "R522") (pin "2") (pinfunction "2_2") (pintype "passive"))
    )
    (net (code "289") (name "Net-(C130-Pad1)") (class "Default")
      (node (ref "C130") (pin "1") (pinfunction "1_1") (pintype "passive"))
      (node (ref "R545") (pin "1") (pinfunction "1_1") (pintype "passive"))
      (node (ref "R546") (pin "1") (pinfunction "1_1") (pintype "passive"))
    )
    (net (code "290") (name "Net-(C133-Pad1)") (class "Default")
      (node (ref "C133") (pin "1") (pinfunction "1_1") (pintype "passive"))
      (node (ref "R572") (pin "1") (pinfunction "1_1") (pintype "passive"))
      (node (ref "R573") (pin "2") (pinfunction "2_2") (pintype "passive"))
    )
    (net (code "291") (name "Net-(C142-Pad1)") (class "Default")
      (node (ref "C142") (pin "1") (pinfunction "1_1") (pintype "passive"))
      (node (ref "R596") (pin "1") (pinfunction "1_1") (pintype "passive"))
      (node (ref "R597") (pin "1") (pinfunction "1_1") (pintype "passive"))
    )
    (net (code "292") (name "Net-(D1--)") (class "Default")
      (node (ref "D1") (pin "2") (pinfunction "-_2") (pintype "passive"))
      (node (ref "R12") (pin "1") (pinfunction "1_1") (pintype "passive"))
      (node (ref "R13") (pin "1") (pinfunction "1_1") (pintype "passive"))
    )
    (net (code "293") (name "Net-(D2-+)") (class "Default")
      (node (ref "D2") (pin "1") (pinfunction "+_1") (pintype "passive"))
      (node (ref "X101") (pin "1") (pinfunction "1_1") (pintype "passive"))
    )
    (net (code "294") (name "Net-(D6-+)") (class "Default")
      (node (ref "D6") (pin "1") (pinfunction "+_1") (pintype "passive"))
      (node (ref "R7") (pin "1") (pinfunction "1_1") (pintype "passive"))
    )
    (net (code "295") (name "Net-(D9-+)") (class "Default")
      (node (ref "D9") (pin "1") (pinfunction "+_1") (pintype "passive"))
      (node (ref "JP3") (pin "2") (pinfunction "2_2") (pintype "passive"))
    )
    (net (code "296") (name "Net-(D10-+)") (class "Default")
      (node (ref "D10") (pin "1") (pinfunction "+_1") (pintype "passive"))
      (node (ref "JP4") (pin "1") (pinfunction "1_1") (pintype "passive"))
    )
    (net (code "297") (name "Net-(D11--)") (class "Default")
      (node (ref "D11") (pin "2") (pinfunction "-_2") (pintype "passive"))
      (node (ref "Q4") (pin "2") (pinfunction "C_2") (pintype "passive"))
      (node (ref "START1") (pin "TP") (pinfunction "PP_TP") (pintype "input"))
      (node (ref "X1") (pin "5") (pinfunction "5_5") (pintype "passive"))
    )
    (net (code "298") (name "Net-(D12-+)") (class "Default")
      (node (ref "D12") (pin "1") (pinfunction "+_1") (pintype "passive"))
      (node (ref "R44") (pin "1") (pinfunction "1_1") (pintype "passive"))
    )
    (net (code "299") (name "Net-(D12--)") (class "Default")
      (node (ref "C8") (pin "2") (pinfunction "2_2") (pintype "passive"))
      (node (ref "D12") (pin "2") (pinfunction "-_2") (pintype "passive"))
      (node (ref "D17") (pin "C") (pinfunction "C_C") (pintype "passive"))
      (node (ref "IC6") (pin "2") (pinfunction "TR_2") (pintype "input"))
      (node (ref "IC6") (pin "6") (pinfunction "THR_6") (pintype "input"))
      (node (ref "R42") (pin "1") (pinfunction "1_1") (pintype "passive"))
    )
    (net (code "300") (name "Net-(D15--)") (class "Default")
      (node (ref "D15") (pin "2") (pinfunction "-_2") (pintype "passive"))
      (node (ref "R65") (pin "1") (pinfunction "1_1") (pintype "passive"))
      (node (ref "R66") (pin "1") (pinfunction "1_1") (pintype "passive"))
    )
    (net (code "301") (name "Net-(D16-+)") (class "Default")
      (node (ref "D16") (pin "1") (pinfunction "+_1") (pintype "passive"))
      (node (ref "X1") (pin "1") (pinfunction "1_1") (pintype "passive"))
    )
    (net (code "302") (name "Net-(D20-+)") (class "Default")
      (node (ref "D20") (pin "1") (pinfunction "+_1") (pintype "passive"))
      (node (ref "R67") (pin "1") (pinfunction "1_1") (pintype "passive"))
    )
    (net (code "303") (name "Net-(D23-+)") (class "Default")
      (node (ref "D23") (pin "1") (pinfunction "+_1") (pintype "passive"))
      (node (ref "JP8") (pin "2") (pinfunction "2_2") (pintype "passive"))
    )
    (net (code "304") (name "Net-(D24-+)") (class "Default")
      (node (ref "D24") (pin "1") (pinfunction "+_1") (pintype "passive"))
      (node (ref "JP9") (pin "1") (pinfunction "1_1") (pintype "passive"))
    )
    (net (code "305") (name "Net-(D25--)") (class "Default")
      (node (ref "D25") (pin "2") (pinfunction "-_2") (pintype "passive"))
      (node (ref "Q14") (pin "2") (pinfunction "C_2") (pintype "passive"))
      (node (ref "START2") (pin "TP") (pinfunction "PP_TP") (pintype "input"))
      (node (ref "X4") (pin "5") (pinfunction "5_5") (pintype "passive"))
    )
    (net (code "306") (name "Net-(D26-+)") (class "Default")
      (node (ref "D26") (pin "1") (pinfunction "+_1") (pintype "passive"))
      (node (ref "R99") (pin "1") (pinfunction "1_1") (pintype "passive"))
    )
    (net (code "307") (name "Net-(D26--)") (class "Default")
      (node (ref "C21") (pin "2") (pinfunction "2_2") (pintype "passive"))
      (node (ref "D26") (pin "2") (pinfunction "-_2") (pintype "passive"))
      (node (ref "D31") (pin "C") (pinfunction "C_C") (pintype "passive"))
      (node (ref "IC15") (pin "2") (pinfunction "TR_2") (pintype "input"))
      (node (ref "IC15") (pin "6") (pinfunction "THR_6") (pintype "input"))
      (node (ref "R97") (pin "1") (pinfunction "1_1") (pintype "passive"))
    )
    (net (code "308") (name "Net-(D29--)") (class "Default")
      (node (ref "D29") (pin "2") (pinfunction "-_2") (pintype "passive"))
      (node (ref "R164") (pin "1") (pinfunction "1_1") (pintype "passive"))
      (node (ref "R165") (pin "1") (pinfunction "1_1") (pintype "passive"))
    )
    (net (code "309") (name "Net-(D30-+)") (class "Default")
      (node (ref "D30") (pin "1") (pinfunction "+_1") (pintype "passive"))
      (node (ref "X4") (pin "1") (pinfunction "1_1") (pintype "passive"))
    )
    (net (code "310") (name "Net-(D34-+)") (class "Default")
      (node (ref "D34") (pin "1") (pinfunction "+_1") (pintype "passive"))
      (node (ref "R166") (pin "1") (pinfunction "1_1") (pintype "passive"))
    )
    (net (code "311") (name "Net-(D37-+)") (class "Default")
      (node (ref "D37") (pin "1") (pinfunction "+_1") (pintype "passive"))
      (node (ref "JP13") (pin "2") (pinfunction "2_2") (pintype "passive"))
    )
    (net (code "312") (name "Net-(D38-+)") (class "Default")
      (node (ref "D38") (pin "1") (pinfunction "+_1") (pintype "passive"))
      (node (ref "JP14") (pin "1") (pinfunction "1_1") (pintype "passive"))
    )
    (net (code "313") (name "Net-(D39--)") (class "Default")
      (node (ref "D39") (pin "2") (pinfunction "-_2") (pintype "passive"))
      (node (ref "Q24") (pin "2") (pinfunction "C_2") (pintype "passive"))
      (node (ref "START3") (pin "TP") (pinfunction "PP_TP") (pintype "input"))
      (node (ref "X7") (pin "5") (pinfunction "5_5") (pintype "passive"))
    )
    (net (code "314") (name "Net-(D40-+)") (class "Default")
      (node (ref "D40") (pin "1") (pinfunction "+_1") (pintype "passive"))
      (node (ref "R198") (pin "1") (pinfunction "1_1") (pintype "passive"))
    )
    (net (code "315") (name "Net-(D40--)") (class "Default")
      (node (ref "C33") (pin "2") (pinfunction "2_2") (pintype "passive"))
      (node (ref "D40") (pin "2") (pinfunction "-_2") (pintype "passive"))
      (node (ref "D45") (pin "C") (pinfunction "C_C") (pintype "passive"))
      (node (ref "IC24") (pin "2") (pinfunction "TR_2") (pintype "input"))
      (node (ref "IC24") (pin "6") (pinfunction "THR_6") (pintype "input"))
      (node (ref "R196") (pin "1") (pinfunction "1_1") (pintype "passive"))
    )
    (net (code "316") (name "Net-(D42-+)") (class "Default")
      (node (ref "D42") (pin "1") (pinfunction "+_1") (pintype "passive"))
      (node (ref "R31") (pin "1") (pinfunction "1_1") (pintype "passive"))
    )
    (net (code "317") (name "Net-(D43--)") (class "Default")
      (node (ref "D43") (pin "2") (pinfunction "-_2") (pintype "passive"))
      (node (ref "R219") (pin "1") (pinfunction "1_1") (pintype "passive"))
      (node (ref "R220") (pin "1") (pinfunction "1_1") (pintype "passive"))
    )
    (net (code "318") (name "Net-(D44-+)") (class "Default")
      (node (ref "D44") (pin "1") (pinfunction "+_1") (pintype "passive"))
      (node (ref "X7") (pin "1") (pinfunction "1_1") (pintype "passive"))
    )
    (net (code "319") (name "Net-(D48-+)") (class "Default")
      (node (ref "D48") (pin "1") (pinfunction "+_1") (pintype "passive"))
      (node (ref "R221") (pin "1") (pinfunction "1_1") (pintype "passive"))
    )
    (net (code "320") (name "Net-(D51-+)") (class "Default")
      (node (ref "D51") (pin "1") (pinfunction "+_1") (pintype "passive"))
      (node (ref "JP18") (pin "2") (pinfunction "2_2") (pintype "passive"))
    )
    (net (code "321") (name "Net-(D52-+)") (class "Default")
      (node (ref "D52") (pin "1") (pinfunction "+_1") (pintype "passive"))
      (node (ref "JP19") (pin "1") (pinfunction "1_1") (pintype "passive"))
    )
    (net (code "322") (name "Net-(D53--)") (class "Default")
      (node (ref "D53") (pin "2") (pinfunction "-_2") (pintype "passive"))
      (node (ref "Q34") (pin "2") (pinfunction "C_2") (pintype "passive"))
      (node (ref "START4") (pin "TP") (pinfunction "PP_TP") (pintype "input"))
      (node (ref "X10") (pin "5") (pinfunction "5_5") (pintype "passive"))
    )
    (net (code "323") (name "Net-(D54-+)") (class "Default")
      (node (ref "D54") (pin "1") (pinfunction "+_1") (pintype "passive"))
      (node (ref "R253") (pin "1") (pinfunction "1_1") (pintype "passive"))
    )
    (net (code "324") (name "Net-(D54--)") (class "Default")
      (node (ref "C45") (pin "2") (pinfunction "2_2") (pintype "passive"))
      (node (ref "D54") (pin "2") (pinfunction "-_2") (pintype "passive"))
      (node (ref "D59") (pin "C") (pinfunction "C_C") (pintype "passive"))
      (node (ref "IC33") (pin "2") (pinfunction "TR_2") (pintype "input"))
      (node (ref "IC33") (pin "6") (pinfunction "THR_6") (pintype "input"))
      (node (ref "R251") (pin "1") (pinfunction "1_1") (pintype "passive"))
    )
    (net (code "325") (name "Net-(D57--)") (class "Default")
      (node (ref "D57") (pin "2") (pinfunction "-_2") (pintype "passive"))
      (node (ref "R274") (pin "1") (pinfunction "1_1") (pintype "passive"))
      (node (ref "R275") (pin "1") (pinfunction "1_1") (pintype "passive"))
    )
    (net (code "326") (name "Net-(D58-+)") (class "Default")
      (node (ref "D58") (pin "1") (pinfunction "+_1") (pintype "passive"))
      (node (ref "X10") (pin "1") (pinfunction "1_1") (pintype "passive"))
    )
    (net (code "327") (name "Net-(D62-+)") (class "Default")
      (node (ref "D62") (pin "1") (pinfunction "+_1") (pintype "passive"))
      (node (ref "R276") (pin "1") (pinfunction "1_1") (pintype "passive"))
    )
    (net (code "328") (name "Net-(D65-+)") (class "Default")
      (node (ref "D65") (pin "1") (pinfunction "+_1") (pintype "passive"))
      (node (ref "JP23") (pin "2") (pinfunction "2_2") (pintype "passive"))
    )
    (net (code "329") (name "Net-(D66-+)") (class "Default")
      (node (ref "D66") (pin "1") (pinfunction "+_1") (pintype "passive"))
      (node (ref "JP24") (pin "1") (pinfunction "1_1") (pintype "passive"))
    )
    (net (code "330") (name "Net-(D67--)") (class "Default")
      (node (ref "D67") (pin "2") (pinfunction "-_2") (pintype "passive"))
      (node (ref "Q44") (pin "2") (pinfunction "C_2") (pintype "passive"))
      (node (ref "START5") (pin "TP") (pinfunction "PP_TP") (pintype "input"))
      (node (ref "X13") (pin "5") (pinfunction "5_5") (pintype "passive"))
    )
    (net (code "331") (name "Net-(D68-+)") (class "Default")
      (node (ref "D68") (pin "1") (pinfunction "+_1") (pintype "passive"))
      (node (ref "R308") (pin "1") (pinfunction "1_1") (pintype "passive"))
    )
    (net (code "332") (name "Net-(D68--)") (class "Default")
      (node (ref "C57") (pin "2") (pinfunction "2_2") (pintype "passive"))
      (node (ref "D68") (pin "2") (pinfunction "-_2") (pintype "passive"))
      (node (ref "D73") (pin "C") (pinfunction "C_C") (pintype "passive"))
      (node (ref "IC42") (pin "2") (pinfunction "TR_2") (pintype "input"))
      (node (ref "IC42") (pin "6") (pinfunction "THR_6") (pintype "input"))
      (node (ref "R306") (pin "1") (pinfunction "1_1") (pintype "passive"))
    )
    (net (code "333") (name "Net-(D71--)") (class "Default")
      (node (ref "D71") (pin "2") (pinfunction "-_2") (pintype "passive"))
      (node (ref "R329") (pin "1") (pinfunction "1_1") (pintype "passive"))
      (node (ref "R330") (pin "1") (pinfunction "1_1") (pintype "passive"))
    )
    (net (code "334") (name "Net-(D72-+)") (class "Default")
      (node (ref "D72") (pin "1") (pinfunction "+_1") (pintype "passive"))
      (node (ref "X13") (pin "1") (pinfunction "1_1") (pintype "passive"))
    )
    (net (code "335") (name "Net-(D74-+)") (class "Default")
      (node (ref "D74") (pin "1") (pinfunction "+_1") (pintype "passive"))
      (node (ref "JP28") (pin "2") (pinfunction "2_2") (pintype "passive"))
    )
    (net (code "336") (name "Net-(D75-+)") (class "Default")
      (node (ref "D75") (pin "1") (pinfunction "+_1") (pintype "passive"))
      (node (ref "JP29") (pin "1") (pinfunction "1_1") (pintype "passive"))
    )
    (net (code "337") (name "Net-(D76--)") (class "Default")
      (node (ref "D76") (pin "2") (pinfunction "-_2") (pintype "passive"))
      (node (ref "Q54") (pin "2") (pinfunction "C_2") (pintype "passive"))
      (node (ref "START6") (pin "TP") (pinfunction "PP_TP") (pintype "input"))
      (node (ref "X16") (pin "5") (pinfunction "5_5") (pintype "passive"))
    )
    (net (code "338") (name "Net-(D77-+)") (class "Default")
      (node (ref "D77") (pin "1") (pinfunction "+_1") (pintype "passive"))
      (node (ref "R335") (pin "1") (pinfunction "1_1") (pintype "passive"))
    )
    (net (code "339") (name "Net-(D77--)") (class "Default")
      (node (ref "C69") (pin "2") (pinfunction "2_2") (pintype "passive"))
      (node (ref "D77") (pin "2") (pinfunction "-_2") (pintype "passive"))
      (node (ref "D81") (pin "C") (pinfunction "C_C") (pintype "passive"))
      (node (ref "IC51") (pin "2") (pinfunction "TR_2") (pintype "input"))
      (node (ref "IC51") (pin "6") (pinfunction "THR_6") (pintype "input"))
      (node (ref "R334") (pin "1") (pinfunction "1_1") (pintype "passive"))
    )
    (net (code "340") (name "Net-(D79--)") (class "Default")
      (node (ref "D79") (pin "2") (pinfunction "-_2") (pintype "passive"))
      (node (ref "R356") (pin "1") (pinfunction "1_1") (pintype "passive"))
      (node (ref "R357") (pin "1") (pinfunction "1_1") (pintype "passive"))
    )
    (net (code "341") (name "Net-(D80-+)") (class "Default")
      (node (ref "D80") (pin "1") (pinfunction "+_1") (pintype "passive"))
      (node (ref "X16") (pin "1") (pinfunction "1_1") (pintype "passive"))
    )
    (net (code "342") (name "Net-(D84-+)") (class "Default")
      (node (ref "D84") (pin "1") (pinfunction "+_1") (pintype "passive"))
      (node (ref "R358") (pin "1") (pinfunction "1_1") (pintype "passive"))
    )
    (net (code "343") (name "Net-(D87-+)") (class "Default")
      (node (ref "D87") (pin "1") (pinfunction "+_1") (pintype "passive"))
      (node (ref "JP33") (pin "2") (pinfunction "2_2") (pintype "passive"))
    )
    (net (code "344") (name "Net-(D88-+)") (class "Default")
      (node (ref "D88") (pin "1") (pinfunction "+_1") (pintype "passive"))
      (node (ref "JP34") (pin "1") (pinfunction "1_1") (pintype "passive"))
    )
    (net (code "345") (name "Net-(D89--)") (class "Default")
      (node (ref "D89") (pin "2") (pinfunction "-_2") (pintype "passive"))
      (node (ref "Q64") (pin "2") (pinfunction "C_2") (pintype "passive"))
      (node (ref "START7") (pin "TP") (pinfunction "PP_TP") (pintype "input"))
      (node (ref "X19") (pin "5") (pinfunction "5_5") (pintype "passive"))
    )
    (net (code "346") (name "Net-(D90-+)") (class "Default")
      (node (ref "D90") (pin "1") (pinfunction "+_1") (pintype "passive"))
      (node (ref "R386") (pin "1") (pinfunction "1_1") (pintype "passive"))
    )
    (net (code "347") (name "Net-(D90--)") (class "Default")
      (node (ref "C81") (pin "2") (pinfunction "2_2") (pintype "passive"))
      (node (ref "D90") (pin "2") (pinfunction "-_2") (pintype "passive"))
      (node (ref "D94") (pin "C") (pinfunction "C_C") (pintype "passive"))
      (node (ref "IC60") (pin "2") (pinfunction "TR_2") (pintype "input"))
      (node (ref "IC60") (pin "6") (pinfunction "THR_6") (pintype "input"))
      (node (ref "R385") (pin "1") (pinfunction "1_1") (pintype "passive"))
    )
    (net (code "348") (name "Net-(D92--)") (class "Default")
      (node (ref "D92") (pin "2") (pinfunction "-_2") (pintype "passive"))
      (node (ref "R407") (pin "1") (pinfunction "1_1") (pintype "passive"))
      (node (ref "R408") (pin "1") (pinfunction "1_1") (pintype "passive"))
    )
    (net (code "349") (name "Net-(D93-+)") (class "Default")
      (node (ref "D93") (pin "1") (pinfunction "+_1") (pintype "passive"))
      (node (ref "X19") (pin "1") (pinfunction "1_1") (pintype "passive"))
    )
    (net (code "350") (name "Net-(D97-+)") (class "Default")
      (node (ref "D97") (pin "1") (pinfunction "+_1") (pintype "passive"))
      (node (ref "R409") (pin "1") (pinfunction "1_1") (pintype "passive"))
    )
    (net (code "351") (name "Net-(D100-+)") (class "Default")
      (node (ref "D100") (pin "1") (pinfunction "+_1") (pintype "passive"))
      (node (ref "JP38") (pin "2") (pinfunction "2_2") (pintype "passive"))
    )
    (net (code "352") (name "Net-(D104-+)") (class "Default")
      (node (ref "D104") (pin "1") (pinfunction "+_1") (pintype "passive"))
      (node (ref "JP39") (pin "1") (pinfunction "1_1") (pintype "passive"))
    )
    (net (code "353") (name "Net-(D105--)") (class "Default")
      (node (ref "D105") (pin "2") (pinfunction "-_2") (pintype "passive"))
      (node (ref "Q104") (pin "2") (pinfunction "C_2") (pintype "passive"))
      (node (ref "START") (pin "TP") (pinfunction "PP_TP") (pintype "input"))
      (node (ref "X101") (pin "5") (pinfunction "5_5") (pintype "passive"))
    )
    (net (code "354") (name "Net-(D106-+)") (class "Default")
      (node (ref "D106") (pin "1") (pinfunction "+_1") (pintype "passive"))
      (node (ref "R127") (pin "1") (pinfunction "1_1") (pintype "passive"))
    )
    (net (code "355") (name "Net-(D109-+)") (class "Default")
      (node (ref "D109") (pin "1") (pinfunction "+_1") (pintype "passive"))
      (node (ref "JP102") (pin "2") (pinfunction "2_2") (pintype "passive"))
    )
    (net (code "356") (name "Net-(D110-+)") (class "Default")
      (node (ref "D110") (pin "1") (pinfunction "+_1") (pintype "passive"))
      (node (ref "JP103") (pin "1") (pinfunction "1_1") (pintype "passive"))
    )
    (net (code "357") (name "Net-(D111--)") (class "Default")
      (node (ref "D111") (pin "2") (pinfunction "-_2") (pintype "passive"))
      (node (ref "Q74") (pin "2") (pinfunction "C_2") (pintype "passive"))
      (node (ref "START8") (pin "TP") (pinfunction "PP_TP") (pintype "input"))
      (node (ref "X22") (pin "5") (pinfunction "5_5") (pintype "passive"))
    )
    (net (code "358") (name "Net-(D112-+)") (class "Default")
      (node (ref "D112") (pin "1") (pinfunction "+_1") (pintype "passive"))
      (node (ref "R140") (pin "1") (pinfunction "1_1") (pintype "passive"))
    )
    (net (code "359") (name "Net-(D112--)") (class "Default")
      (node (ref "C109") (pin "2") (pinfunction "2_2") (pintype "passive"))
      (node (ref "D112") (pin "2") (pinfunction "-_2") (pintype "passive"))
      (node (ref "D4") (pin "C") (pinfunction "C_C") (pintype "passive"))
      (node (ref "IC110") (pin "2") (pinfunction "TR_2") (pintype "input"))
      (node (ref "IC110") (pin "6") (pinfunction "THR_6") (pintype "input"))
      (node (ref "R141") (pin "1") (pinfunction "1_1") (pintype "passive"))
    )
    (net (code "360") (name "Net-(D113-+)") (class "Default")
      (node (ref "D113") (pin "1") (pinfunction "+_1") (pintype "passive"))
      (node (ref "R437") (pin "1") (pinfunction "1_1") (pintype "passive"))
    )
    (net (code "361") (name "Net-(D113--)") (class "Default")
      (node (ref "C93") (pin "2") (pinfunction "2_2") (pintype "passive"))
      (node (ref "D113") (pin "2") (pinfunction "-_2") (pintype "passive"))
      (node (ref "D117") (pin "C") (pinfunction "C_C") (pintype "passive"))
      (node (ref "IC69") (pin "2") (pinfunction "TR_2") (pintype "input"))
      (node (ref "IC69") (pin "6") (pinfunction "THR_6") (pintype "input"))
      (node (ref "R436") (pin "1") (pinfunction "1_1") (pintype "passive"))
    )
    (net (code "362") (name "Net-(D115--)") (class "Default")
      (node (ref "D115") (pin "2") (pinfunction "-_2") (pintype "passive"))
      (node (ref "R458") (pin "1") (pinfunction "1_1") (pintype "passive"))
      (node (ref "R459") (pin "1") (pinfunction "1_1") (pintype "passive"))
    )
    (net (code "363") (name "Net-(D116-+)") (class "Default")
      (node (ref "D116") (pin "1") (pinfunction "+_1") (pintype "passive"))
      (node (ref "X22") (pin "1") (pinfunction "1_1") (pintype "passive"))
    )
    (net (code "364") (name "Net-(D120-+)") (class "Default")
      (node (ref "D120") (pin "1") (pinfunction "+_1") (pintype "passive"))
      (node (ref "R460") (pin "1") (pinfunction "1_1") (pintype "passive"))
    )
    (net (code "365") (name "Net-(D123-+)") (class "Default")
      (node (ref "D123") (pin "1") (pinfunction "+_1") (pintype "passive"))
      (node (ref "JP43") (pin "2") (pinfunction "2_2") (pintype "passive"))
    )
    (net (code "366") (name "Net-(D124-+)") (class "Default")
      (node (ref "D124") (pin "1") (pinfunction "+_1") (pintype "passive"))
      (node (ref "JP44") (pin "1") (pinfunction "1_1") (pintype "passive"))
    )
    (net (code "367") (name "Net-(D125--)") (class "Default")
      (node (ref "D125") (pin "2") (pinfunction "-_2") (pintype "passive"))
      (node (ref "Q84") (pin "2") (pinfunction "C_2") (pintype "passive"))
      (node (ref "START9") (pin "TP") (pinfunction "PP_TP") (pintype "input"))
      (node (ref "X25") (pin "5") (pinfunction "5_5") (pintype "passive"))
    )
    (net (code "368") (name "Net-(D126-+)") (class "Default")
      (node (ref "D126") (pin "1") (pinfunction "+_1") (pintype "passive"))
      (node (ref "R488") (pin "1") (pinfunction "1_1") (pintype "passive"))
    )
    (net (code "369") (name "Net-(D126--)") (class "Default")
      (node (ref "C115") (pin "2") (pinfunction "2_2") (pintype "passive"))
      (node (ref "D126") (pin "2") (pinfunction "-_2") (pintype "passive"))
      (node (ref "D130") (pin "C") (pinfunction "C_C") (pintype "passive"))
      (node (ref "IC78") (pin "2") (pinfunction "TR_2") (pintype "input"))
      (node (ref "IC78") (pin "6") (pinfunction "THR_6") (pintype "input"))
      (node (ref "R487") (pin "1") (pinfunction "1_1") (pintype "passive"))
    )
    (net (code "370") (name "Net-(D128--)") (class "Default")
      (node (ref "D128") (pin "2") (pinfunction "-_2") (pintype "passive"))
      (node (ref "R509") (pin "1") (pinfunction "1_1") (pintype "passive"))
      (node (ref "R510") (pin "1") (pinfunction "1_1") (pintype "passive"))
    )
    (net (code "371") (name "Net-(D129-+)") (class "Default")
      (node (ref "D129") (pin "1") (pinfunction "+_1") (pintype "passive"))
      (node (ref "X25") (pin "1") (pinfunction "1_1") (pintype "passive"))
    )
    (net (code "372") (name "Net-(D133-+)") (class "Default")
      (node (ref "D133") (pin "1") (pinfunction "+_1") (pintype "passive"))
      (node (ref "R511") (pin "1") (pinfunction "1_1") (pintype "passive"))
    )
    (net (code "373") (name "Net-(D136-+)") (class "Default")
      (node (ref "D136") (pin "1") (pinfunction "+_1") (pintype "passive"))
      (node (ref "JP48") (pin "2") (pinfunction "2_2") (pintype "passive"))
    )
    (net (code "374") (name "Net-(D137-+)") (class "Default")
      (node (ref "D137") (pin "1") (pinfunction "+_1") (pintype "passive"))
      (node (ref "JP49") (pin "1") (pinfunction "1_1") (pintype "passive"))
    )
    (net (code "375") (name "Net-(D138--)") (class "Default")
      (node (ref "D138") (pin "2") (pinfunction "-_2") (pintype "passive"))
      (node (ref "Q94") (pin "2") (pinfunction "C_2") (pintype "passive"))
      (node (ref "START10") (pin "TP") (pinfunction "PP_TP") (pintype "input"))
      (node (ref "X28") (pin "5") (pinfunction "5_5") (pintype "passive"))
    )
    (net (code "376") (name "Net-(D139-+)") (class "Default")
      (node (ref "D139") (pin "1") (pinfunction "+_1") (pintype "passive"))
      (node (ref "R539") (pin "1") (pinfunction "1_1") (pintype "passive"))
    )
    (net (code "377") (name "Net-(D139--)") (class "Default")
      (node (ref "C127") (pin "2") (pinfunction "2_2") (pintype "passive"))
      (node (ref "D139") (pin "2") (pinfunction "-_2") (pintype "passive"))
      (node (ref "D143") (pin "C") (pinfunction "C_C") (pintype "passive"))
      (node (ref "IC87") (pin "2") (pinfunction "TR_2") (pintype "input"))
      (node (ref "IC87") (pin "6") (pinfunction "THR_6") (pintype "input"))
      (node (ref "R538") (pin "1") (pinfunction "1_1") (pintype "passive"))
    )
    (net (code "378") (name "Net-(D141--)") (class "Default")
      (node (ref "D141") (pin "2") (pinfunction "-_2") (pintype "passive"))
      (node (ref "R560") (pin "1") (pinfunction "1_1") (pintype "passive"))
      (node (ref "R561") (pin "1") (pinfunction "1_1") (pintype "passive"))
    )
    (net (code "379") (name "Net-(D142-+)") (class "Default")
      (node (ref "D142") (pin "1") (pinfunction "+_1") (pintype "passive"))
      (node (ref "X28") (pin "1") (pinfunction "1_1") (pintype "passive"))
    )
    (net (code "380") (name "Net-(D146-+)") (class "Default")
      (node (ref "D146") (pin "1") (pinfunction "+_1") (pintype "passive"))
      (node (ref "R562") (pin "1") (pinfunction "1_1") (pintype "passive"))
    )
    (net (code "381") (name "Net-(D149-+)") (class "Default")
      (node (ref "D149") (pin "1") (pinfunction "+_1") (pintype "passive"))
      (node (ref "JP53") (pin "2") (pinfunction "2_2") (pintype "passive"))
    )
    (net (code "382") (name "Net-(D150-+)") (class "Default")
      (node (ref "D150") (pin "1") (pinfunction "+_1") (pintype "passive"))
      (node (ref "JP54") (pin "1") (pinfunction "1_1") (pintype "passive"))
    )
    (net (code "383") (name "Net-(D151--)") (class "Default")
      (node (ref "D151") (pin "2") (pinfunction "-_2") (pintype "passive"))
      (node (ref "Q111") (pin "2") (pinfunction "C_2") (pintype "passive"))
      (node (ref "START11") (pin "TP") (pinfunction "PP_TP") (pintype "input"))
      (node (ref "X31") (pin "5") (pinfunction "5_5") (pintype "passive"))
    )
    (net (code "384") (name "Net-(D152-+)") (class "Default")
      (node (ref "D152") (pin "1") (pinfunction "+_1") (pintype "passive"))
      (node (ref "R590") (pin "1") (pinfunction "1_1") (pintype "passive"))
    )
    (net (code "385") (name "Net-(D152--)") (class "Default")
      (node (ref "C139") (pin "2") (pinfunction "2_2") (pintype "passive"))
      (node (ref "D152") (pin "2") (pinfunction "-_2") (pintype "passive"))
      (node (ref "D156") (pin "C") (pinfunction "C_C") (pintype "passive"))
      (node (ref "IC96") (pin "2") (pinfunction "TR_2") (pintype "input"))
      (node (ref "IC96") (pin "6") (pinfunction "THR_6") (pintype "input"))
      (node (ref "R589") (pin "1") (pinfunction "1_1") (pintype "passive"))
    )
    (net (code "386") (name "Net-(D154--)") (class "Default")
      (node (ref "D154") (pin "2") (pinfunction "-_2") (pintype "passive"))
      (node (ref "R611") (pin "1") (pinfunction "1_1") (pintype "passive"))
      (node (ref "R612") (pin "1") (pinfunction "1_1") (pintype "passive"))
    )
    (net (code "387") (name "Net-(D155-+)") (class "Default")
      (node (ref "D155") (pin "1") (pinfunction "+_1") (pintype "passive"))
      (node (ref "X31") (pin "1") (pinfunction "1_1") (pintype "passive"))
    )
    (net (code "388") (name "Net-(IC1A-A)") (class "Default")
      (node (ref "IC1") (pin "10") (pinfunction "A_10") (pintype "input"))
      (node (ref "R17") (pin "1") (pinfunction "1_1") (pintype "passive"))
      (node (ref "R58") (pin "1") (pinfunction "1_1") (pintype "passive"))
      (node (ref "R58") (pin "2") (pinfunction "2_2") (pintype "passive"))
      (node (ref "X1") (pin "4") (pinfunction "4_4") (pintype "passive"))
      (node (ref "X2") (pin "2") (pinfunction "S_2") (pintype "passive"))
    )
    (net (code "389") (name "Net-(IC1A-B)") (class "Default")
      (node (ref "IC1") (pin "13") (pinfunction "B_13") (pintype "input"))
      (node (ref "R16") (pin "1") (pinfunction "1_1") (pintype "passive"))
      (node (ref "R57") (pin "1") (pinfunction "1_1") (pintype "passive"))
      (node (ref "R57") (pin "2") (pinfunction "2_2") (pintype "passive"))
      (node (ref "X1") (pin "3") (pinfunction "3_3") (pintype "passive"))
      (node (ref "X2") (pin "3") (pinfunction "S_3") (pintype "passive"))
    )
    (net (code "390") (name "Net-(IC1A-C)") (class "Default")
      (node (ref "IC1") (pin "12") (pinfunction "C_12") (pintype "input"))
      (node (ref "R15") (pin "1") (pinfunction "1_1") (pintype "passive"))
      (node (ref "R56") (pin "1") (pinfunction "1_1") (pintype "passive"))
      (node (ref "R56") (pin "2") (pinfunction "2_2") (pintype "passive"))
      (node (ref "X1") (pin "2") (pinfunction "2_2") (pintype "passive"))
      (node (ref "X2") (pin "4") (pinfunction "S_4") (pintype "passive"))
    )
    (net (code "391") (name "Net-(IC1A-Q0)") (class "Default")
      (node (ref "IC1") (pin "3") (pinfunction "Q0_3") (pintype "output"))
      (node (ref "IC3") (pin "1") (pinfunction "I1_1") (pintype "input"))
      (node (ref "IC3") (pin "2") (pinfunction "I2_2") (pintype "input"))
      (node (ref "Q10") (pin "1") (pinfunction "G_1") (pintype "passive"))
      (node (ref "Q11") (pin "1") (pinfunction "G_1") (pintype "passive"))
    )
    (net (code "392") (name "Net-(IC1A-Q1)") (class "Default")
      (node (ref "IC1") (pin "14") (pinfunction "Q1_14") (pintype "output"))
      (node (ref "IC3") (pin "6") (pinfunction "I6_6") (pintype "input"))
    )
    (net (code "393") (name "Net-(IC1A-Q2)") (class "Default")
      (node (ref "IC1") (pin "2") (pinfunction "Q2_2") (pintype "output"))
      (node (ref "IC3") (pin "7") (pinfunction "I7_7") (pintype "input"))
    )
    (net (code "394") (name "Net-(IC1A-Q3)") (class "Default")
      (node (ref "IC1") (pin "15") (pinfunction "Q3_15") (pintype "output"))
      (node (ref "IC3") (pin "5") (pinfunction "I5_5") (pintype "input"))
    )
    (net (code "395") (name "Net-(IC1A-Q4)") (class "Default")
      (node (ref "IC1") (pin "1") (pinfunction "Q4_1") (pintype "output"))
      (node (ref "IC3") (pin "4") (pinfunction "I4_4") (pintype "input"))
    )
    (net (code "396") (name "Net-(IC1A-Q5)") (class "Default")
      (node (ref "IC1") (pin "6") (pinfunction "Q5_6") (pintype "output"))
      (node (ref "IC3") (pin "3") (pinfunction "I3_3") (pintype "input"))
    )
    (net (code "397") (name "Net-(IC2-ADJ)") (class "Default")
      (node (ref "IC2") (pin "1") (pinfunction "ADJ_1") (pintype "input"))
      (node (ref "R11") (pin "1") (pinfunction "1_1") (pintype "passive"))
      (node (ref "R20") (pin "2") (pinfunction "2_2") (pintype "passive"))
      (node (ref "X1") (pin "7") (pinfunction "7_7") (pintype "passive"))
    )
    (net (code "398") (name "Net-(IC2-VI)") (class "Default")
      (node (ref "IC2") (pin "3") (pinfunction "VI_3") (pintype "input"))
      (node (ref "Q7") (pin "2") (pinfunction "C_2") (pintype "passive"))
    )
    (net (code "399") (name "Net-(IC2-VO)") (class "Default")
      (node (ref "IC2") (pin "2") (pinfunction "VO_2") (pintype "passive"))
      (node (ref "R11") (pin "2") (pinfunction "2_2") (pintype "passive"))
    )
    (net (code "400") (name "Net-(IC3-O1)") (class "Default")
      (node (ref "IC3") (pin "16") (pinfunction "O1_16") (pintype "open_collector"))
      (node (ref "Q10") (pin "3") (pinfunction "D_3") (pintype "passive"))
      (node (ref "R62") (pin "1") (pinfunction "1_1") (pintype "passive"))
    )
    (net (code "401") (name "Net-(IC3-O2)") (class "Default")
      (node (ref "IC3") (pin "15") (pinfunction "O2_15") (pintype "open_collector"))
      (node (ref "R35") (pin "1") (pinfunction "1_1") (pintype "passive"))
    )
    (net (code "402") (name "Net-(IC4A-+IN)") (class "Default")
      (node (ref "IC4") (pin "11") (pinfunction "+IN_11") (pintype "input"))
      (node (ref "IC4") (pin "5") (pinfunction "+IN_5") (pintype "input"))
      (node (ref "R24") (pin "1") (pinfunction "1_1") (pintype "passive"))
      (node (ref "R25") (pin "2") (pinfunction "2_2") (pintype "passive"))
      (node (ref "R26") (pin "2") (pinfunction "2_2") (pintype "passive"))
    )
    (net (code "403") (name "Net-(IC4A--IN)") (class "Default")
      (node (ref "C3") (pin "1") (pinfunction "1_1") (pintype "passive"))
      (node (ref "IC4") (pin "10") (pinfunction "-IN_10") (pintype "input"))
      (node (ref "IC4") (pin "4") (pinfunction "-IN_4") (pintype "input"))
      (node (ref "R23") (pin "1") (pinfunction "1_1") (pintype "passive"))
    )
    (net (code "404") (name "Net-(IC4A-OUT)") (class "Default")
      (node (ref "IC4") (pin "2") (pinfunction "OUT_2") (pintype "open_collector"))
      (node (ref "R26") (pin "1") (pinfunction "1_1") (pintype "passive"))
    )
    (net (code "405") (name "Net-(IC4B-+IN)") (class "Default")
      (node (ref "IC4") (pin "7") (pinfunction "+IN_7") (pintype "input"))
      (node (ref "R21") (pin "1") (pinfunction "1_1") (pintype "passive"))
      (node (ref "R38") (pin "1") (pinfunction "1_1") (pintype "passive"))
    )
    (net (code "406") (name "Net-(IC4B--IN)") (class "Default")
      (node (ref "IC4") (pin "6") (pinfunction "-IN_6") (pintype "input"))
      (node (ref "IC4") (pin "8") (pinfunction "-IN_8") (pintype "input"))
      (node (ref "R20") (pin "1") (pinfunction "1_1") (pintype "passive"))
    )
    (net (code "407") (name "Net-(IC4B-OUT)") (class "Default")
      (node (ref "IC4") (pin "1") (pinfunction "OUT_1") (pintype "open_collector"))
      (node (ref "R22") (pin "2") (pinfunction "2_2") (pintype "passive"))
      (node (ref "R27") (pin "2") (pinfunction "2_2") (pintype "passive"))
    )
    (net (code "408") (name "Net-(IC4C-+IN)") (class "Default")
      (node (ref "C6") (pin "1") (pinfunction "1_1") (pintype "passive"))
      (node (ref "IC4") (pin "9") (pinfunction "+IN_9") (pintype "input"))
      (node (ref "R29") (pin "2") (pinfunction "2_2") (pintype "passive"))
      (node (ref "R38") (pin "2") (pinfunction "2_2") (pintype "passive"))
    )
    (net (code "409") (name "Net-(IC4C-OUT)") (class "Default")
      (node (ref "C7") (pin "2") (pinfunction "2_2") (pintype "passive"))
      (node (ref "IC4") (pin "14") (pinfunction "OUT_14") (pintype "open_collector"))
      (node (ref "R28") (pin "2") (pinfunction "2_2") (pintype "passive"))
    )
    (net (code "410") (name "Net-(IC4D-OUT)") (class "Default")
      (node (ref "IC4") (pin "13") (pinfunction "OUT_13") (pintype "open_collector"))
      (node (ref "JP2") (pin "1") (pinfunction "1_1") (pintype "passive"))
      (node (ref "Q9") (pin "1") (pinfunction "G_1") (pintype "passive"))
      (node (ref "R41") (pin "2") (pinfunction "2_2") (pintype "passive"))
    )
    (net (code "411") (name "Net-(IC6-Q)") (class "Default")
      (node (ref "IC6") (pin "3") (pinfunction "Q_3") (pintype "output"))
      (node (ref "IC7") (pin "12") (pinfunction "A_12") (pintype "input"))
      (node (ref "IC7") (pin "4") (pinfunction "A_4") (pintype "input"))
    )
    (net (code "412") (name "Net-(IC7A-T2)") (class "Default")
      (node (ref "C12") (pin "2") (pinfunction "2_2") (pintype "passive"))
      (node (ref "IC7") (pin "2") (pinfunction "T2_2") (pintype "input"))
      (node (ref "R64") (pin "1") (pinfunction "1_1") (pintype "passive"))
    )
    (net (code "413") (name "Net-(IC7A-~{Q})") (class "Default")
      (node (ref "IC7") (pin "7") (pinfunction "~{Q}_7") (pintype "output"))
      (node (ref "Q13") (pin "1") (pinfunction "G_1") (pintype "passive"))
    )
    (net (code "414") (name "Net-(IC7B-B)") (class "Default")
      (node (ref "IC7") (pin "11") (pinfunction "B_11") (pintype "input"))
      (node (ref "IC7") (pin "9") (pinfunction "~{Q}_9") (pintype "output"))
      (node (ref "R49") (pin "2") (pinfunction "2_2") (pintype "passive"))
    )
    (net (code "415") (name "Net-(IC7B-T2)") (class "Default")
      (node (ref "C10") (pin "1") (pinfunction "1_1") (pintype "passive"))
      (node (ref "IC7") (pin "14") (pinfunction "T2_14") (pintype "input"))
      (node (ref "R47") (pin "1") (pinfunction "1_1") (pintype "passive"))
    )
    (net (code "416") (name "Net-(IC9A-+IN)") (class "Default")
      (node (ref "C5") (pin "1") (pinfunction "1_1") (pintype "passive"))
      (node (ref "IC9") (pin "3") (pinfunction "+IN_3") (pintype "input"))
      (node (ref "R18") (pin "1") (pinfunction "1_1") (pintype "passive"))
    )
    (net (code "417") (name "Net-(IC9A--IN)") (class "Default")
      (node (ref "IC9") (pin "2") (pinfunction "-IN_2") (pintype "input"))
      (node (ref "R19") (pin "2") (pinfunction "2_2") (pintype "passive"))
    )
    (net (code "418") (name "Net-(IC9A-OUT)") (class "Default")
      (node (ref "IC9") (pin "1") (pinfunction "OUT_1") (pintype "output"))
      (node (ref "R50") (pin "2") (pinfunction "2_2") (pintype "passive"))
    )
    (net (code "419") (name "Net-(IC9B-+IN)") (class "Default")
      (node (ref "IC9") (pin "5") (pinfunction "+IN_5") (pintype "input"))
      (node (ref "Q11") (pin "3") (pinfunction "D_3") (pintype "passive"))
      (node (ref "R51") (pin "2") (pinfunction "2_2") (pintype "passive"))
      (node (ref "R52") (pin "2") (pinfunction "2_2") (pintype "passive"))
    )
    (net (code "420") (name "Net-(IC9B--IN)") (class "Default")
      (node (ref "IC9") (pin "6") (pinfunction "-IN_6") (pintype "input"))
      (node (ref "R53") (pin "1") (pinfunction "1_1") (pintype "passive"))
      (node (ref "R54") (pin "2") (pinfunction "2_2") (pintype "passive"))
    )
    (net (code "421") (name "Net-(IC9B-OUT)") (class "Default")
      (node (ref "IC9") (pin "7") (pinfunction "OUT_7") (pintype "output"))
      (node (ref "R32") (pin "2") (pinfunction "2_2") (pintype "passive"))
      (node (ref "R39") (pin "1") (pinfunction "1_1") (pintype "passive"))
      (node (ref "R52") (pin "1") (pinfunction "1_1") (pintype "passive"))
    )
    (net (code "422") (name "Net-(IC10A-A)") (class "Default")
      (node (ref "IC10") (pin "10") (pinfunction "A_10") (pintype "input"))
      (node (ref "R157") (pin "1") (pinfunction "1_1") (pintype "passive"))
      (node (ref "R157") (pin "2") (pinfunction "2_2") (pintype "passive"))
      (node (ref "R72") (pin "1") (pinfunction "1_1") (pintype "passive"))
      (node (ref "X4") (pin "4") (pinfunction "4_4") (pintype "passive"))
      (node (ref "X5") (pin "2") (pinfunction "S_2") (pintype "passive"))
    )
    (net (code "423") (name "Net-(IC10A-B)") (class "Default")
      (node (ref "IC10") (pin "13") (pinfunction "B_13") (pintype "input"))
      (node (ref "R156") (pin "1") (pinfunction "1_1") (pintype "passive"))
      (node (ref "R156") (pin "2") (pinfunction "2_2") (pintype "passive"))
      (node (ref "R71") (pin "1") (pinfunction "1_1") (pintype "passive"))
      (node (ref "X4") (pin "3") (pinfunction "3_3") (pintype "passive"))
      (node (ref "X5") (pin "3") (pinfunction "S_3") (pintype "passive"))
    )
    (net (code "424") (name "Net-(IC10A-C)") (class "Default")
      (node (ref "IC10") (pin "12") (pinfunction "C_12") (pintype "input"))
      (node (ref "R155") (pin "1") (pinfunction "1_1") (pintype "passive"))
      (node (ref "R155") (pin "2") (pinfunction "2_2") (pintype "passive"))
      (node (ref "R70") (pin "1") (pinfunction "1_1") (pintype "passive"))
      (node (ref "X4") (pin "2") (pinfunction "2_2") (pintype "passive"))
      (node (ref "X5") (pin "4") (pinfunction "S_4") (pintype "passive"))
    )
    (net (code "425") (name "Net-(IC10A-Q0)") (class "Default")
      (node (ref "IC10") (pin "3") (pinfunction "Q0_3") (pintype "output"))
      (node (ref "IC12") (pin "1") (pinfunction "I1_1") (pintype "input"))
      (node (ref "IC12") (pin "2") (pinfunction "I2_2") (pintype "input"))
      (node (ref "Q20") (pin "1") (pinfunction "G_1") (pintype "passive"))
      (node (ref "Q21") (pin "1") (pinfunction "G_1") (pintype "passive"))
    )
    (net (code "426") (name "Net-(IC10A-Q1)") (class "Default")
      (node (ref "IC10") (pin "14") (pinfunction "Q1_14") (pintype "output"))
      (node (ref "IC12") (pin "6") (pinfunction "I6_6") (pintype "input"))
    )
    (net (code "427") (name "Net-(IC10A-Q2)") (class "Default")
      (node (ref "IC10") (pin "2") (pinfunction "Q2_2") (pintype "output"))
      (node (ref "IC12") (pin "7") (pinfunction "I7_7") (pintype "input"))
    )
    (net (code "428") (name "Net-(IC10A-Q3)") (class "Default")
      (node (ref "IC10") (pin "15") (pinfunction "Q3_15") (pintype "output"))
      (node (ref "IC12") (pin "5") (pinfunction "I5_5") (pintype "input"))
    )
    (net (code "429") (name "Net-(IC10A-Q4)") (class "Default")
      (node (ref "IC10") (pin "1") (pinfunction "Q4_1") (pintype "output"))
      (node (ref "IC12") (pin "4") (pinfunction "I4_4") (pintype "input"))
    )
    (net (code "430") (name "Net-(IC10A-Q5)") (class "Default")
      (node (ref "IC10") (pin "6") (pinfunction "Q5_6") (pintype "output"))
      (node (ref "IC12") (pin "3") (pinfunction "I3_3") (pintype "input"))
    )
    (net (code "431") (name "Net-(IC11-ADJ)") (class "Default")
      (node (ref "IC11") (pin "1") (pinfunction "ADJ_1") (pintype "input"))
      (node (ref "R68") (pin "1") (pinfunction "1_1") (pintype "passive"))
      (node (ref "R75") (pin "2") (pinfunction "2_2") (pintype "passive"))
      (node (ref "X4") (pin "7") (pinfunction "7_7") (pintype "passive"))
    )
    (net (code "432") (name "Net-(IC11-VI)") (class "Default")
      (node (ref "IC11") (pin "3") (pinfunction "VI_3") (pintype "input"))
      (node (ref "Q17") (pin "2") (pinfunction "C_2") (pintype "passive"))
    )
    (net (code "433") (name "Net-(IC11-VO)") (class "Default")
      (node (ref "IC11") (pin "2") (pinfunction "VO_2") (pintype "passive"))
      (node (ref "R68") (pin "2") (pinfunction "2_2") (pintype "passive"))
    )
    (net (code "434") (name "Net-(IC12-O1)") (class "Default")
      (node (ref "IC12") (pin "16") (pinfunction "O1_16") (pintype "open_collector"))
      (node (ref "Q20") (pin "3") (pinfunction "D_3") (pintype "passive"))
      (node (ref "R161") (pin "1") (pinfunction "1_1") (pintype "passive"))
    )
    (net (code "435") (name "Net-(IC12-O2)") (class "Default")
      (node (ref "IC12") (pin "15") (pinfunction "O2_15") (pintype "open_collector"))
      (node (ref "R90") (pin "1") (pinfunction "1_1") (pintype "passive"))
    )
    (net (code "436") (name "Net-(IC13A-+IN)") (class "Default")
      (node (ref "IC13") (pin "11") (pinfunction "+IN_11") (pintype "input"))
      (node (ref "IC13") (pin "5") (pinfunction "+IN_5") (pintype "input"))
      (node (ref "R79") (pin "1") (pinfunction "1_1") (pintype "passive"))
      (node (ref "R80") (pin "2") (pinfunction "2_2") (pintype "passive"))
      (node (ref "R81") (pin "2") (pinfunction "2_2") (pintype "passive"))
    )
    (net (code "437") (name "Net-(IC13A--IN)") (class "Default")
      (node (ref "C16") (pin "1") (pinfunction "1_1") (pintype "passive"))
      (node (ref "IC13") (pin "10") (pinfunction "-IN_10") (pintype "input"))
      (node (ref "IC13") (pin "4") (pinfunction "-IN_4") (pintype "input"))
      (node (ref "R78") (pin "1") (pinfunction "1_1") (pintype "passive"))
    )
    (net (code "438") (name "Net-(IC13A-OUT)") (class "Default")
      (node (ref "IC13") (pin "2") (pinfunction "OUT_2") (pintype "open_collector"))
      (node (ref "R81") (pin "1") (pinfunction "1_1") (pintype "passive"))
    )
    (net (code "439") (name "Net-(IC13B-+IN)") (class "Default")
      (node (ref "IC13") (pin "7") (pinfunction "+IN_7") (pintype "input"))
      (node (ref "R76") (pin "1") (pinfunction "1_1") (pintype "passive"))
      (node (ref "R93") (pin "1") (pinfunction "1_1") (pintype "passive"))
    )
    (net (code "440") (name "Net-(IC13B--IN)") (class "Default")
      (node (ref "IC13") (pin "6") (pinfunction "-IN_6") (pintype "input"))
      (node (ref "IC13") (pin "8") (pinfunction "-IN_8") (pintype "input"))
      (node (ref "R75") (pin "1") (pinfunction "1_1") (pintype "passive"))
    )
    (net (code "441") (name "Net-(IC13B-OUT)") (class "Default")
      (node (ref "IC13") (pin "1") (pinfunction "OUT_1") (pintype "open_collector"))
      (node (ref "R77") (pin "2") (pinfunction "2_2") (pintype "passive"))
      (node (ref "R82") (pin "2") (pinfunction "2_2") (pintype "passive"))
    )
    (net (code "442") (name "Net-(IC13C-+IN)") (class "Default")
      (node (ref "C19") (pin "1") (pinfunction "1_1") (pintype "passive"))
      (node (ref "IC13") (pin "9") (pinfunction "+IN_9") (pintype "input"))
      (node (ref "R84") (pin "2") (pinfunction "2_2") (pintype "passive"))
      (node (ref "R93") (pin "2") (pinfunction "2_2") (pintype "passive"))
    )
    (net (code "443") (name "Net-(IC13C-OUT)") (class "Default")
      (node (ref "C20") (pin "2") (pinfunction "2_2") (pintype "passive"))
      (node (ref "IC13") (pin "14") (pinfunction "OUT_14") (pintype "open_collector"))
      (node (ref "R83") (pin "2") (pinfunction "2_2") (pintype "passive"))
    )
    (net (code "444") (name "Net-(IC13D-OUT)") (class "Default")
      (node (ref "IC13") (pin "13") (pinfunction "OUT_13") (pintype "open_collector"))
      (node (ref "JP7") (pin "1") (pinfunction "1_1") (pintype "passive"))
      (node (ref "Q19") (pin "1") (pinfunction "G_1") (pintype "passive"))
      (node (ref "R96") (pin "2") (pinfunction "2_2") (pintype "passive"))
    )
    (net (code "445") (name "Net-(IC15-Q)") (class "Default")
      (node (ref "IC15") (pin "3") (pinfunction "Q_3") (pintype "output"))
      (node (ref "IC16") (pin "12") (pinfunction "A_12") (pintype "input"))
      (node (ref "IC16") (pin "4") (pinfunction "A_4") (pintype "input"))
    )
    (net (code "446") (name "Net-(IC16A-T2)") (class "Default")
      (node (ref "C25") (pin "2") (pinfunction "2_2") (pintype "passive"))
      (node (ref "IC16") (pin "2") (pinfunction "T2_2") (pintype "input"))
      (node (ref "R163") (pin "1") (pinfunction "1_1") (pintype "passive"))
    )
    (net (code "447") (name "Net-(IC16A-~{Q})") (class "Default")
      (node (ref "IC16") (pin "7") (pinfunction "~{Q}_7") (pintype "output"))
      (node (ref "Q23") (pin "1") (pinfunction "G_1") (pintype "passive"))
    )
    (net (code "448") (name "Net-(IC16B-B)") (class "Default")
      (node (ref "IC16") (pin "11") (pinfunction "B_11") (pintype "input"))
      (node (ref "IC16") (pin "9") (pinfunction "~{Q}_9") (pintype "output"))
      (node (ref "R148") (pin "2") (pinfunction "2_2") (pintype "passive"))
    )
    (net (code "449") (name "Net-(IC16B-T2)") (class "Default")
      (node (ref "C23") (pin "1") (pinfunction "1_1") (pintype "passive"))
      (node (ref "IC16") (pin "14") (pinfunction "T2_14") (pintype "input"))
      (node (ref "R139") (pin "1") (pinfunction "1_1") (pintype "passive"))
    )
    (net (code "450") (name "Net-(IC18A-+IN)") (class "Default")
      (node (ref "C18") (pin "1") (pinfunction "1_1") (pintype "passive"))
      (node (ref "IC18") (pin "3") (pinfunction "+IN_3") (pintype "input"))
      (node (ref "R73") (pin "1") (pinfunction "1_1") (pintype "passive"))
    )
    (net (code "451") (name "Net-(IC18A--IN)") (class "Default")
      (node (ref "IC18") (pin "2") (pinfunction "-IN_2") (pintype "input"))
      (node (ref "R74") (pin "2") (pinfunction "2_2") (pintype "passive"))
    )
    (net (code "452") (name "Net-(IC18A-OUT)") (class "Default")
      (node (ref "IC18") (pin "1") (pinfunction "OUT_1") (pintype "output"))
      (node (ref "R149") (pin "2") (pinfunction "2_2") (pintype "passive"))
    )
    (net (code "453") (name "Net-(IC18B-+IN)") (class "Default")
      (node (ref "IC18") (pin "5") (pinfunction "+IN_5") (pintype "input"))
      (node (ref "Q21") (pin "3") (pinfunction "D_3") (pintype "passive"))
      (node (ref "R150") (pin "2") (pinfunction "2_2") (pintype "passive"))
      (node (ref "R151") (pin "2") (pinfunction "2_2") (pintype "passive"))
    )
    (net (code "454") (name "Net-(IC18B--IN)") (class "Default")
      (node (ref "IC18") (pin "6") (pinfunction "-IN_6") (pintype "input"))
      (node (ref "R152") (pin "1") (pinfunction "1_1") (pintype "passive"))
      (node (ref "R153") (pin "2") (pinfunction "2_2") (pintype "passive"))
    )
    (net (code "455") (name "Net-(IC18B-OUT)") (class "Default")
      (node (ref "IC18") (pin "7") (pinfunction "OUT_7") (pintype "output"))
      (node (ref "R151") (pin "1") (pinfunction "1_1") (pintype "passive"))
      (node (ref "R87") (pin "2") (pinfunction "2_2") (pintype "passive"))
      (node (ref "R94") (pin "1") (pinfunction "1_1") (pintype "passive"))
    )
    (net (code "456") (name "Net-(IC19A-A)") (class "Default")
      (node (ref "IC19") (pin "10") (pinfunction "A_10") (pintype "input"))
      (node (ref "R171") (pin "1") (pinfunction "1_1") (pintype "passive"))
      (node (ref "R212") (pin "1") (pinfunction "1_1") (pintype "passive"))
      (node (ref "R212") (pin "2") (pinfunction "2_2") (pintype "passive"))
      (node (ref "X7") (pin "4") (pinfunction "4_4") (pintype "passive"))
      (node (ref "X8") (pin "2") (pinfunction "S_2") (pintype "passive"))
    )
    (net (code "457") (name "Net-(IC19A-B)") (class "Default")
      (node (ref "IC19") (pin "13") (pinfunction "B_13") (pintype "input"))
      (node (ref "R170") (pin "1") (pinfunction "1_1") (pintype "passive"))
      (node (ref "R211") (pin "1") (pinfunction "1_1") (pintype "passive"))
      (node (ref "R211") (pin "2") (pinfunction "2_2") (pintype "passive"))
      (node (ref "X7") (pin "3") (pinfunction "3_3") (pintype "passive"))
      (node (ref "X8") (pin "3") (pinfunction "S_3") (pintype "passive"))
    )
    (net (code "458") (name "Net-(IC19A-C)") (class "Default")
      (node (ref "IC19") (pin "12") (pinfunction "C_12") (pintype "input"))
      (node (ref "R169") (pin "1") (pinfunction "1_1") (pintype "passive"))
      (node (ref "R210") (pin "1") (pinfunction "1_1") (pintype "passive"))
      (node (ref "R210") (pin "2") (pinfunction "2_2") (pintype "passive"))
      (node (ref "X7") (pin "2") (pinfunction "2_2") (pintype "passive"))
      (node (ref "X8") (pin "4") (pinfunction "S_4") (pintype "passive"))
    )
    (net (code "459") (name "Net-(IC19A-Q0)") (class "Default")
      (node (ref "IC19") (pin "3") (pinfunction "Q0_3") (pintype "output"))
      (node (ref "IC21") (pin "1") (pinfunction "I1_1") (pintype "input"))
      (node (ref "IC21") (pin "2") (pinfunction "I2_2") (pintype "input"))
      (node (ref "Q30") (pin "1") (pinfunction "G_1") (pintype "passive"))
      (node (ref "Q31") (pin "1") (pinfunction "G_1") (pintype "passive"))
    )
    (net (code "460") (name "Net-(IC19A-Q1)") (class "Default")
      (node (ref "IC19") (pin "14") (pinfunction "Q1_14") (pintype "output"))
      (node (ref "IC21") (pin "6") (pinfunction "I6_6") (pintype "input"))
    )
    (net (code "461") (name "Net-(IC19A-Q2)") (class "Default")
      (node (ref "IC19") (pin "2") (pinfunction "Q2_2") (pintype "output"))
      (node (ref "IC21") (pin "7") (pinfunction "I7_7") (pintype "input"))
    )
    (net (code "462") (name "Net-(IC19A-Q3)") (class "Default")
      (node (ref "IC19") (pin "15") (pinfunction "Q3_15") (pintype "output"))
      (node (ref "IC21") (pin "5") (pinfunction "I5_5") (pintype "input"))
    )
    (net (code "463") (name "Net-(IC19A-Q4)") (class "Default")
      (node (ref "IC19") (pin "1") (pinfunction "Q4_1") (pintype "output"))
      (node (ref "IC21") (pin "4") (pinfunction "I4_4") (pintype "input"))
    )
    (net (code "464") (name "Net-(IC19A-Q5)") (class "Default")
      (node (ref "IC19") (pin "6") (pinfunction "Q5_6") (pintype "output"))
      (node (ref "IC21") (pin "3") (pinfunction "I3_3") (pintype "input"))
    )
    (net (code "465") (name "Net-(IC20-ADJ)") (class "Default")
      (node (ref "IC20") (pin "1") (pinfunction "ADJ_1") (pintype "input"))
      (node (ref "R167") (pin "1") (pinfunction "1_1") (pintype "passive"))
      (node (ref "R174") (pin "2") (pinfunction "2_2") (pintype "passive"))
      (node (ref "X7") (pin "7") (pinfunction "7_7") (pintype "passive"))
    )
    (net (code "466") (name "Net-(IC20-VI)") (class "Default")
      (node (ref "IC20") (pin "3") (pinfunction "VI_3") (pintype "input"))
      (node (ref "Q27") (pin "2") (pinfunction "C_2") (pintype "passive"))
    )
    (net (code "467") (name "Net-(IC20-VO)") (class "Default")
      (node (ref "IC20") (pin "2") (pinfunction "VO_2") (pintype "passive"))
      (node (ref "R167") (pin "2") (pinfunction "2_2") (pintype "passive"))
    )
    (net (code "468") (name "Net-(IC21-O1)") (class "Default")
      (node (ref "IC21") (pin "16") (pinfunction "O1_16") (pintype "open_collector"))
      (node (ref "Q30") (pin "3") (pinfunction "D_3") (pintype "passive"))
      (node (ref "R216") (pin "1") (pinfunction "1_1") (pintype "passive"))
    )
    (net (code "469") (name "Net-(IC21-O2)") (class "Default")
      (node (ref "IC21") (pin "15") (pinfunction "O2_15") (pintype "open_collector"))
      (node (ref "R189") (pin "1") (pinfunction "1_1") (pintype "passive"))
    )
    (net (code "470") (name "Net-(IC22A-+IN)") (class "Default")
      (node (ref "IC22") (pin "11") (pinfunction "+IN_11") (pintype "input"))
      (node (ref "IC22") (pin "5") (pinfunction "+IN_5") (pintype "input"))
      (node (ref "R178") (pin "1") (pinfunction "1_1") (pintype "passive"))
      (node (ref "R179") (pin "2") (pinfunction "2_2") (pintype "passive"))
      (node (ref "R180") (pin "2") (pinfunction "2_2") (pintype "passive"))
    )
    (net (code "471") (name "Net-(IC22A--IN)") (class "Default")
      (node (ref "C28") (pin "1") (pinfunction "1_1") (pintype "passive"))
      (node (ref "IC22") (pin "10") (pinfunction "-IN_10") (pintype "input"))
      (node (ref "IC22") (pin "4") (pinfunction "-IN_4") (pintype "input"))
      (node (ref "R177") (pin "1") (pinfunction "1_1") (pintype "passive"))
    )
    (net (code "472") (name "Net-(IC22A-OUT)") (class "Default")
      (node (ref "IC22") (pin "2") (pinfunction "OUT_2") (pintype "open_collector"))
      (node (ref "R180") (pin "1") (pinfunction "1_1") (pintype "passive"))
    )
    (net (code "473") (name "Net-(IC22B-+IN)") (class "Default")
      (node (ref "IC22") (pin "7") (pinfunction "+IN_7") (pintype "input"))
      (node (ref "R175") (pin "1") (pinfunction "1_1") (pintype "passive"))
      (node (ref "R192") (pin "1") (pinfunction "1_1") (pintype "passive"))
    )
    (net (code "474") (name "Net-(IC22B--IN)") (class "Default")
      (node (ref "IC22") (pin "6") (pinfunction "-IN_6") (pintype "input"))
      (node (ref "IC22") (pin "8") (pinfunction "-IN_8") (pintype "input"))
      (node (ref "R174") (pin "1") (pinfunction "1_1") (pintype "passive"))
    )
    (net (code "475") (name "Net-(IC22B-OUT)") (class "Default")
      (node (ref "IC22") (pin "1") (pinfunction "OUT_1") (pintype "open_collector"))
      (node (ref "R176") (pin "2") (pinfunction "2_2") (pintype "passive"))
      (node (ref "R181") (pin "2") (pinfunction "2_2") (pintype "passive"))
    )
    (net (code "476") (name "Net-(IC22C-+IN)") (class "Default")
      (node (ref "C31") (pin "1") (pinfunction "1_1") (pintype "passive"))
      (node (ref "IC22") (pin "9") (pinfunction "+IN_9") (pintype "input"))
      (node (ref "R183") (pin "2") (pinfunction "2_2") (pintype "passive"))
      (node (ref "R192") (pin "2") (pinfunction "2_2") (pintype "passive"))
    )
    (net (code "477") (name "Net-(IC22C-OUT)") (class "Default")
      (node (ref "C32") (pin "2") (pinfunction "2_2") (pintype "passive"))
      (node (ref "IC22") (pin "14") (pinfunction "OUT_14") (pintype "open_collector"))
      (node (ref "R182") (pin "2") (pinfunction "2_2") (pintype "passive"))
    )
    (net (code "478") (name "Net-(IC22D-OUT)") (class "Default")
      (node (ref "IC22") (pin "13") (pinfunction "OUT_13") (pintype "open_collector"))
      (node (ref "JP12") (pin "1") (pinfunction "1_1") (pintype "passive"))
      (node (ref "Q29") (pin "1") (pinfunction "G_1") (pintype "passive"))
      (node (ref "R195") (pin "2") (pinfunction "2_2") (pintype "passive"))
    )
    (net (code "479") (name "Net-(IC24-Q)") (class "Default")
      (node (ref "IC24") (pin "3") (pinfunction "Q_3") (pintype "output"))
      (node (ref "IC25") (pin "12") (pinfunction "A_12") (pintype "input"))
      (node (ref "IC25") (pin "4") (pinfunction "A_4") (pintype "input"))
    )
    (net (code "480") (name "Net-(IC25A-T2)") (class "Default")
      (node (ref "C37") (pin "2") (pinfunction "2_2") (pintype "passive"))
      (node (ref "IC25") (pin "2") (pinfunction "T2_2") (pintype "input"))
      (node (ref "R218") (pin "1") (pinfunction "1_1") (pintype "passive"))
    )
    (net (code "481") (name "Net-(IC25A-~{Q})") (class "Default")
      (node (ref "IC25") (pin "7") (pinfunction "~{Q}_7") (pintype "output"))
      (node (ref "Q33") (pin "1") (pinfunction "G_1") (pintype "passive"))
    )
    (net (code "482") (name "Net-(IC25B-B)") (class "Default")
      (node (ref "IC25") (pin "11") (pinfunction "B_11") (pintype "input"))
      (node (ref "IC25") (pin "9") (pinfunction "~{Q}_9") (pintype "output"))
      (node (ref "R203") (pin "2") (pinfunction "2_2") (pintype "passive"))
    )
    (net (code "483") (name "Net-(IC25B-T2)") (class "Default")
      (node (ref "C35") (pin "1") (pinfunction "1_1") (pintype "passive"))
      (node (ref "IC25") (pin "14") (pinfunction "T2_14") (pintype "input"))
      (node (ref "R201") (pin "1") (pinfunction "1_1") (pintype "passive"))
    )
    (net (code "484") (name "Net-(IC27A-+IN)") (class "Default")
      (node (ref "C30") (pin "1") (pinfunction "1_1") (pintype "passive"))
      (node (ref "IC27") (pin "3") (pinfunction "+IN_3") (pintype "input"))
      (node (ref "R172") (pin "1") (pinfunction "1_1") (pintype "passive"))
    )
    (net (code "485") (name "Net-(IC27A--IN)") (class "Default")
      (node (ref "IC27") (pin "2") (pinfunction "-IN_2") (pintype "input"))
      (node (ref "R173") (pin "2") (pinfunction "2_2") (pintype "passive"))
    )
    (net (code "486") (name "Net-(IC27A-OUT)") (class "Default")
      (node (ref "IC27") (pin "1") (pinfunction "OUT_1") (pintype "output"))
      (node (ref "R204") (pin "2") (pinfunction "2_2") (pintype "passive"))
    )
    (net (code "487") (name "Net-(IC27B-+IN)") (class "Default")
      (node (ref "IC27") (pin "5") (pinfunction "+IN_5") (pintype "input"))
      (node (ref "Q31") (pin "3") (pinfunction "D_3") (pintype "passive"))
      (node (ref "R205") (pin "2") (pinfunction "2_2") (pintype "passive"))
      (node (ref "R206") (pin "2") (pinfunction "2_2") (pintype "passive"))
    )
    (net (code "488") (name "Net-(IC27B--IN)") (class "Default")
      (node (ref "IC27") (pin "6") (pinfunction "-IN_6") (pintype "input"))
      (node (ref "R207") (pin "1") (pinfunction "1_1") (pintype "passive"))
      (node (ref "R208") (pin "2") (pinfunction "2_2") (pintype "passive"))
    )
    (net (code "489") (name "Net-(IC27B-OUT)") (class "Default")
      (node (ref "IC27") (pin "7") (pinfunction "OUT_7") (pintype "output"))
      (node (ref "R186") (pin "2") (pinfunction "2_2") (pintype "passive"))
      (node (ref "R193") (pin "1") (pinfunction "1_1") (pintype "passive"))
      (node (ref "R206") (pin "1") (pinfunction "1_1") (pintype "passive"))
    )
    (net (code "490") (name "Net-(IC28A-A)") (class "Default")
      (node (ref "IC28") (pin "10") (pinfunction "A_10") (pintype "input"))
      (node (ref "R226") (pin "1") (pinfunction "1_1") (pintype "passive"))
      (node (ref "R267") (pin "1") (pinfunction "1_1") (pintype "passive"))
      (node (ref "R267") (pin "2") (pinfunction "2_2") (pintype "passive"))
      (node (ref "X10") (pin "4") (pinfunction "4_4") (pintype "passive"))
      (node (ref "X11") (pin "2") (pinfunction "S_2") (pintype "passive"))
    )
    (net (code "491") (name "Net-(IC28A-B)") (class "Default")
      (node (ref "IC28") (pin "13") (pinfunction "B_13") (pintype "input"))
      (node (ref "R225") (pin "1") (pinfunction "1_1") (pintype "passive"))
      (node (ref "R266") (pin "1") (pinfunction "1_1") (pintype "passive"))
      (node (ref "R266") (pin "2") (pinfunction "2_2") (pintype "passive"))
      (node (ref "X10") (pin "3") (pinfunction "3_3") (pintype "passive"))
      (node (ref "X11") (pin "3") (pinfunction "S_3") (pintype "passive"))
    )
    (net (code "492") (name "Net-(IC28A-C)") (class "Default")
      (node (ref "IC28") (pin "12") (pinfunction "C_12") (pintype "input"))
      (node (ref "R224") (pin "1") (pinfunction "1_1") (pintype "passive"))
      (node (ref "R265") (pin "1") (pinfunction "1_1") (pintype "passive"))
      (node (ref "R265") (pin "2") (pinfunction "2_2") (pintype "passive"))
      (node (ref "X10") (pin "2") (pinfunction "2_2") (pintype "passive"))
      (node (ref "X11") (pin "4") (pinfunction "S_4") (pintype "passive"))
    )
    (net (code "493") (name "Net-(IC28A-Q0)") (class "Default")
      (node (ref "IC28") (pin "3") (pinfunction "Q0_3") (pintype "output"))
      (node (ref "IC30") (pin "1") (pinfunction "I1_1") (pintype "input"))
      (node (ref "IC30") (pin "2") (pinfunction "I2_2") (pintype "input"))
      (node (ref "Q40") (pin "1") (pinfunction "G_1") (pintype "passive"))
      (node (ref "Q41") (pin "1") (pinfunction "G_1") (pintype "passive"))
    )
    (net (code "494") (name "Net-(IC28A-Q1)") (class "Default")
      (node (ref "IC28") (pin "14") (pinfunction "Q1_14") (pintype "output"))
      (node (ref "IC30") (pin "6") (pinfunction "I6_6") (pintype "input"))
    )
    (net (code "495") (name "Net-(IC28A-Q2)") (class "Default")
      (node (ref "IC28") (pin "2") (pinfunction "Q2_2") (pintype "output"))
      (node (ref "IC30") (pin "7") (pinfunction "I7_7") (pintype "input"))
    )
    (net (code "496") (name "Net-(IC28A-Q3)") (class "Default")
      (node (ref "IC28") (pin "15") (pinfunction "Q3_15") (pintype "output"))
      (node (ref "IC30") (pin "5") (pinfunction "I5_5") (pintype "input"))
    )
    (net (code "497") (name "Net-(IC28A-Q4)") (class "Default")
      (node (ref "IC28") (pin "1") (pinfunction "Q4_1") (pintype "output"))
      (node (ref "IC30") (pin "4") (pinfunction "I4_4") (pintype "input"))
    )
    (net (code "498") (name "Net-(IC28A-Q5)") (class "Default")
      (node (ref "IC28") (pin "6") (pinfunction "Q5_6") (pintype "output"))
      (node (ref "IC30") (pin "3") (pinfunction "I3_3") (pintype "input"))
    )
    (net (code "499") (name "Net-(IC29-ADJ)") (class "Default")
      (node (ref "IC29") (pin "1") (pinfunction "ADJ_1") (pintype "input"))
      (node (ref "R222") (pin "1") (pinfunction "1_1") (pintype "passive"))
      (node (ref "R229") (pin "2") (pinfunction "2_2") (pintype "passive"))
      (node (ref "X10") (pin "7") (pinfunction "7_7") (pintype "passive"))
    )
    (net (code "500") (name "Net-(IC29-VI)") (class "Default")
      (node (ref "IC29") (pin "3") (pinfunction "VI_3") (pintype "input"))
      (node (ref "Q37") (pin "2") (pinfunction "C_2") (pintype "passive"))
    )
    (net (code "501") (name "Net-(IC29-VO)") (class "Default")
      (node (ref "IC29") (pin "2") (pinfunction "VO_2") (pintype "passive"))
      (node (ref "R222") (pin "2") (pinfunction "2_2") (pintype "passive"))
    )
    (net (code "502") (name "Net-(IC30-O1)") (class "Default")
      (node (ref "IC30") (pin "16") (pinfunction "O1_16") (pintype "open_collector"))
      (node (ref "Q40") (pin "3") (pinfunction "D_3") (pintype "passive"))
      (node (ref "R271") (pin "1") (pinfunction "1_1") (pintype "passive"))
    )
    (net (code "503") (name "Net-(IC30-O2)") (class "Default")
      (node (ref "IC30") (pin "15") (pinfunction "O2_15") (pintype "open_collector"))
      (node (ref "R244") (pin "1") (pinfunction "1_1") (pintype "passive"))
    )
    (net (code "504") (name "Net-(IC31A-+IN)") (class "Default")
      (node (ref "IC31") (pin "11") (pinfunction "+IN_11") (pintype "input"))
      (node (ref "IC31") (pin "5") (pinfunction "+IN_5") (pintype "input"))
      (node (ref "R233") (pin "1") (pinfunction "1_1") (pintype "passive"))
      (node (ref "R234") (pin "2") (pinfunction "2_2") (pintype "passive"))
      (node (ref "R235") (pin "2") (pinfunction "2_2") (pintype "passive"))
    )
    (net (code "505") (name "Net-(IC31A--IN)") (class "Default")
      (node (ref "C40") (pin "1") (pinfunction "1_1") (pintype "passive"))
      (node (ref "IC31") (pin "10") (pinfunction "-IN_10") (pintype "input"))
      (node (ref "IC31") (pin "4") (pinfunction "-IN_4") (pintype "input"))
      (node (ref "R232") (pin "1") (pinfunction "1_1") (pintype "passive"))
    )
    (net (code "506") (name "Net-(IC31A-OUT)") (class "Default")
      (node (ref "IC31") (pin "2") (pinfunction "OUT_2") (pintype "open_collector"))
      (node (ref "R235") (pin "1") (pinfunction "1_1") (pintype "passive"))
    )
    (net (code "507") (name "Net-(IC31B-+IN)") (class "Default")
      (node (ref "IC31") (pin "7") (pinfunction "+IN_7") (pintype "input"))
      (node (ref "R230") (pin "1") (pinfunction "1_1") (pintype "passive"))
      (node (ref "R247") (pin "1") (pinfunction "1_1") (pintype "passive"))
    )
    (net (code "508") (name "Net-(IC31B--IN)") (class "Default")
      (node (ref "IC31") (pin "6") (pinfunction "-IN_6") (pintype "input"))
      (node (ref "IC31") (pin "8") (pinfunction "-IN_8") (pintype "input"))
      (node (ref "R229") (pin "1") (pinfunction "1_1") (pintype "passive"))
    )
    (net (code "509") (name "Net-(IC31B-OUT)") (class "Default")
      (node (ref "IC31") (pin "1") (pinfunction "OUT_1") (pintype "open_collector"))
      (node (ref "R231") (pin "2") (pinfunction "2_2") (pintype "passive"))
      (node (ref "R236") (pin "2") (pinfunction "2_2") (pintype "passive"))
    )
    (net (code "510") (name "Net-(IC31C-+IN)") (class "Default")
      (node (ref "C43") (pin "1") (pinfunction "1_1") (pintype "passive"))
      (node (ref "IC31") (pin "9") (pinfunction "+IN_9") (pintype "input"))
      (node (ref "R238") (pin "2") (pinfunction "2_2") (pintype "passive"))
      (node (ref "R247") (pin "2") (pinfunction "2_2") (pintype "passive"))
    )
    (net (code "511") (name "Net-(IC31C-OUT)") (class "Default")
      (node (ref "C44") (pin "2") (pinfunction "2_2") (pintype "passive"))
      (node (ref "IC31") (pin "14") (pinfunction "OUT_14") (pintype "open_collector"))
      (node (ref "R237") (pin "2") (pinfunction "2_2") (pintype "passive"))
    )
    (net (code "512") (name "Net-(IC31D-OUT)") (class "Default")
      (node (ref "IC31") (pin "13") (pinfunction "OUT_13") (pintype "open_collector"))
      (node (ref "JP17") (pin "1") (pinfunction "1_1") (pintype "passive"))
      (node (ref "Q39") (pin "1") (pinfunction "G_1") (pintype "passive"))
      (node (ref "R250") (pin "2") (pinfunction "2_2") (pintype "passive"))
    )
    (net (code "513") (name "Net-(IC33-Q)") (class "Default")
      (node (ref "IC33") (pin "3") (pinfunction "Q_3") (pintype "output"))
      (node (ref "IC34") (pin "12") (pinfunction "A_12") (pintype "input"))
      (node (ref "IC34") (pin "4") (pinfunction "A_4") (pintype "input"))
    )
    (net (code "514") (name "Net-(IC34A-T2)") (class "Default")
      (node (ref "C49") (pin "2") (pinfunction "2_2") (pintype "passive"))
      (node (ref "IC34") (pin "2") (pinfunction "T2_2") (pintype "input"))
      (node (ref "R273") (pin "1") (pinfunction "1_1") (pintype "passive"))
    )
    (net (code "515") (name "Net-(IC34A-~{Q})") (class "Default")
      (node (ref "IC34") (pin "7") (pinfunction "~{Q}_7") (pintype "output"))
      (node (ref "Q43") (pin "1") (pinfunction "G_1") (pintype "passive"))
    )
    (net (code "516") (name "Net-(IC34B-B)") (class "Default")
      (node (ref "IC34") (pin "11") (pinfunction "B_11") (pintype "input"))
      (node (ref "IC34") (pin "9") (pinfunction "~{Q}_9") (pintype "output"))
      (node (ref "R258") (pin "2") (pinfunction "2_2") (pintype "passive"))
    )
    (net (code "517") (name "Net-(IC34B-T2)") (class "Default")
      (node (ref "C47") (pin "1") (pinfunction "1_1") (pintype "passive"))
      (node (ref "IC34") (pin "14") (pinfunction "T2_14") (pintype "input"))
      (node (ref "R256") (pin "1") (pinfunction "1_1") (pintype "passive"))
    )
    (net (code "518") (name "Net-(IC36A-+IN)") (class "Default")
      (node (ref "C42") (pin "1") (pinfunction "1_1") (pintype "passive"))
      (node (ref "IC36") (pin "3") (pinfunction "+IN_3") (pintype "input"))
      (node (ref "R227") (pin "1") (pinfunction "1_1") (pintype "passive"))
    )
    (net (code "519") (name "Net-(IC36A--IN)") (class "Default")
      (node (ref "IC36") (pin "2") (pinfunction "-IN_2") (pintype "input"))
      (node (ref "R228") (pin "2") (pinfunction "2_2") (pintype "passive"))
    )
    (net (code "520") (name "Net-(IC36A-OUT)") (class "Default")
      (node (ref "IC36") (pin "1") (pinfunction "OUT_1") (pintype "output"))
      (node (ref "R259") (pin "2") (pinfunction "2_2") (pintype "passive"))
    )
    (net (code "521") (name "Net-(IC36B-+IN)") (class "Default")
      (node (ref "IC36") (pin "5") (pinfunction "+IN_5") (pintype "input"))
      (node (ref "Q41") (pin "3") (pinfunction "D_3") (pintype "passive"))
      (node (ref "R260") (pin "2") (pinfunction "2_2") (pintype "passive"))
      (node (ref "R261") (pin "2") (pinfunction "2_2") (pintype "passive"))
    )
    (net (code "522") (name "Net-(IC36B--IN)") (class "Default")
      (node (ref "IC36") (pin "6") (pinfunction "-IN_6") (pintype "input"))
      (node (ref "R262") (pin "1") (pinfunction "1_1") (pintype "passive"))
      (node (ref "R263") (pin "2") (pinfunction "2_2") (pintype "passive"))
    )
    (net (code "523") (name "Net-(IC36B-OUT)") (class "Default")
      (node (ref "IC36") (pin "7") (pinfunction "OUT_7") (pintype "output"))
      (node (ref "R241") (pin "2") (pinfunction "2_2") (pintype "passive"))
      (node (ref "R248") (pin "1") (pinfunction "1_1") (pintype "passive"))
      (node (ref "R261") (pin "1") (pinfunction "1_1") (pintype "passive"))
    )
    (net (code "524") (name "Net-(IC37A-A)") (class "Default")
      (node (ref "IC37") (pin "10") (pinfunction "A_10") (pintype "input"))
      (node (ref "R281") (pin "1") (pinfunction "1_1") (pintype "passive"))
      (node (ref "R322") (pin "1") (pinfunction "1_1") (pintype "passive"))
      (node (ref "R322") (pin "2") (pinfunction "2_2") (pintype "passive"))
      (node (ref "X13") (pin "4") (pinfunction "4_4") (pintype "passive"))
      (node (ref "X14") (pin "2") (pinfunction "S_2") (pintype "passive"))
    )
    (net (code "525") (name "Net-(IC37A-B)") (class "Default")
      (node (ref "IC37") (pin "13") (pinfunction "B_13") (pintype "input"))
      (node (ref "R280") (pin "1") (pinfunction "1_1") (pintype "passive"))
      (node (ref "R321") (pin "1") (pinfunction "1_1") (pintype "passive"))
      (node (ref "R321") (pin "2") (pinfunction "2_2") (pintype "passive"))
      (node (ref "X13") (pin "3") (pinfunction "3_3") (pintype "passive"))
      (node (ref "X14") (pin "3") (pinfunction "S_3") (pintype "passive"))
    )
    (net (code "526") (name "Net-(IC37A-C)") (class "Default")
      (node (ref "IC37") (pin "12") (pinfunction "C_12") (pintype "input"))
      (node (ref "R279") (pin "1") (pinfunction "1_1") (pintype "passive"))
      (node (ref "R320") (pin "1") (pinfunction "1_1") (pintype "passive"))
      (node (ref "R320") (pin "2") (pinfunction "2_2") (pintype "passive"))
      (node (ref "X13") (pin "2") (pinfunction "2_2") (pintype "passive"))
      (node (ref "X14") (pin "4") (pinfunction "S_4") (pintype "passive"))
    )
    (net (code "527") (name "Net-(IC37A-Q0)") (class "Default")
      (node (ref "IC37") (pin "3") (pinfunction "Q0_3") (pintype "output"))
      (node (ref "IC39") (pin "1") (pinfunction "I1_1") (pintype "input"))
      (node (ref "IC39") (pin "2") (pinfunction "I2_2") (pintype "input"))
      (node (ref "Q50") (pin "1") (pinfunction "G_1") (pintype "passive"))
      (node (ref "Q51") (pin "1") (pinfunction "G_1") (pintype "passive"))
    )
    (net (code "528") (name "Net-(IC37A-Q1)") (class "Default")
      (node (ref "IC37") (pin "14") (pinfunction "Q1_14") (pintype "output"))
      (node (ref "IC39") (pin "6") (pinfunction "I6_6") (pintype "input"))
    )
    (net (code "529") (name "Net-(IC37A-Q2)") (class "Default")
      (node (ref "IC37") (pin "2") (pinfunction "Q2_2") (pintype "output"))
      (node (ref "IC39") (pin "7") (pinfunction "I7_7") (pintype "input"))
    )
    (net (code "530") (name "Net-(IC37A-Q3)") (class "Default")
      (node (ref "IC37") (pin "15") (pinfunction "Q3_15") (pintype "output"))
      (node (ref "IC39") (pin "5") (pinfunction "I5_5") (pintype "input"))
    )
    (net (code "531") (name "Net-(IC37A-Q4)") (class "Default")
      (node (ref "IC37") (pin "1") (pinfunction "Q4_1") (pintype "output"))
      (node (ref "IC39") (pin "4") (pinfunction "I4_4") (pintype "input"))
    )
    (net (code "532") (name "Net-(IC37A-Q5)") (class "Default")
      (node (ref "IC37") (pin "6") (pinfunction "Q5_6") (pintype "output"))
      (node (ref "IC39") (pin "3") (pinfunction "I3_3") (pintype "input"))
    )
    (net (code "533") (name "Net-(IC38-ADJ)") (class "Default")
      (node (ref "IC38") (pin "1") (pinfunction "ADJ_1") (pintype "input"))
      (node (ref "R277") (pin "1") (pinfunction "1_1") (pintype "passive"))
      (node (ref "R284") (pin "2") (pinfunction "2_2") (pintype "passive"))
      (node (ref "X13") (pin "7") (pinfunction "7_7") (pintype "passive"))
    )
    (net (code "534") (name "Net-(IC38-VI)") (class "Default")
      (node (ref "IC38") (pin "3") (pinfunction "VI_3") (pintype "input"))
      (node (ref "Q47") (pin "2") (pinfunction "C_2") (pintype "passive"))
    )
    (net (code "535") (name "Net-(IC38-VO)") (class "Default")
      (node (ref "IC38") (pin "2") (pinfunction "VO_2") (pintype "passive"))
      (node (ref "R277") (pin "2") (pinfunction "2_2") (pintype "passive"))
    )
    (net (code "536") (name "Net-(IC39-O1)") (class "Default")
      (node (ref "IC39") (pin "16") (pinfunction "O1_16") (pintype "open_collector"))
      (node (ref "Q50") (pin "3") (pinfunction "D_3") (pintype "passive"))
      (node (ref "R326") (pin "1") (pinfunction "1_1") (pintype "passive"))
    )
    (net (code "537") (name "Net-(IC39-O2)") (class "Default")
      (node (ref "IC39") (pin "15") (pinfunction "O2_15") (pintype "open_collector"))
      (node (ref "R299") (pin "1") (pinfunction "1_1") (pintype "passive"))
    )
    (net (code "538") (name "Net-(IC40A-+IN)") (class "Default")
      (node (ref "IC40") (pin "11") (pinfunction "+IN_11") (pintype "input"))
      (node (ref "IC40") (pin "5") (pinfunction "+IN_5") (pintype "input"))
      (node (ref "R288") (pin "1") (pinfunction "1_1") (pintype "passive"))
      (node (ref "R289") (pin "2") (pinfunction "2_2") (pintype "passive"))
      (node (ref "R290") (pin "2") (pinfunction "2_2") (pintype "passive"))
    )
    (net (code "539") (name "Net-(IC40A--IN)") (class "Default")
      (node (ref "C52") (pin "1") (pinfunction "1_1") (pintype "passive"))
      (node (ref "IC40") (pin "10") (pinfunction "-IN_10") (pintype "input"))
      (node (ref "IC40") (pin "4") (pinfunction "-IN_4") (pintype "input"))
      (node (ref "R287") (pin "1") (pinfunction "1_1") (pintype "passive"))
    )
    (net (code "540") (name "Net-(IC40A-OUT)") (class "Default")
      (node (ref "IC40") (pin "2") (pinfunction "OUT_2") (pintype "open_collector"))
      (node (ref "R290") (pin "1") (pinfunction "1_1") (pintype "passive"))
    )
    (net (code "541") (name "Net-(IC40B-+IN)") (class "Default")
      (node (ref "IC40") (pin "7") (pinfunction "+IN_7") (pintype "input"))
      (node (ref "R285") (pin "1") (pinfunction "1_1") (pintype "passive"))
      (node (ref "R302") (pin "1") (pinfunction "1_1") (pintype "passive"))
    )
    (net (code "542") (name "Net-(IC40B--IN)") (class "Default")
      (node (ref "IC40") (pin "6") (pinfunction "-IN_6") (pintype "input"))
      (node (ref "IC40") (pin "8") (pinfunction "-IN_8") (pintype "input"))
      (node (ref "R284") (pin "1") (pinfunction "1_1") (pintype "passive"))
    )
    (net (code "543") (name "Net-(IC40B-OUT)") (class "Default")
      (node (ref "IC40") (pin "1") (pinfunction "OUT_1") (pintype "open_collector"))
      (node (ref "R286") (pin "2") (pinfunction "2_2") (pintype "passive"))
      (node (ref "R291") (pin "2") (pinfunction "2_2") (pintype "passive"))
    )
    (net (code "544") (name "Net-(IC40C-+IN)") (class "Default")
      (node (ref "C55") (pin "1") (pinfunction "1_1") (pintype "passive"))
      (node (ref "IC40") (pin "9") (pinfunction "+IN_9") (pintype "input"))
      (node (ref "R293") (pin "2") (pinfunction "2_2") (pintype "passive"))
      (node (ref "R302") (pin "2") (pinfunction "2_2") (pintype "passive"))
    )
    (net (code "545") (name "Net-(IC40C-OUT)") (class "Default")
      (node (ref "C56") (pin "2") (pinfunction "2_2") (pintype "passive"))
      (node (ref "IC40") (pin "14") (pinfunction "OUT_14") (pintype "open_collector"))
      (node (ref "R292") (pin "2") (pinfunction "2_2") (pintype "passive"))
    )
    (net (code "546") (name "Net-(IC40D-OUT)") (class "Default")
      (node (ref "IC40") (pin "13") (pinfunction "OUT_13") (pintype "open_collector"))
      (node (ref "JP22") (pin "1") (pinfunction "1_1") (pintype "passive"))
      (node (ref "Q49") (pin "1") (pinfunction "G_1") (pintype "passive"))
      (node (ref "R305") (pin "2") (pinfunction "2_2") (pintype "passive"))
    )
    (net (code "547") (name "Net-(IC42-Q)") (class "Default")
      (node (ref "IC42") (pin "3") (pinfunction "Q_3") (pintype "output"))
      (node (ref "IC43") (pin "12") (pinfunction "A_12") (pintype "input"))
      (node (ref "IC43") (pin "4") (pinfunction "A_4") (pintype "input"))
    )
    (net (code "548") (name "Net-(IC43A-T2)") (class "Default")
      (node (ref "C61") (pin "2") (pinfunction "2_2") (pintype "passive"))
      (node (ref "IC43") (pin "2") (pinfunction "T2_2") (pintype "input"))
      (node (ref "R328") (pin "1") (pinfunction "1_1") (pintype "passive"))
    )
    (net (code "549") (name "Net-(IC43A-~{Q})") (class "Default")
      (node (ref "IC43") (pin "7") (pinfunction "~{Q}_7") (pintype "output"))
      (node (ref "Q53") (pin "1") (pinfunction "G_1") (pintype "passive"))
    )
    (net (code "550") (name "Net-(IC43B-B)") (class "Default")
      (node (ref "IC43") (pin "11") (pinfunction "B_11") (pintype "input"))
      (node (ref "IC43") (pin "9") (pinfunction "~{Q}_9") (pintype "output"))
      (node (ref "R313") (pin "2") (pinfunction "2_2") (pintype "passive"))
    )
    (net (code "551") (name "Net-(IC43B-T2)") (class "Default")
      (node (ref "C59") (pin "1") (pinfunction "1_1") (pintype "passive"))
      (node (ref "IC43") (pin "14") (pinfunction "T2_14") (pintype "input"))
      (node (ref "R311") (pin "1") (pinfunction "1_1") (pintype "passive"))
    )
    (net (code "552") (name "Net-(IC45A-+IN)") (class "Default")
      (node (ref "C54") (pin "1") (pinfunction "1_1") (pintype "passive"))
      (node (ref "IC45") (pin "3") (pinfunction "+IN_3") (pintype "input"))
      (node (ref "R282") (pin "1") (pinfunction "1_1") (pintype "passive"))
    )
    (net (code "553") (name "Net-(IC45A--IN)") (class "Default")
      (node (ref "IC45") (pin "2") (pinfunction "-IN_2") (pintype "input"))
      (node (ref "R283") (pin "2") (pinfunction "2_2") (pintype "passive"))
    )
    (net (code "554") (name "Net-(IC45A-OUT)") (class "Default")
      (node (ref "IC45") (pin "1") (pinfunction "OUT_1") (pintype "output"))
      (node (ref "R314") (pin "2") (pinfunction "2_2") (pintype "passive"))
    )
    (net (code "555") (name "Net-(IC45B-+IN)") (class "Default")
      (node (ref "IC45") (pin "5") (pinfunction "+IN_5") (pintype "input"))
      (node (ref "Q51") (pin "3") (pinfunction "D_3") (pintype "passive"))
      (node (ref "R315") (pin "2") (pinfunction "2_2") (pintype "passive"))
      (node (ref "R316") (pin "2") (pinfunction "2_2") (pintype "passive"))
    )
    (net (code "556") (name "Net-(IC45B--IN)") (class "Default")
      (node (ref "IC45") (pin "6") (pinfunction "-IN_6") (pintype "input"))
      (node (ref "R317") (pin "1") (pinfunction "1_1") (pintype "passive"))
      (node (ref "R318") (pin "2") (pinfunction "2_2") (pintype "passive"))
    )
    (net (code "557") (name "Net-(IC45B-OUT)") (class "Default")
      (node (ref "IC45") (pin "7") (pinfunction "OUT_7") (pintype "output"))
      (node (ref "R296") (pin "2") (pinfunction "2_2") (pintype "passive"))
      (node (ref "R303") (pin "1") (pinfunction "1_1") (pintype "passive"))
      (node (ref "R316") (pin "1") (pinfunction "1_1") (pintype "passive"))
    )
    (net (code "558") (name "Net-(IC46A-A)") (class "Default")
      (node (ref "IC46") (pin "10") (pinfunction "A_10") (pintype "input"))
      (node (ref "R349") (pin "1") (pinfunction "1_1") (pintype "passive"))
      (node (ref "R349") (pin "2") (pinfunction "2_2") (pintype "passive"))
      (node (ref "R88") (pin "1") (pinfunction "1_1") (pintype "passive"))
      (node (ref "X16") (pin "4") (pinfunction "4_4") (pintype "passive"))
      (node (ref "X17") (pin "2") (pinfunction "S_2") (pintype "passive"))
    )
    (net (code "559") (name "Net-(IC46A-B)") (class "Default")
      (node (ref "IC46") (pin "13") (pinfunction "B_13") (pintype "input"))
      (node (ref "R348") (pin "1") (pinfunction "1_1") (pintype "passive"))
      (node (ref "R348") (pin "2") (pinfunction "2_2") (pintype "passive"))
      (node (ref "R86") (pin "1") (pinfunction "1_1") (pintype "passive"))
      (node (ref "X16") (pin "3") (pinfunction "3_3") (pintype "passive"))
      (node (ref "X17") (pin "3") (pinfunction "S_3") (pintype "passive"))
    )
    (net (code "560") (name "Net-(IC46A-C)") (class "Default")
      (node (ref "IC46") (pin "12") (pinfunction "C_12") (pintype "input"))
      (node (ref "R347") (pin "1") (pinfunction "1_1") (pintype "passive"))
      (node (ref "R347") (pin "2") (pinfunction "2_2") (pintype "passive"))
      (node (ref "R43") (pin "1") (pinfunction "1_1") (pintype "passive"))
      (node (ref "X16") (pin "2") (pinfunction "2_2") (pintype "passive"))
      (node (ref "X17") (pin "4") (pinfunction "S_4") (pintype "passive"))
    )
    (net (code "561") (name "Net-(IC46A-Q0)") (class "Default")
      (node (ref "IC46") (pin "3") (pinfunction "Q0_3") (pintype "output"))
      (node (ref "IC48") (pin "1") (pinfunction "I1_1") (pintype "input"))
      (node (ref "IC48") (pin "2") (pinfunction "I2_2") (pintype "input"))
      (node (ref "Q60") (pin "1") (pinfunction "G_1") (pintype "passive"))
      (node (ref "Q61") (pin "1") (pinfunction "G_1") (pintype "passive"))
    )
    (net (code "562") (name "Net-(IC46A-Q1)") (class "Default")
      (node (ref "IC46") (pin "14") (pinfunction "Q1_14") (pintype "output"))
      (node (ref "IC48") (pin "6") (pinfunction "I6_6") (pintype "input"))
    )
    (net (code "563") (name "Net-(IC46A-Q2)") (class "Default")
      (node (ref "IC46") (pin "2") (pinfunction "Q2_2") (pintype "output"))
      (node (ref "IC48") (pin "7") (pinfunction "I7_7") (pintype "input"))
    )
    (net (code "564") (name "Net-(IC46A-Q3)") (class "Default")
      (node (ref "IC46") (pin "15") (pinfunction "Q3_15") (pintype "output"))
      (node (ref "IC48") (pin "5") (pinfunction "I5_5") (pintype "input"))
    )
    (net (code "565") (name "Net-(IC46A-Q4)") (class "Default")
      (node (ref "IC46") (pin "1") (pinfunction "Q4_1") (pintype "output"))
      (node (ref "IC48") (pin "4") (pinfunction "I4_4") (pintype "input"))
    )
    (net (code "566") (name "Net-(IC46A-Q5)") (class "Default")
      (node (ref "IC46") (pin "6") (pinfunction "Q5_6") (pintype "output"))
      (node (ref "IC48") (pin "3") (pinfunction "I3_3") (pintype "input"))
    )
    (net (code "567") (name "Net-(IC47-ADJ)") (class "Default")
      (node (ref "IC47") (pin "1") (pinfunction "ADJ_1") (pintype "input"))
      (node (ref "R104") (pin "2") (pinfunction "2_2") (pintype "passive"))
      (node (ref "R33") (pin "1") (pinfunction "1_1") (pintype "passive"))
      (node (ref "X16") (pin "7") (pinfunction "7_7") (pintype "passive"))
    )
    (net (code "568") (name "Net-(IC47-VI)") (class "Default")
      (node (ref "IC47") (pin "3") (pinfunction "VI_3") (pintype "input"))
      (node (ref "Q57") (pin "2") (pinfunction "C_2") (pintype "passive"))
    )
    (net (code "569") (name "Net-(IC47-VO)") (class "Default")
      (node (ref "IC47") (pin "2") (pinfunction "VO_2") (pintype "passive"))
      (node (ref "R33") (pin "2") (pinfunction "2_2") (pintype "passive"))
    )
    (net (code "570") (name "Net-(IC48-O1)") (class "Default")
      (node (ref "IC48") (pin "16") (pinfunction "O1_16") (pintype "open_collector"))
      (node (ref "Q60") (pin "3") (pinfunction "D_3") (pintype "passive"))
      (node (ref "R353") (pin "1") (pinfunction "1_1") (pintype "passive"))
    )
    (net (code "571") (name "Net-(IC48-O2)") (class "Default")
      (node (ref "IC48") (pin "15") (pinfunction "O2_15") (pintype "open_collector"))
      (node (ref "R295") (pin "1") (pinfunction "1_1") (pintype "passive"))
    )
    (net (code "572") (name "Net-(IC49A-+IN)") (class "Default")
      (node (ref "IC49") (pin "11") (pinfunction "+IN_11") (pintype "input"))
      (node (ref "IC49") (pin "5") (pinfunction "+IN_5") (pintype "input"))
      (node (ref "R185") (pin "1") (pinfunction "1_1") (pintype "passive"))
      (node (ref "R187") (pin "2") (pinfunction "2_2") (pintype "passive"))
      (node (ref "R188") (pin "2") (pinfunction "2_2") (pintype "passive"))
    )
    (net (code "573") (name "Net-(IC49A--IN)") (class "Default")
      (node (ref "C64") (pin "1") (pinfunction "1_1") (pintype "passive"))
      (node (ref "IC49") (pin "10") (pinfunction "-IN_10") (pintype "input"))
      (node (ref "IC49") (pin "4") (pinfunction "-IN_4") (pintype "input"))
      (node (ref "R144") (pin "1") (pinfunction "1_1") (pintype "passive"))
    )
    (net (code "574") (name "Net-(IC49A-OUT)") (class "Default")
      (node (ref "IC49") (pin "2") (pinfunction "OUT_2") (pintype "open_collector"))
      (node (ref "R188") (pin "1") (pinfunction "1_1") (pintype "passive"))
    )
    (net (code "575") (name "Net-(IC49B-+IN)") (class "Default")
      (node (ref "IC49") (pin "7") (pinfunction "+IN_7") (pintype "input"))
      (node (ref "R142") (pin "1") (pinfunction "1_1") (pintype "passive"))
      (node (ref "R307") (pin "1") (pinfunction "1_1") (pintype "passive"))
    )
    (net (code "576") (name "Net-(IC49B--IN)") (class "Default")
      (node (ref "IC49") (pin "6") (pinfunction "-IN_6") (pintype "input"))
      (node (ref "IC49") (pin "8") (pinfunction "-IN_8") (pintype "input"))
      (node (ref "R104") (pin "1") (pinfunction "1_1") (pintype "passive"))
    )
    (net (code "577") (name "Net-(IC49B-OUT)") (class "Default")
      (node (ref "IC49") (pin "1") (pinfunction "OUT_1") (pintype "open_collector"))
      (node (ref "R143") (pin "2") (pinfunction "2_2") (pintype "passive"))
      (node (ref "R197") (pin "2") (pinfunction "2_2") (pintype "passive"))
    )
    (net (code "578") (name "Net-(IC49C-+IN)") (class "Default")
      (node (ref "C67") (pin "1") (pinfunction "1_1") (pintype "passive"))
      (node (ref "IC49") (pin "9") (pinfunction "+IN_9") (pintype "input"))
      (node (ref "R242") (pin "2") (pinfunction "2_2") (pintype "passive"))
      (node (ref "R307") (pin "2") (pinfunction "2_2") (pintype "passive"))
    )
    (net (code "579") (name "Net-(IC49C-OUT)") (class "Default")
      (node (ref "C68") (pin "2") (pinfunction "2_2") (pintype "passive"))
      (node (ref "IC49") (pin "14") (pinfunction "OUT_14") (pintype "open_collector"))
      (node (ref "R240") (pin "2") (pinfunction "2_2") (pintype "passive"))
    )
    (net (code "580") (name "Net-(IC49D-OUT)") (class "Default")
      (node (ref "IC49") (pin "13") (pinfunction "OUT_13") (pintype "open_collector"))
      (node (ref "JP27") (pin "1") (pinfunction "1_1") (pintype "passive"))
      (node (ref "Q59") (pin "1") (pinfunction "G_1") (pintype "passive"))
      (node (ref "R333") (pin "2") (pinfunction "2_2") (pintype "passive"))
    )
    (net (code "581") (name "Net-(IC51-Q)") (class "Default")
      (node (ref "IC51") (pin "3") (pinfunction "Q_3") (pintype "output"))
      (node (ref "IC52") (pin "12") (pinfunction "A_12") (pintype "input"))
      (node (ref "IC52") (pin "4") (pinfunction "A_4") (pintype "input"))
    )
    (net (code "582") (name "Net-(IC52A-T2)") (class "Default")
      (node (ref "C73") (pin "2") (pinfunction "2_2") (pintype "passive"))
      (node (ref "IC52") (pin "2") (pinfunction "T2_2") (pintype "input"))
      (node (ref "R355") (pin "1") (pinfunction "1_1") (pintype "passive"))
    )
    (net (code "583") (name "Net-(IC52A-~{Q})") (class "Default")
      (node (ref "IC52") (pin "7") (pinfunction "~{Q}_7") (pintype "output"))
      (node (ref "Q63") (pin "1") (pinfunction "G_1") (pintype "passive"))
    )
    (net (code "584") (name "Net-(IC52B-B)") (class "Default")
      (node (ref "IC52") (pin "11") (pinfunction "B_11") (pintype "input"))
      (node (ref "IC52") (pin "9") (pinfunction "~{Q}_9") (pintype "output"))
      (node (ref "R340") (pin "2") (pinfunction "2_2") (pintype "passive"))
    )
    (net (code "585") (name "Net-(IC52B-T2)") (class "Default")
      (node (ref "C71") (pin "1") (pinfunction "1_1") (pintype "passive"))
      (node (ref "IC52") (pin "14") (pinfunction "T2_14") (pintype "input"))
      (node (ref "R338") (pin "1") (pinfunction "1_1") (pintype "passive"))
    )
    (net (code "586") (name "Net-(IC54A-+IN)") (class "Default")
      (node (ref "C66") (pin "1") (pinfunction "1_1") (pintype "passive"))
      (node (ref "IC54") (pin "3") (pinfunction "+IN_3") (pintype "input"))
      (node (ref "R89") (pin "1") (pinfunction "1_1") (pintype "passive"))
    )
    (net (code "587") (name "Net-(IC54A--IN)") (class "Default")
      (node (ref "IC54") (pin "2") (pinfunction "-IN_2") (pintype "input"))
      (node (ref "R98") (pin "2") (pinfunction "2_2") (pintype "passive"))
    )
    (net (code "588") (name "Net-(IC54A-OUT)") (class "Default")
      (node (ref "IC54") (pin "1") (pinfunction "OUT_1") (pintype "output"))
      (node (ref "R341") (pin "2") (pinfunction "2_2") (pintype "passive"))
    )
    (net (code "589") (name "Net-(IC54B-+IN)") (class "Default")
      (node (ref "IC54") (pin "5") (pinfunction "+IN_5") (pintype "input"))
      (node (ref "Q61") (pin "3") (pinfunction "D_3") (pintype "passive"))
      (node (ref "R342") (pin "2") (pinfunction "2_2") (pintype "passive"))
      (node (ref "R343") (pin "2") (pinfunction "2_2") (pintype "passive"))
    )
    (net (code "590") (name "Net-(IC54B--IN)") (class "Default")
      (node (ref "IC54") (pin "6") (pinfunction "-IN_6") (pintype "input"))
      (node (ref "R344") (pin "1") (pinfunction "1_1") (pintype "passive"))
      (node (ref "R345") (pin "2") (pinfunction "2_2") (pintype "passive"))
    )
    (net (code "591") (name "Net-(IC54B-OUT)") (class "Default")
      (node (ref "IC54") (pin "7") (pinfunction "OUT_7") (pintype "output"))
      (node (ref "R252") (pin "2") (pinfunction "2_2") (pintype "passive"))
      (node (ref "R331") (pin "1") (pinfunction "1_1") (pintype "passive"))
      (node (ref "R343") (pin "1") (pinfunction "1_1") (pintype "passive"))
    )
    (net (code "592") (name "Net-(IC55A-A)") (class "Default")
      (node (ref "IC55") (pin "10") (pinfunction "A_10") (pintype "input"))
      (node (ref "R363") (pin "1") (pinfunction "1_1") (pintype "passive"))
      (node (ref "R400") (pin "1") (pinfunction "1_1") (pintype "passive"))
      (node (ref "R400") (pin "2") (pinfunction "2_2") (pintype "passive"))
      (node (ref "X19") (pin "4") (pinfunction "4_4") (pintype "passive"))
      (node (ref "X20") (pin "2") (pinfunction "S_2") (pintype "passive"))
    )
    (net (code "593") (name "Net-(IC55A-B)") (class "Default")
      (node (ref "IC55") (pin "13") (pinfunction "B_13") (pintype "input"))
      (node (ref "R362") (pin "1") (pinfunction "1_1") (pintype "passive"))
      (node (ref "R399") (pin "1") (pinfunction "1_1") (pintype "passive"))
      (node (ref "R399") (pin "2") (pinfunction "2_2") (pintype "passive"))
      (node (ref "X19") (pin "3") (pinfunction "3_3") (pintype "passive"))
      (node (ref "X20") (pin "3") (pinfunction "S_3") (pintype "passive"))
    )
    (net (code "594") (name "Net-(IC55A-C)") (class "Default")
      (node (ref "IC55") (pin "12") (pinfunction "C_12") (pintype "input"))
      (node (ref "R361") (pin "1") (pinfunction "1_1") (pintype "passive"))
      (node (ref "R398") (pin "1") (pinfunction "1_1") (pintype "passive"))
      (node (ref "R398") (pin "2") (pinfunction "2_2") (pintype "passive"))
      (node (ref "X19") (pin "2") (pinfunction "2_2") (pintype "passive"))
      (node (ref "X20") (pin "4") (pinfunction "S_4") (pintype "passive"))
    )
    (net (code "595") (name "Net-(IC55A-Q0)") (class "Default")
      (node (ref "IC55") (pin "3") (pinfunction "Q0_3") (pintype "output"))
      (node (ref "IC57") (pin "1") (pinfunction "I1_1") (pintype "input"))
      (node (ref "IC57") (pin "2") (pinfunction "I2_2") (pintype "input"))
      (node (ref "Q70") (pin "1") (pinfunction "G_1") (pintype "passive"))
      (node (ref "Q71") (pin "1") (pinfunction "G_1") (pintype "passive"))
    )
    (net (code "596") (name "Net-(IC55A-Q1)") (class "Default")
      (node (ref "IC55") (pin "14") (pinfunction "Q1_14") (pintype "output"))
      (node (ref "IC57") (pin "6") (pinfunction "I6_6") (pintype "input"))
    )
    (net (code "597") (name "Net-(IC55A-Q2)") (class "Default")
      (node (ref "IC55") (pin "2") (pinfunction "Q2_2") (pintype "output"))
      (node (ref "IC57") (pin "7") (pinfunction "I7_7") (pintype "input"))
    )
    (net (code "598") (name "Net-(IC55A-Q3)") (class "Default")
      (node (ref "IC55") (pin "15") (pinfunction "Q3_15") (pintype "output"))
      (node (ref "IC57") (pin "5") (pinfunction "I5_5") (pintype "input"))
    )
    (net (code "599") (name "Net-(IC55A-Q4)") (class "Default")
      (node (ref "IC55") (pin "1") (pinfunction "Q4_1") (pintype "output"))
      (node (ref "IC57") (pin "4") (pinfunction "I4_4") (pintype "input"))
    )
    (net (code "600") (name "Net-(IC55A-Q5)") (class "Default")
      (node (ref "IC55") (pin "6") (pinfunction "Q5_6") (pintype "output"))
      (node (ref "IC57") (pin "3") (pinfunction "I3_3") (pintype "input"))
    )
    (net (code "601") (name "Net-(IC56-ADJ)") (class "Default")
      (node (ref "IC56") (pin "1") (pinfunction "ADJ_1") (pintype "input"))
      (node (ref "R359") (pin "1") (pinfunction "1_1") (pintype "passive"))
      (node (ref "R366") (pin "2") (pinfunction "2_2") (pintype "passive"))
      (node (ref "X19") (pin "7") (pinfunction "7_7") (pintype "passive"))
    )
    (net (code "602") (name "Net-(IC56-VI)") (class "Default")
      (node (ref "IC56") (pin "3") (pinfunction "VI_3") (pintype "input"))
      (node (ref "Q67") (pin "2") (pinfunction "C_2") (pintype "passive"))
    )
    (net (code "603") (name "Net-(IC56-VO)") (class "Default")
      (node (ref "IC56") (pin "2") (pinfunction "VO_2") (pintype "passive"))
      (node (ref "R359") (pin "2") (pinfunction "2_2") (pintype "passive"))
    )
    (net (code "604") (name "Net-(IC57-O1)") (class "Default")
      (node (ref "IC57") (pin "16") (pinfunction "O1_16") (pintype "open_collector"))
      (node (ref "Q70") (pin "3") (pinfunction "D_3") (pintype "passive"))
      (node (ref "R404") (pin "1") (pinfunction "1_1") (pintype "passive"))
    )
    (net (code "605") (name "Net-(IC57-O2)") (class "Default")
      (node (ref "IC57") (pin "15") (pinfunction "O2_15") (pintype "open_collector"))
      (node (ref "R378") (pin "1") (pinfunction "1_1") (pintype "passive"))
    )
    (net (code "606") (name "Net-(IC58A-+IN)") (class "Default")
      (node (ref "IC58") (pin "11") (pinfunction "+IN_11") (pintype "input"))
      (node (ref "IC58") (pin "5") (pinfunction "+IN_5") (pintype "input"))
      (node (ref "R370") (pin "1") (pinfunction "1_1") (pintype "passive"))
      (node (ref "R371") (pin "2") (pinfunction "2_2") (pintype "passive"))
      (node (ref "R372") (pin "2") (pinfunction "2_2") (pintype "passive"))
    )
    (net (code "607") (name "Net-(IC58A--IN)") (class "Default")
      (node (ref "C76") (pin "1") (pinfunction "1_1") (pintype "passive"))
      (node (ref "IC58") (pin "10") (pinfunction "-IN_10") (pintype "input"))
      (node (ref "IC58") (pin "4") (pinfunction "-IN_4") (pintype "input"))
      (node (ref "R369") (pin "1") (pinfunction "1_1") (pintype "passive"))
    )
    (net (code "608") (name "Net-(IC58A-OUT)") (class "Default")
      (node (ref "IC58") (pin "2") (pinfunction "OUT_2") (pintype "open_collector"))
      (node (ref "R372") (pin "1") (pinfunction "1_1") (pintype "passive"))
    )
    (net (code "609") (name "Net-(IC58B-+IN)") (class "Default")
      (node (ref "IC58") (pin "7") (pinfunction "+IN_7") (pintype "input"))
      (node (ref "R367") (pin "1") (pinfunction "1_1") (pintype "passive"))
      (node (ref "R381") (pin "1") (pinfunction "1_1") (pintype "passive"))
    )
    (net (code "610") (name "Net-(IC58B--IN)") (class "Default")
      (node (ref "IC58") (pin "6") (pinfunction "-IN_6") (pintype "input"))
      (node (ref "IC58") (pin "8") (pinfunction "-IN_8") (pintype "input"))
      (node (ref "R366") (pin "1") (pinfunction "1_1") (pintype "passive"))
    )
    (net (code "611") (name "Net-(IC58B-OUT)") (class "Default")
      (node (ref "IC58") (pin "1") (pinfunction "OUT_1") (pintype "open_collector"))
      (node (ref "R368") (pin "2") (pinfunction "2_2") (pintype "passive"))
      (node (ref "R373") (pin "2") (pinfunction "2_2") (pintype "passive"))
    )
    (net (code "612") (name "Net-(IC58C-+IN)") (class "Default")
      (node (ref "C79") (pin "1") (pinfunction "1_1") (pintype "passive"))
      (node (ref "IC58") (pin "9") (pinfunction "+IN_9") (pintype "input"))
      (node (ref "R375") (pin "2") (pinfunction "2_2") (pintype "passive"))
      (node (ref "R381") (pin "2") (pinfunction "2_2") (pintype "passive"))
    )
    (net (code "613") (name "Net-(IC58C-OUT)") (class "Default")
      (node (ref "C80") (pin "2") (pinfunction "2_2") (pintype "passive"))
      (node (ref "IC58") (pin "14") (pinfunction "OUT_14") (pintype "open_collector"))
      (node (ref "R374") (pin "2") (pinfunction "2_2") (pintype "passive"))
    )
    (net (code "614") (name "Net-(IC58D-OUT)") (class "Default")
      (node (ref "IC58") (pin "13") (pinfunction "OUT_13") (pintype "open_collector"))
      (node (ref "JP32") (pin "1") (pinfunction "1_1") (pintype "passive"))
      (node (ref "Q69") (pin "1") (pinfunction "G_1") (pintype "passive"))
      (node (ref "R384") (pin "2") (pinfunction "2_2") (pintype "passive"))
    )
    (net (code "615") (name "Net-(IC60-Q)") (class "Default")
      (node (ref "IC60") (pin "3") (pinfunction "Q_3") (pintype "output"))
      (node (ref "IC61") (pin "12") (pinfunction "A_12") (pintype "input"))
      (node (ref "IC61") (pin "4") (pinfunction "A_4") (pintype "input"))
    )
    (net (code "616") (name "Net-(IC61A-T2)") (class "Default")
      (node (ref "C85") (pin "2") (pinfunction "2_2") (pintype "passive"))
      (node (ref "IC61") (pin "2") (pinfunction "T2_2") (pintype "input"))
      (node (ref "R406") (pin "1") (pinfunction "1_1") (pintype "passive"))
    )
    (net (code "617") (name "Net-(IC61A-~{Q})") (class "Default")
      (node (ref "IC61") (pin "7") (pinfunction "~{Q}_7") (pintype "output"))
      (node (ref "Q73") (pin "1") (pinfunction "G_1") (pintype "passive"))
    )
    (net (code "618") (name "Net-(IC61B-B)") (class "Default")
      (node (ref "IC61") (pin "11") (pinfunction "B_11") (pintype "input"))
      (node (ref "IC61") (pin "9") (pinfunction "~{Q}_9") (pintype "output"))
      (node (ref "R391") (pin "2") (pinfunction "2_2") (pintype "passive"))
    )
    (net (code "619") (name "Net-(IC61B-T2)") (class "Default")
      (node (ref "C83") (pin "1") (pinfunction "1_1") (pintype "passive"))
      (node (ref "IC61") (pin "14") (pinfunction "T2_14") (pintype "input"))
      (node (ref "R389") (pin "1") (pinfunction "1_1") (pintype "passive"))
    )
    (net (code "620") (name "Net-(IC63A-+IN)") (class "Default")
      (node (ref "C78") (pin "1") (pinfunction "1_1") (pintype "passive"))
      (node (ref "IC63") (pin "3") (pinfunction "+IN_3") (pintype "input"))
      (node (ref "R364") (pin "1") (pinfunction "1_1") (pintype "passive"))
    )
    (net (code "621") (name "Net-(IC63A--IN)") (class "Default")
      (node (ref "IC63") (pin "2") (pinfunction "-IN_2") (pintype "input"))
      (node (ref "R365") (pin "2") (pinfunction "2_2") (pintype "passive"))
    )
    (net (code "622") (name "Net-(IC63A-OUT)") (class "Default")
      (node (ref "IC63") (pin "1") (pinfunction "OUT_1") (pintype "output"))
      (node (ref "R392") (pin "2") (pinfunction "2_2") (pintype "passive"))
    )
    (net (code "623") (name "Net-(IC63B-+IN)") (class "Default")
      (node (ref "IC63") (pin "5") (pinfunction "+IN_5") (pintype "input"))
      (node (ref "Q71") (pin "3") (pinfunction "D_3") (pintype "passive"))
      (node (ref "R393") (pin "2") (pinfunction "2_2") (pintype "passive"))
      (node (ref "R394") (pin "2") (pinfunction "2_2") (pintype "passive"))
    )
    (net (code "624") (name "Net-(IC63B--IN)") (class "Default")
      (node (ref "IC63") (pin "6") (pinfunction "-IN_6") (pintype "input"))
      (node (ref "R395") (pin "1") (pinfunction "1_1") (pintype "passive"))
      (node (ref "R396") (pin "2") (pinfunction "2_2") (pintype "passive"))
    )
    (net (code "625") (name "Net-(IC63B-OUT)") (class "Default")
      (node (ref "IC63") (pin "7") (pinfunction "OUT_7") (pintype "output"))
      (node (ref "R377") (pin "2") (pinfunction "2_2") (pintype "passive"))
      (node (ref "R382") (pin "1") (pinfunction "1_1") (pintype "passive"))
      (node (ref "R394") (pin "1") (pinfunction "1_1") (pintype "passive"))
    )
    (net (code "626") (name "Net-(IC64A-A)") (class "Default")
      (node (ref "IC64") (pin "10") (pinfunction "A_10") (pintype "input"))
      (node (ref "R414") (pin "1") (pinfunction "1_1") (pintype "passive"))
      (node (ref "R451") (pin "1") (pinfunction "1_1") (pintype "passive"))
      (node (ref "R451") (pin "2") (pinfunction "2_2") (pintype "passive"))
      (node (ref "X22") (pin "4") (pinfunction "4_4") (pintype "passive"))
      (node (ref "X23") (pin "2") (pinfunction "S_2") (pintype "passive"))
    )
    (net (code "627") (name "Net-(IC64A-B)") (class "Default")
      (node (ref "IC64") (pin "13") (pinfunction "B_13") (pintype "input"))
      (node (ref "R413") (pin "1") (pinfunction "1_1") (pintype "passive"))
      (node (ref "R450") (pin "1") (pinfunction "1_1") (pintype "passive"))
      (node (ref "R450") (pin "2") (pinfunction "2_2") (pintype "passive"))
      (node (ref "X22") (pin "3") (pinfunction "3_3") (pintype "passive"))
      (node (ref "X23") (pin "3") (pinfunction "S_3") (pintype "passive"))
    )
    (net (code "628") (name "Net-(IC64A-C)") (class "Default")
      (node (ref "IC64") (pin "12") (pinfunction "C_12") (pintype "input"))
      (node (ref "R412") (pin "1") (pinfunction "1_1") (pintype "passive"))
      (node (ref "R449") (pin "1") (pinfunction "1_1") (pintype "passive"))
      (node (ref "R449") (pin "2") (pinfunction "2_2") (pintype "passive"))
      (node (ref "X22") (pin "2") (pinfunction "2_2") (pintype "passive"))
      (node (ref "X23") (pin "4") (pinfunction "S_4") (pintype "passive"))
    )
    (net (code "629") (name "Net-(IC64A-Q0)") (class "Default")
      (node (ref "IC64") (pin "3") (pinfunction "Q0_3") (pintype "output"))
      (node (ref "IC66") (pin "1") (pinfunction "I1_1") (pintype "input"))
      (node (ref "IC66") (pin "2") (pinfunction "I2_2") (pintype "input"))
      (node (ref "Q80") (pin "1") (pinfunction "G_1") (pintype "passive"))
      (node (ref "Q81") (pin "1") (pinfunction "G_1") (pintype "passive"))
    )
    (net (code "630") (name "Net-(IC64A-Q1)") (class "Default")
      (node (ref "IC64") (pin "14") (pinfunction "Q1_14") (pintype "output"))
      (node (ref "IC66") (pin "6") (pinfunction "I6_6") (pintype "input"))
    )
    (net (code "631") (name "Net-(IC64A-Q2)") (class "Default")
      (node (ref "IC64") (pin "2") (pinfunction "Q2_2") (pintype "output"))
      (node (ref "IC66") (pin "7") (pinfunction "I7_7") (pintype "input"))
    )
    (net (code "632") (name "Net-(IC64A-Q3)") (class "Default")
      (node (ref "IC64") (pin "15") (pinfunction "Q3_15") (pintype "output"))
      (node (ref "IC66") (pin "5") (pinfunction "I5_5") (pintype "input"))
    )
    (net (code "633") (name "Net-(IC64A-Q4)") (class "Default")
      (node (ref "IC64") (pin "1") (pinfunction "Q4_1") (pintype "output"))
      (node (ref "IC66") (pin "4") (pinfunction "I4_4") (pintype "input"))
    )
    (net (code "634") (name "Net-(IC64A-Q5)") (class "Default")
      (node (ref "IC64") (pin "6") (pinfunction "Q5_6") (pintype "output"))
      (node (ref "IC66") (pin "3") (pinfunction "I3_3") (pintype "input"))
    )
    (net (code "635") (name "Net-(IC65-ADJ)") (class "Default")
      (node (ref "IC65") (pin "1") (pinfunction "ADJ_1") (pintype "input"))
      (node (ref "R410") (pin "1") (pinfunction "1_1") (pintype "passive"))
      (node (ref "R417") (pin "2") (pinfunction "2_2") (pintype "passive"))
      (node (ref "X22") (pin "7") (pinfunction "7_7") (pintype "passive"))
    )
    (net (code "636") (name "Net-(IC65-VI)") (class "Default")
      (node (ref "IC65") (pin "3") (pinfunction "VI_3") (pintype "input"))
      (node (ref "Q77") (pin "2") (pinfunction "C_2") (pintype "passive"))
    )
    (net (code "637") (name "Net-(IC65-VO)") (class "Default")
      (node (ref "IC65") (pin "2") (pinfunction "VO_2") (pintype "passive"))
      (node (ref "R410") (pin "2") (pinfunction "2_2") (pintype "passive"))
    )
    (net (code "638") (name "Net-(IC66-O1)") (class "Default")
      (node (ref "IC66") (pin "16") (pinfunction "O1_16") (pintype "open_collector"))
      (node (ref "Q80") (pin "3") (pinfunction "D_3") (pintype "passive"))
      (node (ref "R455") (pin "1") (pinfunction "1_1") (pintype "passive"))
    )
    (net (code "639") (name "Net-(IC66-O2)") (class "Default")
      (node (ref "IC66") (pin "15") (pinfunction "O2_15") (pintype "open_collector"))
      (node (ref "R429") (pin "1") (pinfunction "1_1") (pintype "passive"))
    )
    (net (code "640") (name "Net-(IC67A-+IN)") (class "Default")
      (node (ref "IC67") (pin "11") (pinfunction "+IN_11") (pintype "input"))
      (node (ref "IC67") (pin "5") (pinfunction "+IN_5") (pintype "input"))
      (node (ref "R421") (pin "1") (pinfunction "1_1") (pintype "passive"))
      (node (ref "R422") (pin "2") (pinfunction "2_2") (pintype "passive"))
      (node (ref "R423") (pin "2") (pinfunction "2_2") (pintype "passive"))
    )
    (net (code "641") (name "Net-(IC67A--IN)") (class "Default")
      (node (ref "C88") (pin "1") (pinfunction "1_1") (pintype "passive"))
      (node (ref "IC67") (pin "10") (pinfunction "-IN_10") (pintype "input"))
      (node (ref "IC67") (pin "4") (pinfunction "-IN_4") (pintype "input"))
      (node (ref "R420") (pin "1") (pinfunction "1_1") (pintype "passive"))
    )
    (net (code "642") (name "Net-(IC67A-OUT)") (class "Default")
      (node (ref "IC67") (pin "2") (pinfunction "OUT_2") (pintype "open_collector"))
      (node (ref "R423") (pin "1") (pinfunction "1_1") (pintype "passive"))
    )
    (net (code "643") (name "Net-(IC67B-+IN)") (class "Default")
      (node (ref "IC67") (pin "7") (pinfunction "+IN_7") (pintype "input"))
      (node (ref "R418") (pin "1") (pinfunction "1_1") (pintype "passive"))
      (node (ref "R432") (pin "1") (pinfunction "1_1") (pintype "passive"))
    )
    (net (code "644") (name "Net-(IC67B--IN)") (class "Default")
      (node (ref "IC67") (pin "6") (pinfunction "-IN_6") (pintype "input"))
      (node (ref "IC67") (pin "8") (pinfunction "-IN_8") (pintype "input"))
      (node (ref "R417") (pin "1") (pinfunction "1_1") (pintype "passive"))
    )
    (net (code "645") (name "Net-(IC67B-OUT)") (class "Default")
      (node (ref "IC67") (pin "1") (pinfunction "OUT_1") (pintype "open_collector"))
      (node (ref "R419") (pin "2") (pinfunction "2_2") (pintype "passive"))
      (node (ref "R424") (pin "2") (pinfunction "2_2") (pintype "passive"))
    )
    (net (code "646") (name "Net-(IC67C-+IN)") (class "Default")
      (node (ref "C91") (pin "1") (pinfunction "1_1") (pintype "passive"))
      (node (ref "IC67") (pin "9") (pinfunction "+IN_9") (pintype "input"))
      (node (ref "R426") (pin "2") (pinfunction "2_2") (pintype "passive"))
      (node (ref "R432") (pin "2") (pinfunction "2_2") (pintype "passive"))
    )
    (net (code "647") (name "Net-(IC67C-OUT)") (class "Default")
      (node (ref "C92") (pin "2") (pinfunction "2_2") (pintype "passive"))
      (node (ref "IC67") (pin "14") (pinfunction "OUT_14") (pintype "open_collector"))
      (node (ref "R425") (pin "2") (pinfunction "2_2") (pintype "passive"))
    )
    (net (code "648") (name "Net-(IC67D-OUT)") (class "Default")
      (node (ref "IC67") (pin "13") (pinfunction "OUT_13") (pintype "open_collector"))
      (node (ref "JP37") (pin "1") (pinfunction "1_1") (pintype "passive"))
      (node (ref "Q79") (pin "1") (pinfunction "G_1") (pintype "passive"))
      (node (ref "R435") (pin "2") (pinfunction "2_2") (pintype "passive"))
    )
    (net (code "649") (name "Net-(IC69-Q)") (class "Default")
      (node (ref "IC69") (pin "3") (pinfunction "Q_3") (pintype "output"))
      (node (ref "IC70") (pin "12") (pinfunction "A_12") (pintype "input"))
      (node (ref "IC70") (pin "4") (pinfunction "A_4") (pintype "input"))
    )
    (net (code "650") (name "Net-(IC70A-T2)") (class "Default")
      (node (ref "C97") (pin "2") (pinfunction "2_2") (pintype "passive"))
      (node (ref "IC70") (pin "2") (pinfunction "T2_2") (pintype "input"))
      (node (ref "R457") (pin "1") (pinfunction "1_1") (pintype "passive"))
    )
    (net (code "651") (name "Net-(IC70A-~{Q})") (class "Default")
      (node (ref "IC70") (pin "7") (pinfunction "~{Q}_7") (pintype "output"))
      (node (ref "Q83") (pin "1") (pinfunction "G_1") (pintype "passive"))
    )
    (net (code "652") (name "Net-(IC70B-B)") (class "Default")
      (node (ref "IC70") (pin "11") (pinfunction "B_11") (pintype "input"))
      (node (ref "IC70") (pin "9") (pinfunction "~{Q}_9") (pintype "output"))
      (node (ref "R442") (pin "2") (pinfunction "2_2") (pintype "passive"))
    )
    (net (code "653") (name "Net-(IC70B-T2)") (class "Default")
      (node (ref "C95") (pin "1") (pinfunction "1_1") (pintype "passive"))
      (node (ref "IC70") (pin "14") (pinfunction "T2_14") (pintype "input"))
      (node (ref "R440") (pin "1") (pinfunction "1_1") (pintype "passive"))
    )
    (net (code "654") (name "Net-(IC72A-+IN)") (class "Default")
      (node (ref "C90") (pin "1") (pinfunction "1_1") (pintype "passive"))
      (node (ref "IC72") (pin "3") (pinfunction "+IN_3") (pintype "input"))
      (node (ref "R415") (pin "1") (pinfunction "1_1") (pintype "passive"))
    )
    (net (code "655") (name "Net-(IC72A--IN)") (class "Default")
      (node (ref "IC72") (pin "2") (pinfunction "-IN_2") (pintype "input"))
      (node (ref "R416") (pin "2") (pinfunction "2_2") (pintype "passive"))
    )
    (net (code "656") (name "Net-(IC72A-OUT)") (class "Default")
      (node (ref "IC72") (pin "1") (pinfunction "OUT_1") (pintype "output"))
      (node (ref "R443") (pin "2") (pinfunction "2_2") (pintype "passive"))
    )
    (net (code "657") (name "Net-(IC72B-+IN)") (class "Default")
      (node (ref "IC72") (pin "5") (pinfunction "+IN_5") (pintype "input"))
      (node (ref "Q81") (pin "3") (pinfunction "D_3") (pintype "passive"))
      (node (ref "R444") (pin "2") (pinfunction "2_2") (pintype "passive"))
      (node (ref "R445") (pin "2") (pinfunction "2_2") (pintype "passive"))
    )
    (net (code "658") (name "Net-(IC72B--IN)") (class "Default")
      (node (ref "IC72") (pin "6") (pinfunction "-IN_6") (pintype "input"))
      (node (ref "R446") (pin "1") (pinfunction "1_1") (pintype "passive"))
      (node (ref "R447") (pin "2") (pinfunction "2_2") (pintype "passive"))
    )
    (net (code "659") (name "Net-(IC72B-OUT)") (class "Default")
      (node (ref "IC72") (pin "7") (pinfunction "OUT_7") (pintype "output"))
      (node (ref "R428") (pin "2") (pinfunction "2_2") (pintype "passive"))
      (node (ref "R433") (pin "1") (pinfunction "1_1") (pintype "passive"))
      (node (ref "R445") (pin "1") (pinfunction "1_1") (pintype "passive"))
    )
    (net (code "660") (name "Net-(IC73A-A)") (class "Default")
      (node (ref "IC73") (pin "10") (pinfunction "A_10") (pintype "input"))
      (node (ref "R465") (pin "1") (pinfunction "1_1") (pintype "passive"))
      (node (ref "R502") (pin "1") (pinfunction "1_1") (pintype "passive"))
      (node (ref "R502") (pin "2") (pinfunction "2_2") (pintype "passive"))
      (node (ref "X25") (pin "4") (pinfunction "4_4") (pintype "passive"))
      (node (ref "X26") (pin "2") (pinfunction "S_2") (pintype "passive"))
    )
    (net (code "661") (name "Net-(IC73A-B)") (class "Default")
      (node (ref "IC73") (pin "13") (pinfunction "B_13") (pintype "input"))
      (node (ref "R464") (pin "1") (pinfunction "1_1") (pintype "passive"))
      (node (ref "R501") (pin "1") (pinfunction "1_1") (pintype "passive"))
      (node (ref "R501") (pin "2") (pinfunction "2_2") (pintype "passive"))
      (node (ref "X25") (pin "3") (pinfunction "3_3") (pintype "passive"))
      (node (ref "X26") (pin "3") (pinfunction "S_3") (pintype "passive"))
    )
    (net (code "662") (name "Net-(IC73A-C)") (class "Default")
      (node (ref "IC73") (pin "12") (pinfunction "C_12") (pintype "input"))
      (node (ref "R463") (pin "1") (pinfunction "1_1") (pintype "passive"))
      (node (ref "R500") (pin "1") (pinfunction "1_1") (pintype "passive"))
      (node (ref "R500") (pin "2") (pinfunction "2_2") (pintype "passive"))
      (node (ref "X25") (pin "2") (pinfunction "2_2") (pintype "passive"))
      (node (ref "X26") (pin "4") (pinfunction "S_4") (pintype "passive"))
    )
    (net (code "663") (name "Net-(IC73A-Q0)") (class "Default")
      (node (ref "IC73") (pin "3") (pinfunction "Q0_3") (pintype "output"))
      (node (ref "IC75") (pin "1") (pinfunction "I1_1") (pintype "input"))
      (node (ref "IC75") (pin "2") (pinfunction "I2_2") (pintype "input"))
      (node (ref "Q90") (pin "1") (pinfunction "G_1") (pintype "passive"))
      (node (ref "Q91") (pin "1") (pinfunction "G_1") (pintype "passive"))
    )
    (net (code "664") (name "Net-(IC73A-Q1)") (class "Default")
      (node (ref "IC73") (pin "14") (pinfunction "Q1_14") (pintype "output"))
      (node (ref "IC75") (pin "6") (pinfunction "I6_6") (pintype "input"))
    )
    (net (code "665") (name "Net-(IC73A-Q2)") (class "Default")
      (node (ref "IC73") (pin "2") (pinfunction "Q2_2") (pintype "output"))
      (node (ref "IC75") (pin "7") (pinfunction "I7_7") (pintype "input"))
    )
    (net (code "666") (name "Net-(IC73A-Q3)") (class "Default")
      (node (ref "IC73") (pin "15") (pinfunction "Q3_15") (pintype "output"))
      (node (ref "IC75") (pin "5") (pinfunction "I5_5") (pintype "input"))
    )
    (net (code "667") (name "Net-(IC73A-Q4)") (class "Default")
      (node (ref "IC73") (pin "1") (pinfunction "Q4_1") (pintype "output"))
      (node (ref "IC75") (pin "4") (pinfunction "I4_4") (pintype "input"))
    )
    (net (code "668") (name "Net-(IC73A-Q5)") (class "Default")
      (node (ref "IC73") (pin "6") (pinfunction "Q5_6") (pintype "output"))
      (node (ref "IC75") (pin "3") (pinfunction "I3_3") (pintype "input"))
    )
    (net (code "669") (name "Net-(IC74-ADJ)") (class "Default")
      (node (ref "IC74") (pin "1") (pinfunction "ADJ_1") (pintype "input"))
      (node (ref "R461") (pin "1") (pinfunction "1_1") (pintype "passive"))
      (node (ref "R468") (pin "2") (pinfunction "2_2") (pintype "passive"))
      (node (ref "X25") (pin "7") (pinfunction "7_7") (pintype "passive"))
    )
    (net (code "670") (name "Net-(IC74-VI)") (class "Default")
      (node (ref "IC74") (pin "3") (pinfunction "VI_3") (pintype "input"))
      (node (ref "Q87") (pin "2") (pinfunction "C_2") (pintype "passive"))
    )
    (net (code "671") (name "Net-(IC74-VO)") (class "Default")
      (node (ref "IC74") (pin "2") (pinfunction "VO_2") (pintype "passive"))
      (node (ref "R461") (pin "2") (pinfunction "2_2") (pintype "passive"))
    )
    (net (code "672") (name "Net-(IC75-O1)") (class "Default")
      (node (ref "IC75") (pin "16") (pinfunction "O1_16") (pintype "open_collector"))
      (node (ref "Q90") (pin "3") (pinfunction "D_3") (pintype "passive"))
      (node (ref "R506") (pin "1") (pinfunction "1_1") (pintype "passive"))
    )
    (net (code "673") (name "Net-(IC75-O2)") (class "Default")
      (node (ref "IC75") (pin "15") (pinfunction "O2_15") (pintype "open_collector"))
      (node (ref "R480") (pin "1") (pinfunction "1_1") (pintype "passive"))
    )
    (net (code "674") (name "Net-(IC76A-+IN)") (class "Default")
      (node (ref "IC76") (pin "11") (pinfunction "+IN_11") (pintype "input"))
      (node (ref "IC76") (pin "5") (pinfunction "+IN_5") (pintype "input"))
      (node (ref "R472") (pin "1") (pinfunction "1_1") (pintype "passive"))
      (node (ref "R473") (pin "2") (pinfunction "2_2") (pintype "passive"))
      (node (ref "R474") (pin "2") (pinfunction "2_2") (pintype "passive"))
    )
    (net (code "675") (name "Net-(IC76A--IN)") (class "Default")
      (node (ref "C100") (pin "1") (pinfunction "1_1") (pintype "passive"))
      (node (ref "IC76") (pin "10") (pinfunction "-IN_10") (pintype "input"))
      (node (ref "IC76") (pin "4") (pinfunction "-IN_4") (pintype "input"))
      (node (ref "R471") (pin "1") (pinfunction "1_1") (pintype "passive"))
    )
    (net (code "676") (name "Net-(IC76A-OUT)") (class "Default")
      (node (ref "IC76") (pin "2") (pinfunction "OUT_2") (pintype "open_collector"))
      (node (ref "R474") (pin "1") (pinfunction "1_1") (pintype "passive"))
    )
    (net (code "677") (name "Net-(IC76B-+IN)") (class "Default")
      (node (ref "IC76") (pin "7") (pinfunction "+IN_7") (pintype "input"))
      (node (ref "R469") (pin "1") (pinfunction "1_1") (pintype "passive"))
      (node (ref "R483") (pin "1") (pinfunction "1_1") (pintype "passive"))
    )
    (net (code "678") (name "Net-(IC76B--IN)") (class "Default")
      (node (ref "IC76") (pin "6") (pinfunction "-IN_6") (pintype "input"))
      (node (ref "IC76") (pin "8") (pinfunction "-IN_8") (pintype "input"))
      (node (ref "R468") (pin "1") (pinfunction "1_1") (pintype "passive"))
    )
    (net (code "679") (name "Net-(IC76B-OUT)") (class "Default")
      (node (ref "IC76") (pin "1") (pinfunction "OUT_1") (pintype "open_collector"))
      (node (ref "R470") (pin "2") (pinfunction "2_2") (pintype "passive"))
      (node (ref "R475") (pin "2") (pinfunction "2_2") (pintype "passive"))
    )
    (net (code "680") (name "Net-(IC76C-+IN)") (class "Default")
      (node (ref "C113") (pin "1") (pinfunction "1_1") (pintype "passive"))
      (node (ref "IC76") (pin "9") (pinfunction "+IN_9") (pintype "input"))
      (node (ref "R477") (pin "2") (pinfunction "2_2") (pintype "passive"))
      (node (ref "R483") (pin "2") (pinfunction "2_2") (pintype "passive"))
    )
    (net (code "681") (name "Net-(IC76C-OUT)") (class "Default")
      (node (ref "C114") (pin "2") (pinfunction "2_2") (pintype "passive"))
      (node (ref "IC76") (pin "14") (pinfunction "OUT_14") (pintype "open_collector"))
      (node (ref "R476") (pin "2") (pinfunction "2_2") (pintype "passive"))
    )
    (net (code "682") (name "Net-(IC76D-OUT)") (class "Default")
      (node (ref "IC76") (pin "13") (pinfunction "OUT_13") (pintype "open_collector"))
      (node (ref "JP42") (pin "1") (pinfunction "1_1") (pintype "passive"))
      (node (ref "Q89") (pin "1") (pinfunction "G_1") (pintype "passive"))
      (node (ref "R486") (pin "2") (pinfunction "2_2") (pintype "passive"))
    )
    (net (code "683") (name "Net-(IC78-Q)") (class "Default")
      (node (ref "IC78") (pin "3") (pinfunction "Q_3") (pintype "output"))
      (node (ref "IC79") (pin "12") (pinfunction "A_12") (pintype "input"))
      (node (ref "IC79") (pin "4") (pinfunction "A_4") (pintype "input"))
    )
    (net (code "684") (name "Net-(IC79A-T2)") (class "Default")
      (node (ref "C119") (pin "2") (pinfunction "2_2") (pintype "passive"))
      (node (ref "IC79") (pin "2") (pinfunction "T2_2") (pintype "input"))
      (node (ref "R508") (pin "1") (pinfunction "1_1") (pintype "passive"))
    )
    (net (code "685") (name "Net-(IC79A-~{Q})") (class "Default")
      (node (ref "IC79") (pin "7") (pinfunction "~{Q}_7") (pintype "output"))
      (node (ref "Q93") (pin "1") (pinfunction "G_1") (pintype "passive"))
    )
    (net (code "686") (name "Net-(IC79B-B)") (class "Default")
      (node (ref "IC79") (pin "11") (pinfunction "B_11") (pintype "input"))
      (node (ref "IC79") (pin "9") (pinfunction "~{Q}_9") (pintype "output"))
      (node (ref "R493") (pin "2") (pinfunction "2_2") (pintype "passive"))
    )
    (net (code "687") (name "Net-(IC79B-T2)") (class "Default")
      (node (ref "C117") (pin "1") (pinfunction "1_1") (pintype "passive"))
      (node (ref "IC79") (pin "14") (pinfunction "T2_14") (pintype "input"))
      (node (ref "R491") (pin "1") (pinfunction "1_1") (pintype "passive"))
    )
    (net (code "688") (name "Net-(IC81A-+IN)") (class "Default")
      (node (ref "C112") (pin "1") (pinfunction "1_1") (pintype "passive"))
      (node (ref "IC81") (pin "3") (pinfunction "+IN_3") (pintype "input"))
      (node (ref "R466") (pin "1") (pinfunction "1_1") (pintype "passive"))
    )
    (net (code "689") (name "Net-(IC81A--IN)") (class "Default")
      (node (ref "IC81") (pin "2") (pinfunction "-IN_2") (pintype "input"))
      (node (ref "R467") (pin "2") (pinfunction "2_2") (pintype "passive"))
    )
    (net (code "690") (name "Net-(IC81A-OUT)") (class "Default")
      (node (ref "IC81") (pin "1") (pinfunction "OUT_1") (pintype "output"))
      (node (ref "R494") (pin "2") (pinfunction "2_2") (pintype "passive"))
    )
    (net (code "691") (name "Net-(IC81B-+IN)") (class "Default")
      (node (ref "IC81") (pin "5") (pinfunction "+IN_5") (pintype "input"))
      (node (ref "Q91") (pin "3") (pinfunction "D_3") (pintype "passive"))
      (node (ref "R495") (pin "2") (pinfunction "2_2") (pintype "passive"))
      (node (ref "R496") (pin "2") (pinfunction "2_2") (pintype "passive"))
    )
    (net (code "692") (name "Net-(IC81B--IN)") (class "Default")
      (node (ref "IC81") (pin "6") (pinfunction "-IN_6") (pintype "input"))
      (node (ref "R497") (pin "1") (pinfunction "1_1") (pintype "passive"))
      (node (ref "R498") (pin "2") (pinfunction "2_2") (pintype "passive"))
    )
    (net (code "693") (name "Net-(IC81B-OUT)") (class "Default")
      (node (ref "IC81") (pin "7") (pinfunction "OUT_7") (pintype "output"))
      (node (ref "R479") (pin "2") (pinfunction "2_2") (pintype "passive"))
      (node (ref "R484") (pin "1") (pinfunction "1_1") (pintype "passive"))
      (node (ref "R496") (pin "1") (pinfunction "1_1") (pintype "passive"))
    )
    (net (code "694") (name "Net-(IC82A-A)") (class "Default")
      (node (ref "IC82") (pin "10") (pinfunction "A_10") (pintype "input"))
      (node (ref "R516") (pin "1") (pinfunction "1_1") (pintype "passive"))
      (node (ref "R553") (pin "1") (pinfunction "1_1") (pintype "passive"))
      (node (ref "R553") (pin "2") (pinfunction "2_2") (pintype "passive"))
      (node (ref "X28") (pin "4") (pinfunction "4_4") (pintype "passive"))
      (node (ref "X29") (pin "2") (pinfunction "S_2") (pintype "passive"))
    )
    (net (code "695") (name "Net-(IC82A-B)") (class "Default")
      (node (ref "IC82") (pin "13") (pinfunction "B_13") (pintype "input"))
      (node (ref "R515") (pin "1") (pinfunction "1_1") (pintype "passive"))
      (node (ref "R552") (pin "1") (pinfunction "1_1") (pintype "passive"))
      (node (ref "R552") (pin "2") (pinfunction "2_2") (pintype "passive"))
      (node (ref "X28") (pin "3") (pinfunction "3_3") (pintype "passive"))
      (node (ref "X29") (pin "3") (pinfunction "S_3") (pintype "passive"))
    )
    (net (code "696") (name "Net-(IC82A-C)") (class "Default")
      (node (ref "IC82") (pin "12") (pinfunction "C_12") (pintype "input"))
      (node (ref "R514") (pin "1") (pinfunction "1_1") (pintype "passive"))
      (node (ref "R551") (pin "1") (pinfunction "1_1") (pintype "passive"))
      (node (ref "R551") (pin "2") (pinfunction "2_2") (pintype "passive"))
      (node (ref "X28") (pin "2") (pinfunction "2_2") (pintype "passive"))
      (node (ref "X29") (pin "4") (pinfunction "S_4") (pintype "passive"))
    )
    (net (code "697") (name "Net-(IC82A-Q0)") (class "Default")
      (node (ref "IC82") (pin "3") (pinfunction "Q0_3") (pintype "output"))
      (node (ref "IC84") (pin "1") (pinfunction "I1_1") (pintype "input"))
      (node (ref "IC84") (pin "2") (pinfunction "I2_2") (pintype "input"))
      (node (ref "Q100") (pin "1") (pinfunction "G_1") (pintype "passive"))
      (node (ref "Q108") (pin "1") (pinfunction "G_1") (pintype "passive"))
    )
    (net (code "698") (name "Net-(IC82A-Q1)") (class "Default")
      (node (ref "IC82") (pin "14") (pinfunction "Q1_14") (pintype "output"))
      (node (ref "IC84") (pin "6") (pinfunction "I6_6") (pintype "input"))
    )
    (net (code "699") (name "Net-(IC82A-Q2)") (class "Default")
      (node (ref "IC82") (pin "2") (pinfunction "Q2_2") (pintype "output"))
      (node (ref "IC84") (pin "7") (pinfunction "I7_7") (pintype "input"))
    )
    (net (code "700") (name "Net-(IC82A-Q3)") (class "Default")
      (node (ref "IC82") (pin "15") (pinfunction "Q3_15") (pintype "output"))
      (node (ref "IC84") (pin "5") (pinfunction "I5_5") (pintype "input"))
    )
    (net (code "701") (name "Net-(IC82A-Q4)") (class "Default")
      (node (ref "IC82") (pin "1") (pinfunction "Q4_1") (pintype "output"))
      (node (ref "IC84") (pin "4") (pinfunction "I4_4") (pintype "input"))
    )
    (net (code "702") (name "Net-(IC82A-Q5)") (class "Default")
      (node (ref "IC82") (pin "6") (pinfunction "Q5_6") (pintype "output"))
      (node (ref "IC84") (pin "3") (pinfunction "I3_3") (pintype "input"))
    )
    (net (code "703") (name "Net-(IC83-ADJ)") (class "Default")
      (node (ref "IC83") (pin "1") (pinfunction "ADJ_1") (pintype "input"))
      (node (ref "R512") (pin "1") (pinfunction "1_1") (pintype "passive"))
      (node (ref "R519") (pin "2") (pinfunction "2_2") (pintype "passive"))
      (node (ref "X28") (pin "7") (pinfunction "7_7") (pintype "passive"))
    )
    (net (code "704") (name "Net-(IC83-VI)") (class "Default")
      (node (ref "IC83") (pin "3") (pinfunction "VI_3") (pintype "input"))
      (node (ref "Q97") (pin "2") (pinfunction "C_2") (pintype "passive"))
    )
    (net (code "705") (name "Net-(IC83-VO)") (class "Default")
      (node (ref "IC83") (pin "2") (pinfunction "VO_2") (pintype "passive"))
      (node (ref "R512") (pin "2") (pinfunction "2_2") (pintype "passive"))
    )
    (net (code "706") (name "Net-(IC84-O1)") (class "Default")
      (node (ref "IC84") (pin "16") (pinfunction "O1_16") (pintype "open_collector"))
      (node (ref "Q100") (pin "3") (pinfunction "D_3") (pintype "passive"))
      (node (ref "R557") (pin "1") (pinfunction "1_1") (pintype "passive"))
    )
    (net (code "707") (name "Net-(IC84-O2)") (class "Default")
      (node (ref "IC84") (pin "15") (pinfunction "O2_15") (pintype "open_collector"))
      (node (ref "R531") (pin "1") (pinfunction "1_1") (pintype "passive"))
    )
    (net (code "708") (name "Net-(IC85A-+IN)") (class "Default")
      (node (ref "IC85") (pin "11") (pinfunction "+IN_11") (pintype "input"))
      (node (ref "IC85") (pin "5") (pinfunction "+IN_5") (pintype "input"))
      (node (ref "R523") (pin "1") (pinfunction "1_1") (pintype "passive"))
      (node (ref "R524") (pin "2") (pinfunction "2_2") (pintype "passive"))
      (node (ref "R525") (pin "2") (pinfunction "2_2") (pintype "passive"))
    )
    (net (code "709") (name "Net-(IC85A--IN)") (class "Default")
      (node (ref "C122") (pin "1") (pinfunction "1_1") (pintype "passive"))
      (node (ref "IC85") (pin "10") (pinfunction "-IN_10") (pintype "input"))
      (node (ref "IC85") (pin "4") (pinfunction "-IN_4") (pintype "input"))
      (node (ref "R522") (pin "1") (pinfunction "1_1") (pintype "passive"))
    )
    (net (code "710") (name "Net-(IC85A-OUT)") (class "Default")
      (node (ref "IC85") (pin "2") (pinfunction "OUT_2") (pintype "open_collector"))
      (node (ref "R525") (pin "1") (pinfunction "1_1") (pintype "passive"))
    )
    (net (code "711") (name "Net-(IC85B-+IN)") (class "Default")
      (node (ref "IC85") (pin "7") (pinfunction "+IN_7") (pintype "input"))
      (node (ref "R520") (pin "1") (pinfunction "1_1") (pintype "passive"))
      (node (ref "R534") (pin "1") (pinfunction "1_1") (pintype "passive"))
    )
    (net (code "712") (name "Net-(IC85B--IN)") (class "Default")
      (node (ref "IC85") (pin "6") (pinfunction "-IN_6") (pintype "input"))
      (node (ref "IC85") (pin "8") (pinfunction "-IN_8") (pintype "input"))
      (node (ref "R519") (pin "1") (pinfunction "1_1") (pintype "passive"))
    )
    (net (code "713") (name "Net-(IC85B-OUT)") (class "Default")
      (node (ref "IC85") (pin "1") (pinfunction "OUT_1") (pintype "open_collector"))
      (node (ref "R521") (pin "2") (pinfunction "2_2") (pintype "passive"))
      (node (ref "R526") (pin "2") (pinfunction "2_2") (pintype "passive"))
    )
    (net (code "714") (name "Net-(IC85C-+IN)") (class "Default")
      (node (ref "C125") (pin "1") (pinfunction "1_1") (pintype "passive"))
      (node (ref "IC85") (pin "9") (pinfunction "+IN_9") (pintype "input"))
      (node (ref "R528") (pin "2") (pinfunction "2_2") (pintype "passive"))
      (node (ref "R534") (pin "2") (pinfunction "2_2") (pintype "passive"))
    )
    (net (code "715") (name "Net-(IC85C-OUT)") (class "Default")
      (node (ref "C126") (pin "2") (pinfunction "2_2") (pintype "passive"))
      (node (ref "IC85") (pin "14") (pinfunction "OUT_14") (pintype "open_collector"))
      (node (ref "R527") (pin "2") (pinfunction "2_2") (pintype "passive"))
    )
    (net (code "716") (name "Net-(IC85D-OUT)") (class "Default")
      (node (ref "IC85") (pin "13") (pinfunction "OUT_13") (pintype "open_collector"))
      (node (ref "JP47") (pin "1") (pinfunction "1_1") (pintype "passive"))
      (node (ref "Q99") (pin "1") (pinfunction "G_1") (pintype "passive"))
      (node (ref "R537") (pin "2") (pinfunction "2_2") (pintype "passive"))
    )
    (net (code "717") (name "Net-(IC87-Q)") (class "Default")
      (node (ref "IC87") (pin "3") (pinfunction "Q_3") (pintype "output"))
      (node (ref "IC88") (pin "12") (pinfunction "A_12") (pintype "input"))
      (node (ref "IC88") (pin "4") (pinfunction "A_4") (pintype "input"))
    )
    (net (code "718") (name "Net-(IC88A-T2)") (class "Default")
      (node (ref "C131") (pin "2") (pinfunction "2_2") (pintype "passive"))
      (node (ref "IC88") (pin "2") (pinfunction "T2_2") (pintype "input"))
      (node (ref "R559") (pin "1") (pinfunction "1_1") (pintype "passive"))
    )
    (net (code "719") (name "Net-(IC88A-~{Q})") (class "Default")
      (node (ref "IC88") (pin "7") (pinfunction "~{Q}_7") (pintype "output"))
      (node (ref "Q110") (pin "1") (pinfunction "G_1") (pintype "passive"))
    )
    (net (code "720") (name "Net-(IC88B-B)") (class "Default")
      (node (ref "IC88") (pin "11") (pinfunction "B_11") (pintype "input"))
      (node (ref "IC88") (pin "9") (pinfunction "~{Q}_9") (pintype "output"))
      (node (ref "R544") (pin "2") (pinfunction "2_2") (pintype "passive"))
    )
    (net (code "721") (name "Net-(IC88B-T2)") (class "Default")
      (node (ref "C129") (pin "1") (pinfunction "1_1") (pintype "passive"))
      (node (ref "IC88") (pin "14") (pinfunction "T2_14") (pintype "input"))
      (node (ref "R542") (pin "1") (pinfunction "1_1") (pintype "passive"))
    )
    (net (code "722") (name "Net-(IC90A-+IN)") (class "Default")
      (node (ref "C124") (pin "1") (pinfunction "1_1") (pintype "passive"))
      (node (ref "IC90") (pin "3") (pinfunction "+IN_3") (pintype "input"))
      (node (ref "R517") (pin "1") (pinfunction "1_1") (pintype "passive"))
    )
    (net (code "723") (name "Net-(IC90A--IN)") (class "Default")
      (node (ref "IC90") (pin "2") (pinfunction "-IN_2") (pintype "input"))
      (node (ref "R518") (pin "2") (pinfunction "2_2") (pintype "passive"))
    )
    (net (code "724") (name "Net-(IC90A-OUT)") (class "Default")
      (node (ref "IC90") (pin "1") (pinfunction "OUT_1") (pintype "output"))
      (node (ref "R545") (pin "2") (pinfunction "2_2") (pintype "passive"))
    )
    (net (code "725") (name "Net-(IC90B-+IN)") (class "Default")
      (node (ref "IC90") (pin "5") (pinfunction "+IN_5") (pintype "input"))
      (node (ref "Q108") (pin "3") (pinfunction "D_3") (pintype "passive"))
      (node (ref "R546") (pin "2") (pinfunction "2_2") (pintype "passive"))
      (node (ref "R547") (pin "2") (pinfunction "2_2") (pintype "passive"))
    )
    (net (code "726") (name "Net-(IC90B--IN)") (class "Default")
      (node (ref "IC90") (pin "6") (pinfunction "-IN_6") (pintype "input"))
      (node (ref "R548") (pin "1") (pinfunction "1_1") (pintype "passive"))
      (node (ref "R549") (pin "2") (pinfunction "2_2") (pintype "passive"))
    )
    (net (code "727") (name "Net-(IC90B-OUT)") (class "Default")
      (node (ref "IC90") (pin "7") (pinfunction "OUT_7") (pintype "output"))
      (node (ref "R530") (pin "2") (pinfunction "2_2") (pintype "passive"))
      (node (ref "R535") (pin "1") (pinfunction "1_1") (pintype "passive"))
      (node (ref "R547") (pin "1") (pinfunction "1_1") (pintype "passive"))
    )
    (net (code "728") (name "Net-(IC91A-A)") (class "Default")
      (node (ref "IC91") (pin "10") (pinfunction "A_10") (pintype "input"))
      (node (ref "R567") (pin "1") (pinfunction "1_1") (pintype "passive"))
      (node (ref "R604") (pin "1") (pinfunction "1_1") (pintype "passive"))
      (node (ref "R604") (pin "2") (pinfunction "2_2") (pintype "passive"))
      (node (ref "X31") (pin "4") (pinfunction "4_4") (pintype "passive"))
      (node (ref "X32") (pin "2") (pinfunction "S_2") (pintype "passive"))
    )
    (net (code "729") (name "Net-(IC91A-B)") (class "Default")
      (node (ref "IC91") (pin "13") (pinfunction "B_13") (pintype "input"))
      (node (ref "R566") (pin "1") (pinfunction "1_1") (pintype "passive"))
      (node (ref "R603") (pin "1") (pinfunction "1_1") (pintype "passive"))
      (node (ref "R603") (pin "2") (pinfunction "2_2") (pintype "passive"))
      (node (ref "X31") (pin "3") (pinfunction "3_3") (pintype "passive"))
      (node (ref "X32") (pin "3") (pinfunction "S_3") (pintype "passive"))
    )
    (net (code "730") (name "Net-(IC91A-C)") (class "Default")
      (node (ref "IC91") (pin "12") (pinfunction "C_12") (pintype "input"))
      (node (ref "R565") (pin "1") (pinfunction "1_1") (pintype "passive"))
      (node (ref "R602") (pin "1") (pinfunction "1_1") (pintype "passive"))
      (node (ref "R602") (pin "2") (pinfunction "2_2") (pintype "passive"))
      (node (ref "X31") (pin "2") (pinfunction "2_2") (pintype "passive"))
      (node (ref "X32") (pin "4") (pinfunction "S_4") (pintype "passive"))
    )
    (net (code "731") (name "Net-(IC91A-Q0)") (class "Default")
      (node (ref "IC91") (pin "3") (pinfunction "Q0_3") (pintype "output"))
      (node (ref "IC93") (pin "1") (pinfunction "I1_1") (pintype "input"))
      (node (ref "IC93") (pin "2") (pinfunction "I2_2") (pintype "input"))
      (node (ref "Q117") (pin "1") (pinfunction "G_1") (pintype "passive"))
      (node (ref "Q118") (pin "1") (pinfunction "G_1") (pintype "passive"))
    )
    (net (code "732") (name "Net-(IC91A-Q1)") (class "Default")
      (node (ref "IC91") (pin "14") (pinfunction "Q1_14") (pintype "output"))
      (node (ref "IC93") (pin "6") (pinfunction "I6_6") (pintype "input"))
    )
    (net (code "733") (name "Net-(IC91A-Q2)") (class "Default")
      (node (ref "IC91") (pin "2") (pinfunction "Q2_2") (pintype "output"))
      (node (ref "IC93") (pin "7") (pinfunction "I7_7") (pintype "input"))
    )
    (net (code "734") (name "Net-(IC91A-Q3)") (class "Default")
      (node (ref "IC91") (pin "15") (pinfunction "Q3_15") (pintype "output"))
      (node (ref "IC93") (pin "5") (pinfunction "I5_5") (pintype "input"))
    )
    (net (code "735") (name "Net-(IC91A-Q4)") (class "Default")
      (node (ref "IC91") (pin "1") (pinfunction "Q4_1") (pintype "output"))
      (node (ref "IC93") (pin "4") (pinfunction "I4_4") (pintype "input"))
    )
    (net (code "736") (name "Net-(IC91A-Q5)") (class "Default")
      (node (ref "IC91") (pin "6") (pinfunction "Q5_6") (pintype "output"))
      (node (ref "IC93") (pin "3") (pinfunction "I3_3") (pintype "input"))
    )
    (net (code "737") (name "Net-(IC92-ADJ)") (class "Default")
      (node (ref "IC92") (pin "1") (pinfunction "ADJ_1") (pintype "input"))
      (node (ref "R563") (pin "1") (pinfunction "1_1") (pintype "passive"))
      (node (ref "R570") (pin "2") (pinfunction "2_2") (pintype "passive"))
      (node (ref "X31") (pin "7") (pinfunction "7_7") (pintype "passive"))
    )
    (net (code "738") (name "Net-(IC92-VI)") (class "Default")
      (node (ref "IC92") (pin "3") (pinfunction "VI_3") (pintype "input"))
      (node (ref "Q114") (pin "2") (pinfunction "C_2") (pintype "passive"))
    )
    (net (code "739") (name "Net-(IC92-VO)") (class "Default")
      (node (ref "IC92") (pin "2") (pinfunction "VO_2") (pintype "passive"))
      (node (ref "R563") (pin "2") (pinfunction "2_2") (pintype "passive"))
    )
    (net (code "740") (name "Net-(IC93-O1)") (class "Default")
      (node (ref "IC93") (pin "16") (pinfunction "O1_16") (pintype "open_collector"))
      (node (ref "Q117") (pin "3") (pinfunction "D_3") (pintype "passive"))
      (node (ref "R608") (pin "1") (pinfunction "1_1") (pintype "passive"))
    )
    (net (code "741") (name "Net-(IC93-O2)") (class "Default")
      (node (ref "IC93") (pin "15") (pinfunction "O2_15") (pintype "open_collector"))
      (node (ref "R582") (pin "1") (pinfunction "1_1") (pintype "passive"))
    )
    (net (code "742") (name "Net-(IC94A-+IN)") (class "Default")
      (node (ref "IC94") (pin "11") (pinfunction "+IN_11") (pintype "input"))
      (node (ref "IC94") (pin "5") (pinfunction "+IN_5") (pintype "input"))
      (node (ref "R574") (pin "1") (pinfunction "1_1") (pintype "passive"))
      (node (ref "R575") (pin "2") (pinfunction "2_2") (pintype "passive"))
      (node (ref "R576") (pin "2") (pinfunction "2_2") (pintype "passive"))
    )
    (net (code "743") (name "Net-(IC94A--IN)") (class "Default")
      (node (ref "C134") (pin "1") (pinfunction "1_1") (pintype "passive"))
      (node (ref "IC94") (pin "10") (pinfunction "-IN_10") (pintype "input"))
      (node (ref "IC94") (pin "4") (pinfunction "-IN_4") (pintype "input"))
      (node (ref "R573") (pin "1") (pinfunction "1_1") (pintype "passive"))
    )
    (net (code "744") (name "Net-(IC94A-OUT)") (class "Default")
      (node (ref "IC94") (pin "2") (pinfunction "OUT_2") (pintype "open_collector"))
      (node (ref "R576") (pin "1") (pinfunction "1_1") (pintype "passive"))
    )
    (net (code "745") (name "Net-(IC94B-+IN)") (class "Default")
      (node (ref "IC94") (pin "7") (pinfunction "+IN_7") (pintype "input"))
      (node (ref "R571") (pin "1") (pinfunction "1_1") (pintype "passive"))
      (node (ref "R585") (pin "1") (pinfunction "1_1") (pintype "passive"))
    )
    (net (code "746") (name "Net-(IC94B--IN)") (class "Default")
      (node (ref "IC94") (pin "6") (pinfunction "-IN_6") (pintype "input"))
      (node (ref "IC94") (pin "8") (pinfunction "-IN_8") (pintype "input"))
      (node (ref "R570") (pin "1") (pinfunction "1_1") (pintype "passive"))
    )
    (net (code "747") (name "Net-(IC94B-OUT)") (class "Default")
      (node (ref "IC94") (pin "1") (pinfunction "OUT_1") (pintype "open_collector"))
      (node (ref "R572") (pin "2") (pinfunction "2_2") (pintype "passive"))
      (node (ref "R577") (pin "2") (pinfunction "2_2") (pintype "passive"))
    )
    (net (code "748") (name "Net-(IC94C-+IN)") (class "Default")
      (node (ref "C137") (pin "1") (pinfunction "1_1") (pintype "passive"))
      (node (ref "IC94") (pin "9") (pinfunction "+IN_9") (pintype "input"))
      (node (ref "R579") (pin "2") (pinfunction "2_2") (pintype "passive"))
      (node (ref "R585") (pin "2") (pinfunction "2_2") (pintype "passive"))
    )
    (net (code "749") (name "Net-(IC94C-OUT)") (class "Default")
      (node (ref "C138") (pin "2") (pinfunction "2_2") (pintype "passive"))
      (node (ref "IC94") (pin "14") (pinfunction "OUT_14") (pintype "open_collector"))
      (node (ref "R578") (pin "2") (pinfunction "2_2") (pintype "passive"))
    )
    (net (code "750") (name "Net-(IC94D-OUT)") (class "Default")
      (node (ref "IC94") (pin "13") (pinfunction "OUT_13") (pintype "open_collector"))
      (node (ref "JP52") (pin "1") (pinfunction "1_1") (pintype "passive"))
      (node (ref "Q116") (pin "1") (pinfunction "G_1") (pintype "passive"))
      (node (ref "R588") (pin "2") (pinfunction "2_2") (pintype "passive"))
    )
    (net (code "751") (name "Net-(IC96-Q)") (class "Default")
      (node (ref "IC96") (pin "3") (pinfunction "Q_3") (pintype "output"))
      (node (ref "IC97") (pin "12") (pinfunction "A_12") (pintype "input"))
      (node (ref "IC97") (pin "4") (pinfunction "A_4") (pintype "input"))
    )
    (net (code "752") (name "Net-(IC97A-T2)") (class "Default")
      (node (ref "C143") (pin "2") (pinfunction "2_2") (pintype "passive"))
      (node (ref "IC97") (pin "2") (pinfunction "T2_2") (pintype "input"))
      (node (ref "R610") (pin "1") (pinfunction "1_1") (pintype "passive"))
    )
    (net (code "753") (name "Net-(IC97A-~{Q})") (class "Default")
      (node (ref "IC97") (pin "7") (pinfunction "~{Q}_7") (pintype "output"))
      (node (ref "Q120") (pin "1") (pinfunction "G_1") (pintype "passive"))
    )
    (net (code "754") (name "Net-(IC97B-B)") (class "Default")
      (node (ref "IC97") (pin "11") (pinfunction "B_11") (pintype "input"))
      (node (ref "IC97") (pin "9") (pinfunction "~{Q}_9") (pintype "output"))
      (node (ref "R595") (pin "2") (pinfunction "2_2") (pintype "passive"))
    )
    (net (code "755") (name "Net-(IC97B-T2)") (class "Default")
      (node (ref "C141") (pin "1") (pinfunction "1_1") (pintype "passive"))
      (node (ref "IC97") (pin "14") (pinfunction "T2_14") (pintype "input"))
      (node (ref "R593") (pin "1") (pinfunction "1_1") (pintype "passive"))
    )
    (net (code "756") (name "Net-(IC99A-+IN)") (class "Default")
      (node (ref "C136") (pin "1") (pinfunction "1_1") (pintype "passive"))
      (node (ref "IC99") (pin "3") (pinfunction "+IN_3") (pintype "input"))
      (node (ref "R568") (pin "1") (pinfunction "1_1") (pintype "passive"))
    )
    (net (code "757") (name "Net-(IC99A--IN)") (class "Default")
      (node (ref "IC99") (pin "2") (pinfunction "-IN_2") (pintype "input"))
      (node (ref "R569") (pin "2") (pinfunction "2_2") (pintype "passive"))
    )
    (net (code "758") (name "Net-(IC99A-OUT)") (class "Default")
      (node (ref "IC99") (pin "1") (pinfunction "OUT_1") (pintype "output"))
      (node (ref "R596") (pin "2") (pinfunction "2_2") (pintype "passive"))
    )
    (net (code "759") (name "Net-(IC99B-+IN)") (class "Default")
      (node (ref "IC99") (pin "5") (pinfunction "+IN_5") (pintype "input"))
      (node (ref "Q118") (pin "3") (pinfunction "D_3") (pintype "passive"))
      (node (ref "R597") (pin "2") (pinfunction "2_2") (pintype "passive"))
      (node (ref "R598") (pin "2") (pinfunction "2_2") (pintype "passive"))
    )
    (net (code "760") (name "Net-(IC99B--IN)") (class "Default")
      (node (ref "IC99") (pin "6") (pinfunction "-IN_6") (pintype "input"))
      (node (ref "R599") (pin "1") (pinfunction "1_1") (pintype "passive"))
      (node (ref "R600") (pin "2") (pinfunction "2_2") (pintype "passive"))
    )
    (net (code "761") (name "Net-(IC99B-OUT)") (class "Default")
      (node (ref "IC99") (pin "7") (pinfunction "OUT_7") (pintype "output"))
      (node (ref "R581") (pin "2") (pinfunction "2_2") (pintype "passive"))
      (node (ref "R586") (pin "1") (pinfunction "1_1") (pintype "passive"))
      (node (ref "R598") (pin "1") (pinfunction "1_1") (pintype "passive"))
    )
    (net (code "762") (name "Net-(IC101A-+IN)") (class "Default")
      (node (ref "C101") (pin "1") (pinfunction "1_1") (pintype "passive"))
      (node (ref "IC101") (pin "3") (pinfunction "+IN_3") (pintype "input"))
      (node (ref "R105") (pin "1") (pinfunction "1_1") (pintype "passive"))
    )
    (net (code "763") (name "Net-(IC101A--IN)") (class "Default")
      (node (ref "IC101") (pin "2") (pinfunction "-IN_2") (pintype "input"))
      (node (ref "R107") (pin "2") (pinfunction "2_2") (pintype "passive"))
    )
    (net (code "764") (name "Net-(IC101A-OUT)") (class "Default")
      (node (ref "IC101") (pin "1") (pinfunction "OUT_1") (pintype "output"))
      (node (ref "R108") (pin "2") (pinfunction "2_2") (pintype "passive"))
    )
    (net (code "765") (name "Net-(IC101B-+IN)") (class "Default")
      (node (ref "IC101") (pin "5") (pinfunction "+IN_5") (pintype "input"))
      (node (ref "Q1") (pin "3") (pinfunction "D_3") (pintype "passive"))
      (node (ref "R112") (pin "2") (pinfunction "2_2") (pintype "passive"))
      (node (ref "R117") (pin "2") (pinfunction "2_2") (pintype "passive"))
    )
    (net (code "766") (name "Net-(IC101B--IN)") (class "Default")
      (node (ref "IC101") (pin "6") (pinfunction "-IN_6") (pintype "input"))
      (node (ref "R113") (pin "1") (pinfunction "1_1") (pintype "passive"))
      (node (ref "R114") (pin "2") (pinfunction "2_2") (pintype "passive"))
    )
    (net (code "767") (name "Net-(IC101B-OUT)") (class "Default")
      (node (ref "IC101") (pin "7") (pinfunction "OUT_7") (pintype "output"))
      (node (ref "R115") (pin "2") (pinfunction "2_2") (pintype "passive"))
      (node (ref "R116") (pin "1") (pinfunction "1_1") (pintype "passive"))
      (node (ref "R117") (pin "1") (pinfunction "1_1") (pintype "passive"))
    )
    (net (code "768") (name "Net-(IC105A-A)") (class "Default")
      (node (ref "IC105") (pin "10") (pinfunction "A_10") (pintype "input"))
      (node (ref "R111") (pin "1") (pinfunction "1_1") (pintype "passive"))
      (node (ref "R3") (pin "1") (pinfunction "1_1") (pintype "passive"))
      (node (ref "R3") (pin "2") (pinfunction "2_2") (pintype "passive"))
      (node (ref "X101") (pin "4") (pinfunction "4_4") (pintype "passive"))
      (node (ref "X103") (pin "2") (pinfunction "S_2") (pintype "passive"))
    )
    (net (code "769") (name "Net-(IC105A-B)") (class "Default")
      (node (ref "IC105") (pin "13") (pinfunction "B_13") (pintype "input"))
      (node (ref "R110") (pin "1") (pinfunction "1_1") (pintype "passive"))
      (node (ref "R2") (pin "1") (pinfunction "1_1") (pintype "passive"))
      (node (ref "R2") (pin "2") (pinfunction "2_2") (pintype "passive"))
      (node (ref "X101") (pin "3") (pinfunction "3_3") (pintype "passive"))
      (node (ref "X103") (pin "3") (pinfunction "S_3") (pintype "passive"))
    )
    (net (code "770") (name "Net-(IC105A-C)") (class "Default")
      (node (ref "IC105") (pin "12") (pinfunction "C_12") (pintype "input"))
      (node (ref "R1") (pin "1") (pinfunction "1_1") (pintype "passive"))
      (node (ref "R1") (pin "2") (pinfunction "2_2") (pintype "passive"))
      (node (ref "R109") (pin "1") (pinfunction "1_1") (pintype "passive"))
      (node (ref "X101") (pin "2") (pinfunction "2_2") (pintype "passive"))
      (node (ref "X103") (pin "4") (pinfunction "S_4") (pintype "passive"))
    )
    (net (code "771") (name "Net-(IC105A-Q0)") (class "Default")
      (node (ref "IC105") (pin "3") (pinfunction "Q0_3") (pintype "output"))
      (node (ref "IC107") (pin "1") (pinfunction "I1_1") (pintype "input"))
      (node (ref "IC107") (pin "2") (pinfunction "I2_2") (pintype "input"))
      (node (ref "Q1") (pin "1") (pinfunction "G_1") (pintype "passive"))
      (node (ref "Q106") (pin "1") (pinfunction "G_1") (pintype "passive"))
    )
    (net (code "772") (name "Net-(IC105A-Q1)") (class "Default")
      (node (ref "IC105") (pin "14") (pinfunction "Q1_14") (pintype "output"))
      (node (ref "IC107") (pin "6") (pinfunction "I6_6") (pintype "input"))
    )
    (net (code "773") (name "Net-(IC105A-Q2)") (class "Default")
      (node (ref "IC105") (pin "2") (pinfunction "Q2_2") (pintype "output"))
      (node (ref "IC107") (pin "7") (pinfunction "I7_7") (pintype "input"))
    )
    (net (code "774") (name "Net-(IC105A-Q3)") (class "Default")
      (node (ref "IC105") (pin "15") (pinfunction "Q3_15") (pintype "output"))
      (node (ref "IC107") (pin "5") (pinfunction "I5_5") (pintype "input"))
    )
    (net (code "775") (name "Net-(IC105A-Q4)") (class "Default")
      (node (ref "IC105") (pin "1") (pinfunction "Q4_1") (pintype "output"))
      (node (ref "IC107") (pin "4") (pinfunction "I4_4") (pintype "input"))
    )
    (net (code "776") (name "Net-(IC105A-Q5)") (class "Default")
      (node (ref "IC105") (pin "6") (pinfunction "Q5_6") (pintype "output"))
      (node (ref "IC107") (pin "3") (pinfunction "I3_3") (pintype "input"))
    )
    (net (code "777") (name "Net-(IC107-O1)") (class "Default")
      (node (ref "IC107") (pin "16") (pinfunction "O1_16") (pintype "open_collector"))
      (node (ref "Q106") (pin "3") (pinfunction "D_3") (pintype "passive"))
      (node (ref "R9") (pin "1") (pinfunction "1_1") (pintype "passive"))
    )
    (net (code "778") (name "Net-(IC107-O2)") (class "Default")
      (node (ref "IC107") (pin "15") (pinfunction "O2_15") (pintype "open_collector"))
      (node (ref "R128") (pin "1") (pinfunction "1_1") (pintype "passive"))
    )
    (net (code "779") (name "Net-(IC108A-+IN)") (class "Default")
      (node (ref "IC108") (pin "11") (pinfunction "+IN_11") (pintype "input"))
      (node (ref "IC108") (pin "5") (pinfunction "+IN_5") (pintype "input"))
      (node (ref "R131") (pin "1") (pinfunction "1_1") (pintype "passive"))
      (node (ref "R132") (pin "2") (pinfunction "2_2") (pintype "passive"))
      (node (ref "R133") (pin "2") (pinfunction "2_2") (pintype "passive"))
    )
    (net (code "780") (name "Net-(IC108A--IN)") (class "Default")
      (node (ref "C108") (pin "1") (pinfunction "1_1") (pintype "passive"))
      (node (ref "IC108") (pin "10") (pinfunction "-IN_10") (pintype "input"))
      (node (ref "IC108") (pin "4") (pinfunction "-IN_4") (pintype "input"))
      (node (ref "R130") (pin "1") (pinfunction "1_1") (pintype "passive"))
    )
    (net (code "781") (name "Net-(IC108A-OUT)") (class "Default")
      (node (ref "IC108") (pin "2") (pinfunction "OUT_2") (pintype "open_collector"))
      (node (ref "R133") (pin "1") (pinfunction "1_1") (pintype "passive"))
    )
    (net (code "782") (name "Net-(IC108B-+IN)") (class "Default")
      (node (ref "IC108") (pin "7") (pinfunction "+IN_7") (pintype "input"))
      (node (ref "R121") (pin "1") (pinfunction "1_1") (pintype "passive"))
      (node (ref "R122") (pin "1") (pinfunction "1_1") (pintype "passive"))
    )
    (net (code "783") (name "Net-(IC108B--IN)") (class "Default")
      (node (ref "IC108") (pin "6") (pinfunction "-IN_6") (pintype "input"))
      (node (ref "IC108") (pin "8") (pinfunction "-IN_8") (pintype "input"))
      (node (ref "R120") (pin "1") (pinfunction "1_1") (pintype "passive"))
    )
    (net (code "784") (name "Net-(IC108B-OUT)") (class "Default")
      (node (ref "IC108") (pin "1") (pinfunction "OUT_1") (pintype "open_collector"))
      (node (ref "R124") (pin "2") (pinfunction "2_2") (pintype "passive"))
      (node (ref "R125") (pin "2") (pinfunction "2_2") (pintype "passive"))
    )
    (net (code "785") (name "Net-(IC108C-+IN)") (class "Default")
      (node (ref "C105") (pin "1") (pinfunction "1_1") (pintype "passive"))
      (node (ref "IC108") (pin "9") (pinfunction "+IN_9") (pintype "input"))
      (node (ref "R122") (pin "2") (pinfunction "2_2") (pintype "passive"))
      (node (ref "R123") (pin "2") (pinfunction "2_2") (pintype "passive"))
    )
    (net (code "786") (name "Net-(IC108C-OUT)") (class "Default")
      (node (ref "C106") (pin "2") (pinfunction "2_2") (pintype "passive"))
      (node (ref "IC108") (pin "14") (pinfunction "OUT_14") (pintype "open_collector"))
      (node (ref "R126") (pin "2") (pinfunction "2_2") (pintype "passive"))
    )
    (net (code "787") (name "Net-(IC108D-OUT)") (class "Default")
      (node (ref "IC108") (pin "13") (pinfunction "OUT_13") (pintype "open_collector"))
      (node (ref "JP105") (pin "1") (pinfunction "1_1") (pintype "passive"))
      (node (ref "Q107") (pin "1") (pinfunction "G_1") (pintype "passive"))
      (node (ref "R135") (pin "2") (pinfunction "2_2") (pintype "passive"))
    )
    (net (code "788") (name "Net-(IC109-ADJ)") (class "Default")
      (node (ref "IC109") (pin "1") (pinfunction "ADJ_1") (pintype "input"))
      (node (ref "R120") (pin "2") (pinfunction "2_2") (pintype "passive"))
      (node (ref "R134") (pin "1") (pinfunction "1_1") (pintype "passive"))
      (node (ref "X101") (pin "7") (pinfunction "7_7") (pintype "passive"))
    )
    (net (code "789") (name "Net-(IC109-VI)") (class "Default")
      (node (ref "IC109") (pin "3") (pinfunction "VI_3") (pintype "input"))
      (node (ref "Q105") (pin "2") (pinfunction "C_2") (pintype "passive"))
    )
    (net (code "790") (name "Net-(IC109-VO)") (class "Default")
      (node (ref "IC109") (pin "2") (pinfunction "VO_2") (pintype "passive"))
      (node (ref "R134") (pin "2") (pinfunction "2_2") (pintype "passive"))
    )
    (net (code "791") (name "Net-(IC110-Q)") (class "Default")
      (node (ref "IC110") (pin "3") (pinfunction "Q_3") (pintype "output"))
      (node (ref "IC111") (pin "12") (pinfunction "A_12") (pintype "input"))
      (node (ref "IC111") (pin "4") (pinfunction "A_4") (pintype "input"))
    )
    (net (code "792") (name "Net-(IC111A-T2)") (class "Default")
      (node (ref "C15") (pin "2") (pinfunction "2_2") (pintype "passive"))
      (node (ref "IC111") (pin "2") (pinfunction "T2_2") (pintype "input"))
      (node (ref "R10") (pin "1") (pinfunction "1_1") (pintype "passive"))
    )
    (net (code "793") (name "Net-(IC111A-~{Q})") (class "Default")
      (node (ref "IC111") (pin "7") (pinfunction "~{Q}_7") (pintype "output"))
      (node (ref "Q3") (pin "1") (pinfunction "G_1") (pintype "passive"))
    )
    (net (code "794") (name "Net-(IC111B-B)") (class "Default")
      (node (ref "IC111") (pin "11") (pinfunction "B_11") (pintype "input"))
      (node (ref "IC111") (pin "9") (pinfunction "~{Q}_9") (pintype "output"))
      (node (ref "R146") (pin "2") (pinfunction "2_2") (pintype "passive"))
    )
    (net (code "795") (name "Net-(IC111B-T2)") (class "Default")
      (node (ref "C110") (pin "1") (pinfunction "1_1") (pintype "passive"))
      (node (ref "IC111") (pin "14") (pinfunction "T2_14") (pintype "input"))
      (node (ref "R145") (pin "1") (pinfunction "1_1") (pintype "passive"))
    )
    (net (code "796") (name "Net-(JP1-Pad1)") (class "Default")
      (node (ref "JP1") (pin "1") (pinfunction "1_1") (pintype "passive"))
      (node (ref "R48") (pin "2") (pinfunction "2_2") (pintype "passive"))
    )
    (net (code "797") (name "Net-(JP2-Pad3)") (class "Default")
      (node (ref "JP2") (pin "3") (pinfunction "3_3") (pintype "passive"))
      (node (ref "R40") (pin "1") (pinfunction "1_1") (pintype "passive"))
    )
    (net (code "798") (name "Net-(JP5-Pad2)") (class "Default")
      (node (ref "JP5") (pin "2") (pinfunction "2_2") (pintype "passive"))
      (node (ref "R45") (pin "2") (pinfunction "2_2") (pintype "passive"))
      (node (ref "R46") (pin "2") (pinfunction "2_2") (pintype "passive"))
    )
    (net (code "799") (name "Net-(JP6-Pad1)") (class "Default")
      (node (ref "JP6") (pin "1") (pinfunction "1_1") (pintype "passive"))
      (node (ref "R147") (pin "2") (pinfunction "2_2") (pintype "passive"))
    )
    (net (code "800") (name "Net-(JP7-Pad3)") (class "Default")
      (node (ref "JP7") (pin "3") (pinfunction "3_3") (pintype "passive"))
      (node (ref "R95") (pin "1") (pinfunction "1_1") (pintype "passive"))
    )
    (net (code "801") (name "Net-(JP10-Pad2)") (class "Default")
      (node (ref "JP10") (pin "2") (pinfunction "2_2") (pintype "passive"))
      (node (ref "R100") (pin "2") (pinfunction "2_2") (pintype "passive"))
      (node (ref "R118") (pin "2") (pinfunction "2_2") (pintype "passive"))
    )
    (net (code "802") (name "Net-(JP11-Pad1)") (class "Default")
      (node (ref "JP11") (pin "1") (pinfunction "1_1") (pintype "passive"))
      (node (ref "R202") (pin "2") (pinfunction "2_2") (pintype "passive"))
    )
    (net (code "803") (name "Net-(JP12-Pad3)") (class "Default")
      (node (ref "JP12") (pin "3") (pinfunction "3_3") (pintype "passive"))
      (node (ref "R194") (pin "1") (pinfunction "1_1") (pintype "passive"))
    )
    (net (code "804") (name "Net-(JP15-Pad2)") (class "Default")
      (node (ref "JP15") (pin "2") (pinfunction "2_2") (pintype "passive"))
      (node (ref "R199") (pin "2") (pinfunction "2_2") (pintype "passive"))
      (node (ref "R200") (pin "2") (pinfunction "2_2") (pintype "passive"))
    )
    (net (code "805") (name "Net-(JP16-Pad1)") (class "Default")
      (node (ref "JP16") (pin "1") (pinfunction "1_1") (pintype "passive"))
      (node (ref "R257") (pin "2") (pinfunction "2_2") (pintype "passive"))
    )
    (net (code "806") (name "Net-(JP17-Pad3)") (class "Default")
      (node (ref "JP17") (pin "3") (pinfunction "3_3") (pintype "passive"))
      (node (ref "R249") (pin "1") (pinfunction "1_1") (pintype "passive"))
    )
    (net (code "807") (name "Net-(JP20-Pad2)") (class "Default")
      (node (ref "JP20") (pin "2") (pinfunction "2_2") (pintype "passive"))
      (node (ref "R254") (pin "2") (pinfunction "2_2") (pintype "passive"))
      (node (ref "R255") (pin "2") (pinfunction "2_2") (pintype "passive"))
    )
    (net (code "808") (name "Net-(JP21-Pad1)") (class "Default")
      (node (ref "JP21") (pin "1") (pinfunction "1_1") (pintype "passive"))
      (node (ref "R312") (pin "2") (pinfunction "2_2") (pintype "passive"))
    )
    (net (code "809") (name "Net-(JP22-Pad3)") (class "Default")
      (node (ref "JP22") (pin "3") (pinfunction "3_3") (pintype "passive"))
      (node (ref "R304") (pin "1") (pinfunction "1_1") (pintype "passive"))
    )
    (net (code "810") (name "Net-(JP25-Pad2)") (class "Default")
      (node (ref "JP25") (pin "2") (pinfunction "2_2") (pintype "passive"))
      (node (ref "R309") (pin "2") (pinfunction "2_2") (pintype "passive"))
      (node (ref "R310") (pin "2") (pinfunction "2_2") (pintype "passive"))
    )
    (net (code "811") (name "Net-(JP26-Pad1)") (class "Default")
      (node (ref "JP26") (pin "1") (pinfunction "1_1") (pintype "passive"))
      (node (ref "R339") (pin "2") (pinfunction "2_2") (pintype "passive"))
    )
    (net (code "812") (name "Net-(JP27-Pad3)") (class "Default")
      (node (ref "JP27") (pin "3") (pinfunction "3_3") (pintype "passive"))
      (node (ref "R332") (pin "1") (pinfunction "1_1") (pintype "passive"))
    )
    (net (code "813") (name "Net-(JP30-Pad2)") (class "Default")
      (node (ref "JP30") (pin "2") (pinfunction "2_2") (pintype "passive"))
      (node (ref "R336") (pin "2") (pinfunction "2_2") (pintype "passive"))
      (node (ref "R337") (pin "2") (pinfunction "2_2") (pintype "passive"))
    )
    (net (code "814") (name "Net-(JP31-Pad1)") (class "Default")
      (node (ref "JP31") (pin "1") (pinfunction "1_1") (pintype "passive"))
      (node (ref "R390") (pin "2") (pinfunction "2_2") (pintype "passive"))
    )
    (net (code "815") (name "Net-(JP32-Pad3)") (class "Default")
      (node (ref "JP32") (pin "3") (pinfunction "3_3") (pintype "passive"))
      (node (ref "R383") (pin "1") (pinfunction "1_1") (pintype "passive"))
    )
    (net (code "816") (name "Net-(JP35-Pad2)") (class "Default")
      (node (ref "JP35") (pin "2") (pinfunction "2_2") (pintype "passive"))
      (node (ref "R387") (pin "2") (pinfunction "2_2") (pintype "passive"))
      (node (ref "R388") (pin "2") (pinfunction "2_2") (pintype "passive"))
    )
    (net (code "817") (name "Net-(JP36-Pad1)") (class "Default")
      (node (ref "JP36") (pin "1") (pinfunction "1_1") (pintype "passive"))
      (node (ref "R441") (pin "2") (pinfunction "2_2") (pintype "passive"))
    )
    (net (code "818") (name "Net-(JP37-Pad3)") (class "Default")
      (node (ref "JP37") (pin "3") (pinfunction "3_3") (pintype "passive"))
      (node (ref "R434") (pin "1") (pinfunction "1_1") (pintype "passive"))
    )
    (net (code "819") (name "Net-(JP40-Pad2)") (class "Default")
      (node (ref "JP40") (pin "2") (pinfunction "2_2") (pintype "passive"))
      (node (ref "R438") (pin "2") (pinfunction "2_2") (pintype "passive"))
      (node (ref "R439") (pin "2") (pinfunction "2_2") (pintype "passive"))
    )
    (net (code "820") (name "Net-(JP41-Pad1)") (class "Default")
      (node (ref "JP41") (pin "1") (pinfunction "1_1") (pintype "passive"))
      (node (ref "R492") (pin "2") (pinfunction "2_2") (pintype "passive"))
    )
    (net (code "821") (name "Net-(JP42-Pad3)") (class "Default")
      (node (ref "JP42") (pin "3") (pinfunction "3_3") (pintype "passive"))
      (node (ref "R485") (pin "1") (pinfunction "1_1") (pintype "passive"))
    )
    (net (code "822") (name "Net-(JP45-Pad2)") (class "Default")
      (node (ref "JP45") (pin "2") (pinfunction "2_2") (pintype "passive"))
      (node (ref "R489") (pin "2") (pinfunction "2_2") (pintype "passive"))
      (node (ref "R490") (pin "2") (pinfunction "2_2") (pintype "passive"))
    )
    (net (code "823") (name "Net-(JP46-Pad1)") (class "Default")
      (node (ref "JP46") (pin "1") (pinfunction "1_1") (pintype "passive"))
      (node (ref "R543") (pin "2") (pinfunction "2_2") (pintype "passive"))
    )
    (net (code "824") (name "Net-(JP47-Pad3)") (class "Default")
      (node (ref "JP47") (pin "3") (pinfunction "3_3") (pintype "passive"))
      (node (ref "R536") (pin "1") (pinfunction "1_1") (pintype "passive"))
    )
    (net (code "825") (name "Net-(JP50-Pad2)") (class "Default")
      (node (ref "JP50") (pin "2") (pinfunction "2_2") (pintype "passive"))
      (node (ref "R540") (pin "2") (pinfunction "2_2") (pintype "passive"))
      (node (ref "R541") (pin "2") (pinfunction "2_2") (pintype "passive"))
    )
    (net (code "826") (name "Net-(JP51-Pad1)") (class "Default")
      (node (ref "JP51") (pin "1") (pinfunction "1_1") (pintype "passive"))
      (node (ref "R594") (pin "2") (pinfunction "2_2") (pintype "passive"))
    )
    (net (code "827") (name "Net-(JP52-Pad3)") (class "Default")
      (node (ref "JP52") (pin "3") (pinfunction "3_3") (pintype "passive"))
      (node (ref "R587") (pin "1") (pinfunction "1_1") (pintype "passive"))
    )
    (net (code "828") (name "Net-(JP55-Pad2)") (class "Default")
      (node (ref "JP55") (pin "2") (pinfunction "2_2") (pintype "passive"))
      (node (ref "R591") (pin "2") (pinfunction "2_2") (pintype "passive"))
      (node (ref "R592") (pin "2") (pinfunction "2_2") (pintype "passive"))
    )
    (net (code "829") (name "Net-(JP101-Pad1)") (class "Default")
      (node (ref "JP101") (pin "1") (pinfunction "1_1") (pintype "passive"))
      (node (ref "R119") (pin "2") (pinfunction "2_2") (pintype "passive"))
    )
    (net (code "830") (name "Net-(JP104-Pad2)") (class "Default")
      (node (ref "JP104") (pin "2") (pinfunction "2_2") (pintype "passive"))
      (node (ref "R136") (pin "2") (pinfunction "2_2") (pintype "passive"))
      (node (ref "R137") (pin "2") (pinfunction "2_2") (pintype "passive"))
    )
    (net (code "831") (name "Net-(JP105-Pad3)") (class "Default")
      (node (ref "JP105") (pin "3") (pinfunction "3_3") (pintype "passive"))
      (node (ref "R138") (pin "1") (pinfunction "1_1") (pintype "passive"))
    )
    (net (code "832") (name "Net-(LED1-PadA)") (class "Default")
      (node (ref "LED1") (pin "A") (pinfunction "A_A") (pintype "passive"))
      (node (ref "LED2") (pin "A") (pinfunction "A_A") (pintype "passive"))
      (node (ref "LED3") (pin "A") (pinfunction "A_A") (pintype "passive"))
      (node (ref "LED4") (pin "A") (pinfunction "A_A") (pintype "passive"))
      (node (ref "LED6") (pin "A") (pinfunction "A_A") (pintype "passive"))
    )
    (net (code "833") (name "Net-(LED10-PadA)") (class "Default")
      (node (ref "LED10") (pin "A") (pinfunction "A_A") (pintype "passive"))
      (node (ref "LED12") (pin "A") (pinfunction "A_A") (pintype "passive"))
      (node (ref "LED7") (pin "A") (pinfunction "A_A") (pintype "passive"))
      (node (ref "LED8") (pin "A") (pinfunction "A_A") (pintype "passive"))
      (node (ref "LED9") (pin "A") (pinfunction "A_A") (pintype "passive"))
    )
    (net (code "834") (name "Net-(LED13-PadA)") (class "Default")
      (node (ref "LED13") (pin "A") (pinfunction "A_A") (pintype "passive"))
      (node (ref "LED14") (pin "A") (pinfunction "A_A") (pintype "passive"))
      (node (ref "LED15") (pin "A") (pinfunction "A_A") (pintype "passive"))
      (node (ref "LED16") (pin "A") (pinfunction "A_A") (pintype "passive"))
      (node (ref "LED18") (pin "A") (pinfunction "A_A") (pintype "passive"))
    )
    (net (code "835") (name "Net-(LED19-PadA)") (class "Default")
      (node (ref "LED19") (pin "A") (pinfunction "A_A") (pintype "passive"))
      (node (ref "LED20") (pin "A") (pinfunction "A_A") (pintype "passive"))
      (node (ref "LED21") (pin "A") (pinfunction "A_A") (pintype "passive"))
      (node (ref "LED22") (pin "A") (pinfunction "A_A") (pintype "passive"))
      (node (ref "LED24") (pin "A") (pinfunction "A_A") (pintype "passive"))
    )
    (net (code "836") (name "Net-(LED25-PadA)") (class "Default")
      (node (ref "LED25") (pin "A") (pinfunction "A_A") (pintype "passive"))
      (node (ref "LED26") (pin "A") (pinfunction "A_A") (pintype "passive"))
      (node (ref "LED27") (pin "A") (pinfunction "A_A") (pintype "passive"))
      (node (ref "LED28") (pin "A") (pinfunction "A_A") (pintype "passive"))
      (node (ref "LED30") (pin "A") (pinfunction "A_A") (pintype "passive"))
    )
    (net (code "837") (name "Net-(LED31-PadA)") (class "Default")
      (node (ref "LED31") (pin "A") (pinfunction "A_A") (pintype "passive"))
      (node (ref "LED32") (pin "A") (pinfunction "A_A") (pintype "passive"))
      (node (ref "LED33") (pin "A") (pinfunction "A_A") (pintype "passive"))
      (node (ref "LED34") (pin "A") (pinfunction "A_A") (pintype "passive"))
      (node (ref "LED36") (pin "A") (pinfunction "A_A") (pintype "passive"))
    )
    (net (code "838") (name "Net-(LED37-PadA)") (class "Default")
      (node (ref "LED37") (pin "A") (pinfunction "A_A") (pintype "passive"))
      (node (ref "LED38") (pin "A") (pinfunction "A_A") (pintype "passive"))
      (node (ref "LED39") (pin "A") (pinfunction "A_A") (pintype "passive"))
      (node (ref "LED40") (pin "A") (pinfunction "A_A") (pintype "passive"))
      (node (ref "LED42") (pin "A") (pinfunction "A_A") (pintype "passive"))
    )
    (net (code "839") (name "Net-(LED43-PadA)") (class "Default")
      (node (ref "LED43") (pin "A") (pinfunction "A_A") (pintype "passive"))
      (node (ref "LED44") (pin "A") (pinfunction "A_A") (pintype "passive"))
      (node (ref "LED45") (pin "A") (pinfunction "A_A") (pintype "passive"))
      (node (ref "LED46") (pin "A") (pinfunction "A_A") (pintype "passive"))
      (node (ref "LED48") (pin "A") (pinfunction "A_A") (pintype "passive"))
    )
    (net (code "840") (name "Net-(LED49-PadA)") (class "Default")
      (node (ref "LED49") (pin "A") (pinfunction "A_A") (pintype "passive"))
      (node (ref "LED50") (pin "A") (pinfunction "A_A") (pintype "passive"))
      (node (ref "LED51") (pin "A") (pinfunction "A_A") (pintype "passive"))
      (node (ref "LED52") (pin "A") (pinfunction "A_A") (pintype "passive"))
      (node (ref "LED54") (pin "A") (pinfunction "A_A") (pintype "passive"))
    )
    (net (code "841") (name "Net-(LED55-PadA)") (class "Default")
      (node (ref "LED55") (pin "A") (pinfunction "A_A") (pintype "passive"))
      (node (ref "LED56") (pin "A") (pinfunction "A_A") (pintype "passive"))
      (node (ref "LED57") (pin "A") (pinfunction "A_A") (pintype "passive"))
      (node (ref "LED58") (pin "A") (pinfunction "A_A") (pintype "passive"))
      (node (ref "LED60") (pin "A") (pinfunction "A_A") (pintype "passive"))
    )
    (net (code "842") (name "Net-(LED61-PadA)") (class "Default")
      (node (ref "LED61") (pin "A") (pinfunction "A_A") (pintype "passive"))
      (node (ref "LED62") (pin "A") (pinfunction "A_A") (pintype "passive"))
      (node (ref "LED63") (pin "A") (pinfunction "A_A") (pintype "passive"))
      (node (ref "LED64") (pin "A") (pinfunction "A_A") (pintype "passive"))
      (node (ref "LED66") (pin "A") (pinfunction "A_A") (pintype "passive"))
    )
    (net (code "843") (name "Net-(LED102-PadA)") (class "Default")
      (node (ref "LED102") (pin "A") (pinfunction "A_A") (pintype "passive"))
      (node (ref "LED103") (pin "A") (pinfunction "A_A") (pintype "passive"))
      (node (ref "LED104") (pin "A") (pinfunction "A_A") (pintype "passive"))
      (node (ref "LED105") (pin "A") (pinfunction "A_A") (pintype "passive"))
      (node (ref "LED106") (pin "A") (pinfunction "A_A") (pintype "passive"))
    )
    (net (code "844") (name "Net-(Q2-B)") (class "Default")
      (node (ref "Q2") (pin "1") (pinfunction "B_1") (pintype "passive"))
      (node (ref "R8") (pin "1") (pinfunction "1_1") (pintype "passive"))
    )
    (net (code "845") (name "Net-(Q2-C)") (class "Default")
      (node (ref "Q2") (pin "2") (pinfunction "C_2") (pintype "passive"))
      (node (ref "R129") (pin "2") (pinfunction "2_2") (pintype "passive"))
      (node (ref "SJMP") (pin "2") (pinfunction "2_2") (pintype "passive"))
    )
    (net (code "846") (name "Net-(Q3-D)") (class "Default")
      (node (ref "Q3") (pin "3") (pinfunction "D_3") (pintype "passive"))
      (node (ref "R8") (pin "2") (pinfunction "2_2") (pintype "passive"))
    )
    (net (code "847") (name "Net-(Q4-B)") (class "Default")
      (node (ref "Q4") (pin "1") (pinfunction "B_1") (pintype "passive"))
      (node (ref "R35") (pin "2") (pinfunction "2_2") (pintype "passive"))
    )
    (net (code "848") (name "Net-(Q5-B)") (class "Default")
      (node (ref "Q5") (pin "1") (pinfunction "B_1") (pintype "passive"))
      (node (ref "Q5") (pin "2") (pinfunction "C_2") (pintype "passive"))
      (node (ref "Q6") (pin "1") (pinfunction "B_1") (pintype "passive"))
      (node (ref "R30") (pin "1") (pinfunction "1_1") (pintype "passive"))
      (node (ref "R55") (pin "1") (pinfunction "1_1") (pintype "passive"))
      (node (ref "X3") (pin "2") (pinfunction "S_2") (pintype "passive"))
    )
    (net (code "849") (name "Net-(Q5-E)") (class "Default")
      (node (ref "Q5") (pin "3") (pinfunction "E_3") (pintype "passive"))
      (node (ref "R36") (pin "2") (pinfunction "2_2") (pintype "passive"))
    )
    (net (code "850") (name "Net-(Q6-E)") (class "Default")
      (node (ref "Q6") (pin "3") (pinfunction "E_3") (pintype "passive"))
      (node (ref "R37") (pin "2") (pinfunction "2_2") (pintype "passive"))
    )
    (net (code "851") (name "Net-(Q7-B)") (class "Default")
      (node (ref "Q7") (pin "1") (pinfunction "B_1") (pintype "passive"))
      (node (ref "R28") (pin "1") (pinfunction "1_1") (pintype "passive"))
    )
    (net (code "852") (name "Net-(Q8-B)") (class "Default")
      (node (ref "Q8") (pin "1") (pinfunction "B_1") (pintype "passive"))
      (node (ref "R39") (pin "2") (pinfunction "2_2") (pintype "passive"))
      (node (ref "R60") (pin "1") (pinfunction "1_1") (pintype "passive"))
    )
    (net (code "853") (name "Net-(Q8-E)") (class "Default")
      (node (ref "Q8") (pin "3") (pinfunction "E_3") (pintype "passive"))
      (node (ref "R59") (pin "1") (pinfunction "1_1") (pintype "passive"))
    )
    (net (code "854") (name "Net-(Q9-D)") (class "Default")
      (node (ref "Q9") (pin "3") (pinfunction "D_3") (pintype "passive"))
      (node (ref "R40") (pin "2") (pinfunction "2_2") (pintype "passive"))
    )
    (net (code "855") (name "Net-(Q10-S)") (class "Default")
      (node (ref "Q10") (pin "2") (pinfunction "S_2") (pintype "passive"))
      (node (ref "R61") (pin "2") (pinfunction "2_2") (pintype "passive"))
    )
    (net (code "856") (name "Net-(Q12-B)") (class "Default")
      (node (ref "Q12") (pin "1") (pinfunction "B_1") (pintype "passive"))
      (node (ref "R63") (pin "1") (pinfunction "1_1") (pintype "passive"))
    )
    (net (code "857") (name "Net-(Q12-C)") (class "Default")
      (node (ref "Q12") (pin "2") (pinfunction "C_2") (pintype "passive"))
      (node (ref "R14") (pin "2") (pinfunction "2_2") (pintype "passive"))
      (node (ref "SJMP1") (pin "2") (pinfunction "2_2") (pintype "passive"))
    )
    (net (code "858") (name "Net-(Q13-D)") (class "Default")
      (node (ref "Q13") (pin "3") (pinfunction "D_3") (pintype "passive"))
      (node (ref "R63") (pin "2") (pinfunction "2_2") (pintype "passive"))
    )
    (net (code "859") (name "Net-(Q14-B)") (class "Default")
      (node (ref "Q14") (pin "1") (pinfunction "B_1") (pintype "passive"))
      (node (ref "R90") (pin "2") (pinfunction "2_2") (pintype "passive"))
    )
    (net (code "860") (name "Net-(Q15-B)") (class "Default")
      (node (ref "Q15") (pin "1") (pinfunction "B_1") (pintype "passive"))
      (node (ref "Q15") (pin "2") (pinfunction "C_2") (pintype "passive"))
      (node (ref "Q16") (pin "1") (pinfunction "B_1") (pintype "passive"))
      (node (ref "R154") (pin "1") (pinfunction "1_1") (pintype "passive"))
      (node (ref "R85") (pin "1") (pinfunction "1_1") (pintype "passive"))
      (node (ref "X6") (pin "2") (pinfunction "S_2") (pintype "passive"))
    )
    (net (code "861") (name "Net-(Q15-E)") (class "Default")
      (node (ref "Q15") (pin "3") (pinfunction "E_3") (pintype "passive"))
      (node (ref "R91") (pin "2") (pinfunction "2_2") (pintype "passive"))
    )
    (net (code "862") (name "Net-(Q16-E)") (class "Default")
      (node (ref "Q16") (pin "3") (pinfunction "E_3") (pintype "passive"))
      (node (ref "R92") (pin "2") (pinfunction "2_2") (pintype "passive"))
    )
    (net (code "863") (name "Net-(Q17-B)") (class "Default")
      (node (ref "Q17") (pin "1") (pinfunction "B_1") (pintype "passive"))
      (node (ref "R83") (pin "1") (pinfunction "1_1") (pintype "passive"))
    )
    (net (code "864") (name "Net-(Q18-B)") (class "Default")
      (node (ref "Q18") (pin "1") (pinfunction "B_1") (pintype "passive"))
      (node (ref "R159") (pin "1") (pinfunction "1_1") (pintype "passive"))
      (node (ref "R94") (pin "2") (pinfunction "2_2") (pintype "passive"))
    )
    (net (code "865") (name "Net-(Q18-E)") (class "Default")
      (node (ref "Q18") (pin "3") (pinfunction "E_3") (pintype "passive"))
      (node (ref "R158") (pin "1") (pinfunction "1_1") (pintype "passive"))
    )
    (net (code "866") (name "Net-(Q19-D)") (class "Default")
      (node (ref "Q19") (pin "3") (pinfunction "D_3") (pintype "passive"))
      (node (ref "R95") (pin "2") (pinfunction "2_2") (pintype "passive"))
    )
    (net (code "867") (name "Net-(Q20-S)") (class "Default")
      (node (ref "Q20") (pin "2") (pinfunction "S_2") (pintype "passive"))
      (node (ref "R160") (pin "2") (pinfunction "2_2") (pintype "passive"))
    )
    (net (code "868") (name "Net-(Q22-B)") (class "Default")
      (node (ref "Q22") (pin "1") (pinfunction "B_1") (pintype "passive"))
      (node (ref "R162") (pin "1") (pinfunction "1_1") (pintype "passive"))
    )
    (net (code "869") (name "Net-(Q22-C)") (class "Default")
      (node (ref "Q22") (pin "2") (pinfunction "C_2") (pintype "passive"))
      (node (ref "R69") (pin "2") (pinfunction "2_2") (pintype "passive"))
      (node (ref "SJMP2") (pin "2") (pinfunction "2_2") (pintype "passive"))
    )
    (net (code "870") (name "Net-(Q23-D)") (class "Default")
      (node (ref "Q23") (pin "3") (pinfunction "D_3") (pintype "passive"))
      (node (ref "R162") (pin "2") (pinfunction "2_2") (pintype "passive"))
    )
    (net (code "871") (name "Net-(Q24-B)") (class "Default")
      (node (ref "Q24") (pin "1") (pinfunction "B_1") (pintype "passive"))
      (node (ref "R189") (pin "2") (pinfunction "2_2") (pintype "passive"))
    )
    (net (code "872") (name "Net-(Q25-B)") (class "Default")
      (node (ref "Q25") (pin "1") (pinfunction "B_1") (pintype "passive"))
      (node (ref "Q25") (pin "2") (pinfunction "C_2") (pintype "passive"))
      (node (ref "Q26") (pin "1") (pinfunction "B_1") (pintype "passive"))
      (node (ref "R184") (pin "1") (pinfunction "1_1") (pintype "passive"))
      (node (ref "R209") (pin "1") (pinfunction "1_1") (pintype "passive"))
      (node (ref "X9") (pin "2") (pinfunction "S_2") (pintype "passive"))
    )
    (net (code "873") (name "Net-(Q25-E)") (class "Default")
      (node (ref "Q25") (pin "3") (pinfunction "E_3") (pintype "passive"))
      (node (ref "R190") (pin "2") (pinfunction "2_2") (pintype "passive"))
    )
    (net (code "874") (name "Net-(Q26-E)") (class "Default")
      (node (ref "Q26") (pin "3") (pinfunction "E_3") (pintype "passive"))
      (node (ref "R191") (pin "2") (pinfunction "2_2") (pintype "passive"))
    )
    (net (code "875") (name "Net-(Q27-B)") (class "Default")
      (node (ref "Q27") (pin "1") (pinfunction "B_1") (pintype "passive"))
      (node (ref "R182") (pin "1") (pinfunction "1_1") (pintype "passive"))
    )
    (net (code "876") (name "Net-(Q28-B)") (class "Default")
      (node (ref "Q28") (pin "1") (pinfunction "B_1") (pintype "passive"))
      (node (ref "R193") (pin "2") (pinfunction "2_2") (pintype "passive"))
      (node (ref "R214") (pin "1") (pinfunction "1_1") (pintype "passive"))
    )
    (net (code "877") (name "Net-(Q28-E)") (class "Default")
      (node (ref "Q28") (pin "3") (pinfunction "E_3") (pintype "passive"))
      (node (ref "R213") (pin "1") (pinfunction "1_1") (pintype "passive"))
    )
    (net (code "878") (name "Net-(Q29-D)") (class "Default")
      (node (ref "Q29") (pin "3") (pinfunction "D_3") (pintype "passive"))
      (node (ref "R194") (pin "2") (pinfunction "2_2") (pintype "passive"))
    )
    (net (code "879") (name "Net-(Q30-S)") (class "Default")
      (node (ref "Q30") (pin "2") (pinfunction "S_2") (pintype "passive"))
      (node (ref "R215") (pin "2") (pinfunction "2_2") (pintype "passive"))
    )
    (net (code "880") (name "Net-(Q32-B)") (class "Default")
      (node (ref "Q32") (pin "1") (pinfunction "B_1") (pintype "passive"))
      (node (ref "R217") (pin "1") (pinfunction "1_1") (pintype "passive"))
    )
    (net (code "881") (name "Net-(Q32-C)") (class "Default")
      (node (ref "Q32") (pin "2") (pinfunction "C_2") (pintype "passive"))
      (node (ref "R168") (pin "2") (pinfunction "2_2") (pintype "passive"))
      (node (ref "SJMP3") (pin "2") (pinfunction "2_2") (pintype "passive"))
    )
    (net (code "882") (name "Net-(Q33-D)") (class "Default")
      (node (ref "Q33") (pin "3") (pinfunction "D_3") (pintype "passive"))
      (node (ref "R217") (pin "2") (pinfunction "2_2") (pintype "passive"))
    )
    (net (code "883") (name "Net-(Q34-B)") (class "Default")
      (node (ref "Q34") (pin "1") (pinfunction "B_1") (pintype "passive"))
      (node (ref "R244") (pin "2") (pinfunction "2_2") (pintype "passive"))
    )
    (net (code "884") (name "Net-(Q35-B)") (class "Default")
      (node (ref "Q35") (pin "1") (pinfunction "B_1") (pintype "passive"))
      (node (ref "Q35") (pin "2") (pinfunction "C_2") (pintype "passive"))
      (node (ref "Q36") (pin "1") (pinfunction "B_1") (pintype "passive"))
      (node (ref "R239") (pin "1") (pinfunction "1_1") (pintype "passive"))
      (node (ref "R264") (pin "1") (pinfunction "1_1") (pintype "passive"))
      (node (ref "X12") (pin "2") (pinfunction "S_2") (pintype "passive"))
    )
    (net (code "885") (name "Net-(Q35-E)") (class "Default")
      (node (ref "Q35") (pin "3") (pinfunction "E_3") (pintype "passive"))
      (node (ref "R245") (pin "2") (pinfunction "2_2") (pintype "passive"))
    )
    (net (code "886") (name "Net-(Q36-E)") (class "Default")
      (node (ref "Q36") (pin "3") (pinfunction "E_3") (pintype "passive"))
      (node (ref "R246") (pin "2") (pinfunction "2_2") (pintype "passive"))
    )
    (net (code "887") (name "Net-(Q37-B)") (class "Default")
      (node (ref "Q37") (pin "1") (pinfunction "B_1") (pintype "passive"))
      (node (ref "R237") (pin "1") (pinfunction "1_1") (pintype "passive"))
    )
    (net (code "888") (name "Net-(Q38-B)") (class "Default")
      (node (ref "Q38") (pin "1") (pinfunction "B_1") (pintype "passive"))
      (node (ref "R248") (pin "2") (pinfunction "2_2") (pintype "passive"))
      (node (ref "R269") (pin "1") (pinfunction "1_1") (pintype "passive"))
    )
    (net (code "889") (name "Net-(Q38-E)") (class "Default")
      (node (ref "Q38") (pin "3") (pinfunction "E_3") (pintype "passive"))
      (node (ref "R268") (pin "1") (pinfunction "1_1") (pintype "passive"))
    )
    (net (code "890") (name "Net-(Q39-D)") (class "Default")
      (node (ref "Q39") (pin "3") (pinfunction "D_3") (pintype "passive"))
      (node (ref "R249") (pin "2") (pinfunction "2_2") (pintype "passive"))
    )
    (net (code "891") (name "Net-(Q40-S)") (class "Default")
      (node (ref "Q40") (pin "2") (pinfunction "S_2") (pintype "passive"))
      (node (ref "R270") (pin "2") (pinfunction "2_2") (pintype "passive"))
    )
    (net (code "892") (name "Net-(Q42-B)") (class "Default")
      (node (ref "Q42") (pin "1") (pinfunction "B_1") (pintype "passive"))
      (node (ref "R272") (pin "1") (pinfunction "1_1") (pintype "passive"))
    )
    (net (code "893") (name "Net-(Q42-C)") (class "Default")
      (node (ref "Q42") (pin "2") (pinfunction "C_2") (pintype "passive"))
      (node (ref "R223") (pin "2") (pinfunction "2_2") (pintype "passive"))
      (node (ref "SJMP4") (pin "2") (pinfunction "2_2") (pintype "passive"))
    )
    (net (code "894") (name "Net-(Q43-D)") (class "Default")
      (node (ref "Q43") (pin "3") (pinfunction "D_3") (pintype "passive"))
      (node (ref "R272") (pin "2") (pinfunction "2_2") (pintype "passive"))
    )
    (net (code "895") (name "Net-(Q44-B)") (class "Default")
      (node (ref "Q44") (pin "1") (pinfunction "B_1") (pintype "passive"))
      (node (ref "R299") (pin "2") (pinfunction "2_2") (pintype "passive"))
    )
    (net (code "896") (name "Net-(Q45-B)") (class "Default")
      (node (ref "Q45") (pin "1") (pinfunction "B_1") (pintype "passive"))
      (node (ref "Q45") (pin "2") (pinfunction "C_2") (pintype "passive"))
      (node (ref "Q46") (pin "1") (pinfunction "B_1") (pintype "passive"))
      (node (ref "R294") (pin "1") (pinfunction "1_1") (pintype "passive"))
      (node (ref "R319") (pin "1") (pinfunction "1_1") (pintype "passive"))
      (node (ref "X15") (pin "2") (pinfunction "S_2") (pintype "passive"))
    )
    (net (code "897") (name "Net-(Q45-E)") (class "Default")
      (node (ref "Q45") (pin "3") (pinfunction "E_3") (pintype "passive"))
      (node (ref "R300") (pin "2") (pinfunction "2_2") (pintype "passive"))
    )
    (net (code "898") (name "Net-(Q46-E)") (class "Default")
      (node (ref "Q46") (pin "3") (pinfunction "E_3") (pintype "passive"))
      (node (ref "R301") (pin "2") (pinfunction "2_2") (pintype "passive"))
    )
    (net (code "899") (name "Net-(Q47-B)") (class "Default")
      (node (ref "Q47") (pin "1") (pinfunction "B_1") (pintype "passive"))
      (node (ref "R292") (pin "1") (pinfunction "1_1") (pintype "passive"))
    )
    (net (code "900") (name "Net-(Q48-B)") (class "Default")
      (node (ref "Q48") (pin "1") (pinfunction "B_1") (pintype "passive"))
      (node (ref "R303") (pin "2") (pinfunction "2_2") (pintype "passive"))
      (node (ref "R324") (pin "1") (pinfunction "1_1") (pintype "passive"))
    )
    (net (code "901") (name "Net-(Q48-E)") (class "Default")
      (node (ref "Q48") (pin "3") (pinfunction "E_3") (pintype "passive"))
      (node (ref "R323") (pin "1") (pinfunction "1_1") (pintype "passive"))
    )
    (net (code "902") (name "Net-(Q49-D)") (class "Default")
      (node (ref "Q49") (pin "3") (pinfunction "D_3") (pintype "passive"))
      (node (ref "R304") (pin "2") (pinfunction "2_2") (pintype "passive"))
    )
    (net (code "903") (name "Net-(Q50-S)") (class "Default")
      (node (ref "Q50") (pin "2") (pinfunction "S_2") (pintype "passive"))
      (node (ref "R325") (pin "2") (pinfunction "2_2") (pintype "passive"))
    )
    (net (code "904") (name "Net-(Q52-B)") (class "Default")
      (node (ref "Q52") (pin "1") (pinfunction "B_1") (pintype "passive"))
      (node (ref "R327") (pin "1") (pinfunction "1_1") (pintype "passive"))
    )
    (net (code "905") (name "Net-(Q52-C)") (class "Default")
      (node (ref "Q52") (pin "2") (pinfunction "C_2") (pintype "passive"))
      (node (ref "R278") (pin "2") (pinfunction "2_2") (pintype "passive"))
      (node (ref "SJMP5") (pin "2") (pinfunction "2_2") (pintype "passive"))
    )
    (net (code "906") (name "Net-(Q53-D)") (class "Default")
      (node (ref "Q53") (pin "3") (pinfunction "D_3") (pintype "passive"))
      (node (ref "R327") (pin "2") (pinfunction "2_2") (pintype "passive"))
    )
    (net (code "907") (name "Net-(Q54-B)") (class "Default")
      (node (ref "Q54") (pin "1") (pinfunction "B_1") (pintype "passive"))
      (node (ref "R295") (pin "2") (pinfunction "2_2") (pintype "passive"))
    )
    (net (code "908") (name "Net-(Q55-B)") (class "Default")
      (node (ref "Q55") (pin "1") (pinfunction "B_1") (pintype "passive"))
      (node (ref "Q55") (pin "2") (pinfunction "C_2") (pintype "passive"))
      (node (ref "Q56") (pin "1") (pinfunction "B_1") (pintype "passive"))
      (node (ref "R243") (pin "1") (pinfunction "1_1") (pintype "passive"))
      (node (ref "R346") (pin "1") (pinfunction "1_1") (pintype "passive"))
      (node (ref "X18") (pin "2") (pinfunction "S_2") (pintype "passive"))
    )
    (net (code "909") (name "Net-(Q55-E)") (class "Default")
      (node (ref "Q55") (pin "3") (pinfunction "E_3") (pintype "passive"))
      (node (ref "R297") (pin "2") (pinfunction "2_2") (pintype "passive"))
    )
    (net (code "910") (name "Net-(Q56-E)") (class "Default")
      (node (ref "Q56") (pin "3") (pinfunction "E_3") (pintype "passive"))
      (node (ref "R298") (pin "2") (pinfunction "2_2") (pintype "passive"))
    )
    (net (code "911") (name "Net-(Q57-B)") (class "Default")
      (node (ref "Q57") (pin "1") (pinfunction "B_1") (pintype "passive"))
      (node (ref "R240") (pin "1") (pinfunction "1_1") (pintype "passive"))
    )
    (net (code "912") (name "Net-(Q58-B)") (class "Default")
      (node (ref "Q58") (pin "1") (pinfunction "B_1") (pintype "passive"))
      (node (ref "R331") (pin "2") (pinfunction "2_2") (pintype "passive"))
      (node (ref "R351") (pin "1") (pinfunction "1_1") (pintype "passive"))
    )
    (net (code "913") (name "Net-(Q58-E)") (class "Default")
      (node (ref "Q58") (pin "3") (pinfunction "E_3") (pintype "passive"))
      (node (ref "R350") (pin "1") (pinfunction "1_1") (pintype "passive"))
    )
    (net (code "914") (name "Net-(Q59-D)") (class "Default")
      (node (ref "Q59") (pin "3") (pinfunction "D_3") (pintype "passive"))
      (node (ref "R332") (pin "2") (pinfunction "2_2") (pintype "passive"))
    )
    (net (code "915") (name "Net-(Q60-S)") (class "Default")
      (node (ref "Q60") (pin "2") (pinfunction "S_2") (pintype "passive"))
      (node (ref "R352") (pin "2") (pinfunction "2_2") (pintype "passive"))
    )
    (net (code "916") (name "Net-(Q62-B)") (class "Default")
      (node (ref "Q62") (pin "1") (pinfunction "B_1") (pintype "passive"))
      (node (ref "R354") (pin "1") (pinfunction "1_1") (pintype "passive"))
    )
    (net (code "917") (name "Net-(Q62-C)") (class "Default")
      (node (ref "Q62") (pin "2") (pinfunction "C_2") (pintype "passive"))
      (node (ref "R34") (pin "2") (pinfunction "2_2") (pintype "passive"))
      (node (ref "SJMP6") (pin "2") (pinfunction "2_2") (pintype "passive"))
    )
    (net (code "918") (name "Net-(Q63-D)") (class "Default")
      (node (ref "Q63") (pin "3") (pinfunction "D_3") (pintype "passive"))
      (node (ref "R354") (pin "2") (pinfunction "2_2") (pintype "passive"))
    )
    (net (code "919") (name "Net-(Q64-B)") (class "Default")
      (node (ref "Q64") (pin "1") (pinfunction "B_1") (pintype "passive"))
      (node (ref "R378") (pin "2") (pinfunction "2_2") (pintype "passive"))
    )
    (net (code "920") (name "Net-(Q65-B)") (class "Default")
      (node (ref "Q65") (pin "1") (pinfunction "B_1") (pintype "passive"))
      (node (ref "Q65") (pin "2") (pinfunction "C_2") (pintype "passive"))
      (node (ref "Q66") (pin "1") (pinfunction "B_1") (pintype "passive"))
      (node (ref "R376") (pin "1") (pinfunction "1_1") (pintype "passive"))
      (node (ref "R397") (pin "1") (pinfunction "1_1") (pintype "passive"))
      (node (ref "X21") (pin "2") (pinfunction "S_2") (pintype "passive"))
    )
    (net (code "921") (name "Net-(Q65-E)") (class "Default")
      (node (ref "Q65") (pin "3") (pinfunction "E_3") (pintype "passive"))
      (node (ref "R379") (pin "2") (pinfunction "2_2") (pintype "passive"))
    )
    (net (code "922") (name "Net-(Q66-E)") (class "Default")
      (node (ref "Q66") (pin "3") (pinfunction "E_3") (pintype "passive"))
      (node (ref "R380") (pin "2") (pinfunction "2_2") (pintype "passive"))
    )
    (net (code "923") (name "Net-(Q67-B)") (class "Default")
      (node (ref "Q67") (pin "1") (pinfunction "B_1") (pintype "passive"))
      (node (ref "R374") (pin "1") (pinfunction "1_1") (pintype "passive"))
    )
    (net (code "924") (name "Net-(Q68-B)") (class "Default")
      (node (ref "Q68") (pin "1") (pinfunction "B_1") (pintype "passive"))
      (node (ref "R382") (pin "2") (pinfunction "2_2") (pintype "passive"))
      (node (ref "R402") (pin "1") (pinfunction "1_1") (pintype "passive"))
    )
    (net (code "925") (name "Net-(Q68-E)") (class "Default")
      (node (ref "Q68") (pin "3") (pinfunction "E_3") (pintype "passive"))
      (node (ref "R401") (pin "1") (pinfunction "1_1") (pintype "passive"))
    )
    (net (code "926") (name "Net-(Q69-D)") (class "Default")
      (node (ref "Q69") (pin "3") (pinfunction "D_3") (pintype "passive"))
      (node (ref "R383") (pin "2") (pinfunction "2_2") (pintype "passive"))
    )
    (net (code "927") (name "Net-(Q70-S)") (class "Default")
      (node (ref "Q70") (pin "2") (pinfunction "S_2") (pintype "passive"))
      (node (ref "R403") (pin "2") (pinfunction "2_2") (pintype "passive"))
    )
    (net (code "928") (name "Net-(Q72-B)") (class "Default")
      (node (ref "Q72") (pin "1") (pinfunction "B_1") (pintype "passive"))
      (node (ref "R405") (pin "1") (pinfunction "1_1") (pintype "passive"))
    )
    (net (code "929") (name "Net-(Q72-C)") (class "Default")
      (node (ref "Q72") (pin "2") (pinfunction "C_2") (pintype "passive"))
      (node (ref "R360") (pin "2") (pinfunction "2_2") (pintype "passive"))
      (node (ref "SJMP7") (pin "2") (pinfunction "2_2") (pintype "passive"))
    )
    (net (code "930") (name "Net-(Q73-D)") (class "Default")
      (node (ref "Q73") (pin "3") (pinfunction "D_3") (pintype "passive"))
      (node (ref "R405") (pin "2") (pinfunction "2_2") (pintype "passive"))
    )
    (net (code "931") (name "Net-(Q74-B)") (class "Default")
      (node (ref "Q74") (pin "1") (pinfunction "B_1") (pintype "passive"))
      (node (ref "R429") (pin "2") (pinfunction "2_2") (pintype "passive"))
    )
    (net (code "932") (name "Net-(Q75-B)") (class "Default")
      (node (ref "Q75") (pin "1") (pinfunction "B_1") (pintype "passive"))
      (node (ref "Q75") (pin "2") (pinfunction "C_2") (pintype "passive"))
      (node (ref "Q76") (pin "1") (pinfunction "B_1") (pintype "passive"))
      (node (ref "R427") (pin "1") (pinfunction "1_1") (pintype "passive"))
      (node (ref "R448") (pin "1") (pinfunction "1_1") (pintype "passive"))
      (node (ref "X24") (pin "2") (pinfunction "S_2") (pintype "passive"))
    )
    (net (code "933") (name "Net-(Q75-E)") (class "Default")
      (node (ref "Q75") (pin "3") (pinfunction "E_3") (pintype "passive"))
      (node (ref "R430") (pin "2") (pinfunction "2_2") (pintype "passive"))
    )
    (net (code "934") (name "Net-(Q76-E)") (class "Default")
      (node (ref "Q76") (pin "3") (pinfunction "E_3") (pintype "passive"))
      (node (ref "R431") (pin "2") (pinfunction "2_2") (pintype "passive"))
    )
    (net (code "935") (name "Net-(Q77-B)") (class "Default")
      (node (ref "Q77") (pin "1") (pinfunction "B_1") (pintype "passive"))
      (node (ref "R425") (pin "1") (pinfunction "1_1") (pintype "passive"))
    )
    (net (code "936") (name "Net-(Q78-B)") (class "Default")
      (node (ref "Q78") (pin "1") (pinfunction "B_1") (pintype "passive"))
      (node (ref "R433") (pin "2") (pinfunction "2_2") (pintype "passive"))
      (node (ref "R453") (pin "1") (pinfunction "1_1") (pintype "passive"))
    )
    (net (code "937") (name "Net-(Q78-E)") (class "Default")
      (node (ref "Q78") (pin "3") (pinfunction "E_3") (pintype "passive"))
      (node (ref "R452") (pin "1") (pinfunction "1_1") (pintype "passive"))
    )
    (net (code "938") (name "Net-(Q79-D)") (class "Default")
      (node (ref "Q79") (pin "3") (pinfunction "D_3") (pintype "passive"))
      (node (ref "R434") (pin "2") (pinfunction "2_2") (pintype "passive"))
    )
    (net (code "939") (name "Net-(Q80-S)") (class "Default")
      (node (ref "Q80") (pin "2") (pinfunction "S_2") (pintype "passive"))
      (node (ref "R454") (pin "2") (pinfunction "2_2") (pintype "passive"))
    )
    (net (code "940") (name "Net-(Q82-B)") (class "Default")
      (node (ref "Q82") (pin "1") (pinfunction "B_1") (pintype "passive"))
      (node (ref "R456") (pin "1") (pinfunction "1_1") (pintype "passive"))
    )
    (net (code "941") (name "Net-(Q82-C)") (class "Default")
      (node (ref "Q82") (pin "2") (pinfunction "C_2") (pintype "passive"))
      (node (ref "R411") (pin "2") (pinfunction "2_2") (pintype "passive"))
      (node (ref "SJMP8") (pin "2") (pinfunction "2_2") (pintype "passive"))
    )
    (net (code "942") (name "Net-(Q83-D)") (class "Default")
      (node (ref "Q83") (pin "3") (pinfunction "D_3") (pintype "passive"))
      (node (ref "R456") (pin "2") (pinfunction "2_2") (pintype "passive"))
    )
    (net (code "943") (name "Net-(Q84-B)") (class "Default")
      (node (ref "Q84") (pin "1") (pinfunction "B_1") (pintype "passive"))
      (node (ref "R480") (pin "2") (pinfunction "2_2") (pintype "passive"))
    )
    (net (code "944") (name "Net-(Q85-B)") (class "Default")
      (node (ref "Q85") (pin "1") (pinfunction "B_1") (pintype "passive"))
      (node (ref "Q85") (pin "2") (pinfunction "C_2") (pintype "passive"))
      (node (ref "Q86") (pin "1") (pinfunction "B_1") (pintype "passive"))
      (node (ref "R478") (pin "1") (pinfunction "1_1") (pintype "passive"))
      (node (ref "R499") (pin "1") (pinfunction "1_1") (pintype "passive"))
      (node (ref "X27") (pin "2") (pinfunction "S_2") (pintype "passive"))
    )
    (net (code "945") (name "Net-(Q85-E)") (class "Default")
      (node (ref "Q85") (pin "3") (pinfunction "E_3") (pintype "passive"))
      (node (ref "R481") (pin "2") (pinfunction "2_2") (pintype "passive"))
    )
    (net (code "946") (name "Net-(Q86-E)") (class "Default")
      (node (ref "Q86") (pin "3") (pinfunction "E_3") (pintype "passive"))
      (node (ref "R482") (pin "2") (pinfunction "2_2") (pintype "passive"))
    )
    (net (code "947") (name "Net-(Q87-B)") (class "Default")
      (node (ref "Q87") (pin "1") (pinfunction "B_1") (pintype "passive"))
      (node (ref "R476") (pin "1") (pinfunction "1_1") (pintype "passive"))
    )
    (net (code "948") (name "Net-(Q88-B)") (class "Default")
      (node (ref "Q88") (pin "1") (pinfunction "B_1") (pintype "passive"))
      (node (ref "R484") (pin "2") (pinfunction "2_2") (pintype "passive"))
      (node (ref "R504") (pin "1") (pinfunction "1_1") (pintype "passive"))
    )
    (net (code "949") (name "Net-(Q88-E)") (class "Default")
      (node (ref "Q88") (pin "3") (pinfunction "E_3") (pintype "passive"))
      (node (ref "R503") (pin "1") (pinfunction "1_1") (pintype "passive"))
    )
    (net (code "950") (name "Net-(Q89-D)") (class "Default")
      (node (ref "Q89") (pin "3") (pinfunction "D_3") (pintype "passive"))
      (node (ref "R485") (pin "2") (pinfunction "2_2") (pintype "passive"))
    )
    (net (code "951") (name "Net-(Q90-S)") (class "Default")
      (node (ref "Q90") (pin "2") (pinfunction "S_2") (pintype "passive"))
      (node (ref "R505") (pin "2") (pinfunction "2_2") (pintype "passive"))
    )
    (net (code "952") (name "Net-(Q92-B)") (class "Default")
      (node (ref "Q92") (pin "1") (pinfunction "B_1") (pintype "passive"))
      (node (ref "R507") (pin "1") (pinfunction "1_1") (pintype "passive"))
    )
    (net (code "953") (name "Net-(Q92-C)") (class "Default")
      (node (ref "Q92") (pin "2") (pinfunction "C_2") (pintype "passive"))
      (node (ref "R462") (pin "2") (pinfunction "2_2") (pintype "passive"))
      (node (ref "SJMP9") (pin "2") (pinfunction "2_2") (pintype "passive"))
    )
    (net (code "954") (name "Net-(Q93-D)") (class "Default")
      (node (ref "Q93") (pin "3") (pinfunction "D_3") (pintype "passive"))
      (node (ref "R507") (pin "2") (pinfunction "2_2") (pintype "passive"))
    )
    (net (code "955") (name "Net-(Q94-B)") (class "Default")
      (node (ref "Q94") (pin "1") (pinfunction "B_1") (pintype "passive"))
      (node (ref "R531") (pin "2") (pinfunction "2_2") (pintype "passive"))
    )
    (net (code "956") (name "Net-(Q95-B)") (class "Default")
      (node (ref "Q95") (pin "1") (pinfunction "B_1") (pintype "passive"))
      (node (ref "Q95") (pin "2") (pinfunction "C_2") (pintype "passive"))
      (node (ref "Q96") (pin "1") (pinfunction "B_1") (pintype "passive"))
      (node (ref "R529") (pin "1") (pinfunction "1_1") (pintype "passive"))
      (node (ref "R550") (pin "1") (pinfunction "1_1") (pintype "passive"))
      (node (ref "X30") (pin "2") (pinfunction "S_2") (pintype "passive"))
    )
    (net (code "957") (name "Net-(Q95-E)") (class "Default")
      (node (ref "Q95") (pin "3") (pinfunction "E_3") (pintype "passive"))
      (node (ref "R532") (pin "2") (pinfunction "2_2") (pintype "passive"))
    )
    (net (code "958") (name "Net-(Q96-E)") (class "Default")
      (node (ref "Q96") (pin "3") (pinfunction "E_3") (pintype "passive"))
      (node (ref "R533") (pin "2") (pinfunction "2_2") (pintype "passive"))
    )
    (net (code "959") (name "Net-(Q97-B)") (class "Default")
      (node (ref "Q97") (pin "1") (pinfunction "B_1") (pintype "passive"))
      (node (ref "R527") (pin "1") (pinfunction "1_1") (pintype "passive"))
    )
    (net (code "960") (name "Net-(Q98-B)") (class "Default")
      (node (ref "Q98") (pin "1") (pinfunction "B_1") (pintype "passive"))
      (node (ref "R535") (pin "2") (pinfunction "2_2") (pintype "passive"))
      (node (ref "R555") (pin "1") (pinfunction "1_1") (pintype "passive"))
    )
    (net (code "961") (name "Net-(Q98-E)") (class "Default")
      (node (ref "Q98") (pin "3") (pinfunction "E_3") (pintype "passive"))
      (node (ref "R554") (pin "1") (pinfunction "1_1") (pintype "passive"))
    )
    (net (code "962") (name "Net-(Q99-D)") (class "Default")
      (node (ref "Q99") (pin "3") (pinfunction "D_3") (pintype "passive"))
      (node (ref "R536") (pin "2") (pinfunction "2_2") (pintype "passive"))
    )
    (net (code "963") (name "Net-(Q100-S)") (class "Default")
      (node (ref "Q100") (pin "2") (pinfunction "S_2") (pintype "passive"))
      (node (ref "R556") (pin "2") (pinfunction "2_2") (pintype "passive"))
    )
    (net (code "964") (name "Net-(Q101-B)") (class "Default")
      (node (ref "Q101") (pin "1") (pinfunction "B_1") (pintype "passive"))
      (node (ref "Q102") (pin "1") (pinfunction "B_1") (pintype "passive"))
      (node (ref "Q102") (pin "2") (pinfunction "C_2") (pintype "passive"))
      (node (ref "R101") (pin "1") (pinfunction "1_1") (pintype "passive"))
      (node (ref "R103") (pin "1") (pinfunction "1_1") (pintype "passive"))
      (node (ref "X102") (pin "2") (pinfunction "S_2") (pintype "passive"))
    )
    (net (code "965") (name "Net-(Q101-E)") (class "Default")
      (node (ref "Q101") (pin "3") (pinfunction "E_3") (pintype "passive"))
      (node (ref "R102") (pin "2") (pinfunction "2_2") (pintype "passive"))
    )
    (net (code "966") (name "Net-(Q102-E)") (class "Default")
      (node (ref "Q102") (pin "3") (pinfunction "E_3") (pintype "passive"))
      (node (ref "R106") (pin "2") (pinfunction "2_2") (pintype "passive"))
    )
    (net (code "967") (name "Net-(Q103-B)") (class "Default")
      (node (ref "Q103") (pin "1") (pinfunction "B_1") (pintype "passive"))
      (node (ref "R116") (pin "2") (pinfunction "2_2") (pintype "passive"))
      (node (ref "R6") (pin "1") (pinfunction "1_1") (pintype "passive"))
    )
    (net (code "968") (name "Net-(Q103-E)") (class "Default")
      (node (ref "Q103") (pin "3") (pinfunction "E_3") (pintype "passive"))
      (node (ref "R5") (pin "1") (pinfunction "1_1") (pintype "passive"))
    )
    (net (code "969") (name "Net-(Q104-B)") (class "Default")
      (node (ref "Q104") (pin "1") (pinfunction "B_1") (pintype "passive"))
      (node (ref "R128") (pin "2") (pinfunction "2_2") (pintype "passive"))
    )
    (net (code "970") (name "Net-(Q105-B)") (class "Default")
      (node (ref "Q105") (pin "1") (pinfunction "B_1") (pintype "passive"))
      (node (ref "R126") (pin "1") (pinfunction "1_1") (pintype "passive"))
    )
    (net (code "971") (name "Net-(Q106-S)") (class "Default")
      (node (ref "Q106") (pin "2") (pinfunction "S_2") (pintype "passive"))
      (node (ref "R4") (pin "2") (pinfunction "2_2") (pintype "passive"))
    )
    (net (code "972") (name "Net-(Q107-D)") (class "Default")
      (node (ref "Q107") (pin "3") (pinfunction "D_3") (pintype "passive"))
      (node (ref "R138") (pin "2") (pinfunction "2_2") (pintype "passive"))
    )
    (net (code "973") (name "Net-(Q109-B)") (class "Default")
      (node (ref "Q109") (pin "1") (pinfunction "B_1") (pintype "passive"))
      (node (ref "R558") (pin "1") (pinfunction "1_1") (pintype "passive"))
    )
    (net (code "974") (name "Net-(Q109-C)") (class "Default")
      (node (ref "Q109") (pin "2") (pinfunction "C_2") (pintype "passive"))
      (node (ref "R513") (pin "2") (pinfunction "2_2") (pintype "passive"))
      (node (ref "SJMP10") (pin "2") (pinfunction "2_2") (pintype "passive"))
    )
    (net (code "975") (name "Net-(Q110-D)") (class "Default")
      (node (ref "Q110") (pin "3") (pinfunction "D_3") (pintype "passive"))
      (node (ref "R558") (pin "2") (pinfunction "2_2") (pintype "passive"))
    )
    (net (code "976") (name "Net-(Q111-B)") (class "Default")
      (node (ref "Q111") (pin "1") (pinfunction "B_1") (pintype "passive"))
      (node (ref "R582") (pin "2") (pinfunction "2_2") (pintype "passive"))
    )
    (net (code "977") (name "Net-(Q112-B)") (class "Default")
      (node (ref "Q112") (pin "1") (pinfunction "B_1") (pintype "passive"))
      (node (ref "Q112") (pin "2") (pinfunction "C_2") (pintype "passive"))
      (node (ref "Q113") (pin "1") (pinfunction "B_1") (pintype "passive"))
      (node (ref "R580") (pin "1") (pinfunction "1_1") (pintype "passive"))
      (node (ref "R601") (pin "1") (pinfunction "1_1") (pintype "passive"))
      (node (ref "X33") (pin "2") (pinfunction "S_2") (pintype "passive"))
    )
    (net (code "978") (name "Net-(Q112-E)") (class "Default")
      (node (ref "Q112") (pin "3") (pinfunction "E_3") (pintype "passive"))
      (node (ref "R583") (pin "2") (pinfunction "2_2") (pintype "passive"))
    )
    (net (code "979") (name "Net-(Q113-E)") (class "Default")
      (node (ref "Q113") (pin "3") (pinfunction "E_3") (pintype "passive"))
      (node (ref "R584") (pin "2") (pinfunction "2_2") (pintype "passive"))
    )
    (net (code "980") (name "Net-(Q114-B)") (class "Default")
      (node (ref "Q114") (pin "1") (pinfunction "B_1") (pintype "passive"))
      (node (ref "R578") (pin "1") (pinfunction "1_1") (pintype "passive"))
    )
    (net (code "981") (name "Net-(Q115-B)") (class "Default")
      (node (ref "Q115") (pin "1") (pinfunction "B_1") (pintype "passive"))
      (node (ref "R586") (pin "2") (pinfunction "2_2") (pintype "passive"))
      (node (ref "R606") (pin "1") (pinfunction "1_1") (pintype "passive"))
    )
    (net (code "982") (name "Net-(Q115-E)") (class "Default")
      (node (ref "Q115") (pin "3") (pinfunction "E_3") (pintype "passive"))
      (node (ref "R605") (pin "1") (pinfunction "1_1") (pintype "passive"))
    )
    (net (code "983") (name "Net-(Q116-D)") (class "Default")
      (node (ref "Q116") (pin "3") (pinfunction "D_3") (pintype "passive"))
      (node (ref "R587") (pin "2") (pinfunction "2_2") (pintype "passive"))
    )
    (net (code "984") (name "Net-(Q117-S)") (class "Default")
      (node (ref "Q117") (pin "2") (pinfunction "S_2") (pintype "passive"))
      (node (ref "R607") (pin "2") (pinfunction "2_2") (pintype "passive"))
    )
    (net (code "985") (name "Net-(Q119-B)") (class "Default")
      (node (ref "Q119") (pin "1") (pinfunction "B_1") (pintype "passive"))
      (node (ref "R609") (pin "1") (pinfunction "1_1") (pintype "passive"))
    )
    (net (code "986") (name "Net-(Q119-C)") (class "Default")
      (node (ref "Q119") (pin "2") (pinfunction "C_2") (pintype "passive"))
      (node (ref "R564") (pin "2") (pinfunction "2_2") (pintype "passive"))
      (node (ref "SJMP11") (pin "2") (pinfunction "2_2") (pintype "passive"))
    )
    (net (code "987") (name "Net-(Q120-D)") (class "Default")
      (node (ref "Q120") (pin "3") (pinfunction "D_3") (pintype "passive"))
      (node (ref "R609") (pin "2") (pinfunction "2_2") (pintype "passive"))
    )
    (net (code "988") (name "Net-(R14-Pad1)") (class "Default")
      (node (ref "R14") (pin "1") (pinfunction "1_1") (pintype "passive"))
      (node (ref "R7") (pin "2") (pinfunction "2_2") (pintype "passive"))
    )
    (net (code "989") (name "Net-(R18-Pad2)") (class "Default")
      (node (ref "R18") (pin "2") (pinfunction "2_2") (pintype "passive"))
      (node (ref "X1") (pin "22") (pinfunction "22_22") (pintype "passive"))
    )
    (net (code "990") (name "Net-(R31-Pad2)") (class "Default")
      (node (ref "R31") (pin "2") (pinfunction "2_2") (pintype "passive"))
      (node (ref "R34") (pin "1") (pinfunction "1_1") (pintype "passive"))
    )
    (net (code "991") (name "Net-(R32-Pad1)") (class "Default")
      (node (ref "R32") (pin "1") (pinfunction "1_1") (pintype "passive"))
      (node (ref "X1") (pin "21") (pinfunction "21_21") (pintype "passive"))
    )
    (net (code "992") (name "Net-(R44-Pad2)") (class "Default")
      (node (ref "R44") (pin "2") (pinfunction "2_2") (pintype "passive"))
      (node (ref "X1") (pin "16") (pinfunction "16_16") (pintype "passive"))
    )
    (net (code "993") (name "Net-(R67-Pad2)") (class "Default")
      (node (ref "R67") (pin "2") (pinfunction "2_2") (pintype "passive"))
      (node (ref "R69") (pin "1") (pinfunction "1_1") (pintype "passive"))
    )
    (net (code "994") (name "Net-(R73-Pad2)") (class "Default")
      (node (ref "R73") (pin "2") (pinfunction "2_2") (pintype "passive"))
      (node (ref "X4") (pin "22") (pinfunction "22_22") (pintype "passive"))
    )
    (net (code "995") (name "Net-(R87-Pad1)") (class "Default")
      (node (ref "R87") (pin "1") (pinfunction "1_1") (pintype "passive"))
      (node (ref "X4") (pin "21") (pinfunction "21_21") (pintype "passive"))
    )
    (net (code "996") (name "Net-(R89-Pad2)") (class "Default")
      (node (ref "R89") (pin "2") (pinfunction "2_2") (pintype "passive"))
      (node (ref "X16") (pin "22") (pinfunction "22_22") (pintype "passive"))
    )
    (net (code "997") (name "Net-(R99-Pad2)") (class "Default")
      (node (ref "R99") (pin "2") (pinfunction "2_2") (pintype "passive"))
      (node (ref "X4") (pin "16") (pinfunction "16_16") (pintype "passive"))
    )
    (net (code "998") (name "Net-(R105-Pad2)") (class "Default")
      (node (ref "R105") (pin "2") (pinfunction "2_2") (pintype "passive"))
      (node (ref "X101") (pin "22") (pinfunction "22_22") (pintype "passive"))
    )
    (net (code "999") (name "Net-(R115-Pad1)") (class "Default")
      (node (ref "R115") (pin "1") (pinfunction "1_1") (pintype "passive"))
      (node (ref "X101") (pin "21") (pinfunction "21_21") (pintype "passive"))
    )
    (net (code "1000") (name "Net-(R127-Pad2)") (class "Default")
      (node (ref "R127") (pin "2") (pinfunction "2_2") (pintype "passive"))
      (node (ref "R129") (pin "1") (pinfunction "1_1") (pintype "passive"))
    )
    (net (code "1001") (name "Net-(R140-Pad2)") (class "Default")
      (node (ref "R140") (pin "2") (pinfunction "2_2") (pintype "passive"))
      (node (ref "X101") (pin "16") (pinfunction "16_16") (pintype "passive"))
    )
    (net (code "1002") (name "Net-(R166-Pad2)") (class "Default")
      (node (ref "R166") (pin "2") (pinfunction "2_2") (pintype "passive"))
      (node (ref "R168") (pin "1") (pinfunction "1_1") (pintype "passive"))
    )
    (net (code "1003") (name "Net-(R172-Pad2)") (class "Default")
      (node (ref "R172") (pin "2") (pinfunction "2_2") (pintype "passive"))
      (node (ref "X7") (pin "22") (pinfunction "22_22") (pintype "passive"))
    )
    (net (code "1004") (name "Net-(R186-Pad1)") (class "Default")
      (node (ref "R186") (pin "1") (pinfunction "1_1") (pintype "passive"))
      (node (ref "X7") (pin "21") (pinfunction "21_21") (pintype "passive"))
    )
    (net (code "1005") (name "Net-(R198-Pad2)") (class "Default")
      (node (ref "R198") (pin "2") (pinfunction "2_2") (pintype "passive"))
      (node (ref "X7") (pin "16") (pinfunction "16_16") (pintype "passive"))
    )
    (net (code "1006") (name "Net-(R221-Pad2)") (class "Default")
      (node (ref "R221") (pin "2") (pinfunction "2_2") (pintype "passive"))
      (node (ref "R223") (pin "1") (pinfunction "1_1") (pintype "passive"))
    )
    (net (code "1007") (name "Net-(R227-Pad2)") (class "Default")
      (node (ref "R227") (pin "2") (pinfunction "2_2") (pintype "passive"))
      (node (ref "X10") (pin "22") (pinfunction "22_22") (pintype "passive"))
    )
    (net (code "1008") (name "Net-(R241-Pad1)") (class "Default")
      (node (ref "R241") (pin "1") (pinfunction "1_1") (pintype "passive"))
      (node (ref "X10") (pin "21") (pinfunction "21_21") (pintype "passive"))
    )
    (net (code "1009") (name "Net-(R252-Pad1)") (class "Default")
      (node (ref "R252") (pin "1") (pinfunction "1_1") (pintype "passive"))
      (node (ref "X16") (pin "21") (pinfunction "21_21") (pintype "passive"))
    )
    (net (code "1010") (name "Net-(R253-Pad2)") (class "Default")
      (node (ref "R253") (pin "2") (pinfunction "2_2") (pintype "passive"))
      (node (ref "X10") (pin "16") (pinfunction "16_16") (pintype "passive"))
    )
    (net (code "1011") (name "Net-(R276-Pad2)") (class "Default")
      (node (ref "R276") (pin "2") (pinfunction "2_2") (pintype "passive"))
      (node (ref "R278") (pin "1") (pinfunction "1_1") (pintype "passive"))
    )
    (net (code "1012") (name "Net-(R282-Pad2)") (class "Default")
      (node (ref "R282") (pin "2") (pinfunction "2_2") (pintype "passive"))
      (node (ref "X13") (pin "22") (pinfunction "22_22") (pintype "passive"))
    )
    (net (code "1013") (name "Net-(R296-Pad1)") (class "Default")
      (node (ref "R296") (pin "1") (pinfunction "1_1") (pintype "passive"))
      (node (ref "X13") (pin "21") (pinfunction "21_21") (pintype "passive"))
    )
    (net (code "1014") (name "Net-(R308-Pad2)") (class "Default")
      (node (ref "R308") (pin "2") (pinfunction "2_2") (pintype "passive"))
      (node (ref "X13") (pin "16") (pinfunction "16_16") (pintype "passive"))
    )
    (net (code "1015") (name "Net-(R335-Pad2)") (class "Default")
      (node (ref "R335") (pin "2") (pinfunction "2_2") (pintype "passive"))
      (node (ref "X16") (pin "16") (pinfunction "16_16") (pintype "passive"))
    )
    (net (code "1016") (name "Net-(R358-Pad2)") (class "Default")
      (node (ref "R358") (pin "2") (pinfunction "2_2") (pintype "passive"))
      (node (ref "R360") (pin "1") (pinfunction "1_1") (pintype "passive"))
    )
    (net (code "1017") (name "Net-(R364-Pad2)") (class "Default")
      (node (ref "R364") (pin "2") (pinfunction "2_2") (pintype "passive"))
      (node (ref "X19") (pin "22") (pinfunction "22_22") (pintype "passive"))
    )
    (net (code "1018") (name "Net-(R377-Pad1)") (class "Default")
      (node (ref "R377") (pin "1") (pinfunction "1_1") (pintype "passive"))
      (node (ref "X19") (pin "21") (pinfunction "21_21") (pintype "passive"))
    )
    (net (code "1019") (name "Net-(R386-Pad2)") (class "Default")
      (node (ref "R386") (pin "2") (pinfunction "2_2") (pintype "passive"))
      (node (ref "X19") (pin "16") (pinfunction "16_16") (pintype "passive"))
    )
    (net (code "1020") (name "Net-(R409-Pad2)") (class "Default")
      (node (ref "R409") (pin "2") (pinfunction "2_2") (pintype "passive"))
      (node (ref "R411") (pin "1") (pinfunction "1_1") (pintype "passive"))
    )
    (net (code "1021") (name "Net-(R415-Pad2)") (class "Default")
      (node (ref "R415") (pin "2") (pinfunction "2_2") (pintype "passive"))
      (node (ref "X22") (pin "22") (pinfunction "22_22") (pintype "passive"))
    )
    (net (code "1022") (name "Net-(R428-Pad1)") (class "Default")
      (node (ref "R428") (pin "1") (pinfunction "1_1") (pintype "passive"))
      (node (ref "X22") (pin "21") (pinfunction "21_21") (pintype "passive"))
    )
    (net (code "1023") (name "Net-(R437-Pad2)") (class "Default")
      (node (ref "R437") (pin "2") (pinfunction "2_2") (pintype "passive"))
      (node (ref "X22") (pin "16") (pinfunction "16_16") (pintype "passive"))
    )
    (net (code "1024") (name "Net-(R460-Pad2)") (class "Default")
      (node (ref "R460") (pin "2") (pinfunction "2_2") (pintype "passive"))
      (node (ref "R462") (pin "1") (pinfunction "1_1") (pintype "passive"))
    )
    (net (code "1025") (name "Net-(R466-Pad2)") (class "Default")
      (node (ref "R466") (pin "2") (pinfunction "2_2") (pintype "passive"))
      (node (ref "X25") (pin "22") (pinfunction "22_22") (pintype "passive"))
    )
    (net (code "1026") (name "Net-(R479-Pad1)") (class "Default")
      (node (ref "R479") (pin "1") (pinfunction "1_1") (pintype "passive"))
      (node (ref "X25") (pin "21") (pinfunction "21_21") (pintype "passive"))
    )
    (net (code "1027") (name "Net-(R488-Pad2)") (class "Default")
      (node (ref "R488") (pin "2") (pinfunction "2_2") (pintype "passive"))
      (node (ref "X25") (pin "16") (pinfunction "16_16") (pintype "passive"))
    )
    (net (code "1028") (name "Net-(R511-Pad2)") (class "Default")
      (node (ref "R511") (pin "2") (pinfunction "2_2") (pintype "passive"))
      (node (ref "R513") (pin "1") (pinfunction "1_1") (pintype "passive"))
    )
    (net (code "1029") (name "Net-(R517-Pad2)") (class "Default")
      (node (ref "R517") (pin "2") (pinfunction "2_2") (pintype "passive"))
      (node (ref "X28") (pin "22") (pinfunction "22_22") (pintype "passive"))
    )
    (net (code "1030") (name "Net-(R530-Pad1)") (class "Default")
      (node (ref "R530") (pin "1") (pinfunction "1_1") (pintype "passive"))
      (node (ref "X28") (pin "21") (pinfunction "21_21") (pintype "passive"))
    )
    (net (code "1031") (name "Net-(R539-Pad2)") (class "Default")
      (node (ref "R539") (pin "2") (pinfunction "2_2") (pintype "passive"))
      (node (ref "X28") (pin "16") (pinfunction "16_16") (pintype "passive"))
    )
    (net (code "1032") (name "Net-(R562-Pad2)") (class "Default")
      (node (ref "R562") (pin "2") (pinfunction "2_2") (pintype "passive"))
      (node (ref "R564") (pin "1") (pinfunction "1_1") (pintype "passive"))
    )
    (net (code "1033") (name "Net-(R568-Pad2)") (class "Default")
      (node (ref "R568") (pin "2") (pinfunction "2_2") (pintype "passive"))
      (node (ref "X31") (pin "22") (pinfunction "22_22") (pintype "passive"))
    )
    (net (code "1034") (name "Net-(R581-Pad1)") (class "Default")
      (node (ref "R581") (pin "1") (pinfunction "1_1") (pintype "passive"))
      (node (ref "X31") (pin "21") (pinfunction "21_21") (pintype "passive"))
    )
    (net (code "1035") (name "Net-(R590-Pad2)") (class "Default")
      (node (ref "R590") (pin "2") (pinfunction "2_2") (pintype "passive"))
      (node (ref "X31") (pin "16") (pinfunction "16_16") (pintype "passive"))
    )
    (net (code "1036") (name "V+") (class "Default")
      (node (ref "D1") (pin "1") (pinfunction "+_1") (pintype "passive"))
      (node (ref "D115") (pin "1") (pinfunction "+_1") (pintype "passive"))
      (node (ref "D128") (pin "1") (pinfunction "+_1") (pintype "passive"))
      (node (ref "D141") (pin "1") (pinfunction "+_1") (pintype "passive"))
      (node (ref "D15") (pin "1") (pinfunction "+_1") (pintype "passive"))
      (node (ref "D154") (pin "1") (pinfunction "+_1") (pintype "passive"))
      (node (ref "D29") (pin "1") (pinfunction "+_1") (pintype "passive"))
      (node (ref "D43") (pin "1") (pinfunction "+_1") (pintype "passive"))
      (node (ref "D57") (pin "1") (pinfunction "+_1") (pintype "passive"))
      (node (ref "D71") (pin "1") (pinfunction "+_1") (pintype "passive"))
      (node (ref "D79") (pin "1") (pinfunction "+_1") (pintype "passive"))
      (node (ref "D92") (pin "1") (pinfunction "+_1") (pintype "passive"))
      (node (ref "Q104") (pin "3") (pinfunction "E_3") (pintype "passive"))
      (node (ref "Q105") (pin "3") (pinfunction "E_3") (pintype "passive"))
      (node (ref "Q109") (pin "3") (pinfunction "E_3") (pintype "passive"))
      (node (ref "Q111") (pin "3") (pinfunction "E_3") (pintype "passive"))
      (node (ref "Q114") (pin "3") (pinfunction "E_3") (pintype "passive"))
      (node (ref "Q119") (pin "3") (pinfunction "E_3") (pintype "passive"))
      (node (ref "Q12") (pin "3") (pinfunction "E_3") (pintype "passive"))
      (node (ref "Q14") (pin "3") (pinfunction "E_3") (pintype "passive"))
      (node (ref "Q17") (pin "3") (pinfunction "E_3") (pintype "passive"))
      (node (ref "Q2") (pin "3") (pinfunction "E_3") (pintype "passive"))
      (node (ref "Q22") (pin "3") (pinfunction "E_3") (pintype "passive"))
      (node (ref "Q24") (pin "3") (pinfunction "E_3") (pintype "passive"))
      (node (ref "Q27") (pin "3") (pinfunction "E_3") (pintype "passive"))
      (node (ref "Q32") (pin "3") (pinfunction "E_3") (pintype "passive"))
      (node (ref "Q34") (pin "3") (pinfunction "E_3") (pintype "passive"))
      (node (ref "Q37") (pin "3") (pinfunction "E_3") (pintype "passive"))
      (node (ref "Q4") (pin "3") (pinfunction "E_3") (pintype "passive"))
      (node (ref "Q42") (pin "3") (pinfunction "E_3") (pintype "passive"))
      (node (ref "Q44") (pin "3") (pinfunction "E_3") (pintype "passive"))
      (node (ref "Q47") (pin "3") (pinfunction "E_3") (pintype "passive"))
      (node (ref "Q52") (pin "3") (pinfunction "E_3") (pintype "passive"))
      (node (ref "Q54") (pin "3") (pinfunction "E_3") (pintype "passive"))
      (node (ref "Q57") (pin "3") (pinfunction "E_3") (pintype "passive"))
      (node (ref "Q62") (pin "3") (pinfunction "E_3") (pintype "passive"))
      (node (ref "Q64") (pin "3") (pinfunction "E_3") (pintype "passive"))
      (node (ref "Q67") (pin "3") (pinfunction "E_3") (pintype "passive"))
      (node (ref "Q7") (pin "3") (pinfunction "E_3") (pintype "passive"))
      (node (ref "Q72") (pin "3") (pinfunction "E_3") (pintype "passive"))
      (node (ref "Q74") (pin "3") (pinfunction "E_3") (pintype "passive"))
      (node (ref "Q77") (pin "3") (pinfunction "E_3") (pintype "passive"))
      (node (ref "Q82") (pin "3") (pinfunction "E_3") (pintype "passive"))
      (node (ref "Q84") (pin "3") (pinfunction "E_3") (pintype "passive"))
      (node (ref "Q87") (pin "3") (pinfunction "E_3") (pintype "passive"))
      (node (ref "Q92") (pin "3") (pinfunction "E_3") (pintype "passive"))
      (node (ref "Q94") (pin "3") (pinfunction "E_3") (pintype "passive"))
      (node (ref "Q97") (pin "3") (pinfunction "E_3") (pintype "passive"))
      (node (ref "SJMP") (pin "1") (pinfunction "1_1") (pintype "passive"))
      (node (ref "SJMP1") (pin "1") (pinfunction "1_1") (pintype "passive"))
      (node (ref "SJMP10") (pin "1") (pinfunction "1_1") (pintype "passive"))
      (node (ref "SJMP11") (pin "1") (pinfunction "1_1") (pintype "passive"))
      (node (ref "SJMP2") (pin "1") (pinfunction "1_1") (pintype "passive"))
      (node (ref "SJMP3") (pin "1") (pinfunction "1_1") (pintype "passive"))
      (node (ref "SJMP4") (pin "1") (pinfunction "1_1") (pintype "passive"))
      (node (ref "SJMP5") (pin "1") (pinfunction "1_1") (pintype "passive"))
      (node (ref "SJMP6") (pin "1") (pinfunction "1_1") (pintype "passive"))
      (node (ref "SJMP7") (pin "1") (pinfunction "1_1") (pintype "passive"))
      (node (ref "SJMP8") (pin "1") (pinfunction "1_1") (pintype "passive"))
      (node (ref "SJMP9") (pin "1") (pinfunction "1_1") (pintype "passive"))
      (node (ref "X1") (pin "6") (pinfunction "6_6") (pintype "passive"))
      (node (ref "X10") (pin "6") (pinfunction "6_6") (pintype "passive"))
      (node (ref "X101") (pin "6") (pinfunction "6_6") (pintype "passive"))
      (node (ref "X13") (pin "6") (pinfunction "6_6") (pintype "passive"))
      (node (ref "X16") (pin "6") (pinfunction "6_6") (pintype "passive"))
      (node (ref "X19") (pin "6") (pinfunction "6_6") (pintype "passive"))
      (node (ref "X22") (pin "6") (pinfunction "6_6") (pintype "passive"))
      (node (ref "X25") (pin "6") (pinfunction "6_6") (pintype "passive"))
      (node (ref "X28") (pin "6") (pinfunction "6_6") (pintype "passive"))
      (node (ref "X31") (pin "6") (pinfunction "6_6") (pintype "passive"))
      (node (ref "X4") (pin "6") (pinfunction "6_6") (pintype "passive"))
      (node (ref "X7") (pin "6") (pinfunction "6_6") (pintype "passive"))
    )
    (net (code "1037") (name "VCC") (class "Default")
      (node (ref "6V") (pin "TP") (pinfunction "PP_TP") (pintype "input"))
      (node (ref "6V1") (pin "TP") (pinfunction "PP_TP") (pintype "input"))
      (node (ref "6V10") (pin "TP") (pinfunction "PP_TP") (pintype "input"))
      (node (ref "6V11") (pin "TP") (pinfunction "PP_TP") (pintype "input"))
      (node (ref "6V2") (pin "TP") (pinfunction "PP_TP") (pintype "input"))
      (node (ref "6V3") (pin "TP") (pinfunction "PP_TP") (pintype "input"))
      (node (ref "6V4") (pin "TP") (pinfunction "PP_TP") (pintype "input"))
      (node (ref "6V5") (pin "TP") (pinfunction "PP_TP") (pintype "input"))
      (node (ref "6V6") (pin "TP") (pinfunction "PP_TP") (pintype "input"))
      (node (ref "6V7") (pin "TP") (pinfunction "PP_TP") (pintype "input"))
      (node (ref "6V8") (pin "TP") (pinfunction "PP_TP") (pintype "input"))
      (node (ref "6V9") (pin "TP") (pinfunction "PP_TP") (pintype "input"))
      (node (ref "C104") (pin "1") (pinfunction "1_1") (pintype "passive"))
      (node (ref "C111") (pin "1") (pinfunction "1_1") (pintype "passive"))
      (node (ref "C123") (pin "1") (pinfunction "1_1") (pintype "passive"))
      (node (ref "C135") (pin "1") (pinfunction "1_1") (pintype "passive"))
      (node (ref "C17") (pin "1") (pinfunction "1_1") (pintype "passive"))
      (node (ref "C29") (pin "1") (pinfunction "1_1") (pintype "passive"))
      (node (ref "C4") (pin "1") (pinfunction "1_1") (pintype "passive"))
      (node (ref "C41") (pin "1") (pinfunction "1_1") (pintype "passive"))
      (node (ref "C53") (pin "1") (pinfunction "1_1") (pintype "passive"))
      (node (ref "C65") (pin "1") (pinfunction "1_1") (pintype "passive"))
      (node (ref "C77") (pin "1") (pinfunction "1_1") (pintype "passive"))
      (node (ref "C89") (pin "1") (pinfunction "1_1") (pintype "passive"))
      (node (ref "IC101") (pin "8") (pinfunction "V+_8") (pintype "power_in"))
      (node (ref "IC102") (pin "1") (pinfunction "OUT_1") (pintype "passive"))
      (node (ref "IC108") (pin "3") (pinfunction "V+_3") (pintype "power_in"))
      (node (ref "IC13") (pin "3") (pinfunction "V+_3") (pintype "power_in"))
      (node (ref "IC14") (pin "1") (pinfunction "OUT_1") (pintype "passive"))
      (node (ref "IC18") (pin "8") (pinfunction "V+_8") (pintype "power_in"))
      (node (ref "IC22") (pin "3") (pinfunction "V+_3") (pintype "power_in"))
      (node (ref "IC23") (pin "1") (pinfunction "OUT_1") (pintype "passive"))
      (node (ref "IC27") (pin "8") (pinfunction "V+_8") (pintype "power_in"))
      (node (ref "IC31") (pin "3") (pinfunction "V+_3") (pintype "power_in"))
      (node (ref "IC32") (pin "1") (pinfunction "OUT_1") (pintype "passive"))
      (node (ref "IC36") (pin "8") (pinfunction "V+_8") (pintype "power_in"))
      (node (ref "IC4") (pin "3") (pinfunction "V+_3") (pintype "power_in"))
      (node (ref "IC40") (pin "3") (pinfunction "V+_3") (pintype "power_in"))
      (node (ref "IC41") (pin "1") (pinfunction "OUT_1") (pintype "passive"))
      (node (ref "IC45") (pin "8") (pinfunction "V+_8") (pintype "power_in"))
      (node (ref "IC49") (pin "3") (pinfunction "V+_3") (pintype "power_in"))
      (node (ref "IC5") (pin "1") (pinfunction "OUT_1") (pintype "passive"))
      (node (ref "IC50") (pin "1") (pinfunction "OUT_1") (pintype "passive"))
      (node (ref "IC54") (pin "8") (pinfunction "V+_8") (pintype "power_in"))
      (node (ref "IC58") (pin "3") (pinfunction "V+_3") (pintype "power_in"))
      (node (ref "IC59") (pin "1") (pinfunction "OUT_1") (pintype "passive"))
      (node (ref "IC63") (pin "8") (pinfunction "V+_8") (pintype "power_in"))
      (node (ref "IC67") (pin "3") (pinfunction "V+_3") (pintype "power_in"))
      (node (ref "IC68") (pin "1") (pinfunction "OUT_1") (pintype "passive"))
      (node (ref "IC72") (pin "8") (pinfunction "V+_8") (pintype "power_in"))
      (node (ref "IC76") (pin "3") (pinfunction "V+_3") (pintype "power_in"))
      (node (ref "IC77") (pin "1") (pinfunction "OUT_1") (pintype "passive"))
      (node (ref "IC81") (pin "8") (pinfunction "V+_8") (pintype "power_in"))
      (node (ref "IC85") (pin "3") (pinfunction "V+_3") (pintype "power_in"))
      (node (ref "IC86") (pin "1") (pinfunction "OUT_1") (pintype "passive"))
      (node (ref "IC9") (pin "8") (pinfunction "V+_8") (pintype "power_in"))
      (node (ref "IC90") (pin "8") (pinfunction "V+_8") (pintype "power_in"))
      (node (ref "IC94") (pin "3") (pinfunction "V+_3") (pintype "power_in"))
      (node (ref "IC95") (pin "1") (pinfunction "OUT_1") (pintype "passive"))
      (node (ref "IC99") (pin "8") (pinfunction "V+_8") (pintype "power_in"))
      (node (ref "R113") (pin "2") (pinfunction "2_2") (pintype "passive"))
      (node (ref "R121") (pin "2") (pinfunction "2_2") (pintype "passive"))
      (node (ref "R124") (pin "1") (pinfunction "1_1") (pintype "passive"))
      (node (ref "R131") (pin "2") (pinfunction "2_2") (pintype "passive"))
      (node (ref "R142") (pin "2") (pinfunction "2_2") (pintype "passive"))
      (node (ref "R152") (pin "2") (pinfunction "2_2") (pintype "passive"))
      (node (ref "R175") (pin "2") (pinfunction "2_2") (pintype "passive"))
      (node (ref "R178") (pin "2") (pinfunction "2_2") (pintype "passive"))
      (node (ref "R181") (pin "1") (pinfunction "1_1") (pintype "passive"))
      (node (ref "R185") (pin "2") (pinfunction "2_2") (pintype "passive"))
      (node (ref "R197") (pin "1") (pinfunction "1_1") (pintype "passive"))
      (node (ref "R207") (pin "2") (pinfunction "2_2") (pintype "passive"))
      (node (ref "R21") (pin "2") (pinfunction "2_2") (pintype "passive"))
      (node (ref "R230") (pin "2") (pinfunction "2_2") (pintype "passive"))
      (node (ref "R233") (pin "2") (pinfunction "2_2") (pintype "passive"))
      (node (ref "R236") (pin "1") (pinfunction "1_1") (pintype "passive"))
      (node (ref "R24") (pin "2") (pinfunction "2_2") (pintype "passive"))
      (node (ref "R262") (pin "2") (pinfunction "2_2") (pintype "passive"))
      (node (ref "R27") (pin "1") (pinfunction "1_1") (pintype "passive"))
      (node (ref "R285") (pin "2") (pinfunction "2_2") (pintype "passive"))
      (node (ref "R288") (pin "2") (pinfunction "2_2") (pintype "passive"))
      (node (ref "R291") (pin "1") (pinfunction "1_1") (pintype "passive"))
      (node (ref "R317") (pin "2") (pinfunction "2_2") (pintype "passive"))
      (node (ref "R344") (pin "2") (pinfunction "2_2") (pintype "passive"))
      (node (ref "R367") (pin "2") (pinfunction "2_2") (pintype "passive"))
      (node (ref "R370") (pin "2") (pinfunction "2_2") (pintype "passive"))
      (node (ref "R373") (pin "1") (pinfunction "1_1") (pintype "passive"))
      (node (ref "R395") (pin "2") (pinfunction "2_2") (pintype "passive"))
      (node (ref "R418") (pin "2") (pinfunction "2_2") (pintype "passive"))
      (node (ref "R421") (pin "2") (pinfunction "2_2") (pintype "passive"))
      (node (ref "R424") (pin "1") (pinfunction "1_1") (pintype "passive"))
      (node (ref "R446") (pin "2") (pinfunction "2_2") (pintype "passive"))
      (node (ref "R469") (pin "2") (pinfunction "2_2") (pintype "passive"))
      (node (ref "R472") (pin "2") (pinfunction "2_2") (pintype "passive"))
      (node (ref "R475") (pin "1") (pinfunction "1_1") (pintype "passive"))
      (node (ref "R497") (pin "2") (pinfunction "2_2") (pintype "passive"))
      (node (ref "R520") (pin "2") (pinfunction "2_2") (pintype "passive"))
      (node (ref "R523") (pin "2") (pinfunction "2_2") (pintype "passive"))
      (node (ref "R526") (pin "1") (pinfunction "1_1") (pintype "passive"))
      (node (ref "R53") (pin "2") (pinfunction "2_2") (pintype "passive"))
      (node (ref "R548") (pin "2") (pinfunction "2_2") (pintype "passive"))
      (node (ref "R571") (pin "2") (pinfunction "2_2") (pintype "passive"))
      (node (ref "R574") (pin "2") (pinfunction "2_2") (pintype "passive"))
      (node (ref "R577") (pin "1") (pinfunction "1_1") (pintype "passive"))
      (node (ref "R599") (pin "2") (pinfunction "2_2") (pintype "passive"))
      (node (ref "R76") (pin "2") (pinfunction "2_2") (pintype "passive"))
      (node (ref "R79") (pin "2") (pinfunction "2_2") (pintype "passive"))
      (node (ref "R82") (pin "1") (pinfunction "1_1") (pintype "passive"))
    )
    (net (code "1038") (name "unconnected-(IC1A-Q6-Pad7)") (class "Default")
      (node (ref "IC1") (pin "7") (pinfunction "Q6_7") (pintype "output"))
    )
    (net (code "1039") (name "unconnected-(IC1A-Q7-Pad4)") (class "Default")
      (node (ref "IC1") (pin "4") (pinfunction "Q7_4") (pintype "output"))
    )
    (net (code "1040") (name "unconnected-(IC1A-Q8-Pad9)") (class "Default")
      (node (ref "IC1") (pin "9") (pinfunction "Q8_9") (pintype "output"))
    )
    (net (code "1041") (name "unconnected-(IC1A-Q9-Pad5)") (class "Default")
      (node (ref "IC1") (pin "5") (pinfunction "Q9_5") (pintype "output"))
    )
    (net (code "1042") (name "unconnected-(IC6-CV-Pad5)") (class "Default")
      (node (ref "IC6") (pin "5") (pinfunction "CV_5") (pintype "input"))
    )
    (net (code "1043") (name "unconnected-(IC6-DIS-Pad7)") (class "Default")
      (node (ref "IC6") (pin "7") (pinfunction "DIS_7") (pintype "input"))
    )
    (net (code "1044") (name "unconnected-(IC7A-Q-Pad6)") (class "Default")
      (node (ref "IC7") (pin "6") (pinfunction "Q_6") (pintype "output"))
    )
    (net (code "1045") (name "unconnected-(IC7B-Q-Pad10)") (class "Default")
      (node (ref "IC7") (pin "10") (pinfunction "Q_10") (pintype "output"))
    )
    (net (code "1046") (name "unconnected-(IC10A-Q6-Pad7)") (class "Default")
      (node (ref "IC10") (pin "7") (pinfunction "Q6_7") (pintype "output"))
    )
    (net (code "1047") (name "unconnected-(IC10A-Q7-Pad4)") (class "Default")
      (node (ref "IC10") (pin "4") (pinfunction "Q7_4") (pintype "output"))
    )
    (net (code "1048") (name "unconnected-(IC10A-Q8-Pad9)") (class "Default")
      (node (ref "IC10") (pin "9") (pinfunction "Q8_9") (pintype "output"))
    )
    (net (code "1049") (name "unconnected-(IC10A-Q9-Pad5)") (class "Default")
      (node (ref "IC10") (pin "5") (pinfunction "Q9_5") (pintype "output"))
    )
    (net (code "1050") (name "unconnected-(IC15-CV-Pad5)") (class "Default")
      (node (ref "IC15") (pin "5") (pinfunction "CV_5") (pintype "input"))
    )
    (net (code "1051") (name "unconnected-(IC15-DIS-Pad7)") (class "Default")
      (node (ref "IC15") (pin "7") (pinfunction "DIS_7") (pintype "input"))
    )
    (net (code "1052") (name "unconnected-(IC16A-Q-Pad6)") (class "Default")
      (node (ref "IC16") (pin "6") (pinfunction "Q_6") (pintype "output"))
    )
    (net (code "1053") (name "unconnected-(IC16B-Q-Pad10)") (class "Default")
      (node (ref "IC16") (pin "10") (pinfunction "Q_10") (pintype "output"))
    )
    (net (code "1054") (name "unconnected-(IC19A-Q6-Pad7)") (class "Default")
      (node (ref "IC19") (pin "7") (pinfunction "Q6_7") (pintype "output"))
    )
    (net (code "1055") (name "unconnected-(IC19A-Q7-Pad4)") (class "Default")
      (node (ref "IC19") (pin "4") (pinfunction "Q7_4") (pintype "output"))
    )
    (net (code "1056") (name "unconnected-(IC19A-Q8-Pad9)") (class "Default")
      (node (ref "IC19") (pin "9") (pinfunction "Q8_9") (pintype "output"))
    )
    (net (code "1057") (name "unconnected-(IC19A-Q9-Pad5)") (class "Default")
      (node (ref "IC19") (pin "5") (pinfunction "Q9_5") (pintype "output"))
    )
    (net (code "1058") (name "unconnected-(IC24-CV-Pad5)") (class "Default")
      (node (ref "IC24") (pin "5") (pinfunction "CV_5") (pintype "input"))
    )
    (net (code "1059") (name "unconnected-(IC24-DIS-Pad7)") (class "Default")
      (node (ref "IC24") (pin "7") (pinfunction "DIS_7") (pintype "input"))
    )
    (net (code "1060") (name "unconnected-(IC25A-Q-Pad6)") (class "Default")
      (node (ref "IC25") (pin "6") (pinfunction "Q_6") (pintype "output"))
    )
    (net (code "1061") (name "unconnected-(IC25B-Q-Pad10)") (class "Default")
      (node (ref "IC25") (pin "10") (pinfunction "Q_10") (pintype "output"))
    )
    (net (code "1062") (name "unconnected-(IC28A-Q6-Pad7)") (class "Default")
      (node (ref "IC28") (pin "7") (pinfunction "Q6_7") (pintype "output"))
    )
    (net (code "1063") (name "unconnected-(IC28A-Q7-Pad4)") (class "Default")
      (node (ref "IC28") (pin "4") (pinfunction "Q7_4") (pintype "output"))
    )
    (net (code "1064") (name "unconnected-(IC28A-Q8-Pad9)") (class "Default")
      (node (ref "IC28") (pin "9") (pinfunction "Q8_9") (pintype "output"))
    )
    (net (code "1065") (name "unconnected-(IC28A-Q9-Pad5)") (class "Default")
      (node (ref "IC28") (pin "5") (pinfunction "Q9_5") (pintype "output"))
    )
    (net (code "1066") (name "unconnected-(IC33-CV-Pad5)") (class "Default")
      (node (ref "IC33") (pin "5") (pinfunction "CV_5") (pintype "input"))
    )
    (net (code "1067") (name "unconnected-(IC33-DIS-Pad7)") (class "Default")
      (node (ref "IC33") (pin "7") (pinfunction "DIS_7") (pintype "input"))
    )
    (net (code "1068") (name "unconnected-(IC34A-Q-Pad6)") (class "Default")
      (node (ref "IC34") (pin "6") (pinfunction "Q_6") (pintype "output"))
    )
    (net (code "1069") (name "unconnected-(IC34B-Q-Pad10)") (class "Default")
      (node (ref "IC34") (pin "10") (pinfunction "Q_10") (pintype "output"))
    )
    (net (code "1070") (name "unconnected-(IC37A-Q6-Pad7)") (class "Default")
      (node (ref "IC37") (pin "7") (pinfunction "Q6_7") (pintype "output"))
    )
    (net (code "1071") (name "unconnected-(IC37A-Q7-Pad4)") (class "Default")
      (node (ref "IC37") (pin "4") (pinfunction "Q7_4") (pintype "output"))
    )
    (net (code "1072") (name "unconnected-(IC37A-Q8-Pad9)") (class "Default")
      (node (ref "IC37") (pin "9") (pinfunction "Q8_9") (pintype "output"))
    )
    (net (code "1073") (name "unconnected-(IC37A-Q9-Pad5)") (class "Default")
      (node (ref "IC37") (pin "5") (pinfunction "Q9_5") (pintype "output"))
    )
    (net (code "1074") (name "unconnected-(IC42-CV-Pad5)") (class "Default")
      (node (ref "IC42") (pin "5") (pinfunction "CV_5") (pintype "input"))
    )
    (net (code "1075") (name "unconnected-(IC42-DIS-Pad7)") (class "Default")
      (node (ref "IC42") (pin "7") (pinfunction "DIS_7") (pintype "input"))
    )
    (net (code "1076") (name "unconnected-(IC43A-Q-Pad6)") (class "Default")
      (node (ref "IC43") (pin "6") (pinfunction "Q_6") (pintype "output"))
    )
    (net (code "1077") (name "unconnected-(IC43B-Q-Pad10)") (class "Default")
      (node (ref "IC43") (pin "10") (pinfunction "Q_10") (pintype "output"))
    )
    (net (code "1078") (name "unconnected-(IC46A-Q6-Pad7)") (class "Default")
      (node (ref "IC46") (pin "7") (pinfunction "Q6_7") (pintype "output"))
    )
    (net (code "1079") (name "unconnected-(IC46A-Q7-Pad4)") (class "Default")
      (node (ref "IC46") (pin "4") (pinfunction "Q7_4") (pintype "output"))
    )
    (net (code "1080") (name "unconnected-(IC46A-Q8-Pad9)") (class "Default")
      (node (ref "IC46") (pin "9") (pinfunction "Q8_9") (pintype "output"))
    )
    (net (code "1081") (name "unconnected-(IC46A-Q9-Pad5)") (class "Default")
      (node (ref "IC46") (pin "5") (pinfunction "Q9_5") (pintype "output"))
    )
    (net (code "1082") (name "unconnected-(IC51-CV-Pad5)") (class "Default")
      (node (ref "IC51") (pin "5") (pinfunction "CV_5") (pintype "input"))
    )
    (net (code "1083") (name "unconnected-(IC51-DIS-Pad7)") (class "Default")
      (node (ref "IC51") (pin "7") (pinfunction "DIS_7") (pintype "input"))
    )
    (net (code "1084") (name "unconnected-(IC52A-Q-Pad6)") (class "Default")
      (node (ref "IC52") (pin "6") (pinfunction "Q_6") (pintype "output"))
    )
    (net (code "1085") (name "unconnected-(IC52B-Q-Pad10)") (class "Default")
      (node (ref "IC52") (pin "10") (pinfunction "Q_10") (pintype "output"))
    )
    (net (code "1086") (name "unconnected-(IC55A-Q6-Pad7)") (class "Default")
      (node (ref "IC55") (pin "7") (pinfunction "Q6_7") (pintype "output"))
    )
    (net (code "1087") (name "unconnected-(IC55A-Q7-Pad4)") (class "Default")
      (node (ref "IC55") (pin "4") (pinfunction "Q7_4") (pintype "output"))
    )
    (net (code "1088") (name "unconnected-(IC55A-Q8-Pad9)") (class "Default")
      (node (ref "IC55") (pin "9") (pinfunction "Q8_9") (pintype "output"))
    )
    (net (code "1089") (name "unconnected-(IC55A-Q9-Pad5)") (class "Default")
      (node (ref "IC55") (pin "5") (pinfunction "Q9_5") (pintype "output"))
    )
    (net (code "1090") (name "unconnected-(IC60-CV-Pad5)") (class "Default")
      (node (ref "IC60") (pin "5") (pinfunction "CV_5") (pintype "input"))
    )
    (net (code "1091") (name "unconnected-(IC60-DIS-Pad7)") (class "Default")
      (node (ref "IC60") (pin "7") (pinfunction "DIS_7") (pintype "input"))
    )
    (net (code "1092") (name "unconnected-(IC61A-Q-Pad6)") (class "Default")
      (node (ref "IC61") (pin "6") (pinfunction "Q_6") (pintype "output"))
    )
    (net (code "1093") (name "unconnected-(IC61B-Q-Pad10)") (class "Default")
      (node (ref "IC61") (pin "10") (pinfunction "Q_10") (pintype "output"))
    )
    (net (code "1094") (name "unconnected-(IC64A-Q6-Pad7)") (class "Default")
      (node (ref "IC64") (pin "7") (pinfunction "Q6_7") (pintype "output"))
    )
    (net (code "1095") (name "unconnected-(IC64A-Q7-Pad4)") (class "Default")
      (node (ref "IC64") (pin "4") (pinfunction "Q7_4") (pintype "output"))
    )
    (net (code "1096") (name "unconnected-(IC64A-Q8-Pad9)") (class "Default")
      (node (ref "IC64") (pin "9") (pinfunction "Q8_9") (pintype "output"))
    )
    (net (code "1097") (name "unconnected-(IC64A-Q9-Pad5)") (class "Default")
      (node (ref "IC64") (pin "5") (pinfunction "Q9_5") (pintype "output"))
    )
    (net (code "1098") (name "unconnected-(IC69-CV-Pad5)") (class "Default")
      (node (ref "IC69") (pin "5") (pinfunction "CV_5") (pintype "input"))
    )
    (net (code "1099") (name "unconnected-(IC69-DIS-Pad7)") (class "Default")
      (node (ref "IC69") (pin "7") (pinfunction "DIS_7") (pintype "input"))
    )
    (net (code "1100") (name "unconnected-(IC70A-Q-Pad6)") (class "Default")
      (node (ref "IC70") (pin "6") (pinfunction "Q_6") (pintype "output"))
    )
    (net (code "1101") (name "unconnected-(IC70B-Q-Pad10)") (class "Default")
      (node (ref "IC70") (pin "10") (pinfunction "Q_10") (pintype "output"))
    )
    (net (code "1102") (name "unconnected-(IC73A-Q6-Pad7)") (class "Default")
      (node (ref "IC73") (pin "7") (pinfunction "Q6_7") (pintype "output"))
    )
    (net (code "1103") (name "unconnected-(IC73A-Q7-Pad4)") (class "Default")
      (node (ref "IC73") (pin "4") (pinfunction "Q7_4") (pintype "output"))
    )
    (net (code "1104") (name "unconnected-(IC73A-Q8-Pad9)") (class "Default")
      (node (ref "IC73") (pin "9") (pinfunction "Q8_9") (pintype "output"))
    )
    (net (code "1105") (name "unconnected-(IC73A-Q9-Pad5)") (class "Default")
      (node (ref "IC73") (pin "5") (pinfunction "Q9_5") (pintype "output"))
    )
    (net (code "1106") (name "unconnected-(IC78-CV-Pad5)") (class "Default")
      (node (ref "IC78") (pin "5") (pinfunction "CV_5") (pintype "input"))
    )
    (net (code "1107") (name "unconnected-(IC78-DIS-Pad7)") (class "Default")
      (node (ref "IC78") (pin "7") (pinfunction "DIS_7") (pintype "input"))
    )
    (net (code "1108") (name "unconnected-(IC79A-Q-Pad6)") (class "Default")
      (node (ref "IC79") (pin "6") (pinfunction "Q_6") (pintype "output"))
    )
    (net (code "1109") (name "unconnected-(IC79B-Q-Pad10)") (class "Default")
      (node (ref "IC79") (pin "10") (pinfunction "Q_10") (pintype "output"))
    )
    (net (code "1110") (name "unconnected-(IC82A-Q6-Pad7)") (class "Default")
      (node (ref "IC82") (pin "7") (pinfunction "Q6_7") (pintype "output"))
    )
    (net (code "1111") (name "unconnected-(IC82A-Q7-Pad4)") (class "Default")
      (node (ref "IC82") (pin "4") (pinfunction "Q7_4") (pintype "output"))
    )
    (net (code "1112") (name "unconnected-(IC82A-Q8-Pad9)") (class "Default")
      (node (ref "IC82") (pin "9") (pinfunction "Q8_9") (pintype "output"))
    )
    (net (code "1113") (name "unconnected-(IC82A-Q9-Pad5)") (class "Default")
      (node (ref "IC82") (pin "5") (pinfunction "Q9_5") (pintype "output"))
    )
    (net (code "1114") (name "unconnected-(IC87-CV-Pad5)") (class "Default")
      (node (ref "IC87") (pin "5") (pinfunction "CV_5") (pintype "input"))
    )
    (net (code "1115") (name "unconnected-(IC87-DIS-Pad7)") (class "Default")
      (node (ref "IC87") (pin "7") (pinfunction "DIS_7") (pintype "input"))
    )
    (net (code "1116") (name "unconnected-(IC88A-Q-Pad6)") (class "Default")
      (node (ref "IC88") (pin "6") (pinfunction "Q_6") (pintype "output"))
    )
    (net (code "1117") (name "unconnected-(IC88B-Q-Pad10)") (class "Default")
      (node (ref "IC88") (pin "10") (pinfunction "Q_10") (pintype "output"))
    )
    (net (code "1118") (name "unconnected-(IC91A-Q6-Pad7)") (class "Default")
      (node (ref "IC91") (pin "7") (pinfunction "Q6_7") (pintype "output"))
    )
    (net (code "1119") (name "unconnected-(IC91A-Q7-Pad4)") (class "Default")
      (node (ref "IC91") (pin "4") (pinfunction "Q7_4") (pintype "output"))
    )
    (net (code "1120") (name "unconnected-(IC91A-Q8-Pad9)") (class "Default")
      (node (ref "IC91") (pin "9") (pinfunction "Q8_9") (pintype "output"))
    )
    (net (code "1121") (name "unconnected-(IC91A-Q9-Pad5)") (class "Default")
      (node (ref "IC91") (pin "5") (pinfunction "Q9_5") (pintype "output"))
    )
    (net (code "1122") (name "unconnected-(IC96-CV-Pad5)") (class "Default")
      (node (ref "IC96") (pin "5") (pinfunction "CV_5") (pintype "input"))
    )
    (net (code "1123") (name "unconnected-(IC96-DIS-Pad7)") (class "Default")
      (node (ref "IC96") (pin "7") (pinfunction "DIS_7") (pintype "input"))
    )
    (net (code "1124") (name "unconnected-(IC97A-Q-Pad6)") (class "Default")
      (node (ref "IC97") (pin "6") (pinfunction "Q_6") (pintype "output"))
    )
    (net (code "1125") (name "unconnected-(IC97B-Q-Pad10)") (class "Default")
      (node (ref "IC97") (pin "10") (pinfunction "Q_10") (pintype "output"))
    )
    (net (code "1126") (name "unconnected-(IC105A-Q6-Pad7)") (class "Default")
      (node (ref "IC105") (pin "7") (pinfunction "Q6_7") (pintype "output"))
    )
    (net (code "1127") (name "unconnected-(IC105A-Q7-Pad4)") (class "Default")
      (node (ref "IC105") (pin "4") (pinfunction "Q7_4") (pintype "output"))
    )
    (net (code "1128") (name "unconnected-(IC105A-Q8-Pad9)") (class "Default")
      (node (ref "IC105") (pin "9") (pinfunction "Q8_9") (pintype "output"))
    )
    (net (code "1129") (name "unconnected-(IC105A-Q9-Pad5)") (class "Default")
      (node (ref "IC105") (pin "5") (pinfunction "Q9_5") (pintype "output"))
    )
    (net (code "1130") (name "unconnected-(IC110-CV-Pad5)") (class "Default")
      (node (ref "IC110") (pin "5") (pinfunction "CV_5") (pintype "input"))
    )
    (net (code "1131") (name "unconnected-(IC110-DIS-Pad7)") (class "Default")
      (node (ref "IC110") (pin "7") (pinfunction "DIS_7") (pintype "input"))
    )
    (net (code "1132") (name "unconnected-(IC111A-Q-Pad6)") (class "Default")
      (node (ref "IC111") (pin "6") (pinfunction "Q_6") (pintype "output"))
    )
    (net (code "1133") (name "unconnected-(IC111B-Q-Pad10)") (class "Default")
      (node (ref "IC111") (pin "10") (pinfunction "Q_10") (pintype "output"))
    )
    (net (code "1134") (name "unconnected-(LED5-C-PadK)") (class "Default")
      (node (ref "LED5") (pin "K") (pinfunction "C_K") (pintype "passive"))
    )
    (net (code "1135") (name "unconnected-(LED11-C-PadK)") (class "Default")
      (node (ref "LED11") (pin "K") (pinfunction "C_K") (pintype "passive"))
    )
    (net (code "1136") (name "unconnected-(LED17-C-PadK)") (class "Default")
      (node (ref "LED17") (pin "K") (pinfunction "C_K") (pintype "passive"))
    )
    (net (code "1137") (name "unconnected-(LED23-C-PadK)") (class "Default")
      (node (ref "LED23") (pin "K") (pinfunction "C_K") (pintype "passive"))
    )
    (net (code "1138") (name "unconnected-(LED29-C-PadK)") (class "Default")
      (node (ref "LED29") (pin "K") (pinfunction "C_K") (pintype "passive"))
    )
    (net (code "1139") (name "unconnected-(LED35-C-PadK)") (class "Default")
      (node (ref "LED35") (pin "K") (pinfunction "C_K") (pintype "passive"))
    )
    (net (code "1140") (name "unconnected-(LED41-C-PadK)") (class "Default")
      (node (ref "LED41") (pin "K") (pinfunction "C_K") (pintype "passive"))
    )
    (net (code "1141") (name "unconnected-(LED47-C-PadK)") (class "Default")
      (node (ref "LED47") (pin "K") (pinfunction "C_K") (pintype "passive"))
    )
    (net (code "1142") (name "unconnected-(LED53-C-PadK)") (class "Default")
      (node (ref "LED53") (pin "K") (pinfunction "C_K") (pintype "passive"))
    )
    (net (code "1143") (name "unconnected-(LED59-C-PadK)") (class "Default")
      (node (ref "LED59") (pin "K") (pinfunction "C_K") (pintype "passive"))
    )
    (net (code "1144") (name "unconnected-(LED65-C-PadK)") (class "Default")
      (node (ref "LED65") (pin "K") (pinfunction "C_K") (pintype "passive"))
    )
    (net (code "1145") (name "unconnected-(LED101-C-PadK)") (class "Default")
      (node (ref "LED101") (pin "K") (pinfunction "C_K") (pintype "passive"))
    )
    (net (code "1146") (name "unconnected-(X1-Pad20)") (class "Default")
      (node (ref "X1") (pin "20") (pinfunction "20_20") (pintype "passive"))
    )
    (net (code "1147") (name "unconnected-(X1-Pad24)") (class "Default")
      (node (ref "X1") (pin "24") (pinfunction "24_24") (pintype "passive"))
    )
    (net (code "1148") (name "unconnected-(X4-Pad20)") (class "Default")
      (node (ref "X4") (pin "20") (pinfunction "20_20") (pintype "passive"))
    )
    (net (code "1149") (name "unconnected-(X4-Pad24)") (class "Default")
      (node (ref "X4") (pin "24") (pinfunction "24_24") (pintype "passive"))
    )
    (net (code "1150") (name "unconnected-(X7-Pad20)") (class "Default")
      (node (ref "X7") (pin "20") (pinfunction "20_20") (pintype "passive"))
    )
    (net (code "1151") (name "unconnected-(X7-Pad24)") (class "Default")
      (node (ref "X7") (pin "24") (pinfunction "24_24") (pintype "passive"))
    )
    (net (code "1152") (name "unconnected-(X10-Pad20)") (class "Default")
      (node (ref "X10") (pin "20") (pinfunction "20_20") (pintype "passive"))
    )
    (net (code "1153") (name "unconnected-(X10-Pad24)") (class "Default")
      (node (ref "X10") (pin "24") (pinfunction "24_24") (pintype "passive"))
    )
    (net (code "1154") (name "unconnected-(X13-Pad20)") (class "Default")
      (node (ref "X13") (pin "20") (pinfunction "20_20") (pintype "passive"))
    )
    (net (code "1155") (name "unconnected-(X13-Pad24)") (class "Default")
      (node (ref "X13") (pin "24") (pinfunction "24_24") (pintype "passive"))
    )
    (net (code "1156") (name "unconnected-(X16-Pad20)") (class "Default")
      (node (ref "X16") (pin "20") (pinfunction "20_20") (pintype "passive"))
    )
    (net (code "1157") (name "unconnected-(X16-Pad24)") (class "Default")
      (node (ref "X16") (pin "24") (pinfunction "24_24") (pintype "passive"))
    )
    (net (code "1158") (name "unconnected-(X19-Pad20)") (class "Default")
      (node (ref "X19") (pin "20") (pinfunction "20_20") (pintype "passive"))
    )
    (net (code "1159") (name "unconnected-(X19-Pad24)") (class "Default")
      (node (ref "X19") (pin "24") (pinfunction "24_24") (pintype "passive"))
    )
    (net (code "1160") (name "unconnected-(X22-Pad20)") (class "Default")
      (node (ref "X22") (pin "20") (pinfunction "20_20") (pintype "passive"))
    )
    (net (code "1161") (name "unconnected-(X22-Pad24)") (class "Default")
      (node (ref "X22") (pin "24") (pinfunction "24_24") (pintype "passive"))
    )
    (net (code "1162") (name "unconnected-(X25-Pad20)") (class "Default")
      (node (ref "X25") (pin "20") (pinfunction "20_20") (pintype "passive"))
    )
    (net (code "1163") (name "unconnected-(X25-Pad24)") (class "Default")
      (node (ref "X25") (pin "24") (pinfunction "24_24") (pintype "passive"))
    )
    (net (code "1164") (name "unconnected-(X28-Pad20)") (class "Default")
      (node (ref "X28") (pin "20") (pinfunction "20_20") (pintype "passive"))
    )
    (net (code "1165") (name "unconnected-(X28-Pad24)") (class "Default")
      (node (ref "X28") (pin "24") (pinfunction "24_24") (pintype "passive"))
    )
    (net (code "1166") (name "unconnected-(X31-Pad20)") (class "Default")
      (node (ref "X31") (pin "20") (pinfunction "20_20") (pintype "passive"))
    )
    (net (code "1167") (name "unconnected-(X31-Pad24)") (class "Default")
      (node (ref "X31") (pin "24") (pinfunction "24_24") (pintype "passive"))
    )
    (net (code "1168") (name "unconnected-(X101-Pad20)") (class "Default")
      (node (ref "X101") (pin "20") (pinfunction "20_20") (pintype "passive"))
    )
    (net (code "1169") (name "unconnected-(X101-Pad24)") (class "Default")
      (node (ref "X101") (pin "24") (pinfunction "24_24") (pintype "passive"))
    )
  )
)
